# BEP32_12nutzen_90Grad.net
KiCad netlist of a schematic drawn in EAGLE
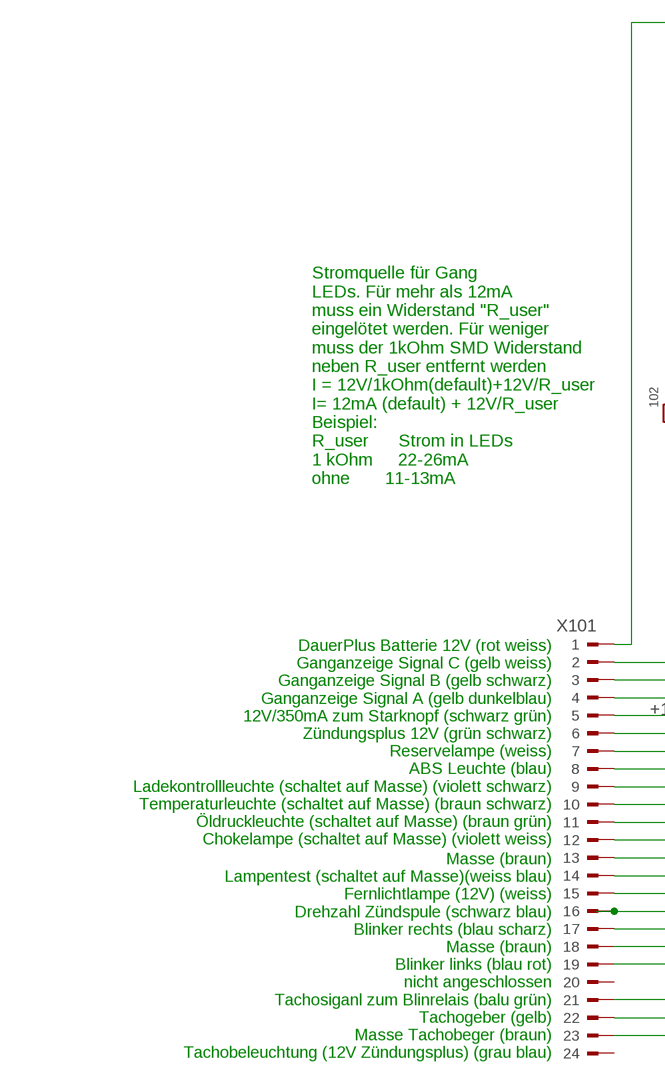
[diagram p0: schematic, sheet 1, part 1 of 2]
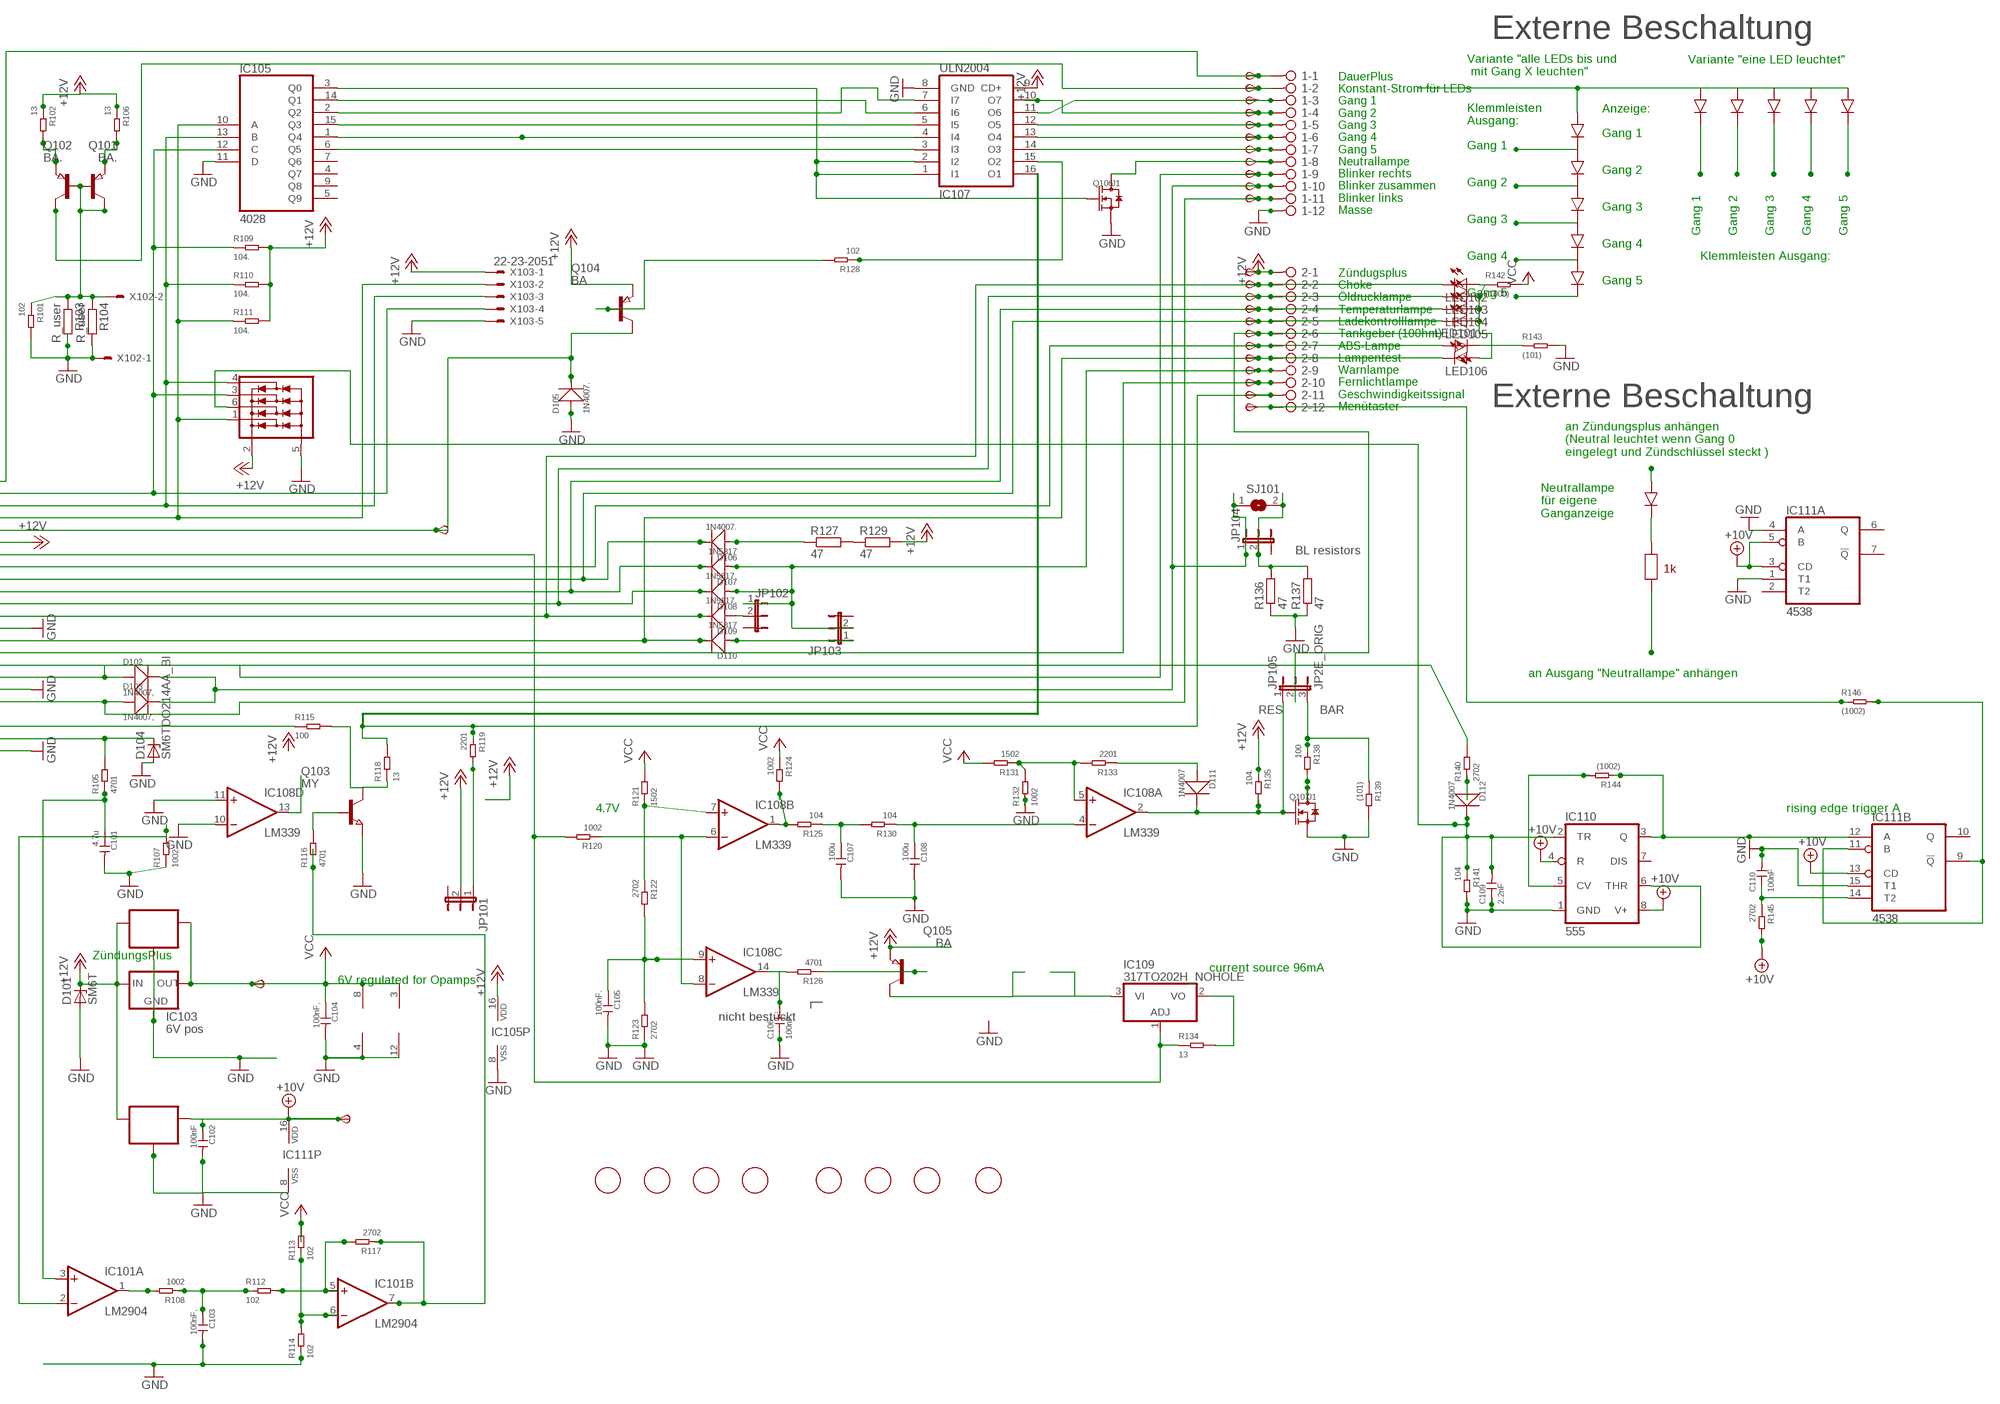
[diagram p1: schematic, sheet 1, part 2 of 2]
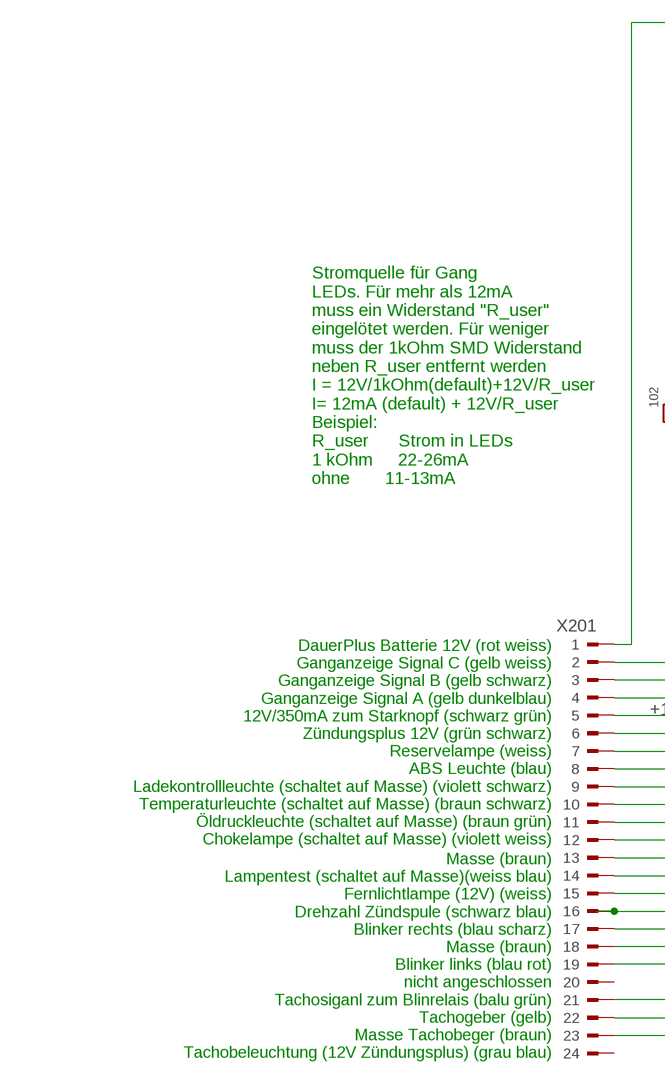
[diagram p2: schematic, sheet 2, part 1 of 2]
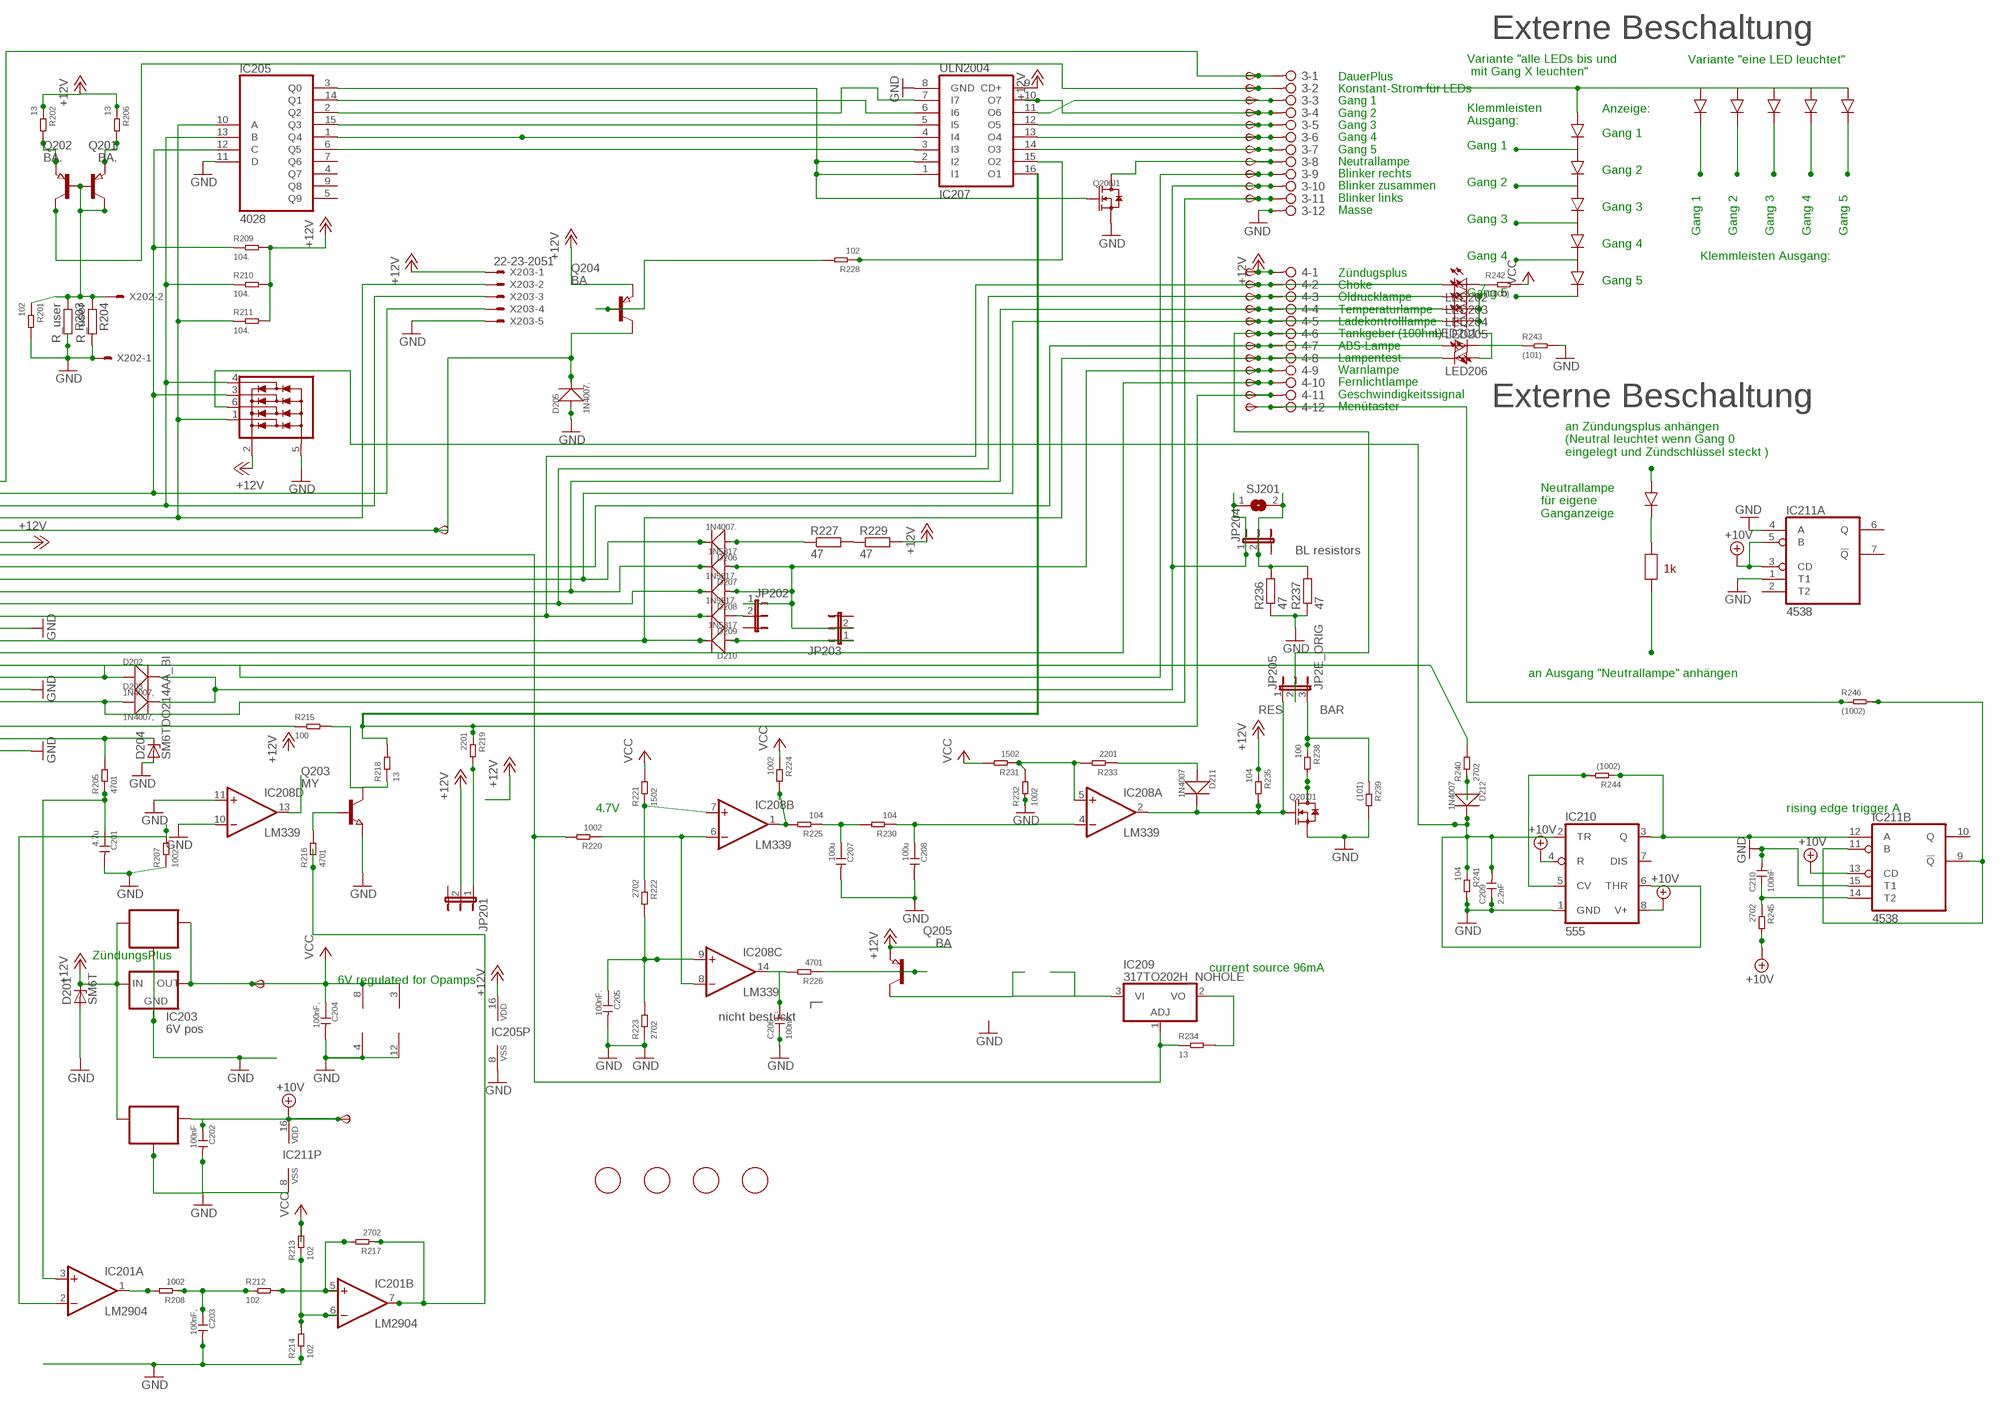
[diagram p3: schematic, sheet 2, part 2 of 2]
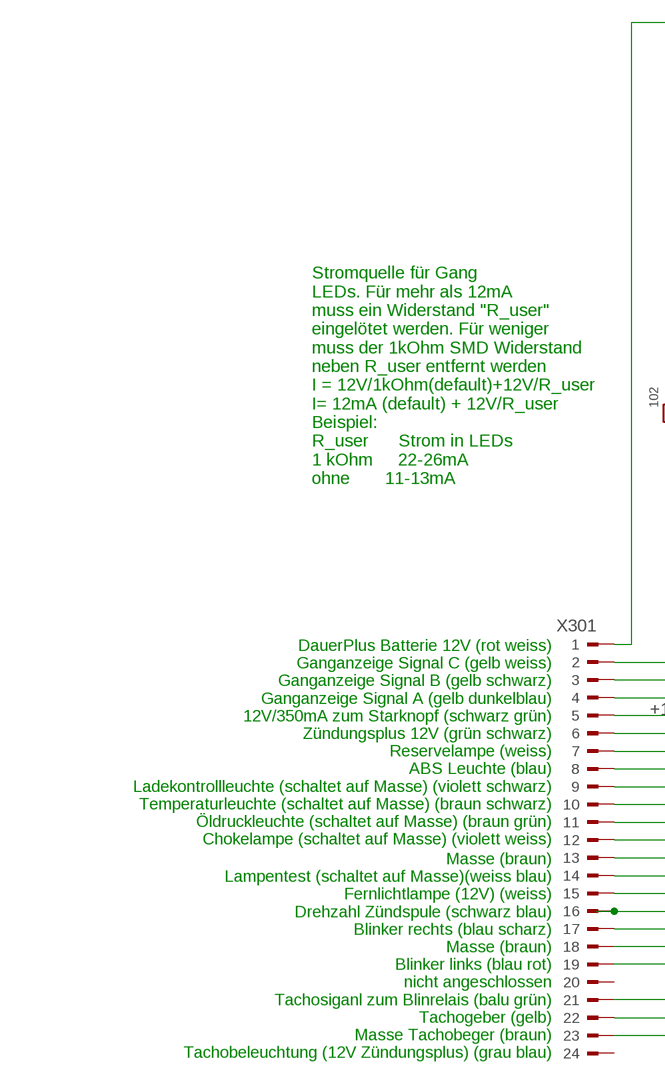
[diagram p4: schematic, sheet 3, part 1 of 2]
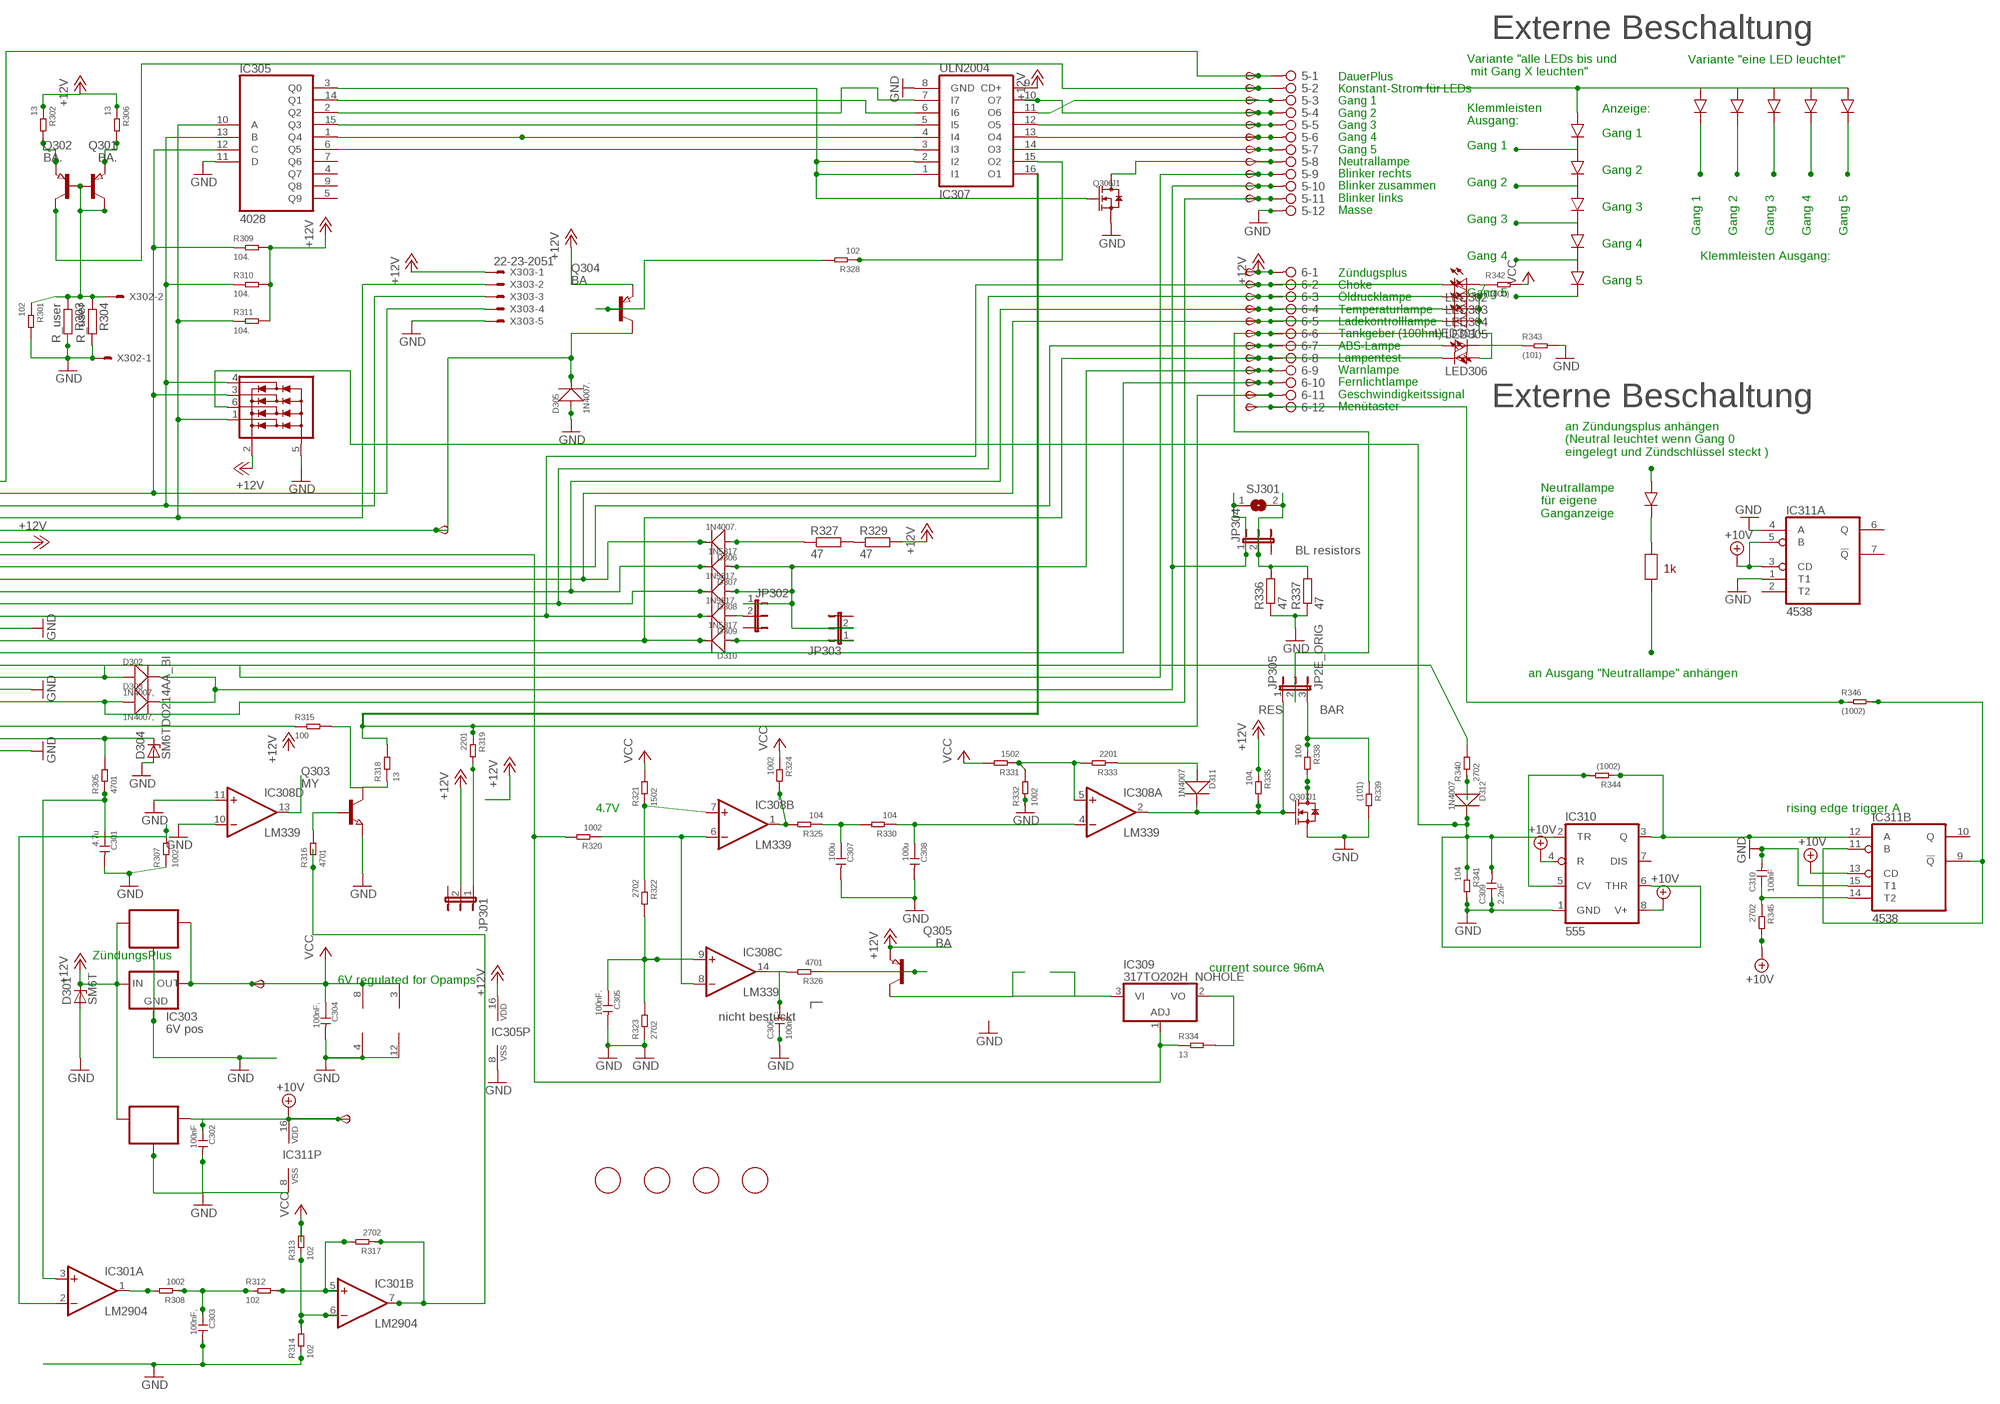
[diagram p5: schematic, sheet 3, part 2 of 2]
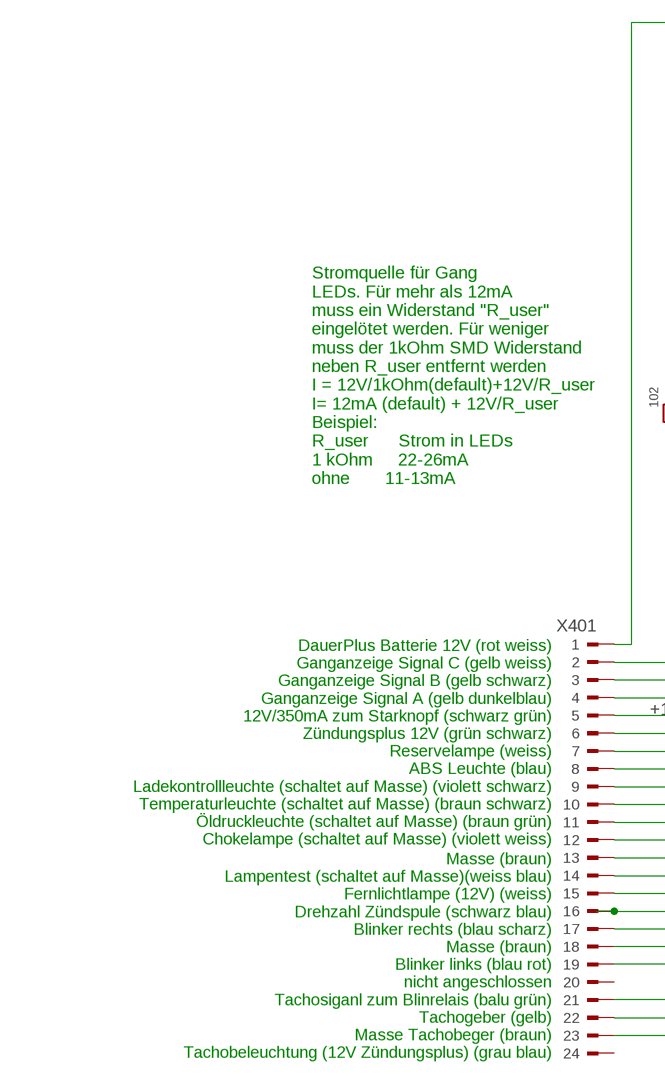
[diagram p6: schematic, sheet 4, part 1 of 2]
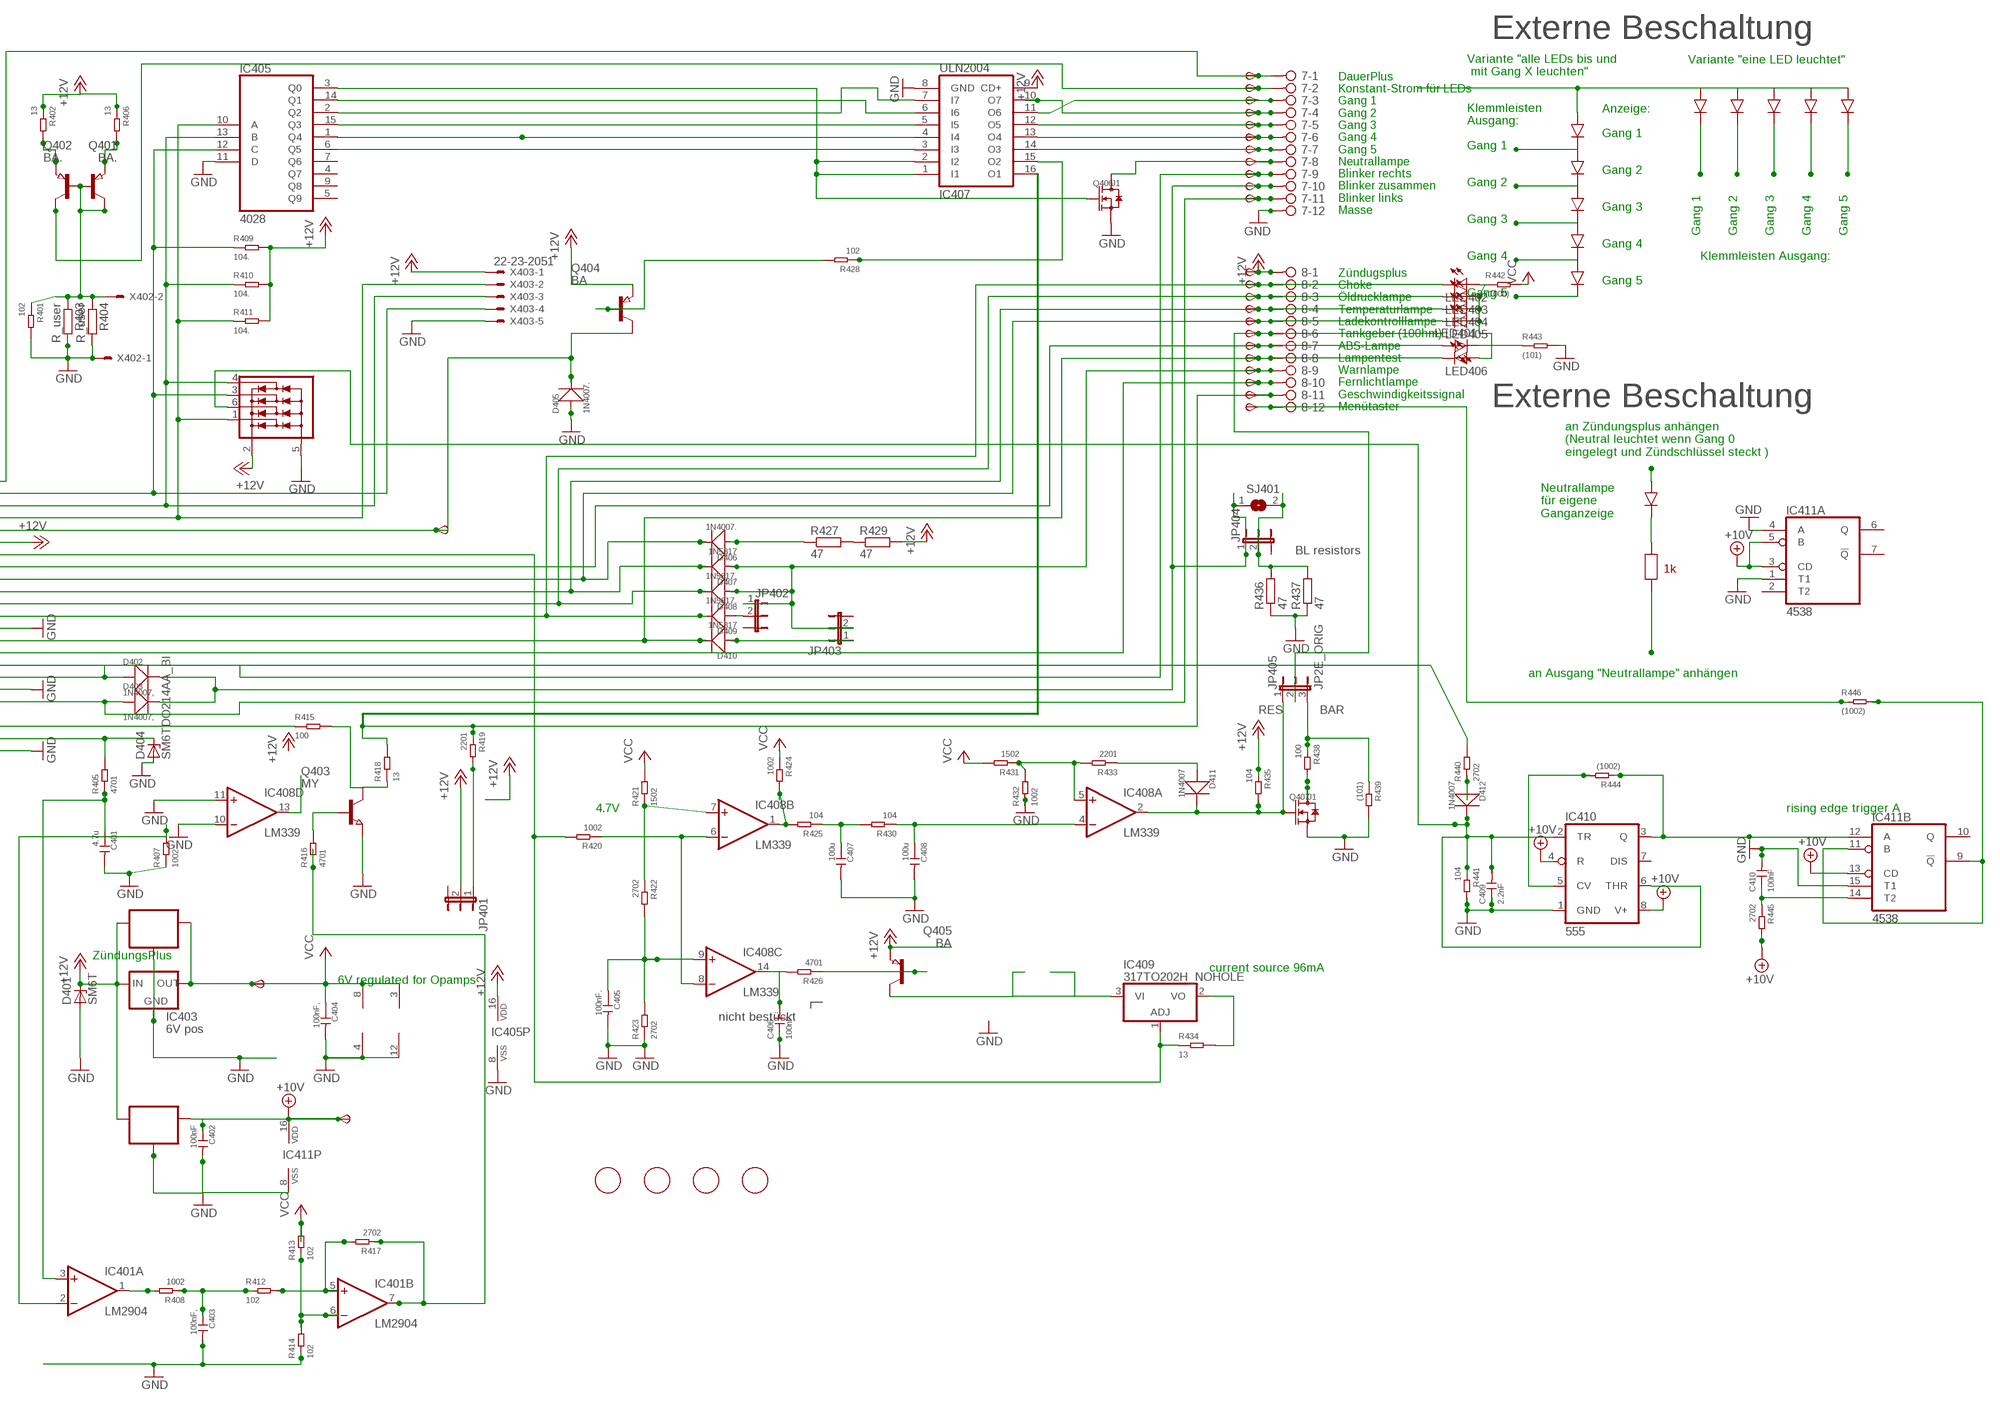
[diagram p7: schematic, sheet 4, part 2 of 2]
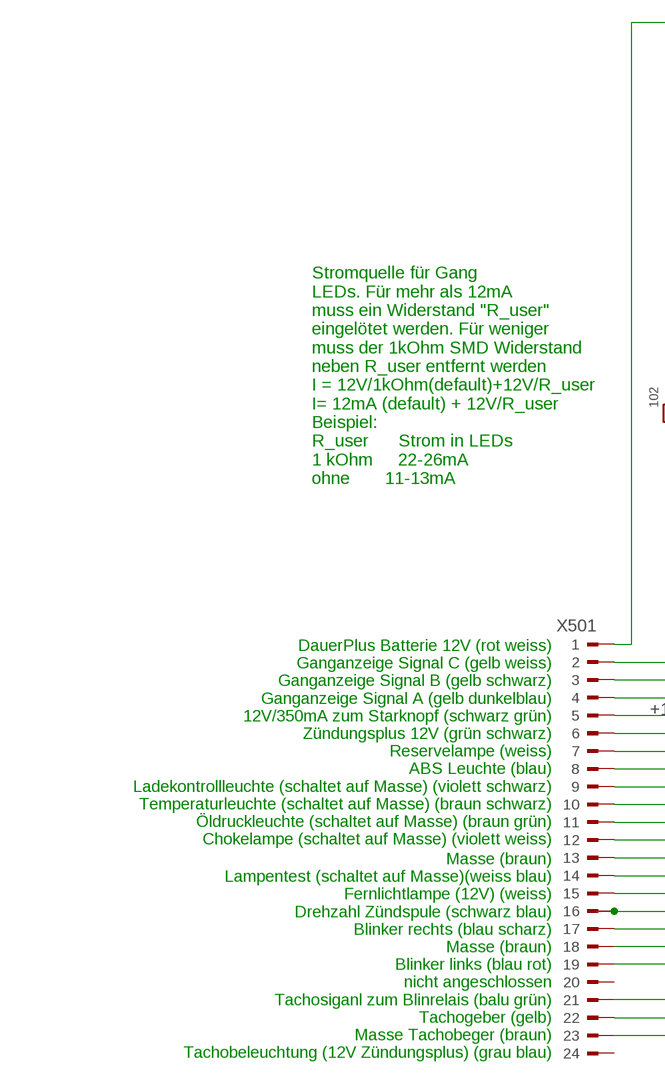
[diagram p8: schematic, sheet 5, part 1 of 2]
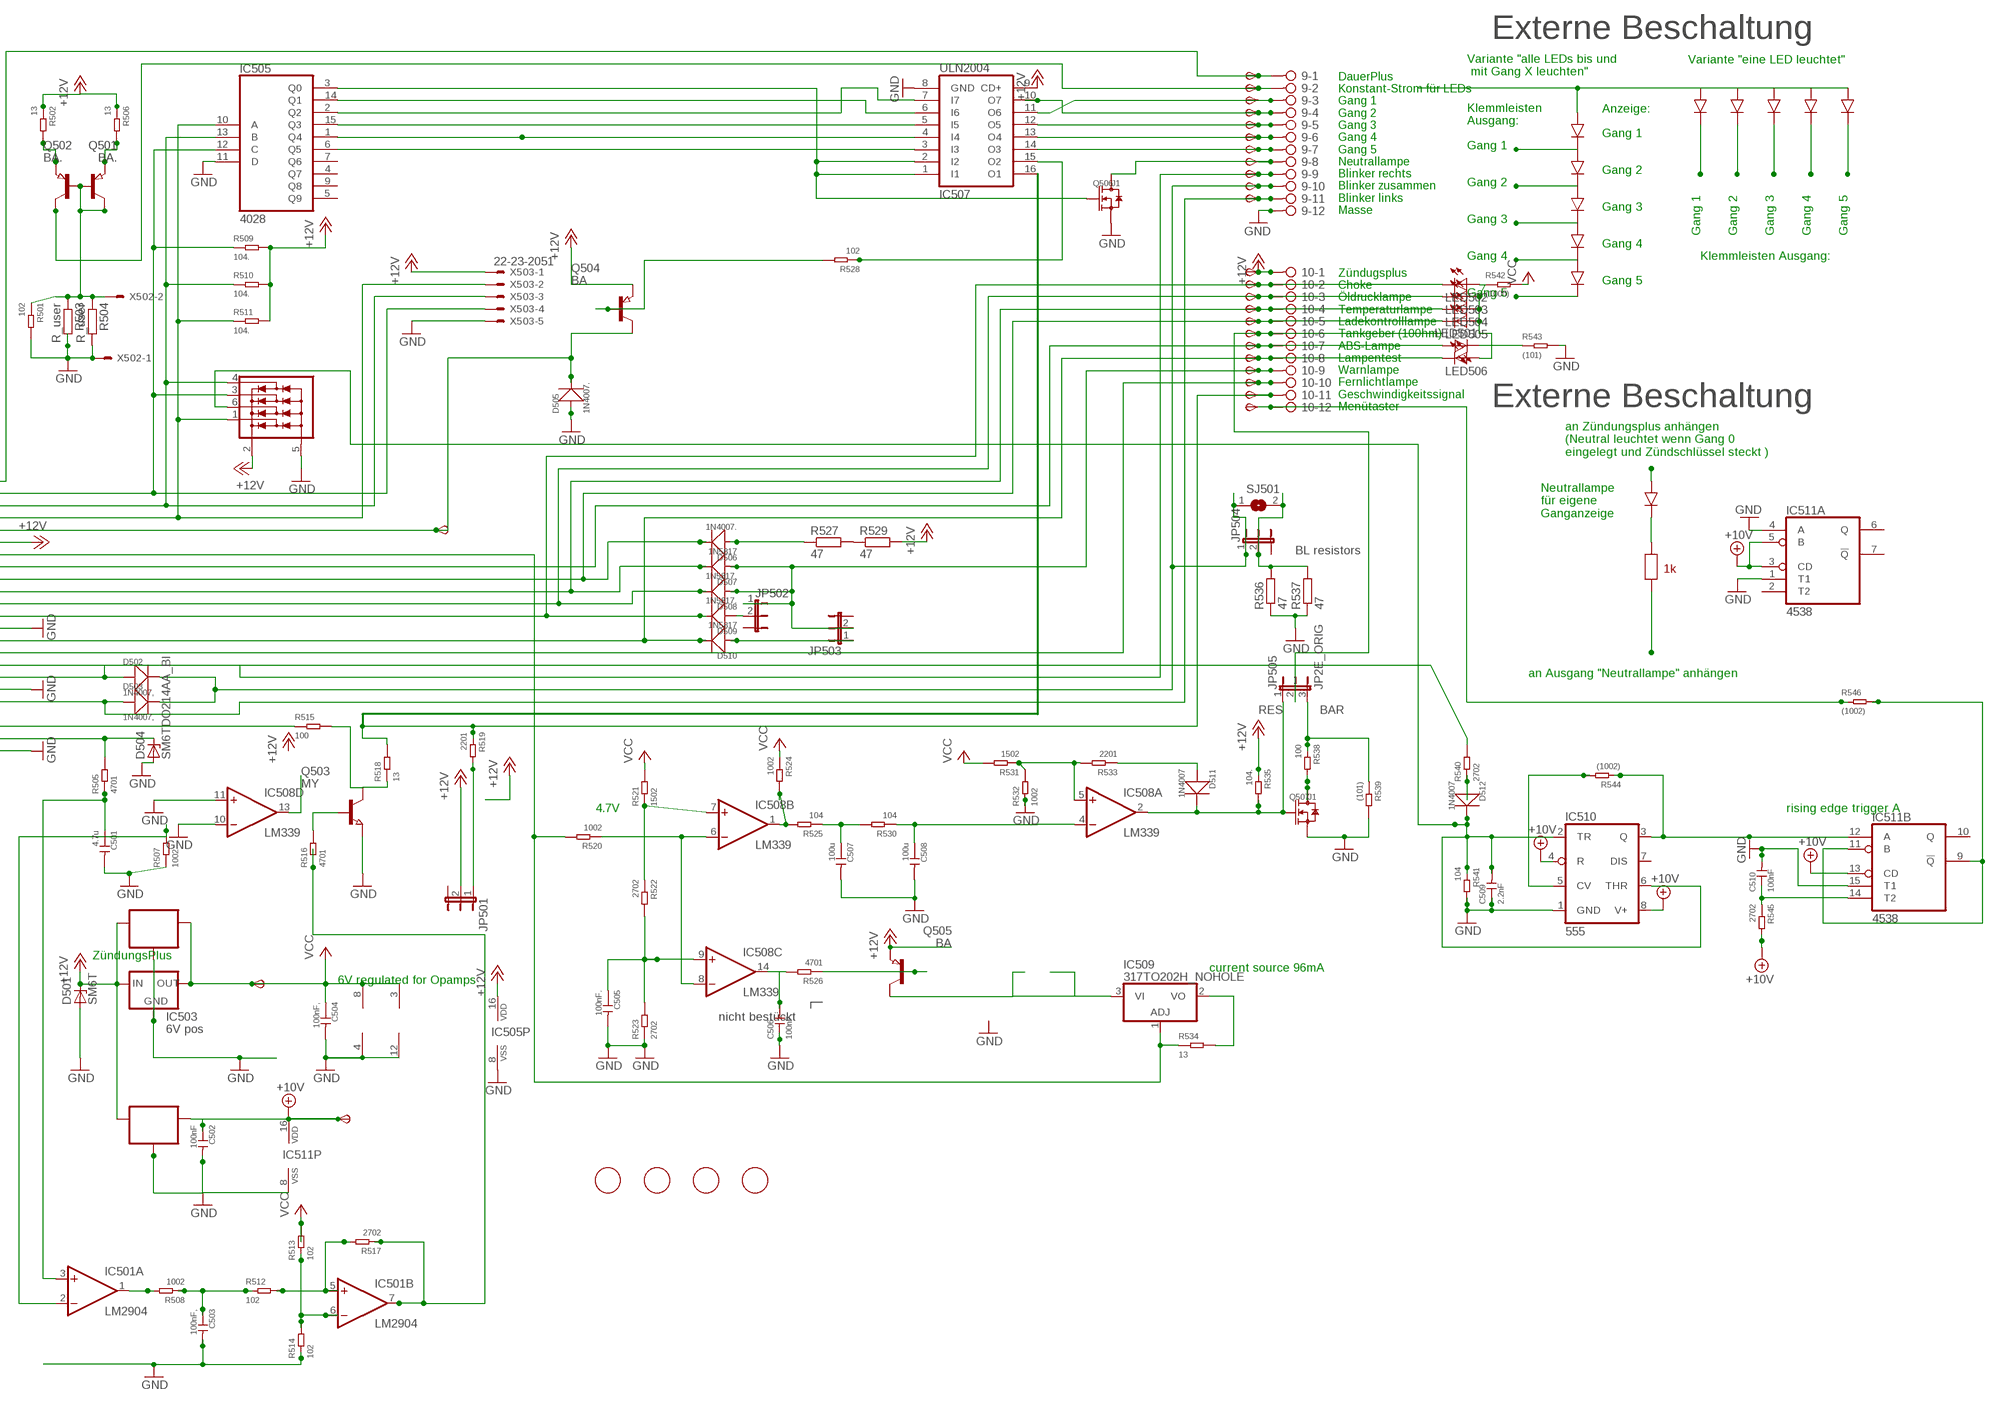
[diagram p9: schematic, sheet 5, part 2 of 2]
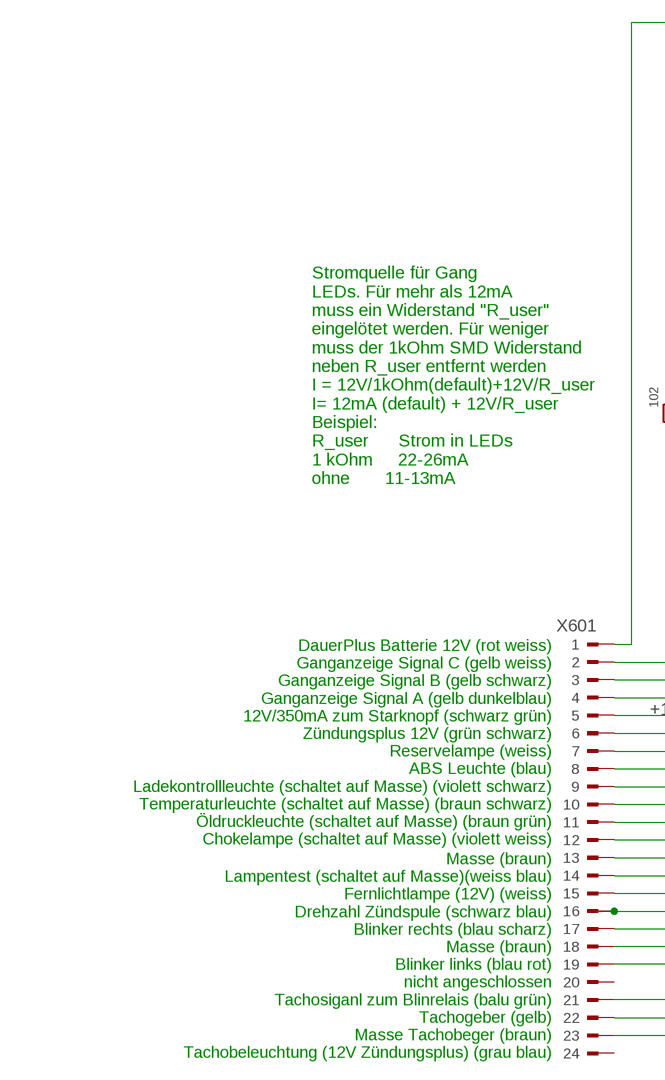
[diagram p10: schematic, sheet 6, part 1 of 2]
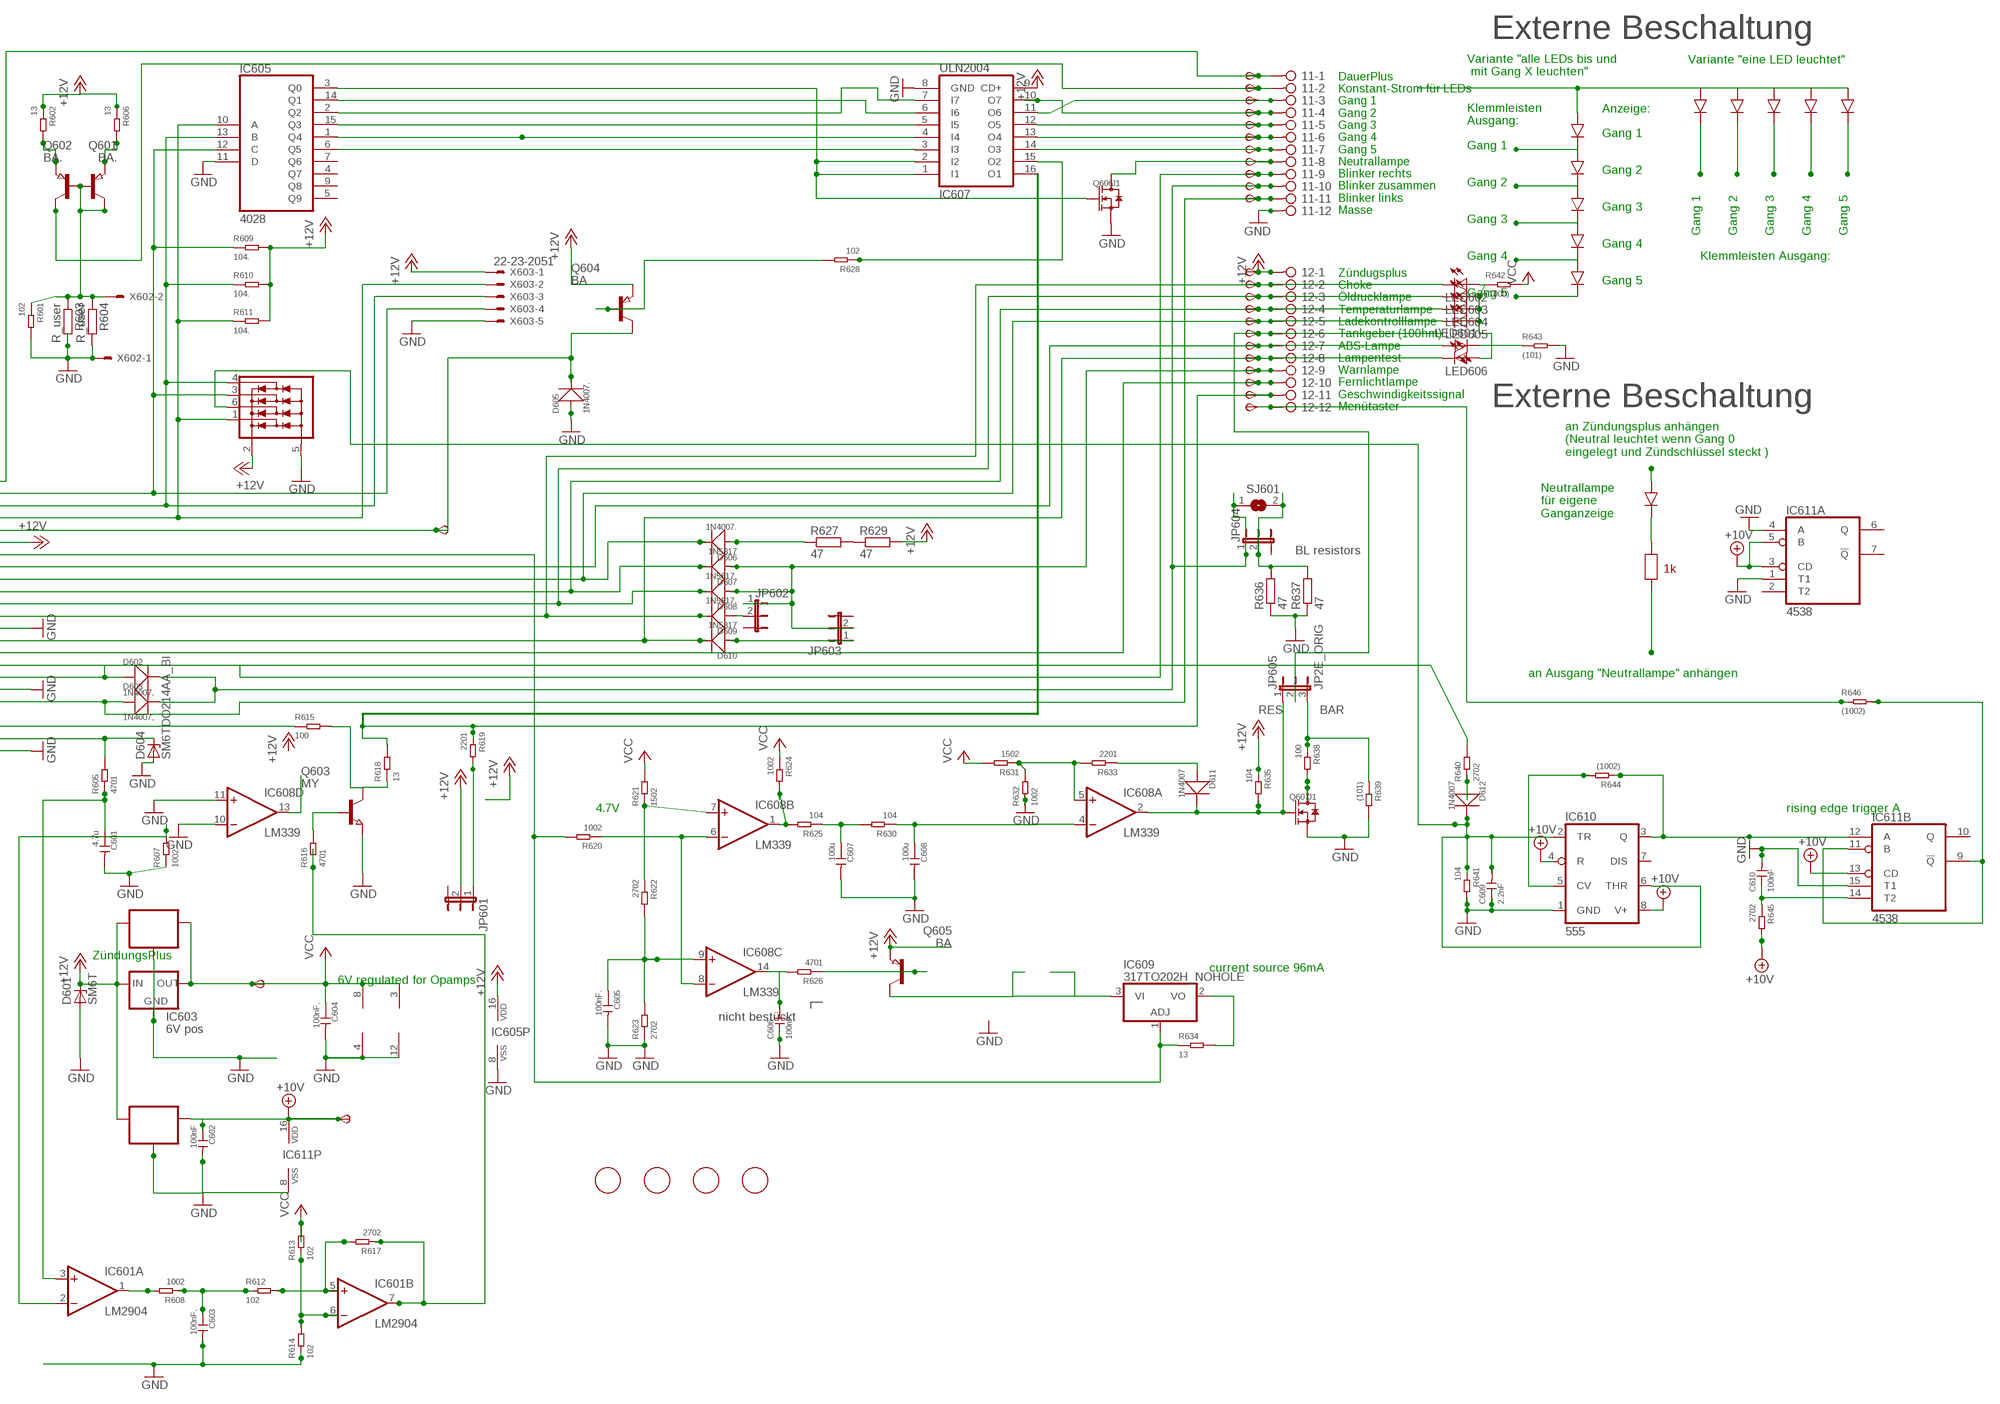
[diagram p11: schematic, sheet 6, part 2 of 2]
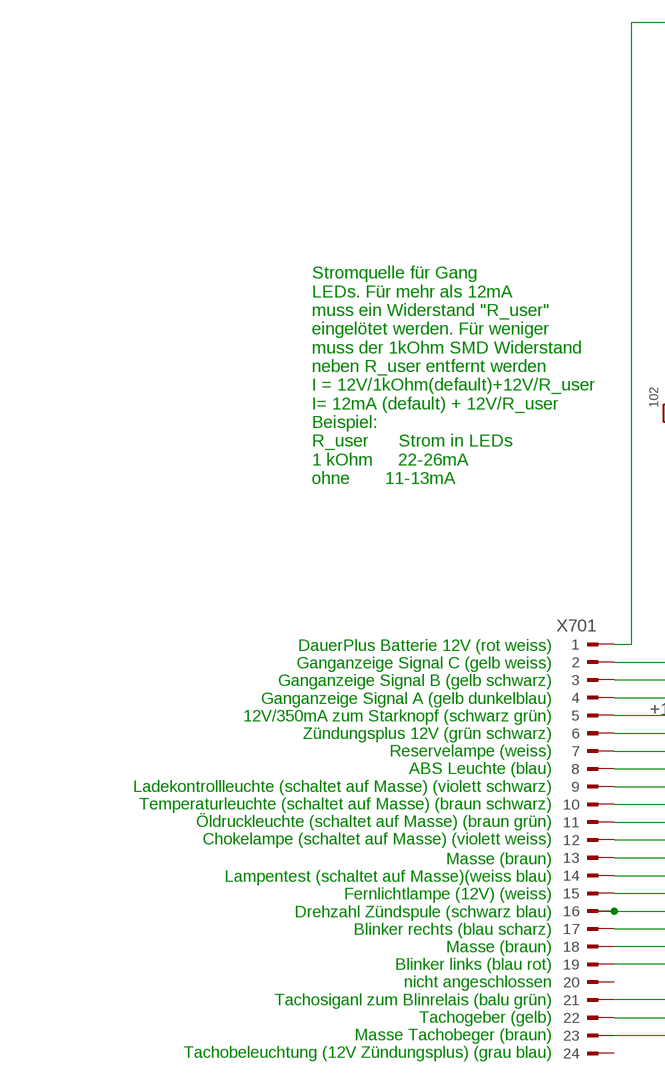
[diagram p12: schematic, sheet 7, part 1 of 2]
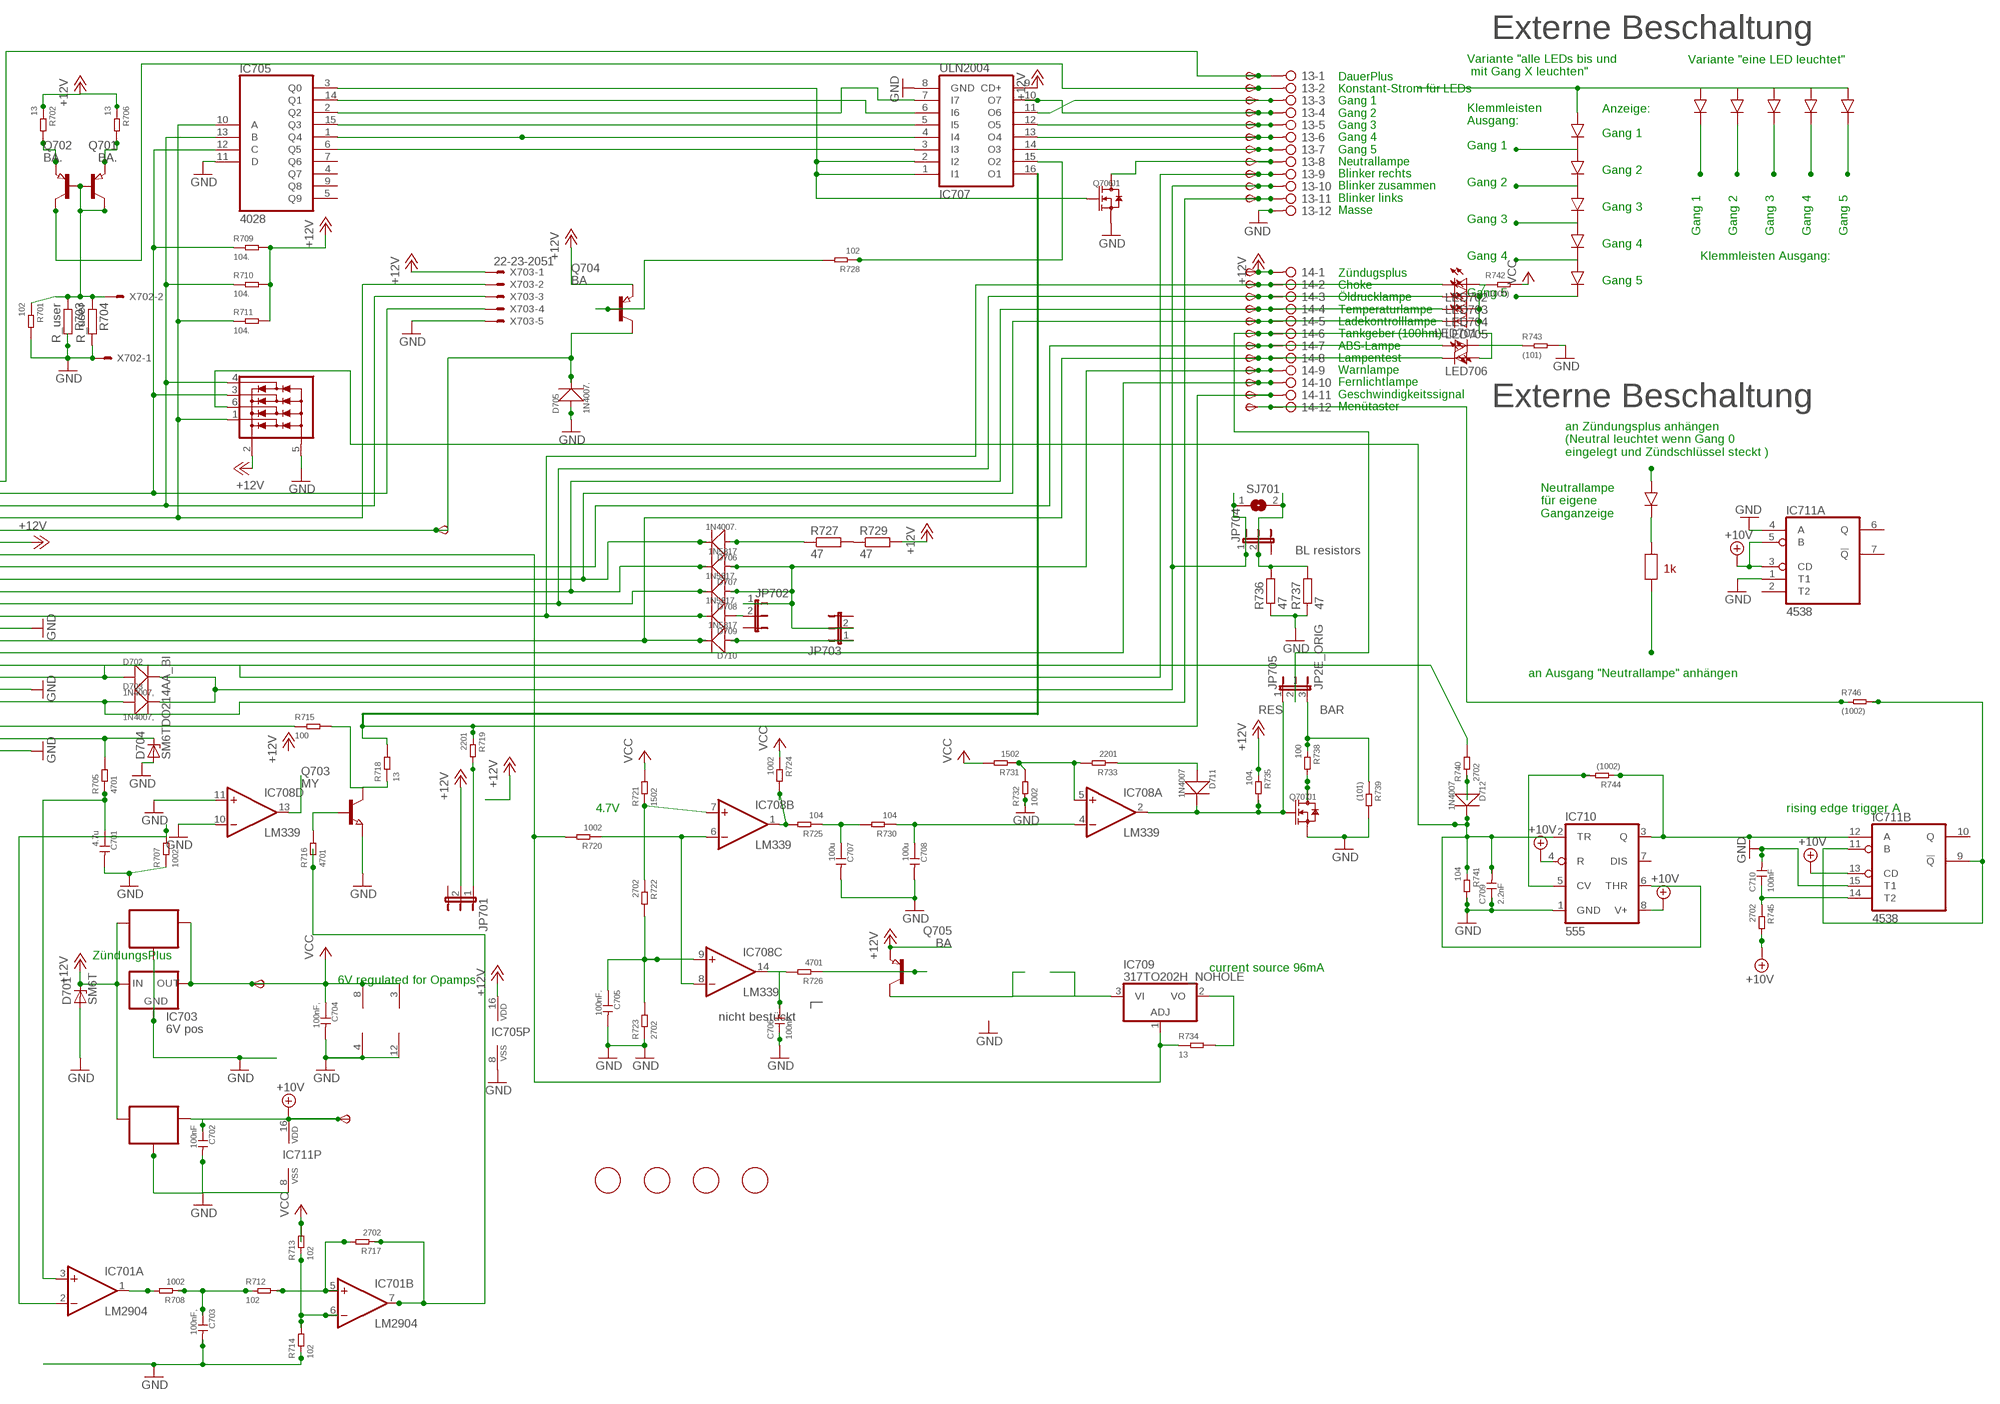
[diagram p13: schematic, sheet 7, part 2 of 2]
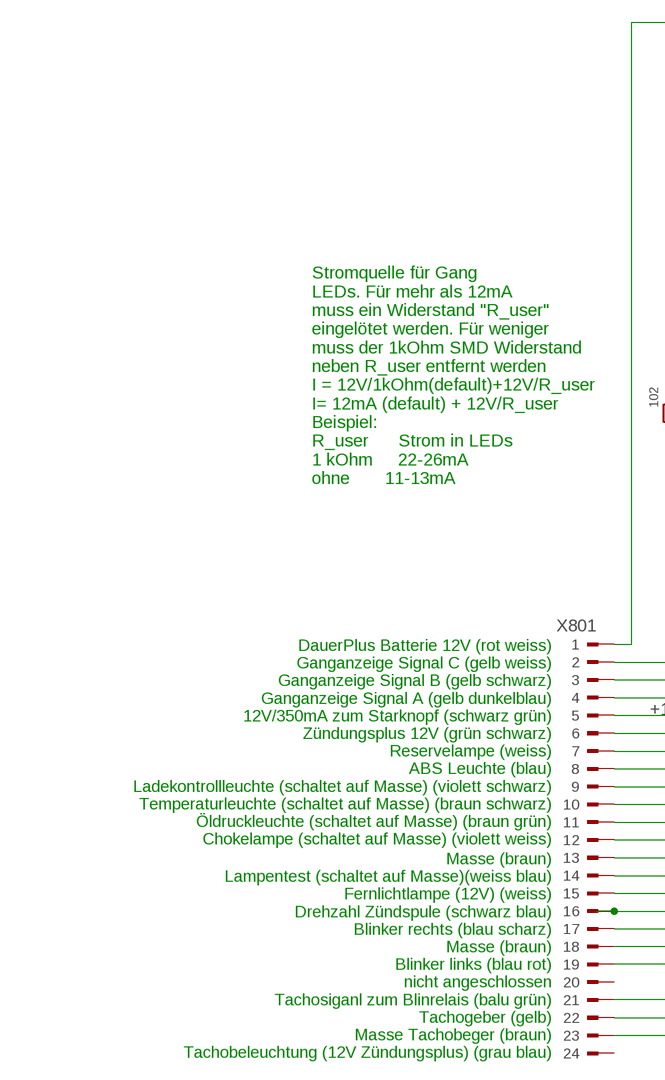
[diagram p14: schematic, sheet 8, part 1 of 2]
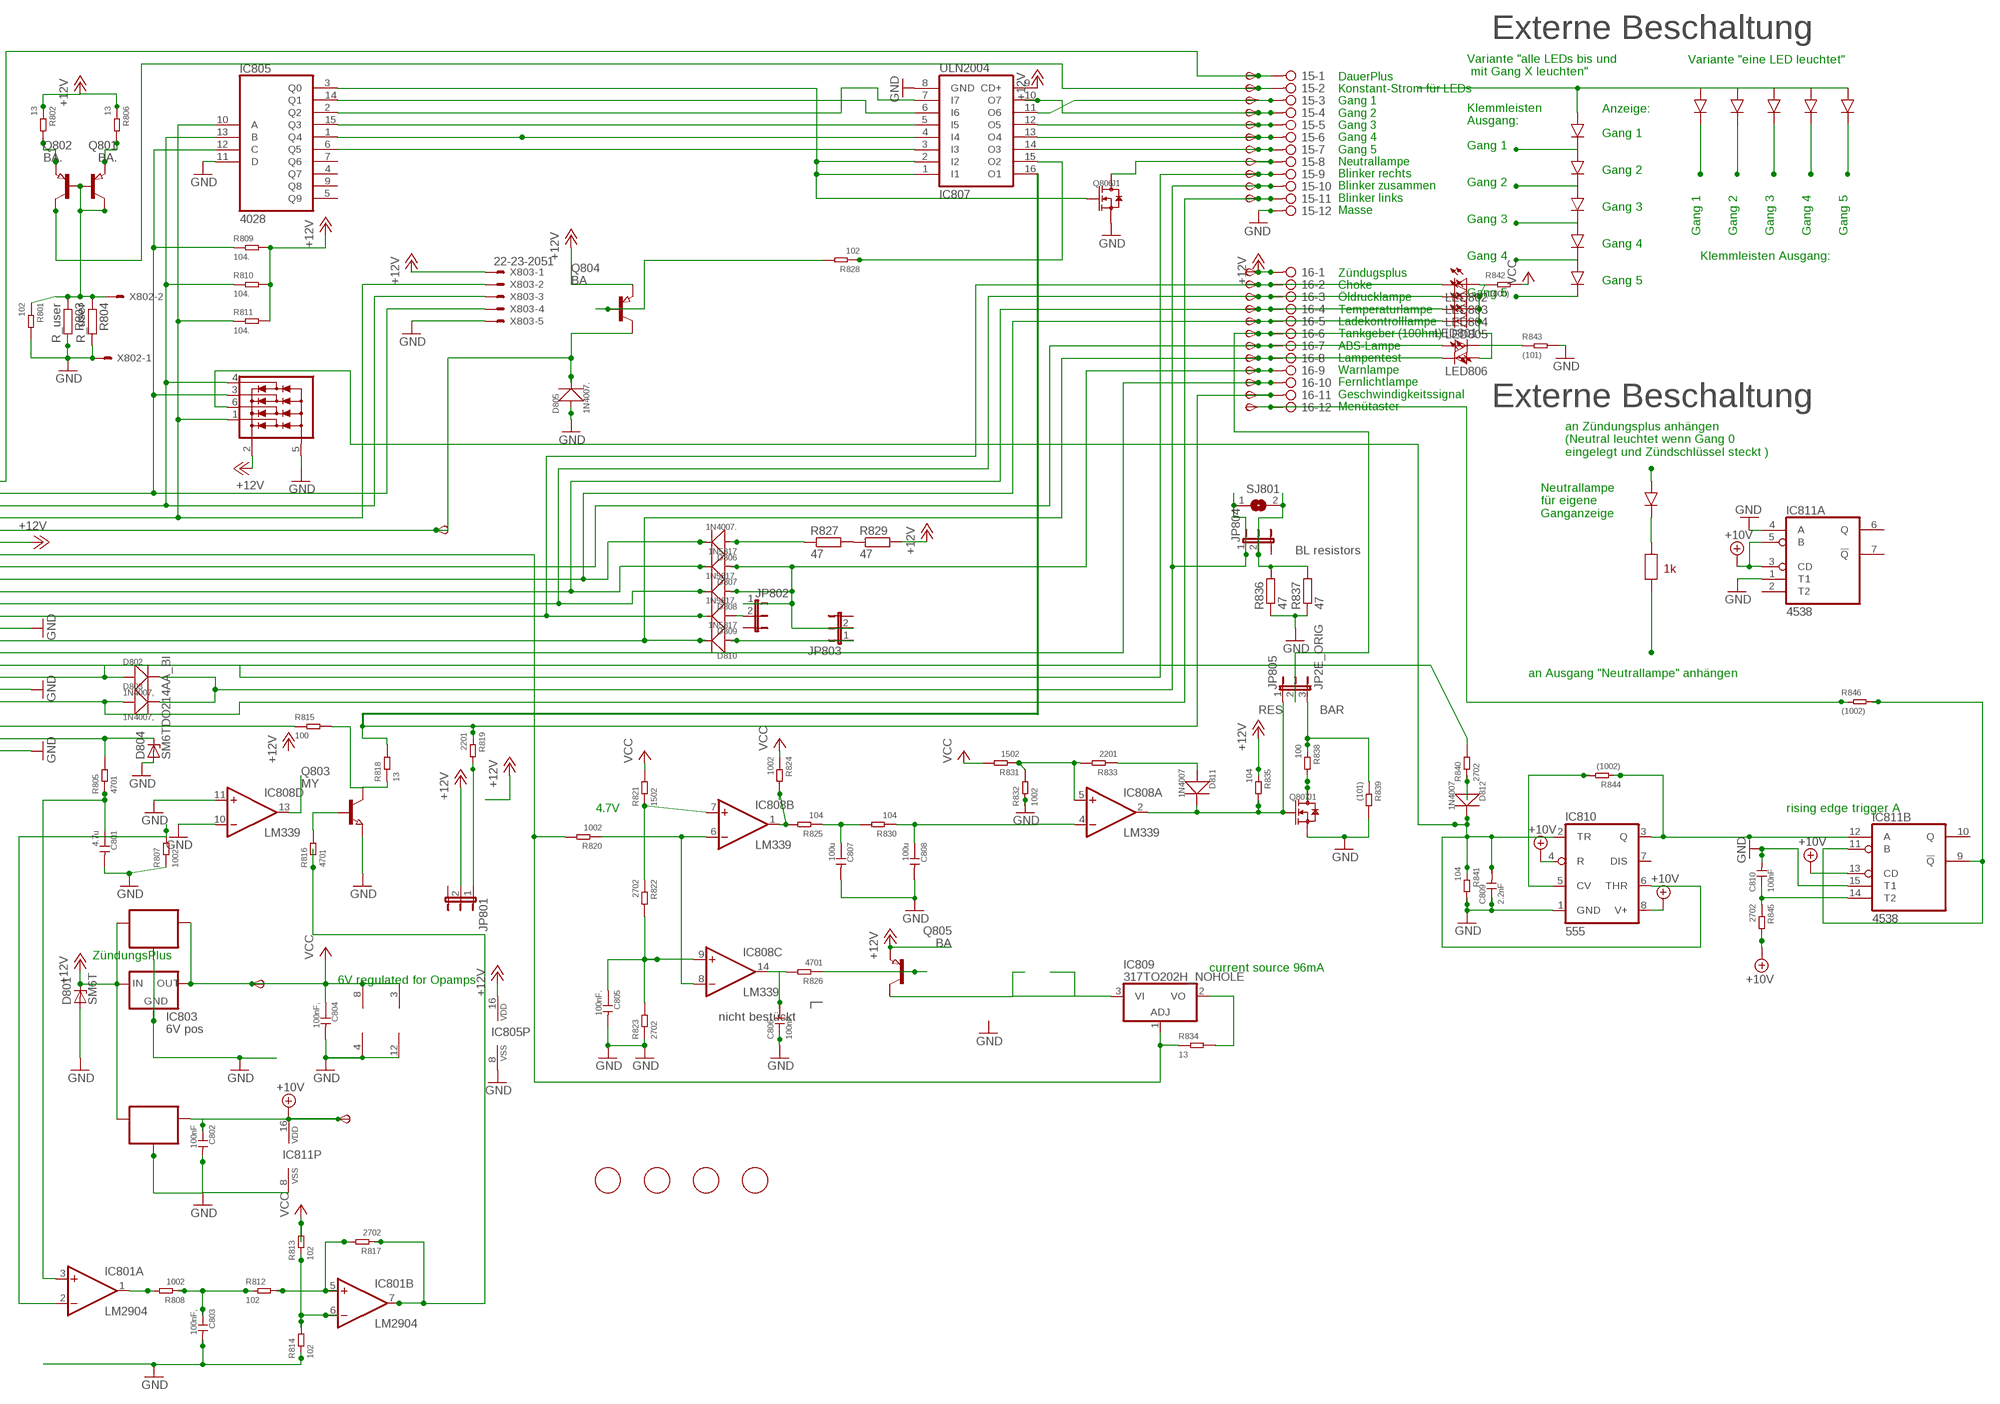
[diagram p15: schematic, sheet 8, part 2 of 2]
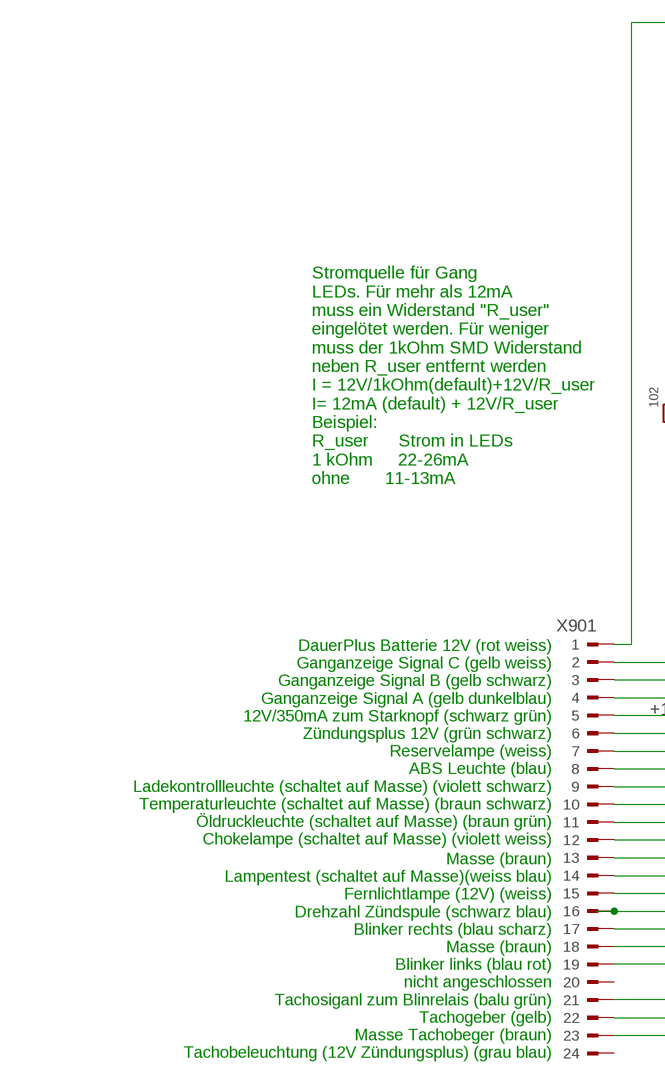
[diagram p16: schematic, sheet 9, part 1 of 2]
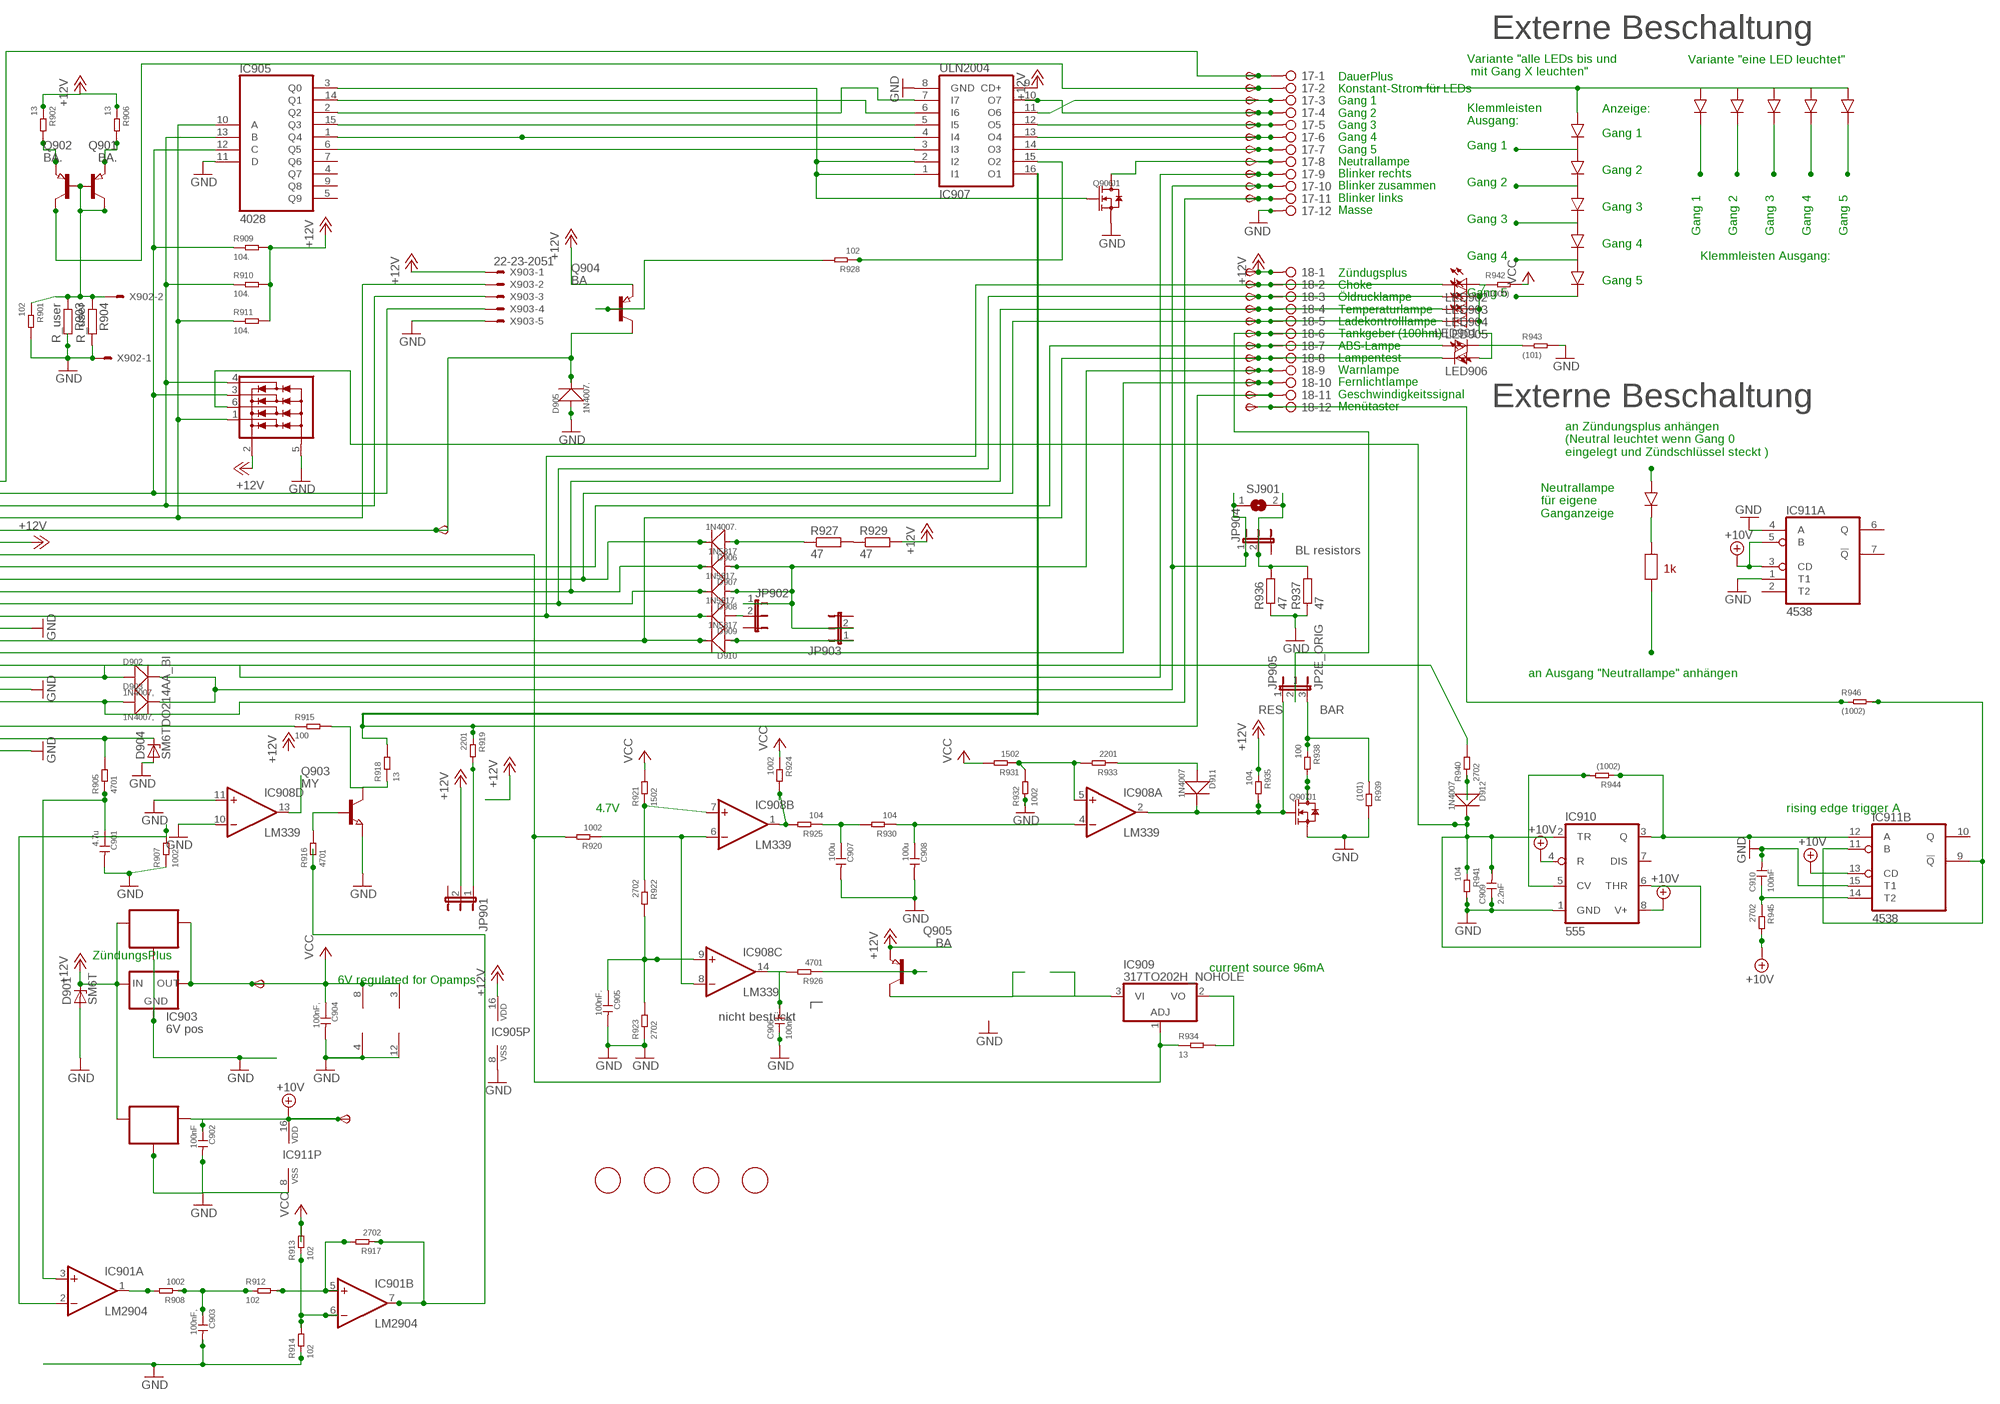
[diagram p17: schematic, sheet 9, part 2 of 2]
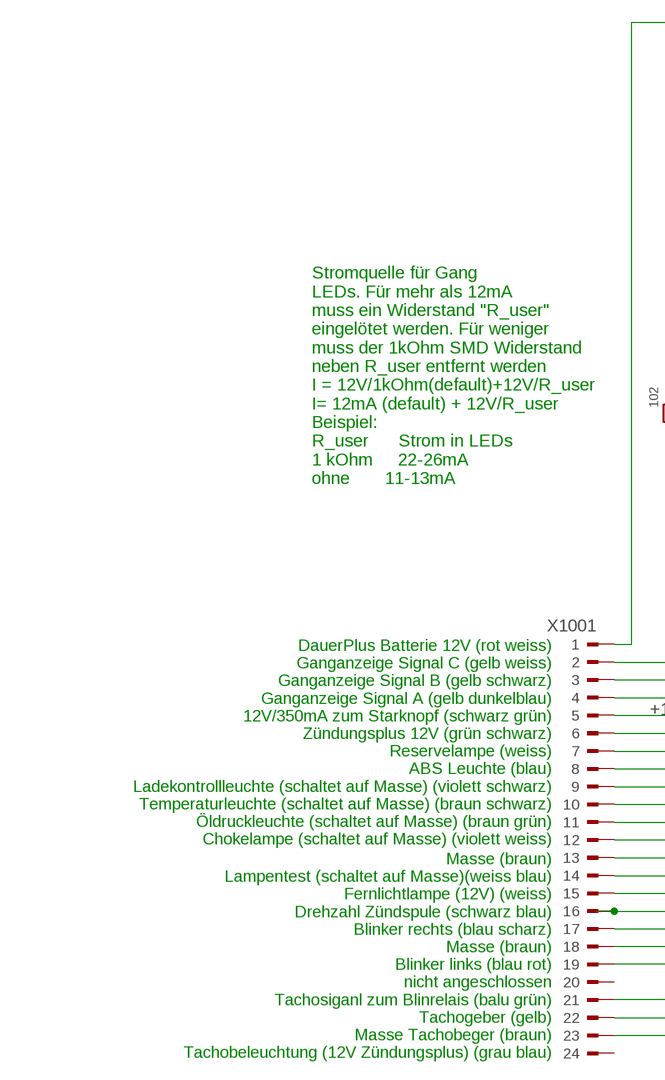
[diagram p18: schematic, sheet 10, part 1 of 2]
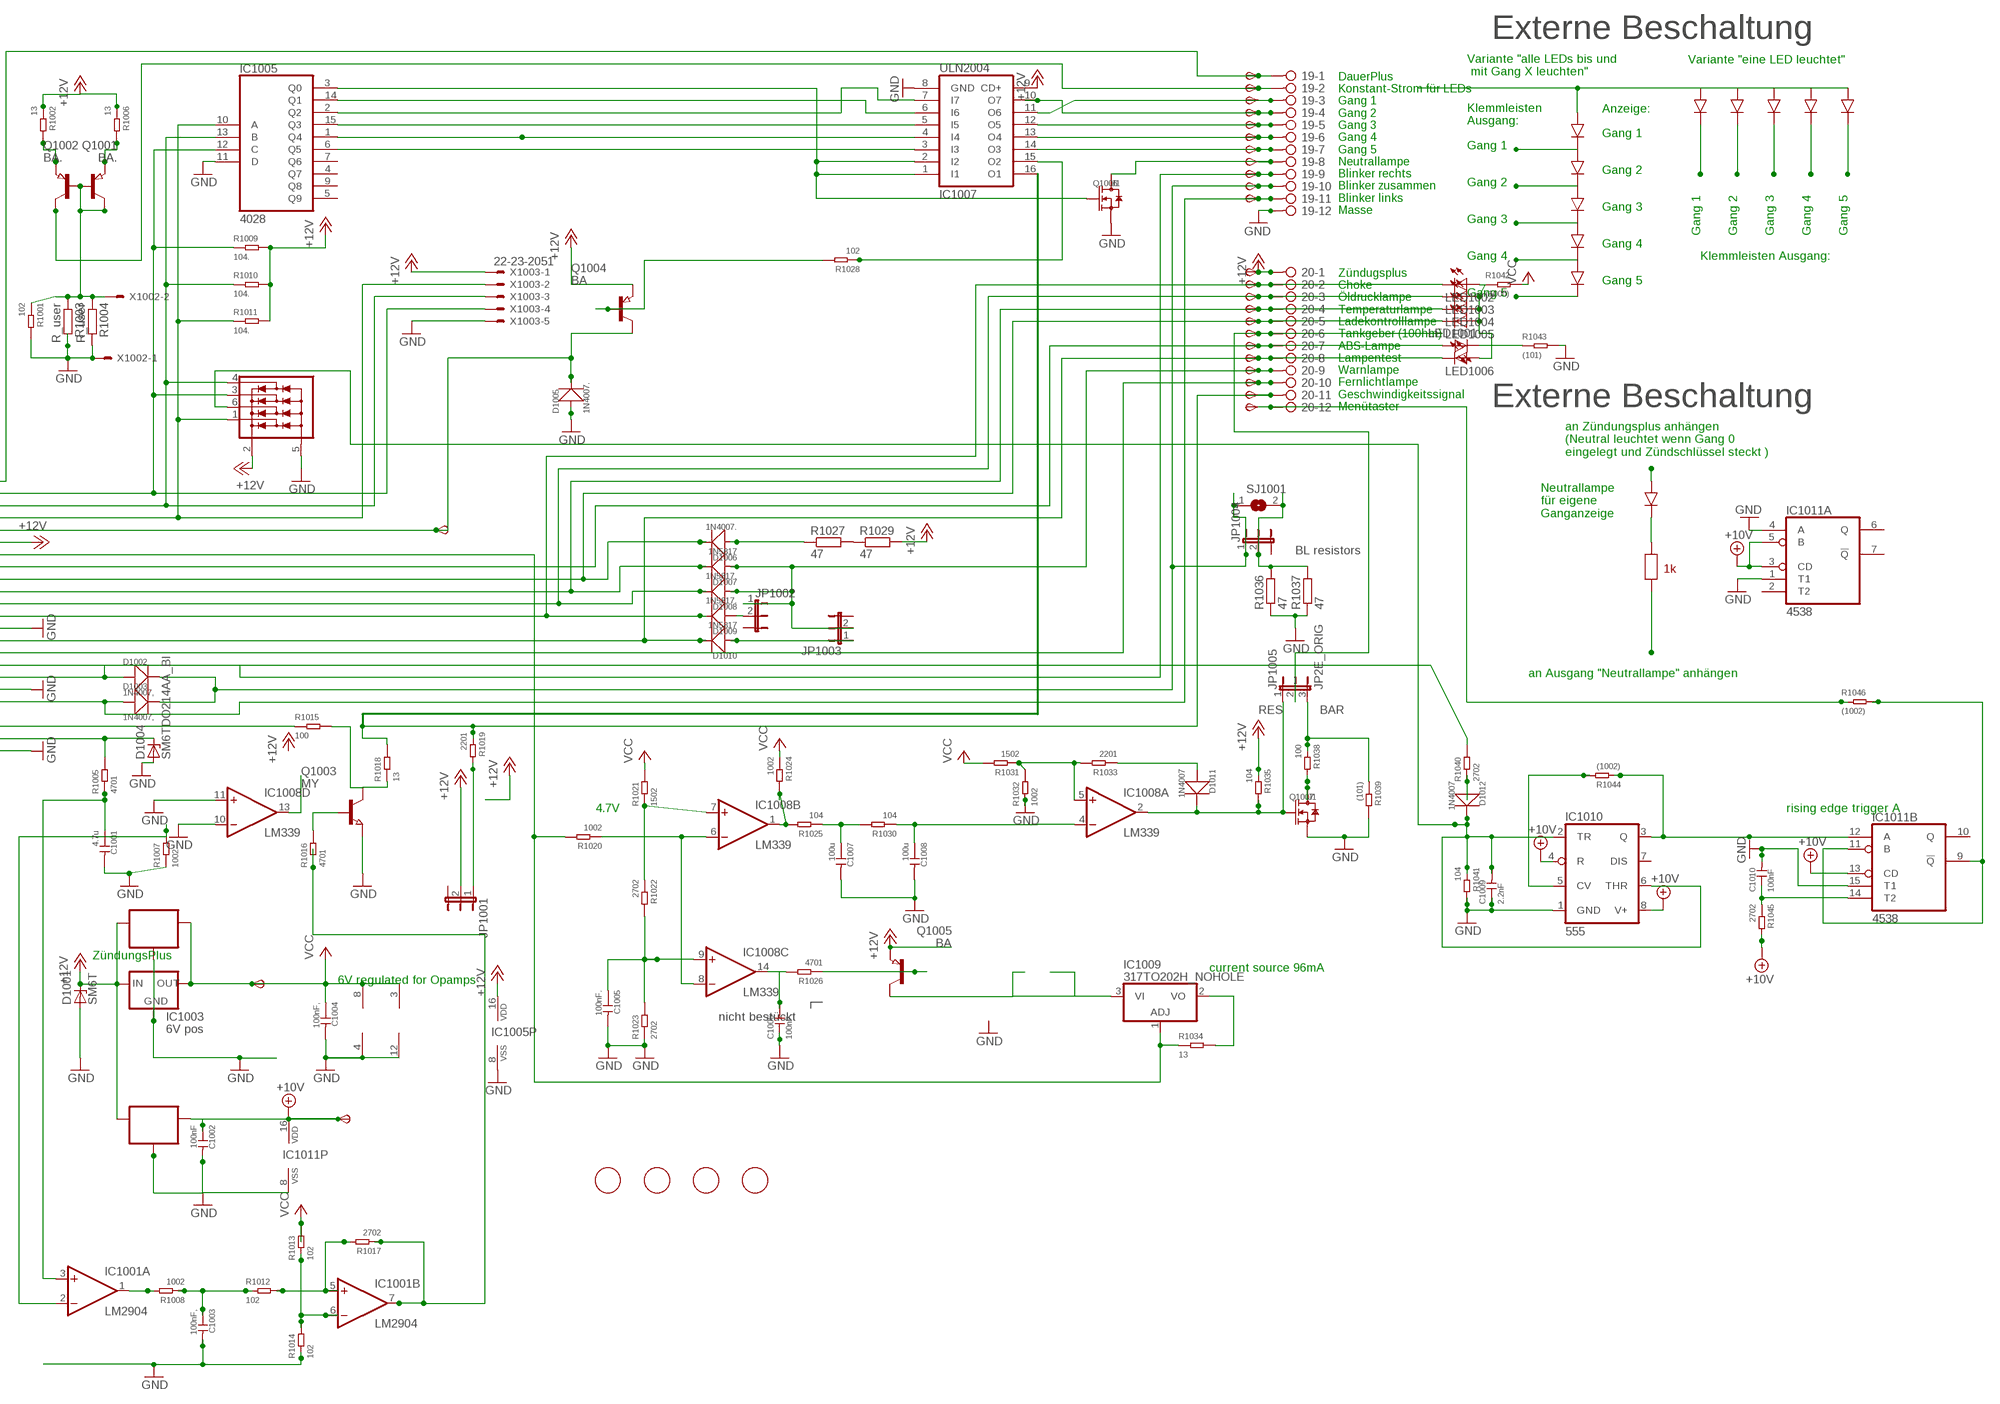
[diagram p19: schematic, sheet 10, part 2 of 2]
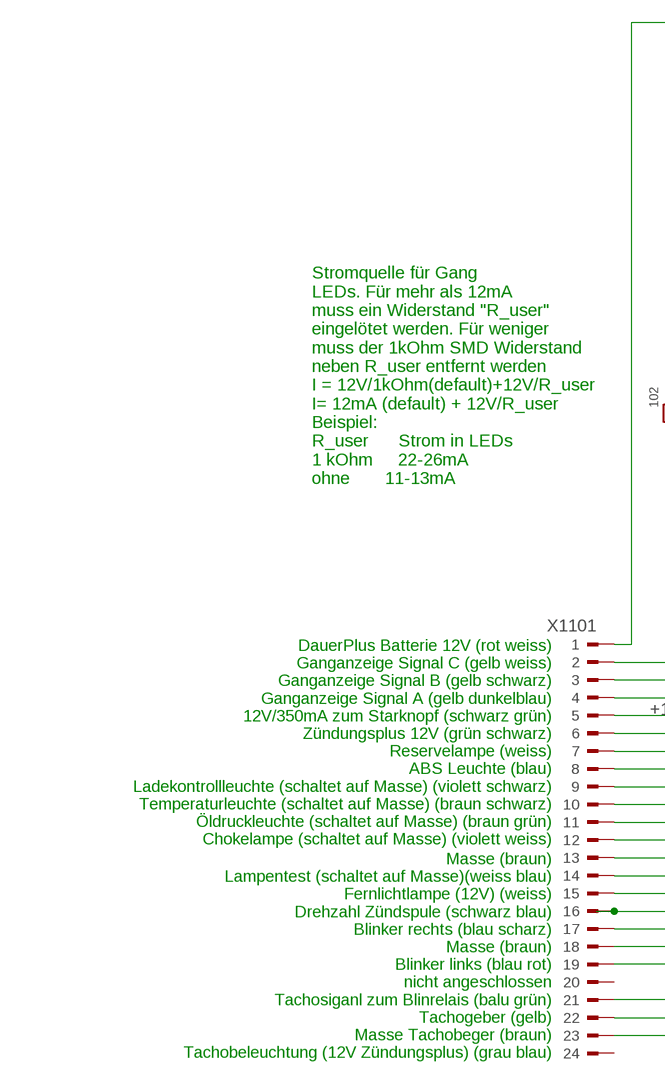
[diagram p20: schematic, sheet 11, part 1 of 2]
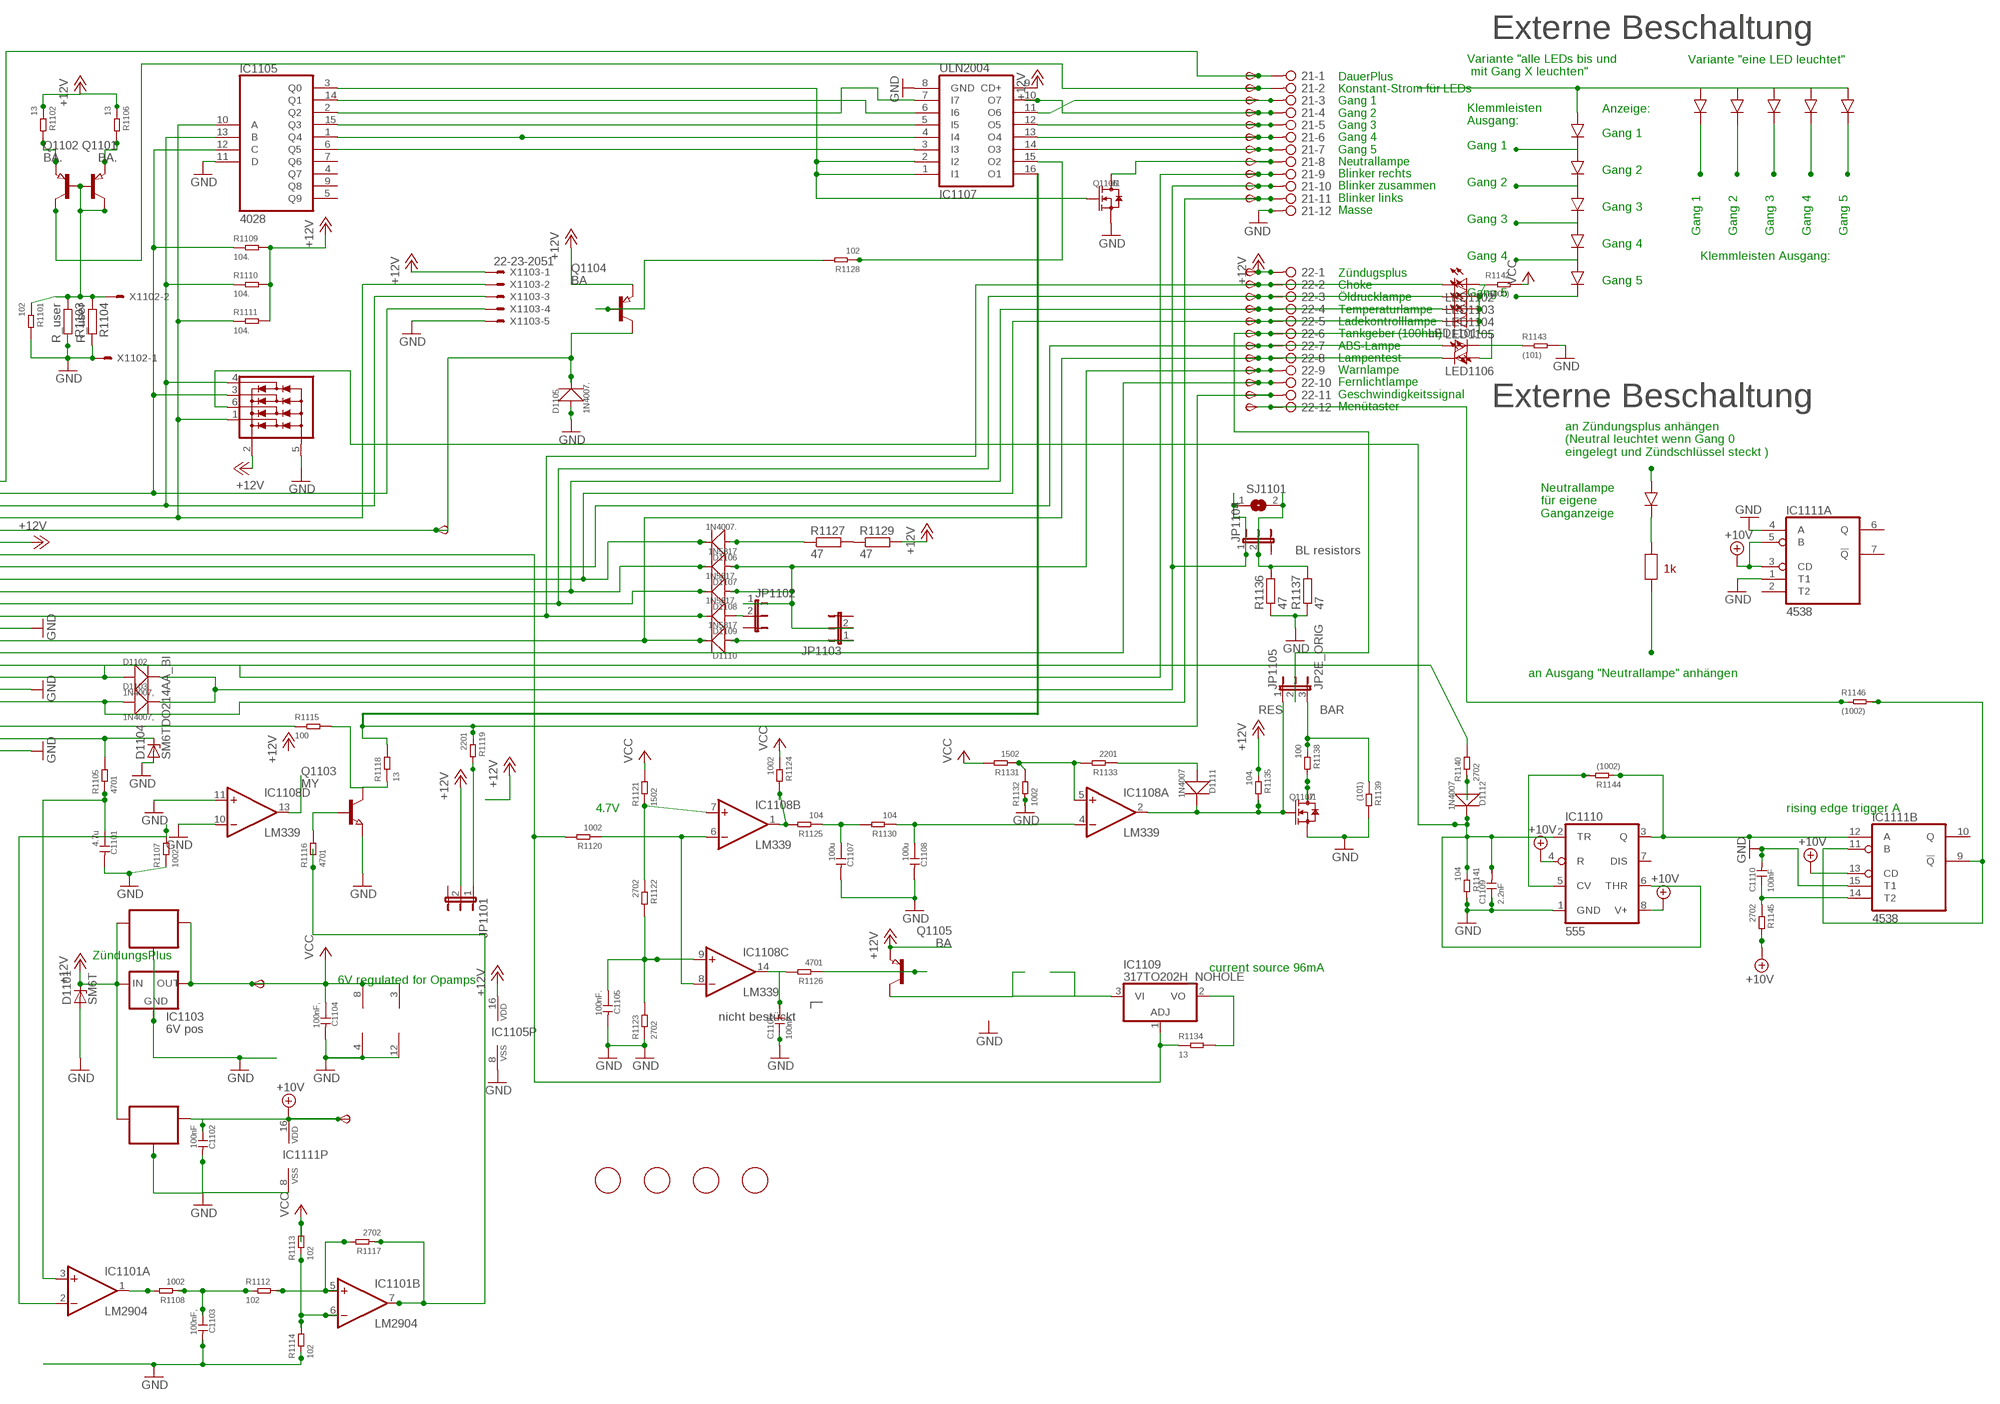
[diagram p21: schematic, sheet 11, part 2 of 2]
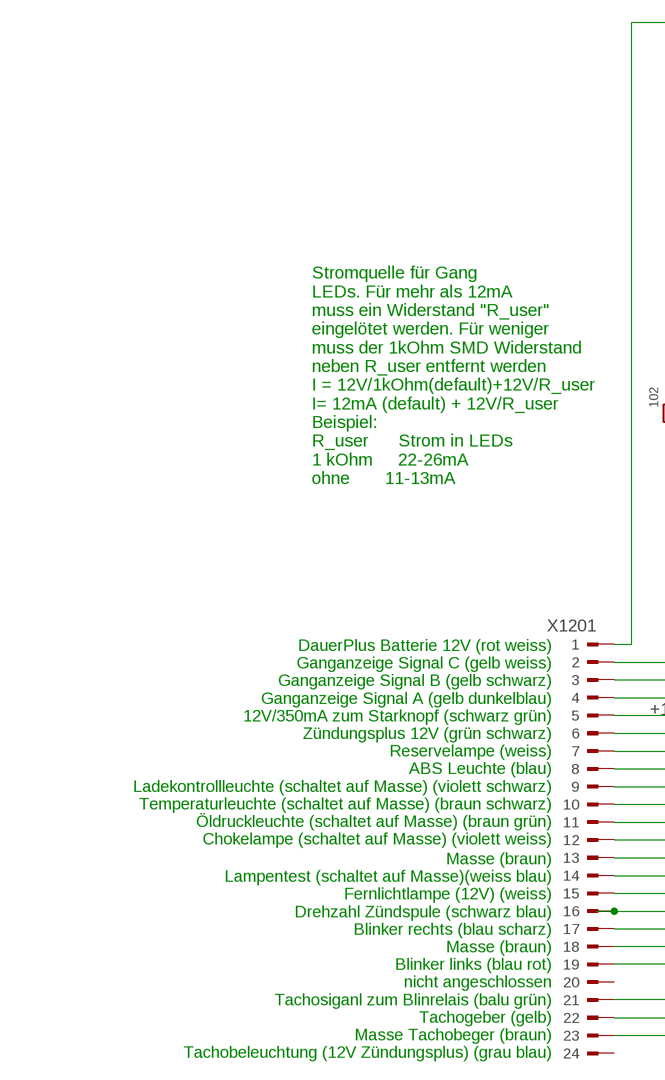
[diagram p22: schematic, sheet 12, part 1 of 2]
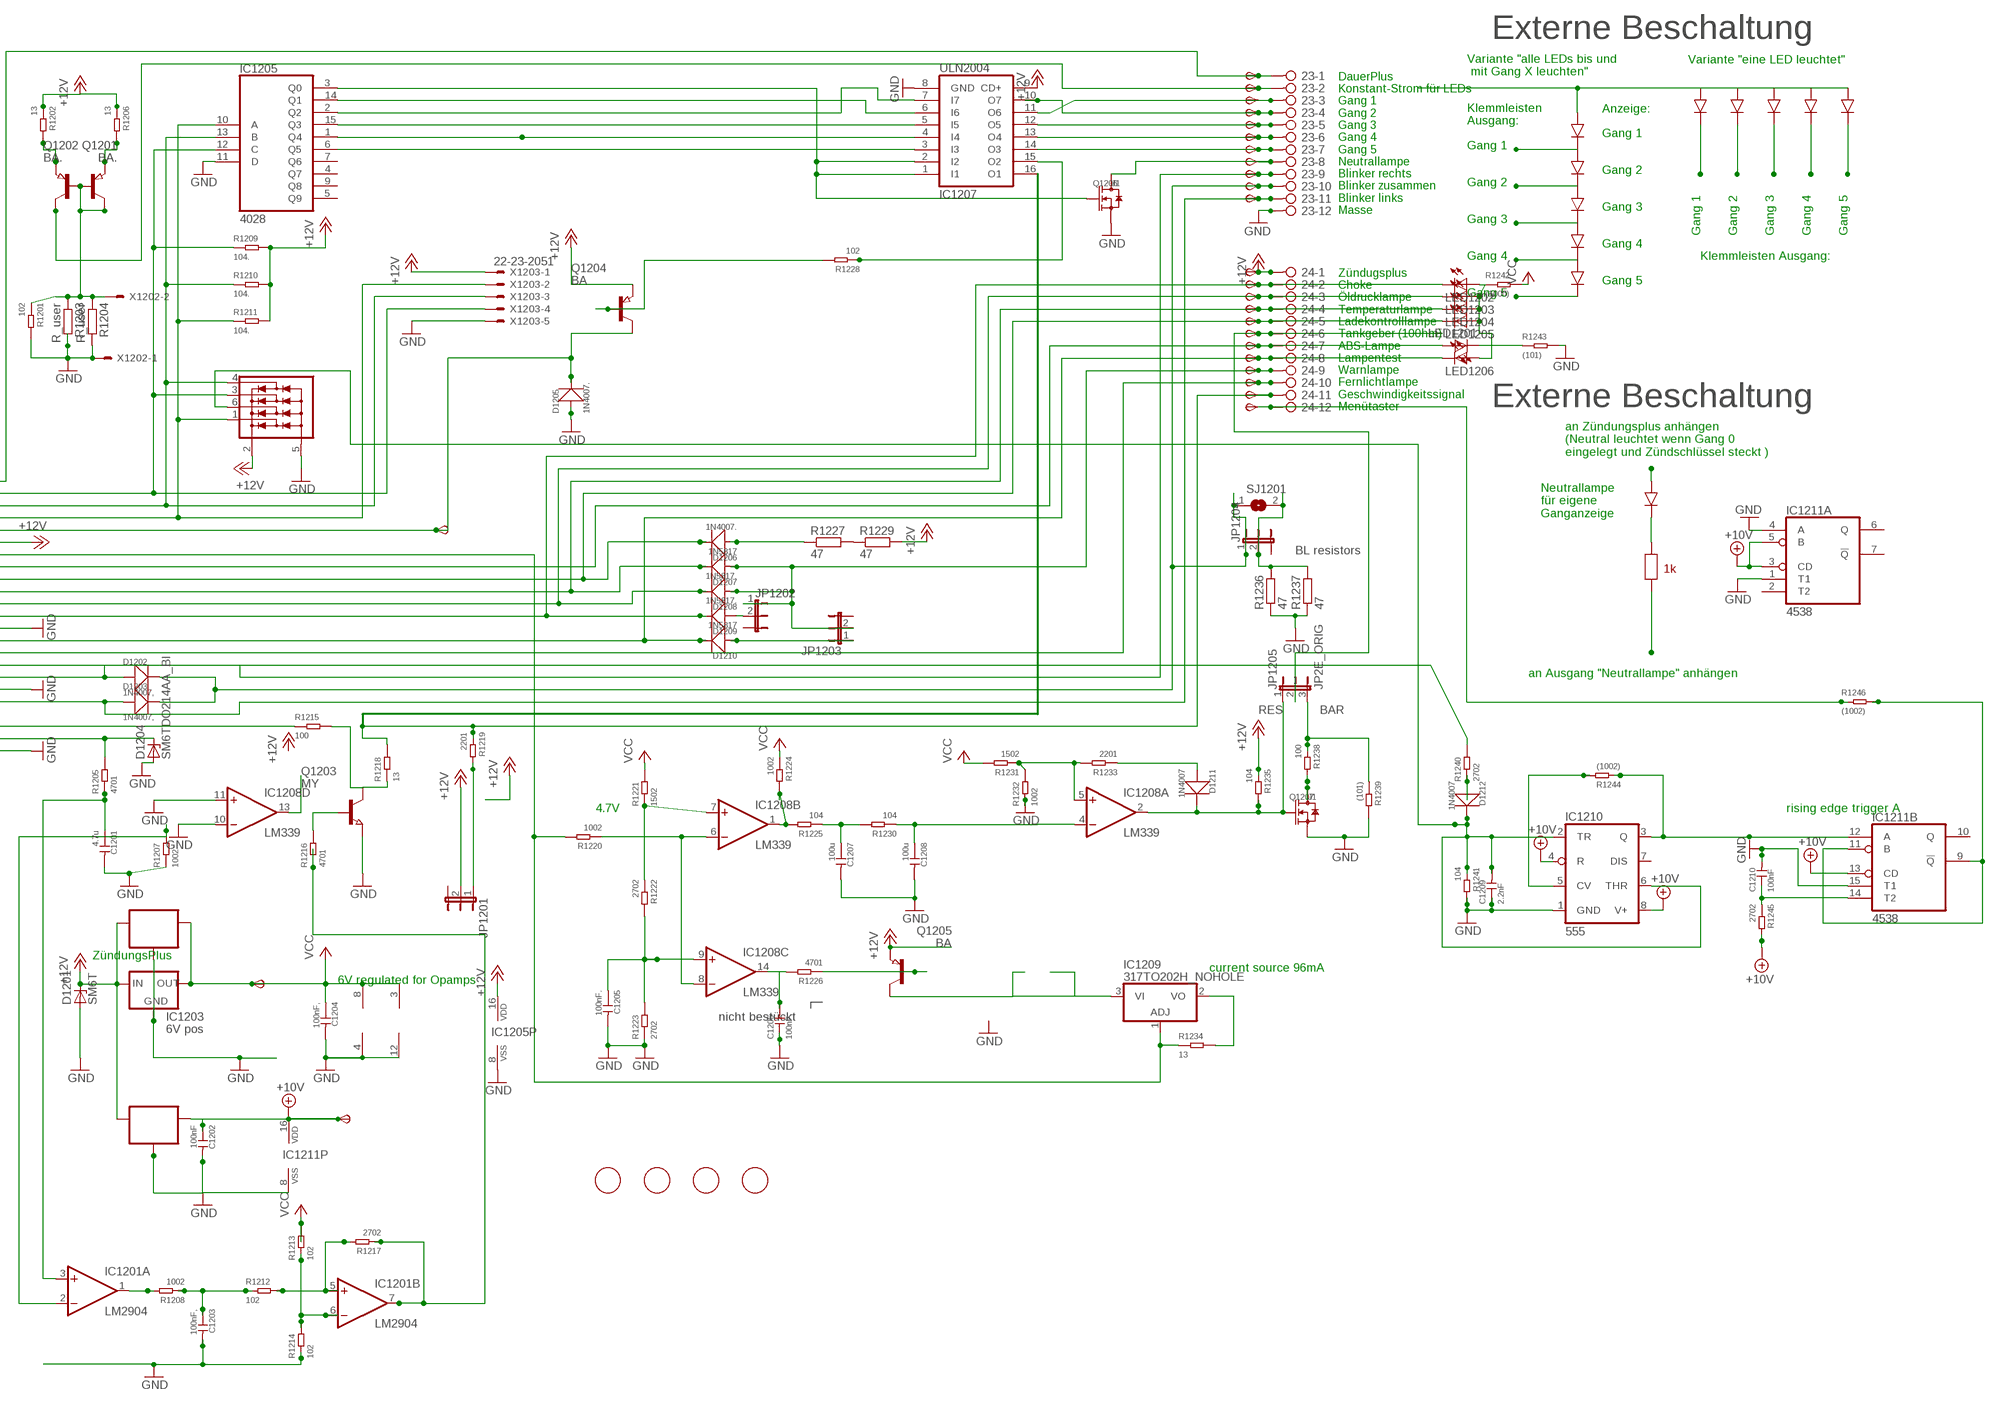
[diagram p23: schematic, sheet 12, part 2 of 2]

(export (version "E")
  (design (tool "Eeschema 10.0.6"))
  (components
    (comp (ref "6V801")
      (value "TPSB2.0")
      (footprint "eagle-import:B2.0")
      (libsource (lib "eagle-import") (part "TPSB2.0"))
    )
    (comp (ref "10V801")
      (value "TPSB2.0")
      (footprint "eagle-import:B2.0")
      (libsource (lib "eagle-import") (part "TPSB2.0"))
    )
    (comp (ref "15")
      (value "2081-1132")
      (footprint "eagle-import:12-PIN")
      (libsource (lib "eagle-import") (part "2081-1132"))
    )
    (comp (ref "16")
      (value "2081-1132")
      (footprint "eagle-import:12-PIN")
      (libsource (lib "eagle-import") (part "2081-1132"))
    )
    (comp (ref "C801")
      (value "4.7u")
      (footprint "eagle-import:C0805")
      (fields (field (name "MPN") "CC0805KKX5R8BB475"))
      (libsource (lib "eagle-import") (part "CERAMIC-4.7UF-25V-10%-X5R(0805)"))
    )
    (comp (ref "C802")
      (value "100nF")
      (footprint "eagle-import:C0805")
      (fields (field (name "MPN") "CC0805KRX7R9BB104"))
      (libsource (lib "eagle-import") (part "CERAMIC-100NF-50V-10%-X7R(0805)"))
    )
    (comp (ref "C803")
      (value "100nF,")
      (footprint "eagle-import:C0805")
      (fields (field (name "MPN") "CC0805KRX7R9BB104"))
      (libsource (lib "eagle-import") (part "CERAMIC-100NF-50V-10%-X7R(0805)"))
    )
    (comp (ref "C804")
      (value "100nF,")
      (footprint "eagle-import:C0805")
      (fields (field (name "MPN") "CC0805KRX7R9BB104"))
      (libsource (lib "eagle-import") (part "CERAMIC-100NF-50V-10%-X7R(0805)"))
    )
    (comp (ref "C805")
      (value "100nF.")
      (footprint "eagle-import:C0805")
      (fields (field (name "MPN") "CC0805KRX7R9BB104"))
      (libsource (lib "eagle-import") (part "CERAMIC-100NF-50V-10%-X7R(0805)"))
    )
    (comp (ref "C806")
      (value "100nF.")
      (footprint "eagle-import:C0805")
      (fields (field (name "MPN") "CC0805KRX7R9BB104"))
      (libsource (lib "eagle-import") (part "CERAMIC-100NF-50V-10%-X7R(0805)"))
    )
    (comp (ref "C807")
      (value "100u")
      (footprint "eagle-import:C1206")
      (fields (field (name "MPN") "GRM31CR60J107ME39L"))
      (libsource (lib "eagle-import") (part "CERAMIC-100UF-6.3V-20%-X5R(1206)"))
    )
    (comp (ref "C808")
      (value "100u")
      (footprint "eagle-import:C1206")
      (fields (field (name "MPN") "GRM31CR60J107ME39L"))
      (libsource (lib "eagle-import") (part "CERAMIC-100UF-6.3V-20%-X5R(1206)"))
    )
    (comp (ref "C809")
      (value "2.2nF")
      (footprint "eagle-import:C0805")
      (fields (field (name "MPN") "CC0805KRX7R9BB104"))
      (libsource (lib "eagle-import") (part "CERAMIC-100NF-50V-10%-X7R(0805)"))
    )
    (comp (ref "C810")
      (value "100nF")
      (footprint "eagle-import:C0805")
      (fields (field (name "MPN") "CC0805KRX7R9BB104"))
      (libsource (lib "eagle-import") (part "CERAMIC-100NF-50V-10%-X7R(0805)"))
    )
    (comp (ref "D801")
      (value "SM6T")
      (footprint "eagle-import:DO214AA")
      (libsource (lib "eagle-import") (part "SM6T"))
    )
    (comp (ref "D802")
      (value "1N4007,")
      (footprint "eagle-import:DO-214AC")
      (fields (field (name "MPN") "1N4007"))
      (libsource (lib "eagle-import") (part "DIODE-GEN-PURPOSE-1KV-1A(DO-214AC)"))
    )
    (comp (ref "D803")
      (value "1N4007,")
      (footprint "eagle-import:DO-214AC")
      (fields (field (name "MPN") "1N4007"))
      (libsource (lib "eagle-import") (part "DIODE-GEN-PURPOSE-1KV-1A(DO-214AC)"))
    )
    (comp (ref "D804")
      (value "SM6TDO214AA_BI")
      (footprint "eagle-import:DO214AA_BI")
      (libsource (lib "eagle-import") (part "SM6TDO214AA_BI"))
    )
    (comp (ref "D805")
      (value "1N4007.")
      (footprint "eagle-import:DO-214AC")
      (fields (field (name "MPN") "1N4007"))
      (libsource (lib "eagle-import") (part "DIODE-GEN-PURPOSE-1KV-1A(DO-214AC)"))
    )
    (comp (ref "D806")
      (value "1N4007.")
      (footprint "eagle-import:DO-214AC")
      (fields (field (name "MPN") "1N4007"))
      (libsource (lib "eagle-import") (part "DIODE-GEN-PURPOSE-1KV-1A(DO-214AC)"))
    )
    (comp (ref "D807")
      (value "1N5817")
      (footprint "eagle-import:DO-214AC_SLIM")
      (libsource (lib "eagle-import") (part "DIODE-GEN-PURPOSE-1KV-1A(DO-214AC)DO-214AC/1206"))
    )
    (comp (ref "D808")
      (value "1N5817.")
      (footprint "eagle-import:DO-214AC_SLIM")
      (libsource (lib "eagle-import") (part "DIODE-GEN-PURPOSE-1KV-1A(DO-214AC)DO-214AC/1206"))
    )
    (comp (ref "D809")
      (value "1N5817.")
      (footprint "eagle-import:DO-214AC_SLIM")
      (libsource (lib "eagle-import") (part "DIODE-GEN-PURPOSE-1KV-1A(DO-214AC)DO-214AC/1206"))
    )
    (comp (ref "D810")
      (value "1N5817")
      (footprint "eagle-import:DO-214AC_SLIM")
      (libsource (lib "eagle-import") (part "DIODE-GEN-PURPOSE-1KV-1A(DO-214AC)DO-214AC/1206"))
    )
    (comp (ref "D811")
      (value "1N4007")
      (footprint "eagle-import:DO-214AC")
      (libsource (lib "eagle-import") (part "DIODE-GEN-PURPOSE-1KV-1A(DO-214AC)"))
    )
    (comp (ref "D812")
      (value "1N4007")
      (footprint "eagle-import:DO-214AC")
      (libsource (lib "eagle-import") (part "DIODE-GEN-PURPOSE-1KV-1A(DO-214AC)"))
    )
    (comp (ref "FID801")
      (value "FIDUCIAL")
      (footprint "eagle-import:FIDUCIAL_1MM")
      (libsource (lib "eagle-import") (part "FIDUCIAL"))
    )
    (comp (ref "FID802")
      (value "FIDUCIAL")
      (footprint "eagle-import:FIDUCIAL_1MM")
      (libsource (lib "eagle-import") (part "FIDUCIAL"))
    )
    (comp (ref "FID803")
      (value "FIDUCIAL")
      (footprint "eagle-import:FIDUCIAL_1MM")
      (libsource (lib "eagle-import") (part "FIDUCIAL"))
    )
    (comp (ref "FID804")
      (value "FIDUCIAL")
      (footprint "eagle-import:FIDUCIAL_1MM")
      (libsource (lib "eagle-import") (part "FIDUCIAL"))
    )
    (comp (ref "IC801")
      (value "LM2904")
      (footprint "eagle-import:SO08")
      (libsource (lib "eagle-import") (part "LM358D"))
    )
    (comp (ref "IC802")
      (value "78L06")
      (footprint "eagle-import:SOT89_ROUND")
      (libsource (lib "eagle-import") (part "78LXXSOT89_ROUND"))
    )
    (comp (ref "IC803")
      (value "6V pos")
      (footprint "eagle-import:78LXX")
      (libsource (lib "eagle-import") (part "v-reg_78LXX"))
    )
    (comp (ref "IC804")
      (value "78L10")
      (footprint "eagle-import:SOT89_ROUND")
      (libsource (lib "eagle-import") (part "78LXXSOT89_ROUND"))
    )
    (comp (ref "IC805")
      (value "4028")
      (footprint "eagle-import:SO16")
      (libsource (lib "eagle-import") (part "4028D"))
    )
    (comp (ref "IC806")
      (value "NUP4304SOT457_R")
      (footprint "eagle-import:SOT457R_PHILIPS")
      (libsource (lib "eagle-import") (part "NUP4304SOT457_R"))
    )
    (comp (ref "IC807")
      (value "ULN2004")
      (footprint "eagle-import:SO16")
      (libsource (lib "eagle-import") (part "ULN2004AD"))
    )
    (comp (ref "IC808")
      (value "LM339")
      (footprint "eagle-import:SO14")
      (libsource (lib "eagle-import") (part "LM339D"))
    )
    (comp (ref "IC809")
      (value "317TO202H_NOHOLE")
      (footprint "eagle-import:TO220H_NOHOLE")
      (libsource (lib "eagle-import") (part "317TO202H_NOHOLE"))
    )
    (comp (ref "IC810")
      (value "555")
      (footprint "eagle-import:SO08")
      (libsource (lib "eagle-import") (part "555DNE"))
    )
    (comp (ref "IC811")
      (value "4538")
      (footprint "eagle-import:SO16")
      (libsource (lib "eagle-import") (part "4538D"))
    )
    (comp (ref "JP801")
      (value "JP2EJP2_SMALLPADS")
      (footprint "eagle-import:JP2_SMALLPADS")
      (libsource (lib "eagle-import") (part "JP2EJP2_SMALLPADS"))
    )
    (comp (ref "JP802")
      (value "JP2EJP2_SMALLPADS")
      (footprint "eagle-import:JP2_SMALLPADS")
      (libsource (lib "eagle-import") (part "JP2EJP2_SMALLPADS"))
    )
    (comp (ref "JP803")
      (value "JP2EJP2_SMALLPADS")
      (footprint "eagle-import:JP2_SMALLPADS")
      (libsource (lib "eagle-import") (part "JP2EJP2_SMALLPADS"))
    )
    (comp (ref "JP804")
      (value "JP2EJP2_SMALLPADS")
      (footprint "eagle-import:JP2_SMALLPADS")
      (libsource (lib "eagle-import") (part "JP2EJP2_SMALLPADS"))
    )
    (comp (ref "JP805")
      (value "JP2E_ORIG")
      (footprint "eagle-import:JP2_ORIG_SMALLPADS")
      (libsource (lib "eagle-import") (part "JP2E_ORIG"))
    )
    (comp (ref "LED801")
      (value "LEDLD260")
      (footprint "eagle-import:LD260")
      (libsource (lib "eagle-import") (part "LEDLD260"))
    )
    (comp (ref "LED802")
      (value "LEDLD260")
      (footprint "eagle-import:LD260")
      (libsource (lib "eagle-import") (part "LEDLD260"))
    )
    (comp (ref "LED803")
      (value "LEDLD260")
      (footprint "eagle-import:LD260")
      (libsource (lib "eagle-import") (part "LEDLD260"))
    )
    (comp (ref "LED804")
      (value "LEDLD260")
      (footprint "eagle-import:LD260")
      (libsource (lib "eagle-import") (part "LEDLD260"))
    )
    (comp (ref "LED805")
      (value "LEDLD260")
      (footprint "eagle-import:LD260")
      (libsource (lib "eagle-import") (part "LEDLD260"))
    )
    (comp (ref "LED806")
      (value "LEDLD260")
      (footprint "eagle-import:LD260")
      (libsource (lib "eagle-import") (part "LEDLD260"))
    )
    (comp (ref "Q801")
      (value "BA.")
      (footprint "eagle-import:SOT89")
      (libsource (lib "eagle-import") (part "PNP-TRANSISTOR_SOT89"))
    )
    (comp (ref "Q802")
      (value "BA.")
      (footprint "eagle-import:SOT89")
      (libsource (lib "eagle-import") (part "PNP-TRANSISTOR_SOT89"))
    )
    (comp (ref "Q803")
      (value "MY")
      (footprint "eagle-import:SOT89")
      (libsource (lib "eagle-import") (part "NPN-TRANSISTOR_SOT89"))
    )
    (comp (ref "Q804")
      (value "BA")
      (footprint "eagle-import:SOT89")
      (libsource (lib "eagle-import") (part "PNP-TRANSISTOR_SOT89"))
    )
    (comp (ref "Q805")
      (value "BA")
      (footprint "eagle-import:SOT89")
      (libsource (lib "eagle-import") (part "PNP-TRANSISTOR_SOT89"))
    )
    (comp (ref "Q806")
      (value "J1")
      (footprint "eagle-import:SOT-23")
      (fields (field (name "MPN") "BSS138W-7-F"))
      (libsource (lib "eagle-import") (part "SMD-MOSFET-N-CH-50V-200MA-BSS138W-7-F(SOT-23)"))
    )
    (comp (ref "Q807")
      (value "J1")
      (footprint "eagle-import:SOT-23")
      (fields (field (name "MPN") "BSS138W-7-F"))
      (libsource (lib "eagle-import") (part "SMD-MOSFET-N-CH-50V-200MA-BSS138W-7-F(SOT-23)"))
    )
    (comp (ref "R801")
      (value "102")
      (footprint "eagle-import:R0805")
      (fields (field (name "MPN") "RC0805JR-071KL"))
      (libsource (lib "eagle-import") (part "SMD-RES-1K-5%-1/8W(0805)"))
    )
    (comp (ref "R802")
      (value "13")
      (footprint "eagle-import:R1206")
      (fields (field (name "MPN") "RC1206JR-0713RL"))
      (libsource (lib "eagle-import") (part "SMD-RES-13R-5%-1/4W(1206)"))
    )
    (comp (ref "R803")
      (value "R_user")
      (footprint "eagle-import:R0805")
      (libsource (lib "eagle-import") (part "R-EU_R0805"))
    )
    (comp (ref "R804")
      (value "R_user")
      (footprint "eagle-import:R0805")
      (libsource (lib "eagle-import") (part "R-EU_R0805"))
    )
    (comp (ref "R805")
      (value "4701")
      (footprint "eagle-import:R0805")
      (fields (field (name "MPN") "RC0805JR-074K7L"))
      (libsource (lib "eagle-import") (part "SMD-RES-4.7K-5%-1/8W(0805)"))
    )
    (comp (ref "R806")
      (value "13")
      (footprint "eagle-import:R1206")
      (fields (field (name "MPN") "RC1206JR-0713RL"))
      (libsource (lib "eagle-import") (part "SMD-RES-13R-5%-1/4W(1206)"))
    )
    (comp (ref "R807")
      (value "1002")
      (footprint "eagle-import:R0805")
      (fields (field (name "MPN") "RC0805FR-0710KL"))
      (libsource (lib "eagle-import") (part "SMD-RES-10K-1%-1/8W(0805)"))
    )
    (comp (ref "R808")
      (value "1002")
      (footprint "eagle-import:R0805")
      (fields (field (name "MPN") "RC0805FR-0710KL"))
      (libsource (lib "eagle-import") (part "SMD-RES-10K-1%-1/8W(0805)"))
    )
    (comp (ref "R809")
      (value "104.")
      (footprint "eagle-import:R0805")
      (fields (field (name "MPN") "RC0805FR-0710KL"))
      (libsource (lib "eagle-import") (part "SMD-RES-10K-1%-1/8W(0805)"))
    )
    (comp (ref "R810")
      (value "104.")
      (footprint "eagle-import:R0805")
      (fields (field (name "MPN") "RC0805FR-0710KL"))
      (libsource (lib "eagle-import") (part "SMD-RES-10K-1%-1/8W(0805)"))
    )
    (comp (ref "R811")
      (value "104.")
      (footprint "eagle-import:R0805")
      (fields (field (name "MPN") "RC0805FR-0710KL"))
      (libsource (lib "eagle-import") (part "SMD-RES-10K-1%-1/8W(0805)"))
    )
    (comp (ref "R812")
      (value "102")
      (footprint "eagle-import:R0805")
      (fields (field (name "MPN") "RC0805JR-071KL"))
      (libsource (lib "eagle-import") (part "SMD-RES-1K-5%-1/8W(0805)"))
    )
    (comp (ref "R813")
      (value "102")
      (footprint "eagle-import:R0805")
      (fields (field (name "MPN") "RC0805JR-071KL"))
      (libsource (lib "eagle-import") (part "SMD-RES-1K-5%-1/8W(0805)"))
    )
    (comp (ref "R814")
      (value "102")
      (footprint "eagle-import:R0805")
      (fields (field (name "MPN") "RC0805JR-071KL"))
      (libsource (lib "eagle-import") (part "SMD-RES-1K-5%-1/8W(0805)"))
    )
    (comp (ref "R815")
      (value "100")
      (footprint "eagle-import:R0805")
      (fields (field (name "MPN") "RC0805JR-07220RL"))
      (libsource (lib "eagle-import") (part "SMD-RES-220R-5%-1/8W(0805)"))
    )
    (comp (ref "R816")
      (value "4701")
      (footprint "eagle-import:R0805")
      (fields (field (name "MPN") "RC0805JR-074K7L"))
      (libsource (lib "eagle-import") (part "SMD-RES-4.7K-5%-1/8W(0805)"))
    )
    (comp (ref "R817")
      (value "2702")
      (footprint "eagle-import:R0805")
      (fields (field (name "MPN") "RC0805JR-074K7L"))
      (libsource (lib "eagle-import") (part "SMD-RES-4.7K-5%-1/8W(0805)"))
    )
    (comp (ref "R818")
      (value "13")
      (footprint "eagle-import:R1206")
      (fields (field (name "MPN") "RC1206JR-0713RL"))
      (libsource (lib "eagle-import") (part "SMD-RES-13R-5%-1/4W(1206)"))
    )
    (comp (ref "R819")
      (value "2201")
      (footprint "eagle-import:R0805")
      (fields (field (name "MPN") "RC0805JR-072K2L"))
      (libsource (lib "eagle-import") (part "SMD-RES-2.2K-5%-1/8W(0805)"))
    )
    (comp (ref "R820")
      (value "1002")
      (footprint "eagle-import:R0805")
      (fields (field (name "MPN") "RC0805FR-0710KL"))
      (libsource (lib "eagle-import") (part "SMD-RES-10K-1%-1/8W(0805)"))
    )
    (comp (ref "R821")
      (value "1502")
      (footprint "eagle-import:R0805")
      (fields (field (name "MPN") "RC0805FR-0710KL"))
      (libsource (lib "eagle-import") (part "SMD-RES-10K-1%-1/8W(0805)"))
    )
    (comp (ref "R822")
      (value "2702")
      (footprint "eagle-import:R0805")
      (fields (field (name "MPN") "RC0805JR-074K7L"))
      (libsource (lib "eagle-import") (part "SMD-RES-4.7K-5%-1/8W(0805)"))
    )
    (comp (ref "R823")
      (value "2702")
      (footprint "eagle-import:R0805")
      (fields (field (name "MPN") "RC0805JR-074K7L"))
      (libsource (lib "eagle-import") (part "SMD-RES-4.7K-5%-1/8W(0805)"))
    )
    (comp (ref "R824")
      (value "1002")
      (footprint "eagle-import:R0805")
      (fields (field (name "MPN") "RC0805FR-0710KL"))
      (libsource (lib "eagle-import") (part "SMD-RES-10K-1%-1/8W(0805)"))
    )
    (comp (ref "R825")
      (value "104")
      (footprint "eagle-import:R0805")
      (fields (field (name "MPN") "RC0805FR-0710KL"))
      (libsource (lib "eagle-import") (part "SMD-RES-10K-1%-1/8W(0805)"))
    )
    (comp (ref "R826")
      (value "4701")
      (footprint "eagle-import:R0805")
      (fields (field (name "MPN") "RC0805JR-074K7L"))
      (libsource (lib "eagle-import") (part "SMD-RES-4.7K-5%-1/8W(0805)"))
    )
    (comp (ref "R827")
      (value "47")
      (footprint "eagle-import:V235_17_1MM")
      (libsource (lib "eagle-import") (part "R-EU_V235/17_1MM"))
    )
    (comp (ref "R828")
      (value "102")
      (footprint "eagle-import:R0805")
      (fields (field (name "MPN") "RC0805JR-071KL"))
      (libsource (lib "eagle-import") (part "SMD-RES-1K-5%-1/8W(0805)"))
    )
    (comp (ref "R829")
      (value "47")
      (footprint "eagle-import:V235_17_1MM")
      (libsource (lib "eagle-import") (part "R-EU_V235/17_1MM"))
    )
    (comp (ref "R830")
      (value "104")
      (footprint "eagle-import:R0805")
      (fields (field (name "MPN") "RC0805FR-0710KL"))
      (libsource (lib "eagle-import") (part "SMD-RES-10K-1%-1/8W(0805)"))
    )
    (comp (ref "R831")
      (value "1502")
      (footprint "eagle-import:R0805")
      (fields (field (name "MPN") "RC0805FR-0710KL"))
      (libsource (lib "eagle-import") (part "SMD-RES-10K-1%-1/8W(0805)"))
    )
    (comp (ref "R832")
      (value "1002")
      (footprint "eagle-import:R0805")
      (fields (field (name "MPN") "RC0805FR-0710KL"))
      (libsource (lib "eagle-import") (part "SMD-RES-10K-1%-1/8W(0805)"))
    )
    (comp (ref "R833")
      (value "2201")
      (footprint "eagle-import:R0805")
      (fields (field (name "MPN") "RC0805JR-072K2L"))
      (libsource (lib "eagle-import") (part "SMD-RES-2.2K-5%-1/8W(0805)"))
    )
    (comp (ref "R834")
      (value "13")
      (footprint "eagle-import:R1206")
      (fields (field (name "MPN") "RC1206JR-0713RL"))
      (libsource (lib "eagle-import") (part "SMD-RES-13R-5%-1/4W(1206)"))
    )
    (comp (ref "R835")
      (value "104")
      (footprint "eagle-import:R0805")
      (fields (field (name "MPN") "RC0805FR-0710KL"))
      (libsource (lib "eagle-import") (part "SMD-RES-10K-1%-1/8W(0805)"))
    )
    (comp (ref "R836")
      (value "47")
      (footprint "eagle-import:V235_17_1MM")
      (libsource (lib "eagle-import") (part "R-EU_V235/17_1MM"))
    )
    (comp (ref "R837")
      (value "47")
      (footprint "eagle-import:V235_17_1MM")
      (libsource (lib "eagle-import") (part "R-EU_V235/17_1MM"))
    )
    (comp (ref "R838")
      (value "100")
      (footprint "eagle-import:R0805")
      (fields (field (name "MPN") "RC0805JR-072K2L"))
      (libsource (lib "eagle-import") (part "SMD-RES-2.2K-5%-1/8W(0805)"))
    )
    (comp (ref "R839")
      (value "(101)")
      (footprint "eagle-import:R0805")
      (fields (field (name "MPN") "RC0805JR-072K2L"))
      (libsource (lib "eagle-import") (part "SMD-RES-2.2K-5%-1/8W(0805)"))
    )
    (comp (ref "R840")
      (value "2702")
      (footprint "eagle-import:R0805")
      (fields (field (name "MPN") "RC0805FR-0710KL"))
      (libsource (lib "eagle-import") (part "SMD-RES-10K-1%-1/8W(0805)"))
    )
    (comp (ref "R841")
      (value "104")
      (footprint "eagle-import:R0805")
      (fields (field (name "MPN") "RC0805FR-0710KL"))
      (libsource (lib "eagle-import") (part "SMD-RES-10K-1%-1/8W(0805)"))
    )
    (comp (ref "R842")
      (value "(1000)")
      (footprint "eagle-import:R0805")
      (fields (field (name "MPN") "RC0805JR-07100RL"))
      (libsource (lib "eagle-import") (part "SMD-RES-100R-5%-1/8W(0805)"))
    )
    (comp (ref "R843")
      (value "(101)")
      (footprint "eagle-import:R0805")
      (fields (field (name "MPN") "RC0805JR-07100RL"))
      (libsource (lib "eagle-import") (part "SMD-RES-100R-5%-1/8W(0805)"))
    )
    (comp (ref "R844")
      (value "(1002)")
      (footprint "eagle-import:R0805")
      (fields (field (name "MPN") "RC0805FR-0710KL"))
      (libsource (lib "eagle-import") (part "SMD-RES-10K-1%-1/8W(0805)"))
    )
    (comp (ref "R845")
      (value "2702")
      (footprint "eagle-import:R0805")
      (fields (field (name "MPN") "RC0805JR-074K7L"))
      (libsource (lib "eagle-import") (part "SMD-RES-4.7K-5%-1/8W(0805)"))
    )
    (comp (ref "R846")
      (value "(1002)")
      (footprint "eagle-import:R0805")
      (fields (field (name "MPN") "RC0805JR-074K7L"))
      (libsource (lib "eagle-import") (part "SMD-RES-4.7K-5%-1/8W(0805)"))
    )
    (comp (ref "SJ801")
      (value "SJ")
      (footprint "eagle-import:SJ")
      (libsource (lib "eagle-import") (part "SJ"))
    )
    (comp (ref "START801")
      (value "TPSB2.0")
      (footprint "eagle-import:B2.0")
      (libsource (lib "eagle-import") (part "TPSB2.0"))
    )
    (comp (ref "TP162")
      (value "TPSB2.0")
      (footprint "eagle-import:B2.0")
      (libsource (lib "eagle-import") (part "TPSB2.0"))
    )
    (comp (ref "TP163")
      (value "TPSB2.0")
      (footprint "eagle-import:B2.0")
      (libsource (lib "eagle-import") (part "TPSB2.0"))
    )
    (comp (ref "TP164")
      (value "TPSB2.0")
      (footprint "eagle-import:B2.0")
      (libsource (lib "eagle-import") (part "TPSB2.0"))
    )
    (comp (ref "TP165")
      (value "TPSB2.0")
      (footprint "eagle-import:B2.0")
      (libsource (lib "eagle-import") (part "TPSB2.0"))
    )
    (comp (ref "TP166")
      (value "TPSB2.0")
      (footprint "eagle-import:B2.0")
      (libsource (lib "eagle-import") (part "TPSB2.0"))
    )
    (comp (ref "TP167")
      (value "TPSB2.0")
      (footprint "eagle-import:B2.0")
      (libsource (lib "eagle-import") (part "TPSB2.0"))
    )
    (comp (ref "TP168")
      (value "TPSB2.0")
      (footprint "eagle-import:B2.0")
      (libsource (lib "eagle-import") (part "TPSB2.0"))
    )
    (comp (ref "TP169")
      (value "TPSB2.0")
      (footprint "eagle-import:B2.0")
      (libsource (lib "eagle-import") (part "TPSB2.0"))
    )
    (comp (ref "TP170")
      (value "TPSB2.0")
      (footprint "eagle-import:B2.0")
      (libsource (lib "eagle-import") (part "TPSB2.0"))
    )
    (comp (ref "TP171")
      (value "TPSB2.0")
      (footprint "eagle-import:B2.0")
      (libsource (lib "eagle-import") (part "TPSB2.0"))
    )
    (comp (ref "TP172")
      (value "TPSB2.0")
      (footprint "eagle-import:B2.0")
      (libsource (lib "eagle-import") (part "TPSB2.0"))
    )
    (comp (ref "TP173")
      (value "TPSB2.0")
      (footprint "eagle-import:B2.0")
      (libsource (lib "eagle-import") (part "TPSB2.0"))
    )
    (comp (ref "TP174")
      (value "TPSB2.0")
      (footprint "eagle-import:B2.0")
      (libsource (lib "eagle-import") (part "TPSB2.0"))
    )
    (comp (ref "TP175")
      (value "TPSB2.0")
      (footprint "eagle-import:B2.0")
      (libsource (lib "eagle-import") (part "TPSB2.0"))
    )
    (comp (ref "TP176")
      (value "TPSB2.0")
      (footprint "eagle-import:B2.0")
      (libsource (lib "eagle-import") (part "TPSB2.0"))
    )
    (comp (ref "TP177")
      (value "TPSB2.0")
      (footprint "eagle-import:B2.0")
      (libsource (lib "eagle-import") (part "TPSB2.0"))
    )
    (comp (ref "TP178")
      (value "TPSB2.0")
      (footprint "eagle-import:B2.0")
      (libsource (lib "eagle-import") (part "TPSB2.0"))
    )
    (comp (ref "TP179")
      (value "TPSB2.0")
      (footprint "eagle-import:B2.0")
      (libsource (lib "eagle-import") (part "TPSB2.0"))
    )
    (comp (ref "TP180")
      (value "TPSB1,27")
      (footprint "eagle-import:B1,27")
      (libsource (lib "eagle-import") (part "TPSB1,27"))
    )
    (comp (ref "TP181")
      (value "TPSB2.0")
      (footprint "eagle-import:B2.0")
      (libsource (lib "eagle-import") (part "TPSB2.0"))
    )
    (comp (ref "TP182")
      (value "TPSB2.0")
      (footprint "eagle-import:B2.0")
      (libsource (lib "eagle-import") (part "TPSB2.0"))
    )
    (comp (ref "TP183")
      (value "TPSB2.0")
      (footprint "eagle-import:B2.0")
      (libsource (lib "eagle-import") (part "TPSB2.0"))
    )
    (comp (ref "TP184")
      (value "TPSB2.0")
      (footprint "eagle-import:B2.0")
      (libsource (lib "eagle-import") (part "TPSB2.0"))
    )
    (comp (ref "X801")
      (value "CON_BMWV2")
      (footprint "eagle-import:24-PIN_V2")
      (libsource (lib "eagle-import") (part "CON_BMWV2"))
    )
    (comp (ref "X802")
      (value "22-23-2021")
      (footprint "eagle-import:22-23-2021")
      (fields (field (name "MF") "MOLEX"))
      (libsource (lib "eagle-import") (part "22-23-2021"))
    )
    (comp (ref "X803")
      (value "22-23-2051")
      (footprint "eagle-import:22-23-2051")
      (fields (field (name "MF") "MOLEX"))
      (libsource (lib "eagle-import") (part "22-23-2051"))
    )
    (comp (ref "6V901")
      (value "TPSB2.0")
      (footprint "eagle-import:B2.0")
      (libsource (lib "eagle-import") (part "TPSB2.0"))
    )
    (comp (ref "10V901")
      (value "TPSB2.0")
      (footprint "eagle-import:B2.0")
      (libsource (lib "eagle-import") (part "TPSB2.0"))
    )
    (comp (ref "17")
      (value "2081-1132")
      (footprint "eagle-import:12-PIN")
      (libsource (lib "eagle-import") (part "2081-1132"))
    )
    (comp (ref "18")
      (value "2081-1132")
      (footprint "eagle-import:12-PIN")
      (libsource (lib "eagle-import") (part "2081-1132"))
    )
    (comp (ref "C901")
      (value "4.7u")
      (footprint "eagle-import:C0805")
      (fields (field (name "MPN") "CC0805KKX5R8BB475"))
      (libsource (lib "eagle-import") (part "CERAMIC-4.7UF-25V-10%-X5R(0805)"))
    )
    (comp (ref "C902")
      (value "100nF")
      (footprint "eagle-import:C0805")
      (fields (field (name "MPN") "CC0805KRX7R9BB104"))
      (libsource (lib "eagle-import") (part "CERAMIC-100NF-50V-10%-X7R(0805)"))
    )
    (comp (ref "C903")
      (value "100nF,")
      (footprint "eagle-import:C0805")
      (fields (field (name "MPN") "CC0805KRX7R9BB104"))
      (libsource (lib "eagle-import") (part "CERAMIC-100NF-50V-10%-X7R(0805)"))
    )
    (comp (ref "C904")
      (value "100nF,")
      (footprint "eagle-import:C0805")
      (fields (field (name "MPN") "CC0805KRX7R9BB104"))
      (libsource (lib "eagle-import") (part "CERAMIC-100NF-50V-10%-X7R(0805)"))
    )
    (comp (ref "C905")
      (value "100nF.")
      (footprint "eagle-import:C0805")
      (fields (field (name "MPN") "CC0805KRX7R9BB104"))
      (libsource (lib "eagle-import") (part "CERAMIC-100NF-50V-10%-X7R(0805)"))
    )
    (comp (ref "C906")
      (value "100nF.")
      (footprint "eagle-import:C0805")
      (fields (field (name "MPN") "CC0805KRX7R9BB104"))
      (libsource (lib "eagle-import") (part "CERAMIC-100NF-50V-10%-X7R(0805)"))
    )
    (comp (ref "C907")
      (value "100u")
      (footprint "eagle-import:C1206")
      (fields (field (name "MPN") "GRM31CR60J107ME39L"))
      (libsource (lib "eagle-import") (part "CERAMIC-100UF-6.3V-20%-X5R(1206)"))
    )
    (comp (ref "C908")
      (value "100u")
      (footprint "eagle-import:C1206")
      (fields (field (name "MPN") "GRM31CR60J107ME39L"))
      (libsource (lib "eagle-import") (part "CERAMIC-100UF-6.3V-20%-X5R(1206)"))
    )
    (comp (ref "C909")
      (value "2.2nF")
      (footprint "eagle-import:C0805")
      (fields (field (name "MPN") "CC0805KRX7R9BB104"))
      (libsource (lib "eagle-import") (part "CERAMIC-100NF-50V-10%-X7R(0805)"))
    )
    (comp (ref "C910")
      (value "100nF")
      (footprint "eagle-import:C0805")
      (fields (field (name "MPN") "CC0805KRX7R9BB104"))
      (libsource (lib "eagle-import") (part "CERAMIC-100NF-50V-10%-X7R(0805)"))
    )
    (comp (ref "D901")
      (value "SM6T")
      (footprint "eagle-import:DO214AA")
      (libsource (lib "eagle-import") (part "SM6T"))
    )
    (comp (ref "D902")
      (value "1N4007,")
      (footprint "eagle-import:DO-214AC")
      (fields (field (name "MPN") "1N4007"))
      (libsource (lib "eagle-import") (part "DIODE-GEN-PURPOSE-1KV-1A(DO-214AC)"))
    )
    (comp (ref "D903")
      (value "1N4007,")
      (footprint "eagle-import:DO-214AC")
      (fields (field (name "MPN") "1N4007"))
      (libsource (lib "eagle-import") (part "DIODE-GEN-PURPOSE-1KV-1A(DO-214AC)"))
    )
    (comp (ref "D904")
      (value "SM6TDO214AA_BI")
      (footprint "eagle-import:DO214AA_BI")
      (libsource (lib "eagle-import") (part "SM6TDO214AA_BI"))
    )
    (comp (ref "D905")
      (value "1N4007.")
      (footprint "eagle-import:DO-214AC")
      (fields (field (name "MPN") "1N4007"))
      (libsource (lib "eagle-import") (part "DIODE-GEN-PURPOSE-1KV-1A(DO-214AC)"))
    )
    (comp (ref "D906")
      (value "1N4007.")
      (footprint "eagle-import:DO-214AC")
      (fields (field (name "MPN") "1N4007"))
      (libsource (lib "eagle-import") (part "DIODE-GEN-PURPOSE-1KV-1A(DO-214AC)"))
    )
    (comp (ref "D907")
      (value "1N5817")
      (footprint "eagle-import:DO-214AC_SLIM")
      (libsource (lib "eagle-import") (part "DIODE-GEN-PURPOSE-1KV-1A(DO-214AC)DO-214AC/1206"))
    )
    (comp (ref "D908")
      (value "1N5817.")
      (footprint "eagle-import:DO-214AC_SLIM")
      (libsource (lib "eagle-import") (part "DIODE-GEN-PURPOSE-1KV-1A(DO-214AC)DO-214AC/1206"))
    )
    (comp (ref "D909")
      (value "1N5817.")
      (footprint "eagle-import:DO-214AC_SLIM")
      (libsource (lib "eagle-import") (part "DIODE-GEN-PURPOSE-1KV-1A(DO-214AC)DO-214AC/1206"))
    )
    (comp (ref "D910")
      (value "1N5817")
      (footprint "eagle-import:DO-214AC_SLIM")
      (libsource (lib "eagle-import") (part "DIODE-GEN-PURPOSE-1KV-1A(DO-214AC)DO-214AC/1206"))
    )
    (comp (ref "D911")
      (value "1N4007")
      (footprint "eagle-import:DO-214AC")
      (libsource (lib "eagle-import") (part "DIODE-GEN-PURPOSE-1KV-1A(DO-214AC)"))
    )
    (comp (ref "D912")
      (value "1N4007")
      (footprint "eagle-import:DO-214AC")
      (libsource (lib "eagle-import") (part "DIODE-GEN-PURPOSE-1KV-1A(DO-214AC)"))
    )
    (comp (ref "FID901")
      (value "FIDUCIAL")
      (footprint "eagle-import:FIDUCIAL_1MM")
      (libsource (lib "eagle-import") (part "FIDUCIAL"))
    )
    (comp (ref "FID902")
      (value "FIDUCIAL")
      (footprint "eagle-import:FIDUCIAL_1MM")
      (libsource (lib "eagle-import") (part "FIDUCIAL"))
    )
    (comp (ref "FID903")
      (value "FIDUCIAL")
      (footprint "eagle-import:FIDUCIAL_1MM")
      (libsource (lib "eagle-import") (part "FIDUCIAL"))
    )
    (comp (ref "FID904")
      (value "FIDUCIAL")
      (footprint "eagle-import:FIDUCIAL_1MM")
      (libsource (lib "eagle-import") (part "FIDUCIAL"))
    )
    (comp (ref "IC901")
      (value "LM2904")
      (footprint "eagle-import:SO08")
      (libsource (lib "eagle-import") (part "LM358D"))
    )
    (comp (ref "IC902")
      (value "78L06")
      (footprint "eagle-import:SOT89_ROUND")
      (libsource (lib "eagle-import") (part "78LXXSOT89_ROUND"))
    )
    (comp (ref "IC903")
      (value "6V pos")
      (footprint "eagle-import:78LXX")
      (libsource (lib "eagle-import") (part "v-reg_78LXX"))
    )
    (comp (ref "IC904")
      (value "78L10")
      (footprint "eagle-import:SOT89_ROUND")
      (libsource (lib "eagle-import") (part "78LXXSOT89_ROUND"))
    )
    (comp (ref "IC905")
      (value "4028")
      (footprint "eagle-import:SO16")
      (libsource (lib "eagle-import") (part "4028D"))
    )
    (comp (ref "IC906")
      (value "NUP4304SOT457_R")
      (footprint "eagle-import:SOT457R_PHILIPS")
      (libsource (lib "eagle-import") (part "NUP4304SOT457_R"))
    )
    (comp (ref "IC907")
      (value "ULN2004")
      (footprint "eagle-import:SO16")
      (libsource (lib "eagle-import") (part "ULN2004AD"))
    )
    (comp (ref "IC908")
      (value "LM339")
      (footprint "eagle-import:SO14")
      (libsource (lib "eagle-import") (part "LM339D"))
    )
    (comp (ref "IC909")
      (value "317TO202H_NOHOLE")
      (footprint "eagle-import:TO220H_NOHOLE")
      (libsource (lib "eagle-import") (part "317TO202H_NOHOLE"))
    )
    (comp (ref "IC910")
      (value "555")
      (footprint "eagle-import:SO08")
      (libsource (lib "eagle-import") (part "555DNE"))
    )
    (comp (ref "IC911")
      (value "4538")
      (footprint "eagle-import:SO16")
      (libsource (lib "eagle-import") (part "4538D"))
    )
    (comp (ref "JP901")
      (value "JP2EJP2_SMALLPADS")
      (footprint "eagle-import:JP2_SMALLPADS")
      (libsource (lib "eagle-import") (part "JP2EJP2_SMALLPADS"))
    )
    (comp (ref "JP902")
      (value "JP2EJP2_SMALLPADS")
      (footprint "eagle-import:JP2_SMALLPADS")
      (libsource (lib "eagle-import") (part "JP2EJP2_SMALLPADS"))
    )
    (comp (ref "JP903")
      (value "JP2EJP2_SMALLPADS")
      (footprint "eagle-import:JP2_SMALLPADS")
      (libsource (lib "eagle-import") (part "JP2EJP2_SMALLPADS"))
    )
    (comp (ref "JP904")
      (value "JP2EJP2_SMALLPADS")
      (footprint "eagle-import:JP2_SMALLPADS")
      (libsource (lib "eagle-import") (part "JP2EJP2_SMALLPADS"))
    )
    (comp (ref "JP905")
      (value "JP2E_ORIG")
      (footprint "eagle-import:JP2_ORIG_SMALLPADS")
      (libsource (lib "eagle-import") (part "JP2E_ORIG"))
    )
    (comp (ref "LED901")
      (value "LEDLD260")
      (footprint "eagle-import:LD260")
      (libsource (lib "eagle-import") (part "LEDLD260"))
    )
    (comp (ref "LED902")
      (value "LEDLD260")
      (footprint "eagle-import:LD260")
      (libsource (lib "eagle-import") (part "LEDLD260"))
    )
    (comp (ref "LED903")
      (value "LEDLD260")
      (footprint "eagle-import:LD260")
      (libsource (lib "eagle-import") (part "LEDLD260"))
    )
    (comp (ref "LED904")
      (value "LEDLD260")
      (footprint "eagle-import:LD260")
      (libsource (lib "eagle-import") (part "LEDLD260"))
    )
    (comp (ref "LED905")
      (value "LEDLD260")
      (footprint "eagle-import:LD260")
      (libsource (lib "eagle-import") (part "LEDLD260"))
    )
    (comp (ref "LED906")
      (value "LEDLD260")
      (footprint "eagle-import:LD260")
      (libsource (lib "eagle-import") (part "LEDLD260"))
    )
    (comp (ref "Q901")
      (value "BA.")
      (footprint "eagle-import:SOT89")
      (libsource (lib "eagle-import") (part "PNP-TRANSISTOR_SOT89"))
    )
    (comp (ref "Q902")
      (value "BA.")
      (footprint "eagle-import:SOT89")
      (libsource (lib "eagle-import") (part "PNP-TRANSISTOR_SOT89"))
    )
    (comp (ref "Q903")
      (value "MY")
      (footprint "eagle-import:SOT89")
      (libsource (lib "eagle-import") (part "NPN-TRANSISTOR_SOT89"))
    )
    (comp (ref "Q904")
      (value "BA")
      (footprint "eagle-import:SOT89")
      (libsource (lib "eagle-import") (part "PNP-TRANSISTOR_SOT89"))
    )
    (comp (ref "Q905")
      (value "BA")
      (footprint "eagle-import:SOT89")
      (libsource (lib "eagle-import") (part "PNP-TRANSISTOR_SOT89"))
    )
    (comp (ref "Q906")
      (value "J1")
      (footprint "eagle-import:SOT-23")
      (fields (field (name "MPN") "BSS138W-7-F"))
      (libsource (lib "eagle-import") (part "SMD-MOSFET-N-CH-50V-200MA-BSS138W-7-F(SOT-23)"))
    )
    (comp (ref "Q907")
      (value "J1")
      (footprint "eagle-import:SOT-23")
      (fields (field (name "MPN") "BSS138W-7-F"))
      (libsource (lib "eagle-import") (part "SMD-MOSFET-N-CH-50V-200MA-BSS138W-7-F(SOT-23)"))
    )
    (comp (ref "R901")
      (value "102")
      (footprint "eagle-import:R0805")
      (fields (field (name "MPN") "RC0805JR-071KL"))
      (libsource (lib "eagle-import") (part "SMD-RES-1K-5%-1/8W(0805)"))
    )
    (comp (ref "R902")
      (value "13")
      (footprint "eagle-import:R1206")
      (fields (field (name "MPN") "RC1206JR-0713RL"))
      (libsource (lib "eagle-import") (part "SMD-RES-13R-5%-1/4W(1206)"))
    )
    (comp (ref "R903")
      (value "R_user")
      (footprint "eagle-import:R0805")
      (libsource (lib "eagle-import") (part "R-EU_R0805"))
    )
    (comp (ref "R904")
      (value "R_user")
      (footprint "eagle-import:R0805")
      (libsource (lib "eagle-import") (part "R-EU_R0805"))
    )
    (comp (ref "R905")
      (value "4701")
      (footprint "eagle-import:R0805")
      (fields (field (name "MPN") "RC0805JR-074K7L"))
      (libsource (lib "eagle-import") (part "SMD-RES-4.7K-5%-1/8W(0805)"))
    )
    (comp (ref "R906")
      (value "13")
      (footprint "eagle-import:R1206")
      (fields (field (name "MPN") "RC1206JR-0713RL"))
      (libsource (lib "eagle-import") (part "SMD-RES-13R-5%-1/4W(1206)"))
    )
    (comp (ref "R907")
      (value "1002")
      (footprint "eagle-import:R0805")
      (fields (field (name "MPN") "RC0805FR-0710KL"))
      (libsource (lib "eagle-import") (part "SMD-RES-10K-1%-1/8W(0805)"))
    )
    (comp (ref "R908")
      (value "1002")
      (footprint "eagle-import:R0805")
      (fields (field (name "MPN") "RC0805FR-0710KL"))
      (libsource (lib "eagle-import") (part "SMD-RES-10K-1%-1/8W(0805)"))
    )
    (comp (ref "R909")
      (value "104.")
      (footprint "eagle-import:R0805")
      (fields (field (name "MPN") "RC0805FR-0710KL"))
      (libsource (lib "eagle-import") (part "SMD-RES-10K-1%-1/8W(0805)"))
    )
    (comp (ref "R910")
      (value "104.")
      (footprint "eagle-import:R0805")
      (fields (field (name "MPN") "RC0805FR-0710KL"))
      (libsource (lib "eagle-import") (part "SMD-RES-10K-1%-1/8W(0805)"))
    )
    (comp (ref "R911")
      (value "104.")
      (footprint "eagle-import:R0805")
      (fields (field (name "MPN") "RC0805FR-0710KL"))
      (libsource (lib "eagle-import") (part "SMD-RES-10K-1%-1/8W(0805)"))
    )
    (comp (ref "R912")
      (value "102")
      (footprint "eagle-import:R0805")
      (fields (field (name "MPN") "RC0805JR-071KL"))
      (libsource (lib "eagle-import") (part "SMD-RES-1K-5%-1/8W(0805)"))
    )
    (comp (ref "R913")
      (value "102")
      (footprint "eagle-import:R0805")
      (fields (field (name "MPN") "RC0805JR-071KL"))
      (libsource (lib "eagle-import") (part "SMD-RES-1K-5%-1/8W(0805)"))
    )
    (comp (ref "R914")
      (value "102")
      (footprint "eagle-import:R0805")
      (fields (field (name "MPN") "RC0805JR-071KL"))
      (libsource (lib "eagle-import") (part "SMD-RES-1K-5%-1/8W(0805)"))
    )
    (comp (ref "R915")
      (value "100")
      (footprint "eagle-import:R0805")
      (fields (field (name "MPN") "RC0805JR-07220RL"))
      (libsource (lib "eagle-import") (part "SMD-RES-220R-5%-1/8W(0805)"))
    )
    (comp (ref "R916")
      (value "4701")
      (footprint "eagle-import:R0805")
      (fields (field (name "MPN") "RC0805JR-074K7L"))
      (libsource (lib "eagle-import") (part "SMD-RES-4.7K-5%-1/8W(0805)"))
    )
    (comp (ref "R917")
      (value "2702")
      (footprint "eagle-import:R0805")
      (fields (field (name "MPN") "RC0805JR-074K7L"))
      (libsource (lib "eagle-import") (part "SMD-RES-4.7K-5%-1/8W(0805)"))
    )
    (comp (ref "R918")
      (value "13")
      (footprint "eagle-import:R1206")
      (fields (field (name "MPN") "RC1206JR-0713RL"))
      (libsource (lib "eagle-import") (part "SMD-RES-13R-5%-1/4W(1206)"))
    )
    (comp (ref "R919")
      (value "2201")
      (footprint "eagle-import:R0805")
      (fields (field (name "MPN") "RC0805JR-072K2L"))
      (libsource (lib "eagle-import") (part "SMD-RES-2.2K-5%-1/8W(0805)"))
    )
    (comp (ref "R920")
      (value "1002")
      (footprint "eagle-import:R0805")
      (fields (field (name "MPN") "RC0805FR-0710KL"))
      (libsource (lib "eagle-import") (part "SMD-RES-10K-1%-1/8W(0805)"))
    )
    (comp (ref "R921")
      (value "1502")
      (footprint "eagle-import:R0805")
      (fields (field (name "MPN") "RC0805FR-0710KL"))
      (libsource (lib "eagle-import") (part "SMD-RES-10K-1%-1/8W(0805)"))
    )
    (comp (ref "R922")
      (value "2702")
      (footprint "eagle-import:R0805")
      (fields (field (name "MPN") "RC0805JR-074K7L"))
      (libsource (lib "eagle-import") (part "SMD-RES-4.7K-5%-1/8W(0805)"))
    )
    (comp (ref "R923")
      (value "2702")
      (footprint "eagle-import:R0805")
      (fields (field (name "MPN") "RC0805JR-074K7L"))
      (libsource (lib "eagle-import") (part "SMD-RES-4.7K-5%-1/8W(0805)"))
    )
    (comp (ref "R924")
      (value "1002")
      (footprint "eagle-import:R0805")
      (fields (field (name "MPN") "RC0805FR-0710KL"))
      (libsource (lib "eagle-import") (part "SMD-RES-10K-1%-1/8W(0805)"))
    )
    (comp (ref "R925")
      (value "104")
      (footprint "eagle-import:R0805")
      (fields (field (name "MPN") "RC0805FR-0710KL"))
      (libsource (lib "eagle-import") (part "SMD-RES-10K-1%-1/8W(0805)"))
    )
    (comp (ref "R926")
      (value "4701")
      (footprint "eagle-import:R0805")
      (fields (field (name "MPN") "RC0805JR-074K7L"))
      (libsource (lib "eagle-import") (part "SMD-RES-4.7K-5%-1/8W(0805)"))
    )
    (comp (ref "R927")
      (value "47")
      (footprint "eagle-import:V235_17_1MM")
      (libsource (lib "eagle-import") (part "R-EU_V235/17_1MM"))
    )
    (comp (ref "R928")
      (value "102")
      (footprint "eagle-import:R0805")
      (fields (field (name "MPN") "RC0805JR-071KL"))
      (libsource (lib "eagle-import") (part "SMD-RES-1K-5%-1/8W(0805)"))
    )
    (comp (ref "R929")
      (value "47")
      (footprint "eagle-import:V235_17_1MM")
      (libsource (lib "eagle-import") (part "R-EU_V235/17_1MM"))
    )
    (comp (ref "R930")
      (value "104")
      (footprint "eagle-import:R0805")
      (fields (field (name "MPN") "RC0805FR-0710KL"))
      (libsource (lib "eagle-import") (part "SMD-RES-10K-1%-1/8W(0805)"))
    )
    (comp (ref "R931")
      (value "1502")
      (footprint "eagle-import:R0805")
      (fields (field (name "MPN") "RC0805FR-0710KL"))
      (libsource (lib "eagle-import") (part "SMD-RES-10K-1%-1/8W(0805)"))
    )
    (comp (ref "R932")
      (value "1002")
      (footprint "eagle-import:R0805")
      (fields (field (name "MPN") "RC0805FR-0710KL"))
      (libsource (lib "eagle-import") (part "SMD-RES-10K-1%-1/8W(0805)"))
    )
    (comp (ref "R933")
      (value "2201")
      (footprint "eagle-import:R0805")
      (fields (field (name "MPN") "RC0805JR-072K2L"))
      (libsource (lib "eagle-import") (part "SMD-RES-2.2K-5%-1/8W(0805)"))
    )
    (comp (ref "R934")
      (value "13")
      (footprint "eagle-import:R1206")
      (fields (field (name "MPN") "RC1206JR-0713RL"))
      (libsource (lib "eagle-import") (part "SMD-RES-13R-5%-1/4W(1206)"))
    )
    (comp (ref "R935")
      (value "104.")
      (footprint "eagle-import:R0805")
      (fields (field (name "MPN") "RC0805FR-0710KL"))
      (libsource (lib "eagle-import") (part "SMD-RES-10K-1%-1/8W(0805)"))
    )
    (comp (ref "R936")
      (value "47")
      (footprint "eagle-import:V235_17_1MM")
      (libsource (lib "eagle-import") (part "R-EU_V235/17_1MM"))
    )
    (comp (ref "R937")
      (value "47")
      (footprint "eagle-import:V235_17_1MM")
      (libsource (lib "eagle-import") (part "R-EU_V235/17_1MM"))
    )
    (comp (ref "R938")
      (value "100")
      (footprint "eagle-import:R0805")
      (fields (field (name "MPN") "RC0805JR-072K2L"))
      (libsource (lib "eagle-import") (part "SMD-RES-2.2K-5%-1/8W(0805)"))
    )
    (comp (ref "R939")
      (value "(101)")
      (footprint "eagle-import:R0805")
      (fields (field (name "MPN") "RC0805JR-072K2L"))
      (libsource (lib "eagle-import") (part "SMD-RES-2.2K-5%-1/8W(0805)"))
    )
    (comp (ref "R940")
      (value "2702")
      (footprint "eagle-import:R0805")
      (fields (field (name "MPN") "RC0805FR-0710KL"))
      (libsource (lib "eagle-import") (part "SMD-RES-10K-1%-1/8W(0805)"))
    )
    (comp (ref "R941")
      (value "104")
      (footprint "eagle-import:R0805")
      (fields (field (name "MPN") "RC0805FR-0710KL"))
      (libsource (lib "eagle-import") (part "SMD-RES-10K-1%-1/8W(0805)"))
    )
    (comp (ref "R942")
      (value "(1000)")
      (footprint "eagle-import:R0805")
      (fields (field (name "MPN") "RC0805JR-07100RL"))
      (libsource (lib "eagle-import") (part "SMD-RES-100R-5%-1/8W(0805)"))
    )
    (comp (ref "R943")
      (value "(101)")
      (footprint "eagle-import:R0805")
      (fields (field (name "MPN") "RC0805JR-07100RL"))
      (libsource (lib "eagle-import") (part "SMD-RES-100R-5%-1/8W(0805)"))
    )
    (comp (ref "R944")
      (value "(1002)")
      (footprint "eagle-import:R0805")
      (fields (field (name "MPN") "RC0805FR-0710KL"))
      (libsource (lib "eagle-import") (part "SMD-RES-10K-1%-1/8W(0805)"))
    )
    (comp (ref "R945")
      (value "2702")
      (footprint "eagle-import:R0805")
      (fields (field (name "MPN") "RC0805JR-074K7L"))
      (libsource (lib "eagle-import") (part "SMD-RES-4.7K-5%-1/8W(0805)"))
    )
    (comp (ref "R946")
      (value "(1002)")
      (footprint "eagle-import:R0805")
      (fields (field (name "MPN") "RC0805JR-074K7L"))
      (libsource (lib "eagle-import") (part "SMD-RES-4.7K-5%-1/8W(0805)"))
    )
    (comp (ref "SJ901")
      (value "SJ")
      (footprint "eagle-import:SJ")
      (libsource (lib "eagle-import") (part "SJ"))
    )
    (comp (ref "START901")
      (value "TPSB2.0")
      (footprint "eagle-import:B2.0")
      (libsource (lib "eagle-import") (part "TPSB2.0"))
    )
    (comp (ref "TP185")
      (value "TPSB2.0")
      (footprint "eagle-import:B2.0")
      (libsource (lib "eagle-import") (part "TPSB2.0"))
    )
    (comp (ref "TP186")
      (value "TPSB2.0")
      (footprint "eagle-import:B2.0")
      (libsource (lib "eagle-import") (part "TPSB2.0"))
    )
    (comp (ref "TP187")
      (value "TPSB2.0")
      (footprint "eagle-import:B2.0")
      (libsource (lib "eagle-import") (part "TPSB2.0"))
    )
    (comp (ref "TP188")
      (value "TPSB2.0")
      (footprint "eagle-import:B2.0")
      (libsource (lib "eagle-import") (part "TPSB2.0"))
    )
    (comp (ref "TP189")
      (value "TPSB2.0")
      (footprint "eagle-import:B2.0")
      (libsource (lib "eagle-import") (part "TPSB2.0"))
    )
    (comp (ref "TP190")
      (value "TPSB2.0")
      (footprint "eagle-import:B2.0")
      (libsource (lib "eagle-import") (part "TPSB2.0"))
    )
    (comp (ref "TP191")
      (value "TPSB2.0")
      (footprint "eagle-import:B2.0")
      (libsource (lib "eagle-import") (part "TPSB2.0"))
    )
    (comp (ref "TP192")
      (value "TPSB2.0")
      (footprint "eagle-import:B2.0")
      (libsource (lib "eagle-import") (part "TPSB2.0"))
    )
    (comp (ref "TP193")
      (value "TPSB2.0")
      (footprint "eagle-import:B2.0")
      (libsource (lib "eagle-import") (part "TPSB2.0"))
    )
    (comp (ref "TP194")
      (value "TPSB2.0")
      (footprint "eagle-import:B2.0")
      (libsource (lib "eagle-import") (part "TPSB2.0"))
    )
    (comp (ref "TP195")
      (value "TPSB2.0")
      (footprint "eagle-import:B2.0")
      (libsource (lib "eagle-import") (part "TPSB2.0"))
    )
    (comp (ref "TP196")
      (value "TPSB2.0")
      (footprint "eagle-import:B2.0")
      (libsource (lib "eagle-import") (part "TPSB2.0"))
    )
    (comp (ref "TP197")
      (value "TPSB2.0")
      (footprint "eagle-import:B2.0")
      (libsource (lib "eagle-import") (part "TPSB2.0"))
    )
    (comp (ref "TP198")
      (value "TPSB2.0")
      (footprint "eagle-import:B2.0")
      (libsource (lib "eagle-import") (part "TPSB2.0"))
    )
    (comp (ref "TP199")
      (value "TPSB2.0")
      (footprint "eagle-import:B2.0")
      (libsource (lib "eagle-import") (part "TPSB2.0"))
    )
    (comp (ref "TP200")
      (value "TPSB2.0")
      (footprint "eagle-import:B2.0")
      (libsource (lib "eagle-import") (part "TPSB2.0"))
    )
    (comp (ref "TP201")
      (value "TPSB2.0")
      (footprint "eagle-import:B2.0")
      (libsource (lib "eagle-import") (part "TPSB2.0"))
    )
    (comp (ref "TP202")
      (value "TPSB2.0")
      (footprint "eagle-import:B2.0")
      (libsource (lib "eagle-import") (part "TPSB2.0"))
    )
    (comp (ref "TP203")
      (value "TPSB1,27")
      (footprint "eagle-import:B1,27")
      (libsource (lib "eagle-import") (part "TPSB1,27"))
    )
    (comp (ref "TP204")
      (value "TPSB2.0")
      (footprint "eagle-import:B2.0")
      (libsource (lib "eagle-import") (part "TPSB2.0"))
    )
    (comp (ref "TP205")
      (value "TPSB2.0")
      (footprint "eagle-import:B2.0")
      (libsource (lib "eagle-import") (part "TPSB2.0"))
    )
    (comp (ref "TP206")
      (value "TPSB2.0")
      (footprint "eagle-import:B2.0")
      (libsource (lib "eagle-import") (part "TPSB2.0"))
    )
    (comp (ref "TP207")
      (value "TPSB2.0")
      (footprint "eagle-import:B2.0")
      (libsource (lib "eagle-import") (part "TPSB2.0"))
    )
    (comp (ref "X901")
      (value "CON_BMWV2")
      (footprint "eagle-import:24-PIN_V2")
      (libsource (lib "eagle-import") (part "CON_BMWV2"))
    )
    (comp (ref "X902")
      (value "22-23-2021")
      (footprint "eagle-import:22-23-2021")
      (fields (field (name "MF") "MOLEX"))
      (libsource (lib "eagle-import") (part "22-23-2021"))
    )
    (comp (ref "X903")
      (value "22-23-2051")
      (footprint "eagle-import:22-23-2051")
      (fields (field (name "MF") "MOLEX"))
      (libsource (lib "eagle-import") (part "22-23-2051"))
    )
    (comp (ref "6V401")
      (value "TPSB2.0")
      (footprint "eagle-import:B2.0")
      (libsource (lib "eagle-import") (part "TPSB2.0"))
    )
    (comp (ref "7")
      (value "2081-1132")
      (footprint "eagle-import:12-PIN")
      (libsource (lib "eagle-import") (part "2081-1132"))
    )
    (comp (ref "8")
      (value "2081-1132")
      (footprint "eagle-import:12-PIN")
      (libsource (lib "eagle-import") (part "2081-1132"))
    )
    (comp (ref "10V401")
      (value "TPSB2.0")
      (footprint "eagle-import:B2.0")
      (libsource (lib "eagle-import") (part "TPSB2.0"))
    )
    (comp (ref "C401")
      (value "4.7u")
      (footprint "eagle-import:C0805")
      (fields (field (name "MPN") "CC0805KKX5R8BB475"))
      (libsource (lib "eagle-import") (part "CERAMIC-4.7UF-25V-10%-X5R(0805)"))
    )
    (comp (ref "C402")
      (value "100nF")
      (footprint "eagle-import:C0805")
      (fields (field (name "MPN") "CC0805KRX7R9BB104"))
      (libsource (lib "eagle-import") (part "CERAMIC-100NF-50V-10%-X7R(0805)"))
    )
    (comp (ref "C403")
      (value "100nF,")
      (footprint "eagle-import:C0805")
      (fields (field (name "MPN") "CC0805KRX7R9BB104"))
      (libsource (lib "eagle-import") (part "CERAMIC-100NF-50V-10%-X7R(0805)"))
    )
    (comp (ref "C404")
      (value "100nF,")
      (footprint "eagle-import:C0805")
      (fields (field (name "MPN") "CC0805KRX7R9BB104"))
      (libsource (lib "eagle-import") (part "CERAMIC-100NF-50V-10%-X7R(0805)"))
    )
    (comp (ref "C405")
      (value "100nF.")
      (footprint "eagle-import:C0805")
      (fields (field (name "MPN") "CC0805KRX7R9BB104"))
      (libsource (lib "eagle-import") (part "CERAMIC-100NF-50V-10%-X7R(0805)"))
    )
    (comp (ref "C406")
      (value "100nF.")
      (footprint "eagle-import:C0805")
      (fields (field (name "MPN") "CC0805KRX7R9BB104"))
      (libsource (lib "eagle-import") (part "CERAMIC-100NF-50V-10%-X7R(0805)"))
    )
    (comp (ref "C407")
      (value "100u")
      (footprint "eagle-import:C1206")
      (fields (field (name "MPN") "GRM31CR60J107ME39L"))
      (libsource (lib "eagle-import") (part "CERAMIC-100UF-6.3V-20%-X5R(1206)"))
    )
    (comp (ref "C408")
      (value "100u")
      (footprint "eagle-import:C1206")
      (fields (field (name "MPN") "GRM31CR60J107ME39L"))
      (libsource (lib "eagle-import") (part "CERAMIC-100UF-6.3V-20%-X5R(1206)"))
    )
    (comp (ref "C409")
      (value "2.2nF")
      (footprint "eagle-import:C0805")
      (fields (field (name "MPN") "CC0805KRX7R9BB104"))
      (libsource (lib "eagle-import") (part "CERAMIC-100NF-50V-10%-X7R(0805)"))
    )
    (comp (ref "C410")
      (value "100nF")
      (footprint "eagle-import:C0805")
      (fields (field (name "MPN") "CC0805KRX7R9BB104"))
      (libsource (lib "eagle-import") (part "CERAMIC-100NF-50V-10%-X7R(0805)"))
    )
    (comp (ref "D401")
      (value "SM6T")
      (footprint "eagle-import:DO214AA")
      (libsource (lib "eagle-import") (part "SM6T"))
    )
    (comp (ref "D402")
      (value "1N4007,")
      (footprint "eagle-import:DO-214AC")
      (fields (field (name "MPN") "1N4007"))
      (libsource (lib "eagle-import") (part "DIODE-GEN-PURPOSE-1KV-1A(DO-214AC)"))
    )
    (comp (ref "D403")
      (value "1N4007,")
      (footprint "eagle-import:DO-214AC")
      (fields (field (name "MPN") "1N4007"))
      (libsource (lib "eagle-import") (part "DIODE-GEN-PURPOSE-1KV-1A(DO-214AC)"))
    )
    (comp (ref "D404")
      (value "SM6TDO214AA_BI")
      (footprint "eagle-import:DO214AA_BI")
      (libsource (lib "eagle-import") (part "SM6TDO214AA_BI"))
    )
    (comp (ref "D405")
      (value "1N4007.")
      (footprint "eagle-import:DO-214AC")
      (fields (field (name "MPN") "1N4007"))
      (libsource (lib "eagle-import") (part "DIODE-GEN-PURPOSE-1KV-1A(DO-214AC)"))
    )
    (comp (ref "D406")
      (value "1N4007.")
      (footprint "eagle-import:DO-214AC")
      (fields (field (name "MPN") "1N4007"))
      (libsource (lib "eagle-import") (part "DIODE-GEN-PURPOSE-1KV-1A(DO-214AC)"))
    )
    (comp (ref "D407")
      (value "1N5817")
      (footprint "eagle-import:DO-214AC_SLIM")
      (libsource (lib "eagle-import") (part "DIODE-GEN-PURPOSE-1KV-1A(DO-214AC)DO-214AC/1206"))
    )
    (comp (ref "D408")
      (value "1N5817.")
      (footprint "eagle-import:DO-214AC_SLIM")
      (libsource (lib "eagle-import") (part "DIODE-GEN-PURPOSE-1KV-1A(DO-214AC)DO-214AC/1206"))
    )
    (comp (ref "D409")
      (value "1N5817.")
      (footprint "eagle-import:DO-214AC_SLIM")
      (libsource (lib "eagle-import") (part "DIODE-GEN-PURPOSE-1KV-1A(DO-214AC)DO-214AC/1206"))
    )
    (comp (ref "D410")
      (value "1N5817")
      (footprint "eagle-import:DO-214AC_SLIM")
      (libsource (lib "eagle-import") (part "DIODE-GEN-PURPOSE-1KV-1A(DO-214AC)DO-214AC/1206"))
    )
    (comp (ref "D411")
      (value "1N4007")
      (footprint "eagle-import:DO-214AC")
      (libsource (lib "eagle-import") (part "DIODE-GEN-PURPOSE-1KV-1A(DO-214AC)"))
    )
    (comp (ref "D412")
      (value "1N4007")
      (footprint "eagle-import:DO-214AC")
      (libsource (lib "eagle-import") (part "DIODE-GEN-PURPOSE-1KV-1A(DO-214AC)"))
    )
    (comp (ref "FID401")
      (value "FIDUCIAL")
      (footprint "eagle-import:FIDUCIAL_1MM")
      (libsource (lib "eagle-import") (part "FIDUCIAL"))
    )
    (comp (ref "FID402")
      (value "FIDUCIAL")
      (footprint "eagle-import:FIDUCIAL_1MM")
      (libsource (lib "eagle-import") (part "FIDUCIAL"))
    )
    (comp (ref "FID403")
      (value "FIDUCIAL")
      (footprint "eagle-import:FIDUCIAL_1MM")
      (libsource (lib "eagle-import") (part "FIDUCIAL"))
    )
    (comp (ref "FID404")
      (value "FIDUCIAL")
      (footprint "eagle-import:FIDUCIAL_1MM")
      (libsource (lib "eagle-import") (part "FIDUCIAL"))
    )
    (comp (ref "IC401")
      (value "LM2904")
      (footprint "eagle-import:SO08")
      (libsource (lib "eagle-import") (part "LM358D"))
    )
    (comp (ref "IC402")
      (value "78L06")
      (footprint "eagle-import:SOT89_ROUND")
      (libsource (lib "eagle-import") (part "78LXXSOT89_ROUND"))
    )
    (comp (ref "IC403")
      (value "6V pos")
      (footprint "eagle-import:78LXX")
      (libsource (lib "eagle-import") (part "v-reg_78LXX"))
    )
    (comp (ref "IC404")
      (value "78L10")
      (footprint "eagle-import:SOT89_ROUND")
      (libsource (lib "eagle-import") (part "78LXXSOT89_ROUND"))
    )
    (comp (ref "IC405")
      (value "4028")
      (footprint "eagle-import:SO16")
      (libsource (lib "eagle-import") (part "4028D"))
    )
    (comp (ref "IC406")
      (value "NUP4304SOT457_R")
      (footprint "eagle-import:SOT457R_PHILIPS")
      (libsource (lib "eagle-import") (part "NUP4304SOT457_R"))
    )
    (comp (ref "IC407")
      (value "ULN2004")
      (footprint "eagle-import:SO16")
      (libsource (lib "eagle-import") (part "ULN2004AD"))
    )
    (comp (ref "IC408")
      (value "LM339")
      (footprint "eagle-import:SO14")
      (libsource (lib "eagle-import") (part "LM339D"))
    )
    (comp (ref "IC409")
      (value "317TO202H_NOHOLE")
      (footprint "eagle-import:TO220H_NOHOLE")
      (libsource (lib "eagle-import") (part "317TO202H_NOHOLE"))
    )
    (comp (ref "IC410")
      (value "555")
      (footprint "eagle-import:SO08")
      (libsource (lib "eagle-import") (part "555DNE"))
    )
    (comp (ref "IC411")
      (value "4538")
      (footprint "eagle-import:SO16")
      (libsource (lib "eagle-import") (part "4538D"))
    )
    (comp (ref "JP401")
      (value "JP2EJP2_SMALLPADS")
      (footprint "eagle-import:JP2_SMALLPADS")
      (libsource (lib "eagle-import") (part "JP2EJP2_SMALLPADS"))
    )
    (comp (ref "JP402")
      (value "JP2EJP2_SMALLPADS")
      (footprint "eagle-import:JP2_SMALLPADS")
      (libsource (lib "eagle-import") (part "JP2EJP2_SMALLPADS"))
    )
    (comp (ref "JP403")
      (value "JP2EJP2_SMALLPADS")
      (footprint "eagle-import:JP2_SMALLPADS")
      (libsource (lib "eagle-import") (part "JP2EJP2_SMALLPADS"))
    )
    (comp (ref "JP404")
      (value "JP2EJP2_SMALLPADS")
      (footprint "eagle-import:JP2_SMALLPADS")
      (libsource (lib "eagle-import") (part "JP2EJP2_SMALLPADS"))
    )
    (comp (ref "JP405")
      (value "JP2E_ORIG")
      (footprint "eagle-import:JP2_ORIG_SMALLPADS")
      (libsource (lib "eagle-import") (part "JP2E_ORIG"))
    )
    (comp (ref "LED401")
      (value "LEDLD260")
      (footprint "eagle-import:LD260")
      (libsource (lib "eagle-import") (part "LEDLD260"))
    )
    (comp (ref "LED402")
      (value "LEDLD260")
      (footprint "eagle-import:LD260")
      (libsource (lib "eagle-import") (part "LEDLD260"))
    )
    (comp (ref "LED403")
      (value "LEDLD260")
      (footprint "eagle-import:LD260")
      (libsource (lib "eagle-import") (part "LEDLD260"))
    )
    (comp (ref "LED404")
      (value "LEDLD260")
      (footprint "eagle-import:LD260")
      (libsource (lib "eagle-import") (part "LEDLD260"))
    )
    (comp (ref "LED405")
      (value "LEDLD260")
      (footprint "eagle-import:LD260")
      (libsource (lib "eagle-import") (part "LEDLD260"))
    )
    (comp (ref "LED406")
      (value "LEDLD260")
      (footprint "eagle-import:LD260")
      (libsource (lib "eagle-import") (part "LEDLD260"))
    )
    (comp (ref "Q401")
      (value "BA.")
      (footprint "eagle-import:SOT89")
      (libsource (lib "eagle-import") (part "PNP-TRANSISTOR_SOT89"))
    )
    (comp (ref "Q402")
      (value "BA.")
      (footprint "eagle-import:SOT89")
      (libsource (lib "eagle-import") (part "PNP-TRANSISTOR_SOT89"))
    )
    (comp (ref "Q403")
      (value "MY")
      (footprint "eagle-import:SOT89")
      (libsource (lib "eagle-import") (part "NPN-TRANSISTOR_SOT89"))
    )
    (comp (ref "Q404")
      (value "BA")
      (footprint "eagle-import:SOT89")
      (libsource (lib "eagle-import") (part "PNP-TRANSISTOR_SOT89"))
    )
    (comp (ref "Q405")
      (value "BA")
      (footprint "eagle-import:SOT89")
      (libsource (lib "eagle-import") (part "PNP-TRANSISTOR_SOT89"))
    )
    (comp (ref "Q406")
      (value "J1")
      (footprint "eagle-import:SOT-23")
      (fields (field (name "MPN") "BSS138W-7-F"))
      (libsource (lib "eagle-import") (part "SMD-MOSFET-N-CH-50V-200MA-BSS138W-7-F(SOT-23)"))
    )
    (comp (ref "Q407")
      (value "J1")
      (footprint "eagle-import:SOT-23")
      (fields (field (name "MPN") "BSS138W-7-F"))
      (libsource (lib "eagle-import") (part "SMD-MOSFET-N-CH-50V-200MA-BSS138W-7-F(SOT-23)"))
    )
    (comp (ref "R401")
      (value "102")
      (footprint "eagle-import:R0805")
      (fields (field (name "MPN") "RC0805JR-071KL"))
      (libsource (lib "eagle-import") (part "SMD-RES-1K-5%-1/8W(0805)"))
    )
    (comp (ref "R402")
      (value "13")
      (footprint "eagle-import:R1206")
      (fields (field (name "MPN") "RC1206JR-0713RL"))
      (libsource (lib "eagle-import") (part "SMD-RES-13R-5%-1/4W(1206)"))
    )
    (comp (ref "R403")
      (value "R_user")
      (footprint "eagle-import:R0805")
      (libsource (lib "eagle-import") (part "R-EU_R0805"))
    )
    (comp (ref "R404")
      (value "R_user")
      (footprint "eagle-import:R0805")
      (libsource (lib "eagle-import") (part "R-EU_R0805"))
    )
    (comp (ref "R405")
      (value "4701")
      (footprint "eagle-import:R0805")
      (fields (field (name "MPN") "RC0805JR-074K7L"))
      (libsource (lib "eagle-import") (part "SMD-RES-4.7K-5%-1/8W(0805)"))
    )
    (comp (ref "R406")
      (value "13")
      (footprint "eagle-import:R1206")
      (fields (field (name "MPN") "RC1206JR-0713RL"))
      (libsource (lib "eagle-import") (part "SMD-RES-13R-5%-1/4W(1206)"))
    )
    (comp (ref "R407")
      (value "1002")
      (footprint "eagle-import:R0805")
      (fields (field (name "MPN") "RC0805FR-0710KL"))
      (libsource (lib "eagle-import") (part "SMD-RES-10K-1%-1/8W(0805)"))
    )
    (comp (ref "R408")
      (value "1002")
      (footprint "eagle-import:R0805")
      (fields (field (name "MPN") "RC0805FR-0710KL"))
      (libsource (lib "eagle-import") (part "SMD-RES-10K-1%-1/8W(0805)"))
    )
    (comp (ref "R409")
      (value "104.")
      (footprint "eagle-import:R0805")
      (fields (field (name "MPN") "RC0805FR-0710KL"))
      (libsource (lib "eagle-import") (part "SMD-RES-10K-1%-1/8W(0805)"))
    )
    (comp (ref "R410")
      (value "104.")
      (footprint "eagle-import:R0805")
      (fields (field (name "MPN") "RC0805FR-0710KL"))
      (libsource (lib "eagle-import") (part "SMD-RES-10K-1%-1/8W(0805)"))
    )
    (comp (ref "R411")
      (value "104.")
      (footprint "eagle-import:R0805")
      (fields (field (name "MPN") "RC0805FR-0710KL"))
      (libsource (lib "eagle-import") (part "SMD-RES-10K-1%-1/8W(0805)"))
    )
    (comp (ref "R412")
      (value "102")
      (footprint "eagle-import:R0805")
      (fields (field (name "MPN") "RC0805JR-071KL"))
      (libsource (lib "eagle-import") (part "SMD-RES-1K-5%-1/8W(0805)"))
    )
    (comp (ref "R413")
      (value "102")
      (footprint "eagle-import:R0805")
      (fields (field (name "MPN") "RC0805JR-071KL"))
      (libsource (lib "eagle-import") (part "SMD-RES-1K-5%-1/8W(0805)"))
    )
    (comp (ref "R414")
      (value "102")
      (footprint "eagle-import:R0805")
      (fields (field (name "MPN") "RC0805JR-071KL"))
      (libsource (lib "eagle-import") (part "SMD-RES-1K-5%-1/8W(0805)"))
    )
    (comp (ref "R415")
      (value "100")
      (footprint "eagle-import:R0805")
      (fields (field (name "MPN") "RC0805JR-07220RL"))
      (libsource (lib "eagle-import") (part "SMD-RES-220R-5%-1/8W(0805)"))
    )
    (comp (ref "R416")
      (value "4701")
      (footprint "eagle-import:R0805")
      (fields (field (name "MPN") "RC0805JR-074K7L"))
      (libsource (lib "eagle-import") (part "SMD-RES-4.7K-5%-1/8W(0805)"))
    )
    (comp (ref "R417")
      (value "2702")
      (footprint "eagle-import:R0805")
      (fields (field (name "MPN") "RC0805JR-074K7L"))
      (libsource (lib "eagle-import") (part "SMD-RES-4.7K-5%-1/8W(0805)"))
    )
    (comp (ref "R418")
      (value "13")
      (footprint "eagle-import:R1206")
      (fields (field (name "MPN") "RC1206JR-0713RL"))
      (libsource (lib "eagle-import") (part "SMD-RES-13R-5%-1/4W(1206)"))
    )
    (comp (ref "R419")
      (value "2201")
      (footprint "eagle-import:R0805")
      (fields (field (name "MPN") "RC0805JR-072K2L"))
      (libsource (lib "eagle-import") (part "SMD-RES-2.2K-5%-1/8W(0805)"))
    )
    (comp (ref "R420")
      (value "1002")
      (footprint "eagle-import:R0805")
      (fields (field (name "MPN") "RC0805FR-0710KL"))
      (libsource (lib "eagle-import") (part "SMD-RES-10K-1%-1/8W(0805)"))
    )
    (comp (ref "R421")
      (value "1502")
      (footprint "eagle-import:R0805")
      (fields (field (name "MPN") "RC0805FR-0710KL"))
      (libsource (lib "eagle-import") (part "SMD-RES-10K-1%-1/8W(0805)"))
    )
    (comp (ref "R422")
      (value "2702")
      (footprint "eagle-import:R0805")
      (fields (field (name "MPN") "RC0805JR-074K7L"))
      (libsource (lib "eagle-import") (part "SMD-RES-4.7K-5%-1/8W(0805)"))
    )
    (comp (ref "R423")
      (value "2702")
      (footprint "eagle-import:R0805")
      (fields (field (name "MPN") "RC0805JR-074K7L"))
      (libsource (lib "eagle-import") (part "SMD-RES-4.7K-5%-1/8W(0805)"))
    )
    (comp (ref "R424")
      (value "1002")
      (footprint "eagle-import:R0805")
      (fields (field (name "MPN") "RC0805FR-0710KL"))
      (libsource (lib "eagle-import") (part "SMD-RES-10K-1%-1/8W(0805)"))
    )
    (comp (ref "R425")
      (value "104")
      (footprint "eagle-import:R0805")
      (fields (field (name "MPN") "RC0805FR-0710KL"))
      (libsource (lib "eagle-import") (part "SMD-RES-10K-1%-1/8W(0805)"))
    )
    (comp (ref "R426")
      (value "4701")
      (footprint "eagle-import:R0805")
      (fields (field (name "MPN") "RC0805JR-074K7L"))
      (libsource (lib "eagle-import") (part "SMD-RES-4.7K-5%-1/8W(0805)"))
    )
    (comp (ref "R427")
      (value "47")
      (footprint "eagle-import:V235_17_1MM")
      (libsource (lib "eagle-import") (part "R-EU_V235/17_1MM"))
    )
    (comp (ref "R428")
      (value "102")
      (footprint "eagle-import:R0805")
      (fields (field (name "MPN") "RC0805JR-071KL"))
      (libsource (lib "eagle-import") (part "SMD-RES-1K-5%-1/8W(0805)"))
    )
    (comp (ref "R429")
      (value "47")
      (footprint "eagle-import:V235_17_1MM")
      (libsource (lib "eagle-import") (part "R-EU_V235/17_1MM"))
    )
    (comp (ref "R430")
      (value "104")
      (footprint "eagle-import:R0805")
      (fields (field (name "MPN") "RC0805FR-0710KL"))
      (libsource (lib "eagle-import") (part "SMD-RES-10K-1%-1/8W(0805)"))
    )
    (comp (ref "R431")
      (value "1502")
      (footprint "eagle-import:R0805")
      (fields (field (name "MPN") "RC0805FR-0710KL"))
      (libsource (lib "eagle-import") (part "SMD-RES-10K-1%-1/8W(0805)"))
    )
    (comp (ref "R432")
      (value "1002")
      (footprint "eagle-import:R0805")
      (fields (field (name "MPN") "RC0805FR-0710KL"))
      (libsource (lib "eagle-import") (part "SMD-RES-10K-1%-1/8W(0805)"))
    )
    (comp (ref "R433")
      (value "2201")
      (footprint "eagle-import:R0805")
      (fields (field (name "MPN") "RC0805JR-072K2L"))
      (libsource (lib "eagle-import") (part "SMD-RES-2.2K-5%-1/8W(0805)"))
    )
    (comp (ref "R434")
      (value "13")
      (footprint "eagle-import:R1206")
      (fields (field (name "MPN") "RC1206JR-0713RL"))
      (libsource (lib "eagle-import") (part "SMD-RES-13R-5%-1/4W(1206)"))
    )
    (comp (ref "R435")
      (value "104")
      (footprint "eagle-import:R0805")
      (fields (field (name "MPN") "RC0805FR-0710KL"))
      (libsource (lib "eagle-import") (part "SMD-RES-10K-1%-1/8W(0805)"))
    )
    (comp (ref "R436")
      (value "47")
      (footprint "eagle-import:V235_17_1MM")
      (libsource (lib "eagle-import") (part "R-EU_V235/17_1MM"))
    )
    (comp (ref "R437")
      (value "47")
      (footprint "eagle-import:V235_17_1MM")
      (libsource (lib "eagle-import") (part "R-EU_V235/17_1MM"))
    )
    (comp (ref "R438")
      (value "100")
      (footprint "eagle-import:R0805")
      (fields (field (name "MPN") "RC0805JR-072K2L"))
      (libsource (lib "eagle-import") (part "SMD-RES-2.2K-5%-1/8W(0805)"))
    )
    (comp (ref "R439")
      (value "(101)")
      (footprint "eagle-import:R0805")
      (fields (field (name "MPN") "RC0805JR-072K2L"))
      (libsource (lib "eagle-import") (part "SMD-RES-2.2K-5%-1/8W(0805)"))
    )
    (comp (ref "R440")
      (value "2702")
      (footprint "eagle-import:R0805")
      (fields (field (name "MPN") "RC0805FR-0710KL"))
      (libsource (lib "eagle-import") (part "SMD-RES-10K-1%-1/8W(0805)"))
    )
    (comp (ref "R441")
      (value "104")
      (footprint "eagle-import:R0805")
      (fields (field (name "MPN") "RC0805FR-0710KL"))
      (libsource (lib "eagle-import") (part "SMD-RES-10K-1%-1/8W(0805)"))
    )
    (comp (ref "R442")
      (value "(1000)")
      (footprint "eagle-import:R0805")
      (fields (field (name "MPN") "RC0805JR-07100RL"))
      (libsource (lib "eagle-import") (part "SMD-RES-100R-5%-1/8W(0805)"))
    )
    (comp (ref "R443")
      (value "(101)")
      (footprint "eagle-import:R0805")
      (fields (field (name "MPN") "RC0805JR-07100RL"))
      (libsource (lib "eagle-import") (part "SMD-RES-100R-5%-1/8W(0805)"))
    )
    (comp (ref "R444")
      (value "(1002)")
      (footprint "eagle-import:R0805")
      (fields (field (name "MPN") "RC0805FR-0710KL"))
      (libsource (lib "eagle-import") (part "SMD-RES-10K-1%-1/8W(0805)"))
    )
    (comp (ref "R445")
      (value "2702")
      (footprint "eagle-import:R0805")
      (fields (field (name "MPN") "RC0805JR-074K7L"))
      (libsource (lib "eagle-import") (part "SMD-RES-4.7K-5%-1/8W(0805)"))
    )
    (comp (ref "R446")
      (value "(1002)")
      (footprint "eagle-import:R0805")
      (fields (field (name "MPN") "RC0805JR-074K7L"))
      (libsource (lib "eagle-import") (part "SMD-RES-4.7K-5%-1/8W(0805)"))
    )
    (comp (ref "SJ401")
      (value "SJ")
      (footprint "eagle-import:SJ")
      (libsource (lib "eagle-import") (part "SJ"))
    )
    (comp (ref "START401")
      (value "TPSB2.0")
      (footprint "eagle-import:B2.0")
      (libsource (lib "eagle-import") (part "TPSB2.0"))
    )
    (comp (ref "TP70")
      (value "TPSB2.0")
      (footprint "eagle-import:B2.0")
      (libsource (lib "eagle-import") (part "TPSB2.0"))
    )
    (comp (ref "TP71")
      (value "TPSB2.0")
      (footprint "eagle-import:B2.0")
      (libsource (lib "eagle-import") (part "TPSB2.0"))
    )
    (comp (ref "TP72")
      (value "TPSB2.0")
      (footprint "eagle-import:B2.0")
      (libsource (lib "eagle-import") (part "TPSB2.0"))
    )
    (comp (ref "TP73")
      (value "TPSB2.0")
      (footprint "eagle-import:B2.0")
      (libsource (lib "eagle-import") (part "TPSB2.0"))
    )
    (comp (ref "TP74")
      (value "TPSB2.0")
      (footprint "eagle-import:B2.0")
      (libsource (lib "eagle-import") (part "TPSB2.0"))
    )
    (comp (ref "TP75")
      (value "TPSB2.0")
      (footprint "eagle-import:B2.0")
      (libsource (lib "eagle-import") (part "TPSB2.0"))
    )
    (comp (ref "TP76")
      (value "TPSB2.0")
      (footprint "eagle-import:B2.0")
      (libsource (lib "eagle-import") (part "TPSB2.0"))
    )
    (comp (ref "TP77")
      (value "TPSB2.0")
      (footprint "eagle-import:B2.0")
      (libsource (lib "eagle-import") (part "TPSB2.0"))
    )
    (comp (ref "TP78")
      (value "TPSB2.0")
      (footprint "eagle-import:B2.0")
      (libsource (lib "eagle-import") (part "TPSB2.0"))
    )
    (comp (ref "TP79")
      (value "TPSB2.0")
      (footprint "eagle-import:B2.0")
      (libsource (lib "eagle-import") (part "TPSB2.0"))
    )
    (comp (ref "TP80")
      (value "TPSB2.0")
      (footprint "eagle-import:B2.0")
      (libsource (lib "eagle-import") (part "TPSB2.0"))
    )
    (comp (ref "TP81")
      (value "TPSB2.0")
      (footprint "eagle-import:B2.0")
      (libsource (lib "eagle-import") (part "TPSB2.0"))
    )
    (comp (ref "TP82")
      (value "TPSB2.0")
      (footprint "eagle-import:B2.0")
      (libsource (lib "eagle-import") (part "TPSB2.0"))
    )
    (comp (ref "TP83")
      (value "TPSB2.0")
      (footprint "eagle-import:B2.0")
      (libsource (lib "eagle-import") (part "TPSB2.0"))
    )
    (comp (ref "TP84")
      (value "TPSB2.0")
      (footprint "eagle-import:B2.0")
      (libsource (lib "eagle-import") (part "TPSB2.0"))
    )
    (comp (ref "TP85")
      (value "TPSB2.0")
      (footprint "eagle-import:B2.0")
      (libsource (lib "eagle-import") (part "TPSB2.0"))
    )
    (comp (ref "TP86")
      (value "TPSB2.0")
      (footprint "eagle-import:B2.0")
      (libsource (lib "eagle-import") (part "TPSB2.0"))
    )
    (comp (ref "TP87")
      (value "TPSB2.0")
      (footprint "eagle-import:B2.0")
      (libsource (lib "eagle-import") (part "TPSB2.0"))
    )
    (comp (ref "TP88")
      (value "TPSB1,27")
      (footprint "eagle-import:B1,27")
      (libsource (lib "eagle-import") (part "TPSB1,27"))
    )
    (comp (ref "TP89")
      (value "TPSB2.0")
      (footprint "eagle-import:B2.0")
      (libsource (lib "eagle-import") (part "TPSB2.0"))
    )
    (comp (ref "TP90")
      (value "TPSB2.0")
      (footprint "eagle-import:B2.0")
      (libsource (lib "eagle-import") (part "TPSB2.0"))
    )
    (comp (ref "TP91")
      (value "TPSB2.0")
      (footprint "eagle-import:B2.0")
      (libsource (lib "eagle-import") (part "TPSB2.0"))
    )
    (comp (ref "TP92")
      (value "TPSB2.0")
      (footprint "eagle-import:B2.0")
      (libsource (lib "eagle-import") (part "TPSB2.0"))
    )
    (comp (ref "X401")
      (value "CON_BMWV2")
      (footprint "eagle-import:24-PIN_V2")
      (libsource (lib "eagle-import") (part "CON_BMWV2"))
    )
    (comp (ref "X402")
      (value "22-23-2021")
      (footprint "eagle-import:22-23-2021")
      (fields (field (name "MF") "MOLEX"))
      (libsource (lib "eagle-import") (part "22-23-2021"))
    )
    (comp (ref "X403")
      (value "22-23-2051")
      (footprint "eagle-import:22-23-2051")
      (fields (field (name "MF") "MOLEX"))
      (libsource (lib "eagle-import") (part "22-23-2051"))
    )
    (comp (ref "1")
      (value "2081-1132")
      (footprint "eagle-import:12-PIN")
      (libsource (lib "eagle-import") (part "2081-1132"))
    )
    (comp (ref "2")
      (value "2081-1132")
      (footprint "eagle-import:12-PIN")
      (libsource (lib "eagle-import") (part "2081-1132"))
    )
    (comp (ref "6V")
      (value "TPSB2.0")
      (footprint "eagle-import:B2.0")
      (libsource (lib "eagle-import") (part "TPSB2.0"))
    )
    (comp (ref "10V")
      (value "TPSB2.0")
      (footprint "eagle-import:B2.0")
      (libsource (lib "eagle-import") (part "TPSB2.0"))
    )
    (comp (ref "C101")
      (value "4.7u")
      (footprint "eagle-import:C0805")
      (fields (field (name "MPN") "CC0805KKX5R8BB475"))
      (libsource (lib "eagle-import") (part "CERAMIC-4.7UF-25V-10%-X5R(0805)"))
    )
    (comp (ref "C102")
      (value "100nF")
      (footprint "eagle-import:C0805")
      (fields (field (name "MPN") "CC0805KRX7R9BB104"))
      (libsource (lib "eagle-import") (part "CERAMIC-100NF-50V-10%-X7R(0805)"))
    )
    (comp (ref "C103")
      (value "100nF,")
      (footprint "eagle-import:C0805")
      (fields (field (name "MPN") "CC0805KRX7R9BB104"))
      (libsource (lib "eagle-import") (part "CERAMIC-100NF-50V-10%-X7R(0805)"))
    )
    (comp (ref "C104")
      (value "100nF,")
      (footprint "eagle-import:C0805")
      (fields (field (name "MPN") "CC0805KRX7R9BB104"))
      (libsource (lib "eagle-import") (part "CERAMIC-100NF-50V-10%-X7R(0805)"))
    )
    (comp (ref "C105")
      (value "100nF.")
      (footprint "eagle-import:C0805")
      (fields (field (name "MPN") "CC0805KRX7R9BB104"))
      (libsource (lib "eagle-import") (part "CERAMIC-100NF-50V-10%-X7R(0805)"))
    )
    (comp (ref "C106")
      (value "100nF.")
      (footprint "eagle-import:C0805")
      (fields (field (name "MPN") "CC0805KRX7R9BB104"))
      (libsource (lib "eagle-import") (part "CERAMIC-100NF-50V-10%-X7R(0805)"))
    )
    (comp (ref "C107")
      (value "100u")
      (footprint "eagle-import:C1206")
      (fields (field (name "MPN") "GRM31CR60J107ME39L"))
      (libsource (lib "eagle-import") (part "CERAMIC-100UF-6.3V-20%-X5R(1206)"))
    )
    (comp (ref "C108")
      (value "100u")
      (footprint "eagle-import:C1206")
      (fields (field (name "MPN") "GRM31CR60J107ME39L"))
      (libsource (lib "eagle-import") (part "CERAMIC-100UF-6.3V-20%-X5R(1206)"))
    )
    (comp (ref "C109")
      (value "2.2nF")
      (footprint "eagle-import:C0805")
      (fields (field (name "MPN") "CC0805KRX7R9BB104"))
      (libsource (lib "eagle-import") (part "CERAMIC-100NF-50V-10%-X7R(0805)"))
    )
    (comp (ref "C110")
      (value "100nF")
      (footprint "eagle-import:C0805")
      (fields (field (name "MPN") "CC0805KRX7R9BB104"))
      (libsource (lib "eagle-import") (part "CERAMIC-100NF-50V-10%-X7R(0805)"))
    )
    (comp (ref "D101")
      (value "SM6T")
      (footprint "eagle-import:DO214AA")
      (libsource (lib "eagle-import") (part "SM6T"))
    )
    (comp (ref "D102")
      (value "1N4007,")
      (footprint "eagle-import:DO-214AC")
      (fields (field (name "MPN") "1N4007"))
      (libsource (lib "eagle-import") (part "DIODE-GEN-PURPOSE-1KV-1A(DO-214AC)"))
    )
    (comp (ref "D103")
      (value "1N4007,")
      (footprint "eagle-import:DO-214AC")
      (fields (field (name "MPN") "1N4007"))
      (libsource (lib "eagle-import") (part "DIODE-GEN-PURPOSE-1KV-1A(DO-214AC)"))
    )
    (comp (ref "D104")
      (value "SM6TDO214AA_BI")
      (footprint "eagle-import:DO214AA_BI")
      (libsource (lib "eagle-import") (part "SM6TDO214AA_BI"))
    )
    (comp (ref "D105")
      (value "1N4007.")
      (footprint "eagle-import:DO-214AC")
      (fields (field (name "MPN") "1N4007"))
      (libsource (lib "eagle-import") (part "DIODE-GEN-PURPOSE-1KV-1A(DO-214AC)"))
    )
    (comp (ref "D106")
      (value "1N4007.")
      (footprint "eagle-import:DO-214AC")
      (fields (field (name "MPN") "1N4007"))
      (libsource (lib "eagle-import") (part "DIODE-GEN-PURPOSE-1KV-1A(DO-214AC)"))
    )
    (comp (ref "D107")
      (value "1N5817")
      (footprint "eagle-import:DO-214AC_SLIM")
      (libsource (lib "eagle-import") (part "DIODE-GEN-PURPOSE-1KV-1A(DO-214AC)DO-214AC/1206"))
    )
    (comp (ref "D108")
      (value "1N5817.")
      (footprint "eagle-import:DO-214AC_SLIM")
      (libsource (lib "eagle-import") (part "DIODE-GEN-PURPOSE-1KV-1A(DO-214AC)DO-214AC/1206"))
    )
    (comp (ref "D109")
      (value "1N5817.")
      (footprint "eagle-import:DO-214AC_SLIM")
      (libsource (lib "eagle-import") (part "DIODE-GEN-PURPOSE-1KV-1A(DO-214AC)DO-214AC/1206"))
    )
    (comp (ref "D110")
      (value "1N5817")
      (footprint "eagle-import:DO-214AC_SLIM")
      (libsource (lib "eagle-import") (part "DIODE-GEN-PURPOSE-1KV-1A(DO-214AC)DO-214AC/1206"))
    )
    (comp (ref "D111")
      (value "1N4007")
      (footprint "eagle-import:DO-214AC")
      (libsource (lib "eagle-import") (part "DIODE-GEN-PURPOSE-1KV-1A(DO-214AC)"))
    )
    (comp (ref "D112")
      (value "1N4007")
      (footprint "eagle-import:DO-214AC")
      (libsource (lib "eagle-import") (part "DIODE-GEN-PURPOSE-1KV-1A(DO-214AC)"))
    )
    (comp (ref "FID1")
      (value "FIDUCIAL")
      (footprint "eagle-import:FIDUCIAL_1MM")
      (libsource (lib "eagle-import") (part "FIDUCIAL"))
    )
    (comp (ref "FID2")
      (value "FIDUCIAL")
      (footprint "eagle-import:FIDUCIAL_1MM")
      (libsource (lib "eagle-import") (part "FIDUCIAL"))
    )
    (comp (ref "FID101")
      (value "FIDUCIAL")
      (footprint "eagle-import:FIDUCIAL_1MM")
      (libsource (lib "eagle-import") (part "FIDUCIAL"))
    )
    (comp (ref "FID102")
      (value "FIDUCIAL")
      (footprint "eagle-import:FIDUCIAL_1MM")
      (libsource (lib "eagle-import") (part "FIDUCIAL"))
    )
    (comp (ref "FID103")
      (value "FIDUCIAL")
      (footprint "eagle-import:FIDUCIAL_1MM")
      (libsource (lib "eagle-import") (part "FIDUCIAL"))
    )
    (comp (ref "FID104")
      (value "FIDUCIAL")
      (footprint "eagle-import:FIDUCIAL_1MM")
      (libsource (lib "eagle-import") (part "FIDUCIAL"))
    )
    (comp (ref "FID105")
      (value "FIDUCIAL")
      (footprint "eagle-import:FIDUCIAL_1MM")
      (libsource (lib "eagle-import") (part "FIDUCIAL"))
    )
    (comp (ref "FID108")
      (value "FIDUCIAL")
      (footprint "eagle-import:FIDUCIAL_1MM")
      (libsource (lib "eagle-import") (part "FIDUCIAL"))
    )
    (comp (ref "IC101")
      (value "LM2904")
      (footprint "eagle-import:SO08")
      (libsource (lib "eagle-import") (part "LM358D"))
    )
    (comp (ref "IC102")
      (value "78L06")
      (footprint "eagle-import:SOT89_ROUND")
      (libsource (lib "eagle-import") (part "78LXXSOT89_ROUND"))
    )
    (comp (ref "IC103")
      (value "6V pos")
      (footprint "eagle-import:78LXX")
      (libsource (lib "eagle-import") (part "v-reg_78LXX"))
    )
    (comp (ref "IC104")
      (value "78L10")
      (footprint "eagle-import:SOT89_ROUND")
      (libsource (lib "eagle-import") (part "78LXXSOT89_ROUND"))
    )
    (comp (ref "IC105")
      (value "4028")
      (footprint "eagle-import:SO16")
      (libsource (lib "eagle-import") (part "4028D"))
    )
    (comp (ref "IC106")
      (value "NUP4304SOT457_R")
      (footprint "eagle-import:SOT457R_PHILIPS")
      (libsource (lib "eagle-import") (part "NUP4304SOT457_R"))
    )
    (comp (ref "IC107")
      (value "ULN2004")
      (footprint "eagle-import:SO16")
      (libsource (lib "eagle-import") (part "ULN2004AD"))
    )
    (comp (ref "IC108")
      (value "LM339")
      (footprint "eagle-import:SO14")
      (libsource (lib "eagle-import") (part "LM339D"))
    )
    (comp (ref "IC109")
      (value "317TO202H_NOHOLE")
      (footprint "eagle-import:TO220H_NOHOLE")
      (libsource (lib "eagle-import") (part "317TO202H_NOHOLE"))
    )
    (comp (ref "IC110")
      (value "555")
      (footprint "eagle-import:SO08")
      (libsource (lib "eagle-import") (part "555DNE"))
    )
    (comp (ref "IC111")
      (value "4538")
      (footprint "eagle-import:SO16")
      (libsource (lib "eagle-import") (part "4538D"))
    )
    (comp (ref "JP101")
      (value "JP2EJP2_SMALLPADS")
      (footprint "eagle-import:JP2_SMALLPADS")
      (libsource (lib "eagle-import") (part "JP2EJP2_SMALLPADS"))
    )
    (comp (ref "JP102")
      (value "JP2EJP2_SMALLPADS")
      (footprint "eagle-import:JP2_SMALLPADS")
      (libsource (lib "eagle-import") (part "JP2EJP2_SMALLPADS"))
    )
    (comp (ref "JP103")
      (value "JP2EJP2_SMALLPADS")
      (footprint "eagle-import:JP2_SMALLPADS")
      (libsource (lib "eagle-import") (part "JP2EJP2_SMALLPADS"))
    )
    (comp (ref "JP104")
      (value "JP2EJP2_SMALLPADS")
      (footprint "eagle-import:JP2_SMALLPADS")
      (libsource (lib "eagle-import") (part "JP2EJP2_SMALLPADS"))
    )
    (comp (ref "JP105")
      (value "JP2E_ORIG")
      (footprint "eagle-import:JP2_ORIG_SMALLPADS")
      (libsource (lib "eagle-import") (part "JP2E_ORIG"))
    )
    (comp (ref "LED101")
      (value "LEDLD260")
      (footprint "eagle-import:LD260")
      (libsource (lib "eagle-import") (part "LEDLD260"))
    )
    (comp (ref "LED102")
      (value "LEDLD260")
      (footprint "eagle-import:LD260")
      (libsource (lib "eagle-import") (part "LEDLD260"))
    )
    (comp (ref "LED103")
      (value "LEDLD260")
      (footprint "eagle-import:LD260")
      (libsource (lib "eagle-import") (part "LEDLD260"))
    )
    (comp (ref "LED104")
      (value "LEDLD260")
      (footprint "eagle-import:LD260")
      (libsource (lib "eagle-import") (part "LEDLD260"))
    )
    (comp (ref "LED105")
      (value "LEDLD260")
      (footprint "eagle-import:LD260")
      (libsource (lib "eagle-import") (part "LEDLD260"))
    )
    (comp (ref "LED106")
      (value "LEDLD260")
      (footprint "eagle-import:LD260")
      (libsource (lib "eagle-import") (part "LEDLD260"))
    )
    (comp (ref "Q101")
      (value "BA.")
      (footprint "eagle-import:SOT89")
      (libsource (lib "eagle-import") (part "PNP-TRANSISTOR_SOT89"))
    )
    (comp (ref "Q102")
      (value "BA.")
      (footprint "eagle-import:SOT89")
      (libsource (lib "eagle-import") (part "PNP-TRANSISTOR_SOT89"))
    )
    (comp (ref "Q103")
      (value "MY")
      (footprint "eagle-import:SOT89")
      (libsource (lib "eagle-import") (part "NPN-TRANSISTOR_SOT89"))
    )
    (comp (ref "Q104")
      (value "BA")
      (footprint "eagle-import:SOT89")
      (libsource (lib "eagle-import") (part "PNP-TRANSISTOR_SOT89"))
    )
    (comp (ref "Q105")
      (value "BA")
      (footprint "eagle-import:SOT89")
      (libsource (lib "eagle-import") (part "PNP-TRANSISTOR_SOT89"))
    )
    (comp (ref "Q106")
      (value "J1")
      (footprint "eagle-import:SOT-23")
      (fields (field (name "MPN") "BSS138W-7-F"))
      (libsource (lib "eagle-import") (part "SMD-MOSFET-N-CH-50V-200MA-BSS138W-7-F(SOT-23)"))
    )
    (comp (ref "Q107")
      (value "J1")
      (footprint "eagle-import:SOT-23")
      (fields (field (name "MPN") "BSS138W-7-F"))
      (libsource (lib "eagle-import") (part "SMD-MOSFET-N-CH-50V-200MA-BSS138W-7-F(SOT-23)"))
    )
    (comp (ref "R101")
      (value "102")
      (footprint "eagle-import:R0805")
      (fields (field (name "MPN") "RC0805JR-071KL"))
      (libsource (lib "eagle-import") (part "SMD-RES-1K-5%-1/8W(0805)"))
    )
    (comp (ref "R102")
      (value "13")
      (footprint "eagle-import:R1206")
      (fields (field (name "MPN") "RC1206JR-0713RL"))
      (libsource (lib "eagle-import") (part "SMD-RES-13R-5%-1/4W(1206)"))
    )
    (comp (ref "R103")
      (value "R_user")
      (footprint "eagle-import:R0805")
      (libsource (lib "eagle-import") (part "R-EU_R0805"))
    )
    (comp (ref "R104")
      (value "R_user")
      (footprint "eagle-import:R0805")
      (libsource (lib "eagle-import") (part "R-EU_R0805"))
    )
    (comp (ref "R105")
      (value "4701")
      (footprint "eagle-import:R0805")
      (fields (field (name "MPN") "RC0805JR-074K7L"))
      (libsource (lib "eagle-import") (part "SMD-RES-4.7K-5%-1/8W(0805)"))
    )
    (comp (ref "R106")
      (value "13")
      (footprint "eagle-import:R1206")
      (fields (field (name "MPN") "RC1206JR-0713RL"))
      (libsource (lib "eagle-import") (part "SMD-RES-13R-5%-1/4W(1206)"))
    )
    (comp (ref "R107")
      (value "1002")
      (footprint "eagle-import:R0805")
      (fields (field (name "MPN") "RC0805FR-0710KL"))
      (libsource (lib "eagle-import") (part "SMD-RES-10K-1%-1/8W(0805)"))
    )
    (comp (ref "R108")
      (value "1002")
      (footprint "eagle-import:R0805")
      (fields (field (name "MPN") "RC0805FR-0710KL"))
      (libsource (lib "eagle-import") (part "SMD-RES-10K-1%-1/8W(0805)"))
    )
    (comp (ref "R109")
      (value "104.")
      (footprint "eagle-import:R0805")
      (fields (field (name "MPN") "RC0805FR-0710KL"))
      (libsource (lib "eagle-import") (part "SMD-RES-10K-1%-1/8W(0805)"))
    )
    (comp (ref "R110")
      (value "104.")
      (footprint "eagle-import:R0805")
      (fields (field (name "MPN") "RC0805FR-0710KL"))
      (libsource (lib "eagle-import") (part "SMD-RES-10K-1%-1/8W(0805)"))
    )
    (comp (ref "R111")
      (value "104.")
      (footprint "eagle-import:R0805")
      (fields (field (name "MPN") "RC0805FR-0710KL"))
      (libsource (lib "eagle-import") (part "SMD-RES-10K-1%-1/8W(0805)"))
    )
    (comp (ref "R112")
      (value "102")
      (footprint "eagle-import:R0805")
      (fields (field (name "MPN") "RC0805JR-071KL"))
      (libsource (lib "eagle-import") (part "SMD-RES-1K-5%-1/8W(0805)"))
    )
    (comp (ref "R113")
      (value "102")
      (footprint "eagle-import:R0805")
      (fields (field (name "MPN") "RC0805JR-071KL"))
      (libsource (lib "eagle-import") (part "SMD-RES-1K-5%-1/8W(0805)"))
    )
    (comp (ref "R114")
      (value "102")
      (footprint "eagle-import:R0805")
      (fields (field (name "MPN") "RC0805JR-071KL"))
      (libsource (lib "eagle-import") (part "SMD-RES-1K-5%-1/8W(0805)"))
    )
    (comp (ref "R115")
      (value "100")
      (footprint "eagle-import:R0805")
      (fields (field (name "MPN") "RC0805JR-07220RL"))
      (libsource (lib "eagle-import") (part "SMD-RES-220R-5%-1/8W(0805)"))
    )
    (comp (ref "R116")
      (value "4701")
      (footprint "eagle-import:R0805")
      (fields (field (name "MPN") "RC0805JR-074K7L"))
      (libsource (lib "eagle-import") (part "SMD-RES-4.7K-5%-1/8W(0805)"))
    )
    (comp (ref "R117")
      (value "2702")
      (footprint "eagle-import:R0805")
      (fields (field (name "MPN") "RC0805JR-074K7L"))
      (libsource (lib "eagle-import") (part "SMD-RES-4.7K-5%-1/8W(0805)"))
    )
    (comp (ref "R118")
      (value "13")
      (footprint "eagle-import:R1206")
      (fields (field (name "MPN") "RC1206JR-0713RL"))
      (libsource (lib "eagle-import") (part "SMD-RES-13R-5%-1/4W(1206)"))
    )
    (comp (ref "R119")
      (value "2201")
      (footprint "eagle-import:R0805")
      (fields (field (name "MPN") "RC0805JR-072K2L"))
      (libsource (lib "eagle-import") (part "SMD-RES-2.2K-5%-1/8W(0805)"))
    )
    (comp (ref "R120")
      (value "1002")
      (footprint "eagle-import:R0805")
      (fields (field (name "MPN") "RC0805FR-0710KL"))
      (libsource (lib "eagle-import") (part "SMD-RES-10K-1%-1/8W(0805)"))
    )
    (comp (ref "R121")
      (value "1502")
      (footprint "eagle-import:R0805")
      (fields (field (name "MPN") "RC0805FR-0710KL"))
      (libsource (lib "eagle-import") (part "SMD-RES-10K-1%-1/8W(0805)"))
    )
    (comp (ref "R122")
      (value "2702")
      (footprint "eagle-import:R0805")
      (fields (field (name "MPN") "RC0805JR-074K7L"))
      (libsource (lib "eagle-import") (part "SMD-RES-4.7K-5%-1/8W(0805)"))
    )
    (comp (ref "R123")
      (value "2702")
      (footprint "eagle-import:R0805")
      (fields (field (name "MPN") "RC0805JR-074K7L"))
      (libsource (lib "eagle-import") (part "SMD-RES-4.7K-5%-1/8W(0805)"))
    )
    (comp (ref "R124")
      (value "1002")
      (footprint "eagle-import:R0805")
      (fields (field (name "MPN") "RC0805FR-0710KL"))
      (libsource (lib "eagle-import") (part "SMD-RES-10K-1%-1/8W(0805)"))
    )
    (comp (ref "R125")
      (value "104")
      (footprint "eagle-import:R0805")
      (fields (field (name "MPN") "RC0805FR-0710KL"))
      (libsource (lib "eagle-import") (part "SMD-RES-10K-1%-1/8W(0805)"))
    )
    (comp (ref "R126")
      (value "4701")
      (footprint "eagle-import:R0805")
      (fields (field (name "MPN") "RC0805JR-074K7L"))
      (libsource (lib "eagle-import") (part "SMD-RES-4.7K-5%-1/8W(0805)"))
    )
    (comp (ref "R127")
      (value "47")
      (footprint "eagle-import:V235_17_1MM")
      (libsource (lib "eagle-import") (part "R-EU_V235/17_1MM"))
    )
    (comp (ref "R128")
      (value "102")
      (footprint "eagle-import:R0805")
      (fields (field (name "MPN") "RC0805JR-071KL"))
      (libsource (lib "eagle-import") (part "SMD-RES-1K-5%-1/8W(0805)"))
    )
    (comp (ref "R129")
      (value "47")
      (footprint "eagle-import:V235_17_1MM")
      (libsource (lib "eagle-import") (part "R-EU_V235/17_1MM"))
    )
    (comp (ref "R130")
      (value "104")
      (footprint "eagle-import:R0805")
      (fields (field (name "MPN") "RC0805FR-0710KL"))
      (libsource (lib "eagle-import") (part "SMD-RES-10K-1%-1/8W(0805)"))
    )
    (comp (ref "R131")
      (value "1502")
      (footprint "eagle-import:R0805")
      (fields (field (name "MPN") "RC0805FR-0710KL"))
      (libsource (lib "eagle-import") (part "SMD-RES-10K-1%-1/8W(0805)"))
    )
    (comp (ref "R132")
      (value "1002")
      (footprint "eagle-import:R0805")
      (fields (field (name "MPN") "RC0805FR-0710KL"))
      (libsource (lib "eagle-import") (part "SMD-RES-10K-1%-1/8W(0805)"))
    )
    (comp (ref "R133")
      (value "2201")
      (footprint "eagle-import:R0805")
      (fields (field (name "MPN") "RC0805JR-072K2L"))
      (libsource (lib "eagle-import") (part "SMD-RES-2.2K-5%-1/8W(0805)"))
    )
    (comp (ref "R134")
      (value "13")
      (footprint "eagle-import:R1206")
      (fields (field (name "MPN") "RC1206JR-0713RL"))
      (libsource (lib "eagle-import") (part "SMD-RES-13R-5%-1/4W(1206)"))
    )
    (comp (ref "R135")
      (value "104.")
      (footprint "eagle-import:R0805")
      (fields (field (name "MPN") "RC0805FR-0710KL"))
      (libsource (lib "eagle-import") (part "SMD-RES-10K-1%-1/8W(0805)"))
    )
    (comp (ref "R136")
      (value "47")
      (footprint "eagle-import:V235_17_1MM")
      (libsource (lib "eagle-import") (part "R-EU_V235/17_1MM"))
    )
    (comp (ref "R137")
      (value "47")
      (footprint "eagle-import:V235_17_1MM")
      (libsource (lib "eagle-import") (part "R-EU_V235/17_1MM"))
    )
    (comp (ref "R138")
      (value "100")
      (footprint "eagle-import:R0805")
      (fields (field (name "MPN") "RC0805JR-072K2L"))
      (libsource (lib "eagle-import") (part "SMD-RES-2.2K-5%-1/8W(0805)"))
    )
    (comp (ref "R139")
      (value "(101)")
      (footprint "eagle-import:R0805")
      (fields (field (name "MPN") "RC0805JR-072K2L"))
      (libsource (lib "eagle-import") (part "SMD-RES-2.2K-5%-1/8W(0805)"))
    )
    (comp (ref "R140")
      (value "2702")
      (footprint "eagle-import:R0805")
      (fields (field (name "MPN") "RC0805FR-0710KL"))
      (libsource (lib "eagle-import") (part "SMD-RES-10K-1%-1/8W(0805)"))
    )
    (comp (ref "R141")
      (value "104")
      (footprint "eagle-import:R0805")
      (fields (field (name "MPN") "RC0805FR-0710KL"))
      (libsource (lib "eagle-import") (part "SMD-RES-10K-1%-1/8W(0805)"))
    )
    (comp (ref "R142")
      (value "(1000)")
      (footprint "eagle-import:R0805")
      (fields (field (name "MPN") "RC0805JR-07100RL"))
      (libsource (lib "eagle-import") (part "SMD-RES-100R-5%-1/8W(0805)"))
    )
    (comp (ref "R143")
      (value "(101)")
      (footprint "eagle-import:R0805")
      (fields (field (name "MPN") "RC0805JR-07100RL"))
      (libsource (lib "eagle-import") (part "SMD-RES-100R-5%-1/8W(0805)"))
    )
    (comp (ref "R144")
      (value "(1002)")
      (footprint "eagle-import:R0805")
      (fields (field (name "MPN") "RC0805FR-0710KL"))
      (libsource (lib "eagle-import") (part "SMD-RES-10K-1%-1/8W(0805)"))
    )
    (comp (ref "R145")
      (value "2702")
      (footprint "eagle-import:R0805")
      (fields (field (name "MPN") "RC0805JR-074K7L"))
      (libsource (lib "eagle-import") (part "SMD-RES-4.7K-5%-1/8W(0805)"))
    )
    (comp (ref "R146")
      (value "(1002)")
      (footprint "eagle-import:R0805")
      (fields (field (name "MPN") "RC0805JR-074K7L"))
      (libsource (lib "eagle-import") (part "SMD-RES-4.7K-5%-1/8W(0805)"))
    )
    (comp (ref "SJ101")
      (value "SJ")
      (footprint "eagle-import:SJ")
      (libsource (lib "eagle-import") (part "SJ"))
    )
    (comp (ref "START")
      (value "TPSB2.0")
      (footprint "eagle-import:B2.0")
      (libsource (lib "eagle-import") (part "TPSB2.0"))
    )
    (comp (ref "TP1")
      (value "TPSB2.0")
      (footprint "eagle-import:B2.0")
      (libsource (lib "eagle-import") (part "TPSB2.0"))
    )
    (comp (ref "TP2")
      (value "TPSB2.0")
      (footprint "eagle-import:B2.0")
      (libsource (lib "eagle-import") (part "TPSB2.0"))
    )
    (comp (ref "TP3")
      (value "TPSB2.0")
      (footprint "eagle-import:B2.0")
      (libsource (lib "eagle-import") (part "TPSB2.0"))
    )
    (comp (ref "TP4")
      (value "TPSB2.0")
      (footprint "eagle-import:B2.0")
      (libsource (lib "eagle-import") (part "TPSB2.0"))
    )
    (comp (ref "TP5")
      (value "TPSB2.0")
      (footprint "eagle-import:B2.0")
      (libsource (lib "eagle-import") (part "TPSB2.0"))
    )
    (comp (ref "TP6")
      (value "TPSB2.0")
      (footprint "eagle-import:B2.0")
      (libsource (lib "eagle-import") (part "TPSB2.0"))
    )
    (comp (ref "TP7")
      (value "TPSB2.0")
      (footprint "eagle-import:B2.0")
      (libsource (lib "eagle-import") (part "TPSB2.0"))
    )
    (comp (ref "TP8")
      (value "TPSB2.0")
      (footprint "eagle-import:B2.0")
      (libsource (lib "eagle-import") (part "TPSB2.0"))
    )
    (comp (ref "TP9")
      (value "TPSB2.0")
      (footprint "eagle-import:B2.0")
      (libsource (lib "eagle-import") (part "TPSB2.0"))
    )
    (comp (ref "TP10")
      (value "TPSB2.0")
      (footprint "eagle-import:B2.0")
      (libsource (lib "eagle-import") (part "TPSB2.0"))
    )
    (comp (ref "TP11")
      (value "TPSB2.0")
      (footprint "eagle-import:B2.0")
      (libsource (lib "eagle-import") (part "TPSB2.0"))
    )
    (comp (ref "TP12")
      (value "TPSB2.0")
      (footprint "eagle-import:B2.0")
      (libsource (lib "eagle-import") (part "TPSB2.0"))
    )
    (comp (ref "TP13")
      (value "TPSB2.0")
      (footprint "eagle-import:B2.0")
      (libsource (lib "eagle-import") (part "TPSB2.0"))
    )
    (comp (ref "TP16")
      (value "TPSB2.0")
      (footprint "eagle-import:B2.0")
      (libsource (lib "eagle-import") (part "TPSB2.0"))
    )
    (comp (ref "TP17")
      (value "TPSB2.0")
      (footprint "eagle-import:B2.0")
      (libsource (lib "eagle-import") (part "TPSB2.0"))
    )
    (comp (ref "TP18")
      (value "TPSB2.0")
      (footprint "eagle-import:B2.0")
      (libsource (lib "eagle-import") (part "TPSB2.0"))
    )
    (comp (ref "TP19")
      (value "TPSB2.0")
      (footprint "eagle-import:B2.0")
      (libsource (lib "eagle-import") (part "TPSB2.0"))
    )
    (comp (ref "TP21")
      (value "TPSB2.0")
      (footprint "eagle-import:B2.0")
      (libsource (lib "eagle-import") (part "TPSB2.0"))
    )
    (comp (ref "TP22")
      (value "TPSB2.0")
      (footprint "eagle-import:B2.0")
      (libsource (lib "eagle-import") (part "TPSB2.0"))
    )
    (comp (ref "TP23")
      (value "TPSB2.0")
      (footprint "eagle-import:B2.0")
      (libsource (lib "eagle-import") (part "TPSB2.0"))
    )
    (comp (ref "TP24")
      (value "TPSB1,27")
      (footprint "eagle-import:B1,27")
      (libsource (lib "eagle-import") (part "TPSB1,27"))
    )
    (comp (ref "TP25")
      (value "TPSB2.0")
      (footprint "eagle-import:B2.0")
      (libsource (lib "eagle-import") (part "TPSB2.0"))
    )
    (comp (ref "TP26")
      (value "TPSB2.0")
      (footprint "eagle-import:B2.0")
      (libsource (lib "eagle-import") (part "TPSB2.0"))
    )
    (comp (ref "X101")
      (value "CON_BMWV2")
      (footprint "eagle-import:24-PIN_V2")
      (libsource (lib "eagle-import") (part "CON_BMWV2"))
    )
    (comp (ref "X102")
      (value "22-23-2021")
      (footprint "eagle-import:22-23-2021")
      (fields (field (name "MF") "MOLEX"))
      (libsource (lib "eagle-import") (part "22-23-2021"))
    )
    (comp (ref "X103")
      (value "22-23-2051")
      (footprint "eagle-import:22-23-2051")
      (fields (field (name "MF") "MOLEX"))
      (libsource (lib "eagle-import") (part "22-23-2051"))
    )
    (comp (ref "6V1001")
      (value "TPSB2.0")
      (footprint "eagle-import:B2.0")
      (libsource (lib "eagle-import") (part "TPSB2.0"))
    )
    (comp (ref "10V1001")
      (value "TPSB2.0")
      (footprint "eagle-import:B2.0")
      (libsource (lib "eagle-import") (part "TPSB2.0"))
    )
    (comp (ref "19")
      (value "2081-1132")
      (footprint "eagle-import:12-PIN")
      (libsource (lib "eagle-import") (part "2081-1132"))
    )
    (comp (ref "20")
      (value "2081-1132")
      (footprint "eagle-import:12-PIN")
      (libsource (lib "eagle-import") (part "2081-1132"))
    )
    (comp (ref "C1001")
      (value "4.7u")
      (footprint "eagle-import:C0805")
      (fields (field (name "MPN") "CC0805KKX5R8BB475"))
      (libsource (lib "eagle-import") (part "CERAMIC-4.7UF-25V-10%-X5R(0805)"))
    )
    (comp (ref "C1002")
      (value "100nF")
      (footprint "eagle-import:C0805")
      (fields (field (name "MPN") "CC0805KRX7R9BB104"))
      (libsource (lib "eagle-import") (part "CERAMIC-100NF-50V-10%-X7R(0805)"))
    )
    (comp (ref "C1003")
      (value "100nF,")
      (footprint "eagle-import:C0805")
      (fields (field (name "MPN") "CC0805KRX7R9BB104"))
      (libsource (lib "eagle-import") (part "CERAMIC-100NF-50V-10%-X7R(0805)"))
    )
    (comp (ref "C1004")
      (value "100nF,")
      (footprint "eagle-import:C0805")
      (fields (field (name "MPN") "CC0805KRX7R9BB104"))
      (libsource (lib "eagle-import") (part "CERAMIC-100NF-50V-10%-X7R(0805)"))
    )
    (comp (ref "C1005")
      (value "100nF.")
      (footprint "eagle-import:C0805")
      (fields (field (name "MPN") "CC0805KRX7R9BB104"))
      (libsource (lib "eagle-import") (part "CERAMIC-100NF-50V-10%-X7R(0805)"))
    )
    (comp (ref "C1006")
      (value "100nF.")
      (footprint "eagle-import:C0805")
      (fields (field (name "MPN") "CC0805KRX7R9BB104"))
      (libsource (lib "eagle-import") (part "CERAMIC-100NF-50V-10%-X7R(0805)"))
    )
    (comp (ref "C1007")
      (value "100u")
      (footprint "eagle-import:C1206")
      (fields (field (name "MPN") "GRM31CR60J107ME39L"))
      (libsource (lib "eagle-import") (part "CERAMIC-100UF-6.3V-20%-X5R(1206)"))
    )
    (comp (ref "C1008")
      (value "100u")
      (footprint "eagle-import:C1206")
      (fields (field (name "MPN") "GRM31CR60J107ME39L"))
      (libsource (lib "eagle-import") (part "CERAMIC-100UF-6.3V-20%-X5R(1206)"))
    )
    (comp (ref "C1009")
      (value "2.2nF")
      (footprint "eagle-import:C0805")
      (fields (field (name "MPN") "CC0805KRX7R9BB104"))
      (libsource (lib "eagle-import") (part "CERAMIC-100NF-50V-10%-X7R(0805)"))
    )
    (comp (ref "C1010")
      (value "100nF")
      (footprint "eagle-import:C0805")
      (fields (field (name "MPN") "CC0805KRX7R9BB104"))
      (libsource (lib "eagle-import") (part "CERAMIC-100NF-50V-10%-X7R(0805)"))
    )
    (comp (ref "D1001")
      (value "SM6T")
      (footprint "eagle-import:DO214AA")
      (libsource (lib "eagle-import") (part "SM6T"))
    )
    (comp (ref "D1002")
      (value "1N4007,")
      (footprint "eagle-import:DO-214AC")
      (fields (field (name "MPN") "1N4007"))
      (libsource (lib "eagle-import") (part "DIODE-GEN-PURPOSE-1KV-1A(DO-214AC)"))
    )
    (comp (ref "D1003")
      (value "1N4007,")
      (footprint "eagle-import:DO-214AC")
      (fields (field (name "MPN") "1N4007"))
      (libsource (lib "eagle-import") (part "DIODE-GEN-PURPOSE-1KV-1A(DO-214AC)"))
    )
    (comp (ref "D1004")
      (value "SM6TDO214AA_BI")
      (footprint "eagle-import:DO214AA_BI")
      (libsource (lib "eagle-import") (part "SM6TDO214AA_BI"))
    )
    (comp (ref "D1005")
      (value "1N4007.")
      (footprint "eagle-import:DO-214AC")
      (fields (field (name "MPN") "1N4007"))
      (libsource (lib "eagle-import") (part "DIODE-GEN-PURPOSE-1KV-1A(DO-214AC)"))
    )
    (comp (ref "D1006")
      (value "1N4007.")
      (footprint "eagle-import:DO-214AC")
      (fields (field (name "MPN") "1N4007"))
      (libsource (lib "eagle-import") (part "DIODE-GEN-PURPOSE-1KV-1A(DO-214AC)"))
    )
    (comp (ref "D1007")
      (value "1N5817")
      (footprint "eagle-import:DO-214AC_SLIM")
      (libsource (lib "eagle-import") (part "DIODE-GEN-PURPOSE-1KV-1A(DO-214AC)DO-214AC/1206"))
    )
    (comp (ref "D1008")
      (value "1N5817.")
      (footprint "eagle-import:DO-214AC_SLIM")
      (libsource (lib "eagle-import") (part "DIODE-GEN-PURPOSE-1KV-1A(DO-214AC)DO-214AC/1206"))
    )
    (comp (ref "D1009")
      (value "1N5817.")
      (footprint "eagle-import:DO-214AC_SLIM")
      (libsource (lib "eagle-import") (part "DIODE-GEN-PURPOSE-1KV-1A(DO-214AC)DO-214AC/1206"))
    )
    (comp (ref "D1010")
      (value "1N5817")
      (footprint "eagle-import:DO-214AC_SLIM")
      (libsource (lib "eagle-import") (part "DIODE-GEN-PURPOSE-1KV-1A(DO-214AC)DO-214AC/1206"))
    )
    (comp (ref "D1011")
      (value "1N4007")
      (footprint "eagle-import:DO-214AC")
      (libsource (lib "eagle-import") (part "DIODE-GEN-PURPOSE-1KV-1A(DO-214AC)"))
    )
    (comp (ref "D1012")
      (value "1N4007")
      (footprint "eagle-import:DO-214AC")
      (libsource (lib "eagle-import") (part "DIODE-GEN-PURPOSE-1KV-1A(DO-214AC)"))
    )
    (comp (ref "FID1001")
      (value "FIDUCIAL")
      (footprint "eagle-import:FIDUCIAL_1MM")
      (libsource (lib "eagle-import") (part "FIDUCIAL"))
    )
    (comp (ref "FID1002")
      (value "FIDUCIAL")
      (footprint "eagle-import:FIDUCIAL_1MM")
      (libsource (lib "eagle-import") (part "FIDUCIAL"))
    )
    (comp (ref "FID1003")
      (value "FIDUCIAL")
      (footprint "eagle-import:FIDUCIAL_1MM")
      (libsource (lib "eagle-import") (part "FIDUCIAL"))
    )
    (comp (ref "FID1004")
      (value "FIDUCIAL")
      (footprint "eagle-import:FIDUCIAL_1MM")
      (libsource (lib "eagle-import") (part "FIDUCIAL"))
    )
    (comp (ref "IC1001")
      (value "LM2904")
      (footprint "eagle-import:SO08")
      (libsource (lib "eagle-import") (part "LM358D"))
    )
    (comp (ref "IC1002")
      (value "78L06")
      (footprint "eagle-import:SOT89_ROUND")
      (libsource (lib "eagle-import") (part "78LXXSOT89_ROUND"))
    )
    (comp (ref "IC1003")
      (value "6V pos")
      (footprint "eagle-import:78LXX")
      (libsource (lib "eagle-import") (part "v-reg_78LXX"))
    )
    (comp (ref "IC1004")
      (value "78L10")
      (footprint "eagle-import:SOT89_ROUND")
      (libsource (lib "eagle-import") (part "78LXXSOT89_ROUND"))
    )
    (comp (ref "IC1005")
      (value "4028")
      (footprint "eagle-import:SO16")
      (libsource (lib "eagle-import") (part "4028D"))
    )
    (comp (ref "IC1006")
      (value "NUP4304SOT457_R")
      (footprint "eagle-import:SOT457R_PHILIPS")
      (libsource (lib "eagle-import") (part "NUP4304SOT457_R"))
    )
    (comp (ref "IC1007")
      (value "ULN2004")
      (footprint "eagle-import:SO16")
      (libsource (lib "eagle-import") (part "ULN2004AD"))
    )
    (comp (ref "IC1008")
      (value "LM339")
      (footprint "eagle-import:SO14")
      (libsource (lib "eagle-import") (part "LM339D"))
    )
    (comp (ref "IC1009")
      (value "317TO202H_NOHOLE")
      (footprint "eagle-import:TO220H_NOHOLE")
      (libsource (lib "eagle-import") (part "317TO202H_NOHOLE"))
    )
    (comp (ref "IC1010")
      (value "555")
      (footprint "eagle-import:SO08")
      (libsource (lib "eagle-import") (part "555DNE"))
    )
    (comp (ref "IC1011")
      (value "4538")
      (footprint "eagle-import:SO16")
      (libsource (lib "eagle-import") (part "4538D"))
    )
    (comp (ref "JP1001")
      (value "JP2EJP2_SMALLPADS")
      (footprint "eagle-import:JP2_SMALLPADS")
      (libsource (lib "eagle-import") (part "JP2EJP2_SMALLPADS"))
    )
    (comp (ref "JP1002")
      (value "JP2EJP2_SMALLPADS")
      (footprint "eagle-import:JP2_SMALLPADS")
      (libsource (lib "eagle-import") (part "JP2EJP2_SMALLPADS"))
    )
    (comp (ref "JP1003")
      (value "JP2EJP2_SMALLPADS")
      (footprint "eagle-import:JP2_SMALLPADS")
      (libsource (lib "eagle-import") (part "JP2EJP2_SMALLPADS"))
    )
    (comp (ref "JP1004")
      (value "JP2EJP2_SMALLPADS")
      (footprint "eagle-import:JP2_SMALLPADS")
      (libsource (lib "eagle-import") (part "JP2EJP2_SMALLPADS"))
    )
    (comp (ref "JP1005")
      (value "JP2E_ORIG")
      (footprint "eagle-import:JP2_ORIG_SMALLPADS")
      (libsource (lib "eagle-import") (part "JP2E_ORIG"))
    )
    (comp (ref "LED1001")
      (value "LEDLD260")
      (footprint "eagle-import:LD260")
      (libsource (lib "eagle-import") (part "LEDLD260"))
    )
    (comp (ref "LED1002")
      (value "LEDLD260")
      (footprint "eagle-import:LD260")
      (libsource (lib "eagle-import") (part "LEDLD260"))
    )
    (comp (ref "LED1003")
      (value "LEDLD260")
      (footprint "eagle-import:LD260")
      (libsource (lib "eagle-import") (part "LEDLD260"))
    )
    (comp (ref "LED1004")
      (value "LEDLD260")
      (footprint "eagle-import:LD260")
      (libsource (lib "eagle-import") (part "LEDLD260"))
    )
    (comp (ref "LED1005")
      (value "LEDLD260")
      (footprint "eagle-import:LD260")
      (libsource (lib "eagle-import") (part "LEDLD260"))
    )
    (comp (ref "LED1006")
      (value "LEDLD260")
      (footprint "eagle-import:LD260")
      (libsource (lib "eagle-import") (part "LEDLD260"))
    )
    (comp (ref "Q1001")
      (value "BA.")
      (footprint "eagle-import:SOT89")
      (libsource (lib "eagle-import") (part "PNP-TRANSISTOR_SOT89"))
    )
    (comp (ref "Q1002")
      (value "BA.")
      (footprint "eagle-import:SOT89")
      (libsource (lib "eagle-import") (part "PNP-TRANSISTOR_SOT89"))
    )
    (comp (ref "Q1003")
      (value "MY")
      (footprint "eagle-import:SOT89")
      (libsource (lib "eagle-import") (part "NPN-TRANSISTOR_SOT89"))
    )
    (comp (ref "Q1004")
      (value "BA")
      (footprint "eagle-import:SOT89")
      (libsource (lib "eagle-import") (part "PNP-TRANSISTOR_SOT89"))
    )
    (comp (ref "Q1005")
      (value "BA")
      (footprint "eagle-import:SOT89")
      (libsource (lib "eagle-import") (part "PNP-TRANSISTOR_SOT89"))
    )
    (comp (ref "Q1006")
      (value "J1")
      (footprint "eagle-import:SOT-23")
      (fields (field (name "MPN") "BSS138W-7-F"))
      (libsource (lib "eagle-import") (part "SMD-MOSFET-N-CH-50V-200MA-BSS138W-7-F(SOT-23)"))
    )
    (comp (ref "Q1007")
      (value "J1")
      (footprint "eagle-import:SOT-23")
      (fields (field (name "MPN") "BSS138W-7-F"))
      (libsource (lib "eagle-import") (part "SMD-MOSFET-N-CH-50V-200MA-BSS138W-7-F(SOT-23)"))
    )
    (comp (ref "R1001")
      (value "102")
      (footprint "eagle-import:R0805")
      (fields (field (name "MPN") "RC0805JR-071KL"))
      (libsource (lib "eagle-import") (part "SMD-RES-1K-5%-1/8W(0805)"))
    )
    (comp (ref "R1002")
      (value "13")
      (footprint "eagle-import:R1206")
      (fields (field (name "MPN") "RC1206JR-0713RL"))
      (libsource (lib "eagle-import") (part "SMD-RES-13R-5%-1/4W(1206)"))
    )
    (comp (ref "R1003")
      (value "R_user")
      (footprint "eagle-import:R0805")
      (libsource (lib "eagle-import") (part "R-EU_R0805"))
    )
    (comp (ref "R1004")
      (value "R_user")
      (footprint "eagle-import:R0805")
      (libsource (lib "eagle-import") (part "R-EU_R0805"))
    )
    (comp (ref "R1005")
      (value "4701")
      (footprint "eagle-import:R0805")
      (fields (field (name "MPN") "RC0805JR-074K7L"))
      (libsource (lib "eagle-import") (part "SMD-RES-4.7K-5%-1/8W(0805)"))
    )
    (comp (ref "R1006")
      (value "13")
      (footprint "eagle-import:R1206")
      (fields (field (name "MPN") "RC1206JR-0713RL"))
      (libsource (lib "eagle-import") (part "SMD-RES-13R-5%-1/4W(1206)"))
    )
    (comp (ref "R1007")
      (value "1002")
      (footprint "eagle-import:R0805")
      (fields (field (name "MPN") "RC0805FR-0710KL"))
      (libsource (lib "eagle-import") (part "SMD-RES-10K-1%-1/8W(0805)"))
    )
    (comp (ref "R1008")
      (value "1002")
      (footprint "eagle-import:R0805")
      (fields (field (name "MPN") "RC0805FR-0710KL"))
      (libsource (lib "eagle-import") (part "SMD-RES-10K-1%-1/8W(0805)"))
    )
    (comp (ref "R1009")
      (value "104.")
      (footprint "eagle-import:R0805")
      (fields (field (name "MPN") "RC0805FR-0710KL"))
      (libsource (lib "eagle-import") (part "SMD-RES-10K-1%-1/8W(0805)"))
    )
    (comp (ref "R1010")
      (value "104.")
      (footprint "eagle-import:R0805")
      (fields (field (name "MPN") "RC0805FR-0710KL"))
      (libsource (lib "eagle-import") (part "SMD-RES-10K-1%-1/8W(0805)"))
    )
    (comp (ref "R1011")
      (value "104.")
      (footprint "eagle-import:R0805")
      (fields (field (name "MPN") "RC0805FR-0710KL"))
      (libsource (lib "eagle-import") (part "SMD-RES-10K-1%-1/8W(0805)"))
    )
    (comp (ref "R1012")
      (value "102")
      (footprint "eagle-import:R0805")
      (fields (field (name "MPN") "RC0805JR-071KL"))
      (libsource (lib "eagle-import") (part "SMD-RES-1K-5%-1/8W(0805)"))
    )
    (comp (ref "R1013")
      (value "102")
      (footprint "eagle-import:R0805")
      (fields (field (name "MPN") "RC0805JR-071KL"))
      (libsource (lib "eagle-import") (part "SMD-RES-1K-5%-1/8W(0805)"))
    )
    (comp (ref "R1014")
      (value "102")
      (footprint "eagle-import:R0805")
      (fields (field (name "MPN") "RC0805JR-071KL"))
      (libsource (lib "eagle-import") (part "SMD-RES-1K-5%-1/8W(0805)"))
    )
    (comp (ref "R1015")
      (value "100")
      (footprint "eagle-import:R0805")
      (fields (field (name "MPN") "RC0805JR-07220RL"))
      (libsource (lib "eagle-import") (part "SMD-RES-220R-5%-1/8W(0805)"))
    )
    (comp (ref "R1016")
      (value "4701")
      (footprint "eagle-import:R0805")
      (fields (field (name "MPN") "RC0805JR-074K7L"))
      (libsource (lib "eagle-import") (part "SMD-RES-4.7K-5%-1/8W(0805)"))
    )
    (comp (ref "R1017")
      (value "2702")
      (footprint "eagle-import:R0805")
      (fields (field (name "MPN") "RC0805JR-074K7L"))
      (libsource (lib "eagle-import") (part "SMD-RES-4.7K-5%-1/8W(0805)"))
    )
    (comp (ref "R1018")
      (value "13")
      (footprint "eagle-import:R1206")
      (fields (field (name "MPN") "RC1206JR-0713RL"))
      (libsource (lib "eagle-import") (part "SMD-RES-13R-5%-1/4W(1206)"))
    )
    (comp (ref "R1019")
      (value "2201")
      (footprint "eagle-import:R0805")
      (fields (field (name "MPN") "RC0805JR-072K2L"))
      (libsource (lib "eagle-import") (part "SMD-RES-2.2K-5%-1/8W(0805)"))
    )
    (comp (ref "R1020")
      (value "1002")
      (footprint "eagle-import:R0805")
      (fields (field (name "MPN") "RC0805FR-0710KL"))
      (libsource (lib "eagle-import") (part "SMD-RES-10K-1%-1/8W(0805)"))
    )
    (comp (ref "R1021")
      (value "1502")
      (footprint "eagle-import:R0805")
      (fields (field (name "MPN") "RC0805FR-0710KL"))
      (libsource (lib "eagle-import") (part "SMD-RES-10K-1%-1/8W(0805)"))
    )
    (comp (ref "R1022")
      (value "2702")
      (footprint "eagle-import:R0805")
      (fields (field (name "MPN") "RC0805JR-074K7L"))
      (libsource (lib "eagle-import") (part "SMD-RES-4.7K-5%-1/8W(0805)"))
    )
    (comp (ref "R1023")
      (value "2702")
      (footprint "eagle-import:R0805")
      (fields (field (name "MPN") "RC0805JR-074K7L"))
      (libsource (lib "eagle-import") (part "SMD-RES-4.7K-5%-1/8W(0805)"))
    )
    (comp (ref "R1024")
      (value "1002")
      (footprint "eagle-import:R0805")
      (fields (field (name "MPN") "RC0805FR-0710KL"))
      (libsource (lib "eagle-import") (part "SMD-RES-10K-1%-1/8W(0805)"))
    )
    (comp (ref "R1025")
      (value "104")
      (footprint "eagle-import:R0805")
      (fields (field (name "MPN") "RC0805FR-0710KL"))
      (libsource (lib "eagle-import") (part "SMD-RES-10K-1%-1/8W(0805)"))
    )
    (comp (ref "R1026")
      (value "4701")
      (footprint "eagle-import:R0805")
      (fields (field (name "MPN") "RC0805JR-074K7L"))
      (libsource (lib "eagle-import") (part "SMD-RES-4.7K-5%-1/8W(0805)"))
    )
    (comp (ref "R1027")
      (value "47")
      (footprint "eagle-import:V235_17_1MM")
      (libsource (lib "eagle-import") (part "R-EU_V235/17_1MM"))
    )
    (comp (ref "R1028")
      (value "102")
      (footprint "eagle-import:R0805")
      (fields (field (name "MPN") "RC0805JR-071KL"))
      (libsource (lib "eagle-import") (part "SMD-RES-1K-5%-1/8W(0805)"))
    )
    (comp (ref "R1029")
      (value "47")
      (footprint "eagle-import:V235_17_1MM")
      (libsource (lib "eagle-import") (part "R-EU_V235/17_1MM"))
    )
    (comp (ref "R1030")
      (value "104")
      (footprint "eagle-import:R0805")
      (fields (field (name "MPN") "RC0805FR-0710KL"))
      (libsource (lib "eagle-import") (part "SMD-RES-10K-1%-1/8W(0805)"))
    )
    (comp (ref "R1031")
      (value "1502")
      (footprint "eagle-import:R0805")
      (fields (field (name "MPN") "RC0805FR-0710KL"))
      (libsource (lib "eagle-import") (part "SMD-RES-10K-1%-1/8W(0805)"))
    )
    (comp (ref "R1032")
      (value "1002")
      (footprint "eagle-import:R0805")
      (fields (field (name "MPN") "RC0805FR-0710KL"))
      (libsource (lib "eagle-import") (part "SMD-RES-10K-1%-1/8W(0805)"))
    )
    (comp (ref "R1033")
      (value "2201")
      (footprint "eagle-import:R0805")
      (fields (field (name "MPN") "RC0805JR-072K2L"))
      (libsource (lib "eagle-import") (part "SMD-RES-2.2K-5%-1/8W(0805)"))
    )
    (comp (ref "R1034")
      (value "13")
      (footprint "eagle-import:R1206")
      (fields (field (name "MPN") "RC1206JR-0713RL"))
      (libsource (lib "eagle-import") (part "SMD-RES-13R-5%-1/4W(1206)"))
    )
    (comp (ref "R1035")
      (value "104")
      (footprint "eagle-import:R0805")
      (fields (field (name "MPN") "RC0805FR-0710KL"))
      (libsource (lib "eagle-import") (part "SMD-RES-10K-1%-1/8W(0805)"))
    )
    (comp (ref "R1036")
      (value "47")
      (footprint "eagle-import:V235_17_1MM")
      (libsource (lib "eagle-import") (part "R-EU_V235/17_1MM"))
    )
    (comp (ref "R1037")
      (value "47")
      (footprint "eagle-import:V235_17_1MM")
      (libsource (lib "eagle-import") (part "R-EU_V235/17_1MM"))
    )
    (comp (ref "R1038")
      (value "100")
      (footprint "eagle-import:R0805")
      (fields (field (name "MPN") "RC0805JR-072K2L"))
      (libsource (lib "eagle-import") (part "SMD-RES-2.2K-5%-1/8W(0805)"))
    )
    (comp (ref "R1039")
      (value "(101)")
      (footprint "eagle-import:R0805")
      (fields (field (name "MPN") "RC0805JR-072K2L"))
      (libsource (lib "eagle-import") (part "SMD-RES-2.2K-5%-1/8W(0805)"))
    )
    (comp (ref "R1040")
      (value "2702")
      (footprint "eagle-import:R0805")
      (fields (field (name "MPN") "RC0805FR-0710KL"))
      (libsource (lib "eagle-import") (part "SMD-RES-10K-1%-1/8W(0805)"))
    )
    (comp (ref "R1041")
      (value "104")
      (footprint "eagle-import:R0805")
      (fields (field (name "MPN") "RC0805FR-0710KL"))
      (libsource (lib "eagle-import") (part "SMD-RES-10K-1%-1/8W(0805)"))
    )
    (comp (ref "R1042")
      (value "(1000)")
      (footprint "eagle-import:R0805")
      (fields (field (name "MPN") "RC0805JR-07100RL"))
      (libsource (lib "eagle-import") (part "SMD-RES-100R-5%-1/8W(0805)"))
    )
    (comp (ref "R1043")
      (value "(101)")
      (footprint "eagle-import:R0805")
      (fields (field (name "MPN") "RC0805JR-07100RL"))
      (libsource (lib "eagle-import") (part "SMD-RES-100R-5%-1/8W(0805)"))
    )
    (comp (ref "R1044")
      (value "(1002)")
      (footprint "eagle-import:R0805")
      (fields (field (name "MPN") "RC0805FR-0710KL"))
      (libsource (lib "eagle-import") (part "SMD-RES-10K-1%-1/8W(0805)"))
    )
    (comp (ref "R1045")
      (value "2702")
      (footprint "eagle-import:R0805")
      (fields (field (name "MPN") "RC0805JR-074K7L"))
      (libsource (lib "eagle-import") (part "SMD-RES-4.7K-5%-1/8W(0805)"))
    )
    (comp (ref "R1046")
      (value "(1002)")
      (footprint "eagle-import:R0805")
      (fields (field (name "MPN") "RC0805JR-074K7L"))
      (libsource (lib "eagle-import") (part "SMD-RES-4.7K-5%-1/8W(0805)"))
    )
    (comp (ref "SJ1001")
      (value "SJ")
      (footprint "eagle-import:SJ")
      (libsource (lib "eagle-import") (part "SJ"))
    )
    (comp (ref "START1001")
      (value "TPSB2.0")
      (footprint "eagle-import:B2.0")
      (libsource (lib "eagle-import") (part "TPSB2.0"))
    )
    (comp (ref "TP208")
      (value "TPSB2.0")
      (footprint "eagle-import:B2.0")
      (libsource (lib "eagle-import") (part "TPSB2.0"))
    )
    (comp (ref "TP209")
      (value "TPSB2.0")
      (footprint "eagle-import:B2.0")
      (libsource (lib "eagle-import") (part "TPSB2.0"))
    )
    (comp (ref "TP210")
      (value "TPSB2.0")
      (footprint "eagle-import:B2.0")
      (libsource (lib "eagle-import") (part "TPSB2.0"))
    )
    (comp (ref "TP211")
      (value "TPSB2.0")
      (footprint "eagle-import:B2.0")
      (libsource (lib "eagle-import") (part "TPSB2.0"))
    )
    (comp (ref "TP212")
      (value "TPSB2.0")
      (footprint "eagle-import:B2.0")
      (libsource (lib "eagle-import") (part "TPSB2.0"))
    )
    (comp (ref "TP213")
      (value "TPSB2.0")
      (footprint "eagle-import:B2.0")
      (libsource (lib "eagle-import") (part "TPSB2.0"))
    )
    (comp (ref "TP214")
      (value "TPSB2.0")
      (footprint "eagle-import:B2.0")
      (libsource (lib "eagle-import") (part "TPSB2.0"))
    )
    (comp (ref "TP215")
      (value "TPSB2.0")
      (footprint "eagle-import:B2.0")
      (libsource (lib "eagle-import") (part "TPSB2.0"))
    )
    (comp (ref "TP216")
      (value "TPSB2.0")
      (footprint "eagle-import:B2.0")
      (libsource (lib "eagle-import") (part "TPSB2.0"))
    )
    (comp (ref "TP217")
      (value "TPSB2.0")
      (footprint "eagle-import:B2.0")
      (libsource (lib "eagle-import") (part "TPSB2.0"))
    )
    (comp (ref "TP218")
      (value "TPSB2.0")
      (footprint "eagle-import:B2.0")
      (libsource (lib "eagle-import") (part "TPSB2.0"))
    )
    (comp (ref "TP219")
      (value "TPSB2.0")
      (footprint "eagle-import:B2.0")
      (libsource (lib "eagle-import") (part "TPSB2.0"))
    )
    (comp (ref "TP220")
      (value "TPSB2.0")
      (footprint "eagle-import:B2.0")
      (libsource (lib "eagle-import") (part "TPSB2.0"))
    )
    (comp (ref "TP221")
      (value "TPSB2.0")
      (footprint "eagle-import:B2.0")
      (libsource (lib "eagle-import") (part "TPSB2.0"))
    )
    (comp (ref "TP222")
      (value "TPSB2.0")
      (footprint "eagle-import:B2.0")
      (libsource (lib "eagle-import") (part "TPSB2.0"))
    )
    (comp (ref "TP223")
      (value "TPSB2.0")
      (footprint "eagle-import:B2.0")
      (libsource (lib "eagle-import") (part "TPSB2.0"))
    )
    (comp (ref "TP224")
      (value "TPSB2.0")
      (footprint "eagle-import:B2.0")
      (libsource (lib "eagle-import") (part "TPSB2.0"))
    )
    (comp (ref "TP225")
      (value "TPSB2.0")
      (footprint "eagle-import:B2.0")
      (libsource (lib "eagle-import") (part "TPSB2.0"))
    )
    (comp (ref "TP226")
      (value "TPSB1,27")
      (footprint "eagle-import:B1,27")
      (libsource (lib "eagle-import") (part "TPSB1,27"))
    )
    (comp (ref "TP227")
      (value "TPSB2.0")
      (footprint "eagle-import:B2.0")
      (libsource (lib "eagle-import") (part "TPSB2.0"))
    )
    (comp (ref "TP228")
      (value "TPSB2.0")
      (footprint "eagle-import:B2.0")
      (libsource (lib "eagle-import") (part "TPSB2.0"))
    )
    (comp (ref "TP229")
      (value "TPSB2.0")
      (footprint "eagle-import:B2.0")
      (libsource (lib "eagle-import") (part "TPSB2.0"))
    )
    (comp (ref "TP230")
      (value "TPSB2.0")
      (footprint "eagle-import:B2.0")
      (libsource (lib "eagle-import") (part "TPSB2.0"))
    )
    (comp (ref "X1001")
      (value "CON_BMWV2")
      (footprint "eagle-import:24-PIN_V2")
      (libsource (lib "eagle-import") (part "CON_BMWV2"))
    )
    (comp (ref "X1002")
      (value "22-23-2021")
      (footprint "eagle-import:22-23-2021")
      (fields (field (name "MF") "MOLEX"))
      (libsource (lib "eagle-import") (part "22-23-2021"))
    )
    (comp (ref "X1003")
      (value "22-23-2051")
      (footprint "eagle-import:22-23-2051")
      (fields (field (name "MF") "MOLEX"))
      (libsource (lib "eagle-import") (part "22-23-2051"))
    )
    (comp (ref "6V501")
      (value "TPSB2.0")
      (footprint "eagle-import:B2.0")
      (libsource (lib "eagle-import") (part "TPSB2.0"))
    )
    (comp (ref "9")
      (value "2081-1132")
      (footprint "eagle-import:12-PIN")
      (libsource (lib "eagle-import") (part "2081-1132"))
    )
    (comp (ref "10")
      (value "2081-1132")
      (footprint "eagle-import:12-PIN")
      (libsource (lib "eagle-import") (part "2081-1132"))
    )
    (comp (ref "10V501")
      (value "TPSB2.0")
      (footprint "eagle-import:B2.0")
      (libsource (lib "eagle-import") (part "TPSB2.0"))
    )
    (comp (ref "C501")
      (value "4.7u")
      (footprint "eagle-import:C0805")
      (fields (field (name "MPN") "CC0805KKX5R8BB475"))
      (libsource (lib "eagle-import") (part "CERAMIC-4.7UF-25V-10%-X5R(0805)"))
    )
    (comp (ref "C502")
      (value "100nF")
      (footprint "eagle-import:C0805")
      (fields (field (name "MPN") "CC0805KRX7R9BB104"))
      (libsource (lib "eagle-import") (part "CERAMIC-100NF-50V-10%-X7R(0805)"))
    )
    (comp (ref "C503")
      (value "100nF,")
      (footprint "eagle-import:C0805")
      (fields (field (name "MPN") "CC0805KRX7R9BB104"))
      (libsource (lib "eagle-import") (part "CERAMIC-100NF-50V-10%-X7R(0805)"))
    )
    (comp (ref "C504")
      (value "100nF,")
      (footprint "eagle-import:C0805")
      (fields (field (name "MPN") "CC0805KRX7R9BB104"))
      (libsource (lib "eagle-import") (part "CERAMIC-100NF-50V-10%-X7R(0805)"))
    )
    (comp (ref "C505")
      (value "100nF.")
      (footprint "eagle-import:C0805")
      (fields (field (name "MPN") "CC0805KRX7R9BB104"))
      (libsource (lib "eagle-import") (part "CERAMIC-100NF-50V-10%-X7R(0805)"))
    )
    (comp (ref "C506")
      (value "100nF.")
      (footprint "eagle-import:C0805")
      (fields (field (name "MPN") "CC0805KRX7R9BB104"))
      (libsource (lib "eagle-import") (part "CERAMIC-100NF-50V-10%-X7R(0805)"))
    )
    (comp (ref "C507")
      (value "100u")
      (footprint "eagle-import:C1206")
      (fields (field (name "MPN") "GRM31CR60J107ME39L"))
      (libsource (lib "eagle-import") (part "CERAMIC-100UF-6.3V-20%-X5R(1206)"))
    )
    (comp (ref "C508")
      (value "100u")
      (footprint "eagle-import:C1206")
      (fields (field (name "MPN") "GRM31CR60J107ME39L"))
      (libsource (lib "eagle-import") (part "CERAMIC-100UF-6.3V-20%-X5R(1206)"))
    )
    (comp (ref "C509")
      (value "2.2nF")
      (footprint "eagle-import:C0805")
      (fields (field (name "MPN") "CC0805KRX7R9BB104"))
      (libsource (lib "eagle-import") (part "CERAMIC-100NF-50V-10%-X7R(0805)"))
    )
    (comp (ref "C510")
      (value "100nF")
      (footprint "eagle-import:C0805")
      (fields (field (name "MPN") "CC0805KRX7R9BB104"))
      (libsource (lib "eagle-import") (part "CERAMIC-100NF-50V-10%-X7R(0805)"))
    )
    (comp (ref "D501")
      (value "SM6T")
      (footprint "eagle-import:DO214AA")
      (libsource (lib "eagle-import") (part "SM6T"))
    )
    (comp (ref "D502")
      (value "1N4007,")
      (footprint "eagle-import:DO-214AC")
      (fields (field (name "MPN") "1N4007"))
      (libsource (lib "eagle-import") (part "DIODE-GEN-PURPOSE-1KV-1A(DO-214AC)"))
    )
    (comp (ref "D503")
      (value "1N4007,")
      (footprint "eagle-import:DO-214AC")
      (fields (field (name "MPN") "1N4007"))
      (libsource (lib "eagle-import") (part "DIODE-GEN-PURPOSE-1KV-1A(DO-214AC)"))
    )
    (comp (ref "D504")
      (value "SM6TDO214AA_BI")
      (footprint "eagle-import:DO214AA_BI")
      (libsource (lib "eagle-import") (part "SM6TDO214AA_BI"))
    )
    (comp (ref "D505")
      (value "1N4007.")
      (footprint "eagle-import:DO-214AC")
      (fields (field (name "MPN") "1N4007"))
      (libsource (lib "eagle-import") (part "DIODE-GEN-PURPOSE-1KV-1A(DO-214AC)"))
    )
    (comp (ref "D506")
      (value "1N4007.")
      (footprint "eagle-import:DO-214AC")
      (fields (field (name "MPN") "1N4007"))
      (libsource (lib "eagle-import") (part "DIODE-GEN-PURPOSE-1KV-1A(DO-214AC)"))
    )
    (comp (ref "D507")
      (value "1N5817")
      (footprint "eagle-import:DO-214AC_SLIM")
      (libsource (lib "eagle-import") (part "DIODE-GEN-PURPOSE-1KV-1A(DO-214AC)DO-214AC/1206"))
    )
    (comp (ref "D508")
      (value "1N5817.")
      (footprint "eagle-import:DO-214AC_SLIM")
      (libsource (lib "eagle-import") (part "DIODE-GEN-PURPOSE-1KV-1A(DO-214AC)DO-214AC/1206"))
    )
    (comp (ref "D509")
      (value "1N5817.")
      (footprint "eagle-import:DO-214AC_SLIM")
      (libsource (lib "eagle-import") (part "DIODE-GEN-PURPOSE-1KV-1A(DO-214AC)DO-214AC/1206"))
    )
    (comp (ref "D510")
      (value "1N5817")
      (footprint "eagle-import:DO-214AC_SLIM")
      (libsource (lib "eagle-import") (part "DIODE-GEN-PURPOSE-1KV-1A(DO-214AC)DO-214AC/1206"))
    )
    (comp (ref "D511")
      (value "1N4007")
      (footprint "eagle-import:DO-214AC")
      (libsource (lib "eagle-import") (part "DIODE-GEN-PURPOSE-1KV-1A(DO-214AC)"))
    )
    (comp (ref "D512")
      (value "1N4007")
      (footprint "eagle-import:DO-214AC")
      (libsource (lib "eagle-import") (part "DIODE-GEN-PURPOSE-1KV-1A(DO-214AC)"))
    )
    (comp (ref "FID501")
      (value "FIDUCIAL")
      (footprint "eagle-import:FIDUCIAL_1MM")
      (libsource (lib "eagle-import") (part "FIDUCIAL"))
    )
    (comp (ref "FID502")
      (value "FIDUCIAL")
      (footprint "eagle-import:FIDUCIAL_1MM")
      (libsource (lib "eagle-import") (part "FIDUCIAL"))
    )
    (comp (ref "FID503")
      (value "FIDUCIAL")
      (footprint "eagle-import:FIDUCIAL_1MM")
      (libsource (lib "eagle-import") (part "FIDUCIAL"))
    )
    (comp (ref "FID504")
      (value "FIDUCIAL")
      (footprint "eagle-import:FIDUCIAL_1MM")
      (libsource (lib "eagle-import") (part "FIDUCIAL"))
    )
    (comp (ref "IC501")
      (value "LM2904")
      (footprint "eagle-import:SO08")
      (libsource (lib "eagle-import") (part "LM358D"))
    )
    (comp (ref "IC502")
      (value "78L06")
      (footprint "eagle-import:SOT89_ROUND")
      (libsource (lib "eagle-import") (part "78LXXSOT89_ROUND"))
    )
    (comp (ref "IC503")
      (value "6V pos")
      (footprint "eagle-import:78LXX")
      (libsource (lib "eagle-import") (part "v-reg_78LXX"))
    )
    (comp (ref "IC504")
      (value "78L10")
      (footprint "eagle-import:SOT89_ROUND")
      (libsource (lib "eagle-import") (part "78LXXSOT89_ROUND"))
    )
    (comp (ref "IC505")
      (value "4028")
      (footprint "eagle-import:SO16")
      (libsource (lib "eagle-import") (part "4028D"))
    )
    (comp (ref "IC506")
      (value "NUP4304SOT457_R")
      (footprint "eagle-import:SOT457R_PHILIPS")
      (libsource (lib "eagle-import") (part "NUP4304SOT457_R"))
    )
    (comp (ref "IC507")
      (value "ULN2004")
      (footprint "eagle-import:SO16")
      (libsource (lib "eagle-import") (part "ULN2004AD"))
    )
    (comp (ref "IC508")
      (value "LM339")
      (footprint "eagle-import:SO14")
      (libsource (lib "eagle-import") (part "LM339D"))
    )
    (comp (ref "IC509")
      (value "317TO202H_NOHOLE")
      (footprint "eagle-import:TO220H_NOHOLE")
      (libsource (lib "eagle-import") (part "317TO202H_NOHOLE"))
    )
    (comp (ref "IC510")
      (value "555")
      (footprint "eagle-import:SO08")
      (libsource (lib "eagle-import") (part "555DNE"))
    )
    (comp (ref "IC511")
      (value "4538")
      (footprint "eagle-import:SO16")
      (libsource (lib "eagle-import") (part "4538D"))
    )
    (comp (ref "JP501")
      (value "JP2EJP2_SMALLPADS")
      (footprint "eagle-import:JP2_SMALLPADS")
      (libsource (lib "eagle-import") (part "JP2EJP2_SMALLPADS"))
    )
    (comp (ref "JP502")
      (value "JP2EJP2_SMALLPADS")
      (footprint "eagle-import:JP2_SMALLPADS")
      (libsource (lib "eagle-import") (part "JP2EJP2_SMALLPADS"))
    )
    (comp (ref "JP503")
      (value "JP2EJP2_SMALLPADS")
      (footprint "eagle-import:JP2_SMALLPADS")
      (libsource (lib "eagle-import") (part "JP2EJP2_SMALLPADS"))
    )
    (comp (ref "JP504")
      (value "JP2EJP2_SMALLPADS")
      (footprint "eagle-import:JP2_SMALLPADS")
      (libsource (lib "eagle-import") (part "JP2EJP2_SMALLPADS"))
    )
    (comp (ref "JP505")
      (value "JP2E_ORIG")
      (footprint "eagle-import:JP2_ORIG_SMALLPADS")
      (libsource (lib "eagle-import") (part "JP2E_ORIG"))
    )
    (comp (ref "LED501")
      (value "LEDLD260")
      (footprint "eagle-import:LD260")
      (libsource (lib "eagle-import") (part "LEDLD260"))
    )
    (comp (ref "LED502")
      (value "LEDLD260")
      (footprint "eagle-import:LD260")
      (libsource (lib "eagle-import") (part "LEDLD260"))
    )
    (comp (ref "LED503")
      (value "LEDLD260")
      (footprint "eagle-import:LD260")
      (libsource (lib "eagle-import") (part "LEDLD260"))
    )
    (comp (ref "LED504")
      (value "LEDLD260")
      (footprint "eagle-import:LD260")
      (libsource (lib "eagle-import") (part "LEDLD260"))
    )
    (comp (ref "LED505")
      (value "LEDLD260")
      (footprint "eagle-import:LD260")
      (libsource (lib "eagle-import") (part "LEDLD260"))
    )
    (comp (ref "LED506")
      (value "LEDLD260")
      (footprint "eagle-import:LD260")
      (libsource (lib "eagle-import") (part "LEDLD260"))
    )
    (comp (ref "Q501")
      (value "BA.")
      (footprint "eagle-import:SOT89")
      (libsource (lib "eagle-import") (part "PNP-TRANSISTOR_SOT89"))
    )
    (comp (ref "Q502")
      (value "BA.")
      (footprint "eagle-import:SOT89")
      (libsource (lib "eagle-import") (part "PNP-TRANSISTOR_SOT89"))
    )
    (comp (ref "Q503")
      (value "MY")
      (footprint "eagle-import:SOT89")
      (libsource (lib "eagle-import") (part "NPN-TRANSISTOR_SOT89"))
    )
    (comp (ref "Q504")
      (value "BA")
      (footprint "eagle-import:SOT89")
      (libsource (lib "eagle-import") (part "PNP-TRANSISTOR_SOT89"))
    )
    (comp (ref "Q505")
      (value "BA")
      (footprint "eagle-import:SOT89")
      (libsource (lib "eagle-import") (part "PNP-TRANSISTOR_SOT89"))
    )
    (comp (ref "Q506")
      (value "J1")
      (footprint "eagle-import:SOT-23")
      (fields (field (name "MPN") "BSS138W-7-F"))
      (libsource (lib "eagle-import") (part "SMD-MOSFET-N-CH-50V-200MA-BSS138W-7-F(SOT-23)"))
    )
    (comp (ref "Q507")
      (value "J1")
      (footprint "eagle-import:SOT-23")
      (fields (field (name "MPN") "BSS138W-7-F"))
      (libsource (lib "eagle-import") (part "SMD-MOSFET-N-CH-50V-200MA-BSS138W-7-F(SOT-23)"))
    )
    (comp (ref "R501")
      (value "102")
      (footprint "eagle-import:R0805")
      (fields (field (name "MPN") "RC0805JR-071KL"))
      (libsource (lib "eagle-import") (part "SMD-RES-1K-5%-1/8W(0805)"))
    )
    (comp (ref "R502")
      (value "13")
      (footprint "eagle-import:R1206")
      (fields (field (name "MPN") "RC1206JR-0713RL"))
      (libsource (lib "eagle-import") (part "SMD-RES-13R-5%-1/4W(1206)"))
    )
    (comp (ref "R503")
      (value "R_user")
      (footprint "eagle-import:R0805")
      (libsource (lib "eagle-import") (part "R-EU_R0805"))
    )
    (comp (ref "R504")
      (value "R_user")
      (footprint "eagle-import:R0805")
      (libsource (lib "eagle-import") (part "R-EU_R0805"))
    )
    (comp (ref "R505")
      (value "4701")
      (footprint "eagle-import:R0805")
      (fields (field (name "MPN") "RC0805JR-074K7L"))
      (libsource (lib "eagle-import") (part "SMD-RES-4.7K-5%-1/8W(0805)"))
    )
    (comp (ref "R506")
      (value "13")
      (footprint "eagle-import:R1206")
      (fields (field (name "MPN") "RC1206JR-0713RL"))
      (libsource (lib "eagle-import") (part "SMD-RES-13R-5%-1/4W(1206)"))
    )
    (comp (ref "R507")
      (value "1002")
      (footprint "eagle-import:R0805")
      (fields (field (name "MPN") "RC0805FR-0710KL"))
      (libsource (lib "eagle-import") (part "SMD-RES-10K-1%-1/8W(0805)"))
    )
    (comp (ref "R508")
      (value "1002")
      (footprint "eagle-import:R0805")
      (fields (field (name "MPN") "RC0805FR-0710KL"))
      (libsource (lib "eagle-import") (part "SMD-RES-10K-1%-1/8W(0805)"))
    )
    (comp (ref "R509")
      (value "104.")
      (footprint "eagle-import:R0805")
      (fields (field (name "MPN") "RC0805FR-0710KL"))
      (libsource (lib "eagle-import") (part "SMD-RES-10K-1%-1/8W(0805)"))
    )
    (comp (ref "R510")
      (value "104.")
      (footprint "eagle-import:R0805")
      (fields (field (name "MPN") "RC0805FR-0710KL"))
      (libsource (lib "eagle-import") (part "SMD-RES-10K-1%-1/8W(0805)"))
    )
    (comp (ref "R511")
      (value "104.")
      (footprint "eagle-import:R0805")
      (fields (field (name "MPN") "RC0805FR-0710KL"))
      (libsource (lib "eagle-import") (part "SMD-RES-10K-1%-1/8W(0805)"))
    )
    (comp (ref "R512")
      (value "102")
      (footprint "eagle-import:R0805")
      (fields (field (name "MPN") "RC0805JR-071KL"))
      (libsource (lib "eagle-import") (part "SMD-RES-1K-5%-1/8W(0805)"))
    )
    (comp (ref "R513")
      (value "102")
      (footprint "eagle-import:R0805")
      (fields (field (name "MPN") "RC0805JR-071KL"))
      (libsource (lib "eagle-import") (part "SMD-RES-1K-5%-1/8W(0805)"))
    )
    (comp (ref "R514")
      (value "102")
      (footprint "eagle-import:R0805")
      (fields (field (name "MPN") "RC0805JR-071KL"))
      (libsource (lib "eagle-import") (part "SMD-RES-1K-5%-1/8W(0805)"))
    )
    (comp (ref "R515")
      (value "100")
      (footprint "eagle-import:R0805")
      (fields (field (name "MPN") "RC0805JR-07220RL"))
      (libsource (lib "eagle-import") (part "SMD-RES-220R-5%-1/8W(0805)"))
    )
    (comp (ref "R516")
      (value "4701")
      (footprint "eagle-import:R0805")
      (fields (field (name "MPN") "RC0805JR-074K7L"))
      (libsource (lib "eagle-import") (part "SMD-RES-4.7K-5%-1/8W(0805)"))
    )
    (comp (ref "R517")
      (value "2702")
      (footprint "eagle-import:R0805")
      (fields (field (name "MPN") "RC0805JR-074K7L"))
      (libsource (lib "eagle-import") (part "SMD-RES-4.7K-5%-1/8W(0805)"))
    )
    (comp (ref "R518")
      (value "13")
      (footprint "eagle-import:R1206")
      (fields (field (name "MPN") "RC1206JR-0713RL"))
      (libsource (lib "eagle-import") (part "SMD-RES-13R-5%-1/4W(1206)"))
    )
    (comp (ref "R519")
      (value "2201")
      (footprint "eagle-import:R0805")
      (fields (field (name "MPN") "RC0805JR-072K2L"))
      (libsource (lib "eagle-import") (part "SMD-RES-2.2K-5%-1/8W(0805)"))
    )
    (comp (ref "R520")
      (value "1002")
      (footprint "eagle-import:R0805")
      (fields (field (name "MPN") "RC0805FR-0710KL"))
      (libsource (lib "eagle-import") (part "SMD-RES-10K-1%-1/8W(0805)"))
    )
    (comp (ref "R521")
      (value "1502")
      (footprint "eagle-import:R0805")
      (fields (field (name "MPN") "RC0805FR-0710KL"))
      (libsource (lib "eagle-import") (part "SMD-RES-10K-1%-1/8W(0805)"))
    )
    (comp (ref "R522")
      (value "2702")
      (footprint "eagle-import:R0805")
      (fields (field (name "MPN") "RC0805JR-074K7L"))
      (libsource (lib "eagle-import") (part "SMD-RES-4.7K-5%-1/8W(0805)"))
    )
    (comp (ref "R523")
      (value "2702")
      (footprint "eagle-import:R0805")
      (fields (field (name "MPN") "RC0805JR-074K7L"))
      (libsource (lib "eagle-import") (part "SMD-RES-4.7K-5%-1/8W(0805)"))
    )
    (comp (ref "R524")
      (value "1002")
      (footprint "eagle-import:R0805")
      (fields (field (name "MPN") "RC0805FR-0710KL"))
      (libsource (lib "eagle-import") (part "SMD-RES-10K-1%-1/8W(0805)"))
    )
    (comp (ref "R525")
      (value "104")
      (footprint "eagle-import:R0805")
      (fields (field (name "MPN") "RC0805FR-0710KL"))
      (libsource (lib "eagle-import") (part "SMD-RES-10K-1%-1/8W(0805)"))
    )
    (comp (ref "R526")
      (value "4701")
      (footprint "eagle-import:R0805")
      (fields (field (name "MPN") "RC0805JR-074K7L"))
      (libsource (lib "eagle-import") (part "SMD-RES-4.7K-5%-1/8W(0805)"))
    )
    (comp (ref "R527")
      (value "47")
      (footprint "eagle-import:V235_17_1MM")
      (libsource (lib "eagle-import") (part "R-EU_V235/17_1MM"))
    )
    (comp (ref "R528")
      (value "102")
      (footprint "eagle-import:R0805")
      (fields (field (name "MPN") "RC0805JR-071KL"))
      (libsource (lib "eagle-import") (part "SMD-RES-1K-5%-1/8W(0805)"))
    )
    (comp (ref "R529")
      (value "47")
      (footprint "eagle-import:V235_17_1MM")
      (libsource (lib "eagle-import") (part "R-EU_V235/17_1MM"))
    )
    (comp (ref "R530")
      (value "104")
      (footprint "eagle-import:R0805")
      (fields (field (name "MPN") "RC0805FR-0710KL"))
      (libsource (lib "eagle-import") (part "SMD-RES-10K-1%-1/8W(0805)"))
    )
    (comp (ref "R531")
      (value "1502")
      (footprint "eagle-import:R0805")
      (fields (field (name "MPN") "RC0805FR-0710KL"))
      (libsource (lib "eagle-import") (part "SMD-RES-10K-1%-1/8W(0805)"))
    )
    (comp (ref "R532")
      (value "1002")
      (footprint "eagle-import:R0805")
      (fields (field (name "MPN") "RC0805FR-0710KL"))
      (libsource (lib "eagle-import") (part "SMD-RES-10K-1%-1/8W(0805)"))
    )
    (comp (ref "R533")
      (value "2201")
      (footprint "eagle-import:R0805")
      (fields (field (name "MPN") "RC0805JR-072K2L"))
      (libsource (lib "eagle-import") (part "SMD-RES-2.2K-5%-1/8W(0805)"))
    )
    (comp (ref "R534")
      (value "13")
      (footprint "eagle-import:R1206")
      (fields (field (name "MPN") "RC1206JR-0713RL"))
      (libsource (lib "eagle-import") (part "SMD-RES-13R-5%-1/4W(1206)"))
    )
    (comp (ref "R535")
      (value "104.")
      (footprint "eagle-import:R0805")
      (fields (field (name "MPN") "RC0805FR-0710KL"))
      (libsource (lib "eagle-import") (part "SMD-RES-10K-1%-1/8W(0805)"))
    )
    (comp (ref "R536")
      (value "47")
      (footprint "eagle-import:V235_17_1MM")
      (libsource (lib "eagle-import") (part "R-EU_V235/17_1MM"))
    )
    (comp (ref "R537")
      (value "47")
      (footprint "eagle-import:V235_17_1MM")
      (libsource (lib "eagle-import") (part "R-EU_V235/17_1MM"))
    )
    (comp (ref "R538")
      (value "100")
      (footprint "eagle-import:R0805")
      (fields (field (name "MPN") "RC0805JR-072K2L"))
      (libsource (lib "eagle-import") (part "SMD-RES-2.2K-5%-1/8W(0805)"))
    )
    (comp (ref "R539")
      (value "(101)")
      (footprint "eagle-import:R0805")
      (fields (field (name "MPN") "RC0805JR-072K2L"))
      (libsource (lib "eagle-import") (part "SMD-RES-2.2K-5%-1/8W(0805)"))
    )
    (comp (ref "R540")
      (value "2702")
      (footprint "eagle-import:R0805")
      (fields (field (name "MPN") "RC0805FR-0710KL"))
      (libsource (lib "eagle-import") (part "SMD-RES-10K-1%-1/8W(0805)"))
    )
    (comp (ref "R541")
      (value "104")
      (footprint "eagle-import:R0805")
      (fields (field (name "MPN") "RC0805FR-0710KL"))
      (libsource (lib "eagle-import") (part "SMD-RES-10K-1%-1/8W(0805)"))
    )
    (comp (ref "R542")
      (value "(1000)")
      (footprint "eagle-import:R0805")
      (fields (field (name "MPN") "RC0805JR-07100RL"))
      (libsource (lib "eagle-import") (part "SMD-RES-100R-5%-1/8W(0805)"))
    )
    (comp (ref "R543")
      (value "(101)")
      (footprint "eagle-import:R0805")
      (fields (field (name "MPN") "RC0805JR-07100RL"))
      (libsource (lib "eagle-import") (part "SMD-RES-100R-5%-1/8W(0805)"))
    )
    (comp (ref "R544")
      (value "(1002)")
      (footprint "eagle-import:R0805")
      (fields (field (name "MPN") "RC0805FR-0710KL"))
      (libsource (lib "eagle-import") (part "SMD-RES-10K-1%-1/8W(0805)"))
    )
    (comp (ref "R545")
      (value "2702")
      (footprint "eagle-import:R0805")
      (fields (field (name "MPN") "RC0805JR-074K7L"))
      (libsource (lib "eagle-import") (part "SMD-RES-4.7K-5%-1/8W(0805)"))
    )
    (comp (ref "R546")
      (value "(1002)")
      (footprint "eagle-import:R0805")
      (fields (field (name "MPN") "RC0805JR-074K7L"))
      (libsource (lib "eagle-import") (part "SMD-RES-4.7K-5%-1/8W(0805)"))
    )
    (comp (ref "SJ501")
      (value "SJ")
      (footprint "eagle-import:SJ")
      (libsource (lib "eagle-import") (part "SJ"))
    )
    (comp (ref "START501")
      (value "TPSB2.0")
      (footprint "eagle-import:B2.0")
      (libsource (lib "eagle-import") (part "TPSB2.0"))
    )
    (comp (ref "TP93")
      (value "TPSB2.0")
      (footprint "eagle-import:B2.0")
      (libsource (lib "eagle-import") (part "TPSB2.0"))
    )
    (comp (ref "TP94")
      (value "TPSB2.0")
      (footprint "eagle-import:B2.0")
      (libsource (lib "eagle-import") (part "TPSB2.0"))
    )
    (comp (ref "TP95")
      (value "TPSB2.0")
      (footprint "eagle-import:B2.0")
      (libsource (lib "eagle-import") (part "TPSB2.0"))
    )
    (comp (ref "TP96")
      (value "TPSB2.0")
      (footprint "eagle-import:B2.0")
      (libsource (lib "eagle-import") (part "TPSB2.0"))
    )
    (comp (ref "TP97")
      (value "TPSB2.0")
      (footprint "eagle-import:B2.0")
      (libsource (lib "eagle-import") (part "TPSB2.0"))
    )
    (comp (ref "TP98")
      (value "TPSB2.0")
      (footprint "eagle-import:B2.0")
      (libsource (lib "eagle-import") (part "TPSB2.0"))
    )
    (comp (ref "TP99")
      (value "TPSB2.0")
      (footprint "eagle-import:B2.0")
      (libsource (lib "eagle-import") (part "TPSB2.0"))
    )
    (comp (ref "TP100")
      (value "TPSB2.0")
      (footprint "eagle-import:B2.0")
      (libsource (lib "eagle-import") (part "TPSB2.0"))
    )
    (comp (ref "TP101")
      (value "TPSB2.0")
      (footprint "eagle-import:B2.0")
      (libsource (lib "eagle-import") (part "TPSB2.0"))
    )
    (comp (ref "TP102")
      (value "TPSB2.0")
      (footprint "eagle-import:B2.0")
      (libsource (lib "eagle-import") (part "TPSB2.0"))
    )
    (comp (ref "TP103")
      (value "TPSB2.0")
      (footprint "eagle-import:B2.0")
      (libsource (lib "eagle-import") (part "TPSB2.0"))
    )
    (comp (ref "TP104")
      (value "TPSB2.0")
      (footprint "eagle-import:B2.0")
      (libsource (lib "eagle-import") (part "TPSB2.0"))
    )
    (comp (ref "TP105")
      (value "TPSB2.0")
      (footprint "eagle-import:B2.0")
      (libsource (lib "eagle-import") (part "TPSB2.0"))
    )
    (comp (ref "TP106")
      (value "TPSB2.0")
      (footprint "eagle-import:B2.0")
      (libsource (lib "eagle-import") (part "TPSB2.0"))
    )
    (comp (ref "TP107")
      (value "TPSB2.0")
      (footprint "eagle-import:B2.0")
      (libsource (lib "eagle-import") (part "TPSB2.0"))
    )
    (comp (ref "TP108")
      (value "TPSB2.0")
      (footprint "eagle-import:B2.0")
      (libsource (lib "eagle-import") (part "TPSB2.0"))
    )
    (comp (ref "TP109")
      (value "TPSB2.0")
      (footprint "eagle-import:B2.0")
      (libsource (lib "eagle-import") (part "TPSB2.0"))
    )
    (comp (ref "TP110")
      (value "TPSB2.0")
      (footprint "eagle-import:B2.0")
      (libsource (lib "eagle-import") (part "TPSB2.0"))
    )
    (comp (ref "TP111")
      (value "TPSB1,27")
      (footprint "eagle-import:B1,27")
      (libsource (lib "eagle-import") (part "TPSB1,27"))
    )
    (comp (ref "TP112")
      (value "TPSB2.0")
      (footprint "eagle-import:B2.0")
      (libsource (lib "eagle-import") (part "TPSB2.0"))
    )
    (comp (ref "TP113")
      (value "TPSB2.0")
      (footprint "eagle-import:B2.0")
      (libsource (lib "eagle-import") (part "TPSB2.0"))
    )
    (comp (ref "TP114")
      (value "TPSB2.0")
      (footprint "eagle-import:B2.0")
      (libsource (lib "eagle-import") (part "TPSB2.0"))
    )
    (comp (ref "TP115")
      (value "TPSB2.0")
      (footprint "eagle-import:B2.0")
      (libsource (lib "eagle-import") (part "TPSB2.0"))
    )
    (comp (ref "X501")
      (value "CON_BMWV2")
      (footprint "eagle-import:24-PIN_V2")
      (libsource (lib "eagle-import") (part "CON_BMWV2"))
    )
    (comp (ref "X502")
      (value "22-23-2021")
      (footprint "eagle-import:22-23-2021")
      (fields (field (name "MF") "MOLEX"))
      (libsource (lib "eagle-import") (part "22-23-2021"))
    )
    (comp (ref "X503")
      (value "22-23-2051")
      (footprint "eagle-import:22-23-2051")
      (fields (field (name "MF") "MOLEX"))
      (libsource (lib "eagle-import") (part "22-23-2051"))
    )
    (comp (ref "6V1201")
      (value "TPSB2.0")
      (footprint "eagle-import:B2.0")
      (libsource (lib "eagle-import") (part "TPSB2.0"))
    )
    (comp (ref "10V1201")
      (value "TPSB2.0")
      (footprint "eagle-import:B2.0")
      (libsource (lib "eagle-import") (part "TPSB2.0"))
    )
    (comp (ref "23")
      (value "2081-1132")
      (footprint "eagle-import:12-PIN")
      (libsource (lib "eagle-import") (part "2081-1132"))
    )
    (comp (ref "24")
      (value "2081-1132")
      (footprint "eagle-import:12-PIN")
      (libsource (lib "eagle-import") (part "2081-1132"))
    )
    (comp (ref "C1201")
      (value "4.7u")
      (footprint "eagle-import:C0805")
      (fields (field (name "MPN") "CC0805KKX5R8BB475"))
      (libsource (lib "eagle-import") (part "CERAMIC-4.7UF-25V-10%-X5R(0805)"))
    )
    (comp (ref "C1202")
      (value "100nF")
      (footprint "eagle-import:C0805")
      (fields (field (name "MPN") "CC0805KRX7R9BB104"))
      (libsource (lib "eagle-import") (part "CERAMIC-100NF-50V-10%-X7R(0805)"))
    )
    (comp (ref "C1203")
      (value "100nF,")
      (footprint "eagle-import:C0805")
      (fields (field (name "MPN") "CC0805KRX7R9BB104"))
      (libsource (lib "eagle-import") (part "CERAMIC-100NF-50V-10%-X7R(0805)"))
    )
    (comp (ref "C1204")
      (value "100nF,")
      (footprint "eagle-import:C0805")
      (fields (field (name "MPN") "CC0805KRX7R9BB104"))
      (libsource (lib "eagle-import") (part "CERAMIC-100NF-50V-10%-X7R(0805)"))
    )
    (comp (ref "C1205")
      (value "100nF.")
      (footprint "eagle-import:C0805")
      (fields (field (name "MPN") "CC0805KRX7R9BB104"))
      (libsource (lib "eagle-import") (part "CERAMIC-100NF-50V-10%-X7R(0805)"))
    )
    (comp (ref "C1206")
      (value "100nF.")
      (footprint "eagle-import:C0805")
      (fields (field (name "MPN") "CC0805KRX7R9BB104"))
      (libsource (lib "eagle-import") (part "CERAMIC-100NF-50V-10%-X7R(0805)"))
    )
    (comp (ref "C1207")
      (value "100u")
      (footprint "eagle-import:C1206")
      (fields (field (name "MPN") "GRM31CR60J107ME39L"))
      (libsource (lib "eagle-import") (part "CERAMIC-100UF-6.3V-20%-X5R(1206)"))
    )
    (comp (ref "C1208")
      (value "100u")
      (footprint "eagle-import:C1206")
      (fields (field (name "MPN") "GRM31CR60J107ME39L"))
      (libsource (lib "eagle-import") (part "CERAMIC-100UF-6.3V-20%-X5R(1206)"))
    )
    (comp (ref "C1209")
      (value "2.2nF")
      (footprint "eagle-import:C0805")
      (fields (field (name "MPN") "CC0805KRX7R9BB104"))
      (libsource (lib "eagle-import") (part "CERAMIC-100NF-50V-10%-X7R(0805)"))
    )
    (comp (ref "C1210")
      (value "100nF")
      (footprint "eagle-import:C0805")
      (fields (field (name "MPN") "CC0805KRX7R9BB104"))
      (libsource (lib "eagle-import") (part "CERAMIC-100NF-50V-10%-X7R(0805)"))
    )
    (comp (ref "D1201")
      (value "SM6T")
      (footprint "eagle-import:DO214AA")
      (libsource (lib "eagle-import") (part "SM6T"))
    )
    (comp (ref "D1202")
      (value "1N4007,")
      (footprint "eagle-import:DO-214AC")
      (fields (field (name "MPN") "1N4007"))
      (libsource (lib "eagle-import") (part "DIODE-GEN-PURPOSE-1KV-1A(DO-214AC)"))
    )
    (comp (ref "D1203")
      (value "1N4007,")
      (footprint "eagle-import:DO-214AC")
      (fields (field (name "MPN") "1N4007"))
      (libsource (lib "eagle-import") (part "DIODE-GEN-PURPOSE-1KV-1A(DO-214AC)"))
    )
    (comp (ref "D1204")
      (value "SM6TDO214AA_BI")
      (footprint "eagle-import:DO214AA_BI")
      (libsource (lib "eagle-import") (part "SM6TDO214AA_BI"))
    )
    (comp (ref "D1205")
      (value "1N4007.")
      (footprint "eagle-import:DO-214AC")
      (fields (field (name "MPN") "1N4007"))
      (libsource (lib "eagle-import") (part "DIODE-GEN-PURPOSE-1KV-1A(DO-214AC)"))
    )
    (comp (ref "D1206")
      (value "1N4007.")
      (footprint "eagle-import:DO-214AC")
      (fields (field (name "MPN") "1N4007"))
      (libsource (lib "eagle-import") (part "DIODE-GEN-PURPOSE-1KV-1A(DO-214AC)"))
    )
    (comp (ref "D1207")
      (value "1N5817")
      (footprint "eagle-import:DO-214AC_SLIM")
      (libsource (lib "eagle-import") (part "DIODE-GEN-PURPOSE-1KV-1A(DO-214AC)DO-214AC/1206"))
    )
    (comp (ref "D1208")
      (value "1N5817.")
      (footprint "eagle-import:DO-214AC_SLIM")
      (libsource (lib "eagle-import") (part "DIODE-GEN-PURPOSE-1KV-1A(DO-214AC)DO-214AC/1206"))
    )
    (comp (ref "D1209")
      (value "1N5817.")
      (footprint "eagle-import:DO-214AC_SLIM")
      (libsource (lib "eagle-import") (part "DIODE-GEN-PURPOSE-1KV-1A(DO-214AC)DO-214AC/1206"))
    )
    (comp (ref "D1210")
      (value "1N5817")
      (footprint "eagle-import:DO-214AC_SLIM")
      (libsource (lib "eagle-import") (part "DIODE-GEN-PURPOSE-1KV-1A(DO-214AC)DO-214AC/1206"))
    )
    (comp (ref "D1211")
      (value "1N4007")
      (footprint "eagle-import:DO-214AC")
      (libsource (lib "eagle-import") (part "DIODE-GEN-PURPOSE-1KV-1A(DO-214AC)"))
    )
    (comp (ref "D1212")
      (value "1N4007")
      (footprint "eagle-import:DO-214AC")
      (libsource (lib "eagle-import") (part "DIODE-GEN-PURPOSE-1KV-1A(DO-214AC)"))
    )
    (comp (ref "FID1201")
      (value "FIDUCIAL")
      (footprint "eagle-import:FIDUCIAL_1MM")
      (libsource (lib "eagle-import") (part "FIDUCIAL"))
    )
    (comp (ref "FID1202")
      (value "FIDUCIAL")
      (footprint "eagle-import:FIDUCIAL_1MM")
      (libsource (lib "eagle-import") (part "FIDUCIAL"))
    )
    (comp (ref "FID1203")
      (value "FIDUCIAL")
      (footprint "eagle-import:FIDUCIAL_1MM")
      (libsource (lib "eagle-import") (part "FIDUCIAL"))
    )
    (comp (ref "FID1204")
      (value "FIDUCIAL")
      (footprint "eagle-import:FIDUCIAL_1MM")
      (libsource (lib "eagle-import") (part "FIDUCIAL"))
    )
    (comp (ref "IC1201")
      (value "LM2904")
      (footprint "eagle-import:SO08")
      (libsource (lib "eagle-import") (part "LM358D"))
    )
    (comp (ref "IC1202")
      (value "78L06")
      (footprint "eagle-import:SOT89_ROUND")
      (libsource (lib "eagle-import") (part "78LXXSOT89_ROUND"))
    )
    (comp (ref "IC1203")
      (value "6V pos")
      (footprint "eagle-import:78LXX")
      (libsource (lib "eagle-import") (part "v-reg_78LXX"))
    )
    (comp (ref "IC1204")
      (value "78L10")
      (footprint "eagle-import:SOT89_ROUND")
      (libsource (lib "eagle-import") (part "78LXXSOT89_ROUND"))
    )
    (comp (ref "IC1205")
      (value "4028")
      (footprint "eagle-import:SO16")
      (libsource (lib "eagle-import") (part "4028D"))
    )
    (comp (ref "IC1206")
      (value "NUP4304SOT457_R")
      (footprint "eagle-import:SOT457R_PHILIPS")
      (libsource (lib "eagle-import") (part "NUP4304SOT457_R"))
    )
    (comp (ref "IC1207")
      (value "ULN2004")
      (footprint "eagle-import:SO16")
      (libsource (lib "eagle-import") (part "ULN2004AD"))
    )
    (comp (ref "IC1208")
      (value "LM339")
      (footprint "eagle-import:SO14")
      (libsource (lib "eagle-import") (part "LM339D"))
    )
    (comp (ref "IC1209")
      (value "317TO202H_NOHOLE")
      (footprint "eagle-import:TO220H_NOHOLE")
      (libsource (lib "eagle-import") (part "317TO202H_NOHOLE"))
    )
    (comp (ref "IC1210")
      (value "555")
      (footprint "eagle-import:SO08")
      (libsource (lib "eagle-import") (part "555DNE"))
    )
    (comp (ref "IC1211")
      (value "4538")
      (footprint "eagle-import:SO16")
      (libsource (lib "eagle-import") (part "4538D"))
    )
    (comp (ref "JP1201")
      (value "JP2EJP2_SMALLPADS")
      (footprint "eagle-import:JP2_SMALLPADS")
      (libsource (lib "eagle-import") (part "JP2EJP2_SMALLPADS"))
    )
    (comp (ref "JP1202")
      (value "JP2EJP2_SMALLPADS")
      (footprint "eagle-import:JP2_SMALLPADS")
      (libsource (lib "eagle-import") (part "JP2EJP2_SMALLPADS"))
    )
    (comp (ref "JP1203")
      (value "JP2EJP2_SMALLPADS")
      (footprint "eagle-import:JP2_SMALLPADS")
      (libsource (lib "eagle-import") (part "JP2EJP2_SMALLPADS"))
    )
    (comp (ref "JP1204")
      (value "JP2EJP2_SMALLPADS")
      (footprint "eagle-import:JP2_SMALLPADS")
      (libsource (lib "eagle-import") (part "JP2EJP2_SMALLPADS"))
    )
    (comp (ref "JP1205")
      (value "JP2E_ORIG")
      (footprint "eagle-import:JP2_ORIG_SMALLPADS")
      (libsource (lib "eagle-import") (part "JP2E_ORIG"))
    )
    (comp (ref "LED1201")
      (value "LEDLD260")
      (footprint "eagle-import:LD260")
      (libsource (lib "eagle-import") (part "LEDLD260"))
    )
    (comp (ref "LED1202")
      (value "LEDLD260")
      (footprint "eagle-import:LD260")
      (libsource (lib "eagle-import") (part "LEDLD260"))
    )
    (comp (ref "LED1203")
      (value "LEDLD260")
      (footprint "eagle-import:LD260")
      (libsource (lib "eagle-import") (part "LEDLD260"))
    )
    (comp (ref "LED1204")
      (value "LEDLD260")
      (footprint "eagle-import:LD260")
      (libsource (lib "eagle-import") (part "LEDLD260"))
    )
    (comp (ref "LED1205")
      (value "LEDLD260")
      (footprint "eagle-import:LD260")
      (libsource (lib "eagle-import") (part "LEDLD260"))
    )
    (comp (ref "LED1206")
      (value "LEDLD260")
      (footprint "eagle-import:LD260")
      (libsource (lib "eagle-import") (part "LEDLD260"))
    )
    (comp (ref "Q1201")
      (value "BA.")
      (footprint "eagle-import:SOT89")
      (libsource (lib "eagle-import") (part "PNP-TRANSISTOR_SOT89"))
    )
    (comp (ref "Q1202")
      (value "BA.")
      (footprint "eagle-import:SOT89")
      (libsource (lib "eagle-import") (part "PNP-TRANSISTOR_SOT89"))
    )
    (comp (ref "Q1203")
      (value "MY")
      (footprint "eagle-import:SOT89")
      (libsource (lib "eagle-import") (part "NPN-TRANSISTOR_SOT89"))
    )
    (comp (ref "Q1204")
      (value "BA")
      (footprint "eagle-import:SOT89")
      (libsource (lib "eagle-import") (part "PNP-TRANSISTOR_SOT89"))
    )
    (comp (ref "Q1205")
      (value "BA")
      (footprint "eagle-import:SOT89")
      (libsource (lib "eagle-import") (part "PNP-TRANSISTOR_SOT89"))
    )
    (comp (ref "Q1206")
      (value "J1")
      (footprint "eagle-import:SOT-23")
      (fields (field (name "MPN") "BSS138W-7-F"))
      (libsource (lib "eagle-import") (part "SMD-MOSFET-N-CH-50V-200MA-BSS138W-7-F(SOT-23)"))
    )
    (comp (ref "Q1207")
      (value "J1")
      (footprint "eagle-import:SOT-23")
      (fields (field (name "MPN") "BSS138W-7-F"))
      (libsource (lib "eagle-import") (part "SMD-MOSFET-N-CH-50V-200MA-BSS138W-7-F(SOT-23)"))
    )
    (comp (ref "R1201")
      (value "102")
      (footprint "eagle-import:R0805")
      (fields (field (name "MPN") "RC0805JR-071KL"))
      (libsource (lib "eagle-import") (part "SMD-RES-1K-5%-1/8W(0805)"))
    )
    (comp (ref "R1202")
      (value "13")
      (footprint "eagle-import:R1206")
      (fields (field (name "MPN") "RC1206JR-0713RL"))
      (libsource (lib "eagle-import") (part "SMD-RES-13R-5%-1/4W(1206)"))
    )
    (comp (ref "R1203")
      (value "R_user")
      (footprint "eagle-import:R0805")
      (libsource (lib "eagle-import") (part "R-EU_R0805"))
    )
    (comp (ref "R1204")
      (value "R_user")
      (footprint "eagle-import:R0805")
      (libsource (lib "eagle-import") (part "R-EU_R0805"))
    )
    (comp (ref "R1205")
      (value "4701")
      (footprint "eagle-import:R0805")
      (fields (field (name "MPN") "RC0805JR-074K7L"))
      (libsource (lib "eagle-import") (part "SMD-RES-4.7K-5%-1/8W(0805)"))
    )
    (comp (ref "R1206")
      (value "13")
      (footprint "eagle-import:R1206")
      (fields (field (name "MPN") "RC1206JR-0713RL"))
      (libsource (lib "eagle-import") (part "SMD-RES-13R-5%-1/4W(1206)"))
    )
    (comp (ref "R1207")
      (value "1002")
      (footprint "eagle-import:R0805")
      (fields (field (name "MPN") "RC0805FR-0710KL"))
      (libsource (lib "eagle-import") (part "SMD-RES-10K-1%-1/8W(0805)"))
    )
    (comp (ref "R1208")
      (value "1002")
      (footprint "eagle-import:R0805")
      (fields (field (name "MPN") "RC0805FR-0710KL"))
      (libsource (lib "eagle-import") (part "SMD-RES-10K-1%-1/8W(0805)"))
    )
    (comp (ref "R1209")
      (value "104.")
      (footprint "eagle-import:R0805")
      (fields (field (name "MPN") "RC0805FR-0710KL"))
      (libsource (lib "eagle-import") (part "SMD-RES-10K-1%-1/8W(0805)"))
    )
    (comp (ref "R1210")
      (value "104.")
      (footprint "eagle-import:R0805")
      (fields (field (name "MPN") "RC0805FR-0710KL"))
      (libsource (lib "eagle-import") (part "SMD-RES-10K-1%-1/8W(0805)"))
    )
    (comp (ref "R1211")
      (value "104.")
      (footprint "eagle-import:R0805")
      (fields (field (name "MPN") "RC0805FR-0710KL"))
      (libsource (lib "eagle-import") (part "SMD-RES-10K-1%-1/8W(0805)"))
    )
    (comp (ref "R1212")
      (value "102")
      (footprint "eagle-import:R0805")
      (fields (field (name "MPN") "RC0805JR-071KL"))
      (libsource (lib "eagle-import") (part "SMD-RES-1K-5%-1/8W(0805)"))
    )
    (comp (ref "R1213")
      (value "102")
      (footprint "eagle-import:R0805")
      (fields (field (name "MPN") "RC0805JR-071KL"))
      (libsource (lib "eagle-import") (part "SMD-RES-1K-5%-1/8W(0805)"))
    )
    (comp (ref "R1214")
      (value "102")
      (footprint "eagle-import:R0805")
      (fields (field (name "MPN") "RC0805JR-071KL"))
      (libsource (lib "eagle-import") (part "SMD-RES-1K-5%-1/8W(0805)"))
    )
    (comp (ref "R1215")
      (value "100")
      (footprint "eagle-import:R0805")
      (fields (field (name "MPN") "RC0805JR-07220RL"))
      (libsource (lib "eagle-import") (part "SMD-RES-220R-5%-1/8W(0805)"))
    )
    (comp (ref "R1216")
      (value "4701")
      (footprint "eagle-import:R0805")
      (fields (field (name "MPN") "RC0805JR-074K7L"))
      (libsource (lib "eagle-import") (part "SMD-RES-4.7K-5%-1/8W(0805)"))
    )
    (comp (ref "R1217")
      (value "2702")
      (footprint "eagle-import:R0805")
      (fields (field (name "MPN") "RC0805JR-074K7L"))
      (libsource (lib "eagle-import") (part "SMD-RES-4.7K-5%-1/8W(0805)"))
    )
    (comp (ref "R1218")
      (value "13")
      (footprint "eagle-import:R1206")
      (fields (field (name "MPN") "RC1206JR-0713RL"))
      (libsource (lib "eagle-import") (part "SMD-RES-13R-5%-1/4W(1206)"))
    )
    (comp (ref "R1219")
      (value "2201")
      (footprint "eagle-import:R0805")
      (fields (field (name "MPN") "RC0805JR-072K2L"))
      (libsource (lib "eagle-import") (part "SMD-RES-2.2K-5%-1/8W(0805)"))
    )
    (comp (ref "R1220")
      (value "1002")
      (footprint "eagle-import:R0805")
      (fields (field (name "MPN") "RC0805FR-0710KL"))
      (libsource (lib "eagle-import") (part "SMD-RES-10K-1%-1/8W(0805)"))
    )
    (comp (ref "R1221")
      (value "1502")
      (footprint "eagle-import:R0805")
      (fields (field (name "MPN") "RC0805FR-0710KL"))
      (libsource (lib "eagle-import") (part "SMD-RES-10K-1%-1/8W(0805)"))
    )
    (comp (ref "R1222")
      (value "2702")
      (footprint "eagle-import:R0805")
      (fields (field (name "MPN") "RC0805JR-074K7L"))
      (libsource (lib "eagle-import") (part "SMD-RES-4.7K-5%-1/8W(0805)"))
    )
    (comp (ref "R1223")
      (value "2702")
      (footprint "eagle-import:R0805")
      (fields (field (name "MPN") "RC0805JR-074K7L"))
      (libsource (lib "eagle-import") (part "SMD-RES-4.7K-5%-1/8W(0805)"))
    )
    (comp (ref "R1224")
      (value "1002")
      (footprint "eagle-import:R0805")
      (fields (field (name "MPN") "RC0805FR-0710KL"))
      (libsource (lib "eagle-import") (part "SMD-RES-10K-1%-1/8W(0805)"))
    )
    (comp (ref "R1225")
      (value "104")
      (footprint "eagle-import:R0805")
      (fields (field (name "MPN") "RC0805FR-0710KL"))
      (libsource (lib "eagle-import") (part "SMD-RES-10K-1%-1/8W(0805)"))
    )
    (comp (ref "R1226")
      (value "4701")
      (footprint "eagle-import:R0805")
      (fields (field (name "MPN") "RC0805JR-074K7L"))
      (libsource (lib "eagle-import") (part "SMD-RES-4.7K-5%-1/8W(0805)"))
    )
    (comp (ref "R1227")
      (value "47")
      (footprint "eagle-import:V235_17_1MM")
      (libsource (lib "eagle-import") (part "R-EU_V235/17_1MM"))
    )
    (comp (ref "R1228")
      (value "102")
      (footprint "eagle-import:R0805")
      (fields (field (name "MPN") "RC0805JR-071KL"))
      (libsource (lib "eagle-import") (part "SMD-RES-1K-5%-1/8W(0805)"))
    )
    (comp (ref "R1229")
      (value "47")
      (footprint "eagle-import:V235_17_1MM")
      (libsource (lib "eagle-import") (part "R-EU_V235/17_1MM"))
    )
    (comp (ref "R1230")
      (value "104")
      (footprint "eagle-import:R0805")
      (fields (field (name "MPN") "RC0805FR-0710KL"))
      (libsource (lib "eagle-import") (part "SMD-RES-10K-1%-1/8W(0805)"))
    )
    (comp (ref "R1231")
      (value "1502")
      (footprint "eagle-import:R0805")
      (fields (field (name "MPN") "RC0805FR-0710KL"))
      (libsource (lib "eagle-import") (part "SMD-RES-10K-1%-1/8W(0805)"))
    )
    (comp (ref "R1232")
      (value "1002")
      (footprint "eagle-import:R0805")
      (fields (field (name "MPN") "RC0805FR-0710KL"))
      (libsource (lib "eagle-import") (part "SMD-RES-10K-1%-1/8W(0805)"))
    )
    (comp (ref "R1233")
      (value "2201")
      (footprint "eagle-import:R0805")
      (fields (field (name "MPN") "RC0805JR-072K2L"))
      (libsource (lib "eagle-import") (part "SMD-RES-2.2K-5%-1/8W(0805)"))
    )
    (comp (ref "R1234")
      (value "13")
      (footprint "eagle-import:R1206")
      (fields (field (name "MPN") "RC1206JR-0713RL"))
      (libsource (lib "eagle-import") (part "SMD-RES-13R-5%-1/4W(1206)"))
    )
    (comp (ref "R1235")
      (value "104")
      (footprint "eagle-import:R0805")
      (fields (field (name "MPN") "RC0805FR-0710KL"))
      (libsource (lib "eagle-import") (part "SMD-RES-10K-1%-1/8W(0805)"))
    )
    (comp (ref "R1236")
      (value "47")
      (footprint "eagle-import:V235_17_1MM")
      (libsource (lib "eagle-import") (part "R-EU_V235/17_1MM"))
    )
    (comp (ref "R1237")
      (value "47")
      (footprint "eagle-import:V235_17_1MM")
      (libsource (lib "eagle-import") (part "R-EU_V235/17_1MM"))
    )
    (comp (ref "R1238")
      (value "100")
      (footprint "eagle-import:R0805")
      (fields (field (name "MPN") "RC0805JR-072K2L"))
      (libsource (lib "eagle-import") (part "SMD-RES-2.2K-5%-1/8W(0805)"))
    )
    (comp (ref "R1239")
      (value "(101)")
      (footprint "eagle-import:R0805")
      (fields (field (name "MPN") "RC0805JR-072K2L"))
      (libsource (lib "eagle-import") (part "SMD-RES-2.2K-5%-1/8W(0805)"))
    )
    (comp (ref "R1240")
      (value "2702")
      (footprint "eagle-import:R0805")
      (fields (field (name "MPN") "RC0805FR-0710KL"))
      (libsource (lib "eagle-import") (part "SMD-RES-10K-1%-1/8W(0805)"))
    )
    (comp (ref "R1241")
      (value "104")
      (footprint "eagle-import:R0805")
      (fields (field (name "MPN") "RC0805FR-0710KL"))
      (libsource (lib "eagle-import") (part "SMD-RES-10K-1%-1/8W(0805)"))
    )
    (comp (ref "R1242")
      (value "(1000)")
      (footprint "eagle-import:R0805")
      (fields (field (name "MPN") "RC0805JR-07100RL"))
      (libsource (lib "eagle-import") (part "SMD-RES-100R-5%-1/8W(0805)"))
    )
    (comp (ref "R1243")
      (value "(101)")
      (footprint "eagle-import:R0805")
      (fields (field (name "MPN") "RC0805JR-07100RL"))
      (libsource (lib "eagle-import") (part "SMD-RES-100R-5%-1/8W(0805)"))
    )
    (comp (ref "R1244")
      (value "(1002)")
      (footprint "eagle-import:R0805")
      (fields (field (name "MPN") "RC0805FR-0710KL"))
      (libsource (lib "eagle-import") (part "SMD-RES-10K-1%-1/8W(0805)"))
    )
    (comp (ref "R1245")
      (value "2702")
      (footprint "eagle-import:R0805")
      (fields (field (name "MPN") "RC0805JR-074K7L"))
      (libsource (lib "eagle-import") (part "SMD-RES-4.7K-5%-1/8W(0805)"))
    )
    (comp (ref "R1246")
      (value "(1002)")
      (footprint "eagle-import:R0805")
      (fields (field (name "MPN") "RC0805JR-074K7L"))
      (libsource (lib "eagle-import") (part "SMD-RES-4.7K-5%-1/8W(0805)"))
    )
    (comp (ref "SJ1201")
      (value "SJ")
      (footprint "eagle-import:SJ")
      (libsource (lib "eagle-import") (part "SJ"))
    )
    (comp (ref "START1201")
      (value "TPSB2.0")
      (footprint "eagle-import:B2.0")
      (libsource (lib "eagle-import") (part "TPSB2.0"))
    )
    (comp (ref "TP254")
      (value "TPSB2.0")
      (footprint "eagle-import:B2.0")
      (libsource (lib "eagle-import") (part "TPSB2.0"))
    )
    (comp (ref "TP255")
      (value "TPSB2.0")
      (footprint "eagle-import:B2.0")
      (libsource (lib "eagle-import") (part "TPSB2.0"))
    )
    (comp (ref "TP256")
      (value "TPSB2.0")
      (footprint "eagle-import:B2.0")
      (libsource (lib "eagle-import") (part "TPSB2.0"))
    )
    (comp (ref "TP257")
      (value "TPSB2.0")
      (footprint "eagle-import:B2.0")
      (libsource (lib "eagle-import") (part "TPSB2.0"))
    )
    (comp (ref "TP258")
      (value "TPSB2.0")
      (footprint "eagle-import:B2.0")
      (libsource (lib "eagle-import") (part "TPSB2.0"))
    )
    (comp (ref "TP259")
      (value "TPSB2.0")
      (footprint "eagle-import:B2.0")
      (libsource (lib "eagle-import") (part "TPSB2.0"))
    )
    (comp (ref "TP260")
      (value "TPSB2.0")
      (footprint "eagle-import:B2.0")
      (libsource (lib "eagle-import") (part "TPSB2.0"))
    )
    (comp (ref "TP261")
      (value "TPSB2.0")
      (footprint "eagle-import:B2.0")
      (libsource (lib "eagle-import") (part "TPSB2.0"))
    )
    (comp (ref "TP262")
      (value "TPSB2.0")
      (footprint "eagle-import:B2.0")
      (libsource (lib "eagle-import") (part "TPSB2.0"))
    )
    (comp (ref "TP263")
      (value "TPSB2.0")
      (footprint "eagle-import:B2.0")
      (libsource (lib "eagle-import") (part "TPSB2.0"))
    )
    (comp (ref "TP264")
      (value "TPSB2.0")
      (footprint "eagle-import:B2.0")
      (libsource (lib "eagle-import") (part "TPSB2.0"))
    )
    (comp (ref "TP265")
      (value "TPSB2.0")
      (footprint "eagle-import:B2.0")
      (libsource (lib "eagle-import") (part "TPSB2.0"))
    )
    (comp (ref "TP266")
      (value "TPSB2.0")
      (footprint "eagle-import:B2.0")
      (libsource (lib "eagle-import") (part "TPSB2.0"))
    )
    (comp (ref "TP267")
      (value "TPSB2.0")
      (footprint "eagle-import:B2.0")
      (libsource (lib "eagle-import") (part "TPSB2.0"))
    )
    (comp (ref "TP268")
      (value "TPSB2.0")
      (footprint "eagle-import:B2.0")
      (libsource (lib "eagle-import") (part "TPSB2.0"))
    )
    (comp (ref "TP269")
      (value "TPSB2.0")
      (footprint "eagle-import:B2.0")
      (libsource (lib "eagle-import") (part "TPSB2.0"))
    )
    (comp (ref "TP270")
      (value "TPSB2.0")
      (footprint "eagle-import:B2.0")
      (libsource (lib "eagle-import") (part "TPSB2.0"))
    )
    (comp (ref "TP271")
      (value "TPSB2.0")
      (footprint "eagle-import:B2.0")
      (libsource (lib "eagle-import") (part "TPSB2.0"))
    )
    (comp (ref "TP272")
      (value "TPSB1,27")
      (footprint "eagle-import:B1,27")
      (libsource (lib "eagle-import") (part "TPSB1,27"))
    )
    (comp (ref "TP273")
      (value "TPSB2.0")
      (footprint "eagle-import:B2.0")
      (libsource (lib "eagle-import") (part "TPSB2.0"))
    )
    (comp (ref "TP274")
      (value "TPSB2.0")
      (footprint "eagle-import:B2.0")
      (libsource (lib "eagle-import") (part "TPSB2.0"))
    )
    (comp (ref "TP275")
      (value "TPSB2.0")
      (footprint "eagle-import:B2.0")
      (libsource (lib "eagle-import") (part "TPSB2.0"))
    )
    (comp (ref "TP276")
      (value "TPSB2.0")
      (footprint "eagle-import:B2.0")
      (libsource (lib "eagle-import") (part "TPSB2.0"))
    )
    (comp (ref "X1201")
      (value "CON_BMWV2")
      (footprint "eagle-import:24-PIN_V2")
      (libsource (lib "eagle-import") (part "CON_BMWV2"))
    )
    (comp (ref "X1202")
      (value "22-23-2021")
      (footprint "eagle-import:22-23-2021")
      (fields (field (name "MF") "MOLEX"))
      (libsource (lib "eagle-import") (part "22-23-2021"))
    )
    (comp (ref "X1203")
      (value "22-23-2051")
      (footprint "eagle-import:22-23-2051")
      (fields (field (name "MF") "MOLEX"))
      (libsource (lib "eagle-import") (part "22-23-2051"))
    )
    (comp (ref "6V601")
      (value "TPSB2.0")
      (footprint "eagle-import:B2.0")
      (libsource (lib "eagle-import") (part "TPSB2.0"))
    )
    (comp (ref "10V601")
      (value "TPSB2.0")
      (footprint "eagle-import:B2.0")
      (libsource (lib "eagle-import") (part "TPSB2.0"))
    )
    (comp (ref "11")
      (value "2081-1132")
      (footprint "eagle-import:12-PIN")
      (libsource (lib "eagle-import") (part "2081-1132"))
    )
    (comp (ref "12")
      (value "2081-1132")
      (footprint "eagle-import:12-PIN")
      (libsource (lib "eagle-import") (part "2081-1132"))
    )
    (comp (ref "C601")
      (value "4.7u")
      (footprint "eagle-import:C0805")
      (fields (field (name "MPN") "CC0805KKX5R8BB475"))
      (libsource (lib "eagle-import") (part "CERAMIC-4.7UF-25V-10%-X5R(0805)"))
    )
    (comp (ref "C602")
      (value "100nF")
      (footprint "eagle-import:C0805")
      (fields (field (name "MPN") "CC0805KRX7R9BB104"))
      (libsource (lib "eagle-import") (part "CERAMIC-100NF-50V-10%-X7R(0805)"))
    )
    (comp (ref "C603")
      (value "100nF,")
      (footprint "eagle-import:C0805")
      (fields (field (name "MPN") "CC0805KRX7R9BB104"))
      (libsource (lib "eagle-import") (part "CERAMIC-100NF-50V-10%-X7R(0805)"))
    )
    (comp (ref "C604")
      (value "100nF,")
      (footprint "eagle-import:C0805")
      (fields (field (name "MPN") "CC0805KRX7R9BB104"))
      (libsource (lib "eagle-import") (part "CERAMIC-100NF-50V-10%-X7R(0805)"))
    )
    (comp (ref "C605")
      (value "100nF.")
      (footprint "eagle-import:C0805")
      (fields (field (name "MPN") "CC0805KRX7R9BB104"))
      (libsource (lib "eagle-import") (part "CERAMIC-100NF-50V-10%-X7R(0805)"))
    )
    (comp (ref "C606")
      (value "100nF.")
      (footprint "eagle-import:C0805")
      (fields (field (name "MPN") "CC0805KRX7R9BB104"))
      (libsource (lib "eagle-import") (part "CERAMIC-100NF-50V-10%-X7R(0805)"))
    )
    (comp (ref "C607")
      (value "100u")
      (footprint "eagle-import:C1206")
      (fields (field (name "MPN") "GRM31CR60J107ME39L"))
      (libsource (lib "eagle-import") (part "CERAMIC-100UF-6.3V-20%-X5R(1206)"))
    )
    (comp (ref "C608")
      (value "100u")
      (footprint "eagle-import:C1206")
      (fields (field (name "MPN") "GRM31CR60J107ME39L"))
      (libsource (lib "eagle-import") (part "CERAMIC-100UF-6.3V-20%-X5R(1206)"))
    )
    (comp (ref "C609")
      (value "2.2nF")
      (footprint "eagle-import:C0805")
      (fields (field (name "MPN") "CC0805KRX7R9BB104"))
      (libsource (lib "eagle-import") (part "CERAMIC-100NF-50V-10%-X7R(0805)"))
    )
    (comp (ref "C610")
      (value "100nF")
      (footprint "eagle-import:C0805")
      (fields (field (name "MPN") "CC0805KRX7R9BB104"))
      (libsource (lib "eagle-import") (part "CERAMIC-100NF-50V-10%-X7R(0805)"))
    )
    (comp (ref "D601")
      (value "SM6T")
      (footprint "eagle-import:DO214AA")
      (libsource (lib "eagle-import") (part "SM6T"))
    )
    (comp (ref "D602")
      (value "1N4007,")
      (footprint "eagle-import:DO-214AC")
      (fields (field (name "MPN") "1N4007"))
      (libsource (lib "eagle-import") (part "DIODE-GEN-PURPOSE-1KV-1A(DO-214AC)"))
    )
    (comp (ref "D603")
      (value "1N4007,")
      (footprint "eagle-import:DO-214AC")
      (fields (field (name "MPN") "1N4007"))
      (libsource (lib "eagle-import") (part "DIODE-GEN-PURPOSE-1KV-1A(DO-214AC)"))
    )
    (comp (ref "D604")
      (value "SM6TDO214AA_BI")
      (footprint "eagle-import:DO214AA_BI")
      (libsource (lib "eagle-import") (part "SM6TDO214AA_BI"))
    )
    (comp (ref "D605")
      (value "1N4007.")
      (footprint "eagle-import:DO-214AC")
      (fields (field (name "MPN") "1N4007"))
      (libsource (lib "eagle-import") (part "DIODE-GEN-PURPOSE-1KV-1A(DO-214AC)"))
    )
    (comp (ref "D606")
      (value "1N4007.")
      (footprint "eagle-import:DO-214AC")
      (fields (field (name "MPN") "1N4007"))
      (libsource (lib "eagle-import") (part "DIODE-GEN-PURPOSE-1KV-1A(DO-214AC)"))
    )
    (comp (ref "D607")
      (value "1N5817")
      (footprint "eagle-import:DO-214AC_SLIM")
      (libsource (lib "eagle-import") (part "DIODE-GEN-PURPOSE-1KV-1A(DO-214AC)DO-214AC/1206"))
    )
    (comp (ref "D608")
      (value "1N5817.")
      (footprint "eagle-import:DO-214AC_SLIM")
      (libsource (lib "eagle-import") (part "DIODE-GEN-PURPOSE-1KV-1A(DO-214AC)DO-214AC/1206"))
    )
    (comp (ref "D609")
      (value "1N5817.")
      (footprint "eagle-import:DO-214AC_SLIM")
      (libsource (lib "eagle-import") (part "DIODE-GEN-PURPOSE-1KV-1A(DO-214AC)DO-214AC/1206"))
    )
    (comp (ref "D610")
      (value "1N5817")
      (footprint "eagle-import:DO-214AC_SLIM")
      (libsource (lib "eagle-import") (part "DIODE-GEN-PURPOSE-1KV-1A(DO-214AC)DO-214AC/1206"))
    )
    (comp (ref "D611")
      (value "1N4007")
      (footprint "eagle-import:DO-214AC")
      (libsource (lib "eagle-import") (part "DIODE-GEN-PURPOSE-1KV-1A(DO-214AC)"))
    )
    (comp (ref "D612")
      (value "1N4007")
      (footprint "eagle-import:DO-214AC")
      (libsource (lib "eagle-import") (part "DIODE-GEN-PURPOSE-1KV-1A(DO-214AC)"))
    )
    (comp (ref "FID601")
      (value "FIDUCIAL")
      (footprint "eagle-import:FIDUCIAL_1MM")
      (libsource (lib "eagle-import") (part "FIDUCIAL"))
    )
    (comp (ref "FID602")
      (value "FIDUCIAL")
      (footprint "eagle-import:FIDUCIAL_1MM")
      (libsource (lib "eagle-import") (part "FIDUCIAL"))
    )
    (comp (ref "FID603")
      (value "FIDUCIAL")
      (footprint "eagle-import:FIDUCIAL_1MM")
      (libsource (lib "eagle-import") (part "FIDUCIAL"))
    )
    (comp (ref "FID604")
      (value "FIDUCIAL")
      (footprint "eagle-import:FIDUCIAL_1MM")
      (libsource (lib "eagle-import") (part "FIDUCIAL"))
    )
    (comp (ref "IC601")
      (value "LM2904")
      (footprint "eagle-import:SO08")
      (libsource (lib "eagle-import") (part "LM358D"))
    )
    (comp (ref "IC602")
      (value "78L06")
      (footprint "eagle-import:SOT89_ROUND")
      (libsource (lib "eagle-import") (part "78LXXSOT89_ROUND"))
    )
    (comp (ref "IC603")
      (value "6V pos")
      (footprint "eagle-import:78LXX")
      (libsource (lib "eagle-import") (part "v-reg_78LXX"))
    )
    (comp (ref "IC604")
      (value "78L10")
      (footprint "eagle-import:SOT89_ROUND")
      (libsource (lib "eagle-import") (part "78LXXSOT89_ROUND"))
    )
    (comp (ref "IC605")
      (value "4028")
      (footprint "eagle-import:SO16")
      (libsource (lib "eagle-import") (part "4028D"))
    )
    (comp (ref "IC606")
      (value "NUP4304SOT457_R")
      (footprint "eagle-import:SOT457R_PHILIPS")
      (libsource (lib "eagle-import") (part "NUP4304SOT457_R"))
    )
    (comp (ref "IC607")
      (value "ULN2004")
      (footprint "eagle-import:SO16")
      (libsource (lib "eagle-import") (part "ULN2004AD"))
    )
    (comp (ref "IC608")
      (value "LM339")
      (footprint "eagle-import:SO14")
      (libsource (lib "eagle-import") (part "LM339D"))
    )
    (comp (ref "IC609")
      (value "317TO202H_NOHOLE")
      (footprint "eagle-import:TO220H_NOHOLE")
      (libsource (lib "eagle-import") (part "317TO202H_NOHOLE"))
    )
    (comp (ref "IC610")
      (value "555")
      (footprint "eagle-import:SO08")
      (libsource (lib "eagle-import") (part "555DNE"))
    )
    (comp (ref "IC611")
      (value "4538")
      (footprint "eagle-import:SO16")
      (libsource (lib "eagle-import") (part "4538D"))
    )
    (comp (ref "JP601")
      (value "JP2EJP2_SMALLPADS")
      (footprint "eagle-import:JP2_SMALLPADS")
      (libsource (lib "eagle-import") (part "JP2EJP2_SMALLPADS"))
    )
    (comp (ref "JP602")
      (value "JP2EJP2_SMALLPADS")
      (footprint "eagle-import:JP2_SMALLPADS")
      (libsource (lib "eagle-import") (part "JP2EJP2_SMALLPADS"))
    )
    (comp (ref "JP603")
      (value "JP2EJP2_SMALLPADS")
      (footprint "eagle-import:JP2_SMALLPADS")
      (libsource (lib "eagle-import") (part "JP2EJP2_SMALLPADS"))
    )
    (comp (ref "JP604")
      (value "JP2EJP2_SMALLPADS")
      (footprint "eagle-import:JP2_SMALLPADS")
      (libsource (lib "eagle-import") (part "JP2EJP2_SMALLPADS"))
    )
    (comp (ref "JP605")
      (value "JP2E_ORIG")
      (footprint "eagle-import:JP2_ORIG_SMALLPADS")
      (libsource (lib "eagle-import") (part "JP2E_ORIG"))
    )
    (comp (ref "LED601")
      (value "LEDLD260")
      (footprint "eagle-import:LD260")
      (libsource (lib "eagle-import") (part "LEDLD260"))
    )
    (comp (ref "LED602")
      (value "LEDLD260")
      (footprint "eagle-import:LD260")
      (libsource (lib "eagle-import") (part "LEDLD260"))
    )
    (comp (ref "LED603")
      (value "LEDLD260")
      (footprint "eagle-import:LD260")
      (libsource (lib "eagle-import") (part "LEDLD260"))
    )
    (comp (ref "LED604")
      (value "LEDLD260")
      (footprint "eagle-import:LD260")
      (libsource (lib "eagle-import") (part "LEDLD260"))
    )
    (comp (ref "LED605")
      (value "LEDLD260")
      (footprint "eagle-import:LD260")
      (libsource (lib "eagle-import") (part "LEDLD260"))
    )
    (comp (ref "LED606")
      (value "LEDLD260")
      (footprint "eagle-import:LD260")
      (libsource (lib "eagle-import") (part "LEDLD260"))
    )
    (comp (ref "Q601")
      (value "BA.")
      (footprint "eagle-import:SOT89")
      (libsource (lib "eagle-import") (part "PNP-TRANSISTOR_SOT89"))
    )
    (comp (ref "Q602")
      (value "BA.")
      (footprint "eagle-import:SOT89")
      (libsource (lib "eagle-import") (part "PNP-TRANSISTOR_SOT89"))
    )
    (comp (ref "Q603")
      (value "MY")
      (footprint "eagle-import:SOT89")
      (libsource (lib "eagle-import") (part "NPN-TRANSISTOR_SOT89"))
    )
    (comp (ref "Q604")
      (value "BA")
      (footprint "eagle-import:SOT89")
      (libsource (lib "eagle-import") (part "PNP-TRANSISTOR_SOT89"))
    )
    (comp (ref "Q605")
      (value "BA")
      (footprint "eagle-import:SOT89")
      (libsource (lib "eagle-import") (part "PNP-TRANSISTOR_SOT89"))
    )
    (comp (ref "Q606")
      (value "J1")
      (footprint "eagle-import:SOT-23")
      (fields (field (name "MPN") "BSS138W-7-F"))
      (libsource (lib "eagle-import") (part "SMD-MOSFET-N-CH-50V-200MA-BSS138W-7-F(SOT-23)"))
    )
    (comp (ref "Q607")
      (value "J1")
      (footprint "eagle-import:SOT-23")
      (fields (field (name "MPN") "BSS138W-7-F"))
      (libsource (lib "eagle-import") (part "SMD-MOSFET-N-CH-50V-200MA-BSS138W-7-F(SOT-23)"))
    )
    (comp (ref "R601")
      (value "102")
      (footprint "eagle-import:R0805")
      (fields (field (name "MPN") "RC0805JR-071KL"))
      (libsource (lib "eagle-import") (part "SMD-RES-1K-5%-1/8W(0805)"))
    )
    (comp (ref "R602")
      (value "13")
      (footprint "eagle-import:R1206")
      (fields (field (name "MPN") "RC1206JR-0713RL"))
      (libsource (lib "eagle-import") (part "SMD-RES-13R-5%-1/4W(1206)"))
    )
    (comp (ref "R603")
      (value "R_user")
      (footprint "eagle-import:R0805")
      (libsource (lib "eagle-import") (part "R-EU_R0805"))
    )
    (comp (ref "R604")
      (value "R_user")
      (footprint "eagle-import:R0805")
      (libsource (lib "eagle-import") (part "R-EU_R0805"))
    )
    (comp (ref "R605")
      (value "4701")
      (footprint "eagle-import:R0805")
      (fields (field (name "MPN") "RC0805JR-074K7L"))
      (libsource (lib "eagle-import") (part "SMD-RES-4.7K-5%-1/8W(0805)"))
    )
    (comp (ref "R606")
      (value "13")
      (footprint "eagle-import:R1206")
      (fields (field (name "MPN") "RC1206JR-0713RL"))
      (libsource (lib "eagle-import") (part "SMD-RES-13R-5%-1/4W(1206)"))
    )
    (comp (ref "R607")
      (value "1002")
      (footprint "eagle-import:R0805")
      (fields (field (name "MPN") "RC0805FR-0710KL"))
      (libsource (lib "eagle-import") (part "SMD-RES-10K-1%-1/8W(0805)"))
    )
    (comp (ref "R608")
      (value "1002")
      (footprint "eagle-import:R0805")
      (fields (field (name "MPN") "RC0805FR-0710KL"))
      (libsource (lib "eagle-import") (part "SMD-RES-10K-1%-1/8W(0805)"))
    )
    (comp (ref "R609")
      (value "104.")
      (footprint "eagle-import:R0805")
      (fields (field (name "MPN") "RC0805FR-0710KL"))
      (libsource (lib "eagle-import") (part "SMD-RES-10K-1%-1/8W(0805)"))
    )
    (comp (ref "R610")
      (value "104.")
      (footprint "eagle-import:R0805")
      (fields (field (name "MPN") "RC0805FR-0710KL"))
      (libsource (lib "eagle-import") (part "SMD-RES-10K-1%-1/8W(0805)"))
    )
    (comp (ref "R611")
      (value "104.")
      (footprint "eagle-import:R0805")
      (fields (field (name "MPN") "RC0805FR-0710KL"))
      (libsource (lib "eagle-import") (part "SMD-RES-10K-1%-1/8W(0805)"))
    )
    (comp (ref "R612")
      (value "102")
      (footprint "eagle-import:R0805")
      (fields (field (name "MPN") "RC0805JR-071KL"))
      (libsource (lib "eagle-import") (part "SMD-RES-1K-5%-1/8W(0805)"))
    )
    (comp (ref "R613")
      (value "102")
      (footprint "eagle-import:R0805")
      (fields (field (name "MPN") "RC0805JR-071KL"))
      (libsource (lib "eagle-import") (part "SMD-RES-1K-5%-1/8W(0805)"))
    )
    (comp (ref "R614")
      (value "102")
      (footprint "eagle-import:R0805")
      (fields (field (name "MPN") "RC0805JR-071KL"))
      (libsource (lib "eagle-import") (part "SMD-RES-1K-5%-1/8W(0805)"))
    )
    (comp (ref "R615")
      (value "100")
      (footprint "eagle-import:R0805")
      (fields (field (name "MPN") "RC0805JR-07220RL"))
      (libsource (lib "eagle-import") (part "SMD-RES-220R-5%-1/8W(0805)"))
    )
    (comp (ref "R616")
      (value "4701")
      (footprint "eagle-import:R0805")
      (fields (field (name "MPN") "RC0805JR-074K7L"))
      (libsource (lib "eagle-import") (part "SMD-RES-4.7K-5%-1/8W(0805)"))
    )
    (comp (ref "R617")
      (value "2702")
      (footprint "eagle-import:R0805")
      (fields (field (name "MPN") "RC0805JR-074K7L"))
      (libsource (lib "eagle-import") (part "SMD-RES-4.7K-5%-1/8W(0805)"))
    )
    (comp (ref "R618")
      (value "13")
      (footprint "eagle-import:R1206")
      (fields (field (name "MPN") "RC1206JR-0713RL"))
      (libsource (lib "eagle-import") (part "SMD-RES-13R-5%-1/4W(1206)"))
    )
    (comp (ref "R619")
      (value "2201")
      (footprint "eagle-import:R0805")
      (fields (field (name "MPN") "RC0805JR-072K2L"))
      (libsource (lib "eagle-import") (part "SMD-RES-2.2K-5%-1/8W(0805)"))
    )
    (comp (ref "R620")
      (value "1002")
      (footprint "eagle-import:R0805")
      (fields (field (name "MPN") "RC0805FR-0710KL"))
      (libsource (lib "eagle-import") (part "SMD-RES-10K-1%-1/8W(0805)"))
    )
    (comp (ref "R621")
      (value "1502")
      (footprint "eagle-import:R0805")
      (fields (field (name "MPN") "RC0805FR-0710KL"))
      (libsource (lib "eagle-import") (part "SMD-RES-10K-1%-1/8W(0805)"))
    )
    (comp (ref "R622")
      (value "2702")
      (footprint "eagle-import:R0805")
      (fields (field (name "MPN") "RC0805JR-074K7L"))
      (libsource (lib "eagle-import") (part "SMD-RES-4.7K-5%-1/8W(0805)"))
    )
    (comp (ref "R623")
      (value "2702")
      (footprint "eagle-import:R0805")
      (fields (field (name "MPN") "RC0805JR-074K7L"))
      (libsource (lib "eagle-import") (part "SMD-RES-4.7K-5%-1/8W(0805)"))
    )
    (comp (ref "R624")
      (value "1002")
      (footprint "eagle-import:R0805")
      (fields (field (name "MPN") "RC0805FR-0710KL"))
      (libsource (lib "eagle-import") (part "SMD-RES-10K-1%-1/8W(0805)"))
    )
    (comp (ref "R625")
      (value "104")
      (footprint "eagle-import:R0805")
      (fields (field (name "MPN") "RC0805FR-0710KL"))
      (libsource (lib "eagle-import") (part "SMD-RES-10K-1%-1/8W(0805)"))
    )
    (comp (ref "R626")
      (value "4701")
      (footprint "eagle-import:R0805")
      (fields (field (name "MPN") "RC0805JR-074K7L"))
      (libsource (lib "eagle-import") (part "SMD-RES-4.7K-5%-1/8W(0805)"))
    )
    (comp (ref "R627")
      (value "47")
      (footprint "eagle-import:V235_17_1MM")
      (libsource (lib "eagle-import") (part "R-EU_V235/17_1MM"))
    )
    (comp (ref "R628")
      (value "102")
      (footprint "eagle-import:R0805")
      (fields (field (name "MPN") "RC0805JR-071KL"))
      (libsource (lib "eagle-import") (part "SMD-RES-1K-5%-1/8W(0805)"))
    )
    (comp (ref "R629")
      (value "47")
      (footprint "eagle-import:V235_17_1MM")
      (libsource (lib "eagle-import") (part "R-EU_V235/17_1MM"))
    )
    (comp (ref "R630")
      (value "104")
      (footprint "eagle-import:R0805")
      (fields (field (name "MPN") "RC0805FR-0710KL"))
      (libsource (lib "eagle-import") (part "SMD-RES-10K-1%-1/8W(0805)"))
    )
    (comp (ref "R631")
      (value "1502")
      (footprint "eagle-import:R0805")
      (fields (field (name "MPN") "RC0805FR-0710KL"))
      (libsource (lib "eagle-import") (part "SMD-RES-10K-1%-1/8W(0805)"))
    )
    (comp (ref "R632")
      (value "1002")
      (footprint "eagle-import:R0805")
      (fields (field (name "MPN") "RC0805FR-0710KL"))
      (libsource (lib "eagle-import") (part "SMD-RES-10K-1%-1/8W(0805)"))
    )
    (comp (ref "R633")
      (value "2201")
      (footprint "eagle-import:R0805")
      (fields (field (name "MPN") "RC0805JR-072K2L"))
      (libsource (lib "eagle-import") (part "SMD-RES-2.2K-5%-1/8W(0805)"))
    )
    (comp (ref "R634")
      (value "13")
      (footprint "eagle-import:R1206")
      (fields (field (name "MPN") "RC1206JR-0713RL"))
      (libsource (lib "eagle-import") (part "SMD-RES-13R-5%-1/4W(1206)"))
    )
    (comp (ref "R635")
      (value "104")
      (footprint "eagle-import:R0805")
      (fields (field (name "MPN") "RC0805FR-0710KL"))
      (libsource (lib "eagle-import") (part "SMD-RES-10K-1%-1/8W(0805)"))
    )
    (comp (ref "R636")
      (value "47")
      (footprint "eagle-import:V235_17_1MM")
      (libsource (lib "eagle-import") (part "R-EU_V235/17_1MM"))
    )
    (comp (ref "R637")
      (value "47")
      (footprint "eagle-import:V235_17_1MM")
      (libsource (lib "eagle-import") (part "R-EU_V235/17_1MM"))
    )
    (comp (ref "R638")
      (value "100")
      (footprint "eagle-import:R0805")
      (fields (field (name "MPN") "RC0805JR-072K2L"))
      (libsource (lib "eagle-import") (part "SMD-RES-2.2K-5%-1/8W(0805)"))
    )
    (comp (ref "R639")
      (value "(101)")
      (footprint "eagle-import:R0805")
      (fields (field (name "MPN") "RC0805JR-072K2L"))
      (libsource (lib "eagle-import") (part "SMD-RES-2.2K-5%-1/8W(0805)"))
    )
    (comp (ref "R640")
      (value "2702")
      (footprint "eagle-import:R0805")
      (fields (field (name "MPN") "RC0805FR-0710KL"))
      (libsource (lib "eagle-import") (part "SMD-RES-10K-1%-1/8W(0805)"))
    )
    (comp (ref "R641")
      (value "104")
      (footprint "eagle-import:R0805")
      (fields (field (name "MPN") "RC0805FR-0710KL"))
      (libsource (lib "eagle-import") (part "SMD-RES-10K-1%-1/8W(0805)"))
    )
    (comp (ref "R642")
      (value "(1000)")
      (footprint "eagle-import:R0805")
      (fields (field (name "MPN") "RC0805JR-07100RL"))
      (libsource (lib "eagle-import") (part "SMD-RES-100R-5%-1/8W(0805)"))
    )
    (comp (ref "R643")
      (value "(101)")
      (footprint "eagle-import:R0805")
      (fields (field (name "MPN") "RC0805JR-07100RL"))
      (libsource (lib "eagle-import") (part "SMD-RES-100R-5%-1/8W(0805)"))
    )
    (comp (ref "R644")
      (value "(1002)")
      (footprint "eagle-import:R0805")
      (fields (field (name "MPN") "RC0805FR-0710KL"))
      (libsource (lib "eagle-import") (part "SMD-RES-10K-1%-1/8W(0805)"))
    )
    (comp (ref "R645")
      (value "2702")
      (footprint "eagle-import:R0805")
      (fields (field (name "MPN") "RC0805JR-074K7L"))
      (libsource (lib "eagle-import") (part "SMD-RES-4.7K-5%-1/8W(0805)"))
    )
    (comp (ref "R646")
      (value "(1002)")
      (footprint "eagle-import:R0805")
      (fields (field (name "MPN") "RC0805JR-074K7L"))
      (libsource (lib "eagle-import") (part "SMD-RES-4.7K-5%-1/8W(0805)"))
    )
    (comp (ref "SJ601")
      (value "SJ")
      (footprint "eagle-import:SJ")
      (libsource (lib "eagle-import") (part "SJ"))
    )
    (comp (ref "START601")
      (value "TPSB2.0")
      (footprint "eagle-import:B2.0")
      (libsource (lib "eagle-import") (part "TPSB2.0"))
    )
    (comp (ref "TP116")
      (value "TPSB2.0")
      (footprint "eagle-import:B2.0")
      (libsource (lib "eagle-import") (part "TPSB2.0"))
    )
    (comp (ref "TP117")
      (value "TPSB2.0")
      (footprint "eagle-import:B2.0")
      (libsource (lib "eagle-import") (part "TPSB2.0"))
    )
    (comp (ref "TP118")
      (value "TPSB2.0")
      (footprint "eagle-import:B2.0")
      (libsource (lib "eagle-import") (part "TPSB2.0"))
    )
    (comp (ref "TP119")
      (value "TPSB2.0")
      (footprint "eagle-import:B2.0")
      (libsource (lib "eagle-import") (part "TPSB2.0"))
    )
    (comp (ref "TP120")
      (value "TPSB2.0")
      (footprint "eagle-import:B2.0")
      (libsource (lib "eagle-import") (part "TPSB2.0"))
    )
    (comp (ref "TP121")
      (value "TPSB2.0")
      (footprint "eagle-import:B2.0")
      (libsource (lib "eagle-import") (part "TPSB2.0"))
    )
    (comp (ref "TP122")
      (value "TPSB2.0")
      (footprint "eagle-import:B2.0")
      (libsource (lib "eagle-import") (part "TPSB2.0"))
    )
    (comp (ref "TP123")
      (value "TPSB2.0")
      (footprint "eagle-import:B2.0")
      (libsource (lib "eagle-import") (part "TPSB2.0"))
    )
    (comp (ref "TP124")
      (value "TPSB2.0")
      (footprint "eagle-import:B2.0")
      (libsource (lib "eagle-import") (part "TPSB2.0"))
    )
    (comp (ref "TP125")
      (value "TPSB2.0")
      (footprint "eagle-import:B2.0")
      (libsource (lib "eagle-import") (part "TPSB2.0"))
    )
    (comp (ref "TP126")
      (value "TPSB2.0")
      (footprint "eagle-import:B2.0")
      (libsource (lib "eagle-import") (part "TPSB2.0"))
    )
    (comp (ref "TP127")
      (value "TPSB2.0")
      (footprint "eagle-import:B2.0")
      (libsource (lib "eagle-import") (part "TPSB2.0"))
    )
    (comp (ref "TP128")
      (value "TPSB2.0")
      (footprint "eagle-import:B2.0")
      (libsource (lib "eagle-import") (part "TPSB2.0"))
    )
    (comp (ref "TP129")
      (value "TPSB2.0")
      (footprint "eagle-import:B2.0")
      (libsource (lib "eagle-import") (part "TPSB2.0"))
    )
    (comp (ref "TP130")
      (value "TPSB2.0")
      (footprint "eagle-import:B2.0")
      (libsource (lib "eagle-import") (part "TPSB2.0"))
    )
    (comp (ref "TP131")
      (value "TPSB2.0")
      (footprint "eagle-import:B2.0")
      (libsource (lib "eagle-import") (part "TPSB2.0"))
    )
    (comp (ref "TP132")
      (value "TPSB2.0")
      (footprint "eagle-import:B2.0")
      (libsource (lib "eagle-import") (part "TPSB2.0"))
    )
    (comp (ref "TP133")
      (value "TPSB2.0")
      (footprint "eagle-import:B2.0")
      (libsource (lib "eagle-import") (part "TPSB2.0"))
    )
    (comp (ref "TP134")
      (value "TPSB1,27")
      (footprint "eagle-import:B1,27")
      (libsource (lib "eagle-import") (part "TPSB1,27"))
    )
    (comp (ref "TP135")
      (value "TPSB2.0")
      (footprint "eagle-import:B2.0")
      (libsource (lib "eagle-import") (part "TPSB2.0"))
    )
    (comp (ref "TP136")
      (value "TPSB2.0")
      (footprint "eagle-import:B2.0")
      (libsource (lib "eagle-import") (part "TPSB2.0"))
    )
    (comp (ref "TP137")
      (value "TPSB2.0")
      (footprint "eagle-import:B2.0")
      (libsource (lib "eagle-import") (part "TPSB2.0"))
    )
    (comp (ref "TP138")
      (value "TPSB2.0")
      (footprint "eagle-import:B2.0")
      (libsource (lib "eagle-import") (part "TPSB2.0"))
    )
    (comp (ref "X601")
      (value "CON_BMWV2")
      (footprint "eagle-import:24-PIN_V2")
      (libsource (lib "eagle-import") (part "CON_BMWV2"))
    )
    (comp (ref "X602")
      (value "22-23-2021")
      (footprint "eagle-import:22-23-2021")
      (fields (field (name "MF") "MOLEX"))
      (libsource (lib "eagle-import") (part "22-23-2021"))
    )
    (comp (ref "X603")
      (value "22-23-2051")
      (footprint "eagle-import:22-23-2051")
      (fields (field (name "MF") "MOLEX"))
      (libsource (lib "eagle-import") (part "22-23-2051"))
    )
    (comp (ref "3")
      (value "2081-1132")
      (footprint "eagle-import:12-PIN")
      (libsource (lib "eagle-import") (part "2081-1132"))
    )
    (comp (ref "4")
      (value "2081-1132")
      (footprint "eagle-import:12-PIN")
      (libsource (lib "eagle-import") (part "2081-1132"))
    )
    (comp (ref "6V201")
      (value "TPSB2.0")
      (footprint "eagle-import:B2.0")
      (libsource (lib "eagle-import") (part "TPSB2.0"))
    )
    (comp (ref "10V201")
      (value "TPSB2.0")
      (footprint "eagle-import:B2.0")
      (libsource (lib "eagle-import") (part "TPSB2.0"))
    )
    (comp (ref "C201")
      (value "4.7u")
      (footprint "eagle-import:C0805")
      (fields (field (name "MPN") "CC0805KKX5R8BB475"))
      (libsource (lib "eagle-import") (part "CERAMIC-4.7UF-25V-10%-X5R(0805)"))
    )
    (comp (ref "C202")
      (value "100nF")
      (footprint "eagle-import:C0805")
      (fields (field (name "MPN") "CC0805KRX7R9BB104"))
      (libsource (lib "eagle-import") (part "CERAMIC-100NF-50V-10%-X7R(0805)"))
    )
    (comp (ref "C203")
      (value "100nF,")
      (footprint "eagle-import:C0805")
      (fields (field (name "MPN") "CC0805KRX7R9BB104"))
      (libsource (lib "eagle-import") (part "CERAMIC-100NF-50V-10%-X7R(0805)"))
    )
    (comp (ref "C204")
      (value "100nF,")
      (footprint "eagle-import:C0805")
      (fields (field (name "MPN") "CC0805KRX7R9BB104"))
      (libsource (lib "eagle-import") (part "CERAMIC-100NF-50V-10%-X7R(0805)"))
    )
    (comp (ref "C205")
      (value "100nF.")
      (footprint "eagle-import:C0805")
      (fields (field (name "MPN") "CC0805KRX7R9BB104"))
      (libsource (lib "eagle-import") (part "CERAMIC-100NF-50V-10%-X7R(0805)"))
    )
    (comp (ref "C206")
      (value "100nF.")
      (footprint "eagle-import:C0805")
      (fields (field (name "MPN") "CC0805KRX7R9BB104"))
      (libsource (lib "eagle-import") (part "CERAMIC-100NF-50V-10%-X7R(0805)"))
    )
    (comp (ref "C207")
      (value "100u")
      (footprint "eagle-import:C1206")
      (fields (field (name "MPN") "GRM31CR60J107ME39L"))
      (libsource (lib "eagle-import") (part "CERAMIC-100UF-6.3V-20%-X5R(1206)"))
    )
    (comp (ref "C208")
      (value "100u")
      (footprint "eagle-import:C1206")
      (fields (field (name "MPN") "GRM31CR60J107ME39L"))
      (libsource (lib "eagle-import") (part "CERAMIC-100UF-6.3V-20%-X5R(1206)"))
    )
    (comp (ref "C209")
      (value "2.2nF")
      (footprint "eagle-import:C0805")
      (fields (field (name "MPN") "CC0805KRX7R9BB104"))
      (libsource (lib "eagle-import") (part "CERAMIC-100NF-50V-10%-X7R(0805)"))
    )
    (comp (ref "C210")
      (value "100nF")
      (footprint "eagle-import:C0805")
      (fields (field (name "MPN") "CC0805KRX7R9BB104"))
      (libsource (lib "eagle-import") (part "CERAMIC-100NF-50V-10%-X7R(0805)"))
    )
    (comp (ref "D201")
      (value "SM6T")
      (footprint "eagle-import:DO214AA")
      (libsource (lib "eagle-import") (part "SM6T"))
    )
    (comp (ref "D202")
      (value "1N4007,")
      (footprint "eagle-import:DO-214AC")
      (fields (field (name "MPN") "1N4007"))
      (libsource (lib "eagle-import") (part "DIODE-GEN-PURPOSE-1KV-1A(DO-214AC)"))
    )
    (comp (ref "D203")
      (value "1N4007,")
      (footprint "eagle-import:DO-214AC")
      (fields (field (name "MPN") "1N4007"))
      (libsource (lib "eagle-import") (part "DIODE-GEN-PURPOSE-1KV-1A(DO-214AC)"))
    )
    (comp (ref "D204")
      (value "SM6TDO214AA_BI")
      (footprint "eagle-import:DO214AA_BI")
      (libsource (lib "eagle-import") (part "SM6TDO214AA_BI"))
    )
    (comp (ref "D205")
      (value "1N4007.")
      (footprint "eagle-import:DO-214AC")
      (fields (field (name "MPN") "1N4007"))
      (libsource (lib "eagle-import") (part "DIODE-GEN-PURPOSE-1KV-1A(DO-214AC)"))
    )
    (comp (ref "D206")
      (value "1N4007.")
      (footprint "eagle-import:DO-214AC")
      (fields (field (name "MPN") "1N4007"))
      (libsource (lib "eagle-import") (part "DIODE-GEN-PURPOSE-1KV-1A(DO-214AC)"))
    )
    (comp (ref "D207")
      (value "1N5817")
      (footprint "eagle-import:DO-214AC_SLIM")
      (libsource (lib "eagle-import") (part "DIODE-GEN-PURPOSE-1KV-1A(DO-214AC)DO-214AC/1206"))
    )
    (comp (ref "D208")
      (value "1N5817.")
      (footprint "eagle-import:DO-214AC_SLIM")
      (libsource (lib "eagle-import") (part "DIODE-GEN-PURPOSE-1KV-1A(DO-214AC)DO-214AC/1206"))
    )
    (comp (ref "D209")
      (value "1N5817.")
      (footprint "eagle-import:DO-214AC_SLIM")
      (libsource (lib "eagle-import") (part "DIODE-GEN-PURPOSE-1KV-1A(DO-214AC)DO-214AC/1206"))
    )
    (comp (ref "D210")
      (value "1N5817")
      (footprint "eagle-import:DO-214AC_SLIM")
      (libsource (lib "eagle-import") (part "DIODE-GEN-PURPOSE-1KV-1A(DO-214AC)DO-214AC/1206"))
    )
    (comp (ref "D211")
      (value "1N4007")
      (footprint "eagle-import:DO-214AC")
      (libsource (lib "eagle-import") (part "DIODE-GEN-PURPOSE-1KV-1A(DO-214AC)"))
    )
    (comp (ref "D212")
      (value "1N4007")
      (footprint "eagle-import:DO-214AC")
      (libsource (lib "eagle-import") (part "DIODE-GEN-PURPOSE-1KV-1A(DO-214AC)"))
    )
    (comp (ref "FID201")
      (value "FIDUCIAL")
      (footprint "eagle-import:FIDUCIAL_1MM")
      (libsource (lib "eagle-import") (part "FIDUCIAL"))
    )
    (comp (ref "FID202")
      (value "FIDUCIAL")
      (footprint "eagle-import:FIDUCIAL_1MM")
      (libsource (lib "eagle-import") (part "FIDUCIAL"))
    )
    (comp (ref "FID203")
      (value "FIDUCIAL")
      (footprint "eagle-import:FIDUCIAL_1MM")
      (libsource (lib "eagle-import") (part "FIDUCIAL"))
    )
    (comp (ref "FID204")
      (value "FIDUCIAL")
      (footprint "eagle-import:FIDUCIAL_1MM")
      (libsource (lib "eagle-import") (part "FIDUCIAL"))
    )
    (comp (ref "IC201")
      (value "LM2904")
      (footprint "eagle-import:SO08")
      (libsource (lib "eagle-import") (part "LM358D"))
    )
    (comp (ref "IC202")
      (value "78L06")
      (footprint "eagle-import:SOT89_ROUND")
      (libsource (lib "eagle-import") (part "78LXXSOT89_ROUND"))
    )
    (comp (ref "IC203")
      (value "6V pos")
      (footprint "eagle-import:78LXX")
      (libsource (lib "eagle-import") (part "v-reg_78LXX"))
    )
    (comp (ref "IC204")
      (value "78L10")
      (footprint "eagle-import:SOT89_ROUND")
      (libsource (lib "eagle-import") (part "78LXXSOT89_ROUND"))
    )
    (comp (ref "IC205")
      (value "4028")
      (footprint "eagle-import:SO16")
      (libsource (lib "eagle-import") (part "4028D"))
    )
    (comp (ref "IC206")
      (value "NUP4304SOT457_R")
      (footprint "eagle-import:SOT457R_PHILIPS")
      (libsource (lib "eagle-import") (part "NUP4304SOT457_R"))
    )
    (comp (ref "IC207")
      (value "ULN2004")
      (footprint "eagle-import:SO16")
      (libsource (lib "eagle-import") (part "ULN2004AD"))
    )
    (comp (ref "IC208")
      (value "LM339")
      (footprint "eagle-import:SO14")
      (libsource (lib "eagle-import") (part "LM339D"))
    )
    (comp (ref "IC209")
      (value "317TO202H_NOHOLE")
      (footprint "eagle-import:TO220H_NOHOLE")
      (libsource (lib "eagle-import") (part "317TO202H_NOHOLE"))
    )
    (comp (ref "IC210")
      (value "555")
      (footprint "eagle-import:SO08")
      (libsource (lib "eagle-import") (part "555DNE"))
    )
    (comp (ref "IC211")
      (value "4538")
      (footprint "eagle-import:SO16")
      (libsource (lib "eagle-import") (part "4538D"))
    )
    (comp (ref "JP201")
      (value "JP2EJP2_SMALLPADS")
      (footprint "eagle-import:JP2_SMALLPADS")
      (libsource (lib "eagle-import") (part "JP2EJP2_SMALLPADS"))
    )
    (comp (ref "JP202")
      (value "JP2EJP2_SMALLPADS")
      (footprint "eagle-import:JP2_SMALLPADS")
      (libsource (lib "eagle-import") (part "JP2EJP2_SMALLPADS"))
    )
    (comp (ref "JP203")
      (value "JP2EJP2_SMALLPADS")
      (footprint "eagle-import:JP2_SMALLPADS")
      (libsource (lib "eagle-import") (part "JP2EJP2_SMALLPADS"))
    )
    (comp (ref "JP204")
      (value "JP2EJP2_SMALLPADS")
      (footprint "eagle-import:JP2_SMALLPADS")
      (libsource (lib "eagle-import") (part "JP2EJP2_SMALLPADS"))
    )
    (comp (ref "JP205")
      (value "JP2E_ORIG")
      (footprint "eagle-import:JP2_ORIG_SMALLPADS")
      (libsource (lib "eagle-import") (part "JP2E_ORIG"))
    )
    (comp (ref "LED201")
      (value "LEDLD260")
      (footprint "eagle-import:LD260")
      (libsource (lib "eagle-import") (part "LEDLD260"))
    )
    (comp (ref "LED202")
      (value "LEDLD260")
      (footprint "eagle-import:LD260")
      (libsource (lib "eagle-import") (part "LEDLD260"))
    )
    (comp (ref "LED203")
      (value "LEDLD260")
      (footprint "eagle-import:LD260")
      (libsource (lib "eagle-import") (part "LEDLD260"))
    )
    (comp (ref "LED204")
      (value "LEDLD260")
      (footprint "eagle-import:LD260")
      (libsource (lib "eagle-import") (part "LEDLD260"))
    )
    (comp (ref "LED205")
      (value "LEDLD260")
      (footprint "eagle-import:LD260")
      (libsource (lib "eagle-import") (part "LEDLD260"))
    )
    (comp (ref "LED206")
      (value "LEDLD260")
      (footprint "eagle-import:LD260")
      (libsource (lib "eagle-import") (part "LEDLD260"))
    )
    (comp (ref "Q201")
      (value "BA.")
      (footprint "eagle-import:SOT89")
      (libsource (lib "eagle-import") (part "PNP-TRANSISTOR_SOT89"))
    )
    (comp (ref "Q202")
      (value "BA.")
      (footprint "eagle-import:SOT89")
      (libsource (lib "eagle-import") (part "PNP-TRANSISTOR_SOT89"))
    )
    (comp (ref "Q203")
      (value "MY")
      (footprint "eagle-import:SOT89")
      (libsource (lib "eagle-import") (part "NPN-TRANSISTOR_SOT89"))
    )
    (comp (ref "Q204")
      (value "BA")
      (footprint "eagle-import:SOT89")
      (libsource (lib "eagle-import") (part "PNP-TRANSISTOR_SOT89"))
    )
    (comp (ref "Q205")
      (value "BA")
      (footprint "eagle-import:SOT89")
      (libsource (lib "eagle-import") (part "PNP-TRANSISTOR_SOT89"))
    )
    (comp (ref "Q206")
      (value "J1")
      (footprint "eagle-import:SOT-23")
      (fields (field (name "MPN") "BSS138W-7-F"))
      (libsource (lib "eagle-import") (part "SMD-MOSFET-N-CH-50V-200MA-BSS138W-7-F(SOT-23)"))
    )
    (comp (ref "Q207")
      (value "J1")
      (footprint "eagle-import:SOT-23")
      (fields (field (name "MPN") "BSS138W-7-F"))
      (libsource (lib "eagle-import") (part "SMD-MOSFET-N-CH-50V-200MA-BSS138W-7-F(SOT-23)"))
    )
    (comp (ref "R201")
      (value "102")
      (footprint "eagle-import:R0805")
      (fields (field (name "MPN") "RC0805JR-071KL"))
      (libsource (lib "eagle-import") (part "SMD-RES-1K-5%-1/8W(0805)"))
    )
    (comp (ref "R202")
      (value "13")
      (footprint "eagle-import:R1206")
      (fields (field (name "MPN") "RC1206JR-0713RL"))
      (libsource (lib "eagle-import") (part "SMD-RES-13R-5%-1/4W(1206)"))
    )
    (comp (ref "R203")
      (value "R_user")
      (footprint "eagle-import:R0805")
      (libsource (lib "eagle-import") (part "R-EU_R0805"))
    )
    (comp (ref "R204")
      (value "R_user")
      (footprint "eagle-import:R0805")
      (libsource (lib "eagle-import") (part "R-EU_R0805"))
    )
    (comp (ref "R205")
      (value "4701")
      (footprint "eagle-import:R0805")
      (fields (field (name "MPN") "RC0805JR-074K7L"))
      (libsource (lib "eagle-import") (part "SMD-RES-4.7K-5%-1/8W(0805)"))
    )
    (comp (ref "R206")
      (value "13")
      (footprint "eagle-import:R1206")
      (fields (field (name "MPN") "RC1206JR-0713RL"))
      (libsource (lib "eagle-import") (part "SMD-RES-13R-5%-1/4W(1206)"))
    )
    (comp (ref "R207")
      (value "1002")
      (footprint "eagle-import:R0805")
      (fields (field (name "MPN") "RC0805FR-0710KL"))
      (libsource (lib "eagle-import") (part "SMD-RES-10K-1%-1/8W(0805)"))
    )
    (comp (ref "R208")
      (value "1002")
      (footprint "eagle-import:R0805")
      (fields (field (name "MPN") "RC0805FR-0710KL"))
      (libsource (lib "eagle-import") (part "SMD-RES-10K-1%-1/8W(0805)"))
    )
    (comp (ref "R209")
      (value "104.")
      (footprint "eagle-import:R0805")
      (fields (field (name "MPN") "RC0805FR-0710KL"))
      (libsource (lib "eagle-import") (part "SMD-RES-10K-1%-1/8W(0805)"))
    )
    (comp (ref "R210")
      (value "104.")
      (footprint "eagle-import:R0805")
      (fields (field (name "MPN") "RC0805FR-0710KL"))
      (libsource (lib "eagle-import") (part "SMD-RES-10K-1%-1/8W(0805)"))
    )
    (comp (ref "R211")
      (value "104.")
      (footprint "eagle-import:R0805")
      (fields (field (name "MPN") "RC0805FR-0710KL"))
      (libsource (lib "eagle-import") (part "SMD-RES-10K-1%-1/8W(0805)"))
    )
    (comp (ref "R212")
      (value "102")
      (footprint "eagle-import:R0805")
      (fields (field (name "MPN") "RC0805JR-071KL"))
      (libsource (lib "eagle-import") (part "SMD-RES-1K-5%-1/8W(0805)"))
    )
    (comp (ref "R213")
      (value "102")
      (footprint "eagle-import:R0805")
      (fields (field (name "MPN") "RC0805JR-071KL"))
      (libsource (lib "eagle-import") (part "SMD-RES-1K-5%-1/8W(0805)"))
    )
    (comp (ref "R214")
      (value "102")
      (footprint "eagle-import:R0805")
      (fields (field (name "MPN") "RC0805JR-071KL"))
      (libsource (lib "eagle-import") (part "SMD-RES-1K-5%-1/8W(0805)"))
    )
    (comp (ref "R215")
      (value "100")
      (footprint "eagle-import:R0805")
      (fields (field (name "MPN") "RC0805JR-07220RL"))
      (libsource (lib "eagle-import") (part "SMD-RES-220R-5%-1/8W(0805)"))
    )
    (comp (ref "R216")
      (value "4701")
      (footprint "eagle-import:R0805")
      (fields (field (name "MPN") "RC0805JR-074K7L"))
      (libsource (lib "eagle-import") (part "SMD-RES-4.7K-5%-1/8W(0805)"))
    )
    (comp (ref "R217")
      (value "2702")
      (footprint "eagle-import:R0805")
      (fields (field (name "MPN") "RC0805JR-074K7L"))
      (libsource (lib "eagle-import") (part "SMD-RES-4.7K-5%-1/8W(0805)"))
    )
    (comp (ref "R218")
      (value "13")
      (footprint "eagle-import:R1206")
      (fields (field (name "MPN") "RC1206JR-0713RL"))
      (libsource (lib "eagle-import") (part "SMD-RES-13R-5%-1/4W(1206)"))
    )
    (comp (ref "R219")
      (value "2201")
      (footprint "eagle-import:R0805")
      (fields (field (name "MPN") "RC0805JR-072K2L"))
      (libsource (lib "eagle-import") (part "SMD-RES-2.2K-5%-1/8W(0805)"))
    )
    (comp (ref "R220")
      (value "1002")
      (footprint "eagle-import:R0805")
      (fields (field (name "MPN") "RC0805FR-0710KL"))
      (libsource (lib "eagle-import") (part "SMD-RES-10K-1%-1/8W(0805)"))
    )
    (comp (ref "R221")
      (value "1502")
      (footprint "eagle-import:R0805")
      (fields (field (name "MPN") "RC0805FR-0710KL"))
      (libsource (lib "eagle-import") (part "SMD-RES-10K-1%-1/8W(0805)"))
    )
    (comp (ref "R222")
      (value "2702")
      (footprint "eagle-import:R0805")
      (fields (field (name "MPN") "RC0805JR-074K7L"))
      (libsource (lib "eagle-import") (part "SMD-RES-4.7K-5%-1/8W(0805)"))
    )
    (comp (ref "R223")
      (value "2702")
      (footprint "eagle-import:R0805")
      (fields (field (name "MPN") "RC0805JR-074K7L"))
      (libsource (lib "eagle-import") (part "SMD-RES-4.7K-5%-1/8W(0805)"))
    )
    (comp (ref "R224")
      (value "1002")
      (footprint "eagle-import:R0805")
      (fields (field (name "MPN") "RC0805FR-0710KL"))
      (libsource (lib "eagle-import") (part "SMD-RES-10K-1%-1/8W(0805)"))
    )
    (comp (ref "R225")
      (value "104")
      (footprint "eagle-import:R0805")
      (fields (field (name "MPN") "RC0805FR-0710KL"))
      (libsource (lib "eagle-import") (part "SMD-RES-10K-1%-1/8W(0805)"))
    )
    (comp (ref "R226")
      (value "4701")
      (footprint "eagle-import:R0805")
      (fields (field (name "MPN") "RC0805JR-074K7L"))
      (libsource (lib "eagle-import") (part "SMD-RES-4.7K-5%-1/8W(0805)"))
    )
    (comp (ref "R227")
      (value "47")
      (footprint "eagle-import:V235_17_1MM")
      (libsource (lib "eagle-import") (part "R-EU_V235/17_1MM"))
    )
    (comp (ref "R228")
      (value "102")
      (footprint "eagle-import:R0805")
      (fields (field (name "MPN") "RC0805JR-071KL"))
      (libsource (lib "eagle-import") (part "SMD-RES-1K-5%-1/8W(0805)"))
    )
    (comp (ref "R229")
      (value "47")
      (footprint "eagle-import:V235_17_1MM")
      (libsource (lib "eagle-import") (part "R-EU_V235/17_1MM"))
    )
    (comp (ref "R230")
      (value "104")
      (footprint "eagle-import:R0805")
      (fields (field (name "MPN") "RC0805FR-0710KL"))
      (libsource (lib "eagle-import") (part "SMD-RES-10K-1%-1/8W(0805)"))
    )
    (comp (ref "R231")
      (value "1502")
      (footprint "eagle-import:R0805")
      (fields (field (name "MPN") "RC0805FR-0710KL"))
      (libsource (lib "eagle-import") (part "SMD-RES-10K-1%-1/8W(0805)"))
    )
    (comp (ref "R232")
      (value "1002")
      (footprint "eagle-import:R0805")
      (fields (field (name "MPN") "RC0805FR-0710KL"))
      (libsource (lib "eagle-import") (part "SMD-RES-10K-1%-1/8W(0805)"))
    )
    (comp (ref "R233")
      (value "2201")
      (footprint "eagle-import:R0805")
      (fields (field (name "MPN") "RC0805JR-072K2L"))
      (libsource (lib "eagle-import") (part "SMD-RES-2.2K-5%-1/8W(0805)"))
    )
    (comp (ref "R234")
      (value "13")
      (footprint "eagle-import:R1206")
      (fields (field (name "MPN") "RC1206JR-0713RL"))
      (libsource (lib "eagle-import") (part "SMD-RES-13R-5%-1/4W(1206)"))
    )
    (comp (ref "R235")
      (value "104")
      (footprint "eagle-import:R0805")
      (fields (field (name "MPN") "RC0805FR-0710KL"))
      (libsource (lib "eagle-import") (part "SMD-RES-10K-1%-1/8W(0805)"))
    )
    (comp (ref "R236")
      (value "47")
      (footprint "eagle-import:V235_17_1MM")
      (libsource (lib "eagle-import") (part "R-EU_V235/17_1MM"))
    )
    (comp (ref "R237")
      (value "47")
      (footprint "eagle-import:V235_17_1MM")
      (libsource (lib "eagle-import") (part "R-EU_V235/17_1MM"))
    )
    (comp (ref "R238")
      (value "100")
      (footprint "eagle-import:R0805")
      (fields (field (name "MPN") "RC0805JR-072K2L"))
      (libsource (lib "eagle-import") (part "SMD-RES-2.2K-5%-1/8W(0805)"))
    )
    (comp (ref "R239")
      (value "(101)")
      (footprint "eagle-import:R0805")
      (fields (field (name "MPN") "RC0805JR-072K2L"))
      (libsource (lib "eagle-import") (part "SMD-RES-2.2K-5%-1/8W(0805)"))
    )
    (comp (ref "R240")
      (value "2702")
      (footprint "eagle-import:R0805")
      (fields (field (name "MPN") "RC0805FR-0710KL"))
      (libsource (lib "eagle-import") (part "SMD-RES-10K-1%-1/8W(0805)"))
    )
    (comp (ref "R241")
      (value "104")
      (footprint "eagle-import:R0805")
      (fields (field (name "MPN") "RC0805FR-0710KL"))
      (libsource (lib "eagle-import") (part "SMD-RES-10K-1%-1/8W(0805)"))
    )
    (comp (ref "R242")
      (value "(1000)")
      (footprint "eagle-import:R0805")
      (fields (field (name "MPN") "RC0805JR-07100RL"))
      (libsource (lib "eagle-import") (part "SMD-RES-100R-5%-1/8W(0805)"))
    )
    (comp (ref "R243")
      (value "(101)")
      (footprint "eagle-import:R0805")
      (fields (field (name "MPN") "RC0805JR-07100RL"))
      (libsource (lib "eagle-import") (part "SMD-RES-100R-5%-1/8W(0805)"))
    )
    (comp (ref "R244")
      (value "(1002)")
      (footprint "eagle-import:R0805")
      (fields (field (name "MPN") "RC0805FR-0710KL"))
      (libsource (lib "eagle-import") (part "SMD-RES-10K-1%-1/8W(0805)"))
    )
    (comp (ref "R245")
      (value "2702")
      (footprint "eagle-import:R0805")
      (fields (field (name "MPN") "RC0805JR-074K7L"))
      (libsource (lib "eagle-import") (part "SMD-RES-4.7K-5%-1/8W(0805)"))
    )
    (comp (ref "R246")
      (value "(1002)")
      (footprint "eagle-import:R0805")
      (fields (field (name "MPN") "RC0805JR-074K7L"))
      (libsource (lib "eagle-import") (part "SMD-RES-4.7K-5%-1/8W(0805)"))
    )
    (comp (ref "SJ201")
      (value "SJ")
      (footprint "eagle-import:SJ")
      (libsource (lib "eagle-import") (part "SJ"))
    )
    (comp (ref "START201")
      (value "TPSB2.0")
      (footprint "eagle-import:B2.0")
      (libsource (lib "eagle-import") (part "TPSB2.0"))
    )
    (comp (ref "TP14")
      (value "TPSB2.0")
      (footprint "eagle-import:B2.0")
      (libsource (lib "eagle-import") (part "TPSB2.0"))
    )
    (comp (ref "TP15")
      (value "TPSB2.0")
      (footprint "eagle-import:B2.0")
      (libsource (lib "eagle-import") (part "TPSB2.0"))
    )
    (comp (ref "TP20")
      (value "TPSB2.0")
      (footprint "eagle-import:B2.0")
      (libsource (lib "eagle-import") (part "TPSB2.0"))
    )
    (comp (ref "TP27")
      (value "TPSB2.0")
      (footprint "eagle-import:B2.0")
      (libsource (lib "eagle-import") (part "TPSB2.0"))
    )
    (comp (ref "TP28")
      (value "TPSB2.0")
      (footprint "eagle-import:B2.0")
      (libsource (lib "eagle-import") (part "TPSB2.0"))
    )
    (comp (ref "TP29")
      (value "TPSB2.0")
      (footprint "eagle-import:B2.0")
      (libsource (lib "eagle-import") (part "TPSB2.0"))
    )
    (comp (ref "TP30")
      (value "TPSB2.0")
      (footprint "eagle-import:B2.0")
      (libsource (lib "eagle-import") (part "TPSB2.0"))
    )
    (comp (ref "TP31")
      (value "TPSB2.0")
      (footprint "eagle-import:B2.0")
      (libsource (lib "eagle-import") (part "TPSB2.0"))
    )
    (comp (ref "TP32")
      (value "TPSB2.0")
      (footprint "eagle-import:B2.0")
      (libsource (lib "eagle-import") (part "TPSB2.0"))
    )
    (comp (ref "TP33")
      (value "TPSB2.0")
      (footprint "eagle-import:B2.0")
      (libsource (lib "eagle-import") (part "TPSB2.0"))
    )
    (comp (ref "TP34")
      (value "TPSB2.0")
      (footprint "eagle-import:B2.0")
      (libsource (lib "eagle-import") (part "TPSB2.0"))
    )
    (comp (ref "TP35")
      (value "TPSB2.0")
      (footprint "eagle-import:B2.0")
      (libsource (lib "eagle-import") (part "TPSB2.0"))
    )
    (comp (ref "TP36")
      (value "TPSB2.0")
      (footprint "eagle-import:B2.0")
      (libsource (lib "eagle-import") (part "TPSB2.0"))
    )
    (comp (ref "TP37")
      (value "TPSB2.0")
      (footprint "eagle-import:B2.0")
      (libsource (lib "eagle-import") (part "TPSB2.0"))
    )
    (comp (ref "TP38")
      (value "TPSB2.0")
      (footprint "eagle-import:B2.0")
      (libsource (lib "eagle-import") (part "TPSB2.0"))
    )
    (comp (ref "TP39")
      (value "TPSB2.0")
      (footprint "eagle-import:B2.0")
      (libsource (lib "eagle-import") (part "TPSB2.0"))
    )
    (comp (ref "TP40")
      (value "TPSB2.0")
      (footprint "eagle-import:B2.0")
      (libsource (lib "eagle-import") (part "TPSB2.0"))
    )
    (comp (ref "TP41")
      (value "TPSB2.0")
      (footprint "eagle-import:B2.0")
      (libsource (lib "eagle-import") (part "TPSB2.0"))
    )
    (comp (ref "TP42")
      (value "TPSB1,27")
      (footprint "eagle-import:B1,27")
      (libsource (lib "eagle-import") (part "TPSB1,27"))
    )
    (comp (ref "TP43")
      (value "TPSB2.0")
      (footprint "eagle-import:B2.0")
      (libsource (lib "eagle-import") (part "TPSB2.0"))
    )
    (comp (ref "TP44")
      (value "TPSB2.0")
      (footprint "eagle-import:B2.0")
      (libsource (lib "eagle-import") (part "TPSB2.0"))
    )
    (comp (ref "TP45")
      (value "TPSB2.0")
      (footprint "eagle-import:B2.0")
      (libsource (lib "eagle-import") (part "TPSB2.0"))
    )
    (comp (ref "TP46")
      (value "TPSB2.0")
      (footprint "eagle-import:B2.0")
      (libsource (lib "eagle-import") (part "TPSB2.0"))
    )
    (comp (ref "X201")
      (value "CON_BMWV2")
      (footprint "eagle-import:24-PIN_V2")
      (libsource (lib "eagle-import") (part "CON_BMWV2"))
    )
    (comp (ref "X202")
      (value "22-23-2021")
      (footprint "eagle-import:22-23-2021")
      (fields (field (name "MF") "MOLEX"))
      (libsource (lib "eagle-import") (part "22-23-2021"))
    )
    (comp (ref "X203")
      (value "22-23-2051")
      (footprint "eagle-import:22-23-2051")
      (fields (field (name "MF") "MOLEX"))
      (libsource (lib "eagle-import") (part "22-23-2051"))
    )
    (comp (ref "5")
      (value "2081-1132")
      (footprint "eagle-import:12-PIN")
      (libsource (lib "eagle-import") (part "2081-1132"))
    )
    (comp (ref "6")
      (value "2081-1132")
      (footprint "eagle-import:12-PIN")
      (libsource (lib "eagle-import") (part "2081-1132"))
    )
    (comp (ref "6V301")
      (value "TPSB2.0")
      (footprint "eagle-import:B2.0")
      (libsource (lib "eagle-import") (part "TPSB2.0"))
    )
    (comp (ref "10V301")
      (value "TPSB2.0")
      (footprint "eagle-import:B2.0")
      (libsource (lib "eagle-import") (part "TPSB2.0"))
    )
    (comp (ref "C301")
      (value "4.7u")
      (footprint "eagle-import:C0805")
      (fields (field (name "MPN") "CC0805KKX5R8BB475"))
      (libsource (lib "eagle-import") (part "CERAMIC-4.7UF-25V-10%-X5R(0805)"))
    )
    (comp (ref "C302")
      (value "100nF")
      (footprint "eagle-import:C0805")
      (fields (field (name "MPN") "CC0805KRX7R9BB104"))
      (libsource (lib "eagle-import") (part "CERAMIC-100NF-50V-10%-X7R(0805)"))
    )
    (comp (ref "C303")
      (value "100nF,")
      (footprint "eagle-import:C0805")
      (fields (field (name "MPN") "CC0805KRX7R9BB104"))
      (libsource (lib "eagle-import") (part "CERAMIC-100NF-50V-10%-X7R(0805)"))
    )
    (comp (ref "C304")
      (value "100nF,")
      (footprint "eagle-import:C0805")
      (fields (field (name "MPN") "CC0805KRX7R9BB104"))
      (libsource (lib "eagle-import") (part "CERAMIC-100NF-50V-10%-X7R(0805)"))
    )
    (comp (ref "C305")
      (value "100nF.")
      (footprint "eagle-import:C0805")
      (fields (field (name "MPN") "CC0805KRX7R9BB104"))
      (libsource (lib "eagle-import") (part "CERAMIC-100NF-50V-10%-X7R(0805)"))
    )
    (comp (ref "C306")
      (value "100nF.")
      (footprint "eagle-import:C0805")
      (fields (field (name "MPN") "CC0805KRX7R9BB104"))
      (libsource (lib "eagle-import") (part "CERAMIC-100NF-50V-10%-X7R(0805)"))
    )
    (comp (ref "C307")
      (value "100u")
      (footprint "eagle-import:C1206")
      (fields (field (name "MPN") "GRM31CR60J107ME39L"))
      (libsource (lib "eagle-import") (part "CERAMIC-100UF-6.3V-20%-X5R(1206)"))
    )
    (comp (ref "C308")
      (value "100u")
      (footprint "eagle-import:C1206")
      (fields (field (name "MPN") "GRM31CR60J107ME39L"))
      (libsource (lib "eagle-import") (part "CERAMIC-100UF-6.3V-20%-X5R(1206)"))
    )
    (comp (ref "C309")
      (value "2.2nF")
      (footprint "eagle-import:C0805")
      (fields (field (name "MPN") "CC0805KRX7R9BB104"))
      (libsource (lib "eagle-import") (part "CERAMIC-100NF-50V-10%-X7R(0805)"))
    )
    (comp (ref "C310")
      (value "100nF")
      (footprint "eagle-import:C0805")
      (fields (field (name "MPN") "CC0805KRX7R9BB104"))
      (libsource (lib "eagle-import") (part "CERAMIC-100NF-50V-10%-X7R(0805)"))
    )
    (comp (ref "D301")
      (value "SM6T")
      (footprint "eagle-import:DO214AA")
      (libsource (lib "eagle-import") (part "SM6T"))
    )
    (comp (ref "D302")
      (value "1N4007,")
      (footprint "eagle-import:DO-214AC")
      (fields (field (name "MPN") "1N4007"))
      (libsource (lib "eagle-import") (part "DIODE-GEN-PURPOSE-1KV-1A(DO-214AC)"))
    )
    (comp (ref "D303")
      (value "1N4007,")
      (footprint "eagle-import:DO-214AC")
      (fields (field (name "MPN") "1N4007"))
      (libsource (lib "eagle-import") (part "DIODE-GEN-PURPOSE-1KV-1A(DO-214AC)"))
    )
    (comp (ref "D304")
      (value "SM6TDO214AA_BI")
      (footprint "eagle-import:DO214AA_BI")
      (libsource (lib "eagle-import") (part "SM6TDO214AA_BI"))
    )
    (comp (ref "D305")
      (value "1N4007.")
      (footprint "eagle-import:DO-214AC")
      (fields (field (name "MPN") "1N4007"))
      (libsource (lib "eagle-import") (part "DIODE-GEN-PURPOSE-1KV-1A(DO-214AC)"))
    )
    (comp (ref "D306")
      (value "1N4007.")
      (footprint "eagle-import:DO-214AC")
      (fields (field (name "MPN") "1N4007"))
      (libsource (lib "eagle-import") (part "DIODE-GEN-PURPOSE-1KV-1A(DO-214AC)"))
    )
    (comp (ref "D307")
      (value "1N5817")
      (footprint "eagle-import:DO-214AC_SLIM")
      (libsource (lib "eagle-import") (part "DIODE-GEN-PURPOSE-1KV-1A(DO-214AC)DO-214AC/1206"))
    )
    (comp (ref "D308")
      (value "1N5817.")
      (footprint "eagle-import:DO-214AC_SLIM")
      (libsource (lib "eagle-import") (part "DIODE-GEN-PURPOSE-1KV-1A(DO-214AC)DO-214AC/1206"))
    )
    (comp (ref "D309")
      (value "1N5817.")
      (footprint "eagle-import:DO-214AC_SLIM")
      (libsource (lib "eagle-import") (part "DIODE-GEN-PURPOSE-1KV-1A(DO-214AC)DO-214AC/1206"))
    )
    (comp (ref "D310")
      (value "1N5817")
      (footprint "eagle-import:DO-214AC_SLIM")
      (libsource (lib "eagle-import") (part "DIODE-GEN-PURPOSE-1KV-1A(DO-214AC)DO-214AC/1206"))
    )
    (comp (ref "D311")
      (value "1N4007")
      (footprint "eagle-import:DO-214AC")
      (libsource (lib "eagle-import") (part "DIODE-GEN-PURPOSE-1KV-1A(DO-214AC)"))
    )
    (comp (ref "D312")
      (value "1N4007")
      (footprint "eagle-import:DO-214AC")
      (libsource (lib "eagle-import") (part "DIODE-GEN-PURPOSE-1KV-1A(DO-214AC)"))
    )
    (comp (ref "FID301")
      (value "FIDUCIAL")
      (footprint "eagle-import:FIDUCIAL_1MM")
      (libsource (lib "eagle-import") (part "FIDUCIAL"))
    )
    (comp (ref "FID302")
      (value "FIDUCIAL")
      (footprint "eagle-import:FIDUCIAL_1MM")
      (libsource (lib "eagle-import") (part "FIDUCIAL"))
    )
    (comp (ref "FID303")
      (value "FIDUCIAL")
      (footprint "eagle-import:FIDUCIAL_1MM")
      (libsource (lib "eagle-import") (part "FIDUCIAL"))
    )
    (comp (ref "FID304")
      (value "FIDUCIAL")
      (footprint "eagle-import:FIDUCIAL_1MM")
      (libsource (lib "eagle-import") (part "FIDUCIAL"))
    )
    (comp (ref "IC301")
      (value "LM2904")
      (footprint "eagle-import:SO08")
      (libsource (lib "eagle-import") (part "LM358D"))
    )
    (comp (ref "IC302")
      (value "78L06")
      (footprint "eagle-import:SOT89_ROUND")
      (libsource (lib "eagle-import") (part "78LXXSOT89_ROUND"))
    )
    (comp (ref "IC303")
      (value "6V pos")
      (footprint "eagle-import:78LXX")
      (libsource (lib "eagle-import") (part "v-reg_78LXX"))
    )
    (comp (ref "IC304")
      (value "78L10")
      (footprint "eagle-import:SOT89_ROUND")
      (libsource (lib "eagle-import") (part "78LXXSOT89_ROUND"))
    )
    (comp (ref "IC305")
      (value "4028")
      (footprint "eagle-import:SO16")
      (libsource (lib "eagle-import") (part "4028D"))
    )
    (comp (ref "IC306")
      (value "NUP4304SOT457_R")
      (footprint "eagle-import:SOT457R_PHILIPS")
      (libsource (lib "eagle-import") (part "NUP4304SOT457_R"))
    )
    (comp (ref "IC307")
      (value "ULN2004")
      (footprint "eagle-import:SO16")
      (libsource (lib "eagle-import") (part "ULN2004AD"))
    )
    (comp (ref "IC308")
      (value "LM339")
      (footprint "eagle-import:SO14")
      (libsource (lib "eagle-import") (part "LM339D"))
    )
    (comp (ref "IC309")
      (value "317TO202H_NOHOLE")
      (footprint "eagle-import:TO220H_NOHOLE")
      (libsource (lib "eagle-import") (part "317TO202H_NOHOLE"))
    )
    (comp (ref "IC310")
      (value "555")
      (footprint "eagle-import:SO08")
      (libsource (lib "eagle-import") (part "555DNE"))
    )
    (comp (ref "IC311")
      (value "4538")
      (footprint "eagle-import:SO16")
      (libsource (lib "eagle-import") (part "4538D"))
    )
    (comp (ref "JP301")
      (value "JP2EJP2_SMALLPADS")
      (footprint "eagle-import:JP2_SMALLPADS")
      (libsource (lib "eagle-import") (part "JP2EJP2_SMALLPADS"))
    )
    (comp (ref "JP302")
      (value "JP2EJP2_SMALLPADS")
      (footprint "eagle-import:JP2_SMALLPADS")
      (libsource (lib "eagle-import") (part "JP2EJP2_SMALLPADS"))
    )
    (comp (ref "JP303")
      (value "JP2EJP2_SMALLPADS")
      (footprint "eagle-import:JP2_SMALLPADS")
      (libsource (lib "eagle-import") (part "JP2EJP2_SMALLPADS"))
    )
    (comp (ref "JP304")
      (value "JP2EJP2_SMALLPADS")
      (footprint "eagle-import:JP2_SMALLPADS")
      (libsource (lib "eagle-import") (part "JP2EJP2_SMALLPADS"))
    )
    (comp (ref "JP305")
      (value "JP2E_ORIG")
      (footprint "eagle-import:JP2_ORIG_SMALLPADS")
      (libsource (lib "eagle-import") (part "JP2E_ORIG"))
    )
    (comp (ref "LED301")
      (value "LEDLD260")
      (footprint "eagle-import:LD260")
      (libsource (lib "eagle-import") (part "LEDLD260"))
    )
    (comp (ref "LED302")
      (value "LEDLD260")
      (footprint "eagle-import:LD260")
      (libsource (lib "eagle-import") (part "LEDLD260"))
    )
    (comp (ref "LED303")
      (value "LEDLD260")
      (footprint "eagle-import:LD260")
      (libsource (lib "eagle-import") (part "LEDLD260"))
    )
    (comp (ref "LED304")
      (value "LEDLD260")
      (footprint "eagle-import:LD260")
      (libsource (lib "eagle-import") (part "LEDLD260"))
    )
    (comp (ref "LED305")
      (value "LEDLD260")
      (footprint "eagle-import:LD260")
      (libsource (lib "eagle-import") (part "LEDLD260"))
    )
    (comp (ref "LED306")
      (value "LEDLD260")
      (footprint "eagle-import:LD260")
      (libsource (lib "eagle-import") (part "LEDLD260"))
    )
    (comp (ref "Q301")
      (value "BA.")
      (footprint "eagle-import:SOT89")
      (libsource (lib "eagle-import") (part "PNP-TRANSISTOR_SOT89"))
    )
    (comp (ref "Q302")
      (value "BA.")
      (footprint "eagle-import:SOT89")
      (libsource (lib "eagle-import") (part "PNP-TRANSISTOR_SOT89"))
    )
    (comp (ref "Q303")
      (value "MY")
      (footprint "eagle-import:SOT89")
      (libsource (lib "eagle-import") (part "NPN-TRANSISTOR_SOT89"))
    )
    (comp (ref "Q304")
      (value "BA")
      (footprint "eagle-import:SOT89")
      (libsource (lib "eagle-import") (part "PNP-TRANSISTOR_SOT89"))
    )
    (comp (ref "Q305")
      (value "BA")
      (footprint "eagle-import:SOT89")
      (libsource (lib "eagle-import") (part "PNP-TRANSISTOR_SOT89"))
    )
    (comp (ref "Q306")
      (value "J1")
      (footprint "eagle-import:SOT-23")
      (fields (field (name "MPN") "BSS138W-7-F"))
      (libsource (lib "eagle-import") (part "SMD-MOSFET-N-CH-50V-200MA-BSS138W-7-F(SOT-23)"))
    )
    (comp (ref "Q307")
      (value "J1")
      (footprint "eagle-import:SOT-23")
      (fields (field (name "MPN") "BSS138W-7-F"))
      (libsource (lib "eagle-import") (part "SMD-MOSFET-N-CH-50V-200MA-BSS138W-7-F(SOT-23)"))
    )
    (comp (ref "R301")
      (value "102")
      (footprint "eagle-import:R0805")
      (fields (field (name "MPN") "RC0805JR-071KL"))
      (libsource (lib "eagle-import") (part "SMD-RES-1K-5%-1/8W(0805)"))
    )
    (comp (ref "R302")
      (value "13")
      (footprint "eagle-import:R1206")
      (fields (field (name "MPN") "RC1206JR-0713RL"))
      (libsource (lib "eagle-import") (part "SMD-RES-13R-5%-1/4W(1206)"))
    )
    (comp (ref "R303")
      (value "R_user")
      (footprint "eagle-import:R0805")
      (libsource (lib "eagle-import") (part "R-EU_R0805"))
    )
    (comp (ref "R304")
      (value "R_user")
      (footprint "eagle-import:R0805")
      (libsource (lib "eagle-import") (part "R-EU_R0805"))
    )
    (comp (ref "R305")
      (value "4701")
      (footprint "eagle-import:R0805")
      (fields (field (name "MPN") "RC0805JR-074K7L"))
      (libsource (lib "eagle-import") (part "SMD-RES-4.7K-5%-1/8W(0805)"))
    )
    (comp (ref "R306")
      (value "13")
      (footprint "eagle-import:R1206")
      (fields (field (name "MPN") "RC1206JR-0713RL"))
      (libsource (lib "eagle-import") (part "SMD-RES-13R-5%-1/4W(1206)"))
    )
    (comp (ref "R307")
      (value "1002")
      (footprint "eagle-import:R0805")
      (fields (field (name "MPN") "RC0805FR-0710KL"))
      (libsource (lib "eagle-import") (part "SMD-RES-10K-1%-1/8W(0805)"))
    )
    (comp (ref "R308")
      (value "1002")
      (footprint "eagle-import:R0805")
      (fields (field (name "MPN") "RC0805FR-0710KL"))
      (libsource (lib "eagle-import") (part "SMD-RES-10K-1%-1/8W(0805)"))
    )
    (comp (ref "R309")
      (value "104.")
      (footprint "eagle-import:R0805")
      (fields (field (name "MPN") "RC0805FR-0710KL"))
      (libsource (lib "eagle-import") (part "SMD-RES-10K-1%-1/8W(0805)"))
    )
    (comp (ref "R310")
      (value "104.")
      (footprint "eagle-import:R0805")
      (fields (field (name "MPN") "RC0805FR-0710KL"))
      (libsource (lib "eagle-import") (part "SMD-RES-10K-1%-1/8W(0805)"))
    )
    (comp (ref "R311")
      (value "104.")
      (footprint "eagle-import:R0805")
      (fields (field (name "MPN") "RC0805FR-0710KL"))
      (libsource (lib "eagle-import") (part "SMD-RES-10K-1%-1/8W(0805)"))
    )
    (comp (ref "R312")
      (value "102")
      (footprint "eagle-import:R0805")
      (fields (field (name "MPN") "RC0805JR-071KL"))
      (libsource (lib "eagle-import") (part "SMD-RES-1K-5%-1/8W(0805)"))
    )
    (comp (ref "R313")
      (value "102")
      (footprint "eagle-import:R0805")
      (fields (field (name "MPN") "RC0805JR-071KL"))
      (libsource (lib "eagle-import") (part "SMD-RES-1K-5%-1/8W(0805)"))
    )
    (comp (ref "R314")
      (value "102")
      (footprint "eagle-import:R0805")
      (fields (field (name "MPN") "RC0805JR-071KL"))
      (libsource (lib "eagle-import") (part "SMD-RES-1K-5%-1/8W(0805)"))
    )
    (comp (ref "R315")
      (value "100")
      (footprint "eagle-import:R0805")
      (fields (field (name "MPN") "RC0805JR-07220RL"))
      (libsource (lib "eagle-import") (part "SMD-RES-220R-5%-1/8W(0805)"))
    )
    (comp (ref "R316")
      (value "4701")
      (footprint "eagle-import:R0805")
      (fields (field (name "MPN") "RC0805JR-074K7L"))
      (libsource (lib "eagle-import") (part "SMD-RES-4.7K-5%-1/8W(0805)"))
    )
    (comp (ref "R317")
      (value "2702")
      (footprint "eagle-import:R0805")
      (fields (field (name "MPN") "RC0805JR-074K7L"))
      (libsource (lib "eagle-import") (part "SMD-RES-4.7K-5%-1/8W(0805)"))
    )
    (comp (ref "R318")
      (value "13")
      (footprint "eagle-import:R1206")
      (fields (field (name "MPN") "RC1206JR-0713RL"))
      (libsource (lib "eagle-import") (part "SMD-RES-13R-5%-1/4W(1206)"))
    )
    (comp (ref "R319")
      (value "2201")
      (footprint "eagle-import:R0805")
      (fields (field (name "MPN") "RC0805JR-072K2L"))
      (libsource (lib "eagle-import") (part "SMD-RES-2.2K-5%-1/8W(0805)"))
    )
    (comp (ref "R320")
      (value "1002")
      (footprint "eagle-import:R0805")
      (fields (field (name "MPN") "RC0805FR-0710KL"))
      (libsource (lib "eagle-import") (part "SMD-RES-10K-1%-1/8W(0805)"))
    )
    (comp (ref "R321")
      (value "1502")
      (footprint "eagle-import:R0805")
      (fields (field (name "MPN") "RC0805FR-0710KL"))
      (libsource (lib "eagle-import") (part "SMD-RES-10K-1%-1/8W(0805)"))
    )
    (comp (ref "R322")
      (value "2702")
      (footprint "eagle-import:R0805")
      (fields (field (name "MPN") "RC0805JR-074K7L"))
      (libsource (lib "eagle-import") (part "SMD-RES-4.7K-5%-1/8W(0805)"))
    )
    (comp (ref "R323")
      (value "2702")
      (footprint "eagle-import:R0805")
      (fields (field (name "MPN") "RC0805JR-074K7L"))
      (libsource (lib "eagle-import") (part "SMD-RES-4.7K-5%-1/8W(0805)"))
    )
    (comp (ref "R324")
      (value "1002")
      (footprint "eagle-import:R0805")
      (fields (field (name "MPN") "RC0805FR-0710KL"))
      (libsource (lib "eagle-import") (part "SMD-RES-10K-1%-1/8W(0805)"))
    )
    (comp (ref "R325")
      (value "104")
      (footprint "eagle-import:R0805")
      (fields (field (name "MPN") "RC0805FR-0710KL"))
      (libsource (lib "eagle-import") (part "SMD-RES-10K-1%-1/8W(0805)"))
    )
    (comp (ref "R326")
      (value "4701")
      (footprint "eagle-import:R0805")
      (fields (field (name "MPN") "RC0805JR-074K7L"))
      (libsource (lib "eagle-import") (part "SMD-RES-4.7K-5%-1/8W(0805)"))
    )
    (comp (ref "R327")
      (value "47")
      (footprint "eagle-import:V235_17_1MM")
      (libsource (lib "eagle-import") (part "R-EU_V235/17_1MM"))
    )
    (comp (ref "R328")
      (value "102")
      (footprint "eagle-import:R0805")
      (fields (field (name "MPN") "RC0805JR-071KL"))
      (libsource (lib "eagle-import") (part "SMD-RES-1K-5%-1/8W(0805)"))
    )
    (comp (ref "R329")
      (value "47")
      (footprint "eagle-import:V235_17_1MM")
      (libsource (lib "eagle-import") (part "R-EU_V235/17_1MM"))
    )
    (comp (ref "R330")
      (value "104")
      (footprint "eagle-import:R0805")
      (fields (field (name "MPN") "RC0805FR-0710KL"))
      (libsource (lib "eagle-import") (part "SMD-RES-10K-1%-1/8W(0805)"))
    )
    (comp (ref "R331")
      (value "1502")
      (footprint "eagle-import:R0805")
      (fields (field (name "MPN") "RC0805FR-0710KL"))
      (libsource (lib "eagle-import") (part "SMD-RES-10K-1%-1/8W(0805)"))
    )
    (comp (ref "R332")
      (value "1002")
      (footprint "eagle-import:R0805")
      (fields (field (name "MPN") "RC0805FR-0710KL"))
      (libsource (lib "eagle-import") (part "SMD-RES-10K-1%-1/8W(0805)"))
    )
    (comp (ref "R333")
      (value "2201")
      (footprint "eagle-import:R0805")
      (fields (field (name "MPN") "RC0805JR-072K2L"))
      (libsource (lib "eagle-import") (part "SMD-RES-2.2K-5%-1/8W(0805)"))
    )
    (comp (ref "R334")
      (value "13")
      (footprint "eagle-import:R1206")
      (fields (field (name "MPN") "RC1206JR-0713RL"))
      (libsource (lib "eagle-import") (part "SMD-RES-13R-5%-1/4W(1206)"))
    )
    (comp (ref "R335")
      (value "104.")
      (footprint "eagle-import:R0805")
      (fields (field (name "MPN") "RC0805FR-0710KL"))
      (libsource (lib "eagle-import") (part "SMD-RES-10K-1%-1/8W(0805)"))
    )
    (comp (ref "R336")
      (value "47")
      (footprint "eagle-import:V235_17_1MM")
      (libsource (lib "eagle-import") (part "R-EU_V235/17_1MM"))
    )
    (comp (ref "R337")
      (value "47")
      (footprint "eagle-import:V235_17_1MM")
      (libsource (lib "eagle-import") (part "R-EU_V235/17_1MM"))
    )
    (comp (ref "R338")
      (value "100")
      (footprint "eagle-import:R0805")
      (fields (field (name "MPN") "RC0805JR-072K2L"))
      (libsource (lib "eagle-import") (part "SMD-RES-2.2K-5%-1/8W(0805)"))
    )
    (comp (ref "R339")
      (value "(101)")
      (footprint "eagle-import:R0805")
      (fields (field (name "MPN") "RC0805JR-072K2L"))
      (libsource (lib "eagle-import") (part "SMD-RES-2.2K-5%-1/8W(0805)"))
    )
    (comp (ref "R340")
      (value "2702")
      (footprint "eagle-import:R0805")
      (fields (field (name "MPN") "RC0805FR-0710KL"))
      (libsource (lib "eagle-import") (part "SMD-RES-10K-1%-1/8W(0805)"))
    )
    (comp (ref "R341")
      (value "104")
      (footprint "eagle-import:R0805")
      (fields (field (name "MPN") "RC0805FR-0710KL"))
      (libsource (lib "eagle-import") (part "SMD-RES-10K-1%-1/8W(0805)"))
    )
    (comp (ref "R342")
      (value "(1000)")
      (footprint "eagle-import:R0805")
      (fields (field (name "MPN") "RC0805JR-07100RL"))
      (libsource (lib "eagle-import") (part "SMD-RES-100R-5%-1/8W(0805)"))
    )
    (comp (ref "R343")
      (value "(101)")
      (footprint "eagle-import:R0805")
      (fields (field (name "MPN") "RC0805JR-07100RL"))
      (libsource (lib "eagle-import") (part "SMD-RES-100R-5%-1/8W(0805)"))
    )
    (comp (ref "R344")
      (value "(1002)")
      (footprint "eagle-import:R0805")
      (fields (field (name "MPN") "RC0805FR-0710KL"))
      (libsource (lib "eagle-import") (part "SMD-RES-10K-1%-1/8W(0805)"))
    )
    (comp (ref "R345")
      (value "2702")
      (footprint "eagle-import:R0805")
      (fields (field (name "MPN") "RC0805JR-074K7L"))
      (libsource (lib "eagle-import") (part "SMD-RES-4.7K-5%-1/8W(0805)"))
    )
    (comp (ref "R346")
      (value "(1002)")
      (footprint "eagle-import:R0805")
      (fields (field (name "MPN") "RC0805JR-074K7L"))
      (libsource (lib "eagle-import") (part "SMD-RES-4.7K-5%-1/8W(0805)"))
    )
    (comp (ref "SJ301")
      (value "SJ")
      (footprint "eagle-import:SJ")
      (libsource (lib "eagle-import") (part "SJ"))
    )
    (comp (ref "START301")
      (value "TPSB2.0")
      (footprint "eagle-import:B2.0")
      (libsource (lib "eagle-import") (part "TPSB2.0"))
    )
    (comp (ref "TP47")
      (value "TPSB2.0")
      (footprint "eagle-import:B2.0")
      (libsource (lib "eagle-import") (part "TPSB2.0"))
    )
    (comp (ref "TP48")
      (value "TPSB2.0")
      (footprint "eagle-import:B2.0")
      (libsource (lib "eagle-import") (part "TPSB2.0"))
    )
    (comp (ref "TP49")
      (value "TPSB2.0")
      (footprint "eagle-import:B2.0")
      (libsource (lib "eagle-import") (part "TPSB2.0"))
    )
    (comp (ref "TP50")
      (value "TPSB2.0")
      (footprint "eagle-import:B2.0")
      (libsource (lib "eagle-import") (part "TPSB2.0"))
    )
    (comp (ref "TP51")
      (value "TPSB2.0")
      (footprint "eagle-import:B2.0")
      (libsource (lib "eagle-import") (part "TPSB2.0"))
    )
    (comp (ref "TP52")
      (value "TPSB2.0")
      (footprint "eagle-import:B2.0")
      (libsource (lib "eagle-import") (part "TPSB2.0"))
    )
    (comp (ref "TP53")
      (value "TPSB2.0")
      (footprint "eagle-import:B2.0")
      (libsource (lib "eagle-import") (part "TPSB2.0"))
    )
    (comp (ref "TP54")
      (value "TPSB2.0")
      (footprint "eagle-import:B2.0")
      (libsource (lib "eagle-import") (part "TPSB2.0"))
    )
    (comp (ref "TP55")
      (value "TPSB2.0")
      (footprint "eagle-import:B2.0")
      (libsource (lib "eagle-import") (part "TPSB2.0"))
    )
    (comp (ref "TP56")
      (value "TPSB2.0")
      (footprint "eagle-import:B2.0")
      (libsource (lib "eagle-import") (part "TPSB2.0"))
    )
    (comp (ref "TP57")
      (value "TPSB2.0")
      (footprint "eagle-import:B2.0")
      (libsource (lib "eagle-import") (part "TPSB2.0"))
    )
    (comp (ref "TP58")
      (value "TPSB2.0")
      (footprint "eagle-import:B2.0")
      (libsource (lib "eagle-import") (part "TPSB2.0"))
    )
    (comp (ref "TP59")
      (value "TPSB2.0")
      (footprint "eagle-import:B2.0")
      (libsource (lib "eagle-import") (part "TPSB2.0"))
    )
    (comp (ref "TP60")
      (value "TPSB2.0")
      (footprint "eagle-import:B2.0")
      (libsource (lib "eagle-import") (part "TPSB2.0"))
    )
    (comp (ref "TP61")
      (value "TPSB2.0")
      (footprint "eagle-import:B2.0")
      (libsource (lib "eagle-import") (part "TPSB2.0"))
    )
    (comp (ref "TP62")
      (value "TPSB2.0")
      (footprint "eagle-import:B2.0")
      (libsource (lib "eagle-import") (part "TPSB2.0"))
    )
    (comp (ref "TP63")
      (value "TPSB2.0")
      (footprint "eagle-import:B2.0")
      (libsource (lib "eagle-import") (part "TPSB2.0"))
    )
    (comp (ref "TP64")
      (value "TPSB2.0")
      (footprint "eagle-import:B2.0")
      (libsource (lib "eagle-import") (part "TPSB2.0"))
    )
    (comp (ref "TP65")
      (value "TPSB1,27")
      (footprint "eagle-import:B1,27")
      (libsource (lib "eagle-import") (part "TPSB1,27"))
    )
    (comp (ref "TP66")
      (value "TPSB2.0")
      (footprint "eagle-import:B2.0")
      (libsource (lib "eagle-import") (part "TPSB2.0"))
    )
    (comp (ref "TP67")
      (value "TPSB2.0")
      (footprint "eagle-import:B2.0")
      (libsource (lib "eagle-import") (part "TPSB2.0"))
    )
    (comp (ref "TP68")
      (value "TPSB2.0")
      (footprint "eagle-import:B2.0")
      (libsource (lib "eagle-import") (part "TPSB2.0"))
    )
    (comp (ref "TP69")
      (value "TPSB2.0")
      (footprint "eagle-import:B2.0")
      (libsource (lib "eagle-import") (part "TPSB2.0"))
    )
    (comp (ref "X301")
      (value "CON_BMWV2")
      (footprint "eagle-import:24-PIN_V2")
      (libsource (lib "eagle-import") (part "CON_BMWV2"))
    )
    (comp (ref "X302")
      (value "22-23-2021")
      (footprint "eagle-import:22-23-2021")
      (fields (field (name "MF") "MOLEX"))
      (libsource (lib "eagle-import") (part "22-23-2021"))
    )
    (comp (ref "X303")
      (value "22-23-2051")
      (footprint "eagle-import:22-23-2051")
      (fields (field (name "MF") "MOLEX"))
      (libsource (lib "eagle-import") (part "22-23-2051"))
    )
    (comp (ref "6V701")
      (value "TPSB2.0")
      (footprint "eagle-import:B2.0")
      (libsource (lib "eagle-import") (part "TPSB2.0"))
    )
    (comp (ref "10V701")
      (value "TPSB2.0")
      (footprint "eagle-import:B2.0")
      (libsource (lib "eagle-import") (part "TPSB2.0"))
    )
    (comp (ref "13")
      (value "2081-1132")
      (footprint "eagle-import:12-PIN")
      (libsource (lib "eagle-import") (part "2081-1132"))
    )
    (comp (ref "14")
      (value "2081-1132")
      (footprint "eagle-import:12-PIN")
      (libsource (lib "eagle-import") (part "2081-1132"))
    )
    (comp (ref "C701")
      (value "4.7u")
      (footprint "eagle-import:C0805")
      (fields (field (name "MPN") "CC0805KKX5R8BB475"))
      (libsource (lib "eagle-import") (part "CERAMIC-4.7UF-25V-10%-X5R(0805)"))
    )
    (comp (ref "C702")
      (value "100nF")
      (footprint "eagle-import:C0805")
      (fields (field (name "MPN") "CC0805KRX7R9BB104"))
      (libsource (lib "eagle-import") (part "CERAMIC-100NF-50V-10%-X7R(0805)"))
    )
    (comp (ref "C703")
      (value "100nF,")
      (footprint "eagle-import:C0805")
      (fields (field (name "MPN") "CC0805KRX7R9BB104"))
      (libsource (lib "eagle-import") (part "CERAMIC-100NF-50V-10%-X7R(0805)"))
    )
    (comp (ref "C704")
      (value "100nF,")
      (footprint "eagle-import:C0805")
      (fields (field (name "MPN") "CC0805KRX7R9BB104"))
      (libsource (lib "eagle-import") (part "CERAMIC-100NF-50V-10%-X7R(0805)"))
    )
    (comp (ref "C705")
      (value "100nF.")
      (footprint "eagle-import:C0805")
      (fields (field (name "MPN") "CC0805KRX7R9BB104"))
      (libsource (lib "eagle-import") (part "CERAMIC-100NF-50V-10%-X7R(0805)"))
    )
    (comp (ref "C706")
      (value "100nF.")
      (footprint "eagle-import:C0805")
      (fields (field (name "MPN") "CC0805KRX7R9BB104"))
      (libsource (lib "eagle-import") (part "CERAMIC-100NF-50V-10%-X7R(0805)"))
    )
    (comp (ref "C707")
      (value "100u")
      (footprint "eagle-import:C1206")
      (fields (field (name "MPN") "GRM31CR60J107ME39L"))
      (libsource (lib "eagle-import") (part "CERAMIC-100UF-6.3V-20%-X5R(1206)"))
    )
    (comp (ref "C708")
      (value "100u")
      (footprint "eagle-import:C1206")
      (fields (field (name "MPN") "GRM31CR60J107ME39L"))
      (libsource (lib "eagle-import") (part "CERAMIC-100UF-6.3V-20%-X5R(1206)"))
    )
    (comp (ref "C709")
      (value "2.2nF")
      (footprint "eagle-import:C0805")
      (fields (field (name "MPN") "CC0805KRX7R9BB104"))
      (libsource (lib "eagle-import") (part "CERAMIC-100NF-50V-10%-X7R(0805)"))
    )
    (comp (ref "C710")
      (value "100nF")
      (footprint "eagle-import:C0805")
      (fields (field (name "MPN") "CC0805KRX7R9BB104"))
      (libsource (lib "eagle-import") (part "CERAMIC-100NF-50V-10%-X7R(0805)"))
    )
    (comp (ref "D701")
      (value "SM6T")
      (footprint "eagle-import:DO214AA")
      (libsource (lib "eagle-import") (part "SM6T"))
    )
    (comp (ref "D702")
      (value "1N4007,")
      (footprint "eagle-import:DO-214AC")
      (fields (field (name "MPN") "1N4007"))
      (libsource (lib "eagle-import") (part "DIODE-GEN-PURPOSE-1KV-1A(DO-214AC)"))
    )
    (comp (ref "D703")
      (value "1N4007,")
      (footprint "eagle-import:DO-214AC")
      (fields (field (name "MPN") "1N4007"))
      (libsource (lib "eagle-import") (part "DIODE-GEN-PURPOSE-1KV-1A(DO-214AC)"))
    )
    (comp (ref "D704")
      (value "SM6TDO214AA_BI")
      (footprint "eagle-import:DO214AA_BI")
      (libsource (lib "eagle-import") (part "SM6TDO214AA_BI"))
    )
    (comp (ref "D705")
      (value "1N4007.")
      (footprint "eagle-import:DO-214AC")
      (fields (field (name "MPN") "1N4007"))
      (libsource (lib "eagle-import") (part "DIODE-GEN-PURPOSE-1KV-1A(DO-214AC)"))
    )
    (comp (ref "D706")
      (value "1N4007.")
      (footprint "eagle-import:DO-214AC")
      (fields (field (name "MPN") "1N4007"))
      (libsource (lib "eagle-import") (part "DIODE-GEN-PURPOSE-1KV-1A(DO-214AC)"))
    )
    (comp (ref "D707")
      (value "1N5817")
      (footprint "eagle-import:DO-214AC_SLIM")
      (libsource (lib "eagle-import") (part "DIODE-GEN-PURPOSE-1KV-1A(DO-214AC)DO-214AC/1206"))
    )
    (comp (ref "D708")
      (value "1N5817.")
      (footprint "eagle-import:DO-214AC_SLIM")
      (libsource (lib "eagle-import") (part "DIODE-GEN-PURPOSE-1KV-1A(DO-214AC)DO-214AC/1206"))
    )
    (comp (ref "D709")
      (value "1N5817.")
      (footprint "eagle-import:DO-214AC_SLIM")
      (libsource (lib "eagle-import") (part "DIODE-GEN-PURPOSE-1KV-1A(DO-214AC)DO-214AC/1206"))
    )
    (comp (ref "D710")
      (value "1N5817")
      (footprint "eagle-import:DO-214AC_SLIM")
      (libsource (lib "eagle-import") (part "DIODE-GEN-PURPOSE-1KV-1A(DO-214AC)DO-214AC/1206"))
    )
    (comp (ref "D711")
      (value "1N4007")
      (footprint "eagle-import:DO-214AC")
      (libsource (lib "eagle-import") (part "DIODE-GEN-PURPOSE-1KV-1A(DO-214AC)"))
    )
    (comp (ref "D712")
      (value "1N4007")
      (footprint "eagle-import:DO-214AC")
      (libsource (lib "eagle-import") (part "DIODE-GEN-PURPOSE-1KV-1A(DO-214AC)"))
    )
    (comp (ref "FID701")
      (value "FIDUCIAL")
      (footprint "eagle-import:FIDUCIAL_1MM")
      (libsource (lib "eagle-import") (part "FIDUCIAL"))
    )
    (comp (ref "FID702")
      (value "FIDUCIAL")
      (footprint "eagle-import:FIDUCIAL_1MM")
      (libsource (lib "eagle-import") (part "FIDUCIAL"))
    )
    (comp (ref "FID703")
      (value "FIDUCIAL")
      (footprint "eagle-import:FIDUCIAL_1MM")
      (libsource (lib "eagle-import") (part "FIDUCIAL"))
    )
    (comp (ref "FID704")
      (value "FIDUCIAL")
      (footprint "eagle-import:FIDUCIAL_1MM")
      (libsource (lib "eagle-import") (part "FIDUCIAL"))
    )
    (comp (ref "IC701")
      (value "LM2904")
      (footprint "eagle-import:SO08")
      (libsource (lib "eagle-import") (part "LM358D"))
    )
    (comp (ref "IC702")
      (value "78L06")
      (footprint "eagle-import:SOT89_ROUND")
      (libsource (lib "eagle-import") (part "78LXXSOT89_ROUND"))
    )
    (comp (ref "IC703")
      (value "6V pos")
      (footprint "eagle-import:78LXX")
      (libsource (lib "eagle-import") (part "v-reg_78LXX"))
    )
    (comp (ref "IC704")
      (value "78L10")
      (footprint "eagle-import:SOT89_ROUND")
      (libsource (lib "eagle-import") (part "78LXXSOT89_ROUND"))
    )
    (comp (ref "IC705")
      (value "4028")
      (footprint "eagle-import:SO16")
      (libsource (lib "eagle-import") (part "4028D"))
    )
    (comp (ref "IC706")
      (value "NUP4304SOT457_R")
      (footprint "eagle-import:SOT457R_PHILIPS")
      (libsource (lib "eagle-import") (part "NUP4304SOT457_R"))
    )
    (comp (ref "IC707")
      (value "ULN2004")
      (footprint "eagle-import:SO16")
      (libsource (lib "eagle-import") (part "ULN2004AD"))
    )
    (comp (ref "IC708")
      (value "LM339")
      (footprint "eagle-import:SO14")
      (libsource (lib "eagle-import") (part "LM339D"))
    )
    (comp (ref "IC709")
      (value "317TO202H_NOHOLE")
      (footprint "eagle-import:TO220H_NOHOLE")
      (libsource (lib "eagle-import") (part "317TO202H_NOHOLE"))
    )
    (comp (ref "IC710")
      (value "555")
      (footprint "eagle-import:SO08")
      (libsource (lib "eagle-import") (part "555DNE"))
    )
    (comp (ref "IC711")
      (value "4538")
      (footprint "eagle-import:SO16")
      (libsource (lib "eagle-import") (part "4538D"))
    )
    (comp (ref "JP701")
      (value "JP2EJP2_SMALLPADS")
      (footprint "eagle-import:JP2_SMALLPADS")
      (libsource (lib "eagle-import") (part "JP2EJP2_SMALLPADS"))
    )
    (comp (ref "JP702")
      (value "JP2EJP2_SMALLPADS")
      (footprint "eagle-import:JP2_SMALLPADS")
      (libsource (lib "eagle-import") (part "JP2EJP2_SMALLPADS"))
    )
    (comp (ref "JP703")
      (value "JP2EJP2_SMALLPADS")
      (footprint "eagle-import:JP2_SMALLPADS")
      (libsource (lib "eagle-import") (part "JP2EJP2_SMALLPADS"))
    )
    (comp (ref "JP704")
      (value "JP2EJP2_SMALLPADS")
      (footprint "eagle-import:JP2_SMALLPADS")
      (libsource (lib "eagle-import") (part "JP2EJP2_SMALLPADS"))
    )
    (comp (ref "JP705")
      (value "JP2E_ORIG")
      (footprint "eagle-import:JP2_ORIG_SMALLPADS")
      (libsource (lib "eagle-import") (part "JP2E_ORIG"))
    )
    (comp (ref "LED701")
      (value "LEDLD260")
      (footprint "eagle-import:LD260")
      (libsource (lib "eagle-import") (part "LEDLD260"))
    )
    (comp (ref "LED702")
      (value "LEDLD260")
      (footprint "eagle-import:LD260")
      (libsource (lib "eagle-import") (part "LEDLD260"))
    )
    (comp (ref "LED703")
      (value "LEDLD260")
      (footprint "eagle-import:LD260")
      (libsource (lib "eagle-import") (part "LEDLD260"))
    )
    (comp (ref "LED704")
      (value "LEDLD260")
      (footprint "eagle-import:LD260")
      (libsource (lib "eagle-import") (part "LEDLD260"))
    )
    (comp (ref "LED705")
      (value "LEDLD260")
      (footprint "eagle-import:LD260")
      (libsource (lib "eagle-import") (part "LEDLD260"))
    )
    (comp (ref "LED706")
      (value "LEDLD260")
      (footprint "eagle-import:LD260")
      (libsource (lib "eagle-import") (part "LEDLD260"))
    )
    (comp (ref "Q701")
      (value "BA.")
      (footprint "eagle-import:SOT89")
      (libsource (lib "eagle-import") (part "PNP-TRANSISTOR_SOT89"))
    )
    (comp (ref "Q702")
      (value "BA.")
      (footprint "eagle-import:SOT89")
      (libsource (lib "eagle-import") (part "PNP-TRANSISTOR_SOT89"))
    )
    (comp (ref "Q703")
      (value "MY")
      (footprint "eagle-import:SOT89")
      (libsource (lib "eagle-import") (part "NPN-TRANSISTOR_SOT89"))
    )
    (comp (ref "Q704")
      (value "BA")
      (footprint "eagle-import:SOT89")
      (libsource (lib "eagle-import") (part "PNP-TRANSISTOR_SOT89"))
    )
    (comp (ref "Q705")
      (value "BA")
      (footprint "eagle-import:SOT89")
      (libsource (lib "eagle-import") (part "PNP-TRANSISTOR_SOT89"))
    )
    (comp (ref "Q706")
      (value "J1")
      (footprint "eagle-import:SOT-23")
      (fields (field (name "MPN") "BSS138W-7-F"))
      (libsource (lib "eagle-import") (part "SMD-MOSFET-N-CH-50V-200MA-BSS138W-7-F(SOT-23)"))
    )
    (comp (ref "Q707")
      (value "J1")
      (footprint "eagle-import:SOT-23")
      (fields (field (name "MPN") "BSS138W-7-F"))
      (libsource (lib "eagle-import") (part "SMD-MOSFET-N-CH-50V-200MA-BSS138W-7-F(SOT-23)"))
    )
    (comp (ref "R701")
      (value "102")
      (footprint "eagle-import:R0805")
      (fields (field (name "MPN") "RC0805JR-071KL"))
      (libsource (lib "eagle-import") (part "SMD-RES-1K-5%-1/8W(0805)"))
    )
    (comp (ref "R702")
      (value "13")
      (footprint "eagle-import:R1206")
      (fields (field (name "MPN") "RC1206JR-0713RL"))
      (libsource (lib "eagle-import") (part "SMD-RES-13R-5%-1/4W(1206)"))
    )
    (comp (ref "R703")
      (value "R_user")
      (footprint "eagle-import:R0805")
      (libsource (lib "eagle-import") (part "R-EU_R0805"))
    )
    (comp (ref "R704")
      (value "R_user")
      (footprint "eagle-import:R0805")
      (libsource (lib "eagle-import") (part "R-EU_R0805"))
    )
    (comp (ref "R705")
      (value "4701")
      (footprint "eagle-import:R0805")
      (fields (field (name "MPN") "RC0805JR-074K7L"))
      (libsource (lib "eagle-import") (part "SMD-RES-4.7K-5%-1/8W(0805)"))
    )
    (comp (ref "R706")
      (value "13")
      (footprint "eagle-import:R1206")
      (fields (field (name "MPN") "RC1206JR-0713RL"))
      (libsource (lib "eagle-import") (part "SMD-RES-13R-5%-1/4W(1206)"))
    )
    (comp (ref "R707")
      (value "1002")
      (footprint "eagle-import:R0805")
      (fields (field (name "MPN") "RC0805FR-0710KL"))
      (libsource (lib "eagle-import") (part "SMD-RES-10K-1%-1/8W(0805)"))
    )
    (comp (ref "R708")
      (value "1002")
      (footprint "eagle-import:R0805")
      (fields (field (name "MPN") "RC0805FR-0710KL"))
      (libsource (lib "eagle-import") (part "SMD-RES-10K-1%-1/8W(0805)"))
    )
    (comp (ref "R709")
      (value "104.")
      (footprint "eagle-import:R0805")
      (fields (field (name "MPN") "RC0805FR-0710KL"))
      (libsource (lib "eagle-import") (part "SMD-RES-10K-1%-1/8W(0805)"))
    )
    (comp (ref "R710")
      (value "104.")
      (footprint "eagle-import:R0805")
      (fields (field (name "MPN") "RC0805FR-0710KL"))
      (libsource (lib "eagle-import") (part "SMD-RES-10K-1%-1/8W(0805)"))
    )
    (comp (ref "R711")
      (value "104.")
      (footprint "eagle-import:R0805")
      (fields (field (name "MPN") "RC0805FR-0710KL"))
      (libsource (lib "eagle-import") (part "SMD-RES-10K-1%-1/8W(0805)"))
    )
    (comp (ref "R712")
      (value "102")
      (footprint "eagle-import:R0805")
      (fields (field (name "MPN") "RC0805JR-071KL"))
      (libsource (lib "eagle-import") (part "SMD-RES-1K-5%-1/8W(0805)"))
    )
    (comp (ref "R713")
      (value "102")
      (footprint "eagle-import:R0805")
      (fields (field (name "MPN") "RC0805JR-071KL"))
      (libsource (lib "eagle-import") (part "SMD-RES-1K-5%-1/8W(0805)"))
    )
    (comp (ref "R714")
      (value "102")
      (footprint "eagle-import:R0805")
      (fields (field (name "MPN") "RC0805JR-071KL"))
      (libsource (lib "eagle-import") (part "SMD-RES-1K-5%-1/8W(0805)"))
    )
    (comp (ref "R715")
      (value "100")
      (footprint "eagle-import:R0805")
      (fields (field (name "MPN") "RC0805JR-07220RL"))
      (libsource (lib "eagle-import") (part "SMD-RES-220R-5%-1/8W(0805)"))
    )
    (comp (ref "R716")
      (value "4701")
      (footprint "eagle-import:R0805")
      (fields (field (name "MPN") "RC0805JR-074K7L"))
      (libsource (lib "eagle-import") (part "SMD-RES-4.7K-5%-1/8W(0805)"))
    )
    (comp (ref "R717")
      (value "2702")
      (footprint "eagle-import:R0805")
      (fields (field (name "MPN") "RC0805JR-074K7L"))
      (libsource (lib "eagle-import") (part "SMD-RES-4.7K-5%-1/8W(0805)"))
    )
    (comp (ref "R718")
      (value "13")
      (footprint "eagle-import:R1206")
      (fields (field (name "MPN") "RC1206JR-0713RL"))
      (libsource (lib "eagle-import") (part "SMD-RES-13R-5%-1/4W(1206)"))
    )
    (comp (ref "R719")
      (value "2201")
      (footprint "eagle-import:R0805")
      (fields (field (name "MPN") "RC0805JR-072K2L"))
      (libsource (lib "eagle-import") (part "SMD-RES-2.2K-5%-1/8W(0805)"))
    )
    (comp (ref "R720")
      (value "1002")
      (footprint "eagle-import:R0805")
      (fields (field (name "MPN") "RC0805FR-0710KL"))
      (libsource (lib "eagle-import") (part "SMD-RES-10K-1%-1/8W(0805)"))
    )
    (comp (ref "R721")
      (value "1502")
      (footprint "eagle-import:R0805")
      (fields (field (name "MPN") "RC0805FR-0710KL"))
      (libsource (lib "eagle-import") (part "SMD-RES-10K-1%-1/8W(0805)"))
    )
    (comp (ref "R722")
      (value "2702")
      (footprint "eagle-import:R0805")
      (fields (field (name "MPN") "RC0805JR-074K7L"))
      (libsource (lib "eagle-import") (part "SMD-RES-4.7K-5%-1/8W(0805)"))
    )
    (comp (ref "R723")
      (value "2702")
      (footprint "eagle-import:R0805")
      (fields (field (name "MPN") "RC0805JR-074K7L"))
      (libsource (lib "eagle-import") (part "SMD-RES-4.7K-5%-1/8W(0805)"))
    )
    (comp (ref "R724")
      (value "1002")
      (footprint "eagle-import:R0805")
      (fields (field (name "MPN") "RC0805FR-0710KL"))
      (libsource (lib "eagle-import") (part "SMD-RES-10K-1%-1/8W(0805)"))
    )
    (comp (ref "R725")
      (value "104")
      (footprint "eagle-import:R0805")
      (fields (field (name "MPN") "RC0805FR-0710KL"))
      (libsource (lib "eagle-import") (part "SMD-RES-10K-1%-1/8W(0805)"))
    )
    (comp (ref "R726")
      (value "4701")
      (footprint "eagle-import:R0805")
      (fields (field (name "MPN") "RC0805JR-074K7L"))
      (libsource (lib "eagle-import") (part "SMD-RES-4.7K-5%-1/8W(0805)"))
    )
    (comp (ref "R727")
      (value "47")
      (footprint "eagle-import:V235_17_1MM")
      (libsource (lib "eagle-import") (part "R-EU_V235/17_1MM"))
    )
    (comp (ref "R728")
      (value "102")
      (footprint "eagle-import:R0805")
      (fields (field (name "MPN") "RC0805JR-071KL"))
      (libsource (lib "eagle-import") (part "SMD-RES-1K-5%-1/8W(0805)"))
    )
    (comp (ref "R729")
      (value "47")
      (footprint "eagle-import:V235_17_1MM")
      (libsource (lib "eagle-import") (part "R-EU_V235/17_1MM"))
    )
    (comp (ref "R730")
      (value "104")
      (footprint "eagle-import:R0805")
      (fields (field (name "MPN") "RC0805FR-0710KL"))
      (libsource (lib "eagle-import") (part "SMD-RES-10K-1%-1/8W(0805)"))
    )
    (comp (ref "R731")
      (value "1502")
      (footprint "eagle-import:R0805")
      (fields (field (name "MPN") "RC0805FR-0710KL"))
      (libsource (lib "eagle-import") (part "SMD-RES-10K-1%-1/8W(0805)"))
    )
    (comp (ref "R732")
      (value "1002")
      (footprint "eagle-import:R0805")
      (fields (field (name "MPN") "RC0805FR-0710KL"))
      (libsource (lib "eagle-import") (part "SMD-RES-10K-1%-1/8W(0805)"))
    )
    (comp (ref "R733")
      (value "2201")
      (footprint "eagle-import:R0805")
      (fields (field (name "MPN") "RC0805JR-072K2L"))
      (libsource (lib "eagle-import") (part "SMD-RES-2.2K-5%-1/8W(0805)"))
    )
    (comp (ref "R734")
      (value "13")
      (footprint "eagle-import:R1206")
      (fields (field (name "MPN") "RC1206JR-0713RL"))
      (libsource (lib "eagle-import") (part "SMD-RES-13R-5%-1/4W(1206)"))
    )
    (comp (ref "R735")
      (value "104.")
      (footprint "eagle-import:R0805")
      (fields (field (name "MPN") "RC0805FR-0710KL"))
      (libsource (lib "eagle-import") (part "SMD-RES-10K-1%-1/8W(0805)"))
    )
    (comp (ref "R736")
      (value "47")
      (footprint "eagle-import:V235_17_1MM")
      (libsource (lib "eagle-import") (part "R-EU_V235/17_1MM"))
    )
    (comp (ref "R737")
      (value "47")
      (footprint "eagle-import:V235_17_1MM")
      (libsource (lib "eagle-import") (part "R-EU_V235/17_1MM"))
    )
    (comp (ref "R738")
      (value "100")
      (footprint "eagle-import:R0805")
      (fields (field (name "MPN") "RC0805JR-072K2L"))
      (libsource (lib "eagle-import") (part "SMD-RES-2.2K-5%-1/8W(0805)"))
    )
    (comp (ref "R739")
      (value "(101)")
      (footprint "eagle-import:R0805")
      (fields (field (name "MPN") "RC0805JR-072K2L"))
      (libsource (lib "eagle-import") (part "SMD-RES-2.2K-5%-1/8W(0805)"))
    )
    (comp (ref "R740")
      (value "2702")
      (footprint "eagle-import:R0805")
      (fields (field (name "MPN") "RC0805FR-0710KL"))
      (libsource (lib "eagle-import") (part "SMD-RES-10K-1%-1/8W(0805)"))
    )
    (comp (ref "R741")
      (value "104")
      (footprint "eagle-import:R0805")
      (fields (field (name "MPN") "RC0805FR-0710KL"))
      (libsource (lib "eagle-import") (part "SMD-RES-10K-1%-1/8W(0805)"))
    )
    (comp (ref "R742")
      (value "(1000)")
      (footprint "eagle-import:R0805")
      (fields (field (name "MPN") "RC0805JR-07100RL"))
      (libsource (lib "eagle-import") (part "SMD-RES-100R-5%-1/8W(0805)"))
    )
    (comp (ref "R743")
      (value "(101)")
      (footprint "eagle-import:R0805")
      (fields (field (name "MPN") "RC0805JR-07100RL"))
      (libsource (lib "eagle-import") (part "SMD-RES-100R-5%-1/8W(0805)"))
    )
    (comp (ref "R744")
      (value "(1002)")
      (footprint "eagle-import:R0805")
      (fields (field (name "MPN") "RC0805FR-0710KL"))
      (libsource (lib "eagle-import") (part "SMD-RES-10K-1%-1/8W(0805)"))
    )
    (comp (ref "R745")
      (value "2702")
      (footprint "eagle-import:R0805")
      (fields (field (name "MPN") "RC0805JR-074K7L"))
      (libsource (lib "eagle-import") (part "SMD-RES-4.7K-5%-1/8W(0805)"))
    )
    (comp (ref "R746")
      (value "(1002)")
      (footprint "eagle-import:R0805")
      (fields (field (name "MPN") "RC0805JR-074K7L"))
      (libsource (lib "eagle-import") (part "SMD-RES-4.7K-5%-1/8W(0805)"))
    )
    (comp (ref "SJ701")
      (value "SJ")
      (footprint "eagle-import:SJ")
      (libsource (lib "eagle-import") (part "SJ"))
    )
    (comp (ref "START701")
      (value "TPSB2.0")
      (footprint "eagle-import:B2.0")
      (libsource (lib "eagle-import") (part "TPSB2.0"))
    )
    (comp (ref "TP139")
      (value "TPSB2.0")
      (footprint "eagle-import:B2.0")
      (libsource (lib "eagle-import") (part "TPSB2.0"))
    )
    (comp (ref "TP140")
      (value "TPSB2.0")
      (footprint "eagle-import:B2.0")
      (libsource (lib "eagle-import") (part "TPSB2.0"))
    )
    (comp (ref "TP141")
      (value "TPSB2.0")
      (footprint "eagle-import:B2.0")
      (libsource (lib "eagle-import") (part "TPSB2.0"))
    )
    (comp (ref "TP142")
      (value "TPSB2.0")
      (footprint "eagle-import:B2.0")
      (libsource (lib "eagle-import") (part "TPSB2.0"))
    )
    (comp (ref "TP143")
      (value "TPSB2.0")
      (footprint "eagle-import:B2.0")
      (libsource (lib "eagle-import") (part "TPSB2.0"))
    )
    (comp (ref "TP144")
      (value "TPSB2.0")
      (footprint "eagle-import:B2.0")
      (libsource (lib "eagle-import") (part "TPSB2.0"))
    )
    (comp (ref "TP145")
      (value "TPSB2.0")
      (footprint "eagle-import:B2.0")
      (libsource (lib "eagle-import") (part "TPSB2.0"))
    )
    (comp (ref "TP146")
      (value "TPSB2.0")
      (footprint "eagle-import:B2.0")
      (libsource (lib "eagle-import") (part "TPSB2.0"))
    )
    (comp (ref "TP147")
      (value "TPSB2.0")
      (footprint "eagle-import:B2.0")
      (libsource (lib "eagle-import") (part "TPSB2.0"))
    )
    (comp (ref "TP148")
      (value "TPSB2.0")
      (footprint "eagle-import:B2.0")
      (libsource (lib "eagle-import") (part "TPSB2.0"))
    )
    (comp (ref "TP149")
      (value "TPSB2.0")
      (footprint "eagle-import:B2.0")
      (libsource (lib "eagle-import") (part "TPSB2.0"))
    )
    (comp (ref "TP150")
      (value "TPSB2.0")
      (footprint "eagle-import:B2.0")
      (libsource (lib "eagle-import") (part "TPSB2.0"))
    )
    (comp (ref "TP151")
      (value "TPSB2.0")
      (footprint "eagle-import:B2.0")
      (libsource (lib "eagle-import") (part "TPSB2.0"))
    )
    (comp (ref "TP152")
      (value "TPSB2.0")
      (footprint "eagle-import:B2.0")
      (libsource (lib "eagle-import") (part "TPSB2.0"))
    )
    (comp (ref "TP153")
      (value "TPSB2.0")
      (footprint "eagle-import:B2.0")
      (libsource (lib "eagle-import") (part "TPSB2.0"))
    )
    (comp (ref "TP154")
      (value "TPSB2.0")
      (footprint "eagle-import:B2.0")
      (libsource (lib "eagle-import") (part "TPSB2.0"))
    )
    (comp (ref "TP155")
      (value "TPSB2.0")
      (footprint "eagle-import:B2.0")
      (libsource (lib "eagle-import") (part "TPSB2.0"))
    )
    (comp (ref "TP156")
      (value "TPSB2.0")
      (footprint "eagle-import:B2.0")
      (libsource (lib "eagle-import") (part "TPSB2.0"))
    )
    (comp (ref "TP157")
      (value "TPSB1,27")
      (footprint "eagle-import:B1,27")
      (libsource (lib "eagle-import") (part "TPSB1,27"))
    )
    (comp (ref "TP158")
      (value "TPSB2.0")
      (footprint "eagle-import:B2.0")
      (libsource (lib "eagle-import") (part "TPSB2.0"))
    )
    (comp (ref "TP159")
      (value "TPSB2.0")
      (footprint "eagle-import:B2.0")
      (libsource (lib "eagle-import") (part "TPSB2.0"))
    )
    (comp (ref "TP160")
      (value "TPSB2.0")
      (footprint "eagle-import:B2.0")
      (libsource (lib "eagle-import") (part "TPSB2.0"))
    )
    (comp (ref "TP161")
      (value "TPSB2.0")
      (footprint "eagle-import:B2.0")
      (libsource (lib "eagle-import") (part "TPSB2.0"))
    )
    (comp (ref "X701")
      (value "CON_BMWV2")
      (footprint "eagle-import:24-PIN_V2")
      (libsource (lib "eagle-import") (part "CON_BMWV2"))
    )
    (comp (ref "X702")
      (value "22-23-2021")
      (footprint "eagle-import:22-23-2021")
      (fields (field (name "MF") "MOLEX"))
      (libsource (lib "eagle-import") (part "22-23-2021"))
    )
    (comp (ref "X703")
      (value "22-23-2051")
      (footprint "eagle-import:22-23-2051")
      (fields (field (name "MF") "MOLEX"))
      (libsource (lib "eagle-import") (part "22-23-2051"))
    )
    (comp (ref "6V1101")
      (value "TPSB2.0")
      (footprint "eagle-import:B2.0")
      (libsource (lib "eagle-import") (part "TPSB2.0"))
    )
    (comp (ref "10V1101")
      (value "TPSB2.0")
      (footprint "eagle-import:B2.0")
      (libsource (lib "eagle-import") (part "TPSB2.0"))
    )
    (comp (ref "21")
      (value "2081-1132")
      (footprint "eagle-import:12-PIN")
      (libsource (lib "eagle-import") (part "2081-1132"))
    )
    (comp (ref "22")
      (value "2081-1132")
      (footprint "eagle-import:12-PIN")
      (libsource (lib "eagle-import") (part "2081-1132"))
    )
    (comp (ref "C1101")
      (value "4.7u")
      (footprint "eagle-import:C0805")
      (fields (field (name "MPN") "CC0805KKX5R8BB475"))
      (libsource (lib "eagle-import") (part "CERAMIC-4.7UF-25V-10%-X5R(0805)"))
    )
    (comp (ref "C1102")
      (value "100nF")
      (footprint "eagle-import:C0805")
      (fields (field (name "MPN") "CC0805KRX7R9BB104"))
      (libsource (lib "eagle-import") (part "CERAMIC-100NF-50V-10%-X7R(0805)"))
    )
    (comp (ref "C1103")
      (value "100nF,")
      (footprint "eagle-import:C0805")
      (fields (field (name "MPN") "CC0805KRX7R9BB104"))
      (libsource (lib "eagle-import") (part "CERAMIC-100NF-50V-10%-X7R(0805)"))
    )
    (comp (ref "C1104")
      (value "100nF,")
      (footprint "eagle-import:C0805")
      (fields (field (name "MPN") "CC0805KRX7R9BB104"))
      (libsource (lib "eagle-import") (part "CERAMIC-100NF-50V-10%-X7R(0805)"))
    )
    (comp (ref "C1105")
      (value "100nF.")
      (footprint "eagle-import:C0805")
      (fields (field (name "MPN") "CC0805KRX7R9BB104"))
      (libsource (lib "eagle-import") (part "CERAMIC-100NF-50V-10%-X7R(0805)"))
    )
    (comp (ref "C1106")
      (value "100nF.")
      (footprint "eagle-import:C0805")
      (fields (field (name "MPN") "CC0805KRX7R9BB104"))
      (libsource (lib "eagle-import") (part "CERAMIC-100NF-50V-10%-X7R(0805)"))
    )
    (comp (ref "C1107")
      (value "100u")
      (footprint "eagle-import:C1206")
      (fields (field (name "MPN") "GRM31CR60J107ME39L"))
      (libsource (lib "eagle-import") (part "CERAMIC-100UF-6.3V-20%-X5R(1206)"))
    )
    (comp (ref "C1108")
      (value "100u")
      (footprint "eagle-import:C1206")
      (fields (field (name "MPN") "GRM31CR60J107ME39L"))
      (libsource (lib "eagle-import") (part "CERAMIC-100UF-6.3V-20%-X5R(1206)"))
    )
    (comp (ref "C1109")
      (value "2.2nF")
      (footprint "eagle-import:C0805")
      (fields (field (name "MPN") "CC0805KRX7R9BB104"))
      (libsource (lib "eagle-import") (part "CERAMIC-100NF-50V-10%-X7R(0805)"))
    )
    (comp (ref "C1110")
      (value "100nF")
      (footprint "eagle-import:C0805")
      (fields (field (name "MPN") "CC0805KRX7R9BB104"))
      (libsource (lib "eagle-import") (part "CERAMIC-100NF-50V-10%-X7R(0805)"))
    )
    (comp (ref "D1101")
      (value "SM6T")
      (footprint "eagle-import:DO214AA")
      (libsource (lib "eagle-import") (part "SM6T"))
    )
    (comp (ref "D1102")
      (value "1N4007,")
      (footprint "eagle-import:DO-214AC")
      (fields (field (name "MPN") "1N4007"))
      (libsource (lib "eagle-import") (part "DIODE-GEN-PURPOSE-1KV-1A(DO-214AC)"))
    )
    (comp (ref "D1103")
      (value "1N4007,")
      (footprint "eagle-import:DO-214AC")
      (fields (field (name "MPN") "1N4007"))
      (libsource (lib "eagle-import") (part "DIODE-GEN-PURPOSE-1KV-1A(DO-214AC)"))
    )
    (comp (ref "D1104")
      (value "SM6TDO214AA_BI")
      (footprint "eagle-import:DO214AA_BI")
      (libsource (lib "eagle-import") (part "SM6TDO214AA_BI"))
    )
    (comp (ref "D1105")
      (value "1N4007.")
      (footprint "eagle-import:DO-214AC")
      (fields (field (name "MPN") "1N4007"))
      (libsource (lib "eagle-import") (part "DIODE-GEN-PURPOSE-1KV-1A(DO-214AC)"))
    )
    (comp (ref "D1106")
      (value "1N4007.")
      (footprint "eagle-import:DO-214AC")
      (fields (field (name "MPN") "1N4007"))
      (libsource (lib "eagle-import") (part "DIODE-GEN-PURPOSE-1KV-1A(DO-214AC)"))
    )
    (comp (ref "D1107")
      (value "1N5817")
      (footprint "eagle-import:DO-214AC_SLIM")
      (libsource (lib "eagle-import") (part "DIODE-GEN-PURPOSE-1KV-1A(DO-214AC)DO-214AC/1206"))
    )
    (comp (ref "D1108")
      (value "1N5817.")
      (footprint "eagle-import:DO-214AC_SLIM")
      (libsource (lib "eagle-import") (part "DIODE-GEN-PURPOSE-1KV-1A(DO-214AC)DO-214AC/1206"))
    )
    (comp (ref "D1109")
      (value "1N5817.")
      (footprint "eagle-import:DO-214AC_SLIM")
      (libsource (lib "eagle-import") (part "DIODE-GEN-PURPOSE-1KV-1A(DO-214AC)DO-214AC/1206"))
    )
    (comp (ref "D1110")
      (value "1N5817")
      (footprint "eagle-import:DO-214AC_SLIM")
      (libsource (lib "eagle-import") (part "DIODE-GEN-PURPOSE-1KV-1A(DO-214AC)DO-214AC/1206"))
    )
    (comp (ref "D1111")
      (value "1N4007")
      (footprint "eagle-import:DO-214AC")
      (libsource (lib "eagle-import") (part "DIODE-GEN-PURPOSE-1KV-1A(DO-214AC)"))
    )
    (comp (ref "D1112")
      (value "1N4007")
      (footprint "eagle-import:DO-214AC")
      (libsource (lib "eagle-import") (part "DIODE-GEN-PURPOSE-1KV-1A(DO-214AC)"))
    )
    (comp (ref "FID1101")
      (value "FIDUCIAL")
      (footprint "eagle-import:FIDUCIAL_1MM")
      (libsource (lib "eagle-import") (part "FIDUCIAL"))
    )
    (comp (ref "FID1102")
      (value "FIDUCIAL")
      (footprint "eagle-import:FIDUCIAL_1MM")
      (libsource (lib "eagle-import") (part "FIDUCIAL"))
    )
    (comp (ref "FID1103")
      (value "FIDUCIAL")
      (footprint "eagle-import:FIDUCIAL_1MM")
      (libsource (lib "eagle-import") (part "FIDUCIAL"))
    )
    (comp (ref "FID1104")
      (value "FIDUCIAL")
      (footprint "eagle-import:FIDUCIAL_1MM")
      (libsource (lib "eagle-import") (part "FIDUCIAL"))
    )
    (comp (ref "IC1101")
      (value "LM2904")
      (footprint "eagle-import:SO08")
      (libsource (lib "eagle-import") (part "LM358D"))
    )
    (comp (ref "IC1102")
      (value "78L06")
      (footprint "eagle-import:SOT89_ROUND")
      (libsource (lib "eagle-import") (part "78LXXSOT89_ROUND"))
    )
    (comp (ref "IC1103")
      (value "6V pos")
      (footprint "eagle-import:78LXX")
      (libsource (lib "eagle-import") (part "v-reg_78LXX"))
    )
    (comp (ref "IC1104")
      (value "78L10")
      (footprint "eagle-import:SOT89_ROUND")
      (libsource (lib "eagle-import") (part "78LXXSOT89_ROUND"))
    )
    (comp (ref "IC1105")
      (value "4028")
      (footprint "eagle-import:SO16")
      (libsource (lib "eagle-import") (part "4028D"))
    )
    (comp (ref "IC1106")
      (value "NUP4304SOT457_R")
      (footprint "eagle-import:SOT457R_PHILIPS")
      (libsource (lib "eagle-import") (part "NUP4304SOT457_R"))
    )
    (comp (ref "IC1107")
      (value "ULN2004")
      (footprint "eagle-import:SO16")
      (libsource (lib "eagle-import") (part "ULN2004AD"))
    )
    (comp (ref "IC1108")
      (value "LM339")
      (footprint "eagle-import:SO14")
      (libsource (lib "eagle-import") (part "LM339D"))
    )
    (comp (ref "IC1109")
      (value "317TO202H_NOHOLE")
      (footprint "eagle-import:TO220H_NOHOLE")
      (libsource (lib "eagle-import") (part "317TO202H_NOHOLE"))
    )
    (comp (ref "IC1110")
      (value "555")
      (footprint "eagle-import:SO08")
      (libsource (lib "eagle-import") (part "555DNE"))
    )
    (comp (ref "IC1111")
      (value "4538")
      (footprint "eagle-import:SO16")
      (libsource (lib "eagle-import") (part "4538D"))
    )
    (comp (ref "JP1101")
      (value "JP2EJP2_SMALLPADS")
      (footprint "eagle-import:JP2_SMALLPADS")
      (libsource (lib "eagle-import") (part "JP2EJP2_SMALLPADS"))
    )
    (comp (ref "JP1102")
      (value "JP2EJP2_SMALLPADS")
      (footprint "eagle-import:JP2_SMALLPADS")
      (libsource (lib "eagle-import") (part "JP2EJP2_SMALLPADS"))
    )
    (comp (ref "JP1103")
      (value "JP2EJP2_SMALLPADS")
      (footprint "eagle-import:JP2_SMALLPADS")
      (libsource (lib "eagle-import") (part "JP2EJP2_SMALLPADS"))
    )
    (comp (ref "JP1104")
      (value "JP2EJP2_SMALLPADS")
      (footprint "eagle-import:JP2_SMALLPADS")
      (libsource (lib "eagle-import") (part "JP2EJP2_SMALLPADS"))
    )
    (comp (ref "JP1105")
      (value "JP2E_ORIG")
      (footprint "eagle-import:JP2_ORIG_SMALLPADS")
      (libsource (lib "eagle-import") (part "JP2E_ORIG"))
    )
    (comp (ref "LED1101")
      (value "LEDLD260")
      (footprint "eagle-import:LD260")
      (libsource (lib "eagle-import") (part "LEDLD260"))
    )
    (comp (ref "LED1102")
      (value "LEDLD260")
      (footprint "eagle-import:LD260")
      (libsource (lib "eagle-import") (part "LEDLD260"))
    )
    (comp (ref "LED1103")
      (value "LEDLD260")
      (footprint "eagle-import:LD260")
      (libsource (lib "eagle-import") (part "LEDLD260"))
    )
    (comp (ref "LED1104")
      (value "LEDLD260")
      (footprint "eagle-import:LD260")
      (libsource (lib "eagle-import") (part "LEDLD260"))
    )
    (comp (ref "LED1105")
      (value "LEDLD260")
      (footprint "eagle-import:LD260")
      (libsource (lib "eagle-import") (part "LEDLD260"))
    )
    (comp (ref "LED1106")
      (value "LEDLD260")
      (footprint "eagle-import:LD260")
      (libsource (lib "eagle-import") (part "LEDLD260"))
    )
    (comp (ref "Q1101")
      (value "BA.")
      (footprint "eagle-import:SOT89")
      (libsource (lib "eagle-import") (part "PNP-TRANSISTOR_SOT89"))
    )
    (comp (ref "Q1102")
      (value "BA.")
      (footprint "eagle-import:SOT89")
      (libsource (lib "eagle-import") (part "PNP-TRANSISTOR_SOT89"))
    )
    (comp (ref "Q1103")
      (value "MY")
      (footprint "eagle-import:SOT89")
      (libsource (lib "eagle-import") (part "NPN-TRANSISTOR_SOT89"))
    )
    (comp (ref "Q1104")
      (value "BA")
      (footprint "eagle-import:SOT89")
      (libsource (lib "eagle-import") (part "PNP-TRANSISTOR_SOT89"))
    )
    (comp (ref "Q1105")
      (value "BA")
      (footprint "eagle-import:SOT89")
      (libsource (lib "eagle-import") (part "PNP-TRANSISTOR_SOT89"))
    )
    (comp (ref "Q1106")
      (value "J1")
      (footprint "eagle-import:SOT-23")
      (fields (field (name "MPN") "BSS138W-7-F"))
      (libsource (lib "eagle-import") (part "SMD-MOSFET-N-CH-50V-200MA-BSS138W-7-F(SOT-23)"))
    )
    (comp (ref "Q1107")
      (value "J1")
      (footprint "eagle-import:SOT-23")
      (fields (field (name "MPN") "BSS138W-7-F"))
      (libsource (lib "eagle-import") (part "SMD-MOSFET-N-CH-50V-200MA-BSS138W-7-F(SOT-23)"))
    )
    (comp (ref "R1101")
      (value "102")
      (footprint "eagle-import:R0805")
      (fields (field (name "MPN") "RC0805JR-071KL"))
      (libsource (lib "eagle-import") (part "SMD-RES-1K-5%-1/8W(0805)"))
    )
    (comp (ref "R1102")
      (value "13")
      (footprint "eagle-import:R1206")
      (fields (field (name "MPN") "RC1206JR-0713RL"))
      (libsource (lib "eagle-import") (part "SMD-RES-13R-5%-1/4W(1206)"))
    )
    (comp (ref "R1103")
      (value "R_user")
      (footprint "eagle-import:R0805")
      (libsource (lib "eagle-import") (part "R-EU_R0805"))
    )
    (comp (ref "R1104")
      (value "R_user")
      (footprint "eagle-import:R0805")
      (libsource (lib "eagle-import") (part "R-EU_R0805"))
    )
    (comp (ref "R1105")
      (value "4701")
      (footprint "eagle-import:R0805")
      (fields (field (name "MPN") "RC0805JR-074K7L"))
      (libsource (lib "eagle-import") (part "SMD-RES-4.7K-5%-1/8W(0805)"))
    )
    (comp (ref "R1106")
      (value "13")
      (footprint "eagle-import:R1206")
      (fields (field (name "MPN") "RC1206JR-0713RL"))
      (libsource (lib "eagle-import") (part "SMD-RES-13R-5%-1/4W(1206)"))
    )
    (comp (ref "R1107")
      (value "1002")
      (footprint "eagle-import:R0805")
      (fields (field (name "MPN") "RC0805FR-0710KL"))
      (libsource (lib "eagle-import") (part "SMD-RES-10K-1%-1/8W(0805)"))
    )
    (comp (ref "R1108")
      (value "1002")
      (footprint "eagle-import:R0805")
      (fields (field (name "MPN") "RC0805FR-0710KL"))
      (libsource (lib "eagle-import") (part "SMD-RES-10K-1%-1/8W(0805)"))
    )
    (comp (ref "R1109")
      (value "104.")
      (footprint "eagle-import:R0805")
      (fields (field (name "MPN") "RC0805FR-0710KL"))
      (libsource (lib "eagle-import") (part "SMD-RES-10K-1%-1/8W(0805)"))
    )
    (comp (ref "R1110")
      (value "104.")
      (footprint "eagle-import:R0805")
      (fields (field (name "MPN") "RC0805FR-0710KL"))
      (libsource (lib "eagle-import") (part "SMD-RES-10K-1%-1/8W(0805)"))
    )
    (comp (ref "R1111")
      (value "104.")
      (footprint "eagle-import:R0805")
      (fields (field (name "MPN") "RC0805FR-0710KL"))
      (libsource (lib "eagle-import") (part "SMD-RES-10K-1%-1/8W(0805)"))
    )
    (comp (ref "R1112")
      (value "102")
      (footprint "eagle-import:R0805")
      (fields (field (name "MPN") "RC0805JR-071KL"))
      (libsource (lib "eagle-import") (part "SMD-RES-1K-5%-1/8W(0805)"))
    )
    (comp (ref "R1113")
      (value "102")
      (footprint "eagle-import:R0805")
      (fields (field (name "MPN") "RC0805JR-071KL"))
      (libsource (lib "eagle-import") (part "SMD-RES-1K-5%-1/8W(0805)"))
    )
    (comp (ref "R1114")
      (value "102")
      (footprint "eagle-import:R0805")
      (fields (field (name "MPN") "RC0805JR-071KL"))
      (libsource (lib "eagle-import") (part "SMD-RES-1K-5%-1/8W(0805)"))
    )
    (comp (ref "R1115")
      (value "100")
      (footprint "eagle-import:R0805")
      (fields (field (name "MPN") "RC0805JR-07220RL"))
      (libsource (lib "eagle-import") (part "SMD-RES-220R-5%-1/8W(0805)"))
    )
    (comp (ref "R1116")
      (value "4701")
      (footprint "eagle-import:R0805")
      (fields (field (name "MPN") "RC0805JR-074K7L"))
      (libsource (lib "eagle-import") (part "SMD-RES-4.7K-5%-1/8W(0805)"))
    )
    (comp (ref "R1117")
      (value "2702")
      (footprint "eagle-import:R0805")
      (fields (field (name "MPN") "RC0805JR-074K7L"))
      (libsource (lib "eagle-import") (part "SMD-RES-4.7K-5%-1/8W(0805)"))
    )
    (comp (ref "R1118")
      (value "13")
      (footprint "eagle-import:R1206")
      (fields (field (name "MPN") "RC1206JR-0713RL"))
      (libsource (lib "eagle-import") (part "SMD-RES-13R-5%-1/4W(1206)"))
    )
    (comp (ref "R1119")
      (value "2201")
      (footprint "eagle-import:R0805")
      (fields (field (name "MPN") "RC0805JR-072K2L"))
      (libsource (lib "eagle-import") (part "SMD-RES-2.2K-5%-1/8W(0805)"))
    )
    (comp (ref "R1120")
      (value "1002")
      (footprint "eagle-import:R0805")
      (fields (field (name "MPN") "RC0805FR-0710KL"))
      (libsource (lib "eagle-import") (part "SMD-RES-10K-1%-1/8W(0805)"))
    )
    (comp (ref "R1121")
      (value "1502")
      (footprint "eagle-import:R0805")
      (fields (field (name "MPN") "RC0805FR-0710KL"))
      (libsource (lib "eagle-import") (part "SMD-RES-10K-1%-1/8W(0805)"))
    )
    (comp (ref "R1122")
      (value "2702")
      (footprint "eagle-import:R0805")
      (fields (field (name "MPN") "RC0805JR-074K7L"))
      (libsource (lib "eagle-import") (part "SMD-RES-4.7K-5%-1/8W(0805)"))
    )
    (comp (ref "R1123")
      (value "2702")
      (footprint "eagle-import:R0805")
      (fields (field (name "MPN") "RC0805JR-074K7L"))
      (libsource (lib "eagle-import") (part "SMD-RES-4.7K-5%-1/8W(0805)"))
    )
    (comp (ref "R1124")
      (value "1002")
      (footprint "eagle-import:R0805")
      (fields (field (name "MPN") "RC0805FR-0710KL"))
      (libsource (lib "eagle-import") (part "SMD-RES-10K-1%-1/8W(0805)"))
    )
    (comp (ref "R1125")
      (value "104")
      (footprint "eagle-import:R0805")
      (fields (field (name "MPN") "RC0805FR-0710KL"))
      (libsource (lib "eagle-import") (part "SMD-RES-10K-1%-1/8W(0805)"))
    )
    (comp (ref "R1126")
      (value "4701")
      (footprint "eagle-import:R0805")
      (fields (field (name "MPN") "RC0805JR-074K7L"))
      (libsource (lib "eagle-import") (part "SMD-RES-4.7K-5%-1/8W(0805)"))
    )
    (comp (ref "R1127")
      (value "47")
      (footprint "eagle-import:V235_17_1MM")
      (libsource (lib "eagle-import") (part "R-EU_V235/17_1MM"))
    )
    (comp (ref "R1128")
      (value "102")
      (footprint "eagle-import:R0805")
      (fields (field (name "MPN") "RC0805JR-071KL"))
      (libsource (lib "eagle-import") (part "SMD-RES-1K-5%-1/8W(0805)"))
    )
    (comp (ref "R1129")
      (value "47")
      (footprint "eagle-import:V235_17_1MM")
      (libsource (lib "eagle-import") (part "R-EU_V235/17_1MM"))
    )
    (comp (ref "R1130")
      (value "104")
      (footprint "eagle-import:R0805")
      (fields (field (name "MPN") "RC0805FR-0710KL"))
      (libsource (lib "eagle-import") (part "SMD-RES-10K-1%-1/8W(0805)"))
    )
    (comp (ref "R1131")
      (value "1502")
      (footprint "eagle-import:R0805")
      (fields (field (name "MPN") "RC0805FR-0710KL"))
      (libsource (lib "eagle-import") (part "SMD-RES-10K-1%-1/8W(0805)"))
    )
    (comp (ref "R1132")
      (value "1002")
      (footprint "eagle-import:R0805")
      (fields (field (name "MPN") "RC0805FR-0710KL"))
      (libsource (lib "eagle-import") (part "SMD-RES-10K-1%-1/8W(0805)"))
    )
    (comp (ref "R1133")
      (value "2201")
      (footprint "eagle-import:R0805")
      (fields (field (name "MPN") "RC0805JR-072K2L"))
      (libsource (lib "eagle-import") (part "SMD-RES-2.2K-5%-1/8W(0805)"))
    )
    (comp (ref "R1134")
      (value "13")
      (footprint "eagle-import:R1206")
      (fields (field (name "MPN") "RC1206JR-0713RL"))
      (libsource (lib "eagle-import") (part "SMD-RES-13R-5%-1/4W(1206)"))
    )
    (comp (ref "R1135")
      (value "104.")
      (footprint "eagle-import:R0805")
      (fields (field (name "MPN") "RC0805FR-0710KL"))
      (libsource (lib "eagle-import") (part "SMD-RES-10K-1%-1/8W(0805)"))
    )
    (comp (ref "R1136")
      (value "47")
      (footprint "eagle-import:V235_17_1MM")
      (libsource (lib "eagle-import") (part "R-EU_V235/17_1MM"))
    )
    (comp (ref "R1137")
      (value "47")
      (footprint "eagle-import:V235_17_1MM")
      (libsource (lib "eagle-import") (part "R-EU_V235/17_1MM"))
    )
    (comp (ref "R1138")
      (value "100")
      (footprint "eagle-import:R0805")
      (fields (field (name "MPN") "RC0805JR-072K2L"))
      (libsource (lib "eagle-import") (part "SMD-RES-2.2K-5%-1/8W(0805)"))
    )
    (comp (ref "R1139")
      (value "(101)")
      (footprint "eagle-import:R0805")
      (fields (field (name "MPN") "RC0805JR-072K2L"))
      (libsource (lib "eagle-import") (part "SMD-RES-2.2K-5%-1/8W(0805)"))
    )
    (comp (ref "R1140")
      (value "2702")
      (footprint "eagle-import:R0805")
      (fields (field (name "MPN") "RC0805FR-0710KL"))
      (libsource (lib "eagle-import") (part "SMD-RES-10K-1%-1/8W(0805)"))
    )
    (comp (ref "R1141")
      (value "104")
      (footprint "eagle-import:R0805")
      (fields (field (name "MPN") "RC0805FR-0710KL"))
      (libsource (lib "eagle-import") (part "SMD-RES-10K-1%-1/8W(0805)"))
    )
    (comp (ref "R1142")
      (value "(1000)")
      (footprint "eagle-import:R0805")
      (fields (field (name "MPN") "RC0805JR-07100RL"))
      (libsource (lib "eagle-import") (part "SMD-RES-100R-5%-1/8W(0805)"))
    )
    (comp (ref "R1143")
      (value "(101)")
      (footprint "eagle-import:R0805")
      (fields (field (name "MPN") "RC0805JR-07100RL"))
      (libsource (lib "eagle-import") (part "SMD-RES-100R-5%-1/8W(0805)"))
    )
    (comp (ref "R1144")
      (value "(1002)")
      (footprint "eagle-import:R0805")
      (fields (field (name "MPN") "RC0805FR-0710KL"))
      (libsource (lib "eagle-import") (part "SMD-RES-10K-1%-1/8W(0805)"))
    )
    (comp (ref "R1145")
      (value "2702")
      (footprint "eagle-import:R0805")
      (fields (field (name "MPN") "RC0805JR-074K7L"))
      (libsource (lib "eagle-import") (part "SMD-RES-4.7K-5%-1/8W(0805)"))
    )
    (comp (ref "R1146")
      (value "(1002)")
      (footprint "eagle-import:R0805")
      (fields (field (name "MPN") "RC0805JR-074K7L"))
      (libsource (lib "eagle-import") (part "SMD-RES-4.7K-5%-1/8W(0805)"))
    )
    (comp (ref "SJ1101")
      (value "SJ")
      (footprint "eagle-import:SJ")
      (libsource (lib "eagle-import") (part "SJ"))
    )
    (comp (ref "START1101")
      (value "TPSB2.0")
      (footprint "eagle-import:B2.0")
      (libsource (lib "eagle-import") (part "TPSB2.0"))
    )
    (comp (ref "TP231")
      (value "TPSB2.0")
      (footprint "eagle-import:B2.0")
      (libsource (lib "eagle-import") (part "TPSB2.0"))
    )
    (comp (ref "TP232")
      (value "TPSB2.0")
      (footprint "eagle-import:B2.0")
      (libsource (lib "eagle-import") (part "TPSB2.0"))
    )
    (comp (ref "TP233")
      (value "TPSB2.0")
      (footprint "eagle-import:B2.0")
      (libsource (lib "eagle-import") (part "TPSB2.0"))
    )
    (comp (ref "TP234")
      (value "TPSB2.0")
      (footprint "eagle-import:B2.0")
      (libsource (lib "eagle-import") (part "TPSB2.0"))
    )
    (comp (ref "TP235")
      (value "TPSB2.0")
      (footprint "eagle-import:B2.0")
      (libsource (lib "eagle-import") (part "TPSB2.0"))
    )
    (comp (ref "TP236")
      (value "TPSB2.0")
      (footprint "eagle-import:B2.0")
      (libsource (lib "eagle-import") (part "TPSB2.0"))
    )
    (comp (ref "TP237")
      (value "TPSB2.0")
      (footprint "eagle-import:B2.0")
      (libsource (lib "eagle-import") (part "TPSB2.0"))
    )
    (comp (ref "TP238")
      (value "TPSB2.0")
      (footprint "eagle-import:B2.0")
      (libsource (lib "eagle-import") (part "TPSB2.0"))
    )
    (comp (ref "TP239")
      (value "TPSB2.0")
      (footprint "eagle-import:B2.0")
      (libsource (lib "eagle-import") (part "TPSB2.0"))
    )
    (comp (ref "TP240")
      (value "TPSB2.0")
      (footprint "eagle-import:B2.0")
      (libsource (lib "eagle-import") (part "TPSB2.0"))
    )
    (comp (ref "TP241")
      (value "TPSB2.0")
      (footprint "eagle-import:B2.0")
      (libsource (lib "eagle-import") (part "TPSB2.0"))
    )
    (comp (ref "TP242")
      (value "TPSB2.0")
      (footprint "eagle-import:B2.0")
      (libsource (lib "eagle-import") (part "TPSB2.0"))
    )
    (comp (ref "TP243")
      (value "TPSB2.0")
      (footprint "eagle-import:B2.0")
      (libsource (lib "eagle-import") (part "TPSB2.0"))
    )
    (comp (ref "TP244")
      (value "TPSB2.0")
      (footprint "eagle-import:B2.0")
      (libsource (lib "eagle-import") (part "TPSB2.0"))
    )
    (comp (ref "TP245")
      (value "TPSB2.0")
      (footprint "eagle-import:B2.0")
      (libsource (lib "eagle-import") (part "TPSB2.0"))
    )
    (comp (ref "TP246")
      (value "TPSB2.0")
      (footprint "eagle-import:B2.0")
      (libsource (lib "eagle-import") (part "TPSB2.0"))
    )
    (comp (ref "TP247")
      (value "TPSB2.0")
      (footprint "eagle-import:B2.0")
      (libsource (lib "eagle-import") (part "TPSB2.0"))
    )
    (comp (ref "TP248")
      (value "TPSB2.0")
      (footprint "eagle-import:B2.0")
      (libsource (lib "eagle-import") (part "TPSB2.0"))
    )
    (comp (ref "TP249")
      (value "TPSB1,27")
      (footprint "eagle-import:B1,27")
      (libsource (lib "eagle-import") (part "TPSB1,27"))
    )
    (comp (ref "TP250")
      (value "TPSB2.0")
      (footprint "eagle-import:B2.0")
      (libsource (lib "eagle-import") (part "TPSB2.0"))
    )
    (comp (ref "TP251")
      (value "TPSB2.0")
      (footprint "eagle-import:B2.0")
      (libsource (lib "eagle-import") (part "TPSB2.0"))
    )
    (comp (ref "TP252")
      (value "TPSB2.0")
      (footprint "eagle-import:B2.0")
      (libsource (lib "eagle-import") (part "TPSB2.0"))
    )
    (comp (ref "TP253")
      (value "TPSB2.0")
      (footprint "eagle-import:B2.0")
      (libsource (lib "eagle-import") (part "TPSB2.0"))
    )
    (comp (ref "X1101")
      (value "CON_BMWV2")
      (footprint "eagle-import:24-PIN_V2")
      (libsource (lib "eagle-import") (part "CON_BMWV2"))
    )
    (comp (ref "X1102")
      (value "22-23-2021")
      (footprint "eagle-import:22-23-2021")
      (fields (field (name "MF") "MOLEX"))
      (libsource (lib "eagle-import") (part "22-23-2021"))
    )
    (comp (ref "X1103")
      (value "22-23-2051")
      (footprint "eagle-import:22-23-2051")
      (fields (field (name "MF") "MOLEX"))
      (libsource (lib "eagle-import") (part "22-23-2051"))
    )
  )
  (nets
    (net (code "1") (name "+10V") (class "Default")
      (node (ref "10V") (pin "TP") (pinfunction "PP_TP") (pintype "input"))
      (node (ref "10V1001") (pin "TP") (pinfunction "PP_TP") (pintype "input"))
      (node (ref "10V1101") (pin "TP") (pinfunction "PP_TP") (pintype "input"))
      (node (ref "10V1201") (pin "TP") (pinfunction "PP_TP") (pintype "input"))
      (node (ref "10V201") (pin "TP") (pinfunction "PP_TP") (pintype "input"))
      (node (ref "10V301") (pin "TP") (pinfunction "PP_TP") (pintype "input"))
      (node (ref "10V401") (pin "TP") (pinfunction "PP_TP") (pintype "input"))
      (node (ref "10V501") (pin "TP") (pinfunction "PP_TP") (pintype "input"))
      (node (ref "10V601") (pin "TP") (pinfunction "PP_TP") (pintype "input"))
      (node (ref "10V701") (pin "TP") (pinfunction "PP_TP") (pintype "input"))
      (node (ref "10V801") (pin "TP") (pinfunction "PP_TP") (pintype "input"))
      (node (ref "10V901") (pin "TP") (pinfunction "PP_TP") (pintype "input"))
      (node (ref "C1002") (pin "1") (pinfunction "1_1") (pintype "passive"))
      (node (ref "C102") (pin "1") (pinfunction "1_1") (pintype "passive"))
      (node (ref "C1102") (pin "1") (pinfunction "1_1") (pintype "passive"))
      (node (ref "C1202") (pin "1") (pinfunction "1_1") (pintype "passive"))
      (node (ref "C202") (pin "1") (pinfunction "1_1") (pintype "passive"))
      (node (ref "C302") (pin "1") (pinfunction "1_1") (pintype "passive"))
      (node (ref "C402") (pin "1") (pinfunction "1_1") (pintype "passive"))
      (node (ref "C502") (pin "1") (pinfunction "1_1") (pintype "passive"))
      (node (ref "C602") (pin "1") (pinfunction "1_1") (pintype "passive"))
      (node (ref "C702") (pin "1") (pinfunction "1_1") (pintype "passive"))
      (node (ref "C802") (pin "1") (pinfunction "1_1") (pintype "passive"))
      (node (ref "C902") (pin "1") (pinfunction "1_1") (pintype "passive"))
      (node (ref "IC1004") (pin "1") (pinfunction "OUT_1") (pintype "passive"))
      (node (ref "IC1010") (pin "4") (pinfunction "R_4") (pintype "input"))
      (node (ref "IC1010") (pin "8") (pinfunction "V+_8") (pintype "power_in"))
      (node (ref "IC1011") (pin "13") (pinfunction "CD_13") (pintype "input"))
      (node (ref "IC1011") (pin "16") (pinfunction "VDD_16") (pintype "power_in"))
      (node (ref "IC1011") (pin "3") (pinfunction "CD_3") (pintype "input"))
      (node (ref "IC1011") (pin "5") (pinfunction "B_5") (pintype "input"))
      (node (ref "IC104") (pin "1") (pinfunction "OUT_1") (pintype "passive"))
      (node (ref "IC110") (pin "4") (pinfunction "R_4") (pintype "input"))
      (node (ref "IC110") (pin "8") (pinfunction "V+_8") (pintype "power_in"))
      (node (ref "IC1104") (pin "1") (pinfunction "OUT_1") (pintype "passive"))
      (node (ref "IC111") (pin "13") (pinfunction "CD_13") (pintype "input"))
      (node (ref "IC111") (pin "16") (pinfunction "VDD_16") (pintype "power_in"))
      (node (ref "IC111") (pin "3") (pinfunction "CD_3") (pintype "input"))
      (node (ref "IC111") (pin "5") (pinfunction "B_5") (pintype "input"))
      (node (ref "IC1110") (pin "4") (pinfunction "R_4") (pintype "input"))
      (node (ref "IC1110") (pin "8") (pinfunction "V+_8") (pintype "power_in"))
      (node (ref "IC1111") (pin "13") (pinfunction "CD_13") (pintype "input"))
      (node (ref "IC1111") (pin "16") (pinfunction "VDD_16") (pintype "power_in"))
      (node (ref "IC1111") (pin "3") (pinfunction "CD_3") (pintype "input"))
      (node (ref "IC1111") (pin "5") (pinfunction "B_5") (pintype "input"))
      (node (ref "IC1204") (pin "1") (pinfunction "OUT_1") (pintype "passive"))
      (node (ref "IC1210") (pin "4") (pinfunction "R_4") (pintype "input"))
      (node (ref "IC1210") (pin "8") (pinfunction "V+_8") (pintype "power_in"))
      (node (ref "IC1211") (pin "13") (pinfunction "CD_13") (pintype "input"))
      (node (ref "IC1211") (pin "16") (pinfunction "VDD_16") (pintype "power_in"))
      (node (ref "IC1211") (pin "3") (pinfunction "CD_3") (pintype "input"))
      (node (ref "IC1211") (pin "5") (pinfunction "B_5") (pintype "input"))
      (node (ref "IC204") (pin "1") (pinfunction "OUT_1") (pintype "passive"))
      (node (ref "IC210") (pin "4") (pinfunction "R_4") (pintype "input"))
      (node (ref "IC210") (pin "8") (pinfunction "V+_8") (pintype "power_in"))
      (node (ref "IC211") (pin "13") (pinfunction "CD_13") (pintype "input"))
      (node (ref "IC211") (pin "16") (pinfunction "VDD_16") (pintype "power_in"))
      (node (ref "IC211") (pin "3") (pinfunction "CD_3") (pintype "input"))
      (node (ref "IC211") (pin "5") (pinfunction "B_5") (pintype "input"))
      (node (ref "IC304") (pin "1") (pinfunction "OUT_1") (pintype "passive"))
      (node (ref "IC310") (pin "4") (pinfunction "R_4") (pintype "input"))
      (node (ref "IC310") (pin "8") (pinfunction "V+_8") (pintype "power_in"))
      (node (ref "IC311") (pin "13") (pinfunction "CD_13") (pintype "input"))
      (node (ref "IC311") (pin "16") (pinfunction "VDD_16") (pintype "power_in"))
      (node (ref "IC311") (pin "3") (pinfunction "CD_3") (pintype "input"))
      (node (ref "IC311") (pin "5") (pinfunction "B_5") (pintype "input"))
      (node (ref "IC404") (pin "1") (pinfunction "OUT_1") (pintype "passive"))
      (node (ref "IC410") (pin "4") (pinfunction "R_4") (pintype "input"))
      (node (ref "IC410") (pin "8") (pinfunction "V+_8") (pintype "power_in"))
      (node (ref "IC411") (pin "13") (pinfunction "CD_13") (pintype "input"))
      (node (ref "IC411") (pin "16") (pinfunction "VDD_16") (pintype "power_in"))
      (node (ref "IC411") (pin "3") (pinfunction "CD_3") (pintype "input"))
      (node (ref "IC411") (pin "5") (pinfunction "B_5") (pintype "input"))
      (node (ref "IC504") (pin "1") (pinfunction "OUT_1") (pintype "passive"))
      (node (ref "IC510") (pin "4") (pinfunction "R_4") (pintype "input"))
      (node (ref "IC510") (pin "8") (pinfunction "V+_8") (pintype "power_in"))
      (node (ref "IC511") (pin "13") (pinfunction "CD_13") (pintype "input"))
      (node (ref "IC511") (pin "16") (pinfunction "VDD_16") (pintype "power_in"))
      (node (ref "IC511") (pin "3") (pinfunction "CD_3") (pintype "input"))
      (node (ref "IC511") (pin "5") (pinfunction "B_5") (pintype "input"))
      (node (ref "IC604") (pin "1") (pinfunction "OUT_1") (pintype "passive"))
      (node (ref "IC610") (pin "4") (pinfunction "R_4") (pintype "input"))
      (node (ref "IC610") (pin "8") (pinfunction "V+_8") (pintype "power_in"))
      (node (ref "IC611") (pin "13") (pinfunction "CD_13") (pintype "input"))
      (node (ref "IC611") (pin "16") (pinfunction "VDD_16") (pintype "power_in"))
      (node (ref "IC611") (pin "3") (pinfunction "CD_3") (pintype "input"))
      (node (ref "IC611") (pin "5") (pinfunction "B_5") (pintype "input"))
      (node (ref "IC704") (pin "1") (pinfunction "OUT_1") (pintype "passive"))
      (node (ref "IC710") (pin "4") (pinfunction "R_4") (pintype "input"))
      (node (ref "IC710") (pin "8") (pinfunction "V+_8") (pintype "power_in"))
      (node (ref "IC711") (pin "13") (pinfunction "CD_13") (pintype "input"))
      (node (ref "IC711") (pin "16") (pinfunction "VDD_16") (pintype "power_in"))
      (node (ref "IC711") (pin "3") (pinfunction "CD_3") (pintype "input"))
      (node (ref "IC711") (pin "5") (pinfunction "B_5") (pintype "input"))
      (node (ref "IC804") (pin "1") (pinfunction "OUT_1") (pintype "passive"))
      (node (ref "IC810") (pin "4") (pinfunction "R_4") (pintype "input"))
      (node (ref "IC810") (pin "8") (pinfunction "V+_8") (pintype "power_in"))
      (node (ref "IC811") (pin "13") (pinfunction "CD_13") (pintype "input"))
      (node (ref "IC811") (pin "16") (pinfunction "VDD_16") (pintype "power_in"))
      (node (ref "IC811") (pin "3") (pinfunction "CD_3") (pintype "input"))
      (node (ref "IC811") (pin "5") (pinfunction "B_5") (pintype "input"))
      (node (ref "IC904") (pin "1") (pinfunction "OUT_1") (pintype "passive"))
      (node (ref "IC910") (pin "4") (pinfunction "R_4") (pintype "input"))
      (node (ref "IC910") (pin "8") (pinfunction "V+_8") (pintype "power_in"))
      (node (ref "IC911") (pin "13") (pinfunction "CD_13") (pintype "input"))
      (node (ref "IC911") (pin "16") (pinfunction "VDD_16") (pintype "power_in"))
      (node (ref "IC911") (pin "3") (pinfunction "CD_3") (pintype "input"))
      (node (ref "IC911") (pin "5") (pinfunction "B_5") (pintype "input"))
      (node (ref "R1045") (pin "2") (pinfunction "2_2") (pintype "passive"))
      (node (ref "R1145") (pin "2") (pinfunction "2_2") (pintype "passive"))
      (node (ref "R1245") (pin "2") (pinfunction "2_2") (pintype "passive"))
      (node (ref "R145") (pin "2") (pinfunction "2_2") (pintype "passive"))
      (node (ref "R245") (pin "2") (pinfunction "2_2") (pintype "passive"))
      (node (ref "R345") (pin "2") (pinfunction "2_2") (pintype "passive"))
      (node (ref "R445") (pin "2") (pinfunction "2_2") (pintype "passive"))
      (node (ref "R545") (pin "2") (pinfunction "2_2") (pintype "passive"))
      (node (ref "R645") (pin "2") (pinfunction "2_2") (pintype "passive"))
      (node (ref "R745") (pin "2") (pinfunction "2_2") (pintype "passive"))
      (node (ref "R845") (pin "2") (pinfunction "2_2") (pintype "passive"))
      (node (ref "R945") (pin "2") (pinfunction "2_2") (pintype "passive"))
    )
    (net (code "2") (name "+12V") (class "Default")
      (node (ref "10") (pin "1") (pinfunction "KL_1") (pintype "passive"))
      (node (ref "12") (pin "1") (pinfunction "KL_1") (pintype "passive"))
      (node (ref "14") (pin "1") (pinfunction "KL_1") (pintype "passive"))
      (node (ref "16") (pin "1") (pinfunction "KL_1") (pintype "passive"))
      (node (ref "18") (pin "1") (pinfunction "KL_1") (pintype "passive"))
      (node (ref "2") (pin "1") (pinfunction "KL_1") (pintype "passive"))
      (node (ref "20") (pin "1") (pinfunction "KL_1") (pintype "passive"))
      (node (ref "22") (pin "1") (pinfunction "KL_1") (pintype "passive"))
      (node (ref "24") (pin "1") (pinfunction "KL_1") (pintype "passive"))
      (node (ref "4") (pin "1") (pinfunction "KL_1") (pintype "passive"))
      (node (ref "6") (pin "1") (pinfunction "KL_1") (pintype "passive"))
      (node (ref "8") (pin "1") (pinfunction "KL_1") (pintype "passive"))
      (node (ref "D1001") (pin "C") (pinfunction "C_C") (pintype "passive"))
      (node (ref "D101") (pin "C") (pinfunction "C_C") (pintype "passive"))
      (node (ref "D1101") (pin "C") (pinfunction "C_C") (pintype "passive"))
      (node (ref "D1201") (pin "C") (pinfunction "C_C") (pintype "passive"))
      (node (ref "D201") (pin "C") (pinfunction "C_C") (pintype "passive"))
      (node (ref "D301") (pin "C") (pinfunction "C_C") (pintype "passive"))
      (node (ref "D401") (pin "C") (pinfunction "C_C") (pintype "passive"))
      (node (ref "D501") (pin "C") (pinfunction "C_C") (pintype "passive"))
      (node (ref "D601") (pin "C") (pinfunction "C_C") (pintype "passive"))
      (node (ref "D701") (pin "C") (pinfunction "C_C") (pintype "passive"))
      (node (ref "D801") (pin "C") (pinfunction "C_C") (pintype "passive"))
      (node (ref "D901") (pin "C") (pinfunction "C_C") (pintype "passive"))
      (node (ref "IC1002") (pin "3") (pinfunction "IN_3") (pintype "input"))
      (node (ref "IC1003") (pin "IN") (pinfunction "IN_IN") (pintype "input"))
      (node (ref "IC1004") (pin "3") (pinfunction "IN_3") (pintype "input"))
      (node (ref "IC1005") (pin "16") (pinfunction "VDD_16") (pintype "power_in"))
      (node (ref "IC1006") (pin "2") (pinfunction "V+_2") (pintype "passive"))
      (node (ref "IC1007") (pin "9") (pinfunction "CD+_9") (pintype "passive"))
      (node (ref "IC102") (pin "3") (pinfunction "IN_3") (pintype "input"))
      (node (ref "IC103") (pin "IN") (pinfunction "IN_IN") (pintype "input"))
      (node (ref "IC104") (pin "3") (pinfunction "IN_3") (pintype "input"))
      (node (ref "IC105") (pin "16") (pinfunction "VDD_16") (pintype "power_in"))
      (node (ref "IC106") (pin "2") (pinfunction "V+_2") (pintype "passive"))
      (node (ref "IC107") (pin "9") (pinfunction "CD+_9") (pintype "passive"))
      (node (ref "IC1102") (pin "3") (pinfunction "IN_3") (pintype "input"))
      (node (ref "IC1103") (pin "IN") (pinfunction "IN_IN") (pintype "input"))
      (node (ref "IC1104") (pin "3") (pinfunction "IN_3") (pintype "input"))
      (node (ref "IC1105") (pin "16") (pinfunction "VDD_16") (pintype "power_in"))
      (node (ref "IC1106") (pin "2") (pinfunction "V+_2") (pintype "passive"))
      (node (ref "IC1107") (pin "9") (pinfunction "CD+_9") (pintype "passive"))
      (node (ref "IC1202") (pin "3") (pinfunction "IN_3") (pintype "input"))
      (node (ref "IC1203") (pin "IN") (pinfunction "IN_IN") (pintype "input"))
      (node (ref "IC1204") (pin "3") (pinfunction "IN_3") (pintype "input"))
      (node (ref "IC1205") (pin "16") (pinfunction "VDD_16") (pintype "power_in"))
      (node (ref "IC1206") (pin "2") (pinfunction "V+_2") (pintype "passive"))
      (node (ref "IC1207") (pin "9") (pinfunction "CD+_9") (pintype "passive"))
      (node (ref "IC202") (pin "3") (pinfunction "IN_3") (pintype "input"))
      (node (ref "IC203") (pin "IN") (pinfunction "IN_IN") (pintype "input"))
      (node (ref "IC204") (pin "3") (pinfunction "IN_3") (pintype "input"))
      (node (ref "IC205") (pin "16") (pinfunction "VDD_16") (pintype "power_in"))
      (node (ref "IC206") (pin "2") (pinfunction "V+_2") (pintype "passive"))
      (node (ref "IC207") (pin "9") (pinfunction "CD+_9") (pintype "passive"))
      (node (ref "IC302") (pin "3") (pinfunction "IN_3") (pintype "input"))
      (node (ref "IC303") (pin "IN") (pinfunction "IN_IN") (pintype "input"))
      (node (ref "IC304") (pin "3") (pinfunction "IN_3") (pintype "input"))
      (node (ref "IC305") (pin "16") (pinfunction "VDD_16") (pintype "power_in"))
      (node (ref "IC306") (pin "2") (pinfunction "V+_2") (pintype "passive"))
      (node (ref "IC307") (pin "9") (pinfunction "CD+_9") (pintype "passive"))
      (node (ref "IC402") (pin "3") (pinfunction "IN_3") (pintype "input"))
      (node (ref "IC403") (pin "IN") (pinfunction "IN_IN") (pintype "input"))
      (node (ref "IC404") (pin "3") (pinfunction "IN_3") (pintype "input"))
      (node (ref "IC405") (pin "16") (pinfunction "VDD_16") (pintype "power_in"))
      (node (ref "IC406") (pin "2") (pinfunction "V+_2") (pintype "passive"))
      (node (ref "IC407") (pin "9") (pinfunction "CD+_9") (pintype "passive"))
      (node (ref "IC502") (pin "3") (pinfunction "IN_3") (pintype "input"))
      (node (ref "IC503") (pin "IN") (pinfunction "IN_IN") (pintype "input"))
      (node (ref "IC504") (pin "3") (pinfunction "IN_3") (pintype "input"))
      (node (ref "IC505") (pin "16") (pinfunction "VDD_16") (pintype "power_in"))
      (node (ref "IC506") (pin "2") (pinfunction "V+_2") (pintype "passive"))
      (node (ref "IC507") (pin "9") (pinfunction "CD+_9") (pintype "passive"))
      (node (ref "IC602") (pin "3") (pinfunction "IN_3") (pintype "input"))
      (node (ref "IC603") (pin "IN") (pinfunction "IN_IN") (pintype "input"))
      (node (ref "IC604") (pin "3") (pinfunction "IN_3") (pintype "input"))
      (node (ref "IC605") (pin "16") (pinfunction "VDD_16") (pintype "power_in"))
      (node (ref "IC606") (pin "2") (pinfunction "V+_2") (pintype "passive"))
      (node (ref "IC607") (pin "9") (pinfunction "CD+_9") (pintype "passive"))
      (node (ref "IC702") (pin "3") (pinfunction "IN_3") (pintype "input"))
      (node (ref "IC703") (pin "IN") (pinfunction "IN_IN") (pintype "input"))
      (node (ref "IC704") (pin "3") (pinfunction "IN_3") (pintype "input"))
      (node (ref "IC705") (pin "16") (pinfunction "VDD_16") (pintype "power_in"))
      (node (ref "IC706") (pin "2") (pinfunction "V+_2") (pintype "passive"))
      (node (ref "IC707") (pin "9") (pinfunction "CD+_9") (pintype "passive"))
      (node (ref "IC802") (pin "3") (pinfunction "IN_3") (pintype "input"))
      (node (ref "IC803") (pin "IN") (pinfunction "IN_IN") (pintype "input"))
      (node (ref "IC804") (pin "3") (pinfunction "IN_3") (pintype "input"))
      (node (ref "IC805") (pin "16") (pinfunction "VDD_16") (pintype "power_in"))
      (node (ref "IC806") (pin "2") (pinfunction "V+_2") (pintype "passive"))
      (node (ref "IC807") (pin "9") (pinfunction "CD+_9") (pintype "passive"))
      (node (ref "IC902") (pin "3") (pinfunction "IN_3") (pintype "input"))
      (node (ref "IC903") (pin "IN") (pinfunction "IN_IN") (pintype "input"))
      (node (ref "IC904") (pin "3") (pinfunction "IN_3") (pintype "input"))
      (node (ref "IC905") (pin "16") (pinfunction "VDD_16") (pintype "power_in"))
      (node (ref "IC906") (pin "2") (pinfunction "V+_2") (pintype "passive"))
      (node (ref "IC907") (pin "9") (pinfunction "CD+_9") (pintype "passive"))
      (node (ref "JP1001") (pin "2") (pinfunction "2_2") (pintype "passive"))
      (node (ref "JP101") (pin "2") (pinfunction "2_2") (pintype "passive"))
      (node (ref "JP1101") (pin "2") (pinfunction "2_2") (pintype "passive"))
      (node (ref "JP1201") (pin "2") (pinfunction "2_2") (pintype "passive"))
      (node (ref "JP201") (pin "2") (pinfunction "2_2") (pintype "passive"))
      (node (ref "JP301") (pin "2") (pinfunction "2_2") (pintype "passive"))
      (node (ref "JP401") (pin "2") (pinfunction "2_2") (pintype "passive"))
      (node (ref "JP501") (pin "2") (pinfunction "2_2") (pintype "passive"))
      (node (ref "JP601") (pin "2") (pinfunction "2_2") (pintype "passive"))
      (node (ref "JP701") (pin "2") (pinfunction "2_2") (pintype "passive"))
      (node (ref "JP801") (pin "2") (pinfunction "2_2") (pintype "passive"))
      (node (ref "JP901") (pin "2") (pinfunction "2_2") (pintype "passive"))
      (node (ref "Q1004") (pin "3") (pinfunction "E_3") (pintype "passive"))
      (node (ref "Q1005") (pin "3") (pinfunction "E_3") (pintype "passive"))
      (node (ref "Q104") (pin "3") (pinfunction "E_3") (pintype "passive"))
      (node (ref "Q105") (pin "3") (pinfunction "E_3") (pintype "passive"))
      (node (ref "Q1104") (pin "3") (pinfunction "E_3") (pintype "passive"))
      (node (ref "Q1105") (pin "3") (pinfunction "E_3") (pintype "passive"))
      (node (ref "Q1204") (pin "3") (pinfunction "E_3") (pintype "passive"))
      (node (ref "Q1205") (pin "3") (pinfunction "E_3") (pintype "passive"))
      (node (ref "Q204") (pin "3") (pinfunction "E_3") (pintype "passive"))
      (node (ref "Q205") (pin "3") (pinfunction "E_3") (pintype "passive"))
      (node (ref "Q304") (pin "3") (pinfunction "E_3") (pintype "passive"))
      (node (ref "Q305") (pin "3") (pinfunction "E_3") (pintype "passive"))
      (node (ref "Q404") (pin "3") (pinfunction "E_3") (pintype "passive"))
      (node (ref "Q405") (pin "3") (pinfunction "E_3") (pintype "passive"))
      (node (ref "Q504") (pin "3") (pinfunction "E_3") (pintype "passive"))
      (node (ref "Q505") (pin "3") (pinfunction "E_3") (pintype "passive"))
      (node (ref "Q604") (pin "3") (pinfunction "E_3") (pintype "passive"))
      (node (ref "Q605") (pin "3") (pinfunction "E_3") (pintype "passive"))
      (node (ref "Q704") (pin "3") (pinfunction "E_3") (pintype "passive"))
      (node (ref "Q705") (pin "3") (pinfunction "E_3") (pintype "passive"))
      (node (ref "Q804") (pin "3") (pinfunction "E_3") (pintype "passive"))
      (node (ref "Q805") (pin "3") (pinfunction "E_3") (pintype "passive"))
      (node (ref "Q904") (pin "3") (pinfunction "E_3") (pintype "passive"))
      (node (ref "Q905") (pin "3") (pinfunction "E_3") (pintype "passive"))
      (node (ref "R1002") (pin "1") (pinfunction "1_1") (pintype "passive"))
      (node (ref "R1006") (pin "1") (pinfunction "1_1") (pintype "passive"))
      (node (ref "R1009") (pin "2") (pinfunction "2_2") (pintype "passive"))
      (node (ref "R1010") (pin "2") (pinfunction "2_2") (pintype "passive"))
      (node (ref "R1011") (pin "2") (pinfunction "2_2") (pintype "passive"))
      (node (ref "R102") (pin "1") (pinfunction "1_1") (pintype "passive"))
      (node (ref "R1029") (pin "2") (pinfunction "2_2") (pintype "passive"))
      (node (ref "R1035") (pin "1") (pinfunction "1_1") (pintype "passive"))
      (node (ref "R106") (pin "1") (pinfunction "1_1") (pintype "passive"))
      (node (ref "R109") (pin "2") (pinfunction "2_2") (pintype "passive"))
      (node (ref "R110") (pin "2") (pinfunction "2_2") (pintype "passive"))
      (node (ref "R1102") (pin "1") (pinfunction "1_1") (pintype "passive"))
      (node (ref "R1106") (pin "1") (pinfunction "1_1") (pintype "passive"))
      (node (ref "R1109") (pin "2") (pinfunction "2_2") (pintype "passive"))
      (node (ref "R111") (pin "2") (pinfunction "2_2") (pintype "passive"))
      (node (ref "R1110") (pin "2") (pinfunction "2_2") (pintype "passive"))
      (node (ref "R1111") (pin "2") (pinfunction "2_2") (pintype "passive"))
      (node (ref "R1129") (pin "2") (pinfunction "2_2") (pintype "passive"))
      (node (ref "R1135") (pin "1") (pinfunction "1_1") (pintype "passive"))
      (node (ref "R1202") (pin "1") (pinfunction "1_1") (pintype "passive"))
      (node (ref "R1206") (pin "1") (pinfunction "1_1") (pintype "passive"))
      (node (ref "R1209") (pin "2") (pinfunction "2_2") (pintype "passive"))
      (node (ref "R1210") (pin "2") (pinfunction "2_2") (pintype "passive"))
      (node (ref "R1211") (pin "2") (pinfunction "2_2") (pintype "passive"))
      (node (ref "R1229") (pin "2") (pinfunction "2_2") (pintype "passive"))
      (node (ref "R1235") (pin "1") (pinfunction "1_1") (pintype "passive"))
      (node (ref "R129") (pin "2") (pinfunction "2_2") (pintype "passive"))
      (node (ref "R135") (pin "1") (pinfunction "1_1") (pintype "passive"))
      (node (ref "R202") (pin "1") (pinfunction "1_1") (pintype "passive"))
      (node (ref "R206") (pin "1") (pinfunction "1_1") (pintype "passive"))
      (node (ref "R209") (pin "2") (pinfunction "2_2") (pintype "passive"))
      (node (ref "R210") (pin "2") (pinfunction "2_2") (pintype "passive"))
      (node (ref "R211") (pin "2") (pinfunction "2_2") (pintype "passive"))
      (node (ref "R229") (pin "2") (pinfunction "2_2") (pintype "passive"))
      (node (ref "R235") (pin "1") (pinfunction "1_1") (pintype "passive"))
      (node (ref "R302") (pin "1") (pinfunction "1_1") (pintype "passive"))
      (node (ref "R306") (pin "1") (pinfunction "1_1") (pintype "passive"))
      (node (ref "R309") (pin "2") (pinfunction "2_2") (pintype "passive"))
      (node (ref "R310") (pin "2") (pinfunction "2_2") (pintype "passive"))
      (node (ref "R311") (pin "2") (pinfunction "2_2") (pintype "passive"))
      (node (ref "R329") (pin "2") (pinfunction "2_2") (pintype "passive"))
      (node (ref "R335") (pin "1") (pinfunction "1_1") (pintype "passive"))
      (node (ref "R402") (pin "1") (pinfunction "1_1") (pintype "passive"))
      (node (ref "R406") (pin "1") (pinfunction "1_1") (pintype "passive"))
      (node (ref "R409") (pin "2") (pinfunction "2_2") (pintype "passive"))
      (node (ref "R410") (pin "2") (pinfunction "2_2") (pintype "passive"))
      (node (ref "R411") (pin "2") (pinfunction "2_2") (pintype "passive"))
      (node (ref "R429") (pin "2") (pinfunction "2_2") (pintype "passive"))
      (node (ref "R435") (pin "1") (pinfunction "1_1") (pintype "passive"))
      (node (ref "R502") (pin "1") (pinfunction "1_1") (pintype "passive"))
      (node (ref "R506") (pin "1") (pinfunction "1_1") (pintype "passive"))
      (node (ref "R509") (pin "2") (pinfunction "2_2") (pintype "passive"))
      (node (ref "R510") (pin "2") (pinfunction "2_2") (pintype "passive"))
      (node (ref "R511") (pin "2") (pinfunction "2_2") (pintype "passive"))
      (node (ref "R529") (pin "2") (pinfunction "2_2") (pintype "passive"))
      (node (ref "R535") (pin "1") (pinfunction "1_1") (pintype "passive"))
      (node (ref "R602") (pin "1") (pinfunction "1_1") (pintype "passive"))
      (node (ref "R606") (pin "1") (pinfunction "1_1") (pintype "passive"))
      (node (ref "R609") (pin "2") (pinfunction "2_2") (pintype "passive"))
      (node (ref "R610") (pin "2") (pinfunction "2_2") (pintype "passive"))
      (node (ref "R611") (pin "2") (pinfunction "2_2") (pintype "passive"))
      (node (ref "R629") (pin "2") (pinfunction "2_2") (pintype "passive"))
      (node (ref "R635") (pin "1") (pinfunction "1_1") (pintype "passive"))
      (node (ref "R702") (pin "1") (pinfunction "1_1") (pintype "passive"))
      (node (ref "R706") (pin "1") (pinfunction "1_1") (pintype "passive"))
      (node (ref "R709") (pin "2") (pinfunction "2_2") (pintype "passive"))
      (node (ref "R710") (pin "2") (pinfunction "2_2") (pintype "passive"))
      (node (ref "R711") (pin "2") (pinfunction "2_2") (pintype "passive"))
      (node (ref "R729") (pin "2") (pinfunction "2_2") (pintype "passive"))
      (node (ref "R735") (pin "1") (pinfunction "1_1") (pintype "passive"))
      (node (ref "R802") (pin "1") (pinfunction "1_1") (pintype "passive"))
      (node (ref "R806") (pin "1") (pinfunction "1_1") (pintype "passive"))
      (node (ref "R809") (pin "2") (pinfunction "2_2") (pintype "passive"))
      (node (ref "R810") (pin "2") (pinfunction "2_2") (pintype "passive"))
      (node (ref "R811") (pin "2") (pinfunction "2_2") (pintype "passive"))
      (node (ref "R829") (pin "2") (pinfunction "2_2") (pintype "passive"))
      (node (ref "R835") (pin "1") (pinfunction "1_1") (pintype "passive"))
      (node (ref "R902") (pin "1") (pinfunction "1_1") (pintype "passive"))
      (node (ref "R906") (pin "1") (pinfunction "1_1") (pintype "passive"))
      (node (ref "R909") (pin "2") (pinfunction "2_2") (pintype "passive"))
      (node (ref "R910") (pin "2") (pinfunction "2_2") (pintype "passive"))
      (node (ref "R911") (pin "2") (pinfunction "2_2") (pintype "passive"))
      (node (ref "R929") (pin "2") (pinfunction "2_2") (pintype "passive"))
      (node (ref "R935") (pin "1") (pinfunction "1_1") (pintype "passive"))
      (node (ref "TP114") (pin "TP") (pinfunction "PP_TP") (pintype "input"))
      (node (ref "TP12") (pin "TP") (pinfunction "PP_TP") (pintype "input"))
      (node (ref "TP137") (pin "TP") (pinfunction "PP_TP") (pintype "input"))
      (node (ref "TP160") (pin "TP") (pinfunction "PP_TP") (pintype "input"))
      (node (ref "TP183") (pin "TP") (pinfunction "PP_TP") (pintype "input"))
      (node (ref "TP206") (pin "TP") (pinfunction "PP_TP") (pintype "input"))
      (node (ref "TP229") (pin "TP") (pinfunction "PP_TP") (pintype "input"))
      (node (ref "TP252") (pin "TP") (pinfunction "PP_TP") (pintype "input"))
      (node (ref "TP275") (pin "TP") (pinfunction "PP_TP") (pintype "input"))
      (node (ref "TP45") (pin "TP") (pinfunction "PP_TP") (pintype "input"))
      (node (ref "TP68") (pin "TP") (pinfunction "PP_TP") (pintype "input"))
      (node (ref "TP91") (pin "TP") (pinfunction "PP_TP") (pintype "input"))
      (node (ref "X1001") (pin "6") (pinfunction "6_6") (pintype "passive"))
      (node (ref "X1003") (pin "1") (pinfunction "S_1") (pintype "passive"))
      (node (ref "X101") (pin "6") (pinfunction "6_6") (pintype "passive"))
      (node (ref "X103") (pin "1") (pinfunction "S_1") (pintype "passive"))
      (node (ref "X1101") (pin "6") (pinfunction "6_6") (pintype "passive"))
      (node (ref "X1103") (pin "1") (pinfunction "S_1") (pintype "passive"))
      (node (ref "X1201") (pin "6") (pinfunction "6_6") (pintype "passive"))
      (node (ref "X1203") (pin "1") (pinfunction "S_1") (pintype "passive"))
      (node (ref "X201") (pin "6") (pinfunction "6_6") (pintype "passive"))
      (node (ref "X203") (pin "1") (pinfunction "S_1") (pintype "passive"))
      (node (ref "X301") (pin "6") (pinfunction "6_6") (pintype "passive"))
      (node (ref "X303") (pin "1") (pinfunction "S_1") (pintype "passive"))
      (node (ref "X401") (pin "6") (pinfunction "6_6") (pintype "passive"))
      (node (ref "X403") (pin "1") (pinfunction "S_1") (pintype "passive"))
      (node (ref "X501") (pin "6") (pinfunction "6_6") (pintype "passive"))
      (node (ref "X503") (pin "1") (pinfunction "S_1") (pintype "passive"))
      (node (ref "X601") (pin "6") (pinfunction "6_6") (pintype "passive"))
      (node (ref "X603") (pin "1") (pinfunction "S_1") (pintype "passive"))
      (node (ref "X701") (pin "6") (pinfunction "6_6") (pintype "passive"))
      (node (ref "X703") (pin "1") (pinfunction "S_1") (pintype "passive"))
      (node (ref "X801") (pin "6") (pinfunction "6_6") (pintype "passive"))
      (node (ref "X803") (pin "1") (pinfunction "S_1") (pintype "passive"))
      (node (ref "X901") (pin "6") (pinfunction "6_6") (pintype "passive"))
      (node (ref "X903") (pin "1") (pinfunction "S_1") (pintype "passive"))
    )
    (net (code "3") (name "GND") (class "Default")
      (node (ref "1") (pin "12") (pinfunction "KL_12") (pintype "passive"))
      (node (ref "11") (pin "12") (pinfunction "KL_12") (pintype "passive"))
      (node (ref "13") (pin "12") (pinfunction "KL_12") (pintype "passive"))
      (node (ref "15") (pin "12") (pinfunction "KL_12") (pintype "passive"))
      (node (ref "17") (pin "12") (pinfunction "KL_12") (pintype "passive"))
      (node (ref "19") (pin "12") (pinfunction "KL_12") (pintype "passive"))
      (node (ref "21") (pin "12") (pinfunction "KL_12") (pintype "passive"))
      (node (ref "23") (pin "12") (pinfunction "KL_12") (pintype "passive"))
      (node (ref "3") (pin "12") (pinfunction "KL_12") (pintype "passive"))
      (node (ref "5") (pin "12") (pinfunction "KL_12") (pintype "passive"))
      (node (ref "7") (pin "12") (pinfunction "KL_12") (pintype "passive"))
      (node (ref "9") (pin "12") (pinfunction "KL_12") (pintype "passive"))
      (node (ref "C1001") (pin "2") (pinfunction "2_2") (pintype "passive"))
      (node (ref "C1002") (pin "2") (pinfunction "2_2") (pintype "passive"))
      (node (ref "C1003") (pin "2") (pinfunction "2_2") (pintype "passive"))
      (node (ref "C1004") (pin "2") (pinfunction "2_2") (pintype "passive"))
      (node (ref "C1005") (pin "2") (pinfunction "2_2") (pintype "passive"))
      (node (ref "C1006") (pin "1") (pinfunction "1_1") (pintype "passive"))
      (node (ref "C1007") (pin "2") (pinfunction "2_2") (pintype "passive"))
      (node (ref "C1008") (pin "2") (pinfunction "2_2") (pintype "passive"))
      (node (ref "C1009") (pin "1") (pinfunction "1_1") (pintype "passive"))
      (node (ref "C101") (pin "2") (pinfunction "2_2") (pintype "passive"))
      (node (ref "C1010") (pin "2") (pinfunction "2_2") (pintype "passive"))
      (node (ref "C102") (pin "2") (pinfunction "2_2") (pintype "passive"))
      (node (ref "C103") (pin "2") (pinfunction "2_2") (pintype "passive"))
      (node (ref "C104") (pin "2") (pinfunction "2_2") (pintype "passive"))
      (node (ref "C105") (pin "2") (pinfunction "2_2") (pintype "passive"))
      (node (ref "C106") (pin "1") (pinfunction "1_1") (pintype "passive"))
      (node (ref "C107") (pin "2") (pinfunction "2_2") (pintype "passive"))
      (node (ref "C108") (pin "2") (pinfunction "2_2") (pintype "passive"))
      (node (ref "C109") (pin "1") (pinfunction "1_1") (pintype "passive"))
      (node (ref "C110") (pin "2") (pinfunction "2_2") (pintype "passive"))
      (node (ref "C1101") (pin "2") (pinfunction "2_2") (pintype "passive"))
      (node (ref "C1102") (pin "2") (pinfunction "2_2") (pintype "passive"))
      (node (ref "C1103") (pin "2") (pinfunction "2_2") (pintype "passive"))
      (node (ref "C1104") (pin "2") (pinfunction "2_2") (pintype "passive"))
      (node (ref "C1105") (pin "2") (pinfunction "2_2") (pintype "passive"))
      (node (ref "C1106") (pin "1") (pinfunction "1_1") (pintype "passive"))
      (node (ref "C1107") (pin "2") (pinfunction "2_2") (pintype "passive"))
      (node (ref "C1108") (pin "2") (pinfunction "2_2") (pintype "passive"))
      (node (ref "C1109") (pin "1") (pinfunction "1_1") (pintype "passive"))
      (node (ref "C1110") (pin "2") (pinfunction "2_2") (pintype "passive"))
      (node (ref "C1201") (pin "2") (pinfunction "2_2") (pintype "passive"))
      (node (ref "C1202") (pin "2") (pinfunction "2_2") (pintype "passive"))
      (node (ref "C1203") (pin "2") (pinfunction "2_2") (pintype "passive"))
      (node (ref "C1204") (pin "2") (pinfunction "2_2") (pintype "passive"))
      (node (ref "C1205") (pin "2") (pinfunction "2_2") (pintype "passive"))
      (node (ref "C1206") (pin "1") (pinfunction "1_1") (pintype "passive"))
      (node (ref "C1207") (pin "2") (pinfunction "2_2") (pintype "passive"))
      (node (ref "C1208") (pin "2") (pinfunction "2_2") (pintype "passive"))
      (node (ref "C1209") (pin "1") (pinfunction "1_1") (pintype "passive"))
      (node (ref "C1210") (pin "2") (pinfunction "2_2") (pintype "passive"))
      (node (ref "C201") (pin "2") (pinfunction "2_2") (pintype "passive"))
      (node (ref "C202") (pin "2") (pinfunction "2_2") (pintype "passive"))
      (node (ref "C203") (pin "2") (pinfunction "2_2") (pintype "passive"))
      (node (ref "C204") (pin "2") (pinfunction "2_2") (pintype "passive"))
      (node (ref "C205") (pin "2") (pinfunction "2_2") (pintype "passive"))
      (node (ref "C206") (pin "1") (pinfunction "1_1") (pintype "passive"))
      (node (ref "C207") (pin "2") (pinfunction "2_2") (pintype "passive"))
      (node (ref "C208") (pin "2") (pinfunction "2_2") (pintype "passive"))
      (node (ref "C209") (pin "1") (pinfunction "1_1") (pintype "passive"))
      (node (ref "C210") (pin "2") (pinfunction "2_2") (pintype "passive"))
      (node (ref "C301") (pin "2") (pinfunction "2_2") (pintype "passive"))
      (node (ref "C302") (pin "2") (pinfunction "2_2") (pintype "passive"))
      (node (ref "C303") (pin "2") (pinfunction "2_2") (pintype "passive"))
      (node (ref "C304") (pin "2") (pinfunction "2_2") (pintype "passive"))
      (node (ref "C305") (pin "2") (pinfunction "2_2") (pintype "passive"))
      (node (ref "C306") (pin "1") (pinfunction "1_1") (pintype "passive"))
      (node (ref "C307") (pin "2") (pinfunction "2_2") (pintype "passive"))
      (node (ref "C308") (pin "2") (pinfunction "2_2") (pintype "passive"))
      (node (ref "C309") (pin "1") (pinfunction "1_1") (pintype "passive"))
      (node (ref "C310") (pin "2") (pinfunction "2_2") (pintype "passive"))
      (node (ref "C401") (pin "2") (pinfunction "2_2") (pintype "passive"))
      (node (ref "C402") (pin "2") (pinfunction "2_2") (pintype "passive"))
      (node (ref "C403") (pin "2") (pinfunction "2_2") (pintype "passive"))
      (node (ref "C404") (pin "2") (pinfunction "2_2") (pintype "passive"))
      (node (ref "C405") (pin "2") (pinfunction "2_2") (pintype "passive"))
      (node (ref "C406") (pin "1") (pinfunction "1_1") (pintype "passive"))
      (node (ref "C407") (pin "2") (pinfunction "2_2") (pintype "passive"))
      (node (ref "C408") (pin "2") (pinfunction "2_2") (pintype "passive"))
      (node (ref "C409") (pin "1") (pinfunction "1_1") (pintype "passive"))
      (node (ref "C410") (pin "2") (pinfunction "2_2") (pintype "passive"))
      (node (ref "C501") (pin "2") (pinfunction "2_2") (pintype "passive"))
      (node (ref "C502") (pin "2") (pinfunction "2_2") (pintype "passive"))
      (node (ref "C503") (pin "2") (pinfunction "2_2") (pintype "passive"))
      (node (ref "C504") (pin "2") (pinfunction "2_2") (pintype "passive"))
      (node (ref "C505") (pin "2") (pinfunction "2_2") (pintype "passive"))
      (node (ref "C506") (pin "1") (pinfunction "1_1") (pintype "passive"))
      (node (ref "C507") (pin "2") (pinfunction "2_2") (pintype "passive"))
      (node (ref "C508") (pin "2") (pinfunction "2_2") (pintype "passive"))
      (node (ref "C509") (pin "1") (pinfunction "1_1") (pintype "passive"))
      (node (ref "C510") (pin "2") (pinfunction "2_2") (pintype "passive"))
      (node (ref "C601") (pin "2") (pinfunction "2_2") (pintype "passive"))
      (node (ref "C602") (pin "2") (pinfunction "2_2") (pintype "passive"))
      (node (ref "C603") (pin "2") (pinfunction "2_2") (pintype "passive"))
      (node (ref "C604") (pin "2") (pinfunction "2_2") (pintype "passive"))
      (node (ref "C605") (pin "2") (pinfunction "2_2") (pintype "passive"))
      (node (ref "C606") (pin "1") (pinfunction "1_1") (pintype "passive"))
      (node (ref "C607") (pin "2") (pinfunction "2_2") (pintype "passive"))
      (node (ref "C608") (pin "2") (pinfunction "2_2") (pintype "passive"))
      (node (ref "C609") (pin "1") (pinfunction "1_1") (pintype "passive"))
      (node (ref "C610") (pin "2") (pinfunction "2_2") (pintype "passive"))
      (node (ref "C701") (pin "2") (pinfunction "2_2") (pintype "passive"))
      (node (ref "C702") (pin "2") (pinfunction "2_2") (pintype "passive"))
      (node (ref "C703") (pin "2") (pinfunction "2_2") (pintype "passive"))
      (node (ref "C704") (pin "2") (pinfunction "2_2") (pintype "passive"))
      (node (ref "C705") (pin "2") (pinfunction "2_2") (pintype "passive"))
      (node (ref "C706") (pin "1") (pinfunction "1_1") (pintype "passive"))
      (node (ref "C707") (pin "2") (pinfunction "2_2") (pintype "passive"))
      (node (ref "C708") (pin "2") (pinfunction "2_2") (pintype "passive"))
      (node (ref "C709") (pin "1") (pinfunction "1_1") (pintype "passive"))
      (node (ref "C710") (pin "2") (pinfunction "2_2") (pintype "passive"))
      (node (ref "C801") (pin "2") (pinfunction "2_2") (pintype "passive"))
      (node (ref "C802") (pin "2") (pinfunction "2_2") (pintype "passive"))
      (node (ref "C803") (pin "2") (pinfunction "2_2") (pintype "passive"))
      (node (ref "C804") (pin "2") (pinfunction "2_2") (pintype "passive"))
      (node (ref "C805") (pin "2") (pinfunction "2_2") (pintype "passive"))
      (node (ref "C806") (pin "1") (pinfunction "1_1") (pintype "passive"))
      (node (ref "C807") (pin "2") (pinfunction "2_2") (pintype "passive"))
      (node (ref "C808") (pin "2") (pinfunction "2_2") (pintype "passive"))
      (node (ref "C809") (pin "1") (pinfunction "1_1") (pintype "passive"))
      (node (ref "C810") (pin "2") (pinfunction "2_2") (pintype "passive"))
      (node (ref "C901") (pin "2") (pinfunction "2_2") (pintype "passive"))
      (node (ref "C902") (pin "2") (pinfunction "2_2") (pintype "passive"))
      (node (ref "C903") (pin "2") (pinfunction "2_2") (pintype "passive"))
      (node (ref "C904") (pin "2") (pinfunction "2_2") (pintype "passive"))
      (node (ref "C905") (pin "2") (pinfunction "2_2") (pintype "passive"))
      (node (ref "C906") (pin "1") (pinfunction "1_1") (pintype "passive"))
      (node (ref "C907") (pin "2") (pinfunction "2_2") (pintype "passive"))
      (node (ref "C908") (pin "2") (pinfunction "2_2") (pintype "passive"))
      (node (ref "C909") (pin "1") (pinfunction "1_1") (pintype "passive"))
      (node (ref "C910") (pin "2") (pinfunction "2_2") (pintype "passive"))
      (node (ref "D1001") (pin "A") (pinfunction "A_A") (pintype "passive"))
      (node (ref "D1004") (pin "A") (pinfunction "A_A") (pintype "passive"))
      (node (ref "D1005") (pin "1") (pinfunction "+_1") (pintype "passive"))
      (node (ref "D101") (pin "A") (pinfunction "A_A") (pintype "passive"))
      (node (ref "D104") (pin "A") (pinfunction "A_A") (pintype "passive"))
      (node (ref "D105") (pin "1") (pinfunction "+_1") (pintype "passive"))
      (node (ref "D1101") (pin "A") (pinfunction "A_A") (pintype "passive"))
      (node (ref "D1104") (pin "A") (pinfunction "A_A") (pintype "passive"))
      (node (ref "D1105") (pin "1") (pinfunction "+_1") (pintype "passive"))
      (node (ref "D1201") (pin "A") (pinfunction "A_A") (pintype "passive"))
      (node (ref "D1204") (pin "A") (pinfunction "A_A") (pintype "passive"))
      (node (ref "D1205") (pin "1") (pinfunction "+_1") (pintype "passive"))
      (node (ref "D201") (pin "A") (pinfunction "A_A") (pintype "passive"))
      (node (ref "D204") (pin "A") (pinfunction "A_A") (pintype "passive"))
      (node (ref "D205") (pin "1") (pinfunction "+_1") (pintype "passive"))
      (node (ref "D301") (pin "A") (pinfunction "A_A") (pintype "passive"))
      (node (ref "D304") (pin "A") (pinfunction "A_A") (pintype "passive"))
      (node (ref "D305") (pin "1") (pinfunction "+_1") (pintype "passive"))
      (node (ref "D401") (pin "A") (pinfunction "A_A") (pintype "passive"))
      (node (ref "D404") (pin "A") (pinfunction "A_A") (pintype "passive"))
      (node (ref "D405") (pin "1") (pinfunction "+_1") (pintype "passive"))
      (node (ref "D501") (pin "A") (pinfunction "A_A") (pintype "passive"))
      (node (ref "D504") (pin "A") (pinfunction "A_A") (pintype "passive"))
      (node (ref "D505") (pin "1") (pinfunction "+_1") (pintype "passive"))
      (node (ref "D601") (pin "A") (pinfunction "A_A") (pintype "passive"))
      (node (ref "D604") (pin "A") (pinfunction "A_A") (pintype "passive"))
      (node (ref "D605") (pin "1") (pinfunction "+_1") (pintype "passive"))
      (node (ref "D701") (pin "A") (pinfunction "A_A") (pintype "passive"))
      (node (ref "D704") (pin "A") (pinfunction "A_A") (pintype "passive"))
      (node (ref "D705") (pin "1") (pinfunction "+_1") (pintype "passive"))
      (node (ref "D801") (pin "A") (pinfunction "A_A") (pintype "passive"))
      (node (ref "D804") (pin "A") (pinfunction "A_A") (pintype "passive"))
      (node (ref "D805") (pin "1") (pinfunction "+_1") (pintype "passive"))
      (node (ref "D901") (pin "A") (pinfunction "A_A") (pintype "passive"))
      (node (ref "D904") (pin "A") (pinfunction "A_A") (pintype "passive"))
      (node (ref "D905") (pin "1") (pinfunction "+_1") (pintype "passive"))
      (node (ref "IC1001") (pin "4") (pinfunction "V-_4") (pintype "power_in"))
      (node (ref "IC1002") (pin "2") (pinfunction "GND_2") (pintype "input"))
      (node (ref "IC1002") (pin "2@1") (pinfunction "GND_2@1") (pintype "input"))
      (node (ref "IC1003") (pin "GND") (pinfunction "GND_GND") (pintype "input"))
      (node (ref "IC1004") (pin "2") (pinfunction "GND_2") (pintype "input"))
      (node (ref "IC1004") (pin "2@1") (pinfunction "GND_2@1") (pintype "input"))
      (node (ref "IC1005") (pin "11") (pinfunction "D_11") (pintype "input"))
      (node (ref "IC1005") (pin "8") (pinfunction "VSS_8") (pintype "power_in"))
      (node (ref "IC1006") (pin "5") (pinfunction "V-_5") (pintype "passive"))
      (node (ref "IC1007") (pin "8") (pinfunction "GND_8") (pintype "power_in"))
      (node (ref "IC1008") (pin "10") (pinfunction "-IN_10") (pintype "input"))
      (node (ref "IC1008") (pin "11") (pinfunction "+IN_11") (pintype "input"))
      (node (ref "IC1008") (pin "12") (pinfunction "GND_12") (pintype "power_in"))
      (node (ref "IC101") (pin "4") (pinfunction "V-_4") (pintype "power_in"))
      (node (ref "IC1010") (pin "1") (pinfunction "GND_1") (pintype "power_in"))
      (node (ref "IC1011") (pin "1") (pinfunction "T1_1") (pintype "input"))
      (node (ref "IC1011") (pin "15") (pinfunction "T1_15") (pintype "input"))
      (node (ref "IC1011") (pin "4") (pinfunction "A_4") (pintype "input"))
      (node (ref "IC1011") (pin "8") (pinfunction "VSS_8") (pintype "power_in"))
      (node (ref "IC102") (pin "2") (pinfunction "GND_2") (pintype "input"))
      (node (ref "IC102") (pin "2@1") (pinfunction "GND_2@1") (pintype "input"))
      (node (ref "IC103") (pin "GND") (pinfunction "GND_GND") (pintype "input"))
      (node (ref "IC104") (pin "2") (pinfunction "GND_2") (pintype "input"))
      (node (ref "IC104") (pin "2@1") (pinfunction "GND_2@1") (pintype "input"))
      (node (ref "IC105") (pin "11") (pinfunction "D_11") (pintype "input"))
      (node (ref "IC105") (pin "8") (pinfunction "VSS_8") (pintype "power_in"))
      (node (ref "IC106") (pin "5") (pinfunction "V-_5") (pintype "passive"))
      (node (ref "IC107") (pin "8") (pinfunction "GND_8") (pintype "power_in"))
      (node (ref "IC108") (pin "10") (pinfunction "-IN_10") (pintype "input"))
      (node (ref "IC108") (pin "11") (pinfunction "+IN_11") (pintype "input"))
      (node (ref "IC108") (pin "12") (pinfunction "GND_12") (pintype "power_in"))
      (node (ref "IC110") (pin "1") (pinfunction "GND_1") (pintype "power_in"))
      (node (ref "IC1101") (pin "4") (pinfunction "V-_4") (pintype "power_in"))
      (node (ref "IC1102") (pin "2") (pinfunction "GND_2") (pintype "input"))
      (node (ref "IC1102") (pin "2@1") (pinfunction "GND_2@1") (pintype "input"))
      (node (ref "IC1103") (pin "GND") (pinfunction "GND_GND") (pintype "input"))
      (node (ref "IC1104") (pin "2") (pinfunction "GND_2") (pintype "input"))
      (node (ref "IC1104") (pin "2@1") (pinfunction "GND_2@1") (pintype "input"))
      (node (ref "IC1105") (pin "11") (pinfunction "D_11") (pintype "input"))
      (node (ref "IC1105") (pin "8") (pinfunction "VSS_8") (pintype "power_in"))
      (node (ref "IC1106") (pin "5") (pinfunction "V-_5") (pintype "passive"))
      (node (ref "IC1107") (pin "8") (pinfunction "GND_8") (pintype "power_in"))
      (node (ref "IC1108") (pin "10") (pinfunction "-IN_10") (pintype "input"))
      (node (ref "IC1108") (pin "11") (pinfunction "+IN_11") (pintype "input"))
      (node (ref "IC1108") (pin "12") (pinfunction "GND_12") (pintype "power_in"))
      (node (ref "IC111") (pin "1") (pinfunction "T1_1") (pintype "input"))
      (node (ref "IC111") (pin "15") (pinfunction "T1_15") (pintype "input"))
      (node (ref "IC111") (pin "4") (pinfunction "A_4") (pintype "input"))
      (node (ref "IC111") (pin "8") (pinfunction "VSS_8") (pintype "power_in"))
      (node (ref "IC1110") (pin "1") (pinfunction "GND_1") (pintype "power_in"))
      (node (ref "IC1111") (pin "1") (pinfunction "T1_1") (pintype "input"))
      (node (ref "IC1111") (pin "15") (pinfunction "T1_15") (pintype "input"))
      (node (ref "IC1111") (pin "4") (pinfunction "A_4") (pintype "input"))
      (node (ref "IC1111") (pin "8") (pinfunction "VSS_8") (pintype "power_in"))
      (node (ref "IC1201") (pin "4") (pinfunction "V-_4") (pintype "power_in"))
      (node (ref "IC1202") (pin "2") (pinfunction "GND_2") (pintype "input"))
      (node (ref "IC1202") (pin "2@1") (pinfunction "GND_2@1") (pintype "input"))
      (node (ref "IC1203") (pin "GND") (pinfunction "GND_GND") (pintype "input"))
      (node (ref "IC1204") (pin "2") (pinfunction "GND_2") (pintype "input"))
      (node (ref "IC1204") (pin "2@1") (pinfunction "GND_2@1") (pintype "input"))
      (node (ref "IC1205") (pin "11") (pinfunction "D_11") (pintype "input"))
      (node (ref "IC1205") (pin "8") (pinfunction "VSS_8") (pintype "power_in"))
      (node (ref "IC1206") (pin "5") (pinfunction "V-_5") (pintype "passive"))
      (node (ref "IC1207") (pin "8") (pinfunction "GND_8") (pintype "power_in"))
      (node (ref "IC1208") (pin "10") (pinfunction "-IN_10") (pintype "input"))
      (node (ref "IC1208") (pin "11") (pinfunction "+IN_11") (pintype "input"))
      (node (ref "IC1208") (pin "12") (pinfunction "GND_12") (pintype "power_in"))
      (node (ref "IC1210") (pin "1") (pinfunction "GND_1") (pintype "power_in"))
      (node (ref "IC1211") (pin "1") (pinfunction "T1_1") (pintype "input"))
      (node (ref "IC1211") (pin "15") (pinfunction "T1_15") (pintype "input"))
      (node (ref "IC1211") (pin "4") (pinfunction "A_4") (pintype "input"))
      (node (ref "IC1211") (pin "8") (pinfunction "VSS_8") (pintype "power_in"))
      (node (ref "IC201") (pin "4") (pinfunction "V-_4") (pintype "power_in"))
      (node (ref "IC202") (pin "2") (pinfunction "GND_2") (pintype "input"))
      (node (ref "IC202") (pin "2@1") (pinfunction "GND_2@1") (pintype "input"))
      (node (ref "IC203") (pin "GND") (pinfunction "GND_GND") (pintype "input"))
      (node (ref "IC204") (pin "2") (pinfunction "GND_2") (pintype "input"))
      (node (ref "IC204") (pin "2@1") (pinfunction "GND_2@1") (pintype "input"))
      (node (ref "IC205") (pin "11") (pinfunction "D_11") (pintype "input"))
      (node (ref "IC205") (pin "8") (pinfunction "VSS_8") (pintype "power_in"))
      (node (ref "IC206") (pin "5") (pinfunction "V-_5") (pintype "passive"))
      (node (ref "IC207") (pin "8") (pinfunction "GND_8") (pintype "power_in"))
      (node (ref "IC208") (pin "10") (pinfunction "-IN_10") (pintype "input"))
      (node (ref "IC208") (pin "11") (pinfunction "+IN_11") (pintype "input"))
      (node (ref "IC208") (pin "12") (pinfunction "GND_12") (pintype "power_in"))
      (node (ref "IC210") (pin "1") (pinfunction "GND_1") (pintype "power_in"))
      (node (ref "IC211") (pin "1") (pinfunction "T1_1") (pintype "input"))
      (node (ref "IC211") (pin "15") (pinfunction "T1_15") (pintype "input"))
      (node (ref "IC211") (pin "4") (pinfunction "A_4") (pintype "input"))
      (node (ref "IC211") (pin "8") (pinfunction "VSS_8") (pintype "power_in"))
      (node (ref "IC301") (pin "4") (pinfunction "V-_4") (pintype "power_in"))
      (node (ref "IC302") (pin "2") (pinfunction "GND_2") (pintype "input"))
      (node (ref "IC302") (pin "2@1") (pinfunction "GND_2@1") (pintype "input"))
      (node (ref "IC303") (pin "GND") (pinfunction "GND_GND") (pintype "input"))
      (node (ref "IC304") (pin "2") (pinfunction "GND_2") (pintype "input"))
      (node (ref "IC304") (pin "2@1") (pinfunction "GND_2@1") (pintype "input"))
      (node (ref "IC305") (pin "11") (pinfunction "D_11") (pintype "input"))
      (node (ref "IC305") (pin "8") (pinfunction "VSS_8") (pintype "power_in"))
      (node (ref "IC306") (pin "5") (pinfunction "V-_5") (pintype "passive"))
      (node (ref "IC307") (pin "8") (pinfunction "GND_8") (pintype "power_in"))
      (node (ref "IC308") (pin "10") (pinfunction "-IN_10") (pintype "input"))
      (node (ref "IC308") (pin "11") (pinfunction "+IN_11") (pintype "input"))
      (node (ref "IC308") (pin "12") (pinfunction "GND_12") (pintype "power_in"))
      (node (ref "IC310") (pin "1") (pinfunction "GND_1") (pintype "power_in"))
      (node (ref "IC311") (pin "1") (pinfunction "T1_1") (pintype "input"))
      (node (ref "IC311") (pin "15") (pinfunction "T1_15") (pintype "input"))
      (node (ref "IC311") (pin "4") (pinfunction "A_4") (pintype "input"))
      (node (ref "IC311") (pin "8") (pinfunction "VSS_8") (pintype "power_in"))
      (node (ref "IC401") (pin "4") (pinfunction "V-_4") (pintype "power_in"))
      (node (ref "IC402") (pin "2") (pinfunction "GND_2") (pintype "input"))
      (node (ref "IC402") (pin "2@1") (pinfunction "GND_2@1") (pintype "input"))
      (node (ref "IC403") (pin "GND") (pinfunction "GND_GND") (pintype "input"))
      (node (ref "IC404") (pin "2") (pinfunction "GND_2") (pintype "input"))
      (node (ref "IC404") (pin "2@1") (pinfunction "GND_2@1") (pintype "input"))
      (node (ref "IC405") (pin "11") (pinfunction "D_11") (pintype "input"))
      (node (ref "IC405") (pin "8") (pinfunction "VSS_8") (pintype "power_in"))
      (node (ref "IC406") (pin "5") (pinfunction "V-_5") (pintype "passive"))
      (node (ref "IC407") (pin "8") (pinfunction "GND_8") (pintype "power_in"))
      (node (ref "IC408") (pin "10") (pinfunction "-IN_10") (pintype "input"))
      (node (ref "IC408") (pin "11") (pinfunction "+IN_11") (pintype "input"))
      (node (ref "IC408") (pin "12") (pinfunction "GND_12") (pintype "power_in"))
      (node (ref "IC410") (pin "1") (pinfunction "GND_1") (pintype "power_in"))
      (node (ref "IC411") (pin "1") (pinfunction "T1_1") (pintype "input"))
      (node (ref "IC411") (pin "15") (pinfunction "T1_15") (pintype "input"))
      (node (ref "IC411") (pin "4") (pinfunction "A_4") (pintype "input"))
      (node (ref "IC411") (pin "8") (pinfunction "VSS_8") (pintype "power_in"))
      (node (ref "IC501") (pin "4") (pinfunction "V-_4") (pintype "power_in"))
      (node (ref "IC502") (pin "2") (pinfunction "GND_2") (pintype "input"))
      (node (ref "IC502") (pin "2@1") (pinfunction "GND_2@1") (pintype "input"))
      (node (ref "IC503") (pin "GND") (pinfunction "GND_GND") (pintype "input"))
      (node (ref "IC504") (pin "2") (pinfunction "GND_2") (pintype "input"))
      (node (ref "IC504") (pin "2@1") (pinfunction "GND_2@1") (pintype "input"))
      (node (ref "IC505") (pin "11") (pinfunction "D_11") (pintype "input"))
      (node (ref "IC505") (pin "8") (pinfunction "VSS_8") (pintype "power_in"))
      (node (ref "IC506") (pin "5") (pinfunction "V-_5") (pintype "passive"))
      (node (ref "IC507") (pin "8") (pinfunction "GND_8") (pintype "power_in"))
      (node (ref "IC508") (pin "10") (pinfunction "-IN_10") (pintype "input"))
      (node (ref "IC508") (pin "11") (pinfunction "+IN_11") (pintype "input"))
      (node (ref "IC508") (pin "12") (pinfunction "GND_12") (pintype "power_in"))
      (node (ref "IC510") (pin "1") (pinfunction "GND_1") (pintype "power_in"))
      (node (ref "IC511") (pin "1") (pinfunction "T1_1") (pintype "input"))
      (node (ref "IC511") (pin "15") (pinfunction "T1_15") (pintype "input"))
      (node (ref "IC511") (pin "4") (pinfunction "A_4") (pintype "input"))
      (node (ref "IC511") (pin "8") (pinfunction "VSS_8") (pintype "power_in"))
      (node (ref "IC601") (pin "4") (pinfunction "V-_4") (pintype "power_in"))
      (node (ref "IC602") (pin "2") (pinfunction "GND_2") (pintype "input"))
      (node (ref "IC602") (pin "2@1") (pinfunction "GND_2@1") (pintype "input"))
      (node (ref "IC603") (pin "GND") (pinfunction "GND_GND") (pintype "input"))
      (node (ref "IC604") (pin "2") (pinfunction "GND_2") (pintype "input"))
      (node (ref "IC604") (pin "2@1") (pinfunction "GND_2@1") (pintype "input"))
      (node (ref "IC605") (pin "11") (pinfunction "D_11") (pintype "input"))
      (node (ref "IC605") (pin "8") (pinfunction "VSS_8") (pintype "power_in"))
      (node (ref "IC606") (pin "5") (pinfunction "V-_5") (pintype "passive"))
      (node (ref "IC607") (pin "8") (pinfunction "GND_8") (pintype "power_in"))
      (node (ref "IC608") (pin "10") (pinfunction "-IN_10") (pintype "input"))
      (node (ref "IC608") (pin "11") (pinfunction "+IN_11") (pintype "input"))
      (node (ref "IC608") (pin "12") (pinfunction "GND_12") (pintype "power_in"))
      (node (ref "IC610") (pin "1") (pinfunction "GND_1") (pintype "power_in"))
      (node (ref "IC611") (pin "1") (pinfunction "T1_1") (pintype "input"))
      (node (ref "IC611") (pin "15") (pinfunction "T1_15") (pintype "input"))
      (node (ref "IC611") (pin "4") (pinfunction "A_4") (pintype "input"))
      (node (ref "IC611") (pin "8") (pinfunction "VSS_8") (pintype "power_in"))
      (node (ref "IC701") (pin "4") (pinfunction "V-_4") (pintype "power_in"))
      (node (ref "IC702") (pin "2") (pinfunction "GND_2") (pintype "input"))
      (node (ref "IC702") (pin "2@1") (pinfunction "GND_2@1") (pintype "input"))
      (node (ref "IC703") (pin "GND") (pinfunction "GND_GND") (pintype "input"))
      (node (ref "IC704") (pin "2") (pinfunction "GND_2") (pintype "input"))
      (node (ref "IC704") (pin "2@1") (pinfunction "GND_2@1") (pintype "input"))
      (node (ref "IC705") (pin "11") (pinfunction "D_11") (pintype "input"))
      (node (ref "IC705") (pin "8") (pinfunction "VSS_8") (pintype "power_in"))
      (node (ref "IC706") (pin "5") (pinfunction "V-_5") (pintype "passive"))
      (node (ref "IC707") (pin "8") (pinfunction "GND_8") (pintype "power_in"))
      (node (ref "IC708") (pin "10") (pinfunction "-IN_10") (pintype "input"))
      (node (ref "IC708") (pin "11") (pinfunction "+IN_11") (pintype "input"))
      (node (ref "IC708") (pin "12") (pinfunction "GND_12") (pintype "power_in"))
      (node (ref "IC710") (pin "1") (pinfunction "GND_1") (pintype "power_in"))
      (node (ref "IC711") (pin "1") (pinfunction "T1_1") (pintype "input"))
      (node (ref "IC711") (pin "15") (pinfunction "T1_15") (pintype "input"))
      (node (ref "IC711") (pin "4") (pinfunction "A_4") (pintype "input"))
      (node (ref "IC711") (pin "8") (pinfunction "VSS_8") (pintype "power_in"))
      (node (ref "IC801") (pin "4") (pinfunction "V-_4") (pintype "power_in"))
      (node (ref "IC802") (pin "2") (pinfunction "GND_2") (pintype "input"))
      (node (ref "IC802") (pin "2@1") (pinfunction "GND_2@1") (pintype "input"))
      (node (ref "IC803") (pin "GND") (pinfunction "GND_GND") (pintype "input"))
      (node (ref "IC804") (pin "2") (pinfunction "GND_2") (pintype "input"))
      (node (ref "IC804") (pin "2@1") (pinfunction "GND_2@1") (pintype "input"))
      (node (ref "IC805") (pin "11") (pinfunction "D_11") (pintype "input"))
      (node (ref "IC805") (pin "8") (pinfunction "VSS_8") (pintype "power_in"))
      (node (ref "IC806") (pin "5") (pinfunction "V-_5") (pintype "passive"))
      (node (ref "IC807") (pin "8") (pinfunction "GND_8") (pintype "power_in"))
      (node (ref "IC808") (pin "10") (pinfunction "-IN_10") (pintype "input"))
      (node (ref "IC808") (pin "11") (pinfunction "+IN_11") (pintype "input"))
      (node (ref "IC808") (pin "12") (pinfunction "GND_12") (pintype "power_in"))
      (node (ref "IC810") (pin "1") (pinfunction "GND_1") (pintype "power_in"))
      (node (ref "IC811") (pin "1") (pinfunction "T1_1") (pintype "input"))
      (node (ref "IC811") (pin "15") (pinfunction "T1_15") (pintype "input"))
      (node (ref "IC811") (pin "4") (pinfunction "A_4") (pintype "input"))
      (node (ref "IC811") (pin "8") (pinfunction "VSS_8") (pintype "power_in"))
      (node (ref "IC901") (pin "4") (pinfunction "V-_4") (pintype "power_in"))
      (node (ref "IC902") (pin "2") (pinfunction "GND_2") (pintype "input"))
      (node (ref "IC902") (pin "2@1") (pinfunction "GND_2@1") (pintype "input"))
      (node (ref "IC903") (pin "GND") (pinfunction "GND_GND") (pintype "input"))
      (node (ref "IC904") (pin "2") (pinfunction "GND_2") (pintype "input"))
      (node (ref "IC904") (pin "2@1") (pinfunction "GND_2@1") (pintype "input"))
      (node (ref "IC905") (pin "11") (pinfunction "D_11") (pintype "input"))
      (node (ref "IC905") (pin "8") (pinfunction "VSS_8") (pintype "power_in"))
      (node (ref "IC906") (pin "5") (pinfunction "V-_5") (pintype "passive"))
      (node (ref "IC907") (pin "8") (pinfunction "GND_8") (pintype "power_in"))
      (node (ref "IC908") (pin "10") (pinfunction "-IN_10") (pintype "input"))
      (node (ref "IC908") (pin "11") (pinfunction "+IN_11") (pintype "input"))
      (node (ref "IC908") (pin "12") (pinfunction "GND_12") (pintype "power_in"))
      (node (ref "IC910") (pin "1") (pinfunction "GND_1") (pintype "power_in"))
      (node (ref "IC911") (pin "1") (pinfunction "T1_1") (pintype "input"))
      (node (ref "IC911") (pin "15") (pinfunction "T1_15") (pintype "input"))
      (node (ref "IC911") (pin "4") (pinfunction "A_4") (pintype "input"))
      (node (ref "IC911") (pin "8") (pinfunction "VSS_8") (pintype "power_in"))
      (node (ref "Q1003") (pin "3") (pinfunction "E_3") (pintype "passive"))
      (node (ref "Q1006") (pin "2") (pinfunction "S_2") (pintype "passive"))
      (node (ref "Q1007") (pin "2") (pinfunction "S_2") (pintype "passive"))
      (node (ref "Q103") (pin "3") (pinfunction "E_3") (pintype "passive"))
      (node (ref "Q106") (pin "2") (pinfunction "S_2") (pintype "passive"))
      (node (ref "Q107") (pin "2") (pinfunction "S_2") (pintype "passive"))
      (node (ref "Q1103") (pin "3") (pinfunction "E_3") (pintype "passive"))
      (node (ref "Q1106") (pin "2") (pinfunction "S_2") (pintype "passive"))
      (node (ref "Q1107") (pin "2") (pinfunction "S_2") (pintype "passive"))
      (node (ref "Q1203") (pin "3") (pinfunction "E_3") (pintype "passive"))
      (node (ref "Q1206") (pin "2") (pinfunction "S_2") (pintype "passive"))
      (node (ref "Q1207") (pin "2") (pinfunction "S_2") (pintype "passive"))
      (node (ref "Q203") (pin "3") (pinfunction "E_3") (pintype "passive"))
      (node (ref "Q206") (pin "2") (pinfunction "S_2") (pintype "passive"))
      (node (ref "Q207") (pin "2") (pinfunction "S_2") (pintype "passive"))
      (node (ref "Q303") (pin "3") (pinfunction "E_3") (pintype "passive"))
      (node (ref "Q306") (pin "2") (pinfunction "S_2") (pintype "passive"))
      (node (ref "Q307") (pin "2") (pinfunction "S_2") (pintype "passive"))
      (node (ref "Q403") (pin "3") (pinfunction "E_3") (pintype "passive"))
      (node (ref "Q406") (pin "2") (pinfunction "S_2") (pintype "passive"))
      (node (ref "Q407") (pin "2") (pinfunction "S_2") (pintype "passive"))
      (node (ref "Q503") (pin "3") (pinfunction "E_3") (pintype "passive"))
      (node (ref "Q506") (pin "2") (pinfunction "S_2") (pintype "passive"))
      (node (ref "Q507") (pin "2") (pinfunction "S_2") (pintype "passive"))
      (node (ref "Q603") (pin "3") (pinfunction "E_3") (pintype "passive"))
      (node (ref "Q606") (pin "2") (pinfunction "S_2") (pintype "passive"))
      (node (ref "Q607") (pin "2") (pinfunction "S_2") (pintype "passive"))
      (node (ref "Q703") (pin "3") (pinfunction "E_3") (pintype "passive"))
      (node (ref "Q706") (pin "2") (pinfunction "S_2") (pintype "passive"))
      (node (ref "Q707") (pin "2") (pinfunction "S_2") (pintype "passive"))
      (node (ref "Q803") (pin "3") (pinfunction "E_3") (pintype "passive"))
      (node (ref "Q806") (pin "2") (pinfunction "S_2") (pintype "passive"))
      (node (ref "Q807") (pin "2") (pinfunction "S_2") (pintype "passive"))
      (node (ref "Q903") (pin "3") (pinfunction "E_3") (pintype "passive"))
      (node (ref "Q906") (pin "2") (pinfunction "S_2") (pintype "passive"))
      (node (ref "Q907") (pin "2") (pinfunction "S_2") (pintype "passive"))
      (node (ref "R1001") (pin "2") (pinfunction "2_2") (pintype "passive"))
      (node (ref "R1003") (pin "2") (pinfunction "2_2") (pintype "passive"))
      (node (ref "R1004") (pin "2") (pinfunction "2_2") (pintype "passive"))
      (node (ref "R1007") (pin "1") (pinfunction "1_1") (pintype "passive"))
      (node (ref "R101") (pin "2") (pinfunction "2_2") (pintype "passive"))
      (node (ref "R1014") (pin "1") (pinfunction "1_1") (pintype "passive"))
      (node (ref "R1023") (pin "1") (pinfunction "1_1") (pintype "passive"))
      (node (ref "R103") (pin "2") (pinfunction "2_2") (pintype "passive"))
      (node (ref "R1032") (pin "1") (pinfunction "1_1") (pintype "passive"))
      (node (ref "R1036") (pin "1") (pinfunction "1_1") (pintype "passive"))
      (node (ref "R1037") (pin "1") (pinfunction "1_1") (pintype "passive"))
      (node (ref "R1039") (pin "2") (pinfunction "2_2") (pintype "passive"))
      (node (ref "R104") (pin "2") (pinfunction "2_2") (pintype "passive"))
      (node (ref "R1041") (pin "2") (pinfunction "2_2") (pintype "passive"))
      (node (ref "R1043") (pin "2") (pinfunction "2_2") (pintype "passive"))
      (node (ref "R107") (pin "1") (pinfunction "1_1") (pintype "passive"))
      (node (ref "R1101") (pin "2") (pinfunction "2_2") (pintype "passive"))
      (node (ref "R1103") (pin "2") (pinfunction "2_2") (pintype "passive"))
      (node (ref "R1104") (pin "2") (pinfunction "2_2") (pintype "passive"))
      (node (ref "R1107") (pin "1") (pinfunction "1_1") (pintype "passive"))
      (node (ref "R1114") (pin "1") (pinfunction "1_1") (pintype "passive"))
      (node (ref "R1123") (pin "1") (pinfunction "1_1") (pintype "passive"))
      (node (ref "R1132") (pin "1") (pinfunction "1_1") (pintype "passive"))
      (node (ref "R1136") (pin "1") (pinfunction "1_1") (pintype "passive"))
      (node (ref "R1137") (pin "1") (pinfunction "1_1") (pintype "passive"))
      (node (ref "R1139") (pin "2") (pinfunction "2_2") (pintype "passive"))
      (node (ref "R114") (pin "1") (pinfunction "1_1") (pintype "passive"))
      (node (ref "R1141") (pin "2") (pinfunction "2_2") (pintype "passive"))
      (node (ref "R1143") (pin "2") (pinfunction "2_2") (pintype "passive"))
      (node (ref "R1201") (pin "2") (pinfunction "2_2") (pintype "passive"))
      (node (ref "R1203") (pin "2") (pinfunction "2_2") (pintype "passive"))
      (node (ref "R1204") (pin "2") (pinfunction "2_2") (pintype "passive"))
      (node (ref "R1207") (pin "1") (pinfunction "1_1") (pintype "passive"))
      (node (ref "R1214") (pin "1") (pinfunction "1_1") (pintype "passive"))
      (node (ref "R1223") (pin "1") (pinfunction "1_1") (pintype "passive"))
      (node (ref "R123") (pin "1") (pinfunction "1_1") (pintype "passive"))
      (node (ref "R1232") (pin "1") (pinfunction "1_1") (pintype "passive"))
      (node (ref "R1236") (pin "1") (pinfunction "1_1") (pintype "passive"))
      (node (ref "R1237") (pin "1") (pinfunction "1_1") (pintype "passive"))
      (node (ref "R1239") (pin "2") (pinfunction "2_2") (pintype "passive"))
      (node (ref "R1241") (pin "2") (pinfunction "2_2") (pintype "passive"))
      (node (ref "R1243") (pin "2") (pinfunction "2_2") (pintype "passive"))
      (node (ref "R132") (pin "1") (pinfunction "1_1") (pintype "passive"))
      (node (ref "R136") (pin "1") (pinfunction "1_1") (pintype "passive"))
      (node (ref "R137") (pin "1") (pinfunction "1_1") (pintype "passive"))
      (node (ref "R139") (pin "2") (pinfunction "2_2") (pintype "passive"))
      (node (ref "R141") (pin "2") (pinfunction "2_2") (pintype "passive"))
      (node (ref "R143") (pin "2") (pinfunction "2_2") (pintype "passive"))
      (node (ref "R201") (pin "2") (pinfunction "2_2") (pintype "passive"))
      (node (ref "R203") (pin "2") (pinfunction "2_2") (pintype "passive"))
      (node (ref "R204") (pin "2") (pinfunction "2_2") (pintype "passive"))
      (node (ref "R207") (pin "1") (pinfunction "1_1") (pintype "passive"))
      (node (ref "R214") (pin "1") (pinfunction "1_1") (pintype "passive"))
      (node (ref "R223") (pin "1") (pinfunction "1_1") (pintype "passive"))
      (node (ref "R232") (pin "1") (pinfunction "1_1") (pintype "passive"))
      (node (ref "R236") (pin "1") (pinfunction "1_1") (pintype "passive"))
      (node (ref "R237") (pin "1") (pinfunction "1_1") (pintype "passive"))
      (node (ref "R239") (pin "2") (pinfunction "2_2") (pintype "passive"))
      (node (ref "R241") (pin "2") (pinfunction "2_2") (pintype "passive"))
      (node (ref "R243") (pin "2") (pinfunction "2_2") (pintype "passive"))
      (node (ref "R301") (pin "2") (pinfunction "2_2") (pintype "passive"))
      (node (ref "R303") (pin "2") (pinfunction "2_2") (pintype "passive"))
      (node (ref "R304") (pin "2") (pinfunction "2_2") (pintype "passive"))
      (node (ref "R307") (pin "1") (pinfunction "1_1") (pintype "passive"))
      (node (ref "R314") (pin "1") (pinfunction "1_1") (pintype "passive"))
      (node (ref "R323") (pin "1") (pinfunction "1_1") (pintype "passive"))
      (node (ref "R332") (pin "1") (pinfunction "1_1") (pintype "passive"))
      (node (ref "R336") (pin "1") (pinfunction "1_1") (pintype "passive"))
      (node (ref "R337") (pin "1") (pinfunction "1_1") (pintype "passive"))
      (node (ref "R339") (pin "2") (pinfunction "2_2") (pintype "passive"))
      (node (ref "R341") (pin "2") (pinfunction "2_2") (pintype "passive"))
      (node (ref "R343") (pin "2") (pinfunction "2_2") (pintype "passive"))
      (node (ref "R401") (pin "2") (pinfunction "2_2") (pintype "passive"))
      (node (ref "R403") (pin "2") (pinfunction "2_2") (pintype "passive"))
      (node (ref "R404") (pin "2") (pinfunction "2_2") (pintype "passive"))
      (node (ref "R407") (pin "1") (pinfunction "1_1") (pintype "passive"))
      (node (ref "R414") (pin "1") (pinfunction "1_1") (pintype "passive"))
      (node (ref "R423") (pin "1") (pinfunction "1_1") (pintype "passive"))
      (node (ref "R432") (pin "1") (pinfunction "1_1") (pintype "passive"))
      (node (ref "R436") (pin "1") (pinfunction "1_1") (pintype "passive"))
      (node (ref "R437") (pin "1") (pinfunction "1_1") (pintype "passive"))
      (node (ref "R439") (pin "2") (pinfunction "2_2") (pintype "passive"))
      (node (ref "R441") (pin "2") (pinfunction "2_2") (pintype "passive"))
      (node (ref "R443") (pin "2") (pinfunction "2_2") (pintype "passive"))
      (node (ref "R501") (pin "2") (pinfunction "2_2") (pintype "passive"))
      (node (ref "R503") (pin "2") (pinfunction "2_2") (pintype "passive"))
      (node (ref "R504") (pin "2") (pinfunction "2_2") (pintype "passive"))
      (node (ref "R507") (pin "1") (pinfunction "1_1") (pintype "passive"))
      (node (ref "R514") (pin "1") (pinfunction "1_1") (pintype "passive"))
      (node (ref "R523") (pin "1") (pinfunction "1_1") (pintype "passive"))
      (node (ref "R532") (pin "1") (pinfunction "1_1") (pintype "passive"))
      (node (ref "R536") (pin "1") (pinfunction "1_1") (pintype "passive"))
      (node (ref "R537") (pin "1") (pinfunction "1_1") (pintype "passive"))
      (node (ref "R539") (pin "2") (pinfunction "2_2") (pintype "passive"))
      (node (ref "R541") (pin "2") (pinfunction "2_2") (pintype "passive"))
      (node (ref "R543") (pin "2") (pinfunction "2_2") (pintype "passive"))
      (node (ref "R601") (pin "2") (pinfunction "2_2") (pintype "passive"))
      (node (ref "R603") (pin "2") (pinfunction "2_2") (pintype "passive"))
      (node (ref "R604") (pin "2") (pinfunction "2_2") (pintype "passive"))
      (node (ref "R607") (pin "1") (pinfunction "1_1") (pintype "passive"))
      (node (ref "R614") (pin "1") (pinfunction "1_1") (pintype "passive"))
      (node (ref "R623") (pin "1") (pinfunction "1_1") (pintype "passive"))
      (node (ref "R632") (pin "1") (pinfunction "1_1") (pintype "passive"))
      (node (ref "R636") (pin "1") (pinfunction "1_1") (pintype "passive"))
      (node (ref "R637") (pin "1") (pinfunction "1_1") (pintype "passive"))
      (node (ref "R639") (pin "2") (pinfunction "2_2") (pintype "passive"))
      (node (ref "R641") (pin "2") (pinfunction "2_2") (pintype "passive"))
      (node (ref "R643") (pin "2") (pinfunction "2_2") (pintype "passive"))
      (node (ref "R701") (pin "2") (pinfunction "2_2") (pintype "passive"))
      (node (ref "R703") (pin "2") (pinfunction "2_2") (pintype "passive"))
      (node (ref "R704") (pin "2") (pinfunction "2_2") (pintype "passive"))
      (node (ref "R707") (pin "1") (pinfunction "1_1") (pintype "passive"))
      (node (ref "R714") (pin "1") (pinfunction "1_1") (pintype "passive"))
      (node (ref "R723") (pin "1") (pinfunction "1_1") (pintype "passive"))
      (node (ref "R732") (pin "1") (pinfunction "1_1") (pintype "passive"))
      (node (ref "R736") (pin "1") (pinfunction "1_1") (pintype "passive"))
      (node (ref "R737") (pin "1") (pinfunction "1_1") (pintype "passive"))
      (node (ref "R739") (pin "2") (pinfunction "2_2") (pintype "passive"))
      (node (ref "R741") (pin "2") (pinfunction "2_2") (pintype "passive"))
      (node (ref "R743") (pin "2") (pinfunction "2_2") (pintype "passive"))
      (node (ref "R801") (pin "2") (pinfunction "2_2") (pintype "passive"))
      (node (ref "R803") (pin "2") (pinfunction "2_2") (pintype "passive"))
      (node (ref "R804") (pin "2") (pinfunction "2_2") (pintype "passive"))
      (node (ref "R807") (pin "1") (pinfunction "1_1") (pintype "passive"))
      (node (ref "R814") (pin "1") (pinfunction "1_1") (pintype "passive"))
      (node (ref "R823") (pin "1") (pinfunction "1_1") (pintype "passive"))
      (node (ref "R832") (pin "1") (pinfunction "1_1") (pintype "passive"))
      (node (ref "R836") (pin "1") (pinfunction "1_1") (pintype "passive"))
      (node (ref "R837") (pin "1") (pinfunction "1_1") (pintype "passive"))
      (node (ref "R839") (pin "2") (pinfunction "2_2") (pintype "passive"))
      (node (ref "R841") (pin "2") (pinfunction "2_2") (pintype "passive"))
      (node (ref "R843") (pin "2") (pinfunction "2_2") (pintype "passive"))
      (node (ref "R901") (pin "2") (pinfunction "2_2") (pintype "passive"))
      (node (ref "R903") (pin "2") (pinfunction "2_2") (pintype "passive"))
      (node (ref "R904") (pin "2") (pinfunction "2_2") (pintype "passive"))
      (node (ref "R907") (pin "1") (pinfunction "1_1") (pintype "passive"))
      (node (ref "R914") (pin "1") (pinfunction "1_1") (pintype "passive"))
      (node (ref "R923") (pin "1") (pinfunction "1_1") (pintype "passive"))
      (node (ref "R932") (pin "1") (pinfunction "1_1") (pintype "passive"))
      (node (ref "R936") (pin "1") (pinfunction "1_1") (pintype "passive"))
      (node (ref "R937") (pin "1") (pinfunction "1_1") (pintype "passive"))
      (node (ref "R939") (pin "2") (pinfunction "2_2") (pintype "passive"))
      (node (ref "R941") (pin "2") (pinfunction "2_2") (pintype "passive"))
      (node (ref "R943") (pin "2") (pinfunction "2_2") (pintype "passive"))
      (node (ref "X1001") (pin "13") (pinfunction "13_13") (pintype "passive"))
      (node (ref "X1001") (pin "18") (pinfunction "18_18") (pintype "passive"))
      (node (ref "X1001") (pin "23") (pinfunction "23_23") (pintype "passive"))
      (node (ref "X1002") (pin "1") (pinfunction "S_1") (pintype "passive"))
      (node (ref "X1003") (pin "5") (pinfunction "S_5") (pintype "passive"))
      (node (ref "X101") (pin "13") (pinfunction "13_13") (pintype "passive"))
      (node (ref "X101") (pin "18") (pinfunction "18_18") (pintype "passive"))
      (node (ref "X101") (pin "23") (pinfunction "23_23") (pintype "passive"))
      (node (ref "X102") (pin "1") (pinfunction "S_1") (pintype "passive"))
      (node (ref "X103") (pin "5") (pinfunction "S_5") (pintype "passive"))
      (node (ref "X1101") (pin "13") (pinfunction "13_13") (pintype "passive"))
      (node (ref "X1101") (pin "18") (pinfunction "18_18") (pintype "passive"))
      (node (ref "X1101") (pin "23") (pinfunction "23_23") (pintype "passive"))
      (node (ref "X1102") (pin "1") (pinfunction "S_1") (pintype "passive"))
      (node (ref "X1103") (pin "5") (pinfunction "S_5") (pintype "passive"))
      (node (ref "X1201") (pin "13") (pinfunction "13_13") (pintype "passive"))
      (node (ref "X1201") (pin "18") (pinfunction "18_18") (pintype "passive"))
      (node (ref "X1201") (pin "23") (pinfunction "23_23") (pintype "passive"))
      (node (ref "X1202") (pin "1") (pinfunction "S_1") (pintype "passive"))
      (node (ref "X1203") (pin "5") (pinfunction "S_5") (pintype "passive"))
      (node (ref "X201") (pin "13") (pinfunction "13_13") (pintype "passive"))
      (node (ref "X201") (pin "18") (pinfunction "18_18") (pintype "passive"))
      (node (ref "X201") (pin "23") (pinfunction "23_23") (pintype "passive"))
      (node (ref "X202") (pin "1") (pinfunction "S_1") (pintype "passive"))
      (node (ref "X203") (pin "5") (pinfunction "S_5") (pintype "passive"))
      (node (ref "X301") (pin "13") (pinfunction "13_13") (pintype "passive"))
      (node (ref "X301") (pin "18") (pinfunction "18_18") (pintype "passive"))
      (node (ref "X301") (pin "23") (pinfunction "23_23") (pintype "passive"))
      (node (ref "X302") (pin "1") (pinfunction "S_1") (pintype "passive"))
      (node (ref "X303") (pin "5") (pinfunction "S_5") (pintype "passive"))
      (node (ref "X401") (pin "13") (pinfunction "13_13") (pintype "passive"))
      (node (ref "X401") (pin "18") (pinfunction "18_18") (pintype "passive"))
      (node (ref "X401") (pin "23") (pinfunction "23_23") (pintype "passive"))
      (node (ref "X402") (pin "1") (pinfunction "S_1") (pintype "passive"))
      (node (ref "X403") (pin "5") (pinfunction "S_5") (pintype "passive"))
      (node (ref "X501") (pin "13") (pinfunction "13_13") (pintype "passive"))
      (node (ref "X501") (pin "18") (pinfunction "18_18") (pintype "passive"))
      (node (ref "X501") (pin "23") (pinfunction "23_23") (pintype "passive"))
      (node (ref "X502") (pin "1") (pinfunction "S_1") (pintype "passive"))
      (node (ref "X503") (pin "5") (pinfunction "S_5") (pintype "passive"))
      (node (ref "X601") (pin "13") (pinfunction "13_13") (pintype "passive"))
      (node (ref "X601") (pin "18") (pinfunction "18_18") (pintype "passive"))
      (node (ref "X601") (pin "23") (pinfunction "23_23") (pintype "passive"))
      (node (ref "X602") (pin "1") (pinfunction "S_1") (pintype "passive"))
      (node (ref "X603") (pin "5") (pinfunction "S_5") (pintype "passive"))
      (node (ref "X701") (pin "13") (pinfunction "13_13") (pintype "passive"))
      (node (ref "X701") (pin "18") (pinfunction "18_18") (pintype "passive"))
      (node (ref "X701") (pin "23") (pinfunction "23_23") (pintype "passive"))
      (node (ref "X702") (pin "1") (pinfunction "S_1") (pintype "passive"))
      (node (ref "X703") (pin "5") (pinfunction "S_5") (pintype "passive"))
      (node (ref "X801") (pin "13") (pinfunction "13_13") (pintype "passive"))
      (node (ref "X801") (pin "18") (pinfunction "18_18") (pintype "passive"))
      (node (ref "X801") (pin "23") (pinfunction "23_23") (pintype "passive"))
      (node (ref "X802") (pin "1") (pinfunction "S_1") (pintype "passive"))
      (node (ref "X803") (pin "5") (pinfunction "S_5") (pintype "passive"))
      (node (ref "X901") (pin "13") (pinfunction "13_13") (pintype "passive"))
      (node (ref "X901") (pin "18") (pinfunction "18_18") (pintype "passive"))
      (node (ref "X901") (pin "23") (pinfunction "23_23") (pintype "passive"))
      (node (ref "X902") (pin "1") (pinfunction "S_1") (pintype "passive"))
      (node (ref "X903") (pin "5") (pinfunction "S_5") (pintype "passive"))
    )
    (net (code "4") (name "Net-(1A-KL)") (class "Default")
      (node (ref "1") (pin "1") (pinfunction "KL_1") (pintype "passive"))
      (node (ref "TP1") (pin "TP") (pinfunction "PP_TP") (pintype "input"))
      (node (ref "X101") (pin "1") (pinfunction "1_1") (pintype "passive"))
    )
    (net (code "5") (name "Net-(1B-KL)") (class "Default")
      (node (ref "1") (pin "10") (pinfunction "KL_10") (pintype "passive"))
      (node (ref "D102") (pin "2") (pinfunction "-_2") (pintype "passive"))
      (node (ref "D103") (pin "2") (pinfunction "-_2") (pintype "passive"))
      (node (ref "JP104") (pin "1") (pinfunction "1_1") (pintype "passive"))
      (node (ref "SJ101") (pin "1") (pinfunction "1_1") (pintype "passive"))
      (node (ref "TP10") (pin "TP") (pinfunction "PP_TP") (pintype "input"))
    )
    (net (code "6") (name "Net-(1C-KL)") (class "Default")
      (node (ref "1") (pin "11") (pinfunction "KL_11") (pintype "passive"))
      (node (ref "D103") (pin "1") (pinfunction "+_1") (pintype "passive"))
      (node (ref "TP11") (pin "TP") (pinfunction "PP_TP") (pintype "input"))
      (node (ref "X101") (pin "19") (pinfunction "19_19") (pintype "passive"))
    )
    (net (code "7") (name "Net-(1E-KL)") (class "Default")
      (node (ref "1") (pin "2") (pinfunction "KL_2") (pintype "passive"))
      (node (ref "Q101") (pin "2") (pinfunction "C_2") (pintype "passive"))
      (node (ref "TP2") (pin "TP") (pinfunction "PP_TP") (pintype "input"))
    )
    (net (code "8") (name "Net-(1F-KL)") (class "Default")
      (node (ref "1") (pin "3") (pinfunction "KL_3") (pintype "passive"))
      (node (ref "IC107") (pin "11") (pinfunction "O6_11") (pintype "open_collector"))
      (node (ref "TP3") (pin "TP") (pinfunction "PP_TP") (pintype "input"))
    )
    (net (code "9") (name "Net-(1G-KL)") (class "Default")
      (node (ref "1") (pin "4") (pinfunction "KL_4") (pintype "passive"))
      (node (ref "IC107") (pin "10") (pinfunction "O7_10") (pintype "open_collector"))
      (node (ref "TP4") (pin "TP") (pinfunction "PP_TP") (pintype "input"))
    )
    (net (code "10") (name "Net-(1H-KL)") (class "Default")
      (node (ref "1") (pin "5") (pinfunction "KL_5") (pintype "passive"))
      (node (ref "IC107") (pin "12") (pinfunction "O5_12") (pintype "open_collector"))
      (node (ref "TP5") (pin "TP") (pinfunction "PP_TP") (pintype "input"))
    )
    (net (code "11") (name "Net-(1I-KL)") (class "Default")
      (node (ref "1") (pin "6") (pinfunction "KL_6") (pintype "passive"))
      (node (ref "IC107") (pin "13") (pinfunction "O4_13") (pintype "open_collector"))
      (node (ref "TP6") (pin "TP") (pinfunction "PP_TP") (pintype "input"))
    )
    (net (code "12") (name "Net-(1J-KL)") (class "Default")
      (node (ref "1") (pin "7") (pinfunction "KL_7") (pintype "passive"))
      (node (ref "IC107") (pin "14") (pinfunction "O3_14") (pintype "open_collector"))
      (node (ref "TP7") (pin "TP") (pinfunction "PP_TP") (pintype "input"))
    )
    (net (code "13") (name "Net-(1K-KL)") (class "Default")
      (node (ref "1") (pin "8") (pinfunction "KL_8") (pintype "passive"))
      (node (ref "Q106") (pin "3") (pinfunction "D_3") (pintype "passive"))
      (node (ref "TP8") (pin "TP") (pinfunction "PP_TP") (pintype "input"))
    )
    (net (code "14") (name "Net-(1L-KL)") (class "Default")
      (node (ref "1") (pin "9") (pinfunction "KL_9") (pintype "passive"))
      (node (ref "D102") (pin "1") (pinfunction "+_1") (pintype "passive"))
      (node (ref "TP9") (pin "TP") (pinfunction "PP_TP") (pintype "input"))
      (node (ref "X101") (pin "17") (pinfunction "17_17") (pintype "passive"))
    )
    (net (code "15") (name "Net-(2B-KL)") (class "Default")
      (node (ref "2") (pin "10") (pinfunction "KL_10") (pintype "passive"))
      (node (ref "TP25") (pin "TP") (pinfunction "PP_TP") (pintype "input"))
      (node (ref "X101") (pin "15") (pinfunction "15_15") (pintype "passive"))
    )
    (net (code "16") (name "Net-(2C-KL)") (class "Default")
      (node (ref "2") (pin "11") (pinfunction "KL_11") (pintype "passive"))
      (node (ref "IC107") (pin "16") (pinfunction "O1_16") (pintype "open_collector"))
      (node (ref "R118") (pin "2") (pinfunction "2_2") (pintype "passive"))
      (node (ref "R119") (pin "1") (pinfunction "1_1") (pintype "passive"))
      (node (ref "TP26") (pin "TP") (pinfunction "PP_TP") (pintype "input"))
    )
    (net (code "17") (name "Net-(2D-KL)") (class "Default")
      (node (ref "2") (pin "12") (pinfunction "KL_12") (pintype "passive"))
      (node (ref "R146") (pin "1") (pinfunction "1_1") (pintype "passive"))
      (node (ref "TP13") (pin "TP") (pinfunction "PP_TP") (pintype "input"))
    )
    (net (code "18") (name "Net-(2E-KL)") (class "Default")
      (node (ref "2") (pin "2") (pinfunction "KL_2") (pintype "passive"))
      (node (ref "D109") (pin "2") (pinfunction "-_2") (pintype "passive"))
      (node (ref "LED102") (pin "K") (pinfunction "C_K") (pintype "passive"))
      (node (ref "TP16") (pin "TP") (pinfunction "PP_TP") (pintype "input"))
      (node (ref "X101") (pin "12") (pinfunction "12_12") (pintype "passive"))
    )
    (net (code "19") (name "Net-(2F-KL)") (class "Default")
      (node (ref "2") (pin "3") (pinfunction "KL_3") (pintype "passive"))
      (node (ref "D108") (pin "2") (pinfunction "-_2") (pintype "passive"))
      (node (ref "LED103") (pin "K") (pinfunction "C_K") (pintype "passive"))
      (node (ref "TP17") (pin "TP") (pinfunction "PP_TP") (pintype "input"))
      (node (ref "X101") (pin "11") (pinfunction "11_11") (pintype "passive"))
    )
    (net (code "20") (name "Net-(2G-KL)") (class "Default")
      (node (ref "2") (pin "4") (pinfunction "KL_4") (pintype "passive"))
      (node (ref "D107") (pin "2") (pinfunction "-_2") (pintype "passive"))
      (node (ref "LED104") (pin "K") (pinfunction "C_K") (pintype "passive"))
      (node (ref "TP18") (pin "TP") (pinfunction "PP_TP") (pintype "input"))
      (node (ref "X101") (pin "10") (pinfunction "10_10") (pintype "passive"))
    )
    (net (code "21") (name "Net-(2H-KL)") (class "Default")
      (node (ref "2") (pin "5") (pinfunction "KL_5") (pintype "passive"))
      (node (ref "D106") (pin "2") (pinfunction "-_2") (pintype "passive"))
      (node (ref "LED105") (pin "K") (pinfunction "C_K") (pintype "passive"))
      (node (ref "TP19") (pin "TP") (pinfunction "PP_TP") (pintype "input"))
      (node (ref "X101") (pin "9") (pinfunction "9_9") (pintype "passive"))
    )
    (net (code "22") (name "Net-(2I-KL)") (class "Default")
      (node (ref "2") (pin "6") (pinfunction "KL_6") (pintype "passive"))
      (node (ref "JP105") (pin "2") (pinfunction "2_2") (pintype "passive"))
      (node (ref "TP21") (pin "TP") (pinfunction "PP_TP") (pintype "input"))
    )
    (net (code "23") (name "Net-(2J-KL)") (class "Default")
      (node (ref "2") (pin "7") (pinfunction "KL_7") (pintype "passive"))
      (node (ref "LED101") (pin "A") (pinfunction "A_A") (pintype "passive"))
      (node (ref "TP22") (pin "TP") (pinfunction "PP_TP") (pintype "input"))
      (node (ref "X101") (pin "8") (pinfunction "8_8") (pintype "passive"))
    )
    (net (code "24") (name "Net-(2K-KL)") (class "Default")
      (node (ref "2") (pin "8") (pinfunction "KL_8") (pintype "passive"))
      (node (ref "D110") (pin "2") (pinfunction "-_2") (pintype "passive"))
      (node (ref "LED106") (pin "K") (pinfunction "C_K") (pintype "passive"))
      (node (ref "TP23") (pin "TP") (pinfunction "PP_TP") (pintype "input"))
      (node (ref "X101") (pin "14") (pinfunction "14_14") (pintype "passive"))
    )
    (net (code "25") (name "Net-(2L-KL)") (class "Default")
      (node (ref "2") (pin "9") (pinfunction "KL_9") (pintype "passive"))
      (node (ref "D107") (pin "1") (pinfunction "+_1") (pintype "passive"))
      (node (ref "D108") (pin "1") (pinfunction "+_1") (pintype "passive"))
      (node (ref "JP102") (pin "1") (pinfunction "1_1") (pintype "passive"))
      (node (ref "JP103") (pin "2") (pinfunction "2_2") (pintype "passive"))
      (node (ref "TP24") (pin "TP") (pinfunction "PP_TP") (pintype "input"))
    )
    (net (code "26") (name "Net-(3A-KL)") (class "Default")
      (node (ref "3") (pin "1") (pinfunction "KL_1") (pintype "passive"))
      (node (ref "TP14") (pin "TP") (pinfunction "PP_TP") (pintype "input"))
      (node (ref "X201") (pin "1") (pinfunction "1_1") (pintype "passive"))
    )
    (net (code "27") (name "Net-(3B-KL)") (class "Default")
      (node (ref "3") (pin "10") (pinfunction "KL_10") (pintype "passive"))
      (node (ref "D202") (pin "2") (pinfunction "-_2") (pintype "passive"))
      (node (ref "D203") (pin "2") (pinfunction "-_2") (pintype "passive"))
      (node (ref "JP204") (pin "1") (pinfunction "1_1") (pintype "passive"))
      (node (ref "SJ201") (pin "1") (pinfunction "1_1") (pintype "passive"))
      (node (ref "TP33") (pin "TP") (pinfunction "PP_TP") (pintype "input"))
    )
    (net (code "28") (name "Net-(3C-KL)") (class "Default")
      (node (ref "3") (pin "11") (pinfunction "KL_11") (pintype "passive"))
      (node (ref "D203") (pin "1") (pinfunction "+_1") (pintype "passive"))
      (node (ref "TP34") (pin "TP") (pinfunction "PP_TP") (pintype "input"))
      (node (ref "X201") (pin "19") (pinfunction "19_19") (pintype "passive"))
    )
    (net (code "29") (name "Net-(3E-KL)") (class "Default")
      (node (ref "3") (pin "2") (pinfunction "KL_2") (pintype "passive"))
      (node (ref "Q201") (pin "2") (pinfunction "C_2") (pintype "passive"))
      (node (ref "TP15") (pin "TP") (pinfunction "PP_TP") (pintype "input"))
    )
    (net (code "30") (name "Net-(3F-KL)") (class "Default")
      (node (ref "3") (pin "3") (pinfunction "KL_3") (pintype "passive"))
      (node (ref "IC207") (pin "11") (pinfunction "O6_11") (pintype "open_collector"))
      (node (ref "TP20") (pin "TP") (pinfunction "PP_TP") (pintype "input"))
    )
    (net (code "31") (name "Net-(3G-KL)") (class "Default")
      (node (ref "3") (pin "4") (pinfunction "KL_4") (pintype "passive"))
      (node (ref "IC207") (pin "10") (pinfunction "O7_10") (pintype "open_collector"))
      (node (ref "TP27") (pin "TP") (pinfunction "PP_TP") (pintype "input"))
    )
    (net (code "32") (name "Net-(3H-KL)") (class "Default")
      (node (ref "3") (pin "5") (pinfunction "KL_5") (pintype "passive"))
      (node (ref "IC207") (pin "12") (pinfunction "O5_12") (pintype "open_collector"))
      (node (ref "TP28") (pin "TP") (pinfunction "PP_TP") (pintype "input"))
    )
    (net (code "33") (name "Net-(3I-KL)") (class "Default")
      (node (ref "3") (pin "6") (pinfunction "KL_6") (pintype "passive"))
      (node (ref "IC207") (pin "13") (pinfunction "O4_13") (pintype "open_collector"))
      (node (ref "TP29") (pin "TP") (pinfunction "PP_TP") (pintype "input"))
    )
    (net (code "34") (name "Net-(3J-KL)") (class "Default")
      (node (ref "3") (pin "7") (pinfunction "KL_7") (pintype "passive"))
      (node (ref "IC207") (pin "14") (pinfunction "O3_14") (pintype "open_collector"))
      (node (ref "TP30") (pin "TP") (pinfunction "PP_TP") (pintype "input"))
    )
    (net (code "35") (name "Net-(3K-KL)") (class "Default")
      (node (ref "3") (pin "8") (pinfunction "KL_8") (pintype "passive"))
      (node (ref "Q206") (pin "3") (pinfunction "D_3") (pintype "passive"))
      (node (ref "TP31") (pin "TP") (pinfunction "PP_TP") (pintype "input"))
    )
    (net (code "36") (name "Net-(3L-KL)") (class "Default")
      (node (ref "3") (pin "9") (pinfunction "KL_9") (pintype "passive"))
      (node (ref "D202") (pin "1") (pinfunction "+_1") (pintype "passive"))
      (node (ref "TP32") (pin "TP") (pinfunction "PP_TP") (pintype "input"))
      (node (ref "X201") (pin "17") (pinfunction "17_17") (pintype "passive"))
    )
    (net (code "37") (name "Net-(4B-KL)") (class "Default")
      (node (ref "4") (pin "10") (pinfunction "KL_10") (pintype "passive"))
      (node (ref "TP43") (pin "TP") (pinfunction "PP_TP") (pintype "input"))
      (node (ref "X201") (pin "15") (pinfunction "15_15") (pintype "passive"))
    )
    (net (code "38") (name "Net-(4C-KL)") (class "Default")
      (node (ref "4") (pin "11") (pinfunction "KL_11") (pintype "passive"))
      (node (ref "IC207") (pin "16") (pinfunction "O1_16") (pintype "open_collector"))
      (node (ref "R218") (pin "2") (pinfunction "2_2") (pintype "passive"))
      (node (ref "R219") (pin "1") (pinfunction "1_1") (pintype "passive"))
      (node (ref "TP44") (pin "TP") (pinfunction "PP_TP") (pintype "input"))
    )
    (net (code "39") (name "Net-(4D-KL)") (class "Default")
      (node (ref "4") (pin "12") (pinfunction "KL_12") (pintype "passive"))
      (node (ref "R246") (pin "1") (pinfunction "1_1") (pintype "passive"))
      (node (ref "TP46") (pin "TP") (pinfunction "PP_TP") (pintype "input"))
    )
    (net (code "40") (name "Net-(4E-KL)") (class "Default")
      (node (ref "4") (pin "2") (pinfunction "KL_2") (pintype "passive"))
      (node (ref "D209") (pin "2") (pinfunction "-_2") (pintype "passive"))
      (node (ref "LED202") (pin "K") (pinfunction "C_K") (pintype "passive"))
      (node (ref "TP35") (pin "TP") (pinfunction "PP_TP") (pintype "input"))
      (node (ref "X201") (pin "12") (pinfunction "12_12") (pintype "passive"))
    )
    (net (code "41") (name "Net-(4F-KL)") (class "Default")
      (node (ref "4") (pin "3") (pinfunction "KL_3") (pintype "passive"))
      (node (ref "D208") (pin "2") (pinfunction "-_2") (pintype "passive"))
      (node (ref "LED203") (pin "K") (pinfunction "C_K") (pintype "passive"))
      (node (ref "TP36") (pin "TP") (pinfunction "PP_TP") (pintype "input"))
      (node (ref "X201") (pin "11") (pinfunction "11_11") (pintype "passive"))
    )
    (net (code "42") (name "Net-(4G-KL)") (class "Default")
      (node (ref "4") (pin "4") (pinfunction "KL_4") (pintype "passive"))
      (node (ref "D207") (pin "2") (pinfunction "-_2") (pintype "passive"))
      (node (ref "LED204") (pin "K") (pinfunction "C_K") (pintype "passive"))
      (node (ref "TP37") (pin "TP") (pinfunction "PP_TP") (pintype "input"))
      (node (ref "X201") (pin "10") (pinfunction "10_10") (pintype "passive"))
    )
    (net (code "43") (name "Net-(4H-KL)") (class "Default")
      (node (ref "4") (pin "5") (pinfunction "KL_5") (pintype "passive"))
      (node (ref "D206") (pin "2") (pinfunction "-_2") (pintype "passive"))
      (node (ref "LED205") (pin "K") (pinfunction "C_K") (pintype "passive"))
      (node (ref "TP38") (pin "TP") (pinfunction "PP_TP") (pintype "input"))
      (node (ref "X201") (pin "9") (pinfunction "9_9") (pintype "passive"))
    )
    (net (code "44") (name "Net-(4I-KL)") (class "Default")
      (node (ref "4") (pin "6") (pinfunction "KL_6") (pintype "passive"))
      (node (ref "JP205") (pin "2") (pinfunction "2_2") (pintype "passive"))
      (node (ref "TP39") (pin "TP") (pinfunction "PP_TP") (pintype "input"))
    )
    (net (code "45") (name "Net-(4J-KL)") (class "Default")
      (node (ref "4") (pin "7") (pinfunction "KL_7") (pintype "passive"))
      (node (ref "LED201") (pin "A") (pinfunction "A_A") (pintype "passive"))
      (node (ref "TP40") (pin "TP") (pinfunction "PP_TP") (pintype "input"))
      (node (ref "X201") (pin "8") (pinfunction "8_8") (pintype "passive"))
    )
    (net (code "46") (name "Net-(4K-KL)") (class "Default")
      (node (ref "4") (pin "8") (pinfunction "KL_8") (pintype "passive"))
      (node (ref "D210") (pin "2") (pinfunction "-_2") (pintype "passive"))
      (node (ref "LED206") (pin "K") (pinfunction "C_K") (pintype "passive"))
      (node (ref "TP41") (pin "TP") (pinfunction "PP_TP") (pintype "input"))
      (node (ref "X201") (pin "14") (pinfunction "14_14") (pintype "passive"))
    )
    (net (code "47") (name "Net-(4L-KL)") (class "Default")
      (node (ref "4") (pin "9") (pinfunction "KL_9") (pintype "passive"))
      (node (ref "D207") (pin "1") (pinfunction "+_1") (pintype "passive"))
      (node (ref "D208") (pin "1") (pinfunction "+_1") (pintype "passive"))
      (node (ref "JP202") (pin "1") (pinfunction "1_1") (pintype "passive"))
      (node (ref "JP203") (pin "2") (pinfunction "2_2") (pintype "passive"))
      (node (ref "TP42") (pin "TP") (pinfunction "PP_TP") (pintype "input"))
    )
    (net (code "48") (name "Net-(5A-KL)") (class "Default")
      (node (ref "5") (pin "1") (pinfunction "KL_1") (pintype "passive"))
      (node (ref "TP47") (pin "TP") (pinfunction "PP_TP") (pintype "input"))
      (node (ref "X301") (pin "1") (pinfunction "1_1") (pintype "passive"))
    )
    (net (code "49") (name "Net-(5B-KL)") (class "Default")
      (node (ref "5") (pin "10") (pinfunction "KL_10") (pintype "passive"))
      (node (ref "D302") (pin "2") (pinfunction "-_2") (pintype "passive"))
      (node (ref "D303") (pin "2") (pinfunction "-_2") (pintype "passive"))
      (node (ref "JP304") (pin "1") (pinfunction "1_1") (pintype "passive"))
      (node (ref "SJ301") (pin "1") (pinfunction "1_1") (pintype "passive"))
      (node (ref "TP56") (pin "TP") (pinfunction "PP_TP") (pintype "input"))
    )
    (net (code "50") (name "Net-(5C-KL)") (class "Default")
      (node (ref "5") (pin "11") (pinfunction "KL_11") (pintype "passive"))
      (node (ref "D303") (pin "1") (pinfunction "+_1") (pintype "passive"))
      (node (ref "TP57") (pin "TP") (pinfunction "PP_TP") (pintype "input"))
      (node (ref "X301") (pin "19") (pinfunction "19_19") (pintype "passive"))
    )
    (net (code "51") (name "Net-(5E-KL)") (class "Default")
      (node (ref "5") (pin "2") (pinfunction "KL_2") (pintype "passive"))
      (node (ref "Q301") (pin "2") (pinfunction "C_2") (pintype "passive"))
      (node (ref "TP48") (pin "TP") (pinfunction "PP_TP") (pintype "input"))
    )
    (net (code "52") (name "Net-(5F-KL)") (class "Default")
      (node (ref "5") (pin "3") (pinfunction "KL_3") (pintype "passive"))
      (node (ref "IC307") (pin "11") (pinfunction "O6_11") (pintype "open_collector"))
      (node (ref "TP49") (pin "TP") (pinfunction "PP_TP") (pintype "input"))
    )
    (net (code "53") (name "Net-(5G-KL)") (class "Default")
      (node (ref "5") (pin "4") (pinfunction "KL_4") (pintype "passive"))
      (node (ref "IC307") (pin "10") (pinfunction "O7_10") (pintype "open_collector"))
      (node (ref "TP50") (pin "TP") (pinfunction "PP_TP") (pintype "input"))
    )
    (net (code "54") (name "Net-(5H-KL)") (class "Default")
      (node (ref "5") (pin "5") (pinfunction "KL_5") (pintype "passive"))
      (node (ref "IC307") (pin "12") (pinfunction "O5_12") (pintype "open_collector"))
      (node (ref "TP51") (pin "TP") (pinfunction "PP_TP") (pintype "input"))
    )
    (net (code "55") (name "Net-(5I-KL)") (class "Default")
      (node (ref "5") (pin "6") (pinfunction "KL_6") (pintype "passive"))
      (node (ref "IC307") (pin "13") (pinfunction "O4_13") (pintype "open_collector"))
      (node (ref "TP52") (pin "TP") (pinfunction "PP_TP") (pintype "input"))
    )
    (net (code "56") (name "Net-(5J-KL)") (class "Default")
      (node (ref "5") (pin "7") (pinfunction "KL_7") (pintype "passive"))
      (node (ref "IC307") (pin "14") (pinfunction "O3_14") (pintype "open_collector"))
      (node (ref "TP53") (pin "TP") (pinfunction "PP_TP") (pintype "input"))
    )
    (net (code "57") (name "Net-(5K-KL)") (class "Default")
      (node (ref "5") (pin "8") (pinfunction "KL_8") (pintype "passive"))
      (node (ref "Q306") (pin "3") (pinfunction "D_3") (pintype "passive"))
      (node (ref "TP54") (pin "TP") (pinfunction "PP_TP") (pintype "input"))
    )
    (net (code "58") (name "Net-(5L-KL)") (class "Default")
      (node (ref "5") (pin "9") (pinfunction "KL_9") (pintype "passive"))
      (node (ref "D302") (pin "1") (pinfunction "+_1") (pintype "passive"))
      (node (ref "TP55") (pin "TP") (pinfunction "PP_TP") (pintype "input"))
      (node (ref "X301") (pin "17") (pinfunction "17_17") (pintype "passive"))
    )
    (net (code "59") (name "Net-(6B-KL)") (class "Default")
      (node (ref "6") (pin "10") (pinfunction "KL_10") (pintype "passive"))
      (node (ref "TP66") (pin "TP") (pinfunction "PP_TP") (pintype "input"))
      (node (ref "X301") (pin "15") (pinfunction "15_15") (pintype "passive"))
    )
    (net (code "60") (name "Net-(6C-KL)") (class "Default")
      (node (ref "6") (pin "11") (pinfunction "KL_11") (pintype "passive"))
      (node (ref "IC307") (pin "16") (pinfunction "O1_16") (pintype "open_collector"))
      (node (ref "R318") (pin "2") (pinfunction "2_2") (pintype "passive"))
      (node (ref "R319") (pin "1") (pinfunction "1_1") (pintype "passive"))
      (node (ref "TP67") (pin "TP") (pinfunction "PP_TP") (pintype "input"))
    )
    (net (code "61") (name "Net-(6D-KL)") (class "Default")
      (node (ref "6") (pin "12") (pinfunction "KL_12") (pintype "passive"))
      (node (ref "R346") (pin "1") (pinfunction "1_1") (pintype "passive"))
      (node (ref "TP69") (pin "TP") (pinfunction "PP_TP") (pintype "input"))
    )
    (net (code "62") (name "Net-(6E-KL)") (class "Default")
      (node (ref "6") (pin "2") (pinfunction "KL_2") (pintype "passive"))
      (node (ref "D309") (pin "2") (pinfunction "-_2") (pintype "passive"))
      (node (ref "LED302") (pin "K") (pinfunction "C_K") (pintype "passive"))
      (node (ref "TP58") (pin "TP") (pinfunction "PP_TP") (pintype "input"))
      (node (ref "X301") (pin "12") (pinfunction "12_12") (pintype "passive"))
    )
    (net (code "63") (name "Net-(6F-KL)") (class "Default")
      (node (ref "6") (pin "3") (pinfunction "KL_3") (pintype "passive"))
      (node (ref "D308") (pin "2") (pinfunction "-_2") (pintype "passive"))
      (node (ref "LED303") (pin "K") (pinfunction "C_K") (pintype "passive"))
      (node (ref "TP59") (pin "TP") (pinfunction "PP_TP") (pintype "input"))
      (node (ref "X301") (pin "11") (pinfunction "11_11") (pintype "passive"))
    )
    (net (code "64") (name "Net-(6G-KL)") (class "Default")
      (node (ref "6") (pin "4") (pinfunction "KL_4") (pintype "passive"))
      (node (ref "D307") (pin "2") (pinfunction "-_2") (pintype "passive"))
      (node (ref "LED304") (pin "K") (pinfunction "C_K") (pintype "passive"))
      (node (ref "TP60") (pin "TP") (pinfunction "PP_TP") (pintype "input"))
      (node (ref "X301") (pin "10") (pinfunction "10_10") (pintype "passive"))
    )
    (net (code "65") (name "Net-(6H-KL)") (class "Default")
      (node (ref "6") (pin "5") (pinfunction "KL_5") (pintype "passive"))
      (node (ref "D306") (pin "2") (pinfunction "-_2") (pintype "passive"))
      (node (ref "LED305") (pin "K") (pinfunction "C_K") (pintype "passive"))
      (node (ref "TP61") (pin "TP") (pinfunction "PP_TP") (pintype "input"))
      (node (ref "X301") (pin "9") (pinfunction "9_9") (pintype "passive"))
    )
    (net (code "66") (name "Net-(6I-KL)") (class "Default")
      (node (ref "6") (pin "6") (pinfunction "KL_6") (pintype "passive"))
      (node (ref "JP305") (pin "2") (pinfunction "2_2") (pintype "passive"))
      (node (ref "TP62") (pin "TP") (pinfunction "PP_TP") (pintype "input"))
    )
    (net (code "67") (name "Net-(6J-KL)") (class "Default")
      (node (ref "6") (pin "7") (pinfunction "KL_7") (pintype "passive"))
      (node (ref "LED301") (pin "A") (pinfunction "A_A") (pintype "passive"))
      (node (ref "TP63") (pin "TP") (pinfunction "PP_TP") (pintype "input"))
      (node (ref "X301") (pin "8") (pinfunction "8_8") (pintype "passive"))
    )
    (net (code "68") (name "Net-(6K-KL)") (class "Default")
      (node (ref "6") (pin "8") (pinfunction "KL_8") (pintype "passive"))
      (node (ref "D310") (pin "2") (pinfunction "-_2") (pintype "passive"))
      (node (ref "LED306") (pin "K") (pinfunction "C_K") (pintype "passive"))
      (node (ref "TP64") (pin "TP") (pinfunction "PP_TP") (pintype "input"))
      (node (ref "X301") (pin "14") (pinfunction "14_14") (pintype "passive"))
    )
    (net (code "69") (name "Net-(6L-KL)") (class "Default")
      (node (ref "6") (pin "9") (pinfunction "KL_9") (pintype "passive"))
      (node (ref "D307") (pin "1") (pinfunction "+_1") (pintype "passive"))
      (node (ref "D308") (pin "1") (pinfunction "+_1") (pintype "passive"))
      (node (ref "JP302") (pin "1") (pinfunction "1_1") (pintype "passive"))
      (node (ref "JP303") (pin "2") (pinfunction "2_2") (pintype "passive"))
      (node (ref "TP65") (pin "TP") (pinfunction "PP_TP") (pintype "input"))
    )
    (net (code "70") (name "Net-(7A-KL)") (class "Default")
      (node (ref "7") (pin "1") (pinfunction "KL_1") (pintype "passive"))
      (node (ref "TP70") (pin "TP") (pinfunction "PP_TP") (pintype "input"))
      (node (ref "X401") (pin "1") (pinfunction "1_1") (pintype "passive"))
    )
    (net (code "71") (name "Net-(7B-KL)") (class "Default")
      (node (ref "7") (pin "10") (pinfunction "KL_10") (pintype "passive"))
      (node (ref "D402") (pin "2") (pinfunction "-_2") (pintype "passive"))
      (node (ref "D403") (pin "2") (pinfunction "-_2") (pintype "passive"))
      (node (ref "JP404") (pin "1") (pinfunction "1_1") (pintype "passive"))
      (node (ref "SJ401") (pin "1") (pinfunction "1_1") (pintype "passive"))
      (node (ref "TP79") (pin "TP") (pinfunction "PP_TP") (pintype "input"))
    )
    (net (code "72") (name "Net-(7C-KL)") (class "Default")
      (node (ref "7") (pin "11") (pinfunction "KL_11") (pintype "passive"))
      (node (ref "D403") (pin "1") (pinfunction "+_1") (pintype "passive"))
      (node (ref "TP80") (pin "TP") (pinfunction "PP_TP") (pintype "input"))
      (node (ref "X401") (pin "19") (pinfunction "19_19") (pintype "passive"))
    )
    (net (code "73") (name "Net-(7E-KL)") (class "Default")
      (node (ref "7") (pin "2") (pinfunction "KL_2") (pintype "passive"))
      (node (ref "Q401") (pin "2") (pinfunction "C_2") (pintype "passive"))
      (node (ref "TP71") (pin "TP") (pinfunction "PP_TP") (pintype "input"))
    )
    (net (code "74") (name "Net-(7F-KL)") (class "Default")
      (node (ref "7") (pin "3") (pinfunction "KL_3") (pintype "passive"))
      (node (ref "IC407") (pin "11") (pinfunction "O6_11") (pintype "open_collector"))
      (node (ref "TP72") (pin "TP") (pinfunction "PP_TP") (pintype "input"))
    )
    (net (code "75") (name "Net-(7G-KL)") (class "Default")
      (node (ref "7") (pin "4") (pinfunction "KL_4") (pintype "passive"))
      (node (ref "IC407") (pin "10") (pinfunction "O7_10") (pintype "open_collector"))
      (node (ref "TP73") (pin "TP") (pinfunction "PP_TP") (pintype "input"))
    )
    (net (code "76") (name "Net-(7H-KL)") (class "Default")
      (node (ref "7") (pin "5") (pinfunction "KL_5") (pintype "passive"))
      (node (ref "IC407") (pin "12") (pinfunction "O5_12") (pintype "open_collector"))
      (node (ref "TP74") (pin "TP") (pinfunction "PP_TP") (pintype "input"))
    )
    (net (code "77") (name "Net-(7I-KL)") (class "Default")
      (node (ref "7") (pin "6") (pinfunction "KL_6") (pintype "passive"))
      (node (ref "IC407") (pin "13") (pinfunction "O4_13") (pintype "open_collector"))
      (node (ref "TP75") (pin "TP") (pinfunction "PP_TP") (pintype "input"))
    )
    (net (code "78") (name "Net-(7J-KL)") (class "Default")
      (node (ref "7") (pin "7") (pinfunction "KL_7") (pintype "passive"))
      (node (ref "IC407") (pin "14") (pinfunction "O3_14") (pintype "open_collector"))
      (node (ref "TP76") (pin "TP") (pinfunction "PP_TP") (pintype "input"))
    )
    (net (code "79") (name "Net-(7K-KL)") (class "Default")
      (node (ref "7") (pin "8") (pinfunction "KL_8") (pintype "passive"))
      (node (ref "Q406") (pin "3") (pinfunction "D_3") (pintype "passive"))
      (node (ref "TP77") (pin "TP") (pinfunction "PP_TP") (pintype "input"))
    )
    (net (code "80") (name "Net-(7L-KL)") (class "Default")
      (node (ref "7") (pin "9") (pinfunction "KL_9") (pintype "passive"))
      (node (ref "D402") (pin "1") (pinfunction "+_1") (pintype "passive"))
      (node (ref "TP78") (pin "TP") (pinfunction "PP_TP") (pintype "input"))
      (node (ref "X401") (pin "17") (pinfunction "17_17") (pintype "passive"))
    )
    (net (code "81") (name "Net-(8B-KL)") (class "Default")
      (node (ref "8") (pin "10") (pinfunction "KL_10") (pintype "passive"))
      (node (ref "TP89") (pin "TP") (pinfunction "PP_TP") (pintype "input"))
      (node (ref "X401") (pin "15") (pinfunction "15_15") (pintype "passive"))
    )
    (net (code "82") (name "Net-(8C-KL)") (class "Default")
      (node (ref "8") (pin "11") (pinfunction "KL_11") (pintype "passive"))
      (node (ref "IC407") (pin "16") (pinfunction "O1_16") (pintype "open_collector"))
      (node (ref "R418") (pin "2") (pinfunction "2_2") (pintype "passive"))
      (node (ref "R419") (pin "1") (pinfunction "1_1") (pintype "passive"))
      (node (ref "TP90") (pin "TP") (pinfunction "PP_TP") (pintype "input"))
    )
    (net (code "83") (name "Net-(8D-KL)") (class "Default")
      (node (ref "8") (pin "12") (pinfunction "KL_12") (pintype "passive"))
      (node (ref "R446") (pin "1") (pinfunction "1_1") (pintype "passive"))
      (node (ref "TP92") (pin "TP") (pinfunction "PP_TP") (pintype "input"))
    )
    (net (code "84") (name "Net-(8E-KL)") (class "Default")
      (node (ref "8") (pin "2") (pinfunction "KL_2") (pintype "passive"))
      (node (ref "D409") (pin "2") (pinfunction "-_2") (pintype "passive"))
      (node (ref "LED402") (pin "K") (pinfunction "C_K") (pintype "passive"))
      (node (ref "TP81") (pin "TP") (pinfunction "PP_TP") (pintype "input"))
      (node (ref "X401") (pin "12") (pinfunction "12_12") (pintype "passive"))
    )
    (net (code "85") (name "Net-(8F-KL)") (class "Default")
      (node (ref "8") (pin "3") (pinfunction "KL_3") (pintype "passive"))
      (node (ref "D408") (pin "2") (pinfunction "-_2") (pintype "passive"))
      (node (ref "LED403") (pin "K") (pinfunction "C_K") (pintype "passive"))
      (node (ref "TP82") (pin "TP") (pinfunction "PP_TP") (pintype "input"))
      (node (ref "X401") (pin "11") (pinfunction "11_11") (pintype "passive"))
    )
    (net (code "86") (name "Net-(8G-KL)") (class "Default")
      (node (ref "8") (pin "4") (pinfunction "KL_4") (pintype "passive"))
      (node (ref "D407") (pin "2") (pinfunction "-_2") (pintype "passive"))
      (node (ref "LED404") (pin "K") (pinfunction "C_K") (pintype "passive"))
      (node (ref "TP83") (pin "TP") (pinfunction "PP_TP") (pintype "input"))
      (node (ref "X401") (pin "10") (pinfunction "10_10") (pintype "passive"))
    )
    (net (code "87") (name "Net-(8H-KL)") (class "Default")
      (node (ref "8") (pin "5") (pinfunction "KL_5") (pintype "passive"))
      (node (ref "D406") (pin "2") (pinfunction "-_2") (pintype "passive"))
      (node (ref "LED405") (pin "K") (pinfunction "C_K") (pintype "passive"))
      (node (ref "TP84") (pin "TP") (pinfunction "PP_TP") (pintype "input"))
      (node (ref "X401") (pin "9") (pinfunction "9_9") (pintype "passive"))
    )
    (net (code "88") (name "Net-(8I-KL)") (class "Default")
      (node (ref "8") (pin "6") (pinfunction "KL_6") (pintype "passive"))
      (node (ref "JP405") (pin "2") (pinfunction "2_2") (pintype "passive"))
      (node (ref "TP85") (pin "TP") (pinfunction "PP_TP") (pintype "input"))
    )
    (net (code "89") (name "Net-(8J-KL)") (class "Default")
      (node (ref "8") (pin "7") (pinfunction "KL_7") (pintype "passive"))
      (node (ref "LED401") (pin "A") (pinfunction "A_A") (pintype "passive"))
      (node (ref "TP86") (pin "TP") (pinfunction "PP_TP") (pintype "input"))
      (node (ref "X401") (pin "8") (pinfunction "8_8") (pintype "passive"))
    )
    (net (code "90") (name "Net-(8K-KL)") (class "Default")
      (node (ref "8") (pin "8") (pinfunction "KL_8") (pintype "passive"))
      (node (ref "D410") (pin "2") (pinfunction "-_2") (pintype "passive"))
      (node (ref "LED406") (pin "K") (pinfunction "C_K") (pintype "passive"))
      (node (ref "TP87") (pin "TP") (pinfunction "PP_TP") (pintype "input"))
      (node (ref "X401") (pin "14") (pinfunction "14_14") (pintype "passive"))
    )
    (net (code "91") (name "Net-(8L-KL)") (class "Default")
      (node (ref "8") (pin "9") (pinfunction "KL_9") (pintype "passive"))
      (node (ref "D407") (pin "1") (pinfunction "+_1") (pintype "passive"))
      (node (ref "D408") (pin "1") (pinfunction "+_1") (pintype "passive"))
      (node (ref "JP402") (pin "1") (pinfunction "1_1") (pintype "passive"))
      (node (ref "JP403") (pin "2") (pinfunction "2_2") (pintype "passive"))
      (node (ref "TP88") (pin "TP") (pinfunction "PP_TP") (pintype "input"))
    )
    (net (code "92") (name "Net-(9A-KL)") (class "Default")
      (node (ref "9") (pin "1") (pinfunction "KL_1") (pintype "passive"))
      (node (ref "TP93") (pin "TP") (pinfunction "PP_TP") (pintype "input"))
      (node (ref "X501") (pin "1") (pinfunction "1_1") (pintype "passive"))
    )
    (net (code "93") (name "Net-(9B-KL)") (class "Default")
      (node (ref "9") (pin "10") (pinfunction "KL_10") (pintype "passive"))
      (node (ref "D502") (pin "2") (pinfunction "-_2") (pintype "passive"))
      (node (ref "D503") (pin "2") (pinfunction "-_2") (pintype "passive"))
      (node (ref "JP504") (pin "1") (pinfunction "1_1") (pintype "passive"))
      (node (ref "SJ501") (pin "1") (pinfunction "1_1") (pintype "passive"))
      (node (ref "TP102") (pin "TP") (pinfunction "PP_TP") (pintype "input"))
    )
    (net (code "94") (name "Net-(9C-KL)") (class "Default")
      (node (ref "9") (pin "11") (pinfunction "KL_11") (pintype "passive"))
      (node (ref "D503") (pin "1") (pinfunction "+_1") (pintype "passive"))
      (node (ref "TP103") (pin "TP") (pinfunction "PP_TP") (pintype "input"))
      (node (ref "X501") (pin "19") (pinfunction "19_19") (pintype "passive"))
    )
    (net (code "95") (name "Net-(9E-KL)") (class "Default")
      (node (ref "9") (pin "2") (pinfunction "KL_2") (pintype "passive"))
      (node (ref "Q501") (pin "2") (pinfunction "C_2") (pintype "passive"))
      (node (ref "TP94") (pin "TP") (pinfunction "PP_TP") (pintype "input"))
    )
    (net (code "96") (name "Net-(9F-KL)") (class "Default")
      (node (ref "9") (pin "3") (pinfunction "KL_3") (pintype "passive"))
      (node (ref "IC507") (pin "11") (pinfunction "O6_11") (pintype "open_collector"))
      (node (ref "TP95") (pin "TP") (pinfunction "PP_TP") (pintype "input"))
    )
    (net (code "97") (name "Net-(9G-KL)") (class "Default")
      (node (ref "9") (pin "4") (pinfunction "KL_4") (pintype "passive"))
      (node (ref "IC507") (pin "10") (pinfunction "O7_10") (pintype "open_collector"))
      (node (ref "TP96") (pin "TP") (pinfunction "PP_TP") (pintype "input"))
    )
    (net (code "98") (name "Net-(9H-KL)") (class "Default")
      (node (ref "9") (pin "5") (pinfunction "KL_5") (pintype "passive"))
      (node (ref "IC507") (pin "12") (pinfunction "O5_12") (pintype "open_collector"))
      (node (ref "TP97") (pin "TP") (pinfunction "PP_TP") (pintype "input"))
    )
    (net (code "99") (name "Net-(9I-KL)") (class "Default")
      (node (ref "9") (pin "6") (pinfunction "KL_6") (pintype "passive"))
      (node (ref "IC507") (pin "13") (pinfunction "O4_13") (pintype "open_collector"))
      (node (ref "TP98") (pin "TP") (pinfunction "PP_TP") (pintype "input"))
    )
    (net (code "100") (name "Net-(9J-KL)") (class "Default")
      (node (ref "9") (pin "7") (pinfunction "KL_7") (pintype "passive"))
      (node (ref "IC507") (pin "14") (pinfunction "O3_14") (pintype "open_collector"))
      (node (ref "TP99") (pin "TP") (pinfunction "PP_TP") (pintype "input"))
    )
    (net (code "101") (name "Net-(9K-KL)") (class "Default")
      (node (ref "9") (pin "8") (pinfunction "KL_8") (pintype "passive"))
      (node (ref "Q506") (pin "3") (pinfunction "D_3") (pintype "passive"))
      (node (ref "TP100") (pin "TP") (pinfunction "PP_TP") (pintype "input"))
    )
    (net (code "102") (name "Net-(9L-KL)") (class "Default")
      (node (ref "9") (pin "9") (pinfunction "KL_9") (pintype "passive"))
      (node (ref "D502") (pin "1") (pinfunction "+_1") (pintype "passive"))
      (node (ref "TP101") (pin "TP") (pinfunction "PP_TP") (pintype "input"))
      (node (ref "X501") (pin "17") (pinfunction "17_17") (pintype "passive"))
    )
    (net (code "103") (name "Net-(10B-KL)") (class "Default")
      (node (ref "10") (pin "10") (pinfunction "KL_10") (pintype "passive"))
      (node (ref "TP112") (pin "TP") (pinfunction "PP_TP") (pintype "input"))
      (node (ref "X501") (pin "15") (pinfunction "15_15") (pintype "passive"))
    )
    (net (code "104") (name "Net-(10C-KL)") (class "Default")
      (node (ref "10") (pin "11") (pinfunction "KL_11") (pintype "passive"))
      (node (ref "IC507") (pin "16") (pinfunction "O1_16") (pintype "open_collector"))
      (node (ref "R518") (pin "2") (pinfunction "2_2") (pintype "passive"))
      (node (ref "R519") (pin "1") (pinfunction "1_1") (pintype "passive"))
      (node (ref "TP113") (pin "TP") (pinfunction "PP_TP") (pintype "input"))
    )
    (net (code "105") (name "Net-(10D-KL)") (class "Default")
      (node (ref "10") (pin "12") (pinfunction "KL_12") (pintype "passive"))
      (node (ref "R546") (pin "1") (pinfunction "1_1") (pintype "passive"))
      (node (ref "TP115") (pin "TP") (pinfunction "PP_TP") (pintype "input"))
    )
    (net (code "106") (name "Net-(10E-KL)") (class "Default")
      (node (ref "10") (pin "2") (pinfunction "KL_2") (pintype "passive"))
      (node (ref "D509") (pin "2") (pinfunction "-_2") (pintype "passive"))
      (node (ref "LED502") (pin "K") (pinfunction "C_K") (pintype "passive"))
      (node (ref "TP104") (pin "TP") (pinfunction "PP_TP") (pintype "input"))
      (node (ref "X501") (pin "12") (pinfunction "12_12") (pintype "passive"))
    )
    (net (code "107") (name "Net-(10F-KL)") (class "Default")
      (node (ref "10") (pin "3") (pinfunction "KL_3") (pintype "passive"))
      (node (ref "D508") (pin "2") (pinfunction "-_2") (pintype "passive"))
      (node (ref "LED503") (pin "K") (pinfunction "C_K") (pintype "passive"))
      (node (ref "TP105") (pin "TP") (pinfunction "PP_TP") (pintype "input"))
      (node (ref "X501") (pin "11") (pinfunction "11_11") (pintype "passive"))
    )
    (net (code "108") (name "Net-(10G-KL)") (class "Default")
      (node (ref "10") (pin "4") (pinfunction "KL_4") (pintype "passive"))
      (node (ref "D507") (pin "2") (pinfunction "-_2") (pintype "passive"))
      (node (ref "LED504") (pin "K") (pinfunction "C_K") (pintype "passive"))
      (node (ref "TP106") (pin "TP") (pinfunction "PP_TP") (pintype "input"))
      (node (ref "X501") (pin "10") (pinfunction "10_10") (pintype "passive"))
    )
    (net (code "109") (name "Net-(10H-KL)") (class "Default")
      (node (ref "10") (pin "5") (pinfunction "KL_5") (pintype "passive"))
      (node (ref "D506") (pin "2") (pinfunction "-_2") (pintype "passive"))
      (node (ref "LED505") (pin "K") (pinfunction "C_K") (pintype "passive"))
      (node (ref "TP107") (pin "TP") (pinfunction "PP_TP") (pintype "input"))
      (node (ref "X501") (pin "9") (pinfunction "9_9") (pintype "passive"))
    )
    (net (code "110") (name "Net-(10I-KL)") (class "Default")
      (node (ref "10") (pin "6") (pinfunction "KL_6") (pintype "passive"))
      (node (ref "JP505") (pin "2") (pinfunction "2_2") (pintype "passive"))
      (node (ref "TP108") (pin "TP") (pinfunction "PP_TP") (pintype "input"))
    )
    (net (code "111") (name "Net-(10J-KL)") (class "Default")
      (node (ref "10") (pin "7") (pinfunction "KL_7") (pintype "passive"))
      (node (ref "LED501") (pin "A") (pinfunction "A_A") (pintype "passive"))
      (node (ref "TP109") (pin "TP") (pinfunction "PP_TP") (pintype "input"))
      (node (ref "X501") (pin "8") (pinfunction "8_8") (pintype "passive"))
    )
    (net (code "112") (name "Net-(10K-KL)") (class "Default")
      (node (ref "10") (pin "8") (pinfunction "KL_8") (pintype "passive"))
      (node (ref "D510") (pin "2") (pinfunction "-_2") (pintype "passive"))
      (node (ref "LED506") (pin "K") (pinfunction "C_K") (pintype "passive"))
      (node (ref "TP110") (pin "TP") (pinfunction "PP_TP") (pintype "input"))
      (node (ref "X501") (pin "14") (pinfunction "14_14") (pintype "passive"))
    )
    (net (code "113") (name "Net-(10L-KL)") (class "Default")
      (node (ref "10") (pin "9") (pinfunction "KL_9") (pintype "passive"))
      (node (ref "D507") (pin "1") (pinfunction "+_1") (pintype "passive"))
      (node (ref "D508") (pin "1") (pinfunction "+_1") (pintype "passive"))
      (node (ref "JP502") (pin "1") (pinfunction "1_1") (pintype "passive"))
      (node (ref "JP503") (pin "2") (pinfunction "2_2") (pintype "passive"))
      (node (ref "TP111") (pin "TP") (pinfunction "PP_TP") (pintype "input"))
    )
    (net (code "114") (name "Net-(11A-KL)") (class "Default")
      (node (ref "11") (pin "1") (pinfunction "KL_1") (pintype "passive"))
      (node (ref "TP116") (pin "TP") (pinfunction "PP_TP") (pintype "input"))
      (node (ref "X601") (pin "1") (pinfunction "1_1") (pintype "passive"))
    )
    (net (code "115") (name "Net-(11B-KL)") (class "Default")
      (node (ref "11") (pin "10") (pinfunction "KL_10") (pintype "passive"))
      (node (ref "D602") (pin "2") (pinfunction "-_2") (pintype "passive"))
      (node (ref "D603") (pin "2") (pinfunction "-_2") (pintype "passive"))
      (node (ref "JP604") (pin "1") (pinfunction "1_1") (pintype "passive"))
      (node (ref "SJ601") (pin "1") (pinfunction "1_1") (pintype "passive"))
      (node (ref "TP125") (pin "TP") (pinfunction "PP_TP") (pintype "input"))
    )
    (net (code "116") (name "Net-(11C-KL)") (class "Default")
      (node (ref "11") (pin "11") (pinfunction "KL_11") (pintype "passive"))
      (node (ref "D603") (pin "1") (pinfunction "+_1") (pintype "passive"))
      (node (ref "TP126") (pin "TP") (pinfunction "PP_TP") (pintype "input"))
      (node (ref "X601") (pin "19") (pinfunction "19_19") (pintype "passive"))
    )
    (net (code "117") (name "Net-(11E-KL)") (class "Default")
      (node (ref "11") (pin "2") (pinfunction "KL_2") (pintype "passive"))
      (node (ref "Q601") (pin "2") (pinfunction "C_2") (pintype "passive"))
      (node (ref "TP117") (pin "TP") (pinfunction "PP_TP") (pintype "input"))
    )
    (net (code "118") (name "Net-(11F-KL)") (class "Default")
      (node (ref "11") (pin "3") (pinfunction "KL_3") (pintype "passive"))
      (node (ref "IC607") (pin "11") (pinfunction "O6_11") (pintype "open_collector"))
      (node (ref "TP118") (pin "TP") (pinfunction "PP_TP") (pintype "input"))
    )
    (net (code "119") (name "Net-(11G-KL)") (class "Default")
      (node (ref "11") (pin "4") (pinfunction "KL_4") (pintype "passive"))
      (node (ref "IC607") (pin "10") (pinfunction "O7_10") (pintype "open_collector"))
      (node (ref "TP119") (pin "TP") (pinfunction "PP_TP") (pintype "input"))
    )
    (net (code "120") (name "Net-(11H-KL)") (class "Default")
      (node (ref "11") (pin "5") (pinfunction "KL_5") (pintype "passive"))
      (node (ref "IC607") (pin "12") (pinfunction "O5_12") (pintype "open_collector"))
      (node (ref "TP120") (pin "TP") (pinfunction "PP_TP") (pintype "input"))
    )
    (net (code "121") (name "Net-(11I-KL)") (class "Default")
      (node (ref "11") (pin "6") (pinfunction "KL_6") (pintype "passive"))
      (node (ref "IC607") (pin "13") (pinfunction "O4_13") (pintype "open_collector"))
      (node (ref "TP121") (pin "TP") (pinfunction "PP_TP") (pintype "input"))
    )
    (net (code "122") (name "Net-(11J-KL)") (class "Default")
      (node (ref "11") (pin "7") (pinfunction "KL_7") (pintype "passive"))
      (node (ref "IC607") (pin "14") (pinfunction "O3_14") (pintype "open_collector"))
      (node (ref "TP122") (pin "TP") (pinfunction "PP_TP") (pintype "input"))
    )
    (net (code "123") (name "Net-(11K-KL)") (class "Default")
      (node (ref "11") (pin "8") (pinfunction "KL_8") (pintype "passive"))
      (node (ref "Q606") (pin "3") (pinfunction "D_3") (pintype "passive"))
      (node (ref "TP123") (pin "TP") (pinfunction "PP_TP") (pintype "input"))
    )
    (net (code "124") (name "Net-(11L-KL)") (class "Default")
      (node (ref "11") (pin "9") (pinfunction "KL_9") (pintype "passive"))
      (node (ref "D602") (pin "1") (pinfunction "+_1") (pintype "passive"))
      (node (ref "TP124") (pin "TP") (pinfunction "PP_TP") (pintype "input"))
      (node (ref "X601") (pin "17") (pinfunction "17_17") (pintype "passive"))
    )
    (net (code "125") (name "Net-(12B-KL)") (class "Default")
      (node (ref "12") (pin "10") (pinfunction "KL_10") (pintype "passive"))
      (node (ref "TP135") (pin "TP") (pinfunction "PP_TP") (pintype "input"))
      (node (ref "X601") (pin "15") (pinfunction "15_15") (pintype "passive"))
    )
    (net (code "126") (name "Net-(12C-KL)") (class "Default")
      (node (ref "12") (pin "11") (pinfunction "KL_11") (pintype "passive"))
      (node (ref "IC607") (pin "16") (pinfunction "O1_16") (pintype "open_collector"))
      (node (ref "R618") (pin "2") (pinfunction "2_2") (pintype "passive"))
      (node (ref "R619") (pin "1") (pinfunction "1_1") (pintype "passive"))
      (node (ref "TP136") (pin "TP") (pinfunction "PP_TP") (pintype "input"))
    )
    (net (code "127") (name "Net-(12D-KL)") (class "Default")
      (node (ref "12") (pin "12") (pinfunction "KL_12") (pintype "passive"))
      (node (ref "R646") (pin "1") (pinfunction "1_1") (pintype "passive"))
      (node (ref "TP138") (pin "TP") (pinfunction "PP_TP") (pintype "input"))
    )
    (net (code "128") (name "Net-(12E-KL)") (class "Default")
      (node (ref "12") (pin "2") (pinfunction "KL_2") (pintype "passive"))
      (node (ref "D609") (pin "2") (pinfunction "-_2") (pintype "passive"))
      (node (ref "LED602") (pin "K") (pinfunction "C_K") (pintype "passive"))
      (node (ref "TP127") (pin "TP") (pinfunction "PP_TP") (pintype "input"))
      (node (ref "X601") (pin "12") (pinfunction "12_12") (pintype "passive"))
    )
    (net (code "129") (name "Net-(12F-KL)") (class "Default")
      (node (ref "12") (pin "3") (pinfunction "KL_3") (pintype "passive"))
      (node (ref "D608") (pin "2") (pinfunction "-_2") (pintype "passive"))
      (node (ref "LED603") (pin "K") (pinfunction "C_K") (pintype "passive"))
      (node (ref "TP128") (pin "TP") (pinfunction "PP_TP") (pintype "input"))
      (node (ref "X601") (pin "11") (pinfunction "11_11") (pintype "passive"))
    )
    (net (code "130") (name "Net-(12G-KL)") (class "Default")
      (node (ref "12") (pin "4") (pinfunction "KL_4") (pintype "passive"))
      (node (ref "D607") (pin "2") (pinfunction "-_2") (pintype "passive"))
      (node (ref "LED604") (pin "K") (pinfunction "C_K") (pintype "passive"))
      (node (ref "TP129") (pin "TP") (pinfunction "PP_TP") (pintype "input"))
      (node (ref "X601") (pin "10") (pinfunction "10_10") (pintype "passive"))
    )
    (net (code "131") (name "Net-(12H-KL)") (class "Default")
      (node (ref "12") (pin "5") (pinfunction "KL_5") (pintype "passive"))
      (node (ref "D606") (pin "2") (pinfunction "-_2") (pintype "passive"))
      (node (ref "LED605") (pin "K") (pinfunction "C_K") (pintype "passive"))
      (node (ref "TP130") (pin "TP") (pinfunction "PP_TP") (pintype "input"))
      (node (ref "X601") (pin "9") (pinfunction "9_9") (pintype "passive"))
    )
    (net (code "132") (name "Net-(12I-KL)") (class "Default")
      (node (ref "12") (pin "6") (pinfunction "KL_6") (pintype "passive"))
      (node (ref "JP605") (pin "2") (pinfunction "2_2") (pintype "passive"))
      (node (ref "TP131") (pin "TP") (pinfunction "PP_TP") (pintype "input"))
    )
    (net (code "133") (name "Net-(12J-KL)") (class "Default")
      (node (ref "12") (pin "7") (pinfunction "KL_7") (pintype "passive"))
      (node (ref "LED601") (pin "A") (pinfunction "A_A") (pintype "passive"))
      (node (ref "TP132") (pin "TP") (pinfunction "PP_TP") (pintype "input"))
      (node (ref "X601") (pin "8") (pinfunction "8_8") (pintype "passive"))
    )
    (net (code "134") (name "Net-(12K-KL)") (class "Default")
      (node (ref "12") (pin "8") (pinfunction "KL_8") (pintype "passive"))
      (node (ref "D610") (pin "2") (pinfunction "-_2") (pintype "passive"))
      (node (ref "LED606") (pin "K") (pinfunction "C_K") (pintype "passive"))
      (node (ref "TP133") (pin "TP") (pinfunction "PP_TP") (pintype "input"))
      (node (ref "X601") (pin "14") (pinfunction "14_14") (pintype "passive"))
    )
    (net (code "135") (name "Net-(12L-KL)") (class "Default")
      (node (ref "12") (pin "9") (pinfunction "KL_9") (pintype "passive"))
      (node (ref "D607") (pin "1") (pinfunction "+_1") (pintype "passive"))
      (node (ref "D608") (pin "1") (pinfunction "+_1") (pintype "passive"))
      (node (ref "JP602") (pin "1") (pinfunction "1_1") (pintype "passive"))
      (node (ref "JP603") (pin "2") (pinfunction "2_2") (pintype "passive"))
      (node (ref "TP134") (pin "TP") (pinfunction "PP_TP") (pintype "input"))
    )
    (net (code "136") (name "Net-(13A-KL)") (class "Default")
      (node (ref "13") (pin "1") (pinfunction "KL_1") (pintype "passive"))
      (node (ref "TP139") (pin "TP") (pinfunction "PP_TP") (pintype "input"))
      (node (ref "X701") (pin "1") (pinfunction "1_1") (pintype "passive"))
    )
    (net (code "137") (name "Net-(13B-KL)") (class "Default")
      (node (ref "13") (pin "10") (pinfunction "KL_10") (pintype "passive"))
      (node (ref "D702") (pin "2") (pinfunction "-_2") (pintype "passive"))
      (node (ref "D703") (pin "2") (pinfunction "-_2") (pintype "passive"))
      (node (ref "JP704") (pin "1") (pinfunction "1_1") (pintype "passive"))
      (node (ref "SJ701") (pin "1") (pinfunction "1_1") (pintype "passive"))
      (node (ref "TP148") (pin "TP") (pinfunction "PP_TP") (pintype "input"))
    )
    (net (code "138") (name "Net-(13C-KL)") (class "Default")
      (node (ref "13") (pin "11") (pinfunction "KL_11") (pintype "passive"))
      (node (ref "D703") (pin "1") (pinfunction "+_1") (pintype "passive"))
      (node (ref "TP149") (pin "TP") (pinfunction "PP_TP") (pintype "input"))
      (node (ref "X701") (pin "19") (pinfunction "19_19") (pintype "passive"))
    )
    (net (code "139") (name "Net-(13E-KL)") (class "Default")
      (node (ref "13") (pin "2") (pinfunction "KL_2") (pintype "passive"))
      (node (ref "Q701") (pin "2") (pinfunction "C_2") (pintype "passive"))
      (node (ref "TP140") (pin "TP") (pinfunction "PP_TP") (pintype "input"))
    )
    (net (code "140") (name "Net-(13F-KL)") (class "Default")
      (node (ref "13") (pin "3") (pinfunction "KL_3") (pintype "passive"))
      (node (ref "IC707") (pin "11") (pinfunction "O6_11") (pintype "open_collector"))
      (node (ref "TP141") (pin "TP") (pinfunction "PP_TP") (pintype "input"))
    )
    (net (code "141") (name "Net-(13G-KL)") (class "Default")
      (node (ref "13") (pin "4") (pinfunction "KL_4") (pintype "passive"))
      (node (ref "IC707") (pin "10") (pinfunction "O7_10") (pintype "open_collector"))
      (node (ref "TP142") (pin "TP") (pinfunction "PP_TP") (pintype "input"))
    )
    (net (code "142") (name "Net-(13H-KL)") (class "Default")
      (node (ref "13") (pin "5") (pinfunction "KL_5") (pintype "passive"))
      (node (ref "IC707") (pin "12") (pinfunction "O5_12") (pintype "open_collector"))
      (node (ref "TP143") (pin "TP") (pinfunction "PP_TP") (pintype "input"))
    )
    (net (code "143") (name "Net-(13I-KL)") (class "Default")
      (node (ref "13") (pin "6") (pinfunction "KL_6") (pintype "passive"))
      (node (ref "IC707") (pin "13") (pinfunction "O4_13") (pintype "open_collector"))
      (node (ref "TP144") (pin "TP") (pinfunction "PP_TP") (pintype "input"))
    )
    (net (code "144") (name "Net-(13J-KL)") (class "Default")
      (node (ref "13") (pin "7") (pinfunction "KL_7") (pintype "passive"))
      (node (ref "IC707") (pin "14") (pinfunction "O3_14") (pintype "open_collector"))
      (node (ref "TP145") (pin "TP") (pinfunction "PP_TP") (pintype "input"))
    )
    (net (code "145") (name "Net-(13K-KL)") (class "Default")
      (node (ref "13") (pin "8") (pinfunction "KL_8") (pintype "passive"))
      (node (ref "Q706") (pin "3") (pinfunction "D_3") (pintype "passive"))
      (node (ref "TP146") (pin "TP") (pinfunction "PP_TP") (pintype "input"))
    )
    (net (code "146") (name "Net-(13L-KL)") (class "Default")
      (node (ref "13") (pin "9") (pinfunction "KL_9") (pintype "passive"))
      (node (ref "D702") (pin "1") (pinfunction "+_1") (pintype "passive"))
      (node (ref "TP147") (pin "TP") (pinfunction "PP_TP") (pintype "input"))
      (node (ref "X701") (pin "17") (pinfunction "17_17") (pintype "passive"))
    )
    (net (code "147") (name "Net-(14B-KL)") (class "Default")
      (node (ref "14") (pin "10") (pinfunction "KL_10") (pintype "passive"))
      (node (ref "TP158") (pin "TP") (pinfunction "PP_TP") (pintype "input"))
      (node (ref "X701") (pin "15") (pinfunction "15_15") (pintype "passive"))
    )
    (net (code "148") (name "Net-(14C-KL)") (class "Default")
      (node (ref "14") (pin "11") (pinfunction "KL_11") (pintype "passive"))
      (node (ref "IC707") (pin "16") (pinfunction "O1_16") (pintype "open_collector"))
      (node (ref "R718") (pin "2") (pinfunction "2_2") (pintype "passive"))
      (node (ref "R719") (pin "1") (pinfunction "1_1") (pintype "passive"))
      (node (ref "TP159") (pin "TP") (pinfunction "PP_TP") (pintype "input"))
    )
    (net (code "149") (name "Net-(14D-KL)") (class "Default")
      (node (ref "14") (pin "12") (pinfunction "KL_12") (pintype "passive"))
      (node (ref "R746") (pin "1") (pinfunction "1_1") (pintype "passive"))
      (node (ref "TP161") (pin "TP") (pinfunction "PP_TP") (pintype "input"))
    )
    (net (code "150") (name "Net-(14E-KL)") (class "Default")
      (node (ref "14") (pin "2") (pinfunction "KL_2") (pintype "passive"))
      (node (ref "D709") (pin "2") (pinfunction "-_2") (pintype "passive"))
      (node (ref "LED702") (pin "K") (pinfunction "C_K") (pintype "passive"))
      (node (ref "TP150") (pin "TP") (pinfunction "PP_TP") (pintype "input"))
      (node (ref "X701") (pin "12") (pinfunction "12_12") (pintype "passive"))
    )
    (net (code "151") (name "Net-(14F-KL)") (class "Default")
      (node (ref "14") (pin "3") (pinfunction "KL_3") (pintype "passive"))
      (node (ref "D708") (pin "2") (pinfunction "-_2") (pintype "passive"))
      (node (ref "LED703") (pin "K") (pinfunction "C_K") (pintype "passive"))
      (node (ref "TP151") (pin "TP") (pinfunction "PP_TP") (pintype "input"))
      (node (ref "X701") (pin "11") (pinfunction "11_11") (pintype "passive"))
    )
    (net (code "152") (name "Net-(14G-KL)") (class "Default")
      (node (ref "14") (pin "4") (pinfunction "KL_4") (pintype "passive"))
      (node (ref "D707") (pin "2") (pinfunction "-_2") (pintype "passive"))
      (node (ref "LED704") (pin "K") (pinfunction "C_K") (pintype "passive"))
      (node (ref "TP152") (pin "TP") (pinfunction "PP_TP") (pintype "input"))
      (node (ref "X701") (pin "10") (pinfunction "10_10") (pintype "passive"))
    )
    (net (code "153") (name "Net-(14H-KL)") (class "Default")
      (node (ref "14") (pin "5") (pinfunction "KL_5") (pintype "passive"))
      (node (ref "D706") (pin "2") (pinfunction "-_2") (pintype "passive"))
      (node (ref "LED705") (pin "K") (pinfunction "C_K") (pintype "passive"))
      (node (ref "TP153") (pin "TP") (pinfunction "PP_TP") (pintype "input"))
      (node (ref "X701") (pin "9") (pinfunction "9_9") (pintype "passive"))
    )
    (net (code "154") (name "Net-(14I-KL)") (class "Default")
      (node (ref "14") (pin "6") (pinfunction "KL_6") (pintype "passive"))
      (node (ref "JP705") (pin "2") (pinfunction "2_2") (pintype "passive"))
      (node (ref "TP154") (pin "TP") (pinfunction "PP_TP") (pintype "input"))
    )
    (net (code "155") (name "Net-(14J-KL)") (class "Default")
      (node (ref "14") (pin "7") (pinfunction "KL_7") (pintype "passive"))
      (node (ref "LED701") (pin "A") (pinfunction "A_A") (pintype "passive"))
      (node (ref "TP155") (pin "TP") (pinfunction "PP_TP") (pintype "input"))
      (node (ref "X701") (pin "8") (pinfunction "8_8") (pintype "passive"))
    )
    (net (code "156") (name "Net-(14K-KL)") (class "Default")
      (node (ref "14") (pin "8") (pinfunction "KL_8") (pintype "passive"))
      (node (ref "D710") (pin "2") (pinfunction "-_2") (pintype "passive"))
      (node (ref "LED706") (pin "K") (pinfunction "C_K") (pintype "passive"))
      (node (ref "TP156") (pin "TP") (pinfunction "PP_TP") (pintype "input"))
      (node (ref "X701") (pin "14") (pinfunction "14_14") (pintype "passive"))
    )
    (net (code "157") (name "Net-(14L-KL)") (class "Default")
      (node (ref "14") (pin "9") (pinfunction "KL_9") (pintype "passive"))
      (node (ref "D707") (pin "1") (pinfunction "+_1") (pintype "passive"))
      (node (ref "D708") (pin "1") (pinfunction "+_1") (pintype "passive"))
      (node (ref "JP702") (pin "1") (pinfunction "1_1") (pintype "passive"))
      (node (ref "JP703") (pin "2") (pinfunction "2_2") (pintype "passive"))
      (node (ref "TP157") (pin "TP") (pinfunction "PP_TP") (pintype "input"))
    )
    (net (code "158") (name "Net-(15A-KL)") (class "Default")
      (node (ref "15") (pin "1") (pinfunction "KL_1") (pintype "passive"))
      (node (ref "TP162") (pin "TP") (pinfunction "PP_TP") (pintype "input"))
      (node (ref "X801") (pin "1") (pinfunction "1_1") (pintype "passive"))
    )
    (net (code "159") (name "Net-(15B-KL)") (class "Default")
      (node (ref "15") (pin "10") (pinfunction "KL_10") (pintype "passive"))
      (node (ref "D802") (pin "2") (pinfunction "-_2") (pintype "passive"))
      (node (ref "D803") (pin "2") (pinfunction "-_2") (pintype "passive"))
      (node (ref "JP804") (pin "1") (pinfunction "1_1") (pintype "passive"))
      (node (ref "SJ801") (pin "1") (pinfunction "1_1") (pintype "passive"))
      (node (ref "TP171") (pin "TP") (pinfunction "PP_TP") (pintype "input"))
    )
    (net (code "160") (name "Net-(15C-KL)") (class "Default")
      (node (ref "15") (pin "11") (pinfunction "KL_11") (pintype "passive"))
      (node (ref "D803") (pin "1") (pinfunction "+_1") (pintype "passive"))
      (node (ref "TP172") (pin "TP") (pinfunction "PP_TP") (pintype "input"))
      (node (ref "X801") (pin "19") (pinfunction "19_19") (pintype "passive"))
    )
    (net (code "161") (name "Net-(15E-KL)") (class "Default")
      (node (ref "15") (pin "2") (pinfunction "KL_2") (pintype "passive"))
      (node (ref "Q801") (pin "2") (pinfunction "C_2") (pintype "passive"))
      (node (ref "TP163") (pin "TP") (pinfunction "PP_TP") (pintype "input"))
    )
    (net (code "162") (name "Net-(15F-KL)") (class "Default")
      (node (ref "15") (pin "3") (pinfunction "KL_3") (pintype "passive"))
      (node (ref "IC807") (pin "11") (pinfunction "O6_11") (pintype "open_collector"))
      (node (ref "TP164") (pin "TP") (pinfunction "PP_TP") (pintype "input"))
    )
    (net (code "163") (name "Net-(15G-KL)") (class "Default")
      (node (ref "15") (pin "4") (pinfunction "KL_4") (pintype "passive"))
      (node (ref "IC807") (pin "10") (pinfunction "O7_10") (pintype "open_collector"))
      (node (ref "TP165") (pin "TP") (pinfunction "PP_TP") (pintype "input"))
    )
    (net (code "164") (name "Net-(15H-KL)") (class "Default")
      (node (ref "15") (pin "5") (pinfunction "KL_5") (pintype "passive"))
      (node (ref "IC807") (pin "12") (pinfunction "O5_12") (pintype "open_collector"))
      (node (ref "TP166") (pin "TP") (pinfunction "PP_TP") (pintype "input"))
    )
    (net (code "165") (name "Net-(15I-KL)") (class "Default")
      (node (ref "15") (pin "6") (pinfunction "KL_6") (pintype "passive"))
      (node (ref "IC807") (pin "13") (pinfunction "O4_13") (pintype "open_collector"))
      (node (ref "TP167") (pin "TP") (pinfunction "PP_TP") (pintype "input"))
    )
    (net (code "166") (name "Net-(15J-KL)") (class "Default")
      (node (ref "15") (pin "7") (pinfunction "KL_7") (pintype "passive"))
      (node (ref "IC807") (pin "14") (pinfunction "O3_14") (pintype "open_collector"))
      (node (ref "TP168") (pin "TP") (pinfunction "PP_TP") (pintype "input"))
    )
    (net (code "167") (name "Net-(15K-KL)") (class "Default")
      (node (ref "15") (pin "8") (pinfunction "KL_8") (pintype "passive"))
      (node (ref "Q806") (pin "3") (pinfunction "D_3") (pintype "passive"))
      (node (ref "TP169") (pin "TP") (pinfunction "PP_TP") (pintype "input"))
    )
    (net (code "168") (name "Net-(15L-KL)") (class "Default")
      (node (ref "15") (pin "9") (pinfunction "KL_9") (pintype "passive"))
      (node (ref "D802") (pin "1") (pinfunction "+_1") (pintype "passive"))
      (node (ref "TP170") (pin "TP") (pinfunction "PP_TP") (pintype "input"))
      (node (ref "X801") (pin "17") (pinfunction "17_17") (pintype "passive"))
    )
    (net (code "169") (name "Net-(16B-KL)") (class "Default")
      (node (ref "16") (pin "10") (pinfunction "KL_10") (pintype "passive"))
      (node (ref "TP181") (pin "TP") (pinfunction "PP_TP") (pintype "input"))
      (node (ref "X801") (pin "15") (pinfunction "15_15") (pintype "passive"))
    )
    (net (code "170") (name "Net-(16C-KL)") (class "Default")
      (node (ref "16") (pin "11") (pinfunction "KL_11") (pintype "passive"))
      (node (ref "IC807") (pin "16") (pinfunction "O1_16") (pintype "open_collector"))
      (node (ref "R818") (pin "2") (pinfunction "2_2") (pintype "passive"))
      (node (ref "R819") (pin "1") (pinfunction "1_1") (pintype "passive"))
      (node (ref "TP182") (pin "TP") (pinfunction "PP_TP") (pintype "input"))
    )
    (net (code "171") (name "Net-(16D-KL)") (class "Default")
      (node (ref "16") (pin "12") (pinfunction "KL_12") (pintype "passive"))
      (node (ref "R846") (pin "1") (pinfunction "1_1") (pintype "passive"))
      (node (ref "TP184") (pin "TP") (pinfunction "PP_TP") (pintype "input"))
    )
    (net (code "172") (name "Net-(16E-KL)") (class "Default")
      (node (ref "16") (pin "2") (pinfunction "KL_2") (pintype "passive"))
      (node (ref "D809") (pin "2") (pinfunction "-_2") (pintype "passive"))
      (node (ref "LED802") (pin "K") (pinfunction "C_K") (pintype "passive"))
      (node (ref "TP173") (pin "TP") (pinfunction "PP_TP") (pintype "input"))
      (node (ref "X801") (pin "12") (pinfunction "12_12") (pintype "passive"))
    )
    (net (code "173") (name "Net-(16F-KL)") (class "Default")
      (node (ref "16") (pin "3") (pinfunction "KL_3") (pintype "passive"))
      (node (ref "D808") (pin "2") (pinfunction "-_2") (pintype "passive"))
      (node (ref "LED803") (pin "K") (pinfunction "C_K") (pintype "passive"))
      (node (ref "TP174") (pin "TP") (pinfunction "PP_TP") (pintype "input"))
      (node (ref "X801") (pin "11") (pinfunction "11_11") (pintype "passive"))
    )
    (net (code "174") (name "Net-(16G-KL)") (class "Default")
      (node (ref "16") (pin "4") (pinfunction "KL_4") (pintype "passive"))
      (node (ref "D807") (pin "2") (pinfunction "-_2") (pintype "passive"))
      (node (ref "LED804") (pin "K") (pinfunction "C_K") (pintype "passive"))
      (node (ref "TP175") (pin "TP") (pinfunction "PP_TP") (pintype "input"))
      (node (ref "X801") (pin "10") (pinfunction "10_10") (pintype "passive"))
    )
    (net (code "175") (name "Net-(16H-KL)") (class "Default")
      (node (ref "16") (pin "5") (pinfunction "KL_5") (pintype "passive"))
      (node (ref "D806") (pin "2") (pinfunction "-_2") (pintype "passive"))
      (node (ref "LED805") (pin "K") (pinfunction "C_K") (pintype "passive"))
      (node (ref "TP176") (pin "TP") (pinfunction "PP_TP") (pintype "input"))
      (node (ref "X801") (pin "9") (pinfunction "9_9") (pintype "passive"))
    )
    (net (code "176") (name "Net-(16I-KL)") (class "Default")
      (node (ref "16") (pin "6") (pinfunction "KL_6") (pintype "passive"))
      (node (ref "JP805") (pin "2") (pinfunction "2_2") (pintype "passive"))
      (node (ref "TP177") (pin "TP") (pinfunction "PP_TP") (pintype "input"))
    )
    (net (code "177") (name "Net-(16J-KL)") (class "Default")
      (node (ref "16") (pin "7") (pinfunction "KL_7") (pintype "passive"))
      (node (ref "LED801") (pin "A") (pinfunction "A_A") (pintype "passive"))
      (node (ref "TP178") (pin "TP") (pinfunction "PP_TP") (pintype "input"))
      (node (ref "X801") (pin "8") (pinfunction "8_8") (pintype "passive"))
    )
    (net (code "178") (name "Net-(16K-KL)") (class "Default")
      (node (ref "16") (pin "8") (pinfunction "KL_8") (pintype "passive"))
      (node (ref "D810") (pin "2") (pinfunction "-_2") (pintype "passive"))
      (node (ref "LED806") (pin "K") (pinfunction "C_K") (pintype "passive"))
      (node (ref "TP179") (pin "TP") (pinfunction "PP_TP") (pintype "input"))
      (node (ref "X801") (pin "14") (pinfunction "14_14") (pintype "passive"))
    )
    (net (code "179") (name "Net-(16L-KL)") (class "Default")
      (node (ref "16") (pin "9") (pinfunction "KL_9") (pintype "passive"))
      (node (ref "D807") (pin "1") (pinfunction "+_1") (pintype "passive"))
      (node (ref "D808") (pin "1") (pinfunction "+_1") (pintype "passive"))
      (node (ref "JP802") (pin "1") (pinfunction "1_1") (pintype "passive"))
      (node (ref "JP803") (pin "2") (pinfunction "2_2") (pintype "passive"))
      (node (ref "TP180") (pin "TP") (pinfunction "PP_TP") (pintype "input"))
    )
    (net (code "180") (name "Net-(17A-KL)") (class "Default")
      (node (ref "17") (pin "1") (pinfunction "KL_1") (pintype "passive"))
      (node (ref "TP185") (pin "TP") (pinfunction "PP_TP") (pintype "input"))
      (node (ref "X901") (pin "1") (pinfunction "1_1") (pintype "passive"))
    )
    (net (code "181") (name "Net-(17B-KL)") (class "Default")
      (node (ref "17") (pin "10") (pinfunction "KL_10") (pintype "passive"))
      (node (ref "D902") (pin "2") (pinfunction "-_2") (pintype "passive"))
      (node (ref "D903") (pin "2") (pinfunction "-_2") (pintype "passive"))
      (node (ref "JP904") (pin "1") (pinfunction "1_1") (pintype "passive"))
      (node (ref "SJ901") (pin "1") (pinfunction "1_1") (pintype "passive"))
      (node (ref "TP194") (pin "TP") (pinfunction "PP_TP") (pintype "input"))
    )
    (net (code "182") (name "Net-(17C-KL)") (class "Default")
      (node (ref "17") (pin "11") (pinfunction "KL_11") (pintype "passive"))
      (node (ref "D903") (pin "1") (pinfunction "+_1") (pintype "passive"))
      (node (ref "TP195") (pin "TP") (pinfunction "PP_TP") (pintype "input"))
      (node (ref "X901") (pin "19") (pinfunction "19_19") (pintype "passive"))
    )
    (net (code "183") (name "Net-(17E-KL)") (class "Default")
      (node (ref "17") (pin "2") (pinfunction "KL_2") (pintype "passive"))
      (node (ref "Q901") (pin "2") (pinfunction "C_2") (pintype "passive"))
      (node (ref "TP186") (pin "TP") (pinfunction "PP_TP") (pintype "input"))
    )
    (net (code "184") (name "Net-(17F-KL)") (class "Default")
      (node (ref "17") (pin "3") (pinfunction "KL_3") (pintype "passive"))
      (node (ref "IC907") (pin "11") (pinfunction "O6_11") (pintype "open_collector"))
      (node (ref "TP187") (pin "TP") (pinfunction "PP_TP") (pintype "input"))
    )
    (net (code "185") (name "Net-(17G-KL)") (class "Default")
      (node (ref "17") (pin "4") (pinfunction "KL_4") (pintype "passive"))
      (node (ref "IC907") (pin "10") (pinfunction "O7_10") (pintype "open_collector"))
      (node (ref "TP188") (pin "TP") (pinfunction "PP_TP") (pintype "input"))
    )
    (net (code "186") (name "Net-(17H-KL)") (class "Default")
      (node (ref "17") (pin "5") (pinfunction "KL_5") (pintype "passive"))
      (node (ref "IC907") (pin "12") (pinfunction "O5_12") (pintype "open_collector"))
      (node (ref "TP189") (pin "TP") (pinfunction "PP_TP") (pintype "input"))
    )
    (net (code "187") (name "Net-(17I-KL)") (class "Default")
      (node (ref "17") (pin "6") (pinfunction "KL_6") (pintype "passive"))
      (node (ref "IC907") (pin "13") (pinfunction "O4_13") (pintype "open_collector"))
      (node (ref "TP190") (pin "TP") (pinfunction "PP_TP") (pintype "input"))
    )
    (net (code "188") (name "Net-(17J-KL)") (class "Default")
      (node (ref "17") (pin "7") (pinfunction "KL_7") (pintype "passive"))
      (node (ref "IC907") (pin "14") (pinfunction "O3_14") (pintype "open_collector"))
      (node (ref "TP191") (pin "TP") (pinfunction "PP_TP") (pintype "input"))
    )
    (net (code "189") (name "Net-(17K-KL)") (class "Default")
      (node (ref "17") (pin "8") (pinfunction "KL_8") (pintype "passive"))
      (node (ref "Q906") (pin "3") (pinfunction "D_3") (pintype "passive"))
      (node (ref "TP192") (pin "TP") (pinfunction "PP_TP") (pintype "input"))
    )
    (net (code "190") (name "Net-(17L-KL)") (class "Default")
      (node (ref "17") (pin "9") (pinfunction "KL_9") (pintype "passive"))
      (node (ref "D902") (pin "1") (pinfunction "+_1") (pintype "passive"))
      (node (ref "TP193") (pin "TP") (pinfunction "PP_TP") (pintype "input"))
      (node (ref "X901") (pin "17") (pinfunction "17_17") (pintype "passive"))
    )
    (net (code "191") (name "Net-(18B-KL)") (class "Default")
      (node (ref "18") (pin "10") (pinfunction "KL_10") (pintype "passive"))
      (node (ref "TP204") (pin "TP") (pinfunction "PP_TP") (pintype "input"))
      (node (ref "X901") (pin "15") (pinfunction "15_15") (pintype "passive"))
    )
    (net (code "192") (name "Net-(18C-KL)") (class "Default")
      (node (ref "18") (pin "11") (pinfunction "KL_11") (pintype "passive"))
      (node (ref "IC907") (pin "16") (pinfunction "O1_16") (pintype "open_collector"))
      (node (ref "R918") (pin "2") (pinfunction "2_2") (pintype "passive"))
      (node (ref "R919") (pin "1") (pinfunction "1_1") (pintype "passive"))
      (node (ref "TP205") (pin "TP") (pinfunction "PP_TP") (pintype "input"))
    )
    (net (code "193") (name "Net-(18D-KL)") (class "Default")
      (node (ref "18") (pin "12") (pinfunction "KL_12") (pintype "passive"))
      (node (ref "R946") (pin "1") (pinfunction "1_1") (pintype "passive"))
      (node (ref "TP207") (pin "TP") (pinfunction "PP_TP") (pintype "input"))
    )
    (net (code "194") (name "Net-(18E-KL)") (class "Default")
      (node (ref "18") (pin "2") (pinfunction "KL_2") (pintype "passive"))
      (node (ref "D909") (pin "2") (pinfunction "-_2") (pintype "passive"))
      (node (ref "LED902") (pin "K") (pinfunction "C_K") (pintype "passive"))
      (node (ref "TP196") (pin "TP") (pinfunction "PP_TP") (pintype "input"))
      (node (ref "X901") (pin "12") (pinfunction "12_12") (pintype "passive"))
    )
    (net (code "195") (name "Net-(18F-KL)") (class "Default")
      (node (ref "18") (pin "3") (pinfunction "KL_3") (pintype "passive"))
      (node (ref "D908") (pin "2") (pinfunction "-_2") (pintype "passive"))
      (node (ref "LED903") (pin "K") (pinfunction "C_K") (pintype "passive"))
      (node (ref "TP197") (pin "TP") (pinfunction "PP_TP") (pintype "input"))
      (node (ref "X901") (pin "11") (pinfunction "11_11") (pintype "passive"))
    )
    (net (code "196") (name "Net-(18G-KL)") (class "Default")
      (node (ref "18") (pin "4") (pinfunction "KL_4") (pintype "passive"))
      (node (ref "D907") (pin "2") (pinfunction "-_2") (pintype "passive"))
      (node (ref "LED904") (pin "K") (pinfunction "C_K") (pintype "passive"))
      (node (ref "TP198") (pin "TP") (pinfunction "PP_TP") (pintype "input"))
      (node (ref "X901") (pin "10") (pinfunction "10_10") (pintype "passive"))
    )
    (net (code "197") (name "Net-(18H-KL)") (class "Default")
      (node (ref "18") (pin "5") (pinfunction "KL_5") (pintype "passive"))
      (node (ref "D906") (pin "2") (pinfunction "-_2") (pintype "passive"))
      (node (ref "LED905") (pin "K") (pinfunction "C_K") (pintype "passive"))
      (node (ref "TP199") (pin "TP") (pinfunction "PP_TP") (pintype "input"))
      (node (ref "X901") (pin "9") (pinfunction "9_9") (pintype "passive"))
    )
    (net (code "198") (name "Net-(18I-KL)") (class "Default")
      (node (ref "18") (pin "6") (pinfunction "KL_6") (pintype "passive"))
      (node (ref "JP905") (pin "2") (pinfunction "2_2") (pintype "passive"))
      (node (ref "TP200") (pin "TP") (pinfunction "PP_TP") (pintype "input"))
    )
    (net (code "199") (name "Net-(18J-KL)") (class "Default")
      (node (ref "18") (pin "7") (pinfunction "KL_7") (pintype "passive"))
      (node (ref "LED901") (pin "A") (pinfunction "A_A") (pintype "passive"))
      (node (ref "TP201") (pin "TP") (pinfunction "PP_TP") (pintype "input"))
      (node (ref "X901") (pin "8") (pinfunction "8_8") (pintype "passive"))
    )
    (net (code "200") (name "Net-(18K-KL)") (class "Default")
      (node (ref "18") (pin "8") (pinfunction "KL_8") (pintype "passive"))
      (node (ref "D910") (pin "2") (pinfunction "-_2") (pintype "passive"))
      (node (ref "LED906") (pin "K") (pinfunction "C_K") (pintype "passive"))
      (node (ref "TP202") (pin "TP") (pinfunction "PP_TP") (pintype "input"))
      (node (ref "X901") (pin "14") (pinfunction "14_14") (pintype "passive"))
    )
    (net (code "201") (name "Net-(18L-KL)") (class "Default")
      (node (ref "18") (pin "9") (pinfunction "KL_9") (pintype "passive"))
      (node (ref "D907") (pin "1") (pinfunction "+_1") (pintype "passive"))
      (node (ref "D908") (pin "1") (pinfunction "+_1") (pintype "passive"))
      (node (ref "JP902") (pin "1") (pinfunction "1_1") (pintype "passive"))
      (node (ref "JP903") (pin "2") (pinfunction "2_2") (pintype "passive"))
      (node (ref "TP203") (pin "TP") (pinfunction "PP_TP") (pintype "input"))
    )
    (net (code "202") (name "Net-(19A-KL)") (class "Default")
      (node (ref "19") (pin "1") (pinfunction "KL_1") (pintype "passive"))
      (node (ref "TP208") (pin "TP") (pinfunction "PP_TP") (pintype "input"))
      (node (ref "X1001") (pin "1") (pinfunction "1_1") (pintype "passive"))
    )
    (net (code "203") (name "Net-(19B-KL)") (class "Default")
      (node (ref "19") (pin "10") (pinfunction "KL_10") (pintype "passive"))
      (node (ref "D1002") (pin "2") (pinfunction "-_2") (pintype "passive"))
      (node (ref "D1003") (pin "2") (pinfunction "-_2") (pintype "passive"))
      (node (ref "JP1004") (pin "1") (pinfunction "1_1") (pintype "passive"))
      (node (ref "SJ1001") (pin "1") (pinfunction "1_1") (pintype "passive"))
      (node (ref "TP217") (pin "TP") (pinfunction "PP_TP") (pintype "input"))
    )
    (net (code "204") (name "Net-(19C-KL)") (class "Default")
      (node (ref "19") (pin "11") (pinfunction "KL_11") (pintype "passive"))
      (node (ref "D1003") (pin "1") (pinfunction "+_1") (pintype "passive"))
      (node (ref "TP218") (pin "TP") (pinfunction "PP_TP") (pintype "input"))
      (node (ref "X1001") (pin "19") (pinfunction "19_19") (pintype "passive"))
    )
    (net (code "205") (name "Net-(19E-KL)") (class "Default")
      (node (ref "19") (pin "2") (pinfunction "KL_2") (pintype "passive"))
      (node (ref "Q1001") (pin "2") (pinfunction "C_2") (pintype "passive"))
      (node (ref "TP209") (pin "TP") (pinfunction "PP_TP") (pintype "input"))
    )
    (net (code "206") (name "Net-(19F-KL)") (class "Default")
      (node (ref "19") (pin "3") (pinfunction "KL_3") (pintype "passive"))
      (node (ref "IC1007") (pin "11") (pinfunction "O6_11") (pintype "open_collector"))
      (node (ref "TP210") (pin "TP") (pinfunction "PP_TP") (pintype "input"))
    )
    (net (code "207") (name "Net-(19G-KL)") (class "Default")
      (node (ref "19") (pin "4") (pinfunction "KL_4") (pintype "passive"))
      (node (ref "IC1007") (pin "10") (pinfunction "O7_10") (pintype "open_collector"))
      (node (ref "TP211") (pin "TP") (pinfunction "PP_TP") (pintype "input"))
    )
    (net (code "208") (name "Net-(19H-KL)") (class "Default")
      (node (ref "19") (pin "5") (pinfunction "KL_5") (pintype "passive"))
      (node (ref "IC1007") (pin "12") (pinfunction "O5_12") (pintype "open_collector"))
      (node (ref "TP212") (pin "TP") (pinfunction "PP_TP") (pintype "input"))
    )
    (net (code "209") (name "Net-(19I-KL)") (class "Default")
      (node (ref "19") (pin "6") (pinfunction "KL_6") (pintype "passive"))
      (node (ref "IC1007") (pin "13") (pinfunction "O4_13") (pintype "open_collector"))
      (node (ref "TP213") (pin "TP") (pinfunction "PP_TP") (pintype "input"))
    )
    (net (code "210") (name "Net-(19J-KL)") (class "Default")
      (node (ref "19") (pin "7") (pinfunction "KL_7") (pintype "passive"))
      (node (ref "IC1007") (pin "14") (pinfunction "O3_14") (pintype "open_collector"))
      (node (ref "TP214") (pin "TP") (pinfunction "PP_TP") (pintype "input"))
    )
    (net (code "211") (name "Net-(19K-KL)") (class "Default")
      (node (ref "19") (pin "8") (pinfunction "KL_8") (pintype "passive"))
      (node (ref "Q1006") (pin "3") (pinfunction "D_3") (pintype "passive"))
      (node (ref "TP215") (pin "TP") (pinfunction "PP_TP") (pintype "input"))
    )
    (net (code "212") (name "Net-(19L-KL)") (class "Default")
      (node (ref "19") (pin "9") (pinfunction "KL_9") (pintype "passive"))
      (node (ref "D1002") (pin "1") (pinfunction "+_1") (pintype "passive"))
      (node (ref "TP216") (pin "TP") (pinfunction "PP_TP") (pintype "input"))
      (node (ref "X1001") (pin "17") (pinfunction "17_17") (pintype "passive"))
    )
    (net (code "213") (name "Net-(20B-KL)") (class "Default")
      (node (ref "20") (pin "10") (pinfunction "KL_10") (pintype "passive"))
      (node (ref "TP227") (pin "TP") (pinfunction "PP_TP") (pintype "input"))
      (node (ref "X1001") (pin "15") (pinfunction "15_15") (pintype "passive"))
    )
    (net (code "214") (name "Net-(20C-KL)") (class "Default")
      (node (ref "20") (pin "11") (pinfunction "KL_11") (pintype "passive"))
      (node (ref "IC1007") (pin "16") (pinfunction "O1_16") (pintype "open_collector"))
      (node (ref "R1018") (pin "2") (pinfunction "2_2") (pintype "passive"))
      (node (ref "R1019") (pin "1") (pinfunction "1_1") (pintype "passive"))
      (node (ref "TP228") (pin "TP") (pinfunction "PP_TP") (pintype "input"))
    )
    (net (code "215") (name "Net-(20D-KL)") (class "Default")
      (node (ref "20") (pin "12") (pinfunction "KL_12") (pintype "passive"))
      (node (ref "R1046") (pin "1") (pinfunction "1_1") (pintype "passive"))
      (node (ref "TP230") (pin "TP") (pinfunction "PP_TP") (pintype "input"))
    )
    (net (code "216") (name "Net-(20E-KL)") (class "Default")
      (node (ref "20") (pin "2") (pinfunction "KL_2") (pintype "passive"))
      (node (ref "D1009") (pin "2") (pinfunction "-_2") (pintype "passive"))
      (node (ref "LED1002") (pin "K") (pinfunction "C_K") (pintype "passive"))
      (node (ref "TP219") (pin "TP") (pinfunction "PP_TP") (pintype "input"))
      (node (ref "X1001") (pin "12") (pinfunction "12_12") (pintype "passive"))
    )
    (net (code "217") (name "Net-(20F-KL)") (class "Default")
      (node (ref "20") (pin "3") (pinfunction "KL_3") (pintype "passive"))
      (node (ref "D1008") (pin "2") (pinfunction "-_2") (pintype "passive"))
      (node (ref "LED1003") (pin "K") (pinfunction "C_K") (pintype "passive"))
      (node (ref "TP220") (pin "TP") (pinfunction "PP_TP") (pintype "input"))
      (node (ref "X1001") (pin "11") (pinfunction "11_11") (pintype "passive"))
    )
    (net (code "218") (name "Net-(20G-KL)") (class "Default")
      (node (ref "20") (pin "4") (pinfunction "KL_4") (pintype "passive"))
      (node (ref "D1007") (pin "2") (pinfunction "-_2") (pintype "passive"))
      (node (ref "LED1004") (pin "K") (pinfunction "C_K") (pintype "passive"))
      (node (ref "TP221") (pin "TP") (pinfunction "PP_TP") (pintype "input"))
      (node (ref "X1001") (pin "10") (pinfunction "10_10") (pintype "passive"))
    )
    (net (code "219") (name "Net-(20H-KL)") (class "Default")
      (node (ref "20") (pin "5") (pinfunction "KL_5") (pintype "passive"))
      (node (ref "D1006") (pin "2") (pinfunction "-_2") (pintype "passive"))
      (node (ref "LED1005") (pin "K") (pinfunction "C_K") (pintype "passive"))
      (node (ref "TP222") (pin "TP") (pinfunction "PP_TP") (pintype "input"))
      (node (ref "X1001") (pin "9") (pinfunction "9_9") (pintype "passive"))
    )
    (net (code "220") (name "Net-(20I-KL)") (class "Default")
      (node (ref "20") (pin "6") (pinfunction "KL_6") (pintype "passive"))
      (node (ref "JP1005") (pin "2") (pinfunction "2_2") (pintype "passive"))
      (node (ref "TP223") (pin "TP") (pinfunction "PP_TP") (pintype "input"))
    )
    (net (code "221") (name "Net-(20J-KL)") (class "Default")
      (node (ref "20") (pin "7") (pinfunction "KL_7") (pintype "passive"))
      (node (ref "LED1001") (pin "A") (pinfunction "A_A") (pintype "passive"))
      (node (ref "TP224") (pin "TP") (pinfunction "PP_TP") (pintype "input"))
      (node (ref "X1001") (pin "8") (pinfunction "8_8") (pintype "passive"))
    )
    (net (code "222") (name "Net-(20K-KL)") (class "Default")
      (node (ref "20") (pin "8") (pinfunction "KL_8") (pintype "passive"))
      (node (ref "D1010") (pin "2") (pinfunction "-_2") (pintype "passive"))
      (node (ref "LED1006") (pin "K") (pinfunction "C_K") (pintype "passive"))
      (node (ref "TP225") (pin "TP") (pinfunction "PP_TP") (pintype "input"))
      (node (ref "X1001") (pin "14") (pinfunction "14_14") (pintype "passive"))
    )
    (net (code "223") (name "Net-(20L-KL)") (class "Default")
      (node (ref "20") (pin "9") (pinfunction "KL_9") (pintype "passive"))
      (node (ref "D1007") (pin "1") (pinfunction "+_1") (pintype "passive"))
      (node (ref "D1008") (pin "1") (pinfunction "+_1") (pintype "passive"))
      (node (ref "JP1002") (pin "1") (pinfunction "1_1") (pintype "passive"))
      (node (ref "JP1003") (pin "2") (pinfunction "2_2") (pintype "passive"))
      (node (ref "TP226") (pin "TP") (pinfunction "PP_TP") (pintype "input"))
    )
    (net (code "224") (name "Net-(21A-KL)") (class "Default")
      (node (ref "21") (pin "1") (pinfunction "KL_1") (pintype "passive"))
      (node (ref "TP231") (pin "TP") (pinfunction "PP_TP") (pintype "input"))
      (node (ref "X1101") (pin "1") (pinfunction "1_1") (pintype "passive"))
    )
    (net (code "225") (name "Net-(21B-KL)") (class "Default")
      (node (ref "21") (pin "10") (pinfunction "KL_10") (pintype "passive"))
      (node (ref "D1102") (pin "2") (pinfunction "-_2") (pintype "passive"))
      (node (ref "D1103") (pin "2") (pinfunction "-_2") (pintype "passive"))
      (node (ref "JP1104") (pin "1") (pinfunction "1_1") (pintype "passive"))
      (node (ref "SJ1101") (pin "1") (pinfunction "1_1") (pintype "passive"))
      (node (ref "TP240") (pin "TP") (pinfunction "PP_TP") (pintype "input"))
    )
    (net (code "226") (name "Net-(21C-KL)") (class "Default")
      (node (ref "21") (pin "11") (pinfunction "KL_11") (pintype "passive"))
      (node (ref "D1103") (pin "1") (pinfunction "+_1") (pintype "passive"))
      (node (ref "TP241") (pin "TP") (pinfunction "PP_TP") (pintype "input"))
      (node (ref "X1101") (pin "19") (pinfunction "19_19") (pintype "passive"))
    )
    (net (code "227") (name "Net-(21E-KL)") (class "Default")
      (node (ref "21") (pin "2") (pinfunction "KL_2") (pintype "passive"))
      (node (ref "Q1101") (pin "2") (pinfunction "C_2") (pintype "passive"))
      (node (ref "TP232") (pin "TP") (pinfunction "PP_TP") (pintype "input"))
    )
    (net (code "228") (name "Net-(21F-KL)") (class "Default")
      (node (ref "21") (pin "3") (pinfunction "KL_3") (pintype "passive"))
      (node (ref "IC1107") (pin "11") (pinfunction "O6_11") (pintype "open_collector"))
      (node (ref "TP233") (pin "TP") (pinfunction "PP_TP") (pintype "input"))
    )
    (net (code "229") (name "Net-(21G-KL)") (class "Default")
      (node (ref "21") (pin "4") (pinfunction "KL_4") (pintype "passive"))
      (node (ref "IC1107") (pin "10") (pinfunction "O7_10") (pintype "open_collector"))
      (node (ref "TP234") (pin "TP") (pinfunction "PP_TP") (pintype "input"))
    )
    (net (code "230") (name "Net-(21H-KL)") (class "Default")
      (node (ref "21") (pin "5") (pinfunction "KL_5") (pintype "passive"))
      (node (ref "IC1107") (pin "12") (pinfunction "O5_12") (pintype "open_collector"))
      (node (ref "TP235") (pin "TP") (pinfunction "PP_TP") (pintype "input"))
    )
    (net (code "231") (name "Net-(21I-KL)") (class "Default")
      (node (ref "21") (pin "6") (pinfunction "KL_6") (pintype "passive"))
      (node (ref "IC1107") (pin "13") (pinfunction "O4_13") (pintype "open_collector"))
      (node (ref "TP236") (pin "TP") (pinfunction "PP_TP") (pintype "input"))
    )
    (net (code "232") (name "Net-(21J-KL)") (class "Default")
      (node (ref "21") (pin "7") (pinfunction "KL_7") (pintype "passive"))
      (node (ref "IC1107") (pin "14") (pinfunction "O3_14") (pintype "open_collector"))
      (node (ref "TP237") (pin "TP") (pinfunction "PP_TP") (pintype "input"))
    )
    (net (code "233") (name "Net-(21K-KL)") (class "Default")
      (node (ref "21") (pin "8") (pinfunction "KL_8") (pintype "passive"))
      (node (ref "Q1106") (pin "3") (pinfunction "D_3") (pintype "passive"))
      (node (ref "TP238") (pin "TP") (pinfunction "PP_TP") (pintype "input"))
    )
    (net (code "234") (name "Net-(21L-KL)") (class "Default")
      (node (ref "21") (pin "9") (pinfunction "KL_9") (pintype "passive"))
      (node (ref "D1102") (pin "1") (pinfunction "+_1") (pintype "passive"))
      (node (ref "TP239") (pin "TP") (pinfunction "PP_TP") (pintype "input"))
      (node (ref "X1101") (pin "17") (pinfunction "17_17") (pintype "passive"))
    )
    (net (code "235") (name "Net-(22B-KL)") (class "Default")
      (node (ref "22") (pin "10") (pinfunction "KL_10") (pintype "passive"))
      (node (ref "TP250") (pin "TP") (pinfunction "PP_TP") (pintype "input"))
      (node (ref "X1101") (pin "15") (pinfunction "15_15") (pintype "passive"))
    )
    (net (code "236") (name "Net-(22C-KL)") (class "Default")
      (node (ref "22") (pin "11") (pinfunction "KL_11") (pintype "passive"))
      (node (ref "IC1107") (pin "16") (pinfunction "O1_16") (pintype "open_collector"))
      (node (ref "R1118") (pin "2") (pinfunction "2_2") (pintype "passive"))
      (node (ref "R1119") (pin "1") (pinfunction "1_1") (pintype "passive"))
      (node (ref "TP251") (pin "TP") (pinfunction "PP_TP") (pintype "input"))
    )
    (net (code "237") (name "Net-(22D-KL)") (class "Default")
      (node (ref "22") (pin "12") (pinfunction "KL_12") (pintype "passive"))
      (node (ref "R1146") (pin "1") (pinfunction "1_1") (pintype "passive"))
      (node (ref "TP253") (pin "TP") (pinfunction "PP_TP") (pintype "input"))
    )
    (net (code "238") (name "Net-(22E-KL)") (class "Default")
      (node (ref "22") (pin "2") (pinfunction "KL_2") (pintype "passive"))
      (node (ref "D1109") (pin "2") (pinfunction "-_2") (pintype "passive"))
      (node (ref "LED1102") (pin "K") (pinfunction "C_K") (pintype "passive"))
      (node (ref "TP242") (pin "TP") (pinfunction "PP_TP") (pintype "input"))
      (node (ref "X1101") (pin "12") (pinfunction "12_12") (pintype "passive"))
    )
    (net (code "239") (name "Net-(22F-KL)") (class "Default")
      (node (ref "22") (pin "3") (pinfunction "KL_3") (pintype "passive"))
      (node (ref "D1108") (pin "2") (pinfunction "-_2") (pintype "passive"))
      (node (ref "LED1103") (pin "K") (pinfunction "C_K") (pintype "passive"))
      (node (ref "TP243") (pin "TP") (pinfunction "PP_TP") (pintype "input"))
      (node (ref "X1101") (pin "11") (pinfunction "11_11") (pintype "passive"))
    )
    (net (code "240") (name "Net-(22G-KL)") (class "Default")
      (node (ref "22") (pin "4") (pinfunction "KL_4") (pintype "passive"))
      (node (ref "D1107") (pin "2") (pinfunction "-_2") (pintype "passive"))
      (node (ref "LED1104") (pin "K") (pinfunction "C_K") (pintype "passive"))
      (node (ref "TP244") (pin "TP") (pinfunction "PP_TP") (pintype "input"))
      (node (ref "X1101") (pin "10") (pinfunction "10_10") (pintype "passive"))
    )
    (net (code "241") (name "Net-(22H-KL)") (class "Default")
      (node (ref "22") (pin "5") (pinfunction "KL_5") (pintype "passive"))
      (node (ref "D1106") (pin "2") (pinfunction "-_2") (pintype "passive"))
      (node (ref "LED1105") (pin "K") (pinfunction "C_K") (pintype "passive"))
      (node (ref "TP245") (pin "TP") (pinfunction "PP_TP") (pintype "input"))
      (node (ref "X1101") (pin "9") (pinfunction "9_9") (pintype "passive"))
    )
    (net (code "242") (name "Net-(22I-KL)") (class "Default")
      (node (ref "22") (pin "6") (pinfunction "KL_6") (pintype "passive"))
      (node (ref "JP1105") (pin "2") (pinfunction "2_2") (pintype "passive"))
      (node (ref "TP246") (pin "TP") (pinfunction "PP_TP") (pintype "input"))
    )
    (net (code "243") (name "Net-(22J-KL)") (class "Default")
      (node (ref "22") (pin "7") (pinfunction "KL_7") (pintype "passive"))
      (node (ref "LED1101") (pin "A") (pinfunction "A_A") (pintype "passive"))
      (node (ref "TP247") (pin "TP") (pinfunction "PP_TP") (pintype "input"))
      (node (ref "X1101") (pin "8") (pinfunction "8_8") (pintype "passive"))
    )
    (net (code "244") (name "Net-(22K-KL)") (class "Default")
      (node (ref "22") (pin "8") (pinfunction "KL_8") (pintype "passive"))
      (node (ref "D1110") (pin "2") (pinfunction "-_2") (pintype "passive"))
      (node (ref "LED1106") (pin "K") (pinfunction "C_K") (pintype "passive"))
      (node (ref "TP248") (pin "TP") (pinfunction "PP_TP") (pintype "input"))
      (node (ref "X1101") (pin "14") (pinfunction "14_14") (pintype "passive"))
    )
    (net (code "245") (name "Net-(22L-KL)") (class "Default")
      (node (ref "22") (pin "9") (pinfunction "KL_9") (pintype "passive"))
      (node (ref "D1107") (pin "1") (pinfunction "+_1") (pintype "passive"))
      (node (ref "D1108") (pin "1") (pinfunction "+_1") (pintype "passive"))
      (node (ref "JP1102") (pin "1") (pinfunction "1_1") (pintype "passive"))
      (node (ref "JP1103") (pin "2") (pinfunction "2_2") (pintype "passive"))
      (node (ref "TP249") (pin "TP") (pinfunction "PP_TP") (pintype "input"))
    )
    (net (code "246") (name "Net-(23A-KL)") (class "Default")
      (node (ref "23") (pin "1") (pinfunction "KL_1") (pintype "passive"))
      (node (ref "TP254") (pin "TP") (pinfunction "PP_TP") (pintype "input"))
      (node (ref "X1201") (pin "1") (pinfunction "1_1") (pintype "passive"))
    )
    (net (code "247") (name "Net-(23B-KL)") (class "Default")
      (node (ref "23") (pin "10") (pinfunction "KL_10") (pintype "passive"))
      (node (ref "D1202") (pin "2") (pinfunction "-_2") (pintype "passive"))
      (node (ref "D1203") (pin "2") (pinfunction "-_2") (pintype "passive"))
      (node (ref "JP1204") (pin "1") (pinfunction "1_1") (pintype "passive"))
      (node (ref "SJ1201") (pin "1") (pinfunction "1_1") (pintype "passive"))
      (node (ref "TP263") (pin "TP") (pinfunction "PP_TP") (pintype "input"))
    )
    (net (code "248") (name "Net-(23C-KL)") (class "Default")
      (node (ref "23") (pin "11") (pinfunction "KL_11") (pintype "passive"))
      (node (ref "D1203") (pin "1") (pinfunction "+_1") (pintype "passive"))
      (node (ref "TP264") (pin "TP") (pinfunction "PP_TP") (pintype "input"))
      (node (ref "X1201") (pin "19") (pinfunction "19_19") (pintype "passive"))
    )
    (net (code "249") (name "Net-(23E-KL)") (class "Default")
      (node (ref "23") (pin "2") (pinfunction "KL_2") (pintype "passive"))
      (node (ref "Q1201") (pin "2") (pinfunction "C_2") (pintype "passive"))
      (node (ref "TP255") (pin "TP") (pinfunction "PP_TP") (pintype "input"))
    )
    (net (code "250") (name "Net-(23F-KL)") (class "Default")
      (node (ref "23") (pin "3") (pinfunction "KL_3") (pintype "passive"))
      (node (ref "IC1207") (pin "11") (pinfunction "O6_11") (pintype "open_collector"))
      (node (ref "TP256") (pin "TP") (pinfunction "PP_TP") (pintype "input"))
    )
    (net (code "251") (name "Net-(23G-KL)") (class "Default")
      (node (ref "23") (pin "4") (pinfunction "KL_4") (pintype "passive"))
      (node (ref "IC1207") (pin "10") (pinfunction "O7_10") (pintype "open_collector"))
      (node (ref "TP257") (pin "TP") (pinfunction "PP_TP") (pintype "input"))
    )
    (net (code "252") (name "Net-(23H-KL)") (class "Default")
      (node (ref "23") (pin "5") (pinfunction "KL_5") (pintype "passive"))
      (node (ref "IC1207") (pin "12") (pinfunction "O5_12") (pintype "open_collector"))
      (node (ref "TP258") (pin "TP") (pinfunction "PP_TP") (pintype "input"))
    )
    (net (code "253") (name "Net-(23I-KL)") (class "Default")
      (node (ref "23") (pin "6") (pinfunction "KL_6") (pintype "passive"))
      (node (ref "IC1207") (pin "13") (pinfunction "O4_13") (pintype "open_collector"))
      (node (ref "TP259") (pin "TP") (pinfunction "PP_TP") (pintype "input"))
    )
    (net (code "254") (name "Net-(23J-KL)") (class "Default")
      (node (ref "23") (pin "7") (pinfunction "KL_7") (pintype "passive"))
      (node (ref "IC1207") (pin "14") (pinfunction "O3_14") (pintype "open_collector"))
      (node (ref "TP260") (pin "TP") (pinfunction "PP_TP") (pintype "input"))
    )
    (net (code "255") (name "Net-(23K-KL)") (class "Default")
      (node (ref "23") (pin "8") (pinfunction "KL_8") (pintype "passive"))
      (node (ref "Q1206") (pin "3") (pinfunction "D_3") (pintype "passive"))
      (node (ref "TP261") (pin "TP") (pinfunction "PP_TP") (pintype "input"))
    )
    (net (code "256") (name "Net-(23L-KL)") (class "Default")
      (node (ref "23") (pin "9") (pinfunction "KL_9") (pintype "passive"))
      (node (ref "D1202") (pin "1") (pinfunction "+_1") (pintype "passive"))
      (node (ref "TP262") (pin "TP") (pinfunction "PP_TP") (pintype "input"))
      (node (ref "X1201") (pin "17") (pinfunction "17_17") (pintype "passive"))
    )
    (net (code "257") (name "Net-(24B-KL)") (class "Default")
      (node (ref "24") (pin "10") (pinfunction "KL_10") (pintype "passive"))
      (node (ref "TP273") (pin "TP") (pinfunction "PP_TP") (pintype "input"))
      (node (ref "X1201") (pin "15") (pinfunction "15_15") (pintype "passive"))
    )
    (net (code "258") (name "Net-(24C-KL)") (class "Default")
      (node (ref "24") (pin "11") (pinfunction "KL_11") (pintype "passive"))
      (node (ref "IC1207") (pin "16") (pinfunction "O1_16") (pintype "open_collector"))
      (node (ref "R1218") (pin "2") (pinfunction "2_2") (pintype "passive"))
      (node (ref "R1219") (pin "1") (pinfunction "1_1") (pintype "passive"))
      (node (ref "TP274") (pin "TP") (pinfunction "PP_TP") (pintype "input"))
    )
    (net (code "259") (name "Net-(24D-KL)") (class "Default")
      (node (ref "24") (pin "12") (pinfunction "KL_12") (pintype "passive"))
      (node (ref "R1246") (pin "1") (pinfunction "1_1") (pintype "passive"))
      (node (ref "TP276") (pin "TP") (pinfunction "PP_TP") (pintype "input"))
    )
    (net (code "260") (name "Net-(24E-KL)") (class "Default")
      (node (ref "24") (pin "2") (pinfunction "KL_2") (pintype "passive"))
      (node (ref "D1209") (pin "2") (pinfunction "-_2") (pintype "passive"))
      (node (ref "LED1202") (pin "K") (pinfunction "C_K") (pintype "passive"))
      (node (ref "TP265") (pin "TP") (pinfunction "PP_TP") (pintype "input"))
      (node (ref "X1201") (pin "12") (pinfunction "12_12") (pintype "passive"))
    )
    (net (code "261") (name "Net-(24F-KL)") (class "Default")
      (node (ref "24") (pin "3") (pinfunction "KL_3") (pintype "passive"))
      (node (ref "D1208") (pin "2") (pinfunction "-_2") (pintype "passive"))
      (node (ref "LED1203") (pin "K") (pinfunction "C_K") (pintype "passive"))
      (node (ref "TP266") (pin "TP") (pinfunction "PP_TP") (pintype "input"))
      (node (ref "X1201") (pin "11") (pinfunction "11_11") (pintype "passive"))
    )
    (net (code "262") (name "Net-(24G-KL)") (class "Default")
      (node (ref "24") (pin "4") (pinfunction "KL_4") (pintype "passive"))
      (node (ref "D1207") (pin "2") (pinfunction "-_2") (pintype "passive"))
      (node (ref "LED1204") (pin "K") (pinfunction "C_K") (pintype "passive"))
      (node (ref "TP267") (pin "TP") (pinfunction "PP_TP") (pintype "input"))
      (node (ref "X1201") (pin "10") (pinfunction "10_10") (pintype "passive"))
    )
    (net (code "263") (name "Net-(24H-KL)") (class "Default")
      (node (ref "24") (pin "5") (pinfunction "KL_5") (pintype "passive"))
      (node (ref "D1206") (pin "2") (pinfunction "-_2") (pintype "passive"))
      (node (ref "LED1205") (pin "K") (pinfunction "C_K") (pintype "passive"))
      (node (ref "TP268") (pin "TP") (pinfunction "PP_TP") (pintype "input"))
      (node (ref "X1201") (pin "9") (pinfunction "9_9") (pintype "passive"))
    )
    (net (code "264") (name "Net-(24I-KL)") (class "Default")
      (node (ref "24") (pin "6") (pinfunction "KL_6") (pintype "passive"))
      (node (ref "JP1205") (pin "2") (pinfunction "2_2") (pintype "passive"))
      (node (ref "TP269") (pin "TP") (pinfunction "PP_TP") (pintype "input"))
    )
    (net (code "265") (name "Net-(24J-KL)") (class "Default")
      (node (ref "24") (pin "7") (pinfunction "KL_7") (pintype "passive"))
      (node (ref "LED1201") (pin "A") (pinfunction "A_A") (pintype "passive"))
      (node (ref "TP270") (pin "TP") (pinfunction "PP_TP") (pintype "input"))
      (node (ref "X1201") (pin "8") (pinfunction "8_8") (pintype "passive"))
    )
    (net (code "266") (name "Net-(24K-KL)") (class "Default")
      (node (ref "24") (pin "8") (pinfunction "KL_8") (pintype "passive"))
      (node (ref "D1210") (pin "2") (pinfunction "-_2") (pintype "passive"))
      (node (ref "LED1206") (pin "K") (pinfunction "C_K") (pintype "passive"))
      (node (ref "TP271") (pin "TP") (pinfunction "PP_TP") (pintype "input"))
      (node (ref "X1201") (pin "14") (pinfunction "14_14") (pintype "passive"))
    )
    (net (code "267") (name "Net-(24L-KL)") (class "Default")
      (node (ref "24") (pin "9") (pinfunction "KL_9") (pintype "passive"))
      (node (ref "D1207") (pin "1") (pinfunction "+_1") (pintype "passive"))
      (node (ref "D1208") (pin "1") (pinfunction "+_1") (pintype "passive"))
      (node (ref "JP1202") (pin "1") (pinfunction "1_1") (pintype "passive"))
      (node (ref "JP1203") (pin "2") (pinfunction "2_2") (pintype "passive"))
      (node (ref "TP272") (pin "TP") (pinfunction "PP_TP") (pintype "input"))
    )
    (net (code "268") (name "Net-(C103-Pad1)") (class "Default")
      (node (ref "C103") (pin "1") (pinfunction "1_1") (pintype "passive"))
      (node (ref "R108") (pin "1") (pinfunction "1_1") (pintype "passive"))
      (node (ref "R112") (pin "1") (pinfunction "1_1") (pintype "passive"))
    )
    (net (code "269") (name "Net-(C107-Pad1)") (class "Default")
      (node (ref "C107") (pin "1") (pinfunction "1_1") (pintype "passive"))
      (node (ref "R125") (pin "1") (pinfunction "1_1") (pintype "passive"))
      (node (ref "R130") (pin "2") (pinfunction "2_2") (pintype "passive"))
    )
    (net (code "270") (name "Net-(C203-Pad1)") (class "Default")
      (node (ref "C203") (pin "1") (pinfunction "1_1") (pintype "passive"))
      (node (ref "R208") (pin "1") (pinfunction "1_1") (pintype "passive"))
      (node (ref "R212") (pin "1") (pinfunction "1_1") (pintype "passive"))
    )
    (net (code "271") (name "Net-(C207-Pad1)") (class "Default")
      (node (ref "C207") (pin "1") (pinfunction "1_1") (pintype "passive"))
      (node (ref "R225") (pin "1") (pinfunction "1_1") (pintype "passive"))
      (node (ref "R230") (pin "2") (pinfunction "2_2") (pintype "passive"))
    )
    (net (code "272") (name "Net-(C303-Pad1)") (class "Default")
      (node (ref "C303") (pin "1") (pinfunction "1_1") (pintype "passive"))
      (node (ref "R308") (pin "1") (pinfunction "1_1") (pintype "passive"))
      (node (ref "R312") (pin "1") (pinfunction "1_1") (pintype "passive"))
    )
    (net (code "273") (name "Net-(C307-Pad1)") (class "Default")
      (node (ref "C307") (pin "1") (pinfunction "1_1") (pintype "passive"))
      (node (ref "R325") (pin "1") (pinfunction "1_1") (pintype "passive"))
      (node (ref "R330") (pin "2") (pinfunction "2_2") (pintype "passive"))
    )
    (net (code "274") (name "Net-(C403-Pad1)") (class "Default")
      (node (ref "C403") (pin "1") (pinfunction "1_1") (pintype "passive"))
      (node (ref "R408") (pin "1") (pinfunction "1_1") (pintype "passive"))
      (node (ref "R412") (pin "1") (pinfunction "1_1") (pintype "passive"))
    )
    (net (code "275") (name "Net-(C407-Pad1)") (class "Default")
      (node (ref "C407") (pin "1") (pinfunction "1_1") (pintype "passive"))
      (node (ref "R425") (pin "1") (pinfunction "1_1") (pintype "passive"))
      (node (ref "R430") (pin "2") (pinfunction "2_2") (pintype "passive"))
    )
    (net (code "276") (name "Net-(C503-Pad1)") (class "Default")
      (node (ref "C503") (pin "1") (pinfunction "1_1") (pintype "passive"))
      (node (ref "R508") (pin "1") (pinfunction "1_1") (pintype "passive"))
      (node (ref "R512") (pin "1") (pinfunction "1_1") (pintype "passive"))
    )
    (net (code "277") (name "Net-(C507-Pad1)") (class "Default")
      (node (ref "C507") (pin "1") (pinfunction "1_1") (pintype "passive"))
      (node (ref "R525") (pin "1") (pinfunction "1_1") (pintype "passive"))
      (node (ref "R530") (pin "2") (pinfunction "2_2") (pintype "passive"))
    )
    (net (code "278") (name "Net-(C603-Pad1)") (class "Default")
      (node (ref "C603") (pin "1") (pinfunction "1_1") (pintype "passive"))
      (node (ref "R608") (pin "1") (pinfunction "1_1") (pintype "passive"))
      (node (ref "R612") (pin "1") (pinfunction "1_1") (pintype "passive"))
    )
    (net (code "279") (name "Net-(C607-Pad1)") (class "Default")
      (node (ref "C607") (pin "1") (pinfunction "1_1") (pintype "passive"))
      (node (ref "R625") (pin "1") (pinfunction "1_1") (pintype "passive"))
      (node (ref "R630") (pin "2") (pinfunction "2_2") (pintype "passive"))
    )
    (net (code "280") (name "Net-(C703-Pad1)") (class "Default")
      (node (ref "C703") (pin "1") (pinfunction "1_1") (pintype "passive"))
      (node (ref "R708") (pin "1") (pinfunction "1_1") (pintype "passive"))
      (node (ref "R712") (pin "1") (pinfunction "1_1") (pintype "passive"))
    )
    (net (code "281") (name "Net-(C707-Pad1)") (class "Default")
      (node (ref "C707") (pin "1") (pinfunction "1_1") (pintype "passive"))
      (node (ref "R725") (pin "1") (pinfunction "1_1") (pintype "passive"))
      (node (ref "R730") (pin "2") (pinfunction "2_2") (pintype "passive"))
    )
    (net (code "282") (name "Net-(C803-Pad1)") (class "Default")
      (node (ref "C803") (pin "1") (pinfunction "1_1") (pintype "passive"))
      (node (ref "R808") (pin "1") (pinfunction "1_1") (pintype "passive"))
      (node (ref "R812") (pin "1") (pinfunction "1_1") (pintype "passive"))
    )
    (net (code "283") (name "Net-(C807-Pad1)") (class "Default")
      (node (ref "C807") (pin "1") (pinfunction "1_1") (pintype "passive"))
      (node (ref "R825") (pin "1") (pinfunction "1_1") (pintype "passive"))
      (node (ref "R830") (pin "2") (pinfunction "2_2") (pintype "passive"))
    )
    (net (code "284") (name "Net-(C903-Pad1)") (class "Default")
      (node (ref "C903") (pin "1") (pinfunction "1_1") (pintype "passive"))
      (node (ref "R908") (pin "1") (pinfunction "1_1") (pintype "passive"))
      (node (ref "R912") (pin "1") (pinfunction "1_1") (pintype "passive"))
    )
    (net (code "285") (name "Net-(C907-Pad1)") (class "Default")
      (node (ref "C907") (pin "1") (pinfunction "1_1") (pintype "passive"))
      (node (ref "R925") (pin "1") (pinfunction "1_1") (pintype "passive"))
      (node (ref "R930") (pin "2") (pinfunction "2_2") (pintype "passive"))
    )
    (net (code "286") (name "Net-(C1003-Pad1)") (class "Default")
      (node (ref "C1003") (pin "1") (pinfunction "1_1") (pintype "passive"))
      (node (ref "R1008") (pin "1") (pinfunction "1_1") (pintype "passive"))
      (node (ref "R1012") (pin "1") (pinfunction "1_1") (pintype "passive"))
    )
    (net (code "287") (name "Net-(C1007-Pad1)") (class "Default")
      (node (ref "C1007") (pin "1") (pinfunction "1_1") (pintype "passive"))
      (node (ref "R1025") (pin "1") (pinfunction "1_1") (pintype "passive"))
      (node (ref "R1030") (pin "2") (pinfunction "2_2") (pintype "passive"))
    )
    (net (code "288") (name "Net-(C1103-Pad1)") (class "Default")
      (node (ref "C1103") (pin "1") (pinfunction "1_1") (pintype "passive"))
      (node (ref "R1108") (pin "1") (pinfunction "1_1") (pintype "passive"))
      (node (ref "R1112") (pin "1") (pinfunction "1_1") (pintype "passive"))
    )
    (net (code "289") (name "Net-(C1107-Pad1)") (class "Default")
      (node (ref "C1107") (pin "1") (pinfunction "1_1") (pintype "passive"))
      (node (ref "R1125") (pin "1") (pinfunction "1_1") (pintype "passive"))
      (node (ref "R1130") (pin "2") (pinfunction "2_2") (pintype "passive"))
    )
    (net (code "290") (name "Net-(C1203-Pad1)") (class "Default")
      (node (ref "C1203") (pin "1") (pinfunction "1_1") (pintype "passive"))
      (node (ref "R1208") (pin "1") (pinfunction "1_1") (pintype "passive"))
      (node (ref "R1212") (pin "1") (pinfunction "1_1") (pintype "passive"))
    )
    (net (code "291") (name "Net-(C1207-Pad1)") (class "Default")
      (node (ref "C1207") (pin "1") (pinfunction "1_1") (pintype "passive"))
      (node (ref "R1225") (pin "1") (pinfunction "1_1") (pintype "passive"))
      (node (ref "R1230") (pin "2") (pinfunction "2_2") (pintype "passive"))
    )
    (net (code "292") (name "Net-(D104-PadC)") (class "Default")
      (node (ref "D104") (pin "C") (pinfunction "C_C") (pintype "passive"))
      (node (ref "R105") (pin "2") (pinfunction "2_2") (pintype "passive"))
      (node (ref "X101") (pin "22") (pinfunction "22_22") (pintype "passive"))
    )
    (net (code "293") (name "Net-(D105--)") (class "Default")
      (node (ref "D105") (pin "2") (pinfunction "-_2") (pintype "passive"))
      (node (ref "Q104") (pin "2") (pinfunction "C_2") (pintype "passive"))
      (node (ref "START") (pin "TP") (pinfunction "PP_TP") (pintype "input"))
      (node (ref "X101") (pin "5") (pinfunction "5_5") (pintype "passive"))
    )
    (net (code "294") (name "Net-(D106-+)") (class "Default")
      (node (ref "D106") (pin "1") (pinfunction "+_1") (pintype "passive"))
      (node (ref "R127") (pin "1") (pinfunction "1_1") (pintype "passive"))
    )
    (net (code "295") (name "Net-(D109-+)") (class "Default")
      (node (ref "D109") (pin "1") (pinfunction "+_1") (pintype "passive"))
      (node (ref "JP102") (pin "2") (pinfunction "2_2") (pintype "passive"))
    )
    (net (code "296") (name "Net-(D110-+)") (class "Default")
      (node (ref "D110") (pin "1") (pinfunction "+_1") (pintype "passive"))
      (node (ref "JP103") (pin "1") (pinfunction "1_1") (pintype "passive"))
    )
    (net (code "297") (name "Net-(D111-+)") (class "Default")
      (node (ref "D111") (pin "1") (pinfunction "+_1") (pintype "passive"))
      (node (ref "R133") (pin "1") (pinfunction "1_1") (pintype "passive"))
    )
    (net (code "298") (name "Net-(D111--)") (class "Default")
      (node (ref "D111") (pin "2") (pinfunction "-_2") (pintype "passive"))
      (node (ref "IC108") (pin "2") (pinfunction "OUT_2") (pintype "open_collector"))
      (node (ref "JP105") (pin "1") (pinfunction "1_1") (pintype "passive"))
      (node (ref "Q107") (pin "1") (pinfunction "G_1") (pintype "passive"))
      (node (ref "R135") (pin "2") (pinfunction "2_2") (pintype "passive"))
    )
    (net (code "299") (name "Net-(D112-+)") (class "Default")
      (node (ref "D112") (pin "1") (pinfunction "+_1") (pintype "passive"))
      (node (ref "R140") (pin "1") (pinfunction "1_1") (pintype "passive"))
    )
    (net (code "300") (name "Net-(D112--)") (class "Default")
      (node (ref "C109") (pin "2") (pinfunction "2_2") (pintype "passive"))
      (node (ref "D112") (pin "2") (pinfunction "-_2") (pintype "passive"))
      (node (ref "IC106") (pin "6") (pinfunction "D2_6") (pintype "passive"))
      (node (ref "IC110") (pin "2") (pinfunction "TR_2") (pintype "input"))
      (node (ref "IC110") (pin "6") (pinfunction "THR_6") (pintype "input"))
      (node (ref "R141") (pin "1") (pinfunction "1_1") (pintype "passive"))
    )
    (net (code "301") (name "Net-(D204-PadC)") (class "Default")
      (node (ref "D204") (pin "C") (pinfunction "C_C") (pintype "passive"))
      (node (ref "R205") (pin "2") (pinfunction "2_2") (pintype "passive"))
      (node (ref "X201") (pin "22") (pinfunction "22_22") (pintype "passive"))
    )
    (net (code "302") (name "Net-(D205--)") (class "Default")
      (node (ref "D205") (pin "2") (pinfunction "-_2") (pintype "passive"))
      (node (ref "Q204") (pin "2") (pinfunction "C_2") (pintype "passive"))
      (node (ref "START201") (pin "TP") (pinfunction "PP_TP") (pintype "input"))
      (node (ref "X201") (pin "5") (pinfunction "5_5") (pintype "passive"))
    )
    (net (code "303") (name "Net-(D206-+)") (class "Default")
      (node (ref "D206") (pin "1") (pinfunction "+_1") (pintype "passive"))
      (node (ref "R227") (pin "1") (pinfunction "1_1") (pintype "passive"))
    )
    (net (code "304") (name "Net-(D209-+)") (class "Default")
      (node (ref "D209") (pin "1") (pinfunction "+_1") (pintype "passive"))
      (node (ref "JP202") (pin "2") (pinfunction "2_2") (pintype "passive"))
    )
    (net (code "305") (name "Net-(D210-+)") (class "Default")
      (node (ref "D210") (pin "1") (pinfunction "+_1") (pintype "passive"))
      (node (ref "JP203") (pin "1") (pinfunction "1_1") (pintype "passive"))
    )
    (net (code "306") (name "Net-(D211-+)") (class "Default")
      (node (ref "D211") (pin "1") (pinfunction "+_1") (pintype "passive"))
      (node (ref "R233") (pin "1") (pinfunction "1_1") (pintype "passive"))
    )
    (net (code "307") (name "Net-(D211--)") (class "Default")
      (node (ref "D211") (pin "2") (pinfunction "-_2") (pintype "passive"))
      (node (ref "IC208") (pin "2") (pinfunction "OUT_2") (pintype "open_collector"))
      (node (ref "JP205") (pin "1") (pinfunction "1_1") (pintype "passive"))
      (node (ref "Q207") (pin "1") (pinfunction "G_1") (pintype "passive"))
      (node (ref "R235") (pin "2") (pinfunction "2_2") (pintype "passive"))
    )
    (net (code "308") (name "Net-(D212-+)") (class "Default")
      (node (ref "D212") (pin "1") (pinfunction "+_1") (pintype "passive"))
      (node (ref "R240") (pin "1") (pinfunction "1_1") (pintype "passive"))
    )
    (net (code "309") (name "Net-(D212--)") (class "Default")
      (node (ref "C209") (pin "2") (pinfunction "2_2") (pintype "passive"))
      (node (ref "D212") (pin "2") (pinfunction "-_2") (pintype "passive"))
      (node (ref "IC206") (pin "6") (pinfunction "D2_6") (pintype "passive"))
      (node (ref "IC210") (pin "2") (pinfunction "TR_2") (pintype "input"))
      (node (ref "IC210") (pin "6") (pinfunction "THR_6") (pintype "input"))
      (node (ref "R241") (pin "1") (pinfunction "1_1") (pintype "passive"))
    )
    (net (code "310") (name "Net-(D304-PadC)") (class "Default")
      (node (ref "D304") (pin "C") (pinfunction "C_C") (pintype "passive"))
      (node (ref "R305") (pin "2") (pinfunction "2_2") (pintype "passive"))
      (node (ref "X301") (pin "22") (pinfunction "22_22") (pintype "passive"))
    )
    (net (code "311") (name "Net-(D305--)") (class "Default")
      (node (ref "D305") (pin "2") (pinfunction "-_2") (pintype "passive"))
      (node (ref "Q304") (pin "2") (pinfunction "C_2") (pintype "passive"))
      (node (ref "START301") (pin "TP") (pinfunction "PP_TP") (pintype "input"))
      (node (ref "X301") (pin "5") (pinfunction "5_5") (pintype "passive"))
    )
    (net (code "312") (name "Net-(D306-+)") (class "Default")
      (node (ref "D306") (pin "1") (pinfunction "+_1") (pintype "passive"))
      (node (ref "R327") (pin "1") (pinfunction "1_1") (pintype "passive"))
    )
    (net (code "313") (name "Net-(D309-+)") (class "Default")
      (node (ref "D309") (pin "1") (pinfunction "+_1") (pintype "passive"))
      (node (ref "JP302") (pin "2") (pinfunction "2_2") (pintype "passive"))
    )
    (net (code "314") (name "Net-(D310-+)") (class "Default")
      (node (ref "D310") (pin "1") (pinfunction "+_1") (pintype "passive"))
      (node (ref "JP303") (pin "1") (pinfunction "1_1") (pintype "passive"))
    )
    (net (code "315") (name "Net-(D311-+)") (class "Default")
      (node (ref "D311") (pin "1") (pinfunction "+_1") (pintype "passive"))
      (node (ref "R333") (pin "1") (pinfunction "1_1") (pintype "passive"))
    )
    (net (code "316") (name "Net-(D311--)") (class "Default")
      (node (ref "D311") (pin "2") (pinfunction "-_2") (pintype "passive"))
      (node (ref "IC308") (pin "2") (pinfunction "OUT_2") (pintype "open_collector"))
      (node (ref "JP305") (pin "1") (pinfunction "1_1") (pintype "passive"))
      (node (ref "Q307") (pin "1") (pinfunction "G_1") (pintype "passive"))
      (node (ref "R335") (pin "2") (pinfunction "2_2") (pintype "passive"))
    )
    (net (code "317") (name "Net-(D312-+)") (class "Default")
      (node (ref "D312") (pin "1") (pinfunction "+_1") (pintype "passive"))
      (node (ref "R340") (pin "1") (pinfunction "1_1") (pintype "passive"))
    )
    (net (code "318") (name "Net-(D312--)") (class "Default")
      (node (ref "C309") (pin "2") (pinfunction "2_2") (pintype "passive"))
      (node (ref "D312") (pin "2") (pinfunction "-_2") (pintype "passive"))
      (node (ref "IC306") (pin "6") (pinfunction "D2_6") (pintype "passive"))
      (node (ref "IC310") (pin "2") (pinfunction "TR_2") (pintype "input"))
      (node (ref "IC310") (pin "6") (pinfunction "THR_6") (pintype "input"))
      (node (ref "R341") (pin "1") (pinfunction "1_1") (pintype "passive"))
    )
    (net (code "319") (name "Net-(D404-PadC)") (class "Default")
      (node (ref "D404") (pin "C") (pinfunction "C_C") (pintype "passive"))
      (node (ref "R405") (pin "2") (pinfunction "2_2") (pintype "passive"))
      (node (ref "X401") (pin "22") (pinfunction "22_22") (pintype "passive"))
    )
    (net (code "320") (name "Net-(D405--)") (class "Default")
      (node (ref "D405") (pin "2") (pinfunction "-_2") (pintype "passive"))
      (node (ref "Q404") (pin "2") (pinfunction "C_2") (pintype "passive"))
      (node (ref "START401") (pin "TP") (pinfunction "PP_TP") (pintype "input"))
      (node (ref "X401") (pin "5") (pinfunction "5_5") (pintype "passive"))
    )
    (net (code "321") (name "Net-(D406-+)") (class "Default")
      (node (ref "D406") (pin "1") (pinfunction "+_1") (pintype "passive"))
      (node (ref "R427") (pin "1") (pinfunction "1_1") (pintype "passive"))
    )
    (net (code "322") (name "Net-(D409-+)") (class "Default")
      (node (ref "D409") (pin "1") (pinfunction "+_1") (pintype "passive"))
      (node (ref "JP402") (pin "2") (pinfunction "2_2") (pintype "passive"))
    )
    (net (code "323") (name "Net-(D410-+)") (class "Default")
      (node (ref "D410") (pin "1") (pinfunction "+_1") (pintype "passive"))
      (node (ref "JP403") (pin "1") (pinfunction "1_1") (pintype "passive"))
    )
    (net (code "324") (name "Net-(D411-+)") (class "Default")
      (node (ref "D411") (pin "1") (pinfunction "+_1") (pintype "passive"))
      (node (ref "R433") (pin "1") (pinfunction "1_1") (pintype "passive"))
    )
    (net (code "325") (name "Net-(D411--)") (class "Default")
      (node (ref "D411") (pin "2") (pinfunction "-_2") (pintype "passive"))
      (node (ref "IC408") (pin "2") (pinfunction "OUT_2") (pintype "open_collector"))
      (node (ref "JP405") (pin "1") (pinfunction "1_1") (pintype "passive"))
      (node (ref "Q407") (pin "1") (pinfunction "G_1") (pintype "passive"))
      (node (ref "R435") (pin "2") (pinfunction "2_2") (pintype "passive"))
    )
    (net (code "326") (name "Net-(D412-+)") (class "Default")
      (node (ref "D412") (pin "1") (pinfunction "+_1") (pintype "passive"))
      (node (ref "R440") (pin "1") (pinfunction "1_1") (pintype "passive"))
    )
    (net (code "327") (name "Net-(D412--)") (class "Default")
      (node (ref "C409") (pin "2") (pinfunction "2_2") (pintype "passive"))
      (node (ref "D412") (pin "2") (pinfunction "-_2") (pintype "passive"))
      (node (ref "IC406") (pin "6") (pinfunction "D2_6") (pintype "passive"))
      (node (ref "IC410") (pin "2") (pinfunction "TR_2") (pintype "input"))
      (node (ref "IC410") (pin "6") (pinfunction "THR_6") (pintype "input"))
      (node (ref "R441") (pin "1") (pinfunction "1_1") (pintype "passive"))
    )
    (net (code "328") (name "Net-(D504-PadC)") (class "Default")
      (node (ref "D504") (pin "C") (pinfunction "C_C") (pintype "passive"))
      (node (ref "R505") (pin "2") (pinfunction "2_2") (pintype "passive"))
      (node (ref "X501") (pin "22") (pinfunction "22_22") (pintype "passive"))
    )
    (net (code "329") (name "Net-(D505--)") (class "Default")
      (node (ref "D505") (pin "2") (pinfunction "-_2") (pintype "passive"))
      (node (ref "Q504") (pin "2") (pinfunction "C_2") (pintype "passive"))
      (node (ref "START501") (pin "TP") (pinfunction "PP_TP") (pintype "input"))
      (node (ref "X501") (pin "5") (pinfunction "5_5") (pintype "passive"))
    )
    (net (code "330") (name "Net-(D506-+)") (class "Default")
      (node (ref "D506") (pin "1") (pinfunction "+_1") (pintype "passive"))
      (node (ref "R527") (pin "1") (pinfunction "1_1") (pintype "passive"))
    )
    (net (code "331") (name "Net-(D509-+)") (class "Default")
      (node (ref "D509") (pin "1") (pinfunction "+_1") (pintype "passive"))
      (node (ref "JP502") (pin "2") (pinfunction "2_2") (pintype "passive"))
    )
    (net (code "332") (name "Net-(D510-+)") (class "Default")
      (node (ref "D510") (pin "1") (pinfunction "+_1") (pintype "passive"))
      (node (ref "JP503") (pin "1") (pinfunction "1_1") (pintype "passive"))
    )
    (net (code "333") (name "Net-(D511-+)") (class "Default")
      (node (ref "D511") (pin "1") (pinfunction "+_1") (pintype "passive"))
      (node (ref "R533") (pin "1") (pinfunction "1_1") (pintype "passive"))
    )
    (net (code "334") (name "Net-(D511--)") (class "Default")
      (node (ref "D511") (pin "2") (pinfunction "-_2") (pintype "passive"))
      (node (ref "IC508") (pin "2") (pinfunction "OUT_2") (pintype "open_collector"))
      (node (ref "JP505") (pin "1") (pinfunction "1_1") (pintype "passive"))
      (node (ref "Q507") (pin "1") (pinfunction "G_1") (pintype "passive"))
      (node (ref "R535") (pin "2") (pinfunction "2_2") (pintype "passive"))
    )
    (net (code "335") (name "Net-(D512-+)") (class "Default")
      (node (ref "D512") (pin "1") (pinfunction "+_1") (pintype "passive"))
      (node (ref "R540") (pin "1") (pinfunction "1_1") (pintype "passive"))
    )
    (net (code "336") (name "Net-(D512--)") (class "Default")
      (node (ref "C509") (pin "2") (pinfunction "2_2") (pintype "passive"))
      (node (ref "D512") (pin "2") (pinfunction "-_2") (pintype "passive"))
      (node (ref "IC506") (pin "6") (pinfunction "D2_6") (pintype "passive"))
      (node (ref "IC510") (pin "2") (pinfunction "TR_2") (pintype "input"))
      (node (ref "IC510") (pin "6") (pinfunction "THR_6") (pintype "input"))
      (node (ref "R541") (pin "1") (pinfunction "1_1") (pintype "passive"))
    )
    (net (code "337") (name "Net-(D604-PadC)") (class "Default")
      (node (ref "D604") (pin "C") (pinfunction "C_C") (pintype "passive"))
      (node (ref "R605") (pin "2") (pinfunction "2_2") (pintype "passive"))
      (node (ref "X601") (pin "22") (pinfunction "22_22") (pintype "passive"))
    )
    (net (code "338") (name "Net-(D605--)") (class "Default")
      (node (ref "D605") (pin "2") (pinfunction "-_2") (pintype "passive"))
      (node (ref "Q604") (pin "2") (pinfunction "C_2") (pintype "passive"))
      (node (ref "START601") (pin "TP") (pinfunction "PP_TP") (pintype "input"))
      (node (ref "X601") (pin "5") (pinfunction "5_5") (pintype "passive"))
    )
    (net (code "339") (name "Net-(D606-+)") (class "Default")
      (node (ref "D606") (pin "1") (pinfunction "+_1") (pintype "passive"))
      (node (ref "R627") (pin "1") (pinfunction "1_1") (pintype "passive"))
    )
    (net (code "340") (name "Net-(D609-+)") (class "Default")
      (node (ref "D609") (pin "1") (pinfunction "+_1") (pintype "passive"))
      (node (ref "JP602") (pin "2") (pinfunction "2_2") (pintype "passive"))
    )
    (net (code "341") (name "Net-(D610-+)") (class "Default")
      (node (ref "D610") (pin "1") (pinfunction "+_1") (pintype "passive"))
      (node (ref "JP603") (pin "1") (pinfunction "1_1") (pintype "passive"))
    )
    (net (code "342") (name "Net-(D611-+)") (class "Default")
      (node (ref "D611") (pin "1") (pinfunction "+_1") (pintype "passive"))
      (node (ref "R633") (pin "1") (pinfunction "1_1") (pintype "passive"))
    )
    (net (code "343") (name "Net-(D611--)") (class "Default")
      (node (ref "D611") (pin "2") (pinfunction "-_2") (pintype "passive"))
      (node (ref "IC608") (pin "2") (pinfunction "OUT_2") (pintype "open_collector"))
      (node (ref "JP605") (pin "1") (pinfunction "1_1") (pintype "passive"))
      (node (ref "Q607") (pin "1") (pinfunction "G_1") (pintype "passive"))
      (node (ref "R635") (pin "2") (pinfunction "2_2") (pintype "passive"))
    )
    (net (code "344") (name "Net-(D612-+)") (class "Default")
      (node (ref "D612") (pin "1") (pinfunction "+_1") (pintype "passive"))
      (node (ref "R640") (pin "1") (pinfunction "1_1") (pintype "passive"))
    )
    (net (code "345") (name "Net-(D612--)") (class "Default")
      (node (ref "C609") (pin "2") (pinfunction "2_2") (pintype "passive"))
      (node (ref "D612") (pin "2") (pinfunction "-_2") (pintype "passive"))
      (node (ref "IC606") (pin "6") (pinfunction "D2_6") (pintype "passive"))
      (node (ref "IC610") (pin "2") (pinfunction "TR_2") (pintype "input"))
      (node (ref "IC610") (pin "6") (pinfunction "THR_6") (pintype "input"))
      (node (ref "R641") (pin "1") (pinfunction "1_1") (pintype "passive"))
    )
    (net (code "346") (name "Net-(D704-PadC)") (class "Default")
      (node (ref "D704") (pin "C") (pinfunction "C_C") (pintype "passive"))
      (node (ref "R705") (pin "2") (pinfunction "2_2") (pintype "passive"))
      (node (ref "X701") (pin "22") (pinfunction "22_22") (pintype "passive"))
    )
    (net (code "347") (name "Net-(D705--)") (class "Default")
      (node (ref "D705") (pin "2") (pinfunction "-_2") (pintype "passive"))
      (node (ref "Q704") (pin "2") (pinfunction "C_2") (pintype "passive"))
      (node (ref "START701") (pin "TP") (pinfunction "PP_TP") (pintype "input"))
      (node (ref "X701") (pin "5") (pinfunction "5_5") (pintype "passive"))
    )
    (net (code "348") (name "Net-(D706-+)") (class "Default")
      (node (ref "D706") (pin "1") (pinfunction "+_1") (pintype "passive"))
      (node (ref "R727") (pin "1") (pinfunction "1_1") (pintype "passive"))
    )
    (net (code "349") (name "Net-(D709-+)") (class "Default")
      (node (ref "D709") (pin "1") (pinfunction "+_1") (pintype "passive"))
      (node (ref "JP702") (pin "2") (pinfunction "2_2") (pintype "passive"))
    )
    (net (code "350") (name "Net-(D710-+)") (class "Default")
      (node (ref "D710") (pin "1") (pinfunction "+_1") (pintype "passive"))
      (node (ref "JP703") (pin "1") (pinfunction "1_1") (pintype "passive"))
    )
    (net (code "351") (name "Net-(D711-+)") (class "Default")
      (node (ref "D711") (pin "1") (pinfunction "+_1") (pintype "passive"))
      (node (ref "R733") (pin "1") (pinfunction "1_1") (pintype "passive"))
    )
    (net (code "352") (name "Net-(D711--)") (class "Default")
      (node (ref "D711") (pin "2") (pinfunction "-_2") (pintype "passive"))
      (node (ref "IC708") (pin "2") (pinfunction "OUT_2") (pintype "open_collector"))
      (node (ref "JP705") (pin "1") (pinfunction "1_1") (pintype "passive"))
      (node (ref "Q707") (pin "1") (pinfunction "G_1") (pintype "passive"))
      (node (ref "R735") (pin "2") (pinfunction "2_2") (pintype "passive"))
    )
    (net (code "353") (name "Net-(D712-+)") (class "Default")
      (node (ref "D712") (pin "1") (pinfunction "+_1") (pintype "passive"))
      (node (ref "R740") (pin "1") (pinfunction "1_1") (pintype "passive"))
    )
    (net (code "354") (name "Net-(D712--)") (class "Default")
      (node (ref "C709") (pin "2") (pinfunction "2_2") (pintype "passive"))
      (node (ref "D712") (pin "2") (pinfunction "-_2") (pintype "passive"))
      (node (ref "IC706") (pin "6") (pinfunction "D2_6") (pintype "passive"))
      (node (ref "IC710") (pin "2") (pinfunction "TR_2") (pintype "input"))
      (node (ref "IC710") (pin "6") (pinfunction "THR_6") (pintype "input"))
      (node (ref "R741") (pin "1") (pinfunction "1_1") (pintype "passive"))
    )
    (net (code "355") (name "Net-(D804-PadC)") (class "Default")
      (node (ref "D804") (pin "C") (pinfunction "C_C") (pintype "passive"))
      (node (ref "R805") (pin "2") (pinfunction "2_2") (pintype "passive"))
      (node (ref "X801") (pin "22") (pinfunction "22_22") (pintype "passive"))
    )
    (net (code "356") (name "Net-(D805--)") (class "Default")
      (node (ref "D805") (pin "2") (pinfunction "-_2") (pintype "passive"))
      (node (ref "Q804") (pin "2") (pinfunction "C_2") (pintype "passive"))
      (node (ref "START801") (pin "TP") (pinfunction "PP_TP") (pintype "input"))
      (node (ref "X801") (pin "5") (pinfunction "5_5") (pintype "passive"))
    )
    (net (code "357") (name "Net-(D806-+)") (class "Default")
      (node (ref "D806") (pin "1") (pinfunction "+_1") (pintype "passive"))
      (node (ref "R827") (pin "1") (pinfunction "1_1") (pintype "passive"))
    )
    (net (code "358") (name "Net-(D809-+)") (class "Default")
      (node (ref "D809") (pin "1") (pinfunction "+_1") (pintype "passive"))
      (node (ref "JP802") (pin "2") (pinfunction "2_2") (pintype "passive"))
    )
    (net (code "359") (name "Net-(D810-+)") (class "Default")
      (node (ref "D810") (pin "1") (pinfunction "+_1") (pintype "passive"))
      (node (ref "JP803") (pin "1") (pinfunction "1_1") (pintype "passive"))
    )
    (net (code "360") (name "Net-(D811-+)") (class "Default")
      (node (ref "D811") (pin "1") (pinfunction "+_1") (pintype "passive"))
      (node (ref "R833") (pin "1") (pinfunction "1_1") (pintype "passive"))
    )
    (net (code "361") (name "Net-(D811--)") (class "Default")
      (node (ref "D811") (pin "2") (pinfunction "-_2") (pintype "passive"))
      (node (ref "IC808") (pin "2") (pinfunction "OUT_2") (pintype "open_collector"))
      (node (ref "JP805") (pin "1") (pinfunction "1_1") (pintype "passive"))
      (node (ref "Q807") (pin "1") (pinfunction "G_1") (pintype "passive"))
      (node (ref "R835") (pin "2") (pinfunction "2_2") (pintype "passive"))
    )
    (net (code "362") (name "Net-(D812-+)") (class "Default")
      (node (ref "D812") (pin "1") (pinfunction "+_1") (pintype "passive"))
      (node (ref "R840") (pin "1") (pinfunction "1_1") (pintype "passive"))
    )
    (net (code "363") (name "Net-(D812--)") (class "Default")
      (node (ref "C809") (pin "2") (pinfunction "2_2") (pintype "passive"))
      (node (ref "D812") (pin "2") (pinfunction "-_2") (pintype "passive"))
      (node (ref "IC806") (pin "6") (pinfunction "D2_6") (pintype "passive"))
      (node (ref "IC810") (pin "2") (pinfunction "TR_2") (pintype "input"))
      (node (ref "IC810") (pin "6") (pinfunction "THR_6") (pintype "input"))
      (node (ref "R841") (pin "1") (pinfunction "1_1") (pintype "passive"))
    )
    (net (code "364") (name "Net-(D904-PadC)") (class "Default")
      (node (ref "D904") (pin "C") (pinfunction "C_C") (pintype "passive"))
      (node (ref "R905") (pin "2") (pinfunction "2_2") (pintype "passive"))
      (node (ref "X901") (pin "22") (pinfunction "22_22") (pintype "passive"))
    )
    (net (code "365") (name "Net-(D905--)") (class "Default")
      (node (ref "D905") (pin "2") (pinfunction "-_2") (pintype "passive"))
      (node (ref "Q904") (pin "2") (pinfunction "C_2") (pintype "passive"))
      (node (ref "START901") (pin "TP") (pinfunction "PP_TP") (pintype "input"))
      (node (ref "X901") (pin "5") (pinfunction "5_5") (pintype "passive"))
    )
    (net (code "366") (name "Net-(D906-+)") (class "Default")
      (node (ref "D906") (pin "1") (pinfunction "+_1") (pintype "passive"))
      (node (ref "R927") (pin "1") (pinfunction "1_1") (pintype "passive"))
    )
    (net (code "367") (name "Net-(D909-+)") (class "Default")
      (node (ref "D909") (pin "1") (pinfunction "+_1") (pintype "passive"))
      (node (ref "JP902") (pin "2") (pinfunction "2_2") (pintype "passive"))
    )
    (net (code "368") (name "Net-(D910-+)") (class "Default")
      (node (ref "D910") (pin "1") (pinfunction "+_1") (pintype "passive"))
      (node (ref "JP903") (pin "1") (pinfunction "1_1") (pintype "passive"))
    )
    (net (code "369") (name "Net-(D911-+)") (class "Default")
      (node (ref "D911") (pin "1") (pinfunction "+_1") (pintype "passive"))
      (node (ref "R933") (pin "1") (pinfunction "1_1") (pintype "passive"))
    )
    (net (code "370") (name "Net-(D911--)") (class "Default")
      (node (ref "D911") (pin "2") (pinfunction "-_2") (pintype "passive"))
      (node (ref "IC908") (pin "2") (pinfunction "OUT_2") (pintype "open_collector"))
      (node (ref "JP905") (pin "1") (pinfunction "1_1") (pintype "passive"))
      (node (ref "Q907") (pin "1") (pinfunction "G_1") (pintype "passive"))
      (node (ref "R935") (pin "2") (pinfunction "2_2") (pintype "passive"))
    )
    (net (code "371") (name "Net-(D912-+)") (class "Default")
      (node (ref "D912") (pin "1") (pinfunction "+_1") (pintype "passive"))
      (node (ref "R940") (pin "1") (pinfunction "1_1") (pintype "passive"))
    )
    (net (code "372") (name "Net-(D912--)") (class "Default")
      (node (ref "C909") (pin "2") (pinfunction "2_2") (pintype "passive"))
      (node (ref "D912") (pin "2") (pinfunction "-_2") (pintype "passive"))
      (node (ref "IC906") (pin "6") (pinfunction "D2_6") (pintype "passive"))
      (node (ref "IC910") (pin "2") (pinfunction "TR_2") (pintype "input"))
      (node (ref "IC910") (pin "6") (pinfunction "THR_6") (pintype "input"))
      (node (ref "R941") (pin "1") (pinfunction "1_1") (pintype "passive"))
    )
    (net (code "373") (name "Net-(D1004-PadC)") (class "Default")
      (node (ref "D1004") (pin "C") (pinfunction "C_C") (pintype "passive"))
      (node (ref "R1005") (pin "2") (pinfunction "2_2") (pintype "passive"))
      (node (ref "X1001") (pin "22") (pinfunction "22_22") (pintype "passive"))
    )
    (net (code "374") (name "Net-(D1005--)") (class "Default")
      (node (ref "D1005") (pin "2") (pinfunction "-_2") (pintype "passive"))
      (node (ref "Q1004") (pin "2") (pinfunction "C_2") (pintype "passive"))
      (node (ref "START1001") (pin "TP") (pinfunction "PP_TP") (pintype "input"))
      (node (ref "X1001") (pin "5") (pinfunction "5_5") (pintype "passive"))
    )
    (net (code "375") (name "Net-(D1006-+)") (class "Default")
      (node (ref "D1006") (pin "1") (pinfunction "+_1") (pintype "passive"))
      (node (ref "R1027") (pin "1") (pinfunction "1_1") (pintype "passive"))
    )
    (net (code "376") (name "Net-(D1009-+)") (class "Default")
      (node (ref "D1009") (pin "1") (pinfunction "+_1") (pintype "passive"))
      (node (ref "JP1002") (pin "2") (pinfunction "2_2") (pintype "passive"))
    )
    (net (code "377") (name "Net-(D1010-+)") (class "Default")
      (node (ref "D1010") (pin "1") (pinfunction "+_1") (pintype "passive"))
      (node (ref "JP1003") (pin "1") (pinfunction "1_1") (pintype "passive"))
    )
    (net (code "378") (name "Net-(D1011-+)") (class "Default")
      (node (ref "D1011") (pin "1") (pinfunction "+_1") (pintype "passive"))
      (node (ref "R1033") (pin "1") (pinfunction "1_1") (pintype "passive"))
    )
    (net (code "379") (name "Net-(D1011--)") (class "Default")
      (node (ref "D1011") (pin "2") (pinfunction "-_2") (pintype "passive"))
      (node (ref "IC1008") (pin "2") (pinfunction "OUT_2") (pintype "open_collector"))
      (node (ref "JP1005") (pin "1") (pinfunction "1_1") (pintype "passive"))
      (node (ref "Q1007") (pin "1") (pinfunction "G_1") (pintype "passive"))
      (node (ref "R1035") (pin "2") (pinfunction "2_2") (pintype "passive"))
    )
    (net (code "380") (name "Net-(D1012-+)") (class "Default")
      (node (ref "D1012") (pin "1") (pinfunction "+_1") (pintype "passive"))
      (node (ref "R1040") (pin "1") (pinfunction "1_1") (pintype "passive"))
    )
    (net (code "381") (name "Net-(D1012--)") (class "Default")
      (node (ref "C1009") (pin "2") (pinfunction "2_2") (pintype "passive"))
      (node (ref "D1012") (pin "2") (pinfunction "-_2") (pintype "passive"))
      (node (ref "IC1006") (pin "6") (pinfunction "D2_6") (pintype "passive"))
      (node (ref "IC1010") (pin "2") (pinfunction "TR_2") (pintype "input"))
      (node (ref "IC1010") (pin "6") (pinfunction "THR_6") (pintype "input"))
      (node (ref "R1041") (pin "1") (pinfunction "1_1") (pintype "passive"))
    )
    (net (code "382") (name "Net-(D1104-PadC)") (class "Default")
      (node (ref "D1104") (pin "C") (pinfunction "C_C") (pintype "passive"))
      (node (ref "R1105") (pin "2") (pinfunction "2_2") (pintype "passive"))
      (node (ref "X1101") (pin "22") (pinfunction "22_22") (pintype "passive"))
    )
    (net (code "383") (name "Net-(D1105--)") (class "Default")
      (node (ref "D1105") (pin "2") (pinfunction "-_2") (pintype "passive"))
      (node (ref "Q1104") (pin "2") (pinfunction "C_2") (pintype "passive"))
      (node (ref "START1101") (pin "TP") (pinfunction "PP_TP") (pintype "input"))
      (node (ref "X1101") (pin "5") (pinfunction "5_5") (pintype "passive"))
    )
    (net (code "384") (name "Net-(D1106-+)") (class "Default")
      (node (ref "D1106") (pin "1") (pinfunction "+_1") (pintype "passive"))
      (node (ref "R1127") (pin "1") (pinfunction "1_1") (pintype "passive"))
    )
    (net (code "385") (name "Net-(D1109-+)") (class "Default")
      (node (ref "D1109") (pin "1") (pinfunction "+_1") (pintype "passive"))
      (node (ref "JP1102") (pin "2") (pinfunction "2_2") (pintype "passive"))
    )
    (net (code "386") (name "Net-(D1110-+)") (class "Default")
      (node (ref "D1110") (pin "1") (pinfunction "+_1") (pintype "passive"))
      (node (ref "JP1103") (pin "1") (pinfunction "1_1") (pintype "passive"))
    )
    (net (code "387") (name "Net-(D1111-+)") (class "Default")
      (node (ref "D1111") (pin "1") (pinfunction "+_1") (pintype "passive"))
      (node (ref "R1133") (pin "1") (pinfunction "1_1") (pintype "passive"))
    )
    (net (code "388") (name "Net-(D1111--)") (class "Default")
      (node (ref "D1111") (pin "2") (pinfunction "-_2") (pintype "passive"))
      (node (ref "IC1108") (pin "2") (pinfunction "OUT_2") (pintype "open_collector"))
      (node (ref "JP1105") (pin "1") (pinfunction "1_1") (pintype "passive"))
      (node (ref "Q1107") (pin "1") (pinfunction "G_1") (pintype "passive"))
      (node (ref "R1135") (pin "2") (pinfunction "2_2") (pintype "passive"))
    )
    (net (code "389") (name "Net-(D1112-+)") (class "Default")
      (node (ref "D1112") (pin "1") (pinfunction "+_1") (pintype "passive"))
      (node (ref "R1140") (pin "1") (pinfunction "1_1") (pintype "passive"))
    )
    (net (code "390") (name "Net-(D1112--)") (class "Default")
      (node (ref "C1109") (pin "2") (pinfunction "2_2") (pintype "passive"))
      (node (ref "D1112") (pin "2") (pinfunction "-_2") (pintype "passive"))
      (node (ref "IC1106") (pin "6") (pinfunction "D2_6") (pintype "passive"))
      (node (ref "IC1110") (pin "2") (pinfunction "TR_2") (pintype "input"))
      (node (ref "IC1110") (pin "6") (pinfunction "THR_6") (pintype "input"))
      (node (ref "R1141") (pin "1") (pinfunction "1_1") (pintype "passive"))
    )
    (net (code "391") (name "Net-(D1204-PadC)") (class "Default")
      (node (ref "D1204") (pin "C") (pinfunction "C_C") (pintype "passive"))
      (node (ref "R1205") (pin "2") (pinfunction "2_2") (pintype "passive"))
      (node (ref "X1201") (pin "22") (pinfunction "22_22") (pintype "passive"))
    )
    (net (code "392") (name "Net-(D1205--)") (class "Default")
      (node (ref "D1205") (pin "2") (pinfunction "-_2") (pintype "passive"))
      (node (ref "Q1204") (pin "2") (pinfunction "C_2") (pintype "passive"))
      (node (ref "START1201") (pin "TP") (pinfunction "PP_TP") (pintype "input"))
      (node (ref "X1201") (pin "5") (pinfunction "5_5") (pintype "passive"))
    )
    (net (code "393") (name "Net-(D1206-+)") (class "Default")
      (node (ref "D1206") (pin "1") (pinfunction "+_1") (pintype "passive"))
      (node (ref "R1227") (pin "1") (pinfunction "1_1") (pintype "passive"))
    )
    (net (code "394") (name "Net-(D1209-+)") (class "Default")
      (node (ref "D1209") (pin "1") (pinfunction "+_1") (pintype "passive"))
      (node (ref "JP1202") (pin "2") (pinfunction "2_2") (pintype "passive"))
    )
    (net (code "395") (name "Net-(D1210-+)") (class "Default")
      (node (ref "D1210") (pin "1") (pinfunction "+_1") (pintype "passive"))
      (node (ref "JP1203") (pin "1") (pinfunction "1_1") (pintype "passive"))
    )
    (net (code "396") (name "Net-(D1211-+)") (class "Default")
      (node (ref "D1211") (pin "1") (pinfunction "+_1") (pintype "passive"))
      (node (ref "R1233") (pin "1") (pinfunction "1_1") (pintype "passive"))
    )
    (net (code "397") (name "Net-(D1211--)") (class "Default")
      (node (ref "D1211") (pin "2") (pinfunction "-_2") (pintype "passive"))
      (node (ref "IC1208") (pin "2") (pinfunction "OUT_2") (pintype "open_collector"))
      (node (ref "JP1205") (pin "1") (pinfunction "1_1") (pintype "passive"))
      (node (ref "Q1207") (pin "1") (pinfunction "G_1") (pintype "passive"))
      (node (ref "R1235") (pin "2") (pinfunction "2_2") (pintype "passive"))
    )
    (net (code "398") (name "Net-(D1212-+)") (class "Default")
      (node (ref "D1212") (pin "1") (pinfunction "+_1") (pintype "passive"))
      (node (ref "R1240") (pin "1") (pinfunction "1_1") (pintype "passive"))
    )
    (net (code "399") (name "Net-(D1212--)") (class "Default")
      (node (ref "C1209") (pin "2") (pinfunction "2_2") (pintype "passive"))
      (node (ref "D1212") (pin "2") (pinfunction "-_2") (pintype "passive"))
      (node (ref "IC1206") (pin "6") (pinfunction "D2_6") (pintype "passive"))
      (node (ref "IC1210") (pin "2") (pinfunction "TR_2") (pintype "input"))
      (node (ref "IC1210") (pin "6") (pinfunction "THR_6") (pintype "input"))
      (node (ref "R1241") (pin "1") (pinfunction "1_1") (pintype "passive"))
    )
    (net (code "400") (name "Net-(IC101A-+IN)") (class "Default")
      (node (ref "C101") (pin "1") (pinfunction "1_1") (pintype "passive"))
      (node (ref "IC101") (pin "3") (pinfunction "+IN_3") (pintype "input"))
      (node (ref "R105") (pin "1") (pinfunction "1_1") (pintype "passive"))
    )
    (net (code "401") (name "Net-(IC101A--IN)") (class "Default")
      (node (ref "IC101") (pin "2") (pinfunction "-IN_2") (pintype "input"))
      (node (ref "R107") (pin "2") (pinfunction "2_2") (pintype "passive"))
    )
    (net (code "402") (name "Net-(IC101A-OUT)") (class "Default")
      (node (ref "IC101") (pin "1") (pinfunction "OUT_1") (pintype "output"))
      (node (ref "R108") (pin "2") (pinfunction "2_2") (pintype "passive"))
    )
    (net (code "403") (name "Net-(IC101B-+IN)") (class "Default")
      (node (ref "IC101") (pin "5") (pinfunction "+IN_5") (pintype "input"))
      (node (ref "R112") (pin "2") (pinfunction "2_2") (pintype "passive"))
      (node (ref "R117") (pin "2") (pinfunction "2_2") (pintype "passive"))
    )
    (net (code "404") (name "Net-(IC101B--IN)") (class "Default")
      (node (ref "IC101") (pin "6") (pinfunction "-IN_6") (pintype "input"))
      (node (ref "R113") (pin "1") (pinfunction "1_1") (pintype "passive"))
      (node (ref "R114") (pin "2") (pinfunction "2_2") (pintype "passive"))
    )
    (net (code "405") (name "Net-(IC101B-OUT)") (class "Default")
      (node (ref "IC101") (pin "7") (pinfunction "OUT_7") (pintype "output"))
      (node (ref "R116") (pin "1") (pinfunction "1_1") (pintype "passive"))
      (node (ref "R117") (pin "1") (pinfunction "1_1") (pintype "passive"))
    )
    (net (code "406") (name "Net-(IC105A-A)") (class "Default")
      (node (ref "IC105") (pin "10") (pinfunction "A_10") (pintype "input"))
      (node (ref "IC106") (pin "1") (pinfunction "D1_1") (pintype "passive"))
      (node (ref "R111") (pin "1") (pinfunction "1_1") (pintype "passive"))
      (node (ref "X101") (pin "4") (pinfunction "4_4") (pintype "passive"))
      (node (ref "X103") (pin "2") (pinfunction "S_2") (pintype "passive"))
    )
    (net (code "407") (name "Net-(IC105A-B)") (class "Default")
      (node (ref "IC105") (pin "13") (pinfunction "B_13") (pintype "input"))
      (node (ref "IC106") (pin "4") (pinfunction "D4_4") (pintype "passive"))
      (node (ref "R110") (pin "1") (pinfunction "1_1") (pintype "passive"))
      (node (ref "X101") (pin "3") (pinfunction "3_3") (pintype "passive"))
      (node (ref "X103") (pin "3") (pinfunction "S_3") (pintype "passive"))
    )
    (net (code "408") (name "Net-(IC105A-C)") (class "Default")
      (node (ref "IC105") (pin "12") (pinfunction "C_12") (pintype "input"))
      (node (ref "IC106") (pin "3") (pinfunction "D3_3") (pintype "passive"))
      (node (ref "R109") (pin "1") (pinfunction "1_1") (pintype "passive"))
      (node (ref "X101") (pin "2") (pinfunction "2_2") (pintype "passive"))
      (node (ref "X103") (pin "4") (pinfunction "S_4") (pintype "passive"))
    )
    (net (code "409") (name "Net-(IC105A-Q0)") (class "Default")
      (node (ref "IC105") (pin "3") (pinfunction "Q0_3") (pintype "output"))
      (node (ref "IC107") (pin "1") (pinfunction "I1_1") (pintype "input"))
      (node (ref "IC107") (pin "2") (pinfunction "I2_2") (pintype "input"))
      (node (ref "Q106") (pin "1") (pinfunction "G_1") (pintype "passive"))
    )
    (net (code "410") (name "Net-(IC105A-Q1)") (class "Default")
      (node (ref "IC105") (pin "14") (pinfunction "Q1_14") (pintype "output"))
      (node (ref "IC107") (pin "6") (pinfunction "I6_6") (pintype "input"))
    )
    (net (code "411") (name "Net-(IC105A-Q2)") (class "Default")
      (node (ref "IC105") (pin "2") (pinfunction "Q2_2") (pintype "output"))
      (node (ref "IC107") (pin "7") (pinfunction "I7_7") (pintype "input"))
    )
    (net (code "412") (name "Net-(IC105A-Q3)") (class "Default")
      (node (ref "IC105") (pin "15") (pinfunction "Q3_15") (pintype "output"))
      (node (ref "IC107") (pin "5") (pinfunction "I5_5") (pintype "input"))
    )
    (net (code "413") (name "Net-(IC105A-Q4)") (class "Default")
      (node (ref "IC105") (pin "1") (pinfunction "Q4_1") (pintype "output"))
      (node (ref "IC107") (pin "4") (pinfunction "I4_4") (pintype "input"))
    )
    (net (code "414") (name "Net-(IC105A-Q5)") (class "Default")
      (node (ref "IC105") (pin "6") (pinfunction "Q5_6") (pintype "output"))
      (node (ref "IC107") (pin "3") (pinfunction "I3_3") (pintype "input"))
    )
    (net (code "415") (name "Net-(IC107-O2)") (class "Default")
      (node (ref "IC107") (pin "15") (pinfunction "O2_15") (pintype "open_collector"))
      (node (ref "R128") (pin "1") (pinfunction "1_1") (pintype "passive"))
    )
    (net (code "416") (name "Net-(IC108A-+IN)") (class "Default")
      (node (ref "IC108") (pin "5") (pinfunction "+IN_5") (pintype "input"))
      (node (ref "R131") (pin "1") (pinfunction "1_1") (pintype "passive"))
      (node (ref "R132") (pin "2") (pinfunction "2_2") (pintype "passive"))
      (node (ref "R133") (pin "2") (pinfunction "2_2") (pintype "passive"))
    )
    (net (code "417") (name "Net-(IC108A--IN)") (class "Default")
      (node (ref "C108") (pin "1") (pinfunction "1_1") (pintype "passive"))
      (node (ref "IC108") (pin "4") (pinfunction "-IN_4") (pintype "input"))
      (node (ref "R130") (pin "1") (pinfunction "1_1") (pintype "passive"))
    )
    (net (code "418") (name "Net-(IC108B-+IN)") (class "Default")
      (node (ref "IC108") (pin "7") (pinfunction "+IN_7") (pintype "input"))
      (node (ref "R121") (pin "1") (pinfunction "1_1") (pintype "passive"))
      (node (ref "R122") (pin "1") (pinfunction "1_1") (pintype "passive"))
    )
    (net (code "419") (name "Net-(IC108B--IN)") (class "Default")
      (node (ref "IC108") (pin "6") (pinfunction "-IN_6") (pintype "input"))
      (node (ref "IC108") (pin "8") (pinfunction "-IN_8") (pintype "input"))
      (node (ref "R120") (pin "1") (pinfunction "1_1") (pintype "passive"))
    )
    (net (code "420") (name "Net-(IC108B-OUT)") (class "Default")
      (node (ref "IC108") (pin "1") (pinfunction "OUT_1") (pintype "open_collector"))
      (node (ref "R124") (pin "2") (pinfunction "2_2") (pintype "passive"))
      (node (ref "R125") (pin "2") (pinfunction "2_2") (pintype "passive"))
    )
    (net (code "421") (name "Net-(IC108C-+IN)") (class "Default")
      (node (ref "C105") (pin "1") (pinfunction "1_1") (pintype "passive"))
      (node (ref "IC108") (pin "9") (pinfunction "+IN_9") (pintype "input"))
      (node (ref "R122") (pin "2") (pinfunction "2_2") (pintype "passive"))
      (node (ref "R123") (pin "2") (pinfunction "2_2") (pintype "passive"))
    )
    (net (code "422") (name "Net-(IC108C-OUT)") (class "Default")
      (node (ref "C106") (pin "2") (pinfunction "2_2") (pintype "passive"))
      (node (ref "IC108") (pin "14") (pinfunction "OUT_14") (pintype "open_collector"))
      (node (ref "R126") (pin "2") (pinfunction "2_2") (pintype "passive"))
    )
    (net (code "423") (name "Net-(IC109-ADJ)") (class "Default")
      (node (ref "IC109") (pin "1") (pinfunction "ADJ_1") (pintype "input"))
      (node (ref "R120") (pin "2") (pinfunction "2_2") (pintype "passive"))
      (node (ref "R134") (pin "1") (pinfunction "1_1") (pintype "passive"))
      (node (ref "X101") (pin "7") (pinfunction "7_7") (pintype "passive"))
    )
    (net (code "424") (name "Net-(IC109-VI)") (class "Default")
      (node (ref "IC109") (pin "3") (pinfunction "VI_3") (pintype "input"))
      (node (ref "Q105") (pin "2") (pinfunction "C_2") (pintype "passive"))
    )
    (net (code "425") (name "Net-(IC109-VO)") (class "Default")
      (node (ref "IC109") (pin "2") (pinfunction "VO_2") (pintype "passive"))
      (node (ref "R134") (pin "2") (pinfunction "2_2") (pintype "passive"))
    )
    (net (code "426") (name "Net-(IC110-CV)") (class "Default")
      (node (ref "IC110") (pin "5") (pinfunction "CV_5") (pintype "input"))
      (node (ref "R144") (pin "2") (pinfunction "2_2") (pintype "passive"))
    )
    (net (code "427") (name "Net-(IC110-Q)") (class "Default")
      (node (ref "IC110") (pin "3") (pinfunction "Q_3") (pintype "output"))
      (node (ref "IC111") (pin "12") (pinfunction "A_12") (pintype "input"))
      (node (ref "R144") (pin "1") (pinfunction "1_1") (pintype "passive"))
    )
    (net (code "428") (name "Net-(IC111B-B)") (class "Default")
      (node (ref "IC111") (pin "11") (pinfunction "B_11") (pintype "input"))
      (node (ref "IC111") (pin "9") (pinfunction "~{Q}_9") (pintype "output"))
      (node (ref "R146") (pin "2") (pinfunction "2_2") (pintype "passive"))
    )
    (net (code "429") (name "Net-(IC111B-T2)") (class "Default")
      (node (ref "C110") (pin "1") (pinfunction "1_1") (pintype "passive"))
      (node (ref "IC111") (pin "14") (pinfunction "T2_14") (pintype "input"))
      (node (ref "R145") (pin "1") (pinfunction "1_1") (pintype "passive"))
    )
    (net (code "430") (name "Net-(IC201A-+IN)") (class "Default")
      (node (ref "C201") (pin "1") (pinfunction "1_1") (pintype "passive"))
      (node (ref "IC201") (pin "3") (pinfunction "+IN_3") (pintype "input"))
      (node (ref "R205") (pin "1") (pinfunction "1_1") (pintype "passive"))
    )
    (net (code "431") (name "Net-(IC201A--IN)") (class "Default")
      (node (ref "IC201") (pin "2") (pinfunction "-IN_2") (pintype "input"))
      (node (ref "R207") (pin "2") (pinfunction "2_2") (pintype "passive"))
    )
    (net (code "432") (name "Net-(IC201A-OUT)") (class "Default")
      (node (ref "IC201") (pin "1") (pinfunction "OUT_1") (pintype "output"))
      (node (ref "R208") (pin "2") (pinfunction "2_2") (pintype "passive"))
    )
    (net (code "433") (name "Net-(IC201B-+IN)") (class "Default")
      (node (ref "IC201") (pin "5") (pinfunction "+IN_5") (pintype "input"))
      (node (ref "R212") (pin "2") (pinfunction "2_2") (pintype "passive"))
      (node (ref "R217") (pin "2") (pinfunction "2_2") (pintype "passive"))
    )
    (net (code "434") (name "Net-(IC201B--IN)") (class "Default")
      (node (ref "IC201") (pin "6") (pinfunction "-IN_6") (pintype "input"))
      (node (ref "R213") (pin "1") (pinfunction "1_1") (pintype "passive"))
      (node (ref "R214") (pin "2") (pinfunction "2_2") (pintype "passive"))
    )
    (net (code "435") (name "Net-(IC201B-OUT)") (class "Default")
      (node (ref "IC201") (pin "7") (pinfunction "OUT_7") (pintype "output"))
      (node (ref "R216") (pin "1") (pinfunction "1_1") (pintype "passive"))
      (node (ref "R217") (pin "1") (pinfunction "1_1") (pintype "passive"))
    )
    (net (code "436") (name "Net-(IC205A-A)") (class "Default")
      (node (ref "IC205") (pin "10") (pinfunction "A_10") (pintype "input"))
      (node (ref "IC206") (pin "1") (pinfunction "D1_1") (pintype "passive"))
      (node (ref "R211") (pin "1") (pinfunction "1_1") (pintype "passive"))
      (node (ref "X201") (pin "4") (pinfunction "4_4") (pintype "passive"))
      (node (ref "X203") (pin "2") (pinfunction "S_2") (pintype "passive"))
    )
    (net (code "437") (name "Net-(IC205A-B)") (class "Default")
      (node (ref "IC205") (pin "13") (pinfunction "B_13") (pintype "input"))
      (node (ref "IC206") (pin "4") (pinfunction "D4_4") (pintype "passive"))
      (node (ref "R210") (pin "1") (pinfunction "1_1") (pintype "passive"))
      (node (ref "X201") (pin "3") (pinfunction "3_3") (pintype "passive"))
      (node (ref "X203") (pin "3") (pinfunction "S_3") (pintype "passive"))
    )
    (net (code "438") (name "Net-(IC205A-C)") (class "Default")
      (node (ref "IC205") (pin "12") (pinfunction "C_12") (pintype "input"))
      (node (ref "IC206") (pin "3") (pinfunction "D3_3") (pintype "passive"))
      (node (ref "R209") (pin "1") (pinfunction "1_1") (pintype "passive"))
      (node (ref "X201") (pin "2") (pinfunction "2_2") (pintype "passive"))
      (node (ref "X203") (pin "4") (pinfunction "S_4") (pintype "passive"))
    )
    (net (code "439") (name "Net-(IC205A-Q0)") (class "Default")
      (node (ref "IC205") (pin "3") (pinfunction "Q0_3") (pintype "output"))
      (node (ref "IC207") (pin "1") (pinfunction "I1_1") (pintype "input"))
      (node (ref "IC207") (pin "2") (pinfunction "I2_2") (pintype "input"))
      (node (ref "Q206") (pin "1") (pinfunction "G_1") (pintype "passive"))
    )
    (net (code "440") (name "Net-(IC205A-Q1)") (class "Default")
      (node (ref "IC205") (pin "14") (pinfunction "Q1_14") (pintype "output"))
      (node (ref "IC207") (pin "6") (pinfunction "I6_6") (pintype "input"))
    )
    (net (code "441") (name "Net-(IC205A-Q2)") (class "Default")
      (node (ref "IC205") (pin "2") (pinfunction "Q2_2") (pintype "output"))
      (node (ref "IC207") (pin "7") (pinfunction "I7_7") (pintype "input"))
    )
    (net (code "442") (name "Net-(IC205A-Q3)") (class "Default")
      (node (ref "IC205") (pin "15") (pinfunction "Q3_15") (pintype "output"))
      (node (ref "IC207") (pin "5") (pinfunction "I5_5") (pintype "input"))
    )
    (net (code "443") (name "Net-(IC205A-Q4)") (class "Default")
      (node (ref "IC205") (pin "1") (pinfunction "Q4_1") (pintype "output"))
      (node (ref "IC207") (pin "4") (pinfunction "I4_4") (pintype "input"))
    )
    (net (code "444") (name "Net-(IC205A-Q5)") (class "Default")
      (node (ref "IC205") (pin "6") (pinfunction "Q5_6") (pintype "output"))
      (node (ref "IC207") (pin "3") (pinfunction "I3_3") (pintype "input"))
    )
    (net (code "445") (name "Net-(IC207-O2)") (class "Default")
      (node (ref "IC207") (pin "15") (pinfunction "O2_15") (pintype "open_collector"))
      (node (ref "R228") (pin "1") (pinfunction "1_1") (pintype "passive"))
    )
    (net (code "446") (name "Net-(IC208A-+IN)") (class "Default")
      (node (ref "IC208") (pin "5") (pinfunction "+IN_5") (pintype "input"))
      (node (ref "R231") (pin "1") (pinfunction "1_1") (pintype "passive"))
      (node (ref "R232") (pin "2") (pinfunction "2_2") (pintype "passive"))
      (node (ref "R233") (pin "2") (pinfunction "2_2") (pintype "passive"))
    )
    (net (code "447") (name "Net-(IC208A--IN)") (class "Default")
      (node (ref "C208") (pin "1") (pinfunction "1_1") (pintype "passive"))
      (node (ref "IC208") (pin "4") (pinfunction "-IN_4") (pintype "input"))
      (node (ref "R230") (pin "1") (pinfunction "1_1") (pintype "passive"))
    )
    (net (code "448") (name "Net-(IC208B-+IN)") (class "Default")
      (node (ref "IC208") (pin "7") (pinfunction "+IN_7") (pintype "input"))
      (node (ref "R221") (pin "1") (pinfunction "1_1") (pintype "passive"))
      (node (ref "R222") (pin "1") (pinfunction "1_1") (pintype "passive"))
    )
    (net (code "449") (name "Net-(IC208B--IN)") (class "Default")
      (node (ref "IC208") (pin "6") (pinfunction "-IN_6") (pintype "input"))
      (node (ref "IC208") (pin "8") (pinfunction "-IN_8") (pintype "input"))
      (node (ref "R220") (pin "1") (pinfunction "1_1") (pintype "passive"))
    )
    (net (code "450") (name "Net-(IC208B-OUT)") (class "Default")
      (node (ref "IC208") (pin "1") (pinfunction "OUT_1") (pintype "open_collector"))
      (node (ref "R224") (pin "2") (pinfunction "2_2") (pintype "passive"))
      (node (ref "R225") (pin "2") (pinfunction "2_2") (pintype "passive"))
    )
    (net (code "451") (name "Net-(IC208C-+IN)") (class "Default")
      (node (ref "C205") (pin "1") (pinfunction "1_1") (pintype "passive"))
      (node (ref "IC208") (pin "9") (pinfunction "+IN_9") (pintype "input"))
      (node (ref "R222") (pin "2") (pinfunction "2_2") (pintype "passive"))
      (node (ref "R223") (pin "2") (pinfunction "2_2") (pintype "passive"))
    )
    (net (code "452") (name "Net-(IC208C-OUT)") (class "Default")
      (node (ref "C206") (pin "2") (pinfunction "2_2") (pintype "passive"))
      (node (ref "IC208") (pin "14") (pinfunction "OUT_14") (pintype "open_collector"))
      (node (ref "R226") (pin "2") (pinfunction "2_2") (pintype "passive"))
    )
    (net (code "453") (name "Net-(IC209-ADJ)") (class "Default")
      (node (ref "IC209") (pin "1") (pinfunction "ADJ_1") (pintype "input"))
      (node (ref "R220") (pin "2") (pinfunction "2_2") (pintype "passive"))
      (node (ref "R234") (pin "1") (pinfunction "1_1") (pintype "passive"))
      (node (ref "X201") (pin "7") (pinfunction "7_7") (pintype "passive"))
    )
    (net (code "454") (name "Net-(IC209-VI)") (class "Default")
      (node (ref "IC209") (pin "3") (pinfunction "VI_3") (pintype "input"))
      (node (ref "Q205") (pin "2") (pinfunction "C_2") (pintype "passive"))
    )
    (net (code "455") (name "Net-(IC209-VO)") (class "Default")
      (node (ref "IC209") (pin "2") (pinfunction "VO_2") (pintype "passive"))
      (node (ref "R234") (pin "2") (pinfunction "2_2") (pintype "passive"))
    )
    (net (code "456") (name "Net-(IC210-CV)") (class "Default")
      (node (ref "IC210") (pin "5") (pinfunction "CV_5") (pintype "input"))
      (node (ref "R244") (pin "2") (pinfunction "2_2") (pintype "passive"))
    )
    (net (code "457") (name "Net-(IC210-Q)") (class "Default")
      (node (ref "IC210") (pin "3") (pinfunction "Q_3") (pintype "output"))
      (node (ref "IC211") (pin "12") (pinfunction "A_12") (pintype "input"))
      (node (ref "R244") (pin "1") (pinfunction "1_1") (pintype "passive"))
    )
    (net (code "458") (name "Net-(IC211B-B)") (class "Default")
      (node (ref "IC211") (pin "11") (pinfunction "B_11") (pintype "input"))
      (node (ref "IC211") (pin "9") (pinfunction "~{Q}_9") (pintype "output"))
      (node (ref "R246") (pin "2") (pinfunction "2_2") (pintype "passive"))
    )
    (net (code "459") (name "Net-(IC211B-T2)") (class "Default")
      (node (ref "C210") (pin "1") (pinfunction "1_1") (pintype "passive"))
      (node (ref "IC211") (pin "14") (pinfunction "T2_14") (pintype "input"))
      (node (ref "R245") (pin "1") (pinfunction "1_1") (pintype "passive"))
    )
    (net (code "460") (name "Net-(IC301A-+IN)") (class "Default")
      (node (ref "C301") (pin "1") (pinfunction "1_1") (pintype "passive"))
      (node (ref "IC301") (pin "3") (pinfunction "+IN_3") (pintype "input"))
      (node (ref "R305") (pin "1") (pinfunction "1_1") (pintype "passive"))
    )
    (net (code "461") (name "Net-(IC301A--IN)") (class "Default")
      (node (ref "IC301") (pin "2") (pinfunction "-IN_2") (pintype "input"))
      (node (ref "R307") (pin "2") (pinfunction "2_2") (pintype "passive"))
    )
    (net (code "462") (name "Net-(IC301A-OUT)") (class "Default")
      (node (ref "IC301") (pin "1") (pinfunction "OUT_1") (pintype "output"))
      (node (ref "R308") (pin "2") (pinfunction "2_2") (pintype "passive"))
    )
    (net (code "463") (name "Net-(IC301B-+IN)") (class "Default")
      (node (ref "IC301") (pin "5") (pinfunction "+IN_5") (pintype "input"))
      (node (ref "R312") (pin "2") (pinfunction "2_2") (pintype "passive"))
      (node (ref "R317") (pin "2") (pinfunction "2_2") (pintype "passive"))
    )
    (net (code "464") (name "Net-(IC301B--IN)") (class "Default")
      (node (ref "IC301") (pin "6") (pinfunction "-IN_6") (pintype "input"))
      (node (ref "R313") (pin "1") (pinfunction "1_1") (pintype "passive"))
      (node (ref "R314") (pin "2") (pinfunction "2_2") (pintype "passive"))
    )
    (net (code "465") (name "Net-(IC301B-OUT)") (class "Default")
      (node (ref "IC301") (pin "7") (pinfunction "OUT_7") (pintype "output"))
      (node (ref "R316") (pin "1") (pinfunction "1_1") (pintype "passive"))
      (node (ref "R317") (pin "1") (pinfunction "1_1") (pintype "passive"))
    )
    (net (code "466") (name "Net-(IC305A-A)") (class "Default")
      (node (ref "IC305") (pin "10") (pinfunction "A_10") (pintype "input"))
      (node (ref "IC306") (pin "1") (pinfunction "D1_1") (pintype "passive"))
      (node (ref "R311") (pin "1") (pinfunction "1_1") (pintype "passive"))
      (node (ref "X301") (pin "4") (pinfunction "4_4") (pintype "passive"))
      (node (ref "X303") (pin "2") (pinfunction "S_2") (pintype "passive"))
    )
    (net (code "467") (name "Net-(IC305A-B)") (class "Default")
      (node (ref "IC305") (pin "13") (pinfunction "B_13") (pintype "input"))
      (node (ref "IC306") (pin "4") (pinfunction "D4_4") (pintype "passive"))
      (node (ref "R310") (pin "1") (pinfunction "1_1") (pintype "passive"))
      (node (ref "X301") (pin "3") (pinfunction "3_3") (pintype "passive"))
      (node (ref "X303") (pin "3") (pinfunction "S_3") (pintype "passive"))
    )
    (net (code "468") (name "Net-(IC305A-C)") (class "Default")
      (node (ref "IC305") (pin "12") (pinfunction "C_12") (pintype "input"))
      (node (ref "IC306") (pin "3") (pinfunction "D3_3") (pintype "passive"))
      (node (ref "R309") (pin "1") (pinfunction "1_1") (pintype "passive"))
      (node (ref "X301") (pin "2") (pinfunction "2_2") (pintype "passive"))
      (node (ref "X303") (pin "4") (pinfunction "S_4") (pintype "passive"))
    )
    (net (code "469") (name "Net-(IC305A-Q0)") (class "Default")
      (node (ref "IC305") (pin "3") (pinfunction "Q0_3") (pintype "output"))
      (node (ref "IC307") (pin "1") (pinfunction "I1_1") (pintype "input"))
      (node (ref "IC307") (pin "2") (pinfunction "I2_2") (pintype "input"))
      (node (ref "Q306") (pin "1") (pinfunction "G_1") (pintype "passive"))
    )
    (net (code "470") (name "Net-(IC305A-Q1)") (class "Default")
      (node (ref "IC305") (pin "14") (pinfunction "Q1_14") (pintype "output"))
      (node (ref "IC307") (pin "6") (pinfunction "I6_6") (pintype "input"))
    )
    (net (code "471") (name "Net-(IC305A-Q2)") (class "Default")
      (node (ref "IC305") (pin "2") (pinfunction "Q2_2") (pintype "output"))
      (node (ref "IC307") (pin "7") (pinfunction "I7_7") (pintype "input"))
    )
    (net (code "472") (name "Net-(IC305A-Q3)") (class "Default")
      (node (ref "IC305") (pin "15") (pinfunction "Q3_15") (pintype "output"))
      (node (ref "IC307") (pin "5") (pinfunction "I5_5") (pintype "input"))
    )
    (net (code "473") (name "Net-(IC305A-Q4)") (class "Default")
      (node (ref "IC305") (pin "1") (pinfunction "Q4_1") (pintype "output"))
      (node (ref "IC307") (pin "4") (pinfunction "I4_4") (pintype "input"))
    )
    (net (code "474") (name "Net-(IC305A-Q5)") (class "Default")
      (node (ref "IC305") (pin "6") (pinfunction "Q5_6") (pintype "output"))
      (node (ref "IC307") (pin "3") (pinfunction "I3_3") (pintype "input"))
    )
    (net (code "475") (name "Net-(IC307-O2)") (class "Default")
      (node (ref "IC307") (pin "15") (pinfunction "O2_15") (pintype "open_collector"))
      (node (ref "R328") (pin "1") (pinfunction "1_1") (pintype "passive"))
    )
    (net (code "476") (name "Net-(IC308A-+IN)") (class "Default")
      (node (ref "IC308") (pin "5") (pinfunction "+IN_5") (pintype "input"))
      (node (ref "R331") (pin "1") (pinfunction "1_1") (pintype "passive"))
      (node (ref "R332") (pin "2") (pinfunction "2_2") (pintype "passive"))
      (node (ref "R333") (pin "2") (pinfunction "2_2") (pintype "passive"))
    )
    (net (code "477") (name "Net-(IC308A--IN)") (class "Default")
      (node (ref "C308") (pin "1") (pinfunction "1_1") (pintype "passive"))
      (node (ref "IC308") (pin "4") (pinfunction "-IN_4") (pintype "input"))
      (node (ref "R330") (pin "1") (pinfunction "1_1") (pintype "passive"))
    )
    (net (code "478") (name "Net-(IC308B-+IN)") (class "Default")
      (node (ref "IC308") (pin "7") (pinfunction "+IN_7") (pintype "input"))
      (node (ref "R321") (pin "1") (pinfunction "1_1") (pintype "passive"))
      (node (ref "R322") (pin "1") (pinfunction "1_1") (pintype "passive"))
    )
    (net (code "479") (name "Net-(IC308B--IN)") (class "Default")
      (node (ref "IC308") (pin "6") (pinfunction "-IN_6") (pintype "input"))
      (node (ref "IC308") (pin "8") (pinfunction "-IN_8") (pintype "input"))
      (node (ref "R320") (pin "1") (pinfunction "1_1") (pintype "passive"))
    )
    (net (code "480") (name "Net-(IC308B-OUT)") (class "Default")
      (node (ref "IC308") (pin "1") (pinfunction "OUT_1") (pintype "open_collector"))
      (node (ref "R324") (pin "2") (pinfunction "2_2") (pintype "passive"))
      (node (ref "R325") (pin "2") (pinfunction "2_2") (pintype "passive"))
    )
    (net (code "481") (name "Net-(IC308C-+IN)") (class "Default")
      (node (ref "C305") (pin "1") (pinfunction "1_1") (pintype "passive"))
      (node (ref "IC308") (pin "9") (pinfunction "+IN_9") (pintype "input"))
      (node (ref "R322") (pin "2") (pinfunction "2_2") (pintype "passive"))
      (node (ref "R323") (pin "2") (pinfunction "2_2") (pintype "passive"))
    )
    (net (code "482") (name "Net-(IC308C-OUT)") (class "Default")
      (node (ref "C306") (pin "2") (pinfunction "2_2") (pintype "passive"))
      (node (ref "IC308") (pin "14") (pinfunction "OUT_14") (pintype "open_collector"))
      (node (ref "R326") (pin "2") (pinfunction "2_2") (pintype "passive"))
    )
    (net (code "483") (name "Net-(IC309-ADJ)") (class "Default")
      (node (ref "IC309") (pin "1") (pinfunction "ADJ_1") (pintype "input"))
      (node (ref "R320") (pin "2") (pinfunction "2_2") (pintype "passive"))
      (node (ref "R334") (pin "1") (pinfunction "1_1") (pintype "passive"))
      (node (ref "X301") (pin "7") (pinfunction "7_7") (pintype "passive"))
    )
    (net (code "484") (name "Net-(IC309-VI)") (class "Default")
      (node (ref "IC309") (pin "3") (pinfunction "VI_3") (pintype "input"))
      (node (ref "Q305") (pin "2") (pinfunction "C_2") (pintype "passive"))
    )
    (net (code "485") (name "Net-(IC309-VO)") (class "Default")
      (node (ref "IC309") (pin "2") (pinfunction "VO_2") (pintype "passive"))
      (node (ref "R334") (pin "2") (pinfunction "2_2") (pintype "passive"))
    )
    (net (code "486") (name "Net-(IC310-CV)") (class "Default")
      (node (ref "IC310") (pin "5") (pinfunction "CV_5") (pintype "input"))
      (node (ref "R344") (pin "2") (pinfunction "2_2") (pintype "passive"))
    )
    (net (code "487") (name "Net-(IC310-Q)") (class "Default")
      (node (ref "IC310") (pin "3") (pinfunction "Q_3") (pintype "output"))
      (node (ref "IC311") (pin "12") (pinfunction "A_12") (pintype "input"))
      (node (ref "R344") (pin "1") (pinfunction "1_1") (pintype "passive"))
    )
    (net (code "488") (name "Net-(IC311B-B)") (class "Default")
      (node (ref "IC311") (pin "11") (pinfunction "B_11") (pintype "input"))
      (node (ref "IC311") (pin "9") (pinfunction "~{Q}_9") (pintype "output"))
      (node (ref "R346") (pin "2") (pinfunction "2_2") (pintype "passive"))
    )
    (net (code "489") (name "Net-(IC311B-T2)") (class "Default")
      (node (ref "C310") (pin "1") (pinfunction "1_1") (pintype "passive"))
      (node (ref "IC311") (pin "14") (pinfunction "T2_14") (pintype "input"))
      (node (ref "R345") (pin "1") (pinfunction "1_1") (pintype "passive"))
    )
    (net (code "490") (name "Net-(IC401A-+IN)") (class "Default")
      (node (ref "C401") (pin "1") (pinfunction "1_1") (pintype "passive"))
      (node (ref "IC401") (pin "3") (pinfunction "+IN_3") (pintype "input"))
      (node (ref "R405") (pin "1") (pinfunction "1_1") (pintype "passive"))
    )
    (net (code "491") (name "Net-(IC401A--IN)") (class "Default")
      (node (ref "IC401") (pin "2") (pinfunction "-IN_2") (pintype "input"))
      (node (ref "R407") (pin "2") (pinfunction "2_2") (pintype "passive"))
    )
    (net (code "492") (name "Net-(IC401A-OUT)") (class "Default")
      (node (ref "IC401") (pin "1") (pinfunction "OUT_1") (pintype "output"))
      (node (ref "R408") (pin "2") (pinfunction "2_2") (pintype "passive"))
    )
    (net (code "493") (name "Net-(IC401B-+IN)") (class "Default")
      (node (ref "IC401") (pin "5") (pinfunction "+IN_5") (pintype "input"))
      (node (ref "R412") (pin "2") (pinfunction "2_2") (pintype "passive"))
      (node (ref "R417") (pin "2") (pinfunction "2_2") (pintype "passive"))
    )
    (net (code "494") (name "Net-(IC401B--IN)") (class "Default")
      (node (ref "IC401") (pin "6") (pinfunction "-IN_6") (pintype "input"))
      (node (ref "R413") (pin "1") (pinfunction "1_1") (pintype "passive"))
      (node (ref "R414") (pin "2") (pinfunction "2_2") (pintype "passive"))
    )
    (net (code "495") (name "Net-(IC401B-OUT)") (class "Default")
      (node (ref "IC401") (pin "7") (pinfunction "OUT_7") (pintype "output"))
      (node (ref "R416") (pin "1") (pinfunction "1_1") (pintype "passive"))
      (node (ref "R417") (pin "1") (pinfunction "1_1") (pintype "passive"))
    )
    (net (code "496") (name "Net-(IC405A-A)") (class "Default")
      (node (ref "IC405") (pin "10") (pinfunction "A_10") (pintype "input"))
      (node (ref "IC406") (pin "1") (pinfunction "D1_1") (pintype "passive"))
      (node (ref "R411") (pin "1") (pinfunction "1_1") (pintype "passive"))
      (node (ref "X401") (pin "4") (pinfunction "4_4") (pintype "passive"))
      (node (ref "X403") (pin "2") (pinfunction "S_2") (pintype "passive"))
    )
    (net (code "497") (name "Net-(IC405A-B)") (class "Default")
      (node (ref "IC405") (pin "13") (pinfunction "B_13") (pintype "input"))
      (node (ref "IC406") (pin "4") (pinfunction "D4_4") (pintype "passive"))
      (node (ref "R410") (pin "1") (pinfunction "1_1") (pintype "passive"))
      (node (ref "X401") (pin "3") (pinfunction "3_3") (pintype "passive"))
      (node (ref "X403") (pin "3") (pinfunction "S_3") (pintype "passive"))
    )
    (net (code "498") (name "Net-(IC405A-C)") (class "Default")
      (node (ref "IC405") (pin "12") (pinfunction "C_12") (pintype "input"))
      (node (ref "IC406") (pin "3") (pinfunction "D3_3") (pintype "passive"))
      (node (ref "R409") (pin "1") (pinfunction "1_1") (pintype "passive"))
      (node (ref "X401") (pin "2") (pinfunction "2_2") (pintype "passive"))
      (node (ref "X403") (pin "4") (pinfunction "S_4") (pintype "passive"))
    )
    (net (code "499") (name "Net-(IC405A-Q0)") (class "Default")
      (node (ref "IC405") (pin "3") (pinfunction "Q0_3") (pintype "output"))
      (node (ref "IC407") (pin "1") (pinfunction "I1_1") (pintype "input"))
      (node (ref "IC407") (pin "2") (pinfunction "I2_2") (pintype "input"))
      (node (ref "Q406") (pin "1") (pinfunction "G_1") (pintype "passive"))
    )
    (net (code "500") (name "Net-(IC405A-Q1)") (class "Default")
      (node (ref "IC405") (pin "14") (pinfunction "Q1_14") (pintype "output"))
      (node (ref "IC407") (pin "6") (pinfunction "I6_6") (pintype "input"))
    )
    (net (code "501") (name "Net-(IC405A-Q2)") (class "Default")
      (node (ref "IC405") (pin "2") (pinfunction "Q2_2") (pintype "output"))
      (node (ref "IC407") (pin "7") (pinfunction "I7_7") (pintype "input"))
    )
    (net (code "502") (name "Net-(IC405A-Q3)") (class "Default")
      (node (ref "IC405") (pin "15") (pinfunction "Q3_15") (pintype "output"))
      (node (ref "IC407") (pin "5") (pinfunction "I5_5") (pintype "input"))
    )
    (net (code "503") (name "Net-(IC405A-Q4)") (class "Default")
      (node (ref "IC405") (pin "1") (pinfunction "Q4_1") (pintype "output"))
      (node (ref "IC407") (pin "4") (pinfunction "I4_4") (pintype "input"))
    )
    (net (code "504") (name "Net-(IC405A-Q5)") (class "Default")
      (node (ref "IC405") (pin "6") (pinfunction "Q5_6") (pintype "output"))
      (node (ref "IC407") (pin "3") (pinfunction "I3_3") (pintype "input"))
    )
    (net (code "505") (name "Net-(IC407-O2)") (class "Default")
      (node (ref "IC407") (pin "15") (pinfunction "O2_15") (pintype "open_collector"))
      (node (ref "R428") (pin "1") (pinfunction "1_1") (pintype "passive"))
    )
    (net (code "506") (name "Net-(IC408A-+IN)") (class "Default")
      (node (ref "IC408") (pin "5") (pinfunction "+IN_5") (pintype "input"))
      (node (ref "R431") (pin "1") (pinfunction "1_1") (pintype "passive"))
      (node (ref "R432") (pin "2") (pinfunction "2_2") (pintype "passive"))
      (node (ref "R433") (pin "2") (pinfunction "2_2") (pintype "passive"))
    )
    (net (code "507") (name "Net-(IC408A--IN)") (class "Default")
      (node (ref "C408") (pin "1") (pinfunction "1_1") (pintype "passive"))
      (node (ref "IC408") (pin "4") (pinfunction "-IN_4") (pintype "input"))
      (node (ref "R430") (pin "1") (pinfunction "1_1") (pintype "passive"))
    )
    (net (code "508") (name "Net-(IC408B-+IN)") (class "Default")
      (node (ref "IC408") (pin "7") (pinfunction "+IN_7") (pintype "input"))
      (node (ref "R421") (pin "1") (pinfunction "1_1") (pintype "passive"))
      (node (ref "R422") (pin "1") (pinfunction "1_1") (pintype "passive"))
    )
    (net (code "509") (name "Net-(IC408B--IN)") (class "Default")
      (node (ref "IC408") (pin "6") (pinfunction "-IN_6") (pintype "input"))
      (node (ref "IC408") (pin "8") (pinfunction "-IN_8") (pintype "input"))
      (node (ref "R420") (pin "1") (pinfunction "1_1") (pintype "passive"))
    )
    (net (code "510") (name "Net-(IC408B-OUT)") (class "Default")
      (node (ref "IC408") (pin "1") (pinfunction "OUT_1") (pintype "open_collector"))
      (node (ref "R424") (pin "2") (pinfunction "2_2") (pintype "passive"))
      (node (ref "R425") (pin "2") (pinfunction "2_2") (pintype "passive"))
    )
    (net (code "511") (name "Net-(IC408C-+IN)") (class "Default")
      (node (ref "C405") (pin "1") (pinfunction "1_1") (pintype "passive"))
      (node (ref "IC408") (pin "9") (pinfunction "+IN_9") (pintype "input"))
      (node (ref "R422") (pin "2") (pinfunction "2_2") (pintype "passive"))
      (node (ref "R423") (pin "2") (pinfunction "2_2") (pintype "passive"))
    )
    (net (code "512") (name "Net-(IC408C-OUT)") (class "Default")
      (node (ref "C406") (pin "2") (pinfunction "2_2") (pintype "passive"))
      (node (ref "IC408") (pin "14") (pinfunction "OUT_14") (pintype "open_collector"))
      (node (ref "R426") (pin "2") (pinfunction "2_2") (pintype "passive"))
    )
    (net (code "513") (name "Net-(IC409-ADJ)") (class "Default")
      (node (ref "IC409") (pin "1") (pinfunction "ADJ_1") (pintype "input"))
      (node (ref "R420") (pin "2") (pinfunction "2_2") (pintype "passive"))
      (node (ref "R434") (pin "1") (pinfunction "1_1") (pintype "passive"))
      (node (ref "X401") (pin "7") (pinfunction "7_7") (pintype "passive"))
    )
    (net (code "514") (name "Net-(IC409-VI)") (class "Default")
      (node (ref "IC409") (pin "3") (pinfunction "VI_3") (pintype "input"))
      (node (ref "Q405") (pin "2") (pinfunction "C_2") (pintype "passive"))
    )
    (net (code "515") (name "Net-(IC409-VO)") (class "Default")
      (node (ref "IC409") (pin "2") (pinfunction "VO_2") (pintype "passive"))
      (node (ref "R434") (pin "2") (pinfunction "2_2") (pintype "passive"))
    )
    (net (code "516") (name "Net-(IC410-CV)") (class "Default")
      (node (ref "IC410") (pin "5") (pinfunction "CV_5") (pintype "input"))
      (node (ref "R444") (pin "2") (pinfunction "2_2") (pintype "passive"))
    )
    (net (code "517") (name "Net-(IC410-Q)") (class "Default")
      (node (ref "IC410") (pin "3") (pinfunction "Q_3") (pintype "output"))
      (node (ref "IC411") (pin "12") (pinfunction "A_12") (pintype "input"))
      (node (ref "R444") (pin "1") (pinfunction "1_1") (pintype "passive"))
    )
    (net (code "518") (name "Net-(IC411B-B)") (class "Default")
      (node (ref "IC411") (pin "11") (pinfunction "B_11") (pintype "input"))
      (node (ref "IC411") (pin "9") (pinfunction "~{Q}_9") (pintype "output"))
      (node (ref "R446") (pin "2") (pinfunction "2_2") (pintype "passive"))
    )
    (net (code "519") (name "Net-(IC411B-T2)") (class "Default")
      (node (ref "C410") (pin "1") (pinfunction "1_1") (pintype "passive"))
      (node (ref "IC411") (pin "14") (pinfunction "T2_14") (pintype "input"))
      (node (ref "R445") (pin "1") (pinfunction "1_1") (pintype "passive"))
    )
    (net (code "520") (name "Net-(IC501A-+IN)") (class "Default")
      (node (ref "C501") (pin "1") (pinfunction "1_1") (pintype "passive"))
      (node (ref "IC501") (pin "3") (pinfunction "+IN_3") (pintype "input"))
      (node (ref "R505") (pin "1") (pinfunction "1_1") (pintype "passive"))
    )
    (net (code "521") (name "Net-(IC501A--IN)") (class "Default")
      (node (ref "IC501") (pin "2") (pinfunction "-IN_2") (pintype "input"))
      (node (ref "R507") (pin "2") (pinfunction "2_2") (pintype "passive"))
    )
    (net (code "522") (name "Net-(IC501A-OUT)") (class "Default")
      (node (ref "IC501") (pin "1") (pinfunction "OUT_1") (pintype "output"))
      (node (ref "R508") (pin "2") (pinfunction "2_2") (pintype "passive"))
    )
    (net (code "523") (name "Net-(IC501B-+IN)") (class "Default")
      (node (ref "IC501") (pin "5") (pinfunction "+IN_5") (pintype "input"))
      (node (ref "R512") (pin "2") (pinfunction "2_2") (pintype "passive"))
      (node (ref "R517") (pin "2") (pinfunction "2_2") (pintype "passive"))
    )
    (net (code "524") (name "Net-(IC501B--IN)") (class "Default")
      (node (ref "IC501") (pin "6") (pinfunction "-IN_6") (pintype "input"))
      (node (ref "R513") (pin "1") (pinfunction "1_1") (pintype "passive"))
      (node (ref "R514") (pin "2") (pinfunction "2_2") (pintype "passive"))
    )
    (net (code "525") (name "Net-(IC501B-OUT)") (class "Default")
      (node (ref "IC501") (pin "7") (pinfunction "OUT_7") (pintype "output"))
      (node (ref "R516") (pin "1") (pinfunction "1_1") (pintype "passive"))
      (node (ref "R517") (pin "1") (pinfunction "1_1") (pintype "passive"))
    )
    (net (code "526") (name "Net-(IC505A-A)") (class "Default")
      (node (ref "IC505") (pin "10") (pinfunction "A_10") (pintype "input"))
      (node (ref "IC506") (pin "1") (pinfunction "D1_1") (pintype "passive"))
      (node (ref "R511") (pin "1") (pinfunction "1_1") (pintype "passive"))
      (node (ref "X501") (pin "4") (pinfunction "4_4") (pintype "passive"))
      (node (ref "X503") (pin "2") (pinfunction "S_2") (pintype "passive"))
    )
    (net (code "527") (name "Net-(IC505A-B)") (class "Default")
      (node (ref "IC505") (pin "13") (pinfunction "B_13") (pintype "input"))
      (node (ref "IC506") (pin "4") (pinfunction "D4_4") (pintype "passive"))
      (node (ref "R510") (pin "1") (pinfunction "1_1") (pintype "passive"))
      (node (ref "X501") (pin "3") (pinfunction "3_3") (pintype "passive"))
      (node (ref "X503") (pin "3") (pinfunction "S_3") (pintype "passive"))
    )
    (net (code "528") (name "Net-(IC505A-C)") (class "Default")
      (node (ref "IC505") (pin "12") (pinfunction "C_12") (pintype "input"))
      (node (ref "IC506") (pin "3") (pinfunction "D3_3") (pintype "passive"))
      (node (ref "R509") (pin "1") (pinfunction "1_1") (pintype "passive"))
      (node (ref "X501") (pin "2") (pinfunction "2_2") (pintype "passive"))
      (node (ref "X503") (pin "4") (pinfunction "S_4") (pintype "passive"))
    )
    (net (code "529") (name "Net-(IC505A-Q0)") (class "Default")
      (node (ref "IC505") (pin "3") (pinfunction "Q0_3") (pintype "output"))
      (node (ref "IC507") (pin "1") (pinfunction "I1_1") (pintype "input"))
      (node (ref "IC507") (pin "2") (pinfunction "I2_2") (pintype "input"))
      (node (ref "Q506") (pin "1") (pinfunction "G_1") (pintype "passive"))
    )
    (net (code "530") (name "Net-(IC505A-Q1)") (class "Default")
      (node (ref "IC505") (pin "14") (pinfunction "Q1_14") (pintype "output"))
      (node (ref "IC507") (pin "6") (pinfunction "I6_6") (pintype "input"))
    )
    (net (code "531") (name "Net-(IC505A-Q2)") (class "Default")
      (node (ref "IC505") (pin "2") (pinfunction "Q2_2") (pintype "output"))
      (node (ref "IC507") (pin "7") (pinfunction "I7_7") (pintype "input"))
    )
    (net (code "532") (name "Net-(IC505A-Q3)") (class "Default")
      (node (ref "IC505") (pin "15") (pinfunction "Q3_15") (pintype "output"))
      (node (ref "IC507") (pin "5") (pinfunction "I5_5") (pintype "input"))
    )
    (net (code "533") (name "Net-(IC505A-Q4)") (class "Default")
      (node (ref "IC505") (pin "1") (pinfunction "Q4_1") (pintype "output"))
      (node (ref "IC507") (pin "4") (pinfunction "I4_4") (pintype "input"))
    )
    (net (code "534") (name "Net-(IC505A-Q5)") (class "Default")
      (node (ref "IC505") (pin "6") (pinfunction "Q5_6") (pintype "output"))
      (node (ref "IC507") (pin "3") (pinfunction "I3_3") (pintype "input"))
    )
    (net (code "535") (name "Net-(IC507-O2)") (class "Default")
      (node (ref "IC507") (pin "15") (pinfunction "O2_15") (pintype "open_collector"))
      (node (ref "R528") (pin "1") (pinfunction "1_1") (pintype "passive"))
    )
    (net (code "536") (name "Net-(IC508A-+IN)") (class "Default")
      (node (ref "IC508") (pin "5") (pinfunction "+IN_5") (pintype "input"))
      (node (ref "R531") (pin "1") (pinfunction "1_1") (pintype "passive"))
      (node (ref "R532") (pin "2") (pinfunction "2_2") (pintype "passive"))
      (node (ref "R533") (pin "2") (pinfunction "2_2") (pintype "passive"))
    )
    (net (code "537") (name "Net-(IC508A--IN)") (class "Default")
      (node (ref "C508") (pin "1") (pinfunction "1_1") (pintype "passive"))
      (node (ref "IC508") (pin "4") (pinfunction "-IN_4") (pintype "input"))
      (node (ref "R530") (pin "1") (pinfunction "1_1") (pintype "passive"))
    )
    (net (code "538") (name "Net-(IC508B-+IN)") (class "Default")
      (node (ref "IC508") (pin "7") (pinfunction "+IN_7") (pintype "input"))
      (node (ref "R521") (pin "1") (pinfunction "1_1") (pintype "passive"))
      (node (ref "R522") (pin "1") (pinfunction "1_1") (pintype "passive"))
    )
    (net (code "539") (name "Net-(IC508B--IN)") (class "Default")
      (node (ref "IC508") (pin "6") (pinfunction "-IN_6") (pintype "input"))
      (node (ref "IC508") (pin "8") (pinfunction "-IN_8") (pintype "input"))
      (node (ref "R520") (pin "1") (pinfunction "1_1") (pintype "passive"))
    )
    (net (code "540") (name "Net-(IC508B-OUT)") (class "Default")
      (node (ref "IC508") (pin "1") (pinfunction "OUT_1") (pintype "open_collector"))
      (node (ref "R524") (pin "2") (pinfunction "2_2") (pintype "passive"))
      (node (ref "R525") (pin "2") (pinfunction "2_2") (pintype "passive"))
    )
    (net (code "541") (name "Net-(IC508C-+IN)") (class "Default")
      (node (ref "C505") (pin "1") (pinfunction "1_1") (pintype "passive"))
      (node (ref "IC508") (pin "9") (pinfunction "+IN_9") (pintype "input"))
      (node (ref "R522") (pin "2") (pinfunction "2_2") (pintype "passive"))
      (node (ref "R523") (pin "2") (pinfunction "2_2") (pintype "passive"))
    )
    (net (code "542") (name "Net-(IC508C-OUT)") (class "Default")
      (node (ref "C506") (pin "2") (pinfunction "2_2") (pintype "passive"))
      (node (ref "IC508") (pin "14") (pinfunction "OUT_14") (pintype "open_collector"))
      (node (ref "R526") (pin "2") (pinfunction "2_2") (pintype "passive"))
    )
    (net (code "543") (name "Net-(IC509-ADJ)") (class "Default")
      (node (ref "IC509") (pin "1") (pinfunction "ADJ_1") (pintype "input"))
      (node (ref "R520") (pin "2") (pinfunction "2_2") (pintype "passive"))
      (node (ref "R534") (pin "1") (pinfunction "1_1") (pintype "passive"))
      (node (ref "X501") (pin "7") (pinfunction "7_7") (pintype "passive"))
    )
    (net (code "544") (name "Net-(IC509-VI)") (class "Default")
      (node (ref "IC509") (pin "3") (pinfunction "VI_3") (pintype "input"))
      (node (ref "Q505") (pin "2") (pinfunction "C_2") (pintype "passive"))
    )
    (net (code "545") (name "Net-(IC509-VO)") (class "Default")
      (node (ref "IC509") (pin "2") (pinfunction "VO_2") (pintype "passive"))
      (node (ref "R534") (pin "2") (pinfunction "2_2") (pintype "passive"))
    )
    (net (code "546") (name "Net-(IC510-CV)") (class "Default")
      (node (ref "IC510") (pin "5") (pinfunction "CV_5") (pintype "input"))
      (node (ref "R544") (pin "2") (pinfunction "2_2") (pintype "passive"))
    )
    (net (code "547") (name "Net-(IC510-Q)") (class "Default")
      (node (ref "IC510") (pin "3") (pinfunction "Q_3") (pintype "output"))
      (node (ref "IC511") (pin "12") (pinfunction "A_12") (pintype "input"))
      (node (ref "R544") (pin "1") (pinfunction "1_1") (pintype "passive"))
    )
    (net (code "548") (name "Net-(IC511B-B)") (class "Default")
      (node (ref "IC511") (pin "11") (pinfunction "B_11") (pintype "input"))
      (node (ref "IC511") (pin "9") (pinfunction "~{Q}_9") (pintype "output"))
      (node (ref "R546") (pin "2") (pinfunction "2_2") (pintype "passive"))
    )
    (net (code "549") (name "Net-(IC511B-T2)") (class "Default")
      (node (ref "C510") (pin "1") (pinfunction "1_1") (pintype "passive"))
      (node (ref "IC511") (pin "14") (pinfunction "T2_14") (pintype "input"))
      (node (ref "R545") (pin "1") (pinfunction "1_1") (pintype "passive"))
    )
    (net (code "550") (name "Net-(IC601A-+IN)") (class "Default")
      (node (ref "C601") (pin "1") (pinfunction "1_1") (pintype "passive"))
      (node (ref "IC601") (pin "3") (pinfunction "+IN_3") (pintype "input"))
      (node (ref "R605") (pin "1") (pinfunction "1_1") (pintype "passive"))
    )
    (net (code "551") (name "Net-(IC601A--IN)") (class "Default")
      (node (ref "IC601") (pin "2") (pinfunction "-IN_2") (pintype "input"))
      (node (ref "R607") (pin "2") (pinfunction "2_2") (pintype "passive"))
    )
    (net (code "552") (name "Net-(IC601A-OUT)") (class "Default")
      (node (ref "IC601") (pin "1") (pinfunction "OUT_1") (pintype "output"))
      (node (ref "R608") (pin "2") (pinfunction "2_2") (pintype "passive"))
    )
    (net (code "553") (name "Net-(IC601B-+IN)") (class "Default")
      (node (ref "IC601") (pin "5") (pinfunction "+IN_5") (pintype "input"))
      (node (ref "R612") (pin "2") (pinfunction "2_2") (pintype "passive"))
      (node (ref "R617") (pin "2") (pinfunction "2_2") (pintype "passive"))
    )
    (net (code "554") (name "Net-(IC601B--IN)") (class "Default")
      (node (ref "IC601") (pin "6") (pinfunction "-IN_6") (pintype "input"))
      (node (ref "R613") (pin "1") (pinfunction "1_1") (pintype "passive"))
      (node (ref "R614") (pin "2") (pinfunction "2_2") (pintype "passive"))
    )
    (net (code "555") (name "Net-(IC601B-OUT)") (class "Default")
      (node (ref "IC601") (pin "7") (pinfunction "OUT_7") (pintype "output"))
      (node (ref "R616") (pin "1") (pinfunction "1_1") (pintype "passive"))
      (node (ref "R617") (pin "1") (pinfunction "1_1") (pintype "passive"))
    )
    (net (code "556") (name "Net-(IC605A-A)") (class "Default")
      (node (ref "IC605") (pin "10") (pinfunction "A_10") (pintype "input"))
      (node (ref "IC606") (pin "1") (pinfunction "D1_1") (pintype "passive"))
      (node (ref "R611") (pin "1") (pinfunction "1_1") (pintype "passive"))
      (node (ref "X601") (pin "4") (pinfunction "4_4") (pintype "passive"))
      (node (ref "X603") (pin "2") (pinfunction "S_2") (pintype "passive"))
    )
    (net (code "557") (name "Net-(IC605A-B)") (class "Default")
      (node (ref "IC605") (pin "13") (pinfunction "B_13") (pintype "input"))
      (node (ref "IC606") (pin "4") (pinfunction "D4_4") (pintype "passive"))
      (node (ref "R610") (pin "1") (pinfunction "1_1") (pintype "passive"))
      (node (ref "X601") (pin "3") (pinfunction "3_3") (pintype "passive"))
      (node (ref "X603") (pin "3") (pinfunction "S_3") (pintype "passive"))
    )
    (net (code "558") (name "Net-(IC605A-C)") (class "Default")
      (node (ref "IC605") (pin "12") (pinfunction "C_12") (pintype "input"))
      (node (ref "IC606") (pin "3") (pinfunction "D3_3") (pintype "passive"))
      (node (ref "R609") (pin "1") (pinfunction "1_1") (pintype "passive"))
      (node (ref "X601") (pin "2") (pinfunction "2_2") (pintype "passive"))
      (node (ref "X603") (pin "4") (pinfunction "S_4") (pintype "passive"))
    )
    (net (code "559") (name "Net-(IC605A-Q0)") (class "Default")
      (node (ref "IC605") (pin "3") (pinfunction "Q0_3") (pintype "output"))
      (node (ref "IC607") (pin "1") (pinfunction "I1_1") (pintype "input"))
      (node (ref "IC607") (pin "2") (pinfunction "I2_2") (pintype "input"))
      (node (ref "Q606") (pin "1") (pinfunction "G_1") (pintype "passive"))
    )
    (net (code "560") (name "Net-(IC605A-Q1)") (class "Default")
      (node (ref "IC605") (pin "14") (pinfunction "Q1_14") (pintype "output"))
      (node (ref "IC607") (pin "6") (pinfunction "I6_6") (pintype "input"))
    )
    (net (code "561") (name "Net-(IC605A-Q2)") (class "Default")
      (node (ref "IC605") (pin "2") (pinfunction "Q2_2") (pintype "output"))
      (node (ref "IC607") (pin "7") (pinfunction "I7_7") (pintype "input"))
    )
    (net (code "562") (name "Net-(IC605A-Q3)") (class "Default")
      (node (ref "IC605") (pin "15") (pinfunction "Q3_15") (pintype "output"))
      (node (ref "IC607") (pin "5") (pinfunction "I5_5") (pintype "input"))
    )
    (net (code "563") (name "Net-(IC605A-Q4)") (class "Default")
      (node (ref "IC605") (pin "1") (pinfunction "Q4_1") (pintype "output"))
      (node (ref "IC607") (pin "4") (pinfunction "I4_4") (pintype "input"))
    )
    (net (code "564") (name "Net-(IC605A-Q5)") (class "Default")
      (node (ref "IC605") (pin "6") (pinfunction "Q5_6") (pintype "output"))
      (node (ref "IC607") (pin "3") (pinfunction "I3_3") (pintype "input"))
    )
    (net (code "565") (name "Net-(IC607-O2)") (class "Default")
      (node (ref "IC607") (pin "15") (pinfunction "O2_15") (pintype "open_collector"))
      (node (ref "R628") (pin "1") (pinfunction "1_1") (pintype "passive"))
    )
    (net (code "566") (name "Net-(IC608A-+IN)") (class "Default")
      (node (ref "IC608") (pin "5") (pinfunction "+IN_5") (pintype "input"))
      (node (ref "R631") (pin "1") (pinfunction "1_1") (pintype "passive"))
      (node (ref "R632") (pin "2") (pinfunction "2_2") (pintype "passive"))
      (node (ref "R633") (pin "2") (pinfunction "2_2") (pintype "passive"))
    )
    (net (code "567") (name "Net-(IC608A--IN)") (class "Default")
      (node (ref "C608") (pin "1") (pinfunction "1_1") (pintype "passive"))
      (node (ref "IC608") (pin "4") (pinfunction "-IN_4") (pintype "input"))
      (node (ref "R630") (pin "1") (pinfunction "1_1") (pintype "passive"))
    )
    (net (code "568") (name "Net-(IC608B-+IN)") (class "Default")
      (node (ref "IC608") (pin "7") (pinfunction "+IN_7") (pintype "input"))
      (node (ref "R621") (pin "1") (pinfunction "1_1") (pintype "passive"))
      (node (ref "R622") (pin "1") (pinfunction "1_1") (pintype "passive"))
    )
    (net (code "569") (name "Net-(IC608B--IN)") (class "Default")
      (node (ref "IC608") (pin "6") (pinfunction "-IN_6") (pintype "input"))
      (node (ref "IC608") (pin "8") (pinfunction "-IN_8") (pintype "input"))
      (node (ref "R620") (pin "1") (pinfunction "1_1") (pintype "passive"))
    )
    (net (code "570") (name "Net-(IC608B-OUT)") (class "Default")
      (node (ref "IC608") (pin "1") (pinfunction "OUT_1") (pintype "open_collector"))
      (node (ref "R624") (pin "2") (pinfunction "2_2") (pintype "passive"))
      (node (ref "R625") (pin "2") (pinfunction "2_2") (pintype "passive"))
    )
    (net (code "571") (name "Net-(IC608C-+IN)") (class "Default")
      (node (ref "C605") (pin "1") (pinfunction "1_1") (pintype "passive"))
      (node (ref "IC608") (pin "9") (pinfunction "+IN_9") (pintype "input"))
      (node (ref "R622") (pin "2") (pinfunction "2_2") (pintype "passive"))
      (node (ref "R623") (pin "2") (pinfunction "2_2") (pintype "passive"))
    )
    (net (code "572") (name "Net-(IC608C-OUT)") (class "Default")
      (node (ref "C606") (pin "2") (pinfunction "2_2") (pintype "passive"))
      (node (ref "IC608") (pin "14") (pinfunction "OUT_14") (pintype "open_collector"))
      (node (ref "R626") (pin "2") (pinfunction "2_2") (pintype "passive"))
    )
    (net (code "573") (name "Net-(IC609-ADJ)") (class "Default")
      (node (ref "IC609") (pin "1") (pinfunction "ADJ_1") (pintype "input"))
      (node (ref "R620") (pin "2") (pinfunction "2_2") (pintype "passive"))
      (node (ref "R634") (pin "1") (pinfunction "1_1") (pintype "passive"))
      (node (ref "X601") (pin "7") (pinfunction "7_7") (pintype "passive"))
    )
    (net (code "574") (name "Net-(IC609-VI)") (class "Default")
      (node (ref "IC609") (pin "3") (pinfunction "VI_3") (pintype "input"))
      (node (ref "Q605") (pin "2") (pinfunction "C_2") (pintype "passive"))
    )
    (net (code "575") (name "Net-(IC609-VO)") (class "Default")
      (node (ref "IC609") (pin "2") (pinfunction "VO_2") (pintype "passive"))
      (node (ref "R634") (pin "2") (pinfunction "2_2") (pintype "passive"))
    )
    (net (code "576") (name "Net-(IC610-CV)") (class "Default")
      (node (ref "IC610") (pin "5") (pinfunction "CV_5") (pintype "input"))
      (node (ref "R644") (pin "2") (pinfunction "2_2") (pintype "passive"))
    )
    (net (code "577") (name "Net-(IC610-Q)") (class "Default")
      (node (ref "IC610") (pin "3") (pinfunction "Q_3") (pintype "output"))
      (node (ref "IC611") (pin "12") (pinfunction "A_12") (pintype "input"))
      (node (ref "R644") (pin "1") (pinfunction "1_1") (pintype "passive"))
    )
    (net (code "578") (name "Net-(IC611B-B)") (class "Default")
      (node (ref "IC611") (pin "11") (pinfunction "B_11") (pintype "input"))
      (node (ref "IC611") (pin "9") (pinfunction "~{Q}_9") (pintype "output"))
      (node (ref "R646") (pin "2") (pinfunction "2_2") (pintype "passive"))
    )
    (net (code "579") (name "Net-(IC611B-T2)") (class "Default")
      (node (ref "C610") (pin "1") (pinfunction "1_1") (pintype "passive"))
      (node (ref "IC611") (pin "14") (pinfunction "T2_14") (pintype "input"))
      (node (ref "R645") (pin "1") (pinfunction "1_1") (pintype "passive"))
    )
    (net (code "580") (name "Net-(IC701A-+IN)") (class "Default")
      (node (ref "C701") (pin "1") (pinfunction "1_1") (pintype "passive"))
      (node (ref "IC701") (pin "3") (pinfunction "+IN_3") (pintype "input"))
      (node (ref "R705") (pin "1") (pinfunction "1_1") (pintype "passive"))
    )
    (net (code "581") (name "Net-(IC701A--IN)") (class "Default")
      (node (ref "IC701") (pin "2") (pinfunction "-IN_2") (pintype "input"))
      (node (ref "R707") (pin "2") (pinfunction "2_2") (pintype "passive"))
    )
    (net (code "582") (name "Net-(IC701A-OUT)") (class "Default")
      (node (ref "IC701") (pin "1") (pinfunction "OUT_1") (pintype "output"))
      (node (ref "R708") (pin "2") (pinfunction "2_2") (pintype "passive"))
    )
    (net (code "583") (name "Net-(IC701B-+IN)") (class "Default")
      (node (ref "IC701") (pin "5") (pinfunction "+IN_5") (pintype "input"))
      (node (ref "R712") (pin "2") (pinfunction "2_2") (pintype "passive"))
      (node (ref "R717") (pin "2") (pinfunction "2_2") (pintype "passive"))
    )
    (net (code "584") (name "Net-(IC701B--IN)") (class "Default")
      (node (ref "IC701") (pin "6") (pinfunction "-IN_6") (pintype "input"))
      (node (ref "R713") (pin "1") (pinfunction "1_1") (pintype "passive"))
      (node (ref "R714") (pin "2") (pinfunction "2_2") (pintype "passive"))
    )
    (net (code "585") (name "Net-(IC701B-OUT)") (class "Default")
      (node (ref "IC701") (pin "7") (pinfunction "OUT_7") (pintype "output"))
      (node (ref "R716") (pin "1") (pinfunction "1_1") (pintype "passive"))
      (node (ref "R717") (pin "1") (pinfunction "1_1") (pintype "passive"))
    )
    (net (code "586") (name "Net-(IC705A-A)") (class "Default")
      (node (ref "IC705") (pin "10") (pinfunction "A_10") (pintype "input"))
      (node (ref "IC706") (pin "1") (pinfunction "D1_1") (pintype "passive"))
      (node (ref "R711") (pin "1") (pinfunction "1_1") (pintype "passive"))
      (node (ref "X701") (pin "4") (pinfunction "4_4") (pintype "passive"))
      (node (ref "X703") (pin "2") (pinfunction "S_2") (pintype "passive"))
    )
    (net (code "587") (name "Net-(IC705A-B)") (class "Default")
      (node (ref "IC705") (pin "13") (pinfunction "B_13") (pintype "input"))
      (node (ref "IC706") (pin "4") (pinfunction "D4_4") (pintype "passive"))
      (node (ref "R710") (pin "1") (pinfunction "1_1") (pintype "passive"))
      (node (ref "X701") (pin "3") (pinfunction "3_3") (pintype "passive"))
      (node (ref "X703") (pin "3") (pinfunction "S_3") (pintype "passive"))
    )
    (net (code "588") (name "Net-(IC705A-C)") (class "Default")
      (node (ref "IC705") (pin "12") (pinfunction "C_12") (pintype "input"))
      (node (ref "IC706") (pin "3") (pinfunction "D3_3") (pintype "passive"))
      (node (ref "R709") (pin "1") (pinfunction "1_1") (pintype "passive"))
      (node (ref "X701") (pin "2") (pinfunction "2_2") (pintype "passive"))
      (node (ref "X703") (pin "4") (pinfunction "S_4") (pintype "passive"))
    )
    (net (code "589") (name "Net-(IC705A-Q0)") (class "Default")
      (node (ref "IC705") (pin "3") (pinfunction "Q0_3") (pintype "output"))
      (node (ref "IC707") (pin "1") (pinfunction "I1_1") (pintype "input"))
      (node (ref "IC707") (pin "2") (pinfunction "I2_2") (pintype "input"))
      (node (ref "Q706") (pin "1") (pinfunction "G_1") (pintype "passive"))
    )
    (net (code "590") (name "Net-(IC705A-Q1)") (class "Default")
      (node (ref "IC705") (pin "14") (pinfunction "Q1_14") (pintype "output"))
      (node (ref "IC707") (pin "6") (pinfunction "I6_6") (pintype "input"))
    )
    (net (code "591") (name "Net-(IC705A-Q2)") (class "Default")
      (node (ref "IC705") (pin "2") (pinfunction "Q2_2") (pintype "output"))
      (node (ref "IC707") (pin "7") (pinfunction "I7_7") (pintype "input"))
    )
    (net (code "592") (name "Net-(IC705A-Q3)") (class "Default")
      (node (ref "IC705") (pin "15") (pinfunction "Q3_15") (pintype "output"))
      (node (ref "IC707") (pin "5") (pinfunction "I5_5") (pintype "input"))
    )
    (net (code "593") (name "Net-(IC705A-Q4)") (class "Default")
      (node (ref "IC705") (pin "1") (pinfunction "Q4_1") (pintype "output"))
      (node (ref "IC707") (pin "4") (pinfunction "I4_4") (pintype "input"))
    )
    (net (code "594") (name "Net-(IC705A-Q5)") (class "Default")
      (node (ref "IC705") (pin "6") (pinfunction "Q5_6") (pintype "output"))
      (node (ref "IC707") (pin "3") (pinfunction "I3_3") (pintype "input"))
    )
    (net (code "595") (name "Net-(IC707-O2)") (class "Default")
      (node (ref "IC707") (pin "15") (pinfunction "O2_15") (pintype "open_collector"))
      (node (ref "R728") (pin "1") (pinfunction "1_1") (pintype "passive"))
    )
    (net (code "596") (name "Net-(IC708A-+IN)") (class "Default")
      (node (ref "IC708") (pin "5") (pinfunction "+IN_5") (pintype "input"))
      (node (ref "R731") (pin "1") (pinfunction "1_1") (pintype "passive"))
      (node (ref "R732") (pin "2") (pinfunction "2_2") (pintype "passive"))
      (node (ref "R733") (pin "2") (pinfunction "2_2") (pintype "passive"))
    )
    (net (code "597") (name "Net-(IC708A--IN)") (class "Default")
      (node (ref "C708") (pin "1") (pinfunction "1_1") (pintype "passive"))
      (node (ref "IC708") (pin "4") (pinfunction "-IN_4") (pintype "input"))
      (node (ref "R730") (pin "1") (pinfunction "1_1") (pintype "passive"))
    )
    (net (code "598") (name "Net-(IC708B-+IN)") (class "Default")
      (node (ref "IC708") (pin "7") (pinfunction "+IN_7") (pintype "input"))
      (node (ref "R721") (pin "1") (pinfunction "1_1") (pintype "passive"))
      (node (ref "R722") (pin "1") (pinfunction "1_1") (pintype "passive"))
    )
    (net (code "599") (name "Net-(IC708B--IN)") (class "Default")
      (node (ref "IC708") (pin "6") (pinfunction "-IN_6") (pintype "input"))
      (node (ref "IC708") (pin "8") (pinfunction "-IN_8") (pintype "input"))
      (node (ref "R720") (pin "1") (pinfunction "1_1") (pintype "passive"))
    )
    (net (code "600") (name "Net-(IC708B-OUT)") (class "Default")
      (node (ref "IC708") (pin "1") (pinfunction "OUT_1") (pintype "open_collector"))
      (node (ref "R724") (pin "2") (pinfunction "2_2") (pintype "passive"))
      (node (ref "R725") (pin "2") (pinfunction "2_2") (pintype "passive"))
    )
    (net (code "601") (name "Net-(IC708C-+IN)") (class "Default")
      (node (ref "C705") (pin "1") (pinfunction "1_1") (pintype "passive"))
      (node (ref "IC708") (pin "9") (pinfunction "+IN_9") (pintype "input"))
      (node (ref "R722") (pin "2") (pinfunction "2_2") (pintype "passive"))
      (node (ref "R723") (pin "2") (pinfunction "2_2") (pintype "passive"))
    )
    (net (code "602") (name "Net-(IC708C-OUT)") (class "Default")
      (node (ref "C706") (pin "2") (pinfunction "2_2") (pintype "passive"))
      (node (ref "IC708") (pin "14") (pinfunction "OUT_14") (pintype "open_collector"))
      (node (ref "R726") (pin "2") (pinfunction "2_2") (pintype "passive"))
    )
    (net (code "603") (name "Net-(IC709-ADJ)") (class "Default")
      (node (ref "IC709") (pin "1") (pinfunction "ADJ_1") (pintype "input"))
      (node (ref "R720") (pin "2") (pinfunction "2_2") (pintype "passive"))
      (node (ref "R734") (pin "1") (pinfunction "1_1") (pintype "passive"))
      (node (ref "X701") (pin "7") (pinfunction "7_7") (pintype "passive"))
    )
    (net (code "604") (name "Net-(IC709-VI)") (class "Default")
      (node (ref "IC709") (pin "3") (pinfunction "VI_3") (pintype "input"))
      (node (ref "Q705") (pin "2") (pinfunction "C_2") (pintype "passive"))
    )
    (net (code "605") (name "Net-(IC709-VO)") (class "Default")
      (node (ref "IC709") (pin "2") (pinfunction "VO_2") (pintype "passive"))
      (node (ref "R734") (pin "2") (pinfunction "2_2") (pintype "passive"))
    )
    (net (code "606") (name "Net-(IC710-CV)") (class "Default")
      (node (ref "IC710") (pin "5") (pinfunction "CV_5") (pintype "input"))
      (node (ref "R744") (pin "2") (pinfunction "2_2") (pintype "passive"))
    )
    (net (code "607") (name "Net-(IC710-Q)") (class "Default")
      (node (ref "IC710") (pin "3") (pinfunction "Q_3") (pintype "output"))
      (node (ref "IC711") (pin "12") (pinfunction "A_12") (pintype "input"))
      (node (ref "R744") (pin "1") (pinfunction "1_1") (pintype "passive"))
    )
    (net (code "608") (name "Net-(IC711B-B)") (class "Default")
      (node (ref "IC711") (pin "11") (pinfunction "B_11") (pintype "input"))
      (node (ref "IC711") (pin "9") (pinfunction "~{Q}_9") (pintype "output"))
      (node (ref "R746") (pin "2") (pinfunction "2_2") (pintype "passive"))
    )
    (net (code "609") (name "Net-(IC711B-T2)") (class "Default")
      (node (ref "C710") (pin "1") (pinfunction "1_1") (pintype "passive"))
      (node (ref "IC711") (pin "14") (pinfunction "T2_14") (pintype "input"))
      (node (ref "R745") (pin "1") (pinfunction "1_1") (pintype "passive"))
    )
    (net (code "610") (name "Net-(IC801A-+IN)") (class "Default")
      (node (ref "C801") (pin "1") (pinfunction "1_1") (pintype "passive"))
      (node (ref "IC801") (pin "3") (pinfunction "+IN_3") (pintype "input"))
      (node (ref "R805") (pin "1") (pinfunction "1_1") (pintype "passive"))
    )
    (net (code "611") (name "Net-(IC801A--IN)") (class "Default")
      (node (ref "IC801") (pin "2") (pinfunction "-IN_2") (pintype "input"))
      (node (ref "R807") (pin "2") (pinfunction "2_2") (pintype "passive"))
    )
    (net (code "612") (name "Net-(IC801A-OUT)") (class "Default")
      (node (ref "IC801") (pin "1") (pinfunction "OUT_1") (pintype "output"))
      (node (ref "R808") (pin "2") (pinfunction "2_2") (pintype "passive"))
    )
    (net (code "613") (name "Net-(IC801B-+IN)") (class "Default")
      (node (ref "IC801") (pin "5") (pinfunction "+IN_5") (pintype "input"))
      (node (ref "R812") (pin "2") (pinfunction "2_2") (pintype "passive"))
      (node (ref "R817") (pin "2") (pinfunction "2_2") (pintype "passive"))
    )
    (net (code "614") (name "Net-(IC801B--IN)") (class "Default")
      (node (ref "IC801") (pin "6") (pinfunction "-IN_6") (pintype "input"))
      (node (ref "R813") (pin "1") (pinfunction "1_1") (pintype "passive"))
      (node (ref "R814") (pin "2") (pinfunction "2_2") (pintype "passive"))
    )
    (net (code "615") (name "Net-(IC801B-OUT)") (class "Default")
      (node (ref "IC801") (pin "7") (pinfunction "OUT_7") (pintype "output"))
      (node (ref "R816") (pin "1") (pinfunction "1_1") (pintype "passive"))
      (node (ref "R817") (pin "1") (pinfunction "1_1") (pintype "passive"))
    )
    (net (code "616") (name "Net-(IC805A-A)") (class "Default")
      (node (ref "IC805") (pin "10") (pinfunction "A_10") (pintype "input"))
      (node (ref "IC806") (pin "1") (pinfunction "D1_1") (pintype "passive"))
      (node (ref "R811") (pin "1") (pinfunction "1_1") (pintype "passive"))
      (node (ref "X801") (pin "4") (pinfunction "4_4") (pintype "passive"))
      (node (ref "X803") (pin "2") (pinfunction "S_2") (pintype "passive"))
    )
    (net (code "617") (name "Net-(IC805A-B)") (class "Default")
      (node (ref "IC805") (pin "13") (pinfunction "B_13") (pintype "input"))
      (node (ref "IC806") (pin "4") (pinfunction "D4_4") (pintype "passive"))
      (node (ref "R810") (pin "1") (pinfunction "1_1") (pintype "passive"))
      (node (ref "X801") (pin "3") (pinfunction "3_3") (pintype "passive"))
      (node (ref "X803") (pin "3") (pinfunction "S_3") (pintype "passive"))
    )
    (net (code "618") (name "Net-(IC805A-C)") (class "Default")
      (node (ref "IC805") (pin "12") (pinfunction "C_12") (pintype "input"))
      (node (ref "IC806") (pin "3") (pinfunction "D3_3") (pintype "passive"))
      (node (ref "R809") (pin "1") (pinfunction "1_1") (pintype "passive"))
      (node (ref "X801") (pin "2") (pinfunction "2_2") (pintype "passive"))
      (node (ref "X803") (pin "4") (pinfunction "S_4") (pintype "passive"))
    )
    (net (code "619") (name "Net-(IC805A-Q0)") (class "Default")
      (node (ref "IC805") (pin "3") (pinfunction "Q0_3") (pintype "output"))
      (node (ref "IC807") (pin "1") (pinfunction "I1_1") (pintype "input"))
      (node (ref "IC807") (pin "2") (pinfunction "I2_2") (pintype "input"))
      (node (ref "Q806") (pin "1") (pinfunction "G_1") (pintype "passive"))
    )
    (net (code "620") (name "Net-(IC805A-Q1)") (class "Default")
      (node (ref "IC805") (pin "14") (pinfunction "Q1_14") (pintype "output"))
      (node (ref "IC807") (pin "6") (pinfunction "I6_6") (pintype "input"))
    )
    (net (code "621") (name "Net-(IC805A-Q2)") (class "Default")
      (node (ref "IC805") (pin "2") (pinfunction "Q2_2") (pintype "output"))
      (node (ref "IC807") (pin "7") (pinfunction "I7_7") (pintype "input"))
    )
    (net (code "622") (name "Net-(IC805A-Q3)") (class "Default")
      (node (ref "IC805") (pin "15") (pinfunction "Q3_15") (pintype "output"))
      (node (ref "IC807") (pin "5") (pinfunction "I5_5") (pintype "input"))
    )
    (net (code "623") (name "Net-(IC805A-Q4)") (class "Default")
      (node (ref "IC805") (pin "1") (pinfunction "Q4_1") (pintype "output"))
      (node (ref "IC807") (pin "4") (pinfunction "I4_4") (pintype "input"))
    )
    (net (code "624") (name "Net-(IC805A-Q5)") (class "Default")
      (node (ref "IC805") (pin "6") (pinfunction "Q5_6") (pintype "output"))
      (node (ref "IC807") (pin "3") (pinfunction "I3_3") (pintype "input"))
    )
    (net (code "625") (name "Net-(IC807-O2)") (class "Default")
      (node (ref "IC807") (pin "15") (pinfunction "O2_15") (pintype "open_collector"))
      (node (ref "R828") (pin "1") (pinfunction "1_1") (pintype "passive"))
    )
    (net (code "626") (name "Net-(IC808A-+IN)") (class "Default")
      (node (ref "IC808") (pin "5") (pinfunction "+IN_5") (pintype "input"))
      (node (ref "R831") (pin "1") (pinfunction "1_1") (pintype "passive"))
      (node (ref "R832") (pin "2") (pinfunction "2_2") (pintype "passive"))
      (node (ref "R833") (pin "2") (pinfunction "2_2") (pintype "passive"))
    )
    (net (code "627") (name "Net-(IC808A--IN)") (class "Default")
      (node (ref "C808") (pin "1") (pinfunction "1_1") (pintype "passive"))
      (node (ref "IC808") (pin "4") (pinfunction "-IN_4") (pintype "input"))
      (node (ref "R830") (pin "1") (pinfunction "1_1") (pintype "passive"))
    )
    (net (code "628") (name "Net-(IC808B-+IN)") (class "Default")
      (node (ref "IC808") (pin "7") (pinfunction "+IN_7") (pintype "input"))
      (node (ref "R821") (pin "1") (pinfunction "1_1") (pintype "passive"))
      (node (ref "R822") (pin "1") (pinfunction "1_1") (pintype "passive"))
    )
    (net (code "629") (name "Net-(IC808B--IN)") (class "Default")
      (node (ref "IC808") (pin "6") (pinfunction "-IN_6") (pintype "input"))
      (node (ref "IC808") (pin "8") (pinfunction "-IN_8") (pintype "input"))
      (node (ref "R820") (pin "1") (pinfunction "1_1") (pintype "passive"))
    )
    (net (code "630") (name "Net-(IC808B-OUT)") (class "Default")
      (node (ref "IC808") (pin "1") (pinfunction "OUT_1") (pintype "open_collector"))
      (node (ref "R824") (pin "2") (pinfunction "2_2") (pintype "passive"))
      (node (ref "R825") (pin "2") (pinfunction "2_2") (pintype "passive"))
    )
    (net (code "631") (name "Net-(IC808C-+IN)") (class "Default")
      (node (ref "C805") (pin "1") (pinfunction "1_1") (pintype "passive"))
      (node (ref "IC808") (pin "9") (pinfunction "+IN_9") (pintype "input"))
      (node (ref "R822") (pin "2") (pinfunction "2_2") (pintype "passive"))
      (node (ref "R823") (pin "2") (pinfunction "2_2") (pintype "passive"))
    )
    (net (code "632") (name "Net-(IC808C-OUT)") (class "Default")
      (node (ref "C806") (pin "2") (pinfunction "2_2") (pintype "passive"))
      (node (ref "IC808") (pin "14") (pinfunction "OUT_14") (pintype "open_collector"))
      (node (ref "R826") (pin "2") (pinfunction "2_2") (pintype "passive"))
    )
    (net (code "633") (name "Net-(IC809-ADJ)") (class "Default")
      (node (ref "IC809") (pin "1") (pinfunction "ADJ_1") (pintype "input"))
      (node (ref "R820") (pin "2") (pinfunction "2_2") (pintype "passive"))
      (node (ref "R834") (pin "1") (pinfunction "1_1") (pintype "passive"))
      (node (ref "X801") (pin "7") (pinfunction "7_7") (pintype "passive"))
    )
    (net (code "634") (name "Net-(IC809-VI)") (class "Default")
      (node (ref "IC809") (pin "3") (pinfunction "VI_3") (pintype "input"))
      (node (ref "Q805") (pin "2") (pinfunction "C_2") (pintype "passive"))
    )
    (net (code "635") (name "Net-(IC809-VO)") (class "Default")
      (node (ref "IC809") (pin "2") (pinfunction "VO_2") (pintype "passive"))
      (node (ref "R834") (pin "2") (pinfunction "2_2") (pintype "passive"))
    )
    (net (code "636") (name "Net-(IC810-CV)") (class "Default")
      (node (ref "IC810") (pin "5") (pinfunction "CV_5") (pintype "input"))
      (node (ref "R844") (pin "2") (pinfunction "2_2") (pintype "passive"))
    )
    (net (code "637") (name "Net-(IC810-Q)") (class "Default")
      (node (ref "IC810") (pin "3") (pinfunction "Q_3") (pintype "output"))
      (node (ref "IC811") (pin "12") (pinfunction "A_12") (pintype "input"))
      (node (ref "R844") (pin "1") (pinfunction "1_1") (pintype "passive"))
    )
    (net (code "638") (name "Net-(IC811B-B)") (class "Default")
      (node (ref "IC811") (pin "11") (pinfunction "B_11") (pintype "input"))
      (node (ref "IC811") (pin "9") (pinfunction "~{Q}_9") (pintype "output"))
      (node (ref "R846") (pin "2") (pinfunction "2_2") (pintype "passive"))
    )
    (net (code "639") (name "Net-(IC811B-T2)") (class "Default")
      (node (ref "C810") (pin "1") (pinfunction "1_1") (pintype "passive"))
      (node (ref "IC811") (pin "14") (pinfunction "T2_14") (pintype "input"))
      (node (ref "R845") (pin "1") (pinfunction "1_1") (pintype "passive"))
    )
    (net (code "640") (name "Net-(IC901A-+IN)") (class "Default")
      (node (ref "C901") (pin "1") (pinfunction "1_1") (pintype "passive"))
      (node (ref "IC901") (pin "3") (pinfunction "+IN_3") (pintype "input"))
      (node (ref "R905") (pin "1") (pinfunction "1_1") (pintype "passive"))
    )
    (net (code "641") (name "Net-(IC901A--IN)") (class "Default")
      (node (ref "IC901") (pin "2") (pinfunction "-IN_2") (pintype "input"))
      (node (ref "R907") (pin "2") (pinfunction "2_2") (pintype "passive"))
    )
    (net (code "642") (name "Net-(IC901A-OUT)") (class "Default")
      (node (ref "IC901") (pin "1") (pinfunction "OUT_1") (pintype "output"))
      (node (ref "R908") (pin "2") (pinfunction "2_2") (pintype "passive"))
    )
    (net (code "643") (name "Net-(IC901B-+IN)") (class "Default")
      (node (ref "IC901") (pin "5") (pinfunction "+IN_5") (pintype "input"))
      (node (ref "R912") (pin "2") (pinfunction "2_2") (pintype "passive"))
      (node (ref "R917") (pin "2") (pinfunction "2_2") (pintype "passive"))
    )
    (net (code "644") (name "Net-(IC901B--IN)") (class "Default")
      (node (ref "IC901") (pin "6") (pinfunction "-IN_6") (pintype "input"))
      (node (ref "R913") (pin "1") (pinfunction "1_1") (pintype "passive"))
      (node (ref "R914") (pin "2") (pinfunction "2_2") (pintype "passive"))
    )
    (net (code "645") (name "Net-(IC901B-OUT)") (class "Default")
      (node (ref "IC901") (pin "7") (pinfunction "OUT_7") (pintype "output"))
      (node (ref "R916") (pin "1") (pinfunction "1_1") (pintype "passive"))
      (node (ref "R917") (pin "1") (pinfunction "1_1") (pintype "passive"))
    )
    (net (code "646") (name "Net-(IC905A-A)") (class "Default")
      (node (ref "IC905") (pin "10") (pinfunction "A_10") (pintype "input"))
      (node (ref "IC906") (pin "1") (pinfunction "D1_1") (pintype "passive"))
      (node (ref "R911") (pin "1") (pinfunction "1_1") (pintype "passive"))
      (node (ref "X901") (pin "4") (pinfunction "4_4") (pintype "passive"))
      (node (ref "X903") (pin "2") (pinfunction "S_2") (pintype "passive"))
    )
    (net (code "647") (name "Net-(IC905A-B)") (class "Default")
      (node (ref "IC905") (pin "13") (pinfunction "B_13") (pintype "input"))
      (node (ref "IC906") (pin "4") (pinfunction "D4_4") (pintype "passive"))
      (node (ref "R910") (pin "1") (pinfunction "1_1") (pintype "passive"))
      (node (ref "X901") (pin "3") (pinfunction "3_3") (pintype "passive"))
      (node (ref "X903") (pin "3") (pinfunction "S_3") (pintype "passive"))
    )
    (net (code "648") (name "Net-(IC905A-C)") (class "Default")
      (node (ref "IC905") (pin "12") (pinfunction "C_12") (pintype "input"))
      (node (ref "IC906") (pin "3") (pinfunction "D3_3") (pintype "passive"))
      (node (ref "R909") (pin "1") (pinfunction "1_1") (pintype "passive"))
      (node (ref "X901") (pin "2") (pinfunction "2_2") (pintype "passive"))
      (node (ref "X903") (pin "4") (pinfunction "S_4") (pintype "passive"))
    )
    (net (code "649") (name "Net-(IC905A-Q0)") (class "Default")
      (node (ref "IC905") (pin "3") (pinfunction "Q0_3") (pintype "output"))
      (node (ref "IC907") (pin "1") (pinfunction "I1_1") (pintype "input"))
      (node (ref "IC907") (pin "2") (pinfunction "I2_2") (pintype "input"))
      (node (ref "Q906") (pin "1") (pinfunction "G_1") (pintype "passive"))
    )
    (net (code "650") (name "Net-(IC905A-Q1)") (class "Default")
      (node (ref "IC905") (pin "14") (pinfunction "Q1_14") (pintype "output"))
      (node (ref "IC907") (pin "6") (pinfunction "I6_6") (pintype "input"))
    )
    (net (code "651") (name "Net-(IC905A-Q2)") (class "Default")
      (node (ref "IC905") (pin "2") (pinfunction "Q2_2") (pintype "output"))
      (node (ref "IC907") (pin "7") (pinfunction "I7_7") (pintype "input"))
    )
    (net (code "652") (name "Net-(IC905A-Q3)") (class "Default")
      (node (ref "IC905") (pin "15") (pinfunction "Q3_15") (pintype "output"))
      (node (ref "IC907") (pin "5") (pinfunction "I5_5") (pintype "input"))
    )
    (net (code "653") (name "Net-(IC905A-Q4)") (class "Default")
      (node (ref "IC905") (pin "1") (pinfunction "Q4_1") (pintype "output"))
      (node (ref "IC907") (pin "4") (pinfunction "I4_4") (pintype "input"))
    )
    (net (code "654") (name "Net-(IC905A-Q5)") (class "Default")
      (node (ref "IC905") (pin "6") (pinfunction "Q5_6") (pintype "output"))
      (node (ref "IC907") (pin "3") (pinfunction "I3_3") (pintype "input"))
    )
    (net (code "655") (name "Net-(IC907-O2)") (class "Default")
      (node (ref "IC907") (pin "15") (pinfunction "O2_15") (pintype "open_collector"))
      (node (ref "R928") (pin "1") (pinfunction "1_1") (pintype "passive"))
    )
    (net (code "656") (name "Net-(IC908A-+IN)") (class "Default")
      (node (ref "IC908") (pin "5") (pinfunction "+IN_5") (pintype "input"))
      (node (ref "R931") (pin "1") (pinfunction "1_1") (pintype "passive"))
      (node (ref "R932") (pin "2") (pinfunction "2_2") (pintype "passive"))
      (node (ref "R933") (pin "2") (pinfunction "2_2") (pintype "passive"))
    )
    (net (code "657") (name "Net-(IC908A--IN)") (class "Default")
      (node (ref "C908") (pin "1") (pinfunction "1_1") (pintype "passive"))
      (node (ref "IC908") (pin "4") (pinfunction "-IN_4") (pintype "input"))
      (node (ref "R930") (pin "1") (pinfunction "1_1") (pintype "passive"))
    )
    (net (code "658") (name "Net-(IC908B-+IN)") (class "Default")
      (node (ref "IC908") (pin "7") (pinfunction "+IN_7") (pintype "input"))
      (node (ref "R921") (pin "1") (pinfunction "1_1") (pintype "passive"))
      (node (ref "R922") (pin "1") (pinfunction "1_1") (pintype "passive"))
    )
    (net (code "659") (name "Net-(IC908B--IN)") (class "Default")
      (node (ref "IC908") (pin "6") (pinfunction "-IN_6") (pintype "input"))
      (node (ref "IC908") (pin "8") (pinfunction "-IN_8") (pintype "input"))
      (node (ref "R920") (pin "1") (pinfunction "1_1") (pintype "passive"))
    )
    (net (code "660") (name "Net-(IC908B-OUT)") (class "Default")
      (node (ref "IC908") (pin "1") (pinfunction "OUT_1") (pintype "open_collector"))
      (node (ref "R924") (pin "2") (pinfunction "2_2") (pintype "passive"))
      (node (ref "R925") (pin "2") (pinfunction "2_2") (pintype "passive"))
    )
    (net (code "661") (name "Net-(IC908C-+IN)") (class "Default")
      (node (ref "C905") (pin "1") (pinfunction "1_1") (pintype "passive"))
      (node (ref "IC908") (pin "9") (pinfunction "+IN_9") (pintype "input"))
      (node (ref "R922") (pin "2") (pinfunction "2_2") (pintype "passive"))
      (node (ref "R923") (pin "2") (pinfunction "2_2") (pintype "passive"))
    )
    (net (code "662") (name "Net-(IC908C-OUT)") (class "Default")
      (node (ref "C906") (pin "2") (pinfunction "2_2") (pintype "passive"))
      (node (ref "IC908") (pin "14") (pinfunction "OUT_14") (pintype "open_collector"))
      (node (ref "R926") (pin "2") (pinfunction "2_2") (pintype "passive"))
    )
    (net (code "663") (name "Net-(IC909-ADJ)") (class "Default")
      (node (ref "IC909") (pin "1") (pinfunction "ADJ_1") (pintype "input"))
      (node (ref "R920") (pin "2") (pinfunction "2_2") (pintype "passive"))
      (node (ref "R934") (pin "1") (pinfunction "1_1") (pintype "passive"))
      (node (ref "X901") (pin "7") (pinfunction "7_7") (pintype "passive"))
    )
    (net (code "664") (name "Net-(IC909-VI)") (class "Default")
      (node (ref "IC909") (pin "3") (pinfunction "VI_3") (pintype "input"))
      (node (ref "Q905") (pin "2") (pinfunction "C_2") (pintype "passive"))
    )
    (net (code "665") (name "Net-(IC909-VO)") (class "Default")
      (node (ref "IC909") (pin "2") (pinfunction "VO_2") (pintype "passive"))
      (node (ref "R934") (pin "2") (pinfunction "2_2") (pintype "passive"))
    )
    (net (code "666") (name "Net-(IC910-CV)") (class "Default")
      (node (ref "IC910") (pin "5") (pinfunction "CV_5") (pintype "input"))
      (node (ref "R944") (pin "2") (pinfunction "2_2") (pintype "passive"))
    )
    (net (code "667") (name "Net-(IC910-Q)") (class "Default")
      (node (ref "IC910") (pin "3") (pinfunction "Q_3") (pintype "output"))
      (node (ref "IC911") (pin "12") (pinfunction "A_12") (pintype "input"))
      (node (ref "R944") (pin "1") (pinfunction "1_1") (pintype "passive"))
    )
    (net (code "668") (name "Net-(IC911B-B)") (class "Default")
      (node (ref "IC911") (pin "11") (pinfunction "B_11") (pintype "input"))
      (node (ref "IC911") (pin "9") (pinfunction "~{Q}_9") (pintype "output"))
      (node (ref "R946") (pin "2") (pinfunction "2_2") (pintype "passive"))
    )
    (net (code "669") (name "Net-(IC911B-T2)") (class "Default")
      (node (ref "C910") (pin "1") (pinfunction "1_1") (pintype "passive"))
      (node (ref "IC911") (pin "14") (pinfunction "T2_14") (pintype "input"))
      (node (ref "R945") (pin "1") (pinfunction "1_1") (pintype "passive"))
    )
    (net (code "670") (name "Net-(IC1001A-+IN)") (class "Default")
      (node (ref "C1001") (pin "1") (pinfunction "1_1") (pintype "passive"))
      (node (ref "IC1001") (pin "3") (pinfunction "+IN_3") (pintype "input"))
      (node (ref "R1005") (pin "1") (pinfunction "1_1") (pintype "passive"))
    )
    (net (code "671") (name "Net-(IC1001A--IN)") (class "Default")
      (node (ref "IC1001") (pin "2") (pinfunction "-IN_2") (pintype "input"))
      (node (ref "R1007") (pin "2") (pinfunction "2_2") (pintype "passive"))
    )
    (net (code "672") (name "Net-(IC1001A-OUT)") (class "Default")
      (node (ref "IC1001") (pin "1") (pinfunction "OUT_1") (pintype "output"))
      (node (ref "R1008") (pin "2") (pinfunction "2_2") (pintype "passive"))
    )
    (net (code "673") (name "Net-(IC1001B-+IN)") (class "Default")
      (node (ref "IC1001") (pin "5") (pinfunction "+IN_5") (pintype "input"))
      (node (ref "R1012") (pin "2") (pinfunction "2_2") (pintype "passive"))
      (node (ref "R1017") (pin "2") (pinfunction "2_2") (pintype "passive"))
    )
    (net (code "674") (name "Net-(IC1001B--IN)") (class "Default")
      (node (ref "IC1001") (pin "6") (pinfunction "-IN_6") (pintype "input"))
      (node (ref "R1013") (pin "1") (pinfunction "1_1") (pintype "passive"))
      (node (ref "R1014") (pin "2") (pinfunction "2_2") (pintype "passive"))
    )
    (net (code "675") (name "Net-(IC1001B-OUT)") (class "Default")
      (node (ref "IC1001") (pin "7") (pinfunction "OUT_7") (pintype "output"))
      (node (ref "R1016") (pin "1") (pinfunction "1_1") (pintype "passive"))
      (node (ref "R1017") (pin "1") (pinfunction "1_1") (pintype "passive"))
    )
    (net (code "676") (name "Net-(IC1005A-A)") (class "Default")
      (node (ref "IC1005") (pin "10") (pinfunction "A_10") (pintype "input"))
      (node (ref "IC1006") (pin "1") (pinfunction "D1_1") (pintype "passive"))
      (node (ref "R1011") (pin "1") (pinfunction "1_1") (pintype "passive"))
      (node (ref "X1001") (pin "4") (pinfunction "4_4") (pintype "passive"))
      (node (ref "X1003") (pin "2") (pinfunction "S_2") (pintype "passive"))
    )
    (net (code "677") (name "Net-(IC1005A-B)") (class "Default")
      (node (ref "IC1005") (pin "13") (pinfunction "B_13") (pintype "input"))
      (node (ref "IC1006") (pin "4") (pinfunction "D4_4") (pintype "passive"))
      (node (ref "R1010") (pin "1") (pinfunction "1_1") (pintype "passive"))
      (node (ref "X1001") (pin "3") (pinfunction "3_3") (pintype "passive"))
      (node (ref "X1003") (pin "3") (pinfunction "S_3") (pintype "passive"))
    )
    (net (code "678") (name "Net-(IC1005A-C)") (class "Default")
      (node (ref "IC1005") (pin "12") (pinfunction "C_12") (pintype "input"))
      (node (ref "IC1006") (pin "3") (pinfunction "D3_3") (pintype "passive"))
      (node (ref "R1009") (pin "1") (pinfunction "1_1") (pintype "passive"))
      (node (ref "X1001") (pin "2") (pinfunction "2_2") (pintype "passive"))
      (node (ref "X1003") (pin "4") (pinfunction "S_4") (pintype "passive"))
    )
    (net (code "679") (name "Net-(IC1005A-Q0)") (class "Default")
      (node (ref "IC1005") (pin "3") (pinfunction "Q0_3") (pintype "output"))
      (node (ref "IC1007") (pin "1") (pinfunction "I1_1") (pintype "input"))
      (node (ref "IC1007") (pin "2") (pinfunction "I2_2") (pintype "input"))
      (node (ref "Q1006") (pin "1") (pinfunction "G_1") (pintype "passive"))
    )
    (net (code "680") (name "Net-(IC1005A-Q1)") (class "Default")
      (node (ref "IC1005") (pin "14") (pinfunction "Q1_14") (pintype "output"))
      (node (ref "IC1007") (pin "6") (pinfunction "I6_6") (pintype "input"))
    )
    (net (code "681") (name "Net-(IC1005A-Q2)") (class "Default")
      (node (ref "IC1005") (pin "2") (pinfunction "Q2_2") (pintype "output"))
      (node (ref "IC1007") (pin "7") (pinfunction "I7_7") (pintype "input"))
    )
    (net (code "682") (name "Net-(IC1005A-Q3)") (class "Default")
      (node (ref "IC1005") (pin "15") (pinfunction "Q3_15") (pintype "output"))
      (node (ref "IC1007") (pin "5") (pinfunction "I5_5") (pintype "input"))
    )
    (net (code "683") (name "Net-(IC1005A-Q4)") (class "Default")
      (node (ref "IC1005") (pin "1") (pinfunction "Q4_1") (pintype "output"))
      (node (ref "IC1007") (pin "4") (pinfunction "I4_4") (pintype "input"))
    )
    (net (code "684") (name "Net-(IC1005A-Q5)") (class "Default")
      (node (ref "IC1005") (pin "6") (pinfunction "Q5_6") (pintype "output"))
      (node (ref "IC1007") (pin "3") (pinfunction "I3_3") (pintype "input"))
    )
    (net (code "685") (name "Net-(IC1007-O2)") (class "Default")
      (node (ref "IC1007") (pin "15") (pinfunction "O2_15") (pintype "open_collector"))
      (node (ref "R1028") (pin "1") (pinfunction "1_1") (pintype "passive"))
    )
    (net (code "686") (name "Net-(IC1008A-+IN)") (class "Default")
      (node (ref "IC1008") (pin "5") (pinfunction "+IN_5") (pintype "input"))
      (node (ref "R1031") (pin "1") (pinfunction "1_1") (pintype "passive"))
      (node (ref "R1032") (pin "2") (pinfunction "2_2") (pintype "passive"))
      (node (ref "R1033") (pin "2") (pinfunction "2_2") (pintype "passive"))
    )
    (net (code "687") (name "Net-(IC1008A--IN)") (class "Default")
      (node (ref "C1008") (pin "1") (pinfunction "1_1") (pintype "passive"))
      (node (ref "IC1008") (pin "4") (pinfunction "-IN_4") (pintype "input"))
      (node (ref "R1030") (pin "1") (pinfunction "1_1") (pintype "passive"))
    )
    (net (code "688") (name "Net-(IC1008B-+IN)") (class "Default")
      (node (ref "IC1008") (pin "7") (pinfunction "+IN_7") (pintype "input"))
      (node (ref "R1021") (pin "1") (pinfunction "1_1") (pintype "passive"))
      (node (ref "R1022") (pin "1") (pinfunction "1_1") (pintype "passive"))
    )
    (net (code "689") (name "Net-(IC1008B--IN)") (class "Default")
      (node (ref "IC1008") (pin "6") (pinfunction "-IN_6") (pintype "input"))
      (node (ref "IC1008") (pin "8") (pinfunction "-IN_8") (pintype "input"))
      (node (ref "R1020") (pin "1") (pinfunction "1_1") (pintype "passive"))
    )
    (net (code "690") (name "Net-(IC1008B-OUT)") (class "Default")
      (node (ref "IC1008") (pin "1") (pinfunction "OUT_1") (pintype "open_collector"))
      (node (ref "R1024") (pin "2") (pinfunction "2_2") (pintype "passive"))
      (node (ref "R1025") (pin "2") (pinfunction "2_2") (pintype "passive"))
    )
    (net (code "691") (name "Net-(IC1008C-+IN)") (class "Default")
      (node (ref "C1005") (pin "1") (pinfunction "1_1") (pintype "passive"))
      (node (ref "IC1008") (pin "9") (pinfunction "+IN_9") (pintype "input"))
      (node (ref "R1022") (pin "2") (pinfunction "2_2") (pintype "passive"))
      (node (ref "R1023") (pin "2") (pinfunction "2_2") (pintype "passive"))
    )
    (net (code "692") (name "Net-(IC1008C-OUT)") (class "Default")
      (node (ref "C1006") (pin "2") (pinfunction "2_2") (pintype "passive"))
      (node (ref "IC1008") (pin "14") (pinfunction "OUT_14") (pintype "open_collector"))
      (node (ref "R1026") (pin "2") (pinfunction "2_2") (pintype "passive"))
    )
    (net (code "693") (name "Net-(IC1009-ADJ)") (class "Default")
      (node (ref "IC1009") (pin "1") (pinfunction "ADJ_1") (pintype "input"))
      (node (ref "R1020") (pin "2") (pinfunction "2_2") (pintype "passive"))
      (node (ref "R1034") (pin "1") (pinfunction "1_1") (pintype "passive"))
      (node (ref "X1001") (pin "7") (pinfunction "7_7") (pintype "passive"))
    )
    (net (code "694") (name "Net-(IC1009-VI)") (class "Default")
      (node (ref "IC1009") (pin "3") (pinfunction "VI_3") (pintype "input"))
      (node (ref "Q1005") (pin "2") (pinfunction "C_2") (pintype "passive"))
    )
    (net (code "695") (name "Net-(IC1009-VO)") (class "Default")
      (node (ref "IC1009") (pin "2") (pinfunction "VO_2") (pintype "passive"))
      (node (ref "R1034") (pin "2") (pinfunction "2_2") (pintype "passive"))
    )
    (net (code "696") (name "Net-(IC1010-CV)") (class "Default")
      (node (ref "IC1010") (pin "5") (pinfunction "CV_5") (pintype "input"))
      (node (ref "R1044") (pin "2") (pinfunction "2_2") (pintype "passive"))
    )
    (net (code "697") (name "Net-(IC1010-Q)") (class "Default")
      (node (ref "IC1010") (pin "3") (pinfunction "Q_3") (pintype "output"))
      (node (ref "IC1011") (pin "12") (pinfunction "A_12") (pintype "input"))
      (node (ref "R1044") (pin "1") (pinfunction "1_1") (pintype "passive"))
    )
    (net (code "698") (name "Net-(IC1011B-B)") (class "Default")
      (node (ref "IC1011") (pin "11") (pinfunction "B_11") (pintype "input"))
      (node (ref "IC1011") (pin "9") (pinfunction "~{Q}_9") (pintype "output"))
      (node (ref "R1046") (pin "2") (pinfunction "2_2") (pintype "passive"))
    )
    (net (code "699") (name "Net-(IC1011B-T2)") (class "Default")
      (node (ref "C1010") (pin "1") (pinfunction "1_1") (pintype "passive"))
      (node (ref "IC1011") (pin "14") (pinfunction "T2_14") (pintype "input"))
      (node (ref "R1045") (pin "1") (pinfunction "1_1") (pintype "passive"))
    )
    (net (code "700") (name "Net-(IC1101A-+IN)") (class "Default")
      (node (ref "C1101") (pin "1") (pinfunction "1_1") (pintype "passive"))
      (node (ref "IC1101") (pin "3") (pinfunction "+IN_3") (pintype "input"))
      (node (ref "R1105") (pin "1") (pinfunction "1_1") (pintype "passive"))
    )
    (net (code "701") (name "Net-(IC1101A--IN)") (class "Default")
      (node (ref "IC1101") (pin "2") (pinfunction "-IN_2") (pintype "input"))
      (node (ref "R1107") (pin "2") (pinfunction "2_2") (pintype "passive"))
    )
    (net (code "702") (name "Net-(IC1101A-OUT)") (class "Default")
      (node (ref "IC1101") (pin "1") (pinfunction "OUT_1") (pintype "output"))
      (node (ref "R1108") (pin "2") (pinfunction "2_2") (pintype "passive"))
    )
    (net (code "703") (name "Net-(IC1101B-+IN)") (class "Default")
      (node (ref "IC1101") (pin "5") (pinfunction "+IN_5") (pintype "input"))
      (node (ref "R1112") (pin "2") (pinfunction "2_2") (pintype "passive"))
      (node (ref "R1117") (pin "2") (pinfunction "2_2") (pintype "passive"))
    )
    (net (code "704") (name "Net-(IC1101B--IN)") (class "Default")
      (node (ref "IC1101") (pin "6") (pinfunction "-IN_6") (pintype "input"))
      (node (ref "R1113") (pin "1") (pinfunction "1_1") (pintype "passive"))
      (node (ref "R1114") (pin "2") (pinfunction "2_2") (pintype "passive"))
    )
    (net (code "705") (name "Net-(IC1101B-OUT)") (class "Default")
      (node (ref "IC1101") (pin "7") (pinfunction "OUT_7") (pintype "output"))
      (node (ref "R1116") (pin "1") (pinfunction "1_1") (pintype "passive"))
      (node (ref "R1117") (pin "1") (pinfunction "1_1") (pintype "passive"))
    )
    (net (code "706") (name "Net-(IC1105A-A)") (class "Default")
      (node (ref "IC1105") (pin "10") (pinfunction "A_10") (pintype "input"))
      (node (ref "IC1106") (pin "1") (pinfunction "D1_1") (pintype "passive"))
      (node (ref "R1111") (pin "1") (pinfunction "1_1") (pintype "passive"))
      (node (ref "X1101") (pin "4") (pinfunction "4_4") (pintype "passive"))
      (node (ref "X1103") (pin "2") (pinfunction "S_2") (pintype "passive"))
    )
    (net (code "707") (name "Net-(IC1105A-B)") (class "Default")
      (node (ref "IC1105") (pin "13") (pinfunction "B_13") (pintype "input"))
      (node (ref "IC1106") (pin "4") (pinfunction "D4_4") (pintype "passive"))
      (node (ref "R1110") (pin "1") (pinfunction "1_1") (pintype "passive"))
      (node (ref "X1101") (pin "3") (pinfunction "3_3") (pintype "passive"))
      (node (ref "X1103") (pin "3") (pinfunction "S_3") (pintype "passive"))
    )
    (net (code "708") (name "Net-(IC1105A-C)") (class "Default")
      (node (ref "IC1105") (pin "12") (pinfunction "C_12") (pintype "input"))
      (node (ref "IC1106") (pin "3") (pinfunction "D3_3") (pintype "passive"))
      (node (ref "R1109") (pin "1") (pinfunction "1_1") (pintype "passive"))
      (node (ref "X1101") (pin "2") (pinfunction "2_2") (pintype "passive"))
      (node (ref "X1103") (pin "4") (pinfunction "S_4") (pintype "passive"))
    )
    (net (code "709") (name "Net-(IC1105A-Q0)") (class "Default")
      (node (ref "IC1105") (pin "3") (pinfunction "Q0_3") (pintype "output"))
      (node (ref "IC1107") (pin "1") (pinfunction "I1_1") (pintype "input"))
      (node (ref "IC1107") (pin "2") (pinfunction "I2_2") (pintype "input"))
      (node (ref "Q1106") (pin "1") (pinfunction "G_1") (pintype "passive"))
    )
    (net (code "710") (name "Net-(IC1105A-Q1)") (class "Default")
      (node (ref "IC1105") (pin "14") (pinfunction "Q1_14") (pintype "output"))
      (node (ref "IC1107") (pin "6") (pinfunction "I6_6") (pintype "input"))
    )
    (net (code "711") (name "Net-(IC1105A-Q2)") (class "Default")
      (node (ref "IC1105") (pin "2") (pinfunction "Q2_2") (pintype "output"))
      (node (ref "IC1107") (pin "7") (pinfunction "I7_7") (pintype "input"))
    )
    (net (code "712") (name "Net-(IC1105A-Q3)") (class "Default")
      (node (ref "IC1105") (pin "15") (pinfunction "Q3_15") (pintype "output"))
      (node (ref "IC1107") (pin "5") (pinfunction "I5_5") (pintype "input"))
    )
    (net (code "713") (name "Net-(IC1105A-Q4)") (class "Default")
      (node (ref "IC1105") (pin "1") (pinfunction "Q4_1") (pintype "output"))
      (node (ref "IC1107") (pin "4") (pinfunction "I4_4") (pintype "input"))
    )
    (net (code "714") (name "Net-(IC1105A-Q5)") (class "Default")
      (node (ref "IC1105") (pin "6") (pinfunction "Q5_6") (pintype "output"))
      (node (ref "IC1107") (pin "3") (pinfunction "I3_3") (pintype "input"))
    )
    (net (code "715") (name "Net-(IC1107-O2)") (class "Default")
      (node (ref "IC1107") (pin "15") (pinfunction "O2_15") (pintype "open_collector"))
      (node (ref "R1128") (pin "1") (pinfunction "1_1") (pintype "passive"))
    )
    (net (code "716") (name "Net-(IC1108A-+IN)") (class "Default")
      (node (ref "IC1108") (pin "5") (pinfunction "+IN_5") (pintype "input"))
      (node (ref "R1131") (pin "1") (pinfunction "1_1") (pintype "passive"))
      (node (ref "R1132") (pin "2") (pinfunction "2_2") (pintype "passive"))
      (node (ref "R1133") (pin "2") (pinfunction "2_2") (pintype "passive"))
    )
    (net (code "717") (name "Net-(IC1108A--IN)") (class "Default")
      (node (ref "C1108") (pin "1") (pinfunction "1_1") (pintype "passive"))
      (node (ref "IC1108") (pin "4") (pinfunction "-IN_4") (pintype "input"))
      (node (ref "R1130") (pin "1") (pinfunction "1_1") (pintype "passive"))
    )
    (net (code "718") (name "Net-(IC1108B-+IN)") (class "Default")
      (node (ref "IC1108") (pin "7") (pinfunction "+IN_7") (pintype "input"))
      (node (ref "R1121") (pin "1") (pinfunction "1_1") (pintype "passive"))
      (node (ref "R1122") (pin "1") (pinfunction "1_1") (pintype "passive"))
    )
    (net (code "719") (name "Net-(IC1108B--IN)") (class "Default")
      (node (ref "IC1108") (pin "6") (pinfunction "-IN_6") (pintype "input"))
      (node (ref "IC1108") (pin "8") (pinfunction "-IN_8") (pintype "input"))
      (node (ref "R1120") (pin "1") (pinfunction "1_1") (pintype "passive"))
    )
    (net (code "720") (name "Net-(IC1108B-OUT)") (class "Default")
      (node (ref "IC1108") (pin "1") (pinfunction "OUT_1") (pintype "open_collector"))
      (node (ref "R1124") (pin "2") (pinfunction "2_2") (pintype "passive"))
      (node (ref "R1125") (pin "2") (pinfunction "2_2") (pintype "passive"))
    )
    (net (code "721") (name "Net-(IC1108C-+IN)") (class "Default")
      (node (ref "C1105") (pin "1") (pinfunction "1_1") (pintype "passive"))
      (node (ref "IC1108") (pin "9") (pinfunction "+IN_9") (pintype "input"))
      (node (ref "R1122") (pin "2") (pinfunction "2_2") (pintype "passive"))
      (node (ref "R1123") (pin "2") (pinfunction "2_2") (pintype "passive"))
    )
    (net (code "722") (name "Net-(IC1108C-OUT)") (class "Default")
      (node (ref "C1106") (pin "2") (pinfunction "2_2") (pintype "passive"))
      (node (ref "IC1108") (pin "14") (pinfunction "OUT_14") (pintype "open_collector"))
      (node (ref "R1126") (pin "2") (pinfunction "2_2") (pintype "passive"))
    )
    (net (code "723") (name "Net-(IC1109-ADJ)") (class "Default")
      (node (ref "IC1109") (pin "1") (pinfunction "ADJ_1") (pintype "input"))
      (node (ref "R1120") (pin "2") (pinfunction "2_2") (pintype "passive"))
      (node (ref "R1134") (pin "1") (pinfunction "1_1") (pintype "passive"))
      (node (ref "X1101") (pin "7") (pinfunction "7_7") (pintype "passive"))
    )
    (net (code "724") (name "Net-(IC1109-VI)") (class "Default")
      (node (ref "IC1109") (pin "3") (pinfunction "VI_3") (pintype "input"))
      (node (ref "Q1105") (pin "2") (pinfunction "C_2") (pintype "passive"))
    )
    (net (code "725") (name "Net-(IC1109-VO)") (class "Default")
      (node (ref "IC1109") (pin "2") (pinfunction "VO_2") (pintype "passive"))
      (node (ref "R1134") (pin "2") (pinfunction "2_2") (pintype "passive"))
    )
    (net (code "726") (name "Net-(IC1110-CV)") (class "Default")
      (node (ref "IC1110") (pin "5") (pinfunction "CV_5") (pintype "input"))
      (node (ref "R1144") (pin "2") (pinfunction "2_2") (pintype "passive"))
    )
    (net (code "727") (name "Net-(IC1110-Q)") (class "Default")
      (node (ref "IC1110") (pin "3") (pinfunction "Q_3") (pintype "output"))
      (node (ref "IC1111") (pin "12") (pinfunction "A_12") (pintype "input"))
      (node (ref "R1144") (pin "1") (pinfunction "1_1") (pintype "passive"))
    )
    (net (code "728") (name "Net-(IC1111B-B)") (class "Default")
      (node (ref "IC1111") (pin "11") (pinfunction "B_11") (pintype "input"))
      (node (ref "IC1111") (pin "9") (pinfunction "~{Q}_9") (pintype "output"))
      (node (ref "R1146") (pin "2") (pinfunction "2_2") (pintype "passive"))
    )
    (net (code "729") (name "Net-(IC1111B-T2)") (class "Default")
      (node (ref "C1110") (pin "1") (pinfunction "1_1") (pintype "passive"))
      (node (ref "IC1111") (pin "14") (pinfunction "T2_14") (pintype "input"))
      (node (ref "R1145") (pin "1") (pinfunction "1_1") (pintype "passive"))
    )
    (net (code "730") (name "Net-(IC1201A-+IN)") (class "Default")
      (node (ref "C1201") (pin "1") (pinfunction "1_1") (pintype "passive"))
      (node (ref "IC1201") (pin "3") (pinfunction "+IN_3") (pintype "input"))
      (node (ref "R1205") (pin "1") (pinfunction "1_1") (pintype "passive"))
    )
    (net (code "731") (name "Net-(IC1201A--IN)") (class "Default")
      (node (ref "IC1201") (pin "2") (pinfunction "-IN_2") (pintype "input"))
      (node (ref "R1207") (pin "2") (pinfunction "2_2") (pintype "passive"))
    )
    (net (code "732") (name "Net-(IC1201A-OUT)") (class "Default")
      (node (ref "IC1201") (pin "1") (pinfunction "OUT_1") (pintype "output"))
      (node (ref "R1208") (pin "2") (pinfunction "2_2") (pintype "passive"))
    )
    (net (code "733") (name "Net-(IC1201B-+IN)") (class "Default")
      (node (ref "IC1201") (pin "5") (pinfunction "+IN_5") (pintype "input"))
      (node (ref "R1212") (pin "2") (pinfunction "2_2") (pintype "passive"))
      (node (ref "R1217") (pin "2") (pinfunction "2_2") (pintype "passive"))
    )
    (net (code "734") (name "Net-(IC1201B--IN)") (class "Default")
      (node (ref "IC1201") (pin "6") (pinfunction "-IN_6") (pintype "input"))
      (node (ref "R1213") (pin "1") (pinfunction "1_1") (pintype "passive"))
      (node (ref "R1214") (pin "2") (pinfunction "2_2") (pintype "passive"))
    )
    (net (code "735") (name "Net-(IC1201B-OUT)") (class "Default")
      (node (ref "IC1201") (pin "7") (pinfunction "OUT_7") (pintype "output"))
      (node (ref "R1216") (pin "1") (pinfunction "1_1") (pintype "passive"))
      (node (ref "R1217") (pin "1") (pinfunction "1_1") (pintype "passive"))
    )
    (net (code "736") (name "Net-(IC1205A-A)") (class "Default")
      (node (ref "IC1205") (pin "10") (pinfunction "A_10") (pintype "input"))
      (node (ref "IC1206") (pin "1") (pinfunction "D1_1") (pintype "passive"))
      (node (ref "R1211") (pin "1") (pinfunction "1_1") (pintype "passive"))
      (node (ref "X1201") (pin "4") (pinfunction "4_4") (pintype "passive"))
      (node (ref "X1203") (pin "2") (pinfunction "S_2") (pintype "passive"))
    )
    (net (code "737") (name "Net-(IC1205A-B)") (class "Default")
      (node (ref "IC1205") (pin "13") (pinfunction "B_13") (pintype "input"))
      (node (ref "IC1206") (pin "4") (pinfunction "D4_4") (pintype "passive"))
      (node (ref "R1210") (pin "1") (pinfunction "1_1") (pintype "passive"))
      (node (ref "X1201") (pin "3") (pinfunction "3_3") (pintype "passive"))
      (node (ref "X1203") (pin "3") (pinfunction "S_3") (pintype "passive"))
    )
    (net (code "738") (name "Net-(IC1205A-C)") (class "Default")
      (node (ref "IC1205") (pin "12") (pinfunction "C_12") (pintype "input"))
      (node (ref "IC1206") (pin "3") (pinfunction "D3_3") (pintype "passive"))
      (node (ref "R1209") (pin "1") (pinfunction "1_1") (pintype "passive"))
      (node (ref "X1201") (pin "2") (pinfunction "2_2") (pintype "passive"))
      (node (ref "X1203") (pin "4") (pinfunction "S_4") (pintype "passive"))
    )
    (net (code "739") (name "Net-(IC1205A-Q0)") (class "Default")
      (node (ref "IC1205") (pin "3") (pinfunction "Q0_3") (pintype "output"))
      (node (ref "IC1207") (pin "1") (pinfunction "I1_1") (pintype "input"))
      (node (ref "IC1207") (pin "2") (pinfunction "I2_2") (pintype "input"))
      (node (ref "Q1206") (pin "1") (pinfunction "G_1") (pintype "passive"))
    )
    (net (code "740") (name "Net-(IC1205A-Q1)") (class "Default")
      (node (ref "IC1205") (pin "14") (pinfunction "Q1_14") (pintype "output"))
      (node (ref "IC1207") (pin "6") (pinfunction "I6_6") (pintype "input"))
    )
    (net (code "741") (name "Net-(IC1205A-Q2)") (class "Default")
      (node (ref "IC1205") (pin "2") (pinfunction "Q2_2") (pintype "output"))
      (node (ref "IC1207") (pin "7") (pinfunction "I7_7") (pintype "input"))
    )
    (net (code "742") (name "Net-(IC1205A-Q3)") (class "Default")
      (node (ref "IC1205") (pin "15") (pinfunction "Q3_15") (pintype "output"))
      (node (ref "IC1207") (pin "5") (pinfunction "I5_5") (pintype "input"))
    )
    (net (code "743") (name "Net-(IC1205A-Q4)") (class "Default")
      (node (ref "IC1205") (pin "1") (pinfunction "Q4_1") (pintype "output"))
      (node (ref "IC1207") (pin "4") (pinfunction "I4_4") (pintype "input"))
    )
    (net (code "744") (name "Net-(IC1205A-Q5)") (class "Default")
      (node (ref "IC1205") (pin "6") (pinfunction "Q5_6") (pintype "output"))
      (node (ref "IC1207") (pin "3") (pinfunction "I3_3") (pintype "input"))
    )
    (net (code "745") (name "Net-(IC1207-O2)") (class "Default")
      (node (ref "IC1207") (pin "15") (pinfunction "O2_15") (pintype "open_collector"))
      (node (ref "R1228") (pin "1") (pinfunction "1_1") (pintype "passive"))
    )
    (net (code "746") (name "Net-(IC1208A-+IN)") (class "Default")
      (node (ref "IC1208") (pin "5") (pinfunction "+IN_5") (pintype "input"))
      (node (ref "R1231") (pin "1") (pinfunction "1_1") (pintype "passive"))
      (node (ref "R1232") (pin "2") (pinfunction "2_2") (pintype "passive"))
      (node (ref "R1233") (pin "2") (pinfunction "2_2") (pintype "passive"))
    )
    (net (code "747") (name "Net-(IC1208A--IN)") (class "Default")
      (node (ref "C1208") (pin "1") (pinfunction "1_1") (pintype "passive"))
      (node (ref "IC1208") (pin "4") (pinfunction "-IN_4") (pintype "input"))
      (node (ref "R1230") (pin "1") (pinfunction "1_1") (pintype "passive"))
    )
    (net (code "748") (name "Net-(IC1208B-+IN)") (class "Default")
      (node (ref "IC1208") (pin "7") (pinfunction "+IN_7") (pintype "input"))
      (node (ref "R1221") (pin "1") (pinfunction "1_1") (pintype "passive"))
      (node (ref "R1222") (pin "1") (pinfunction "1_1") (pintype "passive"))
    )
    (net (code "749") (name "Net-(IC1208B--IN)") (class "Default")
      (node (ref "IC1208") (pin "6") (pinfunction "-IN_6") (pintype "input"))
      (node (ref "IC1208") (pin "8") (pinfunction "-IN_8") (pintype "input"))
      (node (ref "R1220") (pin "1") (pinfunction "1_1") (pintype "passive"))
    )
    (net (code "750") (name "Net-(IC1208B-OUT)") (class "Default")
      (node (ref "IC1208") (pin "1") (pinfunction "OUT_1") (pintype "open_collector"))
      (node (ref "R1224") (pin "2") (pinfunction "2_2") (pintype "passive"))
      (node (ref "R1225") (pin "2") (pinfunction "2_2") (pintype "passive"))
    )
    (net (code "751") (name "Net-(IC1208C-+IN)") (class "Default")
      (node (ref "C1205") (pin "1") (pinfunction "1_1") (pintype "passive"))
      (node (ref "IC1208") (pin "9") (pinfunction "+IN_9") (pintype "input"))
      (node (ref "R1222") (pin "2") (pinfunction "2_2") (pintype "passive"))
      (node (ref "R1223") (pin "2") (pinfunction "2_2") (pintype "passive"))
    )
    (net (code "752") (name "Net-(IC1208C-OUT)") (class "Default")
      (node (ref "C1206") (pin "2") (pinfunction "2_2") (pintype "passive"))
      (node (ref "IC1208") (pin "14") (pinfunction "OUT_14") (pintype "open_collector"))
      (node (ref "R1226") (pin "2") (pinfunction "2_2") (pintype "passive"))
    )
    (net (code "753") (name "Net-(IC1209-ADJ)") (class "Default")
      (node (ref "IC1209") (pin "1") (pinfunction "ADJ_1") (pintype "input"))
      (node (ref "R1220") (pin "2") (pinfunction "2_2") (pintype "passive"))
      (node (ref "R1234") (pin "1") (pinfunction "1_1") (pintype "passive"))
      (node (ref "X1201") (pin "7") (pinfunction "7_7") (pintype "passive"))
    )
    (net (code "754") (name "Net-(IC1209-VI)") (class "Default")
      (node (ref "IC1209") (pin "3") (pinfunction "VI_3") (pintype "input"))
      (node (ref "Q1205") (pin "2") (pinfunction "C_2") (pintype "passive"))
    )
    (net (code "755") (name "Net-(IC1209-VO)") (class "Default")
      (node (ref "IC1209") (pin "2") (pinfunction "VO_2") (pintype "passive"))
      (node (ref "R1234") (pin "2") (pinfunction "2_2") (pintype "passive"))
    )
    (net (code "756") (name "Net-(IC1210-CV)") (class "Default")
      (node (ref "IC1210") (pin "5") (pinfunction "CV_5") (pintype "input"))
      (node (ref "R1244") (pin "2") (pinfunction "2_2") (pintype "passive"))
    )
    (net (code "757") (name "Net-(IC1210-Q)") (class "Default")
      (node (ref "IC1210") (pin "3") (pinfunction "Q_3") (pintype "output"))
      (node (ref "IC1211") (pin "12") (pinfunction "A_12") (pintype "input"))
      (node (ref "R1244") (pin "1") (pinfunction "1_1") (pintype "passive"))
    )
    (net (code "758") (name "Net-(IC1211B-B)") (class "Default")
      (node (ref "IC1211") (pin "11") (pinfunction "B_11") (pintype "input"))
      (node (ref "IC1211") (pin "9") (pinfunction "~{Q}_9") (pintype "output"))
      (node (ref "R1246") (pin "2") (pinfunction "2_2") (pintype "passive"))
    )
    (net (code "759") (name "Net-(IC1211B-T2)") (class "Default")
      (node (ref "C1210") (pin "1") (pinfunction "1_1") (pintype "passive"))
      (node (ref "IC1211") (pin "14") (pinfunction "T2_14") (pintype "input"))
      (node (ref "R1245") (pin "1") (pinfunction "1_1") (pintype "passive"))
    )
    (net (code "760") (name "Net-(JP101-Pad1)") (class "Default")
      (node (ref "JP101") (pin "1") (pinfunction "1_1") (pintype "passive"))
      (node (ref "R119") (pin "2") (pinfunction "2_2") (pintype "passive"))
    )
    (net (code "761") (name "Net-(JP104-Pad2)") (class "Default")
      (node (ref "JP104") (pin "2") (pinfunction "2_2") (pintype "passive"))
      (node (ref "R136") (pin "2") (pinfunction "2_2") (pintype "passive"))
      (node (ref "R137") (pin "2") (pinfunction "2_2") (pintype "passive"))
      (node (ref "SJ101") (pin "2") (pinfunction "2_2") (pintype "passive"))
    )
    (net (code "762") (name "Net-(JP105-Pad3)") (class "Default")
      (node (ref "JP105") (pin "3") (pinfunction "3_3") (pintype "passive"))
      (node (ref "R138") (pin "1") (pinfunction "1_1") (pintype "passive"))
      (node (ref "R139") (pin "1") (pinfunction "1_1") (pintype "passive"))
    )
    (net (code "763") (name "Net-(JP201-Pad1)") (class "Default")
      (node (ref "JP201") (pin "1") (pinfunction "1_1") (pintype "passive"))
      (node (ref "R219") (pin "2") (pinfunction "2_2") (pintype "passive"))
    )
    (net (code "764") (name "Net-(JP204-Pad2)") (class "Default")
      (node (ref "JP204") (pin "2") (pinfunction "2_2") (pintype "passive"))
      (node (ref "R236") (pin "2") (pinfunction "2_2") (pintype "passive"))
      (node (ref "R237") (pin "2") (pinfunction "2_2") (pintype "passive"))
      (node (ref "SJ201") (pin "2") (pinfunction "2_2") (pintype "passive"))
    )
    (net (code "765") (name "Net-(JP205-Pad3)") (class "Default")
      (node (ref "JP205") (pin "3") (pinfunction "3_3") (pintype "passive"))
      (node (ref "R238") (pin "1") (pinfunction "1_1") (pintype "passive"))
      (node (ref "R239") (pin "1") (pinfunction "1_1") (pintype "passive"))
    )
    (net (code "766") (name "Net-(JP301-Pad1)") (class "Default")
      (node (ref "JP301") (pin "1") (pinfunction "1_1") (pintype "passive"))
      (node (ref "R319") (pin "2") (pinfunction "2_2") (pintype "passive"))
    )
    (net (code "767") (name "Net-(JP304-Pad2)") (class "Default")
      (node (ref "JP304") (pin "2") (pinfunction "2_2") (pintype "passive"))
      (node (ref "R336") (pin "2") (pinfunction "2_2") (pintype "passive"))
      (node (ref "R337") (pin "2") (pinfunction "2_2") (pintype "passive"))
      (node (ref "SJ301") (pin "2") (pinfunction "2_2") (pintype "passive"))
    )
    (net (code "768") (name "Net-(JP305-Pad3)") (class "Default")
      (node (ref "JP305") (pin "3") (pinfunction "3_3") (pintype "passive"))
      (node (ref "R338") (pin "1") (pinfunction "1_1") (pintype "passive"))
      (node (ref "R339") (pin "1") (pinfunction "1_1") (pintype "passive"))
    )
    (net (code "769") (name "Net-(JP401-Pad1)") (class "Default")
      (node (ref "JP401") (pin "1") (pinfunction "1_1") (pintype "passive"))
      (node (ref "R419") (pin "2") (pinfunction "2_2") (pintype "passive"))
    )
    (net (code "770") (name "Net-(JP404-Pad2)") (class "Default")
      (node (ref "JP404") (pin "2") (pinfunction "2_2") (pintype "passive"))
      (node (ref "R436") (pin "2") (pinfunction "2_2") (pintype "passive"))
      (node (ref "R437") (pin "2") (pinfunction "2_2") (pintype "passive"))
      (node (ref "SJ401") (pin "2") (pinfunction "2_2") (pintype "passive"))
    )
    (net (code "771") (name "Net-(JP405-Pad3)") (class "Default")
      (node (ref "JP405") (pin "3") (pinfunction "3_3") (pintype "passive"))
      (node (ref "R438") (pin "1") (pinfunction "1_1") (pintype "passive"))
      (node (ref "R439") (pin "1") (pinfunction "1_1") (pintype "passive"))
    )
    (net (code "772") (name "Net-(JP501-Pad1)") (class "Default")
      (node (ref "JP501") (pin "1") (pinfunction "1_1") (pintype "passive"))
      (node (ref "R519") (pin "2") (pinfunction "2_2") (pintype "passive"))
    )
    (net (code "773") (name "Net-(JP504-Pad2)") (class "Default")
      (node (ref "JP504") (pin "2") (pinfunction "2_2") (pintype "passive"))
      (node (ref "R536") (pin "2") (pinfunction "2_2") (pintype "passive"))
      (node (ref "R537") (pin "2") (pinfunction "2_2") (pintype "passive"))
      (node (ref "SJ501") (pin "2") (pinfunction "2_2") (pintype "passive"))
    )
    (net (code "774") (name "Net-(JP505-Pad3)") (class "Default")
      (node (ref "JP505") (pin "3") (pinfunction "3_3") (pintype "passive"))
      (node (ref "R538") (pin "1") (pinfunction "1_1") (pintype "passive"))
      (node (ref "R539") (pin "1") (pinfunction "1_1") (pintype "passive"))
    )
    (net (code "775") (name "Net-(JP601-Pad1)") (class "Default")
      (node (ref "JP601") (pin "1") (pinfunction "1_1") (pintype "passive"))
      (node (ref "R619") (pin "2") (pinfunction "2_2") (pintype "passive"))
    )
    (net (code "776") (name "Net-(JP604-Pad2)") (class "Default")
      (node (ref "JP604") (pin "2") (pinfunction "2_2") (pintype "passive"))
      (node (ref "R636") (pin "2") (pinfunction "2_2") (pintype "passive"))
      (node (ref "R637") (pin "2") (pinfunction "2_2") (pintype "passive"))
      (node (ref "SJ601") (pin "2") (pinfunction "2_2") (pintype "passive"))
    )
    (net (code "777") (name "Net-(JP605-Pad3)") (class "Default")
      (node (ref "JP605") (pin "3") (pinfunction "3_3") (pintype "passive"))
      (node (ref "R638") (pin "1") (pinfunction "1_1") (pintype "passive"))
      (node (ref "R639") (pin "1") (pinfunction "1_1") (pintype "passive"))
    )
    (net (code "778") (name "Net-(JP701-Pad1)") (class "Default")
      (node (ref "JP701") (pin "1") (pinfunction "1_1") (pintype "passive"))
      (node (ref "R719") (pin "2") (pinfunction "2_2") (pintype "passive"))
    )
    (net (code "779") (name "Net-(JP704-Pad2)") (class "Default")
      (node (ref "JP704") (pin "2") (pinfunction "2_2") (pintype "passive"))
      (node (ref "R736") (pin "2") (pinfunction "2_2") (pintype "passive"))
      (node (ref "R737") (pin "2") (pinfunction "2_2") (pintype "passive"))
      (node (ref "SJ701") (pin "2") (pinfunction "2_2") (pintype "passive"))
    )
    (net (code "780") (name "Net-(JP705-Pad3)") (class "Default")
      (node (ref "JP705") (pin "3") (pinfunction "3_3") (pintype "passive"))
      (node (ref "R738") (pin "1") (pinfunction "1_1") (pintype "passive"))
      (node (ref "R739") (pin "1") (pinfunction "1_1") (pintype "passive"))
    )
    (net (code "781") (name "Net-(JP801-Pad1)") (class "Default")
      (node (ref "JP801") (pin "1") (pinfunction "1_1") (pintype "passive"))
      (node (ref "R819") (pin "2") (pinfunction "2_2") (pintype "passive"))
    )
    (net (code "782") (name "Net-(JP804-Pad2)") (class "Default")
      (node (ref "JP804") (pin "2") (pinfunction "2_2") (pintype "passive"))
      (node (ref "R836") (pin "2") (pinfunction "2_2") (pintype "passive"))
      (node (ref "R837") (pin "2") (pinfunction "2_2") (pintype "passive"))
      (node (ref "SJ801") (pin "2") (pinfunction "2_2") (pintype "passive"))
    )
    (net (code "783") (name "Net-(JP805-Pad3)") (class "Default")
      (node (ref "JP805") (pin "3") (pinfunction "3_3") (pintype "passive"))
      (node (ref "R838") (pin "1") (pinfunction "1_1") (pintype "passive"))
      (node (ref "R839") (pin "1") (pinfunction "1_1") (pintype "passive"))
    )
    (net (code "784") (name "Net-(JP901-Pad1)") (class "Default")
      (node (ref "JP901") (pin "1") (pinfunction "1_1") (pintype "passive"))
      (node (ref "R919") (pin "2") (pinfunction "2_2") (pintype "passive"))
    )
    (net (code "785") (name "Net-(JP904-Pad2)") (class "Default")
      (node (ref "JP904") (pin "2") (pinfunction "2_2") (pintype "passive"))
      (node (ref "R936") (pin "2") (pinfunction "2_2") (pintype "passive"))
      (node (ref "R937") (pin "2") (pinfunction "2_2") (pintype "passive"))
      (node (ref "SJ901") (pin "2") (pinfunction "2_2") (pintype "passive"))
    )
    (net (code "786") (name "Net-(JP905-Pad3)") (class "Default")
      (node (ref "JP905") (pin "3") (pinfunction "3_3") (pintype "passive"))
      (node (ref "R938") (pin "1") (pinfunction "1_1") (pintype "passive"))
      (node (ref "R939") (pin "1") (pinfunction "1_1") (pintype "passive"))
    )
    (net (code "787") (name "Net-(JP1001-Pad1)") (class "Default")
      (node (ref "JP1001") (pin "1") (pinfunction "1_1") (pintype "passive"))
      (node (ref "R1019") (pin "2") (pinfunction "2_2") (pintype "passive"))
    )
    (net (code "788") (name "Net-(JP1004-Pad2)") (class "Default")
      (node (ref "JP1004") (pin "2") (pinfunction "2_2") (pintype "passive"))
      (node (ref "R1036") (pin "2") (pinfunction "2_2") (pintype "passive"))
      (node (ref "R1037") (pin "2") (pinfunction "2_2") (pintype "passive"))
      (node (ref "SJ1001") (pin "2") (pinfunction "2_2") (pintype "passive"))
    )
    (net (code "789") (name "Net-(JP1005-Pad3)") (class "Default")
      (node (ref "JP1005") (pin "3") (pinfunction "3_3") (pintype "passive"))
      (node (ref "R1038") (pin "1") (pinfunction "1_1") (pintype "passive"))
      (node (ref "R1039") (pin "1") (pinfunction "1_1") (pintype "passive"))
    )
    (net (code "790") (name "Net-(JP1101-Pad1)") (class "Default")
      (node (ref "JP1101") (pin "1") (pinfunction "1_1") (pintype "passive"))
      (node (ref "R1119") (pin "2") (pinfunction "2_2") (pintype "passive"))
    )
    (net (code "791") (name "Net-(JP1104-Pad2)") (class "Default")
      (node (ref "JP1104") (pin "2") (pinfunction "2_2") (pintype "passive"))
      (node (ref "R1136") (pin "2") (pinfunction "2_2") (pintype "passive"))
      (node (ref "R1137") (pin "2") (pinfunction "2_2") (pintype "passive"))
      (node (ref "SJ1101") (pin "2") (pinfunction "2_2") (pintype "passive"))
    )
    (net (code "792") (name "Net-(JP1105-Pad3)") (class "Default")
      (node (ref "JP1105") (pin "3") (pinfunction "3_3") (pintype "passive"))
      (node (ref "R1138") (pin "1") (pinfunction "1_1") (pintype "passive"))
      (node (ref "R1139") (pin "1") (pinfunction "1_1") (pintype "passive"))
    )
    (net (code "793") (name "Net-(JP1201-Pad1)") (class "Default")
      (node (ref "JP1201") (pin "1") (pinfunction "1_1") (pintype "passive"))
      (node (ref "R1219") (pin "2") (pinfunction "2_2") (pintype "passive"))
    )
    (net (code "794") (name "Net-(JP1204-Pad2)") (class "Default")
      (node (ref "JP1204") (pin "2") (pinfunction "2_2") (pintype "passive"))
      (node (ref "R1236") (pin "2") (pinfunction "2_2") (pintype "passive"))
      (node (ref "R1237") (pin "2") (pinfunction "2_2") (pintype "passive"))
      (node (ref "SJ1201") (pin "2") (pinfunction "2_2") (pintype "passive"))
    )
    (net (code "795") (name "Net-(JP1205-Pad3)") (class "Default")
      (node (ref "JP1205") (pin "3") (pinfunction "3_3") (pintype "passive"))
      (node (ref "R1238") (pin "1") (pinfunction "1_1") (pintype "passive"))
      (node (ref "R1239") (pin "1") (pinfunction "1_1") (pintype "passive"))
    )
    (net (code "796") (name "Net-(LED101-C)") (class "Default")
      (node (ref "LED101") (pin "K") (pinfunction "C_K") (pintype "passive"))
      (node (ref "R143") (pin "1") (pinfunction "1_1") (pintype "passive"))
    )
    (net (code "797") (name "Net-(LED102-PadA)") (class "Default")
      (node (ref "LED102") (pin "A") (pinfunction "A_A") (pintype "passive"))
      (node (ref "LED103") (pin "A") (pinfunction "A_A") (pintype "passive"))
      (node (ref "LED104") (pin "A") (pinfunction "A_A") (pintype "passive"))
      (node (ref "LED105") (pin "A") (pinfunction "A_A") (pintype "passive"))
      (node (ref "LED106") (pin "A") (pinfunction "A_A") (pintype "passive"))
      (node (ref "R142") (pin "1") (pinfunction "1_1") (pintype "passive"))
    )
    (net (code "798") (name "Net-(LED201-C)") (class "Default")
      (node (ref "LED201") (pin "K") (pinfunction "C_K") (pintype "passive"))
      (node (ref "R243") (pin "1") (pinfunction "1_1") (pintype "passive"))
    )
    (net (code "799") (name "Net-(LED202-PadA)") (class "Default")
      (node (ref "LED202") (pin "A") (pinfunction "A_A") (pintype "passive"))
      (node (ref "LED203") (pin "A") (pinfunction "A_A") (pintype "passive"))
      (node (ref "LED204") (pin "A") (pinfunction "A_A") (pintype "passive"))
      (node (ref "LED205") (pin "A") (pinfunction "A_A") (pintype "passive"))
      (node (ref "LED206") (pin "A") (pinfunction "A_A") (pintype "passive"))
      (node (ref "R242") (pin "1") (pinfunction "1_1") (pintype "passive"))
    )
    (net (code "800") (name "Net-(LED301-C)") (class "Default")
      (node (ref "LED301") (pin "K") (pinfunction "C_K") (pintype "passive"))
      (node (ref "R343") (pin "1") (pinfunction "1_1") (pintype "passive"))
    )
    (net (code "801") (name "Net-(LED302-PadA)") (class "Default")
      (node (ref "LED302") (pin "A") (pinfunction "A_A") (pintype "passive"))
      (node (ref "LED303") (pin "A") (pinfunction "A_A") (pintype "passive"))
      (node (ref "LED304") (pin "A") (pinfunction "A_A") (pintype "passive"))
      (node (ref "LED305") (pin "A") (pinfunction "A_A") (pintype "passive"))
      (node (ref "LED306") (pin "A") (pinfunction "A_A") (pintype "passive"))
      (node (ref "R342") (pin "1") (pinfunction "1_1") (pintype "passive"))
    )
    (net (code "802") (name "Net-(LED401-C)") (class "Default")
      (node (ref "LED401") (pin "K") (pinfunction "C_K") (pintype "passive"))
      (node (ref "R443") (pin "1") (pinfunction "1_1") (pintype "passive"))
    )
    (net (code "803") (name "Net-(LED402-PadA)") (class "Default")
      (node (ref "LED402") (pin "A") (pinfunction "A_A") (pintype "passive"))
      (node (ref "LED403") (pin "A") (pinfunction "A_A") (pintype "passive"))
      (node (ref "LED404") (pin "A") (pinfunction "A_A") (pintype "passive"))
      (node (ref "LED405") (pin "A") (pinfunction "A_A") (pintype "passive"))
      (node (ref "LED406") (pin "A") (pinfunction "A_A") (pintype "passive"))
      (node (ref "R442") (pin "1") (pinfunction "1_1") (pintype "passive"))
    )
    (net (code "804") (name "Net-(LED501-C)") (class "Default")
      (node (ref "LED501") (pin "K") (pinfunction "C_K") (pintype "passive"))
      (node (ref "R543") (pin "1") (pinfunction "1_1") (pintype "passive"))
    )
    (net (code "805") (name "Net-(LED502-PadA)") (class "Default")
      (node (ref "LED502") (pin "A") (pinfunction "A_A") (pintype "passive"))
      (node (ref "LED503") (pin "A") (pinfunction "A_A") (pintype "passive"))
      (node (ref "LED504") (pin "A") (pinfunction "A_A") (pintype "passive"))
      (node (ref "LED505") (pin "A") (pinfunction "A_A") (pintype "passive"))
      (node (ref "LED506") (pin "A") (pinfunction "A_A") (pintype "passive"))
      (node (ref "R542") (pin "1") (pinfunction "1_1") (pintype "passive"))
    )
    (net (code "806") (name "Net-(LED601-C)") (class "Default")
      (node (ref "LED601") (pin "K") (pinfunction "C_K") (pintype "passive"))
      (node (ref "R643") (pin "1") (pinfunction "1_1") (pintype "passive"))
    )
    (net (code "807") (name "Net-(LED602-PadA)") (class "Default")
      (node (ref "LED602") (pin "A") (pinfunction "A_A") (pintype "passive"))
      (node (ref "LED603") (pin "A") (pinfunction "A_A") (pintype "passive"))
      (node (ref "LED604") (pin "A") (pinfunction "A_A") (pintype "passive"))
      (node (ref "LED605") (pin "A") (pinfunction "A_A") (pintype "passive"))
      (node (ref "LED606") (pin "A") (pinfunction "A_A") (pintype "passive"))
      (node (ref "R642") (pin "1") (pinfunction "1_1") (pintype "passive"))
    )
    (net (code "808") (name "Net-(LED701-C)") (class "Default")
      (node (ref "LED701") (pin "K") (pinfunction "C_K") (pintype "passive"))
      (node (ref "R743") (pin "1") (pinfunction "1_1") (pintype "passive"))
    )
    (net (code "809") (name "Net-(LED702-PadA)") (class "Default")
      (node (ref "LED702") (pin "A") (pinfunction "A_A") (pintype "passive"))
      (node (ref "LED703") (pin "A") (pinfunction "A_A") (pintype "passive"))
      (node (ref "LED704") (pin "A") (pinfunction "A_A") (pintype "passive"))
      (node (ref "LED705") (pin "A") (pinfunction "A_A") (pintype "passive"))
      (node (ref "LED706") (pin "A") (pinfunction "A_A") (pintype "passive"))
      (node (ref "R742") (pin "1") (pinfunction "1_1") (pintype "passive"))
    )
    (net (code "810") (name "Net-(LED801-C)") (class "Default")
      (node (ref "LED801") (pin "K") (pinfunction "C_K") (pintype "passive"))
      (node (ref "R843") (pin "1") (pinfunction "1_1") (pintype "passive"))
    )
    (net (code "811") (name "Net-(LED802-PadA)") (class "Default")
      (node (ref "LED802") (pin "A") (pinfunction "A_A") (pintype "passive"))
      (node (ref "LED803") (pin "A") (pinfunction "A_A") (pintype "passive"))
      (node (ref "LED804") (pin "A") (pinfunction "A_A") (pintype "passive"))
      (node (ref "LED805") (pin "A") (pinfunction "A_A") (pintype "passive"))
      (node (ref "LED806") (pin "A") (pinfunction "A_A") (pintype "passive"))
      (node (ref "R842") (pin "1") (pinfunction "1_1") (pintype "passive"))
    )
    (net (code "812") (name "Net-(LED901-C)") (class "Default")
      (node (ref "LED901") (pin "K") (pinfunction "C_K") (pintype "passive"))
      (node (ref "R943") (pin "1") (pinfunction "1_1") (pintype "passive"))
    )
    (net (code "813") (name "Net-(LED902-PadA)") (class "Default")
      (node (ref "LED902") (pin "A") (pinfunction "A_A") (pintype "passive"))
      (node (ref "LED903") (pin "A") (pinfunction "A_A") (pintype "passive"))
      (node (ref "LED904") (pin "A") (pinfunction "A_A") (pintype "passive"))
      (node (ref "LED905") (pin "A") (pinfunction "A_A") (pintype "passive"))
      (node (ref "LED906") (pin "A") (pinfunction "A_A") (pintype "passive"))
      (node (ref "R942") (pin "1") (pinfunction "1_1") (pintype "passive"))
    )
    (net (code "814") (name "Net-(LED1001-C)") (class "Default")
      (node (ref "LED1001") (pin "K") (pinfunction "C_K") (pintype "passive"))
      (node (ref "R1043") (pin "1") (pinfunction "1_1") (pintype "passive"))
    )
    (net (code "815") (name "Net-(LED1002-PadA)") (class "Default")
      (node (ref "LED1002") (pin "A") (pinfunction "A_A") (pintype "passive"))
      (node (ref "LED1003") (pin "A") (pinfunction "A_A") (pintype "passive"))
      (node (ref "LED1004") (pin "A") (pinfunction "A_A") (pintype "passive"))
      (node (ref "LED1005") (pin "A") (pinfunction "A_A") (pintype "passive"))
      (node (ref "LED1006") (pin "A") (pinfunction "A_A") (pintype "passive"))
      (node (ref "R1042") (pin "1") (pinfunction "1_1") (pintype "passive"))
    )
    (net (code "816") (name "Net-(LED1101-C)") (class "Default")
      (node (ref "LED1101") (pin "K") (pinfunction "C_K") (pintype "passive"))
      (node (ref "R1143") (pin "1") (pinfunction "1_1") (pintype "passive"))
    )
    (net (code "817") (name "Net-(LED1102-PadA)") (class "Default")
      (node (ref "LED1102") (pin "A") (pinfunction "A_A") (pintype "passive"))
      (node (ref "LED1103") (pin "A") (pinfunction "A_A") (pintype "passive"))
      (node (ref "LED1104") (pin "A") (pinfunction "A_A") (pintype "passive"))
      (node (ref "LED1105") (pin "A") (pinfunction "A_A") (pintype "passive"))
      (node (ref "LED1106") (pin "A") (pinfunction "A_A") (pintype "passive"))
      (node (ref "R1142") (pin "1") (pinfunction "1_1") (pintype "passive"))
    )
    (net (code "818") (name "Net-(LED1201-C)") (class "Default")
      (node (ref "LED1201") (pin "K") (pinfunction "C_K") (pintype "passive"))
      (node (ref "R1243") (pin "1") (pinfunction "1_1") (pintype "passive"))
    )
    (net (code "819") (name "Net-(LED1202-PadA)") (class "Default")
      (node (ref "LED1202") (pin "A") (pinfunction "A_A") (pintype "passive"))
      (node (ref "LED1203") (pin "A") (pinfunction "A_A") (pintype "passive"))
      (node (ref "LED1204") (pin "A") (pinfunction "A_A") (pintype "passive"))
      (node (ref "LED1205") (pin "A") (pinfunction "A_A") (pintype "passive"))
      (node (ref "LED1206") (pin "A") (pinfunction "A_A") (pintype "passive"))
      (node (ref "R1242") (pin "1") (pinfunction "1_1") (pintype "passive"))
    )
    (net (code "820") (name "Net-(Q101-B)") (class "Default")
      (node (ref "Q101") (pin "1") (pinfunction "B_1") (pintype "passive"))
      (node (ref "Q102") (pin "1") (pinfunction "B_1") (pintype "passive"))
      (node (ref "Q102") (pin "2") (pinfunction "C_2") (pintype "passive"))
      (node (ref "R101") (pin "1") (pinfunction "1_1") (pintype "passive"))
      (node (ref "R103") (pin "1") (pinfunction "1_1") (pintype "passive"))
      (node (ref "R104") (pin "1") (pinfunction "1_1") (pintype "passive"))
      (node (ref "X102") (pin "2") (pinfunction "S_2") (pintype "passive"))
    )
    (net (code "821") (name "Net-(Q101-E)") (class "Default")
      (node (ref "Q101") (pin "3") (pinfunction "E_3") (pintype "passive"))
      (node (ref "R102") (pin "2") (pinfunction "2_2") (pintype "passive"))
    )
    (net (code "822") (name "Net-(Q102-E)") (class "Default")
      (node (ref "Q102") (pin "3") (pinfunction "E_3") (pintype "passive"))
      (node (ref "R106") (pin "2") (pinfunction "2_2") (pintype "passive"))
    )
    (net (code "823") (name "Net-(Q103-B)") (class "Default")
      (node (ref "Q103") (pin "1") (pinfunction "B_1") (pintype "passive"))
      (node (ref "R116") (pin "2") (pinfunction "2_2") (pintype "passive"))
    )
    (net (code "824") (name "Net-(Q103-C)") (class "Default")
      (node (ref "Q103") (pin "2") (pinfunction "C_2") (pintype "passive"))
      (node (ref "R115") (pin "2") (pinfunction "2_2") (pintype "passive"))
      (node (ref "R118") (pin "1") (pinfunction "1_1") (pintype "passive"))
    )
    (net (code "825") (name "Net-(Q104-B)") (class "Default")
      (node (ref "Q104") (pin "1") (pinfunction "B_1") (pintype "passive"))
      (node (ref "R128") (pin "2") (pinfunction "2_2") (pintype "passive"))
    )
    (net (code "826") (name "Net-(Q105-B)") (class "Default")
      (node (ref "Q105") (pin "1") (pinfunction "B_1") (pintype "passive"))
      (node (ref "R126") (pin "1") (pinfunction "1_1") (pintype "passive"))
    )
    (net (code "827") (name "Net-(Q107-D)") (class "Default")
      (node (ref "Q107") (pin "3") (pinfunction "D_3") (pintype "passive"))
      (node (ref "R138") (pin "2") (pinfunction "2_2") (pintype "passive"))
    )
    (net (code "828") (name "Net-(Q201-B)") (class "Default")
      (node (ref "Q201") (pin "1") (pinfunction "B_1") (pintype "passive"))
      (node (ref "Q202") (pin "1") (pinfunction "B_1") (pintype "passive"))
      (node (ref "Q202") (pin "2") (pinfunction "C_2") (pintype "passive"))
      (node (ref "R201") (pin "1") (pinfunction "1_1") (pintype "passive"))
      (node (ref "R203") (pin "1") (pinfunction "1_1") (pintype "passive"))
      (node (ref "R204") (pin "1") (pinfunction "1_1") (pintype "passive"))
      (node (ref "X202") (pin "2") (pinfunction "S_2") (pintype "passive"))
    )
    (net (code "829") (name "Net-(Q201-E)") (class "Default")
      (node (ref "Q201") (pin "3") (pinfunction "E_3") (pintype "passive"))
      (node (ref "R202") (pin "2") (pinfunction "2_2") (pintype "passive"))
    )
    (net (code "830") (name "Net-(Q202-E)") (class "Default")
      (node (ref "Q202") (pin "3") (pinfunction "E_3") (pintype "passive"))
      (node (ref "R206") (pin "2") (pinfunction "2_2") (pintype "passive"))
    )
    (net (code "831") (name "Net-(Q203-B)") (class "Default")
      (node (ref "Q203") (pin "1") (pinfunction "B_1") (pintype "passive"))
      (node (ref "R216") (pin "2") (pinfunction "2_2") (pintype "passive"))
    )
    (net (code "832") (name "Net-(Q203-C)") (class "Default")
      (node (ref "Q203") (pin "2") (pinfunction "C_2") (pintype "passive"))
      (node (ref "R215") (pin "2") (pinfunction "2_2") (pintype "passive"))
      (node (ref "R218") (pin "1") (pinfunction "1_1") (pintype "passive"))
    )
    (net (code "833") (name "Net-(Q204-B)") (class "Default")
      (node (ref "Q204") (pin "1") (pinfunction "B_1") (pintype "passive"))
      (node (ref "R228") (pin "2") (pinfunction "2_2") (pintype "passive"))
    )
    (net (code "834") (name "Net-(Q205-B)") (class "Default")
      (node (ref "Q205") (pin "1") (pinfunction "B_1") (pintype "passive"))
      (node (ref "R226") (pin "1") (pinfunction "1_1") (pintype "passive"))
    )
    (net (code "835") (name "Net-(Q207-D)") (class "Default")
      (node (ref "Q207") (pin "3") (pinfunction "D_3") (pintype "passive"))
      (node (ref "R238") (pin "2") (pinfunction "2_2") (pintype "passive"))
    )
    (net (code "836") (name "Net-(Q301-B)") (class "Default")
      (node (ref "Q301") (pin "1") (pinfunction "B_1") (pintype "passive"))
      (node (ref "Q302") (pin "1") (pinfunction "B_1") (pintype "passive"))
      (node (ref "Q302") (pin "2") (pinfunction "C_2") (pintype "passive"))
      (node (ref "R301") (pin "1") (pinfunction "1_1") (pintype "passive"))
      (node (ref "R303") (pin "1") (pinfunction "1_1") (pintype "passive"))
      (node (ref "R304") (pin "1") (pinfunction "1_1") (pintype "passive"))
      (node (ref "X302") (pin "2") (pinfunction "S_2") (pintype "passive"))
    )
    (net (code "837") (name "Net-(Q301-E)") (class "Default")
      (node (ref "Q301") (pin "3") (pinfunction "E_3") (pintype "passive"))
      (node (ref "R302") (pin "2") (pinfunction "2_2") (pintype "passive"))
    )
    (net (code "838") (name "Net-(Q302-E)") (class "Default")
      (node (ref "Q302") (pin "3") (pinfunction "E_3") (pintype "passive"))
      (node (ref "R306") (pin "2") (pinfunction "2_2") (pintype "passive"))
    )
    (net (code "839") (name "Net-(Q303-B)") (class "Default")
      (node (ref "Q303") (pin "1") (pinfunction "B_1") (pintype "passive"))
      (node (ref "R316") (pin "2") (pinfunction "2_2") (pintype "passive"))
    )
    (net (code "840") (name "Net-(Q303-C)") (class "Default")
      (node (ref "Q303") (pin "2") (pinfunction "C_2") (pintype "passive"))
      (node (ref "R315") (pin "2") (pinfunction "2_2") (pintype "passive"))
      (node (ref "R318") (pin "1") (pinfunction "1_1") (pintype "passive"))
    )
    (net (code "841") (name "Net-(Q304-B)") (class "Default")
      (node (ref "Q304") (pin "1") (pinfunction "B_1") (pintype "passive"))
      (node (ref "R328") (pin "2") (pinfunction "2_2") (pintype "passive"))
    )
    (net (code "842") (name "Net-(Q305-B)") (class "Default")
      (node (ref "Q305") (pin "1") (pinfunction "B_1") (pintype "passive"))
      (node (ref "R326") (pin "1") (pinfunction "1_1") (pintype "passive"))
    )
    (net (code "843") (name "Net-(Q307-D)") (class "Default")
      (node (ref "Q307") (pin "3") (pinfunction "D_3") (pintype "passive"))
      (node (ref "R338") (pin "2") (pinfunction "2_2") (pintype "passive"))
    )
    (net (code "844") (name "Net-(Q401-B)") (class "Default")
      (node (ref "Q401") (pin "1") (pinfunction "B_1") (pintype "passive"))
      (node (ref "Q402") (pin "1") (pinfunction "B_1") (pintype "passive"))
      (node (ref "Q402") (pin "2") (pinfunction "C_2") (pintype "passive"))
      (node (ref "R401") (pin "1") (pinfunction "1_1") (pintype "passive"))
      (node (ref "R403") (pin "1") (pinfunction "1_1") (pintype "passive"))
      (node (ref "R404") (pin "1") (pinfunction "1_1") (pintype "passive"))
      (node (ref "X402") (pin "2") (pinfunction "S_2") (pintype "passive"))
    )
    (net (code "845") (name "Net-(Q401-E)") (class "Default")
      (node (ref "Q401") (pin "3") (pinfunction "E_3") (pintype "passive"))
      (node (ref "R402") (pin "2") (pinfunction "2_2") (pintype "passive"))
    )
    (net (code "846") (name "Net-(Q402-E)") (class "Default")
      (node (ref "Q402") (pin "3") (pinfunction "E_3") (pintype "passive"))
      (node (ref "R406") (pin "2") (pinfunction "2_2") (pintype "passive"))
    )
    (net (code "847") (name "Net-(Q403-B)") (class "Default")
      (node (ref "Q403") (pin "1") (pinfunction "B_1") (pintype "passive"))
      (node (ref "R416") (pin "2") (pinfunction "2_2") (pintype "passive"))
    )
    (net (code "848") (name "Net-(Q403-C)") (class "Default")
      (node (ref "Q403") (pin "2") (pinfunction "C_2") (pintype "passive"))
      (node (ref "R415") (pin "2") (pinfunction "2_2") (pintype "passive"))
      (node (ref "R418") (pin "1") (pinfunction "1_1") (pintype "passive"))
    )
    (net (code "849") (name "Net-(Q404-B)") (class "Default")
      (node (ref "Q404") (pin "1") (pinfunction "B_1") (pintype "passive"))
      (node (ref "R428") (pin "2") (pinfunction "2_2") (pintype "passive"))
    )
    (net (code "850") (name "Net-(Q405-B)") (class "Default")
      (node (ref "Q405") (pin "1") (pinfunction "B_1") (pintype "passive"))
      (node (ref "R426") (pin "1") (pinfunction "1_1") (pintype "passive"))
    )
    (net (code "851") (name "Net-(Q407-D)") (class "Default")
      (node (ref "Q407") (pin "3") (pinfunction "D_3") (pintype "passive"))
      (node (ref "R438") (pin "2") (pinfunction "2_2") (pintype "passive"))
    )
    (net (code "852") (name "Net-(Q501-B)") (class "Default")
      (node (ref "Q501") (pin "1") (pinfunction "B_1") (pintype "passive"))
      (node (ref "Q502") (pin "1") (pinfunction "B_1") (pintype "passive"))
      (node (ref "Q502") (pin "2") (pinfunction "C_2") (pintype "passive"))
      (node (ref "R501") (pin "1") (pinfunction "1_1") (pintype "passive"))
      (node (ref "R503") (pin "1") (pinfunction "1_1") (pintype "passive"))
      (node (ref "R504") (pin "1") (pinfunction "1_1") (pintype "passive"))
      (node (ref "X502") (pin "2") (pinfunction "S_2") (pintype "passive"))
    )
    (net (code "853") (name "Net-(Q501-E)") (class "Default")
      (node (ref "Q501") (pin "3") (pinfunction "E_3") (pintype "passive"))
      (node (ref "R502") (pin "2") (pinfunction "2_2") (pintype "passive"))
    )
    (net (code "854") (name "Net-(Q502-E)") (class "Default")
      (node (ref "Q502") (pin "3") (pinfunction "E_3") (pintype "passive"))
      (node (ref "R506") (pin "2") (pinfunction "2_2") (pintype "passive"))
    )
    (net (code "855") (name "Net-(Q503-B)") (class "Default")
      (node (ref "Q503") (pin "1") (pinfunction "B_1") (pintype "passive"))
      (node (ref "R516") (pin "2") (pinfunction "2_2") (pintype "passive"))
    )
    (net (code "856") (name "Net-(Q503-C)") (class "Default")
      (node (ref "Q503") (pin "2") (pinfunction "C_2") (pintype "passive"))
      (node (ref "R515") (pin "2") (pinfunction "2_2") (pintype "passive"))
      (node (ref "R518") (pin "1") (pinfunction "1_1") (pintype "passive"))
    )
    (net (code "857") (name "Net-(Q504-B)") (class "Default")
      (node (ref "Q504") (pin "1") (pinfunction "B_1") (pintype "passive"))
      (node (ref "R528") (pin "2") (pinfunction "2_2") (pintype "passive"))
    )
    (net (code "858") (name "Net-(Q505-B)") (class "Default")
      (node (ref "Q505") (pin "1") (pinfunction "B_1") (pintype "passive"))
      (node (ref "R526") (pin "1") (pinfunction "1_1") (pintype "passive"))
    )
    (net (code "859") (name "Net-(Q507-D)") (class "Default")
      (node (ref "Q507") (pin "3") (pinfunction "D_3") (pintype "passive"))
      (node (ref "R538") (pin "2") (pinfunction "2_2") (pintype "passive"))
    )
    (net (code "860") (name "Net-(Q601-B)") (class "Default")
      (node (ref "Q601") (pin "1") (pinfunction "B_1") (pintype "passive"))
      (node (ref "Q602") (pin "1") (pinfunction "B_1") (pintype "passive"))
      (node (ref "Q602") (pin "2") (pinfunction "C_2") (pintype "passive"))
      (node (ref "R601") (pin "1") (pinfunction "1_1") (pintype "passive"))
      (node (ref "R603") (pin "1") (pinfunction "1_1") (pintype "passive"))
      (node (ref "R604") (pin "1") (pinfunction "1_1") (pintype "passive"))
      (node (ref "X602") (pin "2") (pinfunction "S_2") (pintype "passive"))
    )
    (net (code "861") (name "Net-(Q601-E)") (class "Default")
      (node (ref "Q601") (pin "3") (pinfunction "E_3") (pintype "passive"))
      (node (ref "R602") (pin "2") (pinfunction "2_2") (pintype "passive"))
    )
    (net (code "862") (name "Net-(Q602-E)") (class "Default")
      (node (ref "Q602") (pin "3") (pinfunction "E_3") (pintype "passive"))
      (node (ref "R606") (pin "2") (pinfunction "2_2") (pintype "passive"))
    )
    (net (code "863") (name "Net-(Q603-B)") (class "Default")
      (node (ref "Q603") (pin "1") (pinfunction "B_1") (pintype "passive"))
      (node (ref "R616") (pin "2") (pinfunction "2_2") (pintype "passive"))
    )
    (net (code "864") (name "Net-(Q603-C)") (class "Default")
      (node (ref "Q603") (pin "2") (pinfunction "C_2") (pintype "passive"))
      (node (ref "R615") (pin "2") (pinfunction "2_2") (pintype "passive"))
      (node (ref "R618") (pin "1") (pinfunction "1_1") (pintype "passive"))
    )
    (net (code "865") (name "Net-(Q604-B)") (class "Default")
      (node (ref "Q604") (pin "1") (pinfunction "B_1") (pintype "passive"))
      (node (ref "R628") (pin "2") (pinfunction "2_2") (pintype "passive"))
    )
    (net (code "866") (name "Net-(Q605-B)") (class "Default")
      (node (ref "Q605") (pin "1") (pinfunction "B_1") (pintype "passive"))
      (node (ref "R626") (pin "1") (pinfunction "1_1") (pintype "passive"))
    )
    (net (code "867") (name "Net-(Q607-D)") (class "Default")
      (node (ref "Q607") (pin "3") (pinfunction "D_3") (pintype "passive"))
      (node (ref "R638") (pin "2") (pinfunction "2_2") (pintype "passive"))
    )
    (net (code "868") (name "Net-(Q701-B)") (class "Default")
      (node (ref "Q701") (pin "1") (pinfunction "B_1") (pintype "passive"))
      (node (ref "Q702") (pin "1") (pinfunction "B_1") (pintype "passive"))
      (node (ref "Q702") (pin "2") (pinfunction "C_2") (pintype "passive"))
      (node (ref "R701") (pin "1") (pinfunction "1_1") (pintype "passive"))
      (node (ref "R703") (pin "1") (pinfunction "1_1") (pintype "passive"))
      (node (ref "R704") (pin "1") (pinfunction "1_1") (pintype "passive"))
      (node (ref "X702") (pin "2") (pinfunction "S_2") (pintype "passive"))
    )
    (net (code "869") (name "Net-(Q701-E)") (class "Default")
      (node (ref "Q701") (pin "3") (pinfunction "E_3") (pintype "passive"))
      (node (ref "R702") (pin "2") (pinfunction "2_2") (pintype "passive"))
    )
    (net (code "870") (name "Net-(Q702-E)") (class "Default")
      (node (ref "Q702") (pin "3") (pinfunction "E_3") (pintype "passive"))
      (node (ref "R706") (pin "2") (pinfunction "2_2") (pintype "passive"))
    )
    (net (code "871") (name "Net-(Q703-B)") (class "Default")
      (node (ref "Q703") (pin "1") (pinfunction "B_1") (pintype "passive"))
      (node (ref "R716") (pin "2") (pinfunction "2_2") (pintype "passive"))
    )
    (net (code "872") (name "Net-(Q703-C)") (class "Default")
      (node (ref "Q703") (pin "2") (pinfunction "C_2") (pintype "passive"))
      (node (ref "R715") (pin "2") (pinfunction "2_2") (pintype "passive"))
      (node (ref "R718") (pin "1") (pinfunction "1_1") (pintype "passive"))
    )
    (net (code "873") (name "Net-(Q704-B)") (class "Default")
      (node (ref "Q704") (pin "1") (pinfunction "B_1") (pintype "passive"))
      (node (ref "R728") (pin "2") (pinfunction "2_2") (pintype "passive"))
    )
    (net (code "874") (name "Net-(Q705-B)") (class "Default")
      (node (ref "Q705") (pin "1") (pinfunction "B_1") (pintype "passive"))
      (node (ref "R726") (pin "1") (pinfunction "1_1") (pintype "passive"))
    )
    (net (code "875") (name "Net-(Q707-D)") (class "Default")
      (node (ref "Q707") (pin "3") (pinfunction "D_3") (pintype "passive"))
      (node (ref "R738") (pin "2") (pinfunction "2_2") (pintype "passive"))
    )
    (net (code "876") (name "Net-(Q801-B)") (class "Default")
      (node (ref "Q801") (pin "1") (pinfunction "B_1") (pintype "passive"))
      (node (ref "Q802") (pin "1") (pinfunction "B_1") (pintype "passive"))
      (node (ref "Q802") (pin "2") (pinfunction "C_2") (pintype "passive"))
      (node (ref "R801") (pin "1") (pinfunction "1_1") (pintype "passive"))
      (node (ref "R803") (pin "1") (pinfunction "1_1") (pintype "passive"))
      (node (ref "R804") (pin "1") (pinfunction "1_1") (pintype "passive"))
      (node (ref "X802") (pin "2") (pinfunction "S_2") (pintype "passive"))
    )
    (net (code "877") (name "Net-(Q801-E)") (class "Default")
      (node (ref "Q801") (pin "3") (pinfunction "E_3") (pintype "passive"))
      (node (ref "R802") (pin "2") (pinfunction "2_2") (pintype "passive"))
    )
    (net (code "878") (name "Net-(Q802-E)") (class "Default")
      (node (ref "Q802") (pin "3") (pinfunction "E_3") (pintype "passive"))
      (node (ref "R806") (pin "2") (pinfunction "2_2") (pintype "passive"))
    )
    (net (code "879") (name "Net-(Q803-B)") (class "Default")
      (node (ref "Q803") (pin "1") (pinfunction "B_1") (pintype "passive"))
      (node (ref "R816") (pin "2") (pinfunction "2_2") (pintype "passive"))
    )
    (net (code "880") (name "Net-(Q803-C)") (class "Default")
      (node (ref "Q803") (pin "2") (pinfunction "C_2") (pintype "passive"))
      (node (ref "R815") (pin "2") (pinfunction "2_2") (pintype "passive"))
      (node (ref "R818") (pin "1") (pinfunction "1_1") (pintype "passive"))
    )
    (net (code "881") (name "Net-(Q804-B)") (class "Default")
      (node (ref "Q804") (pin "1") (pinfunction "B_1") (pintype "passive"))
      (node (ref "R828") (pin "2") (pinfunction "2_2") (pintype "passive"))
    )
    (net (code "882") (name "Net-(Q805-B)") (class "Default")
      (node (ref "Q805") (pin "1") (pinfunction "B_1") (pintype "passive"))
      (node (ref "R826") (pin "1") (pinfunction "1_1") (pintype "passive"))
    )
    (net (code "883") (name "Net-(Q807-D)") (class "Default")
      (node (ref "Q807") (pin "3") (pinfunction "D_3") (pintype "passive"))
      (node (ref "R838") (pin "2") (pinfunction "2_2") (pintype "passive"))
    )
    (net (code "884") (name "Net-(Q901-B)") (class "Default")
      (node (ref "Q901") (pin "1") (pinfunction "B_1") (pintype "passive"))
      (node (ref "Q902") (pin "1") (pinfunction "B_1") (pintype "passive"))
      (node (ref "Q902") (pin "2") (pinfunction "C_2") (pintype "passive"))
      (node (ref "R901") (pin "1") (pinfunction "1_1") (pintype "passive"))
      (node (ref "R903") (pin "1") (pinfunction "1_1") (pintype "passive"))
      (node (ref "R904") (pin "1") (pinfunction "1_1") (pintype "passive"))
      (node (ref "X902") (pin "2") (pinfunction "S_2") (pintype "passive"))
    )
    (net (code "885") (name "Net-(Q901-E)") (class "Default")
      (node (ref "Q901") (pin "3") (pinfunction "E_3") (pintype "passive"))
      (node (ref "R902") (pin "2") (pinfunction "2_2") (pintype "passive"))
    )
    (net (code "886") (name "Net-(Q902-E)") (class "Default")
      (node (ref "Q902") (pin "3") (pinfunction "E_3") (pintype "passive"))
      (node (ref "R906") (pin "2") (pinfunction "2_2") (pintype "passive"))
    )
    (net (code "887") (name "Net-(Q903-B)") (class "Default")
      (node (ref "Q903") (pin "1") (pinfunction "B_1") (pintype "passive"))
      (node (ref "R916") (pin "2") (pinfunction "2_2") (pintype "passive"))
    )
    (net (code "888") (name "Net-(Q903-C)") (class "Default")
      (node (ref "Q903") (pin "2") (pinfunction "C_2") (pintype "passive"))
      (node (ref "R915") (pin "2") (pinfunction "2_2") (pintype "passive"))
      (node (ref "R918") (pin "1") (pinfunction "1_1") (pintype "passive"))
    )
    (net (code "889") (name "Net-(Q904-B)") (class "Default")
      (node (ref "Q904") (pin "1") (pinfunction "B_1") (pintype "passive"))
      (node (ref "R928") (pin "2") (pinfunction "2_2") (pintype "passive"))
    )
    (net (code "890") (name "Net-(Q905-B)") (class "Default")
      (node (ref "Q905") (pin "1") (pinfunction "B_1") (pintype "passive"))
      (node (ref "R926") (pin "1") (pinfunction "1_1") (pintype "passive"))
    )
    (net (code "891") (name "Net-(Q907-D)") (class "Default")
      (node (ref "Q907") (pin "3") (pinfunction "D_3") (pintype "passive"))
      (node (ref "R938") (pin "2") (pinfunction "2_2") (pintype "passive"))
    )
    (net (code "892") (name "Net-(Q1001-B)") (class "Default")
      (node (ref "Q1001") (pin "1") (pinfunction "B_1") (pintype "passive"))
      (node (ref "Q1002") (pin "1") (pinfunction "B_1") (pintype "passive"))
      (node (ref "Q1002") (pin "2") (pinfunction "C_2") (pintype "passive"))
      (node (ref "R1001") (pin "1") (pinfunction "1_1") (pintype "passive"))
      (node (ref "R1003") (pin "1") (pinfunction "1_1") (pintype "passive"))
      (node (ref "R1004") (pin "1") (pinfunction "1_1") (pintype "passive"))
      (node (ref "X1002") (pin "2") (pinfunction "S_2") (pintype "passive"))
    )
    (net (code "893") (name "Net-(Q1001-E)") (class "Default")
      (node (ref "Q1001") (pin "3") (pinfunction "E_3") (pintype "passive"))
      (node (ref "R1002") (pin "2") (pinfunction "2_2") (pintype "passive"))
    )
    (net (code "894") (name "Net-(Q1002-E)") (class "Default")
      (node (ref "Q1002") (pin "3") (pinfunction "E_3") (pintype "passive"))
      (node (ref "R1006") (pin "2") (pinfunction "2_2") (pintype "passive"))
    )
    (net (code "895") (name "Net-(Q1003-B)") (class "Default")
      (node (ref "Q1003") (pin "1") (pinfunction "B_1") (pintype "passive"))
      (node (ref "R1016") (pin "2") (pinfunction "2_2") (pintype "passive"))
    )
    (net (code "896") (name "Net-(Q1003-C)") (class "Default")
      (node (ref "Q1003") (pin "2") (pinfunction "C_2") (pintype "passive"))
      (node (ref "R1015") (pin "2") (pinfunction "2_2") (pintype "passive"))
      (node (ref "R1018") (pin "1") (pinfunction "1_1") (pintype "passive"))
    )
    (net (code "897") (name "Net-(Q1004-B)") (class "Default")
      (node (ref "Q1004") (pin "1") (pinfunction "B_1") (pintype "passive"))
      (node (ref "R1028") (pin "2") (pinfunction "2_2") (pintype "passive"))
    )
    (net (code "898") (name "Net-(Q1005-B)") (class "Default")
      (node (ref "Q1005") (pin "1") (pinfunction "B_1") (pintype "passive"))
      (node (ref "R1026") (pin "1") (pinfunction "1_1") (pintype "passive"))
    )
    (net (code "899") (name "Net-(Q1007-D)") (class "Default")
      (node (ref "Q1007") (pin "3") (pinfunction "D_3") (pintype "passive"))
      (node (ref "R1038") (pin "2") (pinfunction "2_2") (pintype "passive"))
    )
    (net (code "900") (name "Net-(Q1101-B)") (class "Default")
      (node (ref "Q1101") (pin "1") (pinfunction "B_1") (pintype "passive"))
      (node (ref "Q1102") (pin "1") (pinfunction "B_1") (pintype "passive"))
      (node (ref "Q1102") (pin "2") (pinfunction "C_2") (pintype "passive"))
      (node (ref "R1101") (pin "1") (pinfunction "1_1") (pintype "passive"))
      (node (ref "R1103") (pin "1") (pinfunction "1_1") (pintype "passive"))
      (node (ref "R1104") (pin "1") (pinfunction "1_1") (pintype "passive"))
      (node (ref "X1102") (pin "2") (pinfunction "S_2") (pintype "passive"))
    )
    (net (code "901") (name "Net-(Q1101-E)") (class "Default")
      (node (ref "Q1101") (pin "3") (pinfunction "E_3") (pintype "passive"))
      (node (ref "R1102") (pin "2") (pinfunction "2_2") (pintype "passive"))
    )
    (net (code "902") (name "Net-(Q1102-E)") (class "Default")
      (node (ref "Q1102") (pin "3") (pinfunction "E_3") (pintype "passive"))
      (node (ref "R1106") (pin "2") (pinfunction "2_2") (pintype "passive"))
    )
    (net (code "903") (name "Net-(Q1103-B)") (class "Default")
      (node (ref "Q1103") (pin "1") (pinfunction "B_1") (pintype "passive"))
      (node (ref "R1116") (pin "2") (pinfunction "2_2") (pintype "passive"))
    )
    (net (code "904") (name "Net-(Q1103-C)") (class "Default")
      (node (ref "Q1103") (pin "2") (pinfunction "C_2") (pintype "passive"))
      (node (ref "R1115") (pin "2") (pinfunction "2_2") (pintype "passive"))
      (node (ref "R1118") (pin "1") (pinfunction "1_1") (pintype "passive"))
    )
    (net (code "905") (name "Net-(Q1104-B)") (class "Default")
      (node (ref "Q1104") (pin "1") (pinfunction "B_1") (pintype "passive"))
      (node (ref "R1128") (pin "2") (pinfunction "2_2") (pintype "passive"))
    )
    (net (code "906") (name "Net-(Q1105-B)") (class "Default")
      (node (ref "Q1105") (pin "1") (pinfunction "B_1") (pintype "passive"))
      (node (ref "R1126") (pin "1") (pinfunction "1_1") (pintype "passive"))
    )
    (net (code "907") (name "Net-(Q1107-D)") (class "Default")
      (node (ref "Q1107") (pin "3") (pinfunction "D_3") (pintype "passive"))
      (node (ref "R1138") (pin "2") (pinfunction "2_2") (pintype "passive"))
    )
    (net (code "908") (name "Net-(Q1201-B)") (class "Default")
      (node (ref "Q1201") (pin "1") (pinfunction "B_1") (pintype "passive"))
      (node (ref "Q1202") (pin "1") (pinfunction "B_1") (pintype "passive"))
      (node (ref "Q1202") (pin "2") (pinfunction "C_2") (pintype "passive"))
      (node (ref "R1201") (pin "1") (pinfunction "1_1") (pintype "passive"))
      (node (ref "R1203") (pin "1") (pinfunction "1_1") (pintype "passive"))
      (node (ref "R1204") (pin "1") (pinfunction "1_1") (pintype "passive"))
      (node (ref "X1202") (pin "2") (pinfunction "S_2") (pintype "passive"))
    )
    (net (code "909") (name "Net-(Q1201-E)") (class "Default")
      (node (ref "Q1201") (pin "3") (pinfunction "E_3") (pintype "passive"))
      (node (ref "R1202") (pin "2") (pinfunction "2_2") (pintype "passive"))
    )
    (net (code "910") (name "Net-(Q1202-E)") (class "Default")
      (node (ref "Q1202") (pin "3") (pinfunction "E_3") (pintype "passive"))
      (node (ref "R1206") (pin "2") (pinfunction "2_2") (pintype "passive"))
    )
    (net (code "911") (name "Net-(Q1203-B)") (class "Default")
      (node (ref "Q1203") (pin "1") (pinfunction "B_1") (pintype "passive"))
      (node (ref "R1216") (pin "2") (pinfunction "2_2") (pintype "passive"))
    )
    (net (code "912") (name "Net-(Q1203-C)") (class "Default")
      (node (ref "Q1203") (pin "2") (pinfunction "C_2") (pintype "passive"))
      (node (ref "R1215") (pin "2") (pinfunction "2_2") (pintype "passive"))
      (node (ref "R1218") (pin "1") (pinfunction "1_1") (pintype "passive"))
    )
    (net (code "913") (name "Net-(Q1204-B)") (class "Default")
      (node (ref "Q1204") (pin "1") (pinfunction "B_1") (pintype "passive"))
      (node (ref "R1228") (pin "2") (pinfunction "2_2") (pintype "passive"))
    )
    (net (code "914") (name "Net-(Q1205-B)") (class "Default")
      (node (ref "Q1205") (pin "1") (pinfunction "B_1") (pintype "passive"))
      (node (ref "R1226") (pin "1") (pinfunction "1_1") (pintype "passive"))
    )
    (net (code "915") (name "Net-(Q1207-D)") (class "Default")
      (node (ref "Q1207") (pin "3") (pinfunction "D_3") (pintype "passive"))
      (node (ref "R1238") (pin "2") (pinfunction "2_2") (pintype "passive"))
    )
    (net (code "916") (name "Net-(R115-Pad1)") (class "Default")
      (node (ref "R115") (pin "1") (pinfunction "1_1") (pintype "passive"))
      (node (ref "X101") (pin "21") (pinfunction "21_21") (pintype "passive"))
    )
    (net (code "917") (name "Net-(R127-Pad2)") (class "Default")
      (node (ref "R127") (pin "2") (pinfunction "2_2") (pintype "passive"))
      (node (ref "R129") (pin "1") (pinfunction "1_1") (pintype "passive"))
    )
    (net (code "918") (name "Net-(R140-Pad2)") (class "Default")
      (node (ref "R140") (pin "2") (pinfunction "2_2") (pintype "passive"))
      (node (ref "X101") (pin "16") (pinfunction "16_16") (pintype "passive"))
    )
    (net (code "919") (name "Net-(R215-Pad1)") (class "Default")
      (node (ref "R215") (pin "1") (pinfunction "1_1") (pintype "passive"))
      (node (ref "X201") (pin "21") (pinfunction "21_21") (pintype "passive"))
    )
    (net (code "920") (name "Net-(R227-Pad2)") (class "Default")
      (node (ref "R227") (pin "2") (pinfunction "2_2") (pintype "passive"))
      (node (ref "R229") (pin "1") (pinfunction "1_1") (pintype "passive"))
    )
    (net (code "921") (name "Net-(R240-Pad2)") (class "Default")
      (node (ref "R240") (pin "2") (pinfunction "2_2") (pintype "passive"))
      (node (ref "X201") (pin "16") (pinfunction "16_16") (pintype "passive"))
    )
    (net (code "922") (name "Net-(R315-Pad1)") (class "Default")
      (node (ref "R315") (pin "1") (pinfunction "1_1") (pintype "passive"))
      (node (ref "X301") (pin "21") (pinfunction "21_21") (pintype "passive"))
    )
    (net (code "923") (name "Net-(R327-Pad2)") (class "Default")
      (node (ref "R327") (pin "2") (pinfunction "2_2") (pintype "passive"))
      (node (ref "R329") (pin "1") (pinfunction "1_1") (pintype "passive"))
    )
    (net (code "924") (name "Net-(R340-Pad2)") (class "Default")
      (node (ref "R340") (pin "2") (pinfunction "2_2") (pintype "passive"))
      (node (ref "X301") (pin "16") (pinfunction "16_16") (pintype "passive"))
    )
    (net (code "925") (name "Net-(R415-Pad1)") (class "Default")
      (node (ref "R415") (pin "1") (pinfunction "1_1") (pintype "passive"))
      (node (ref "X401") (pin "21") (pinfunction "21_21") (pintype "passive"))
    )
    (net (code "926") (name "Net-(R427-Pad2)") (class "Default")
      (node (ref "R427") (pin "2") (pinfunction "2_2") (pintype "passive"))
      (node (ref "R429") (pin "1") (pinfunction "1_1") (pintype "passive"))
    )
    (net (code "927") (name "Net-(R440-Pad2)") (class "Default")
      (node (ref "R440") (pin "2") (pinfunction "2_2") (pintype "passive"))
      (node (ref "X401") (pin "16") (pinfunction "16_16") (pintype "passive"))
    )
    (net (code "928") (name "Net-(R515-Pad1)") (class "Default")
      (node (ref "R515") (pin "1") (pinfunction "1_1") (pintype "passive"))
      (node (ref "X501") (pin "21") (pinfunction "21_21") (pintype "passive"))
    )
    (net (code "929") (name "Net-(R527-Pad2)") (class "Default")
      (node (ref "R527") (pin "2") (pinfunction "2_2") (pintype "passive"))
      (node (ref "R529") (pin "1") (pinfunction "1_1") (pintype "passive"))
    )
    (net (code "930") (name "Net-(R540-Pad2)") (class "Default")
      (node (ref "R540") (pin "2") (pinfunction "2_2") (pintype "passive"))
      (node (ref "X501") (pin "16") (pinfunction "16_16") (pintype "passive"))
    )
    (net (code "931") (name "Net-(R615-Pad1)") (class "Default")
      (node (ref "R615") (pin "1") (pinfunction "1_1") (pintype "passive"))
      (node (ref "X601") (pin "21") (pinfunction "21_21") (pintype "passive"))
    )
    (net (code "932") (name "Net-(R627-Pad2)") (class "Default")
      (node (ref "R627") (pin "2") (pinfunction "2_2") (pintype "passive"))
      (node (ref "R629") (pin "1") (pinfunction "1_1") (pintype "passive"))
    )
    (net (code "933") (name "Net-(R640-Pad2)") (class "Default")
      (node (ref "R640") (pin "2") (pinfunction "2_2") (pintype "passive"))
      (node (ref "X601") (pin "16") (pinfunction "16_16") (pintype "passive"))
    )
    (net (code "934") (name "Net-(R715-Pad1)") (class "Default")
      (node (ref "R715") (pin "1") (pinfunction "1_1") (pintype "passive"))
      (node (ref "X701") (pin "21") (pinfunction "21_21") (pintype "passive"))
    )
    (net (code "935") (name "Net-(R727-Pad2)") (class "Default")
      (node (ref "R727") (pin "2") (pinfunction "2_2") (pintype "passive"))
      (node (ref "R729") (pin "1") (pinfunction "1_1") (pintype "passive"))
    )
    (net (code "936") (name "Net-(R740-Pad2)") (class "Default")
      (node (ref "R740") (pin "2") (pinfunction "2_2") (pintype "passive"))
      (node (ref "X701") (pin "16") (pinfunction "16_16") (pintype "passive"))
    )
    (net (code "937") (name "Net-(R815-Pad1)") (class "Default")
      (node (ref "R815") (pin "1") (pinfunction "1_1") (pintype "passive"))
      (node (ref "X801") (pin "21") (pinfunction "21_21") (pintype "passive"))
    )
    (net (code "938") (name "Net-(R827-Pad2)") (class "Default")
      (node (ref "R827") (pin "2") (pinfunction "2_2") (pintype "passive"))
      (node (ref "R829") (pin "1") (pinfunction "1_1") (pintype "passive"))
    )
    (net (code "939") (name "Net-(R840-Pad2)") (class "Default")
      (node (ref "R840") (pin "2") (pinfunction "2_2") (pintype "passive"))
      (node (ref "X801") (pin "16") (pinfunction "16_16") (pintype "passive"))
    )
    (net (code "940") (name "Net-(R915-Pad1)") (class "Default")
      (node (ref "R915") (pin "1") (pinfunction "1_1") (pintype "passive"))
      (node (ref "X901") (pin "21") (pinfunction "21_21") (pintype "passive"))
    )
    (net (code "941") (name "Net-(R927-Pad2)") (class "Default")
      (node (ref "R927") (pin "2") (pinfunction "2_2") (pintype "passive"))
      (node (ref "R929") (pin "1") (pinfunction "1_1") (pintype "passive"))
    )
    (net (code "942") (name "Net-(R940-Pad2)") (class "Default")
      (node (ref "R940") (pin "2") (pinfunction "2_2") (pintype "passive"))
      (node (ref "X901") (pin "16") (pinfunction "16_16") (pintype "passive"))
    )
    (net (code "943") (name "Net-(R1015-Pad1)") (class "Default")
      (node (ref "R1015") (pin "1") (pinfunction "1_1") (pintype "passive"))
      (node (ref "X1001") (pin "21") (pinfunction "21_21") (pintype "passive"))
    )
    (net (code "944") (name "Net-(R1027-Pad2)") (class "Default")
      (node (ref "R1027") (pin "2") (pinfunction "2_2") (pintype "passive"))
      (node (ref "R1029") (pin "1") (pinfunction "1_1") (pintype "passive"))
    )
    (net (code "945") (name "Net-(R1040-Pad2)") (class "Default")
      (node (ref "R1040") (pin "2") (pinfunction "2_2") (pintype "passive"))
      (node (ref "X1001") (pin "16") (pinfunction "16_16") (pintype "passive"))
    )
    (net (code "946") (name "Net-(R1115-Pad1)") (class "Default")
      (node (ref "R1115") (pin "1") (pinfunction "1_1") (pintype "passive"))
      (node (ref "X1101") (pin "21") (pinfunction "21_21") (pintype "passive"))
    )
    (net (code "947") (name "Net-(R1127-Pad2)") (class "Default")
      (node (ref "R1127") (pin "2") (pinfunction "2_2") (pintype "passive"))
      (node (ref "R1129") (pin "1") (pinfunction "1_1") (pintype "passive"))
    )
    (net (code "948") (name "Net-(R1140-Pad2)") (class "Default")
      (node (ref "R1140") (pin "2") (pinfunction "2_2") (pintype "passive"))
      (node (ref "X1101") (pin "16") (pinfunction "16_16") (pintype "passive"))
    )
    (net (code "949") (name "Net-(R1215-Pad1)") (class "Default")
      (node (ref "R1215") (pin "1") (pinfunction "1_1") (pintype "passive"))
      (node (ref "X1201") (pin "21") (pinfunction "21_21") (pintype "passive"))
    )
    (net (code "950") (name "Net-(R1227-Pad2)") (class "Default")
      (node (ref "R1227") (pin "2") (pinfunction "2_2") (pintype "passive"))
      (node (ref "R1229") (pin "1") (pinfunction "1_1") (pintype "passive"))
    )
    (net (code "951") (name "Net-(R1240-Pad2)") (class "Default")
      (node (ref "R1240") (pin "2") (pinfunction "2_2") (pintype "passive"))
      (node (ref "X1201") (pin "16") (pinfunction "16_16") (pintype "passive"))
    )
    (net (code "952") (name "VCC") (class "Default")
      (node (ref "6V") (pin "TP") (pinfunction "PP_TP") (pintype "input"))
      (node (ref "6V1001") (pin "TP") (pinfunction "PP_TP") (pintype "input"))
      (node (ref "6V1101") (pin "TP") (pinfunction "PP_TP") (pintype "input"))
      (node (ref "6V1201") (pin "TP") (pinfunction "PP_TP") (pintype "input"))
      (node (ref "6V201") (pin "TP") (pinfunction "PP_TP") (pintype "input"))
      (node (ref "6V301") (pin "TP") (pinfunction "PP_TP") (pintype "input"))
      (node (ref "6V401") (pin "TP") (pinfunction "PP_TP") (pintype "input"))
      (node (ref "6V501") (pin "TP") (pinfunction "PP_TP") (pintype "input"))
      (node (ref "6V601") (pin "TP") (pinfunction "PP_TP") (pintype "input"))
      (node (ref "6V701") (pin "TP") (pinfunction "PP_TP") (pintype "input"))
      (node (ref "6V801") (pin "TP") (pinfunction "PP_TP") (pintype "input"))
      (node (ref "6V901") (pin "TP") (pinfunction "PP_TP") (pintype "input"))
      (node (ref "C1004") (pin "1") (pinfunction "1_1") (pintype "passive"))
      (node (ref "C104") (pin "1") (pinfunction "1_1") (pintype "passive"))
      (node (ref "C1104") (pin "1") (pinfunction "1_1") (pintype "passive"))
      (node (ref "C1204") (pin "1") (pinfunction "1_1") (pintype "passive"))
      (node (ref "C204") (pin "1") (pinfunction "1_1") (pintype "passive"))
      (node (ref "C304") (pin "1") (pinfunction "1_1") (pintype "passive"))
      (node (ref "C404") (pin "1") (pinfunction "1_1") (pintype "passive"))
      (node (ref "C504") (pin "1") (pinfunction "1_1") (pintype "passive"))
      (node (ref "C604") (pin "1") (pinfunction "1_1") (pintype "passive"))
      (node (ref "C704") (pin "1") (pinfunction "1_1") (pintype "passive"))
      (node (ref "C804") (pin "1") (pinfunction "1_1") (pintype "passive"))
      (node (ref "C904") (pin "1") (pinfunction "1_1") (pintype "passive"))
      (node (ref "IC1001") (pin "8") (pinfunction "V+_8") (pintype "power_in"))
      (node (ref "IC1002") (pin "1") (pinfunction "OUT_1") (pintype "passive"))
      (node (ref "IC1003") (pin "OUT") (pinfunction "OUT_OUT") (pintype "passive"))
      (node (ref "IC1008") (pin "3") (pinfunction "V+_3") (pintype "power_in"))
      (node (ref "IC101") (pin "8") (pinfunction "V+_8") (pintype "power_in"))
      (node (ref "IC102") (pin "1") (pinfunction "OUT_1") (pintype "passive"))
      (node (ref "IC103") (pin "OUT") (pinfunction "OUT_OUT") (pintype "passive"))
      (node (ref "IC108") (pin "3") (pinfunction "V+_3") (pintype "power_in"))
      (node (ref "IC1101") (pin "8") (pinfunction "V+_8") (pintype "power_in"))
      (node (ref "IC1102") (pin "1") (pinfunction "OUT_1") (pintype "passive"))
      (node (ref "IC1103") (pin "OUT") (pinfunction "OUT_OUT") (pintype "passive"))
      (node (ref "IC1108") (pin "3") (pinfunction "V+_3") (pintype "power_in"))
      (node (ref "IC1201") (pin "8") (pinfunction "V+_8") (pintype "power_in"))
      (node (ref "IC1202") (pin "1") (pinfunction "OUT_1") (pintype "passive"))
      (node (ref "IC1203") (pin "OUT") (pinfunction "OUT_OUT") (pintype "passive"))
      (node (ref "IC1208") (pin "3") (pinfunction "V+_3") (pintype "power_in"))
      (node (ref "IC201") (pin "8") (pinfunction "V+_8") (pintype "power_in"))
      (node (ref "IC202") (pin "1") (pinfunction "OUT_1") (pintype "passive"))
      (node (ref "IC203") (pin "OUT") (pinfunction "OUT_OUT") (pintype "passive"))
      (node (ref "IC208") (pin "3") (pinfunction "V+_3") (pintype "power_in"))
      (node (ref "IC301") (pin "8") (pinfunction "V+_8") (pintype "power_in"))
      (node (ref "IC302") (pin "1") (pinfunction "OUT_1") (pintype "passive"))
      (node (ref "IC303") (pin "OUT") (pinfunction "OUT_OUT") (pintype "passive"))
      (node (ref "IC308") (pin "3") (pinfunction "V+_3") (pintype "power_in"))
      (node (ref "IC401") (pin "8") (pinfunction "V+_8") (pintype "power_in"))
      (node (ref "IC402") (pin "1") (pinfunction "OUT_1") (pintype "passive"))
      (node (ref "IC403") (pin "OUT") (pinfunction "OUT_OUT") (pintype "passive"))
      (node (ref "IC408") (pin "3") (pinfunction "V+_3") (pintype "power_in"))
      (node (ref "IC501") (pin "8") (pinfunction "V+_8") (pintype "power_in"))
      (node (ref "IC502") (pin "1") (pinfunction "OUT_1") (pintype "passive"))
      (node (ref "IC503") (pin "OUT") (pinfunction "OUT_OUT") (pintype "passive"))
      (node (ref "IC508") (pin "3") (pinfunction "V+_3") (pintype "power_in"))
      (node (ref "IC601") (pin "8") (pinfunction "V+_8") (pintype "power_in"))
      (node (ref "IC602") (pin "1") (pinfunction "OUT_1") (pintype "passive"))
      (node (ref "IC603") (pin "OUT") (pinfunction "OUT_OUT") (pintype "passive"))
      (node (ref "IC608") (pin "3") (pinfunction "V+_3") (pintype "power_in"))
      (node (ref "IC701") (pin "8") (pinfunction "V+_8") (pintype "power_in"))
      (node (ref "IC702") (pin "1") (pinfunction "OUT_1") (pintype "passive"))
      (node (ref "IC703") (pin "OUT") (pinfunction "OUT_OUT") (pintype "passive"))
      (node (ref "IC708") (pin "3") (pinfunction "V+_3") (pintype "power_in"))
      (node (ref "IC801") (pin "8") (pinfunction "V+_8") (pintype "power_in"))
      (node (ref "IC802") (pin "1") (pinfunction "OUT_1") (pintype "passive"))
      (node (ref "IC803") (pin "OUT") (pinfunction "OUT_OUT") (pintype "passive"))
      (node (ref "IC808") (pin "3") (pinfunction "V+_3") (pintype "power_in"))
      (node (ref "IC901") (pin "8") (pinfunction "V+_8") (pintype "power_in"))
      (node (ref "IC902") (pin "1") (pinfunction "OUT_1") (pintype "passive"))
      (node (ref "IC903") (pin "OUT") (pinfunction "OUT_OUT") (pintype "passive"))
      (node (ref "IC908") (pin "3") (pinfunction "V+_3") (pintype "power_in"))
      (node (ref "R1013") (pin "2") (pinfunction "2_2") (pintype "passive"))
      (node (ref "R1021") (pin "2") (pinfunction "2_2") (pintype "passive"))
      (node (ref "R1024") (pin "1") (pinfunction "1_1") (pintype "passive"))
      (node (ref "R1031") (pin "2") (pinfunction "2_2") (pintype "passive"))
      (node (ref "R1042") (pin "2") (pinfunction "2_2") (pintype "passive"))
      (node (ref "R1113") (pin "2") (pinfunction "2_2") (pintype "passive"))
      (node (ref "R1121") (pin "2") (pinfunction "2_2") (pintype "passive"))
      (node (ref "R1124") (pin "1") (pinfunction "1_1") (pintype "passive"))
      (node (ref "R113") (pin "2") (pinfunction "2_2") (pintype "passive"))
      (node (ref "R1131") (pin "2") (pinfunction "2_2") (pintype "passive"))
      (node (ref "R1142") (pin "2") (pinfunction "2_2") (pintype "passive"))
      (node (ref "R121") (pin "2") (pinfunction "2_2") (pintype "passive"))
      (node (ref "R1213") (pin "2") (pinfunction "2_2") (pintype "passive"))
      (node (ref "R1221") (pin "2") (pinfunction "2_2") (pintype "passive"))
      (node (ref "R1224") (pin "1") (pinfunction "1_1") (pintype "passive"))
      (node (ref "R1231") (pin "2") (pinfunction "2_2") (pintype "passive"))
      (node (ref "R124") (pin "1") (pinfunction "1_1") (pintype "passive"))
      (node (ref "R1242") (pin "2") (pinfunction "2_2") (pintype "passive"))
      (node (ref "R131") (pin "2") (pinfunction "2_2") (pintype "passive"))
      (node (ref "R142") (pin "2") (pinfunction "2_2") (pintype "passive"))
      (node (ref "R213") (pin "2") (pinfunction "2_2") (pintype "passive"))
      (node (ref "R221") (pin "2") (pinfunction "2_2") (pintype "passive"))
      (node (ref "R224") (pin "1") (pinfunction "1_1") (pintype "passive"))
      (node (ref "R231") (pin "2") (pinfunction "2_2") (pintype "passive"))
      (node (ref "R242") (pin "2") (pinfunction "2_2") (pintype "passive"))
      (node (ref "R313") (pin "2") (pinfunction "2_2") (pintype "passive"))
      (node (ref "R321") (pin "2") (pinfunction "2_2") (pintype "passive"))
      (node (ref "R324") (pin "1") (pinfunction "1_1") (pintype "passive"))
      (node (ref "R331") (pin "2") (pinfunction "2_2") (pintype "passive"))
      (node (ref "R342") (pin "2") (pinfunction "2_2") (pintype "passive"))
      (node (ref "R413") (pin "2") (pinfunction "2_2") (pintype "passive"))
      (node (ref "R421") (pin "2") (pinfunction "2_2") (pintype "passive"))
      (node (ref "R424") (pin "1") (pinfunction "1_1") (pintype "passive"))
      (node (ref "R431") (pin "2") (pinfunction "2_2") (pintype "passive"))
      (node (ref "R442") (pin "2") (pinfunction "2_2") (pintype "passive"))
      (node (ref "R513") (pin "2") (pinfunction "2_2") (pintype "passive"))
      (node (ref "R521") (pin "2") (pinfunction "2_2") (pintype "passive"))
      (node (ref "R524") (pin "1") (pinfunction "1_1") (pintype "passive"))
      (node (ref "R531") (pin "2") (pinfunction "2_2") (pintype "passive"))
      (node (ref "R542") (pin "2") (pinfunction "2_2") (pintype "passive"))
      (node (ref "R613") (pin "2") (pinfunction "2_2") (pintype "passive"))
      (node (ref "R621") (pin "2") (pinfunction "2_2") (pintype "passive"))
      (node (ref "R624") (pin "1") (pinfunction "1_1") (pintype "passive"))
      (node (ref "R631") (pin "2") (pinfunction "2_2") (pintype "passive"))
      (node (ref "R642") (pin "2") (pinfunction "2_2") (pintype "passive"))
      (node (ref "R713") (pin "2") (pinfunction "2_2") (pintype "passive"))
      (node (ref "R721") (pin "2") (pinfunction "2_2") (pintype "passive"))
      (node (ref "R724") (pin "1") (pinfunction "1_1") (pintype "passive"))
      (node (ref "R731") (pin "2") (pinfunction "2_2") (pintype "passive"))
      (node (ref "R742") (pin "2") (pinfunction "2_2") (pintype "passive"))
      (node (ref "R813") (pin "2") (pinfunction "2_2") (pintype "passive"))
      (node (ref "R821") (pin "2") (pinfunction "2_2") (pintype "passive"))
      (node (ref "R824") (pin "1") (pinfunction "1_1") (pintype "passive"))
      (node (ref "R831") (pin "2") (pinfunction "2_2") (pintype "passive"))
      (node (ref "R842") (pin "2") (pinfunction "2_2") (pintype "passive"))
      (node (ref "R913") (pin "2") (pinfunction "2_2") (pintype "passive"))
      (node (ref "R921") (pin "2") (pinfunction "2_2") (pintype "passive"))
      (node (ref "R924") (pin "1") (pinfunction "1_1") (pintype "passive"))
      (node (ref "R931") (pin "2") (pinfunction "2_2") (pintype "passive"))
      (node (ref "R942") (pin "2") (pinfunction "2_2") (pintype "passive"))
    )
    (net (code "953") (name "unconnected-(IC105A-Q6-Pad7)") (class "Default")
      (node (ref "IC105") (pin "7") (pinfunction "Q6_7") (pintype "output"))
    )
    (net (code "954") (name "unconnected-(IC105A-Q7-Pad4)") (class "Default")
      (node (ref "IC105") (pin "4") (pinfunction "Q7_4") (pintype "output"))
    )
    (net (code "955") (name "unconnected-(IC105A-Q8-Pad9)") (class "Default")
      (node (ref "IC105") (pin "9") (pinfunction "Q8_9") (pintype "output"))
    )
    (net (code "956") (name "unconnected-(IC105A-Q9-Pad5)") (class "Default")
      (node (ref "IC105") (pin "5") (pinfunction "Q9_5") (pintype "output"))
    )
    (net (code "957") (name "unconnected-(IC108D-OUT-Pad13)") (class "Default")
      (node (ref "IC108") (pin "13") (pinfunction "OUT_13") (pintype "open_collector"))
    )
    (net (code "958") (name "unconnected-(IC110-DIS-Pad7)") (class "Default")
      (node (ref "IC110") (pin "7") (pinfunction "DIS_7") (pintype "input"))
    )
    (net (code "959") (name "unconnected-(IC111A-Q-Pad6)") (class "Default")
      (node (ref "IC111") (pin "6") (pinfunction "Q_6") (pintype "output"))
    )
    (net (code "960") (name "unconnected-(IC111A-T2-Pad2)") (class "Default")
      (node (ref "IC111") (pin "2") (pinfunction "T2_2") (pintype "input"))
    )
    (net (code "961") (name "unconnected-(IC111A-~{Q}-Pad7)") (class "Default")
      (node (ref "IC111") (pin "7") (pinfunction "~{Q}_7") (pintype "output"))
    )
    (net (code "962") (name "unconnected-(IC111B-Q-Pad10)") (class "Default")
      (node (ref "IC111") (pin "10") (pinfunction "Q_10") (pintype "output"))
    )
    (net (code "963") (name "unconnected-(IC205A-Q6-Pad7)") (class "Default")
      (node (ref "IC205") (pin "7") (pinfunction "Q6_7") (pintype "output"))
    )
    (net (code "964") (name "unconnected-(IC205A-Q7-Pad4)") (class "Default")
      (node (ref "IC205") (pin "4") (pinfunction "Q7_4") (pintype "output"))
    )
    (net (code "965") (name "unconnected-(IC205A-Q8-Pad9)") (class "Default")
      (node (ref "IC205") (pin "9") (pinfunction "Q8_9") (pintype "output"))
    )
    (net (code "966") (name "unconnected-(IC205A-Q9-Pad5)") (class "Default")
      (node (ref "IC205") (pin "5") (pinfunction "Q9_5") (pintype "output"))
    )
    (net (code "967") (name "unconnected-(IC208D-OUT-Pad13)") (class "Default")
      (node (ref "IC208") (pin "13") (pinfunction "OUT_13") (pintype "open_collector"))
    )
    (net (code "968") (name "unconnected-(IC210-DIS-Pad7)") (class "Default")
      (node (ref "IC210") (pin "7") (pinfunction "DIS_7") (pintype "input"))
    )
    (net (code "969") (name "unconnected-(IC211A-Q-Pad6)") (class "Default")
      (node (ref "IC211") (pin "6") (pinfunction "Q_6") (pintype "output"))
    )
    (net (code "970") (name "unconnected-(IC211A-T2-Pad2)") (class "Default")
      (node (ref "IC211") (pin "2") (pinfunction "T2_2") (pintype "input"))
    )
    (net (code "971") (name "unconnected-(IC211A-~{Q}-Pad7)") (class "Default")
      (node (ref "IC211") (pin "7") (pinfunction "~{Q}_7") (pintype "output"))
    )
    (net (code "972") (name "unconnected-(IC211B-Q-Pad10)") (class "Default")
      (node (ref "IC211") (pin "10") (pinfunction "Q_10") (pintype "output"))
    )
    (net (code "973") (name "unconnected-(IC305A-Q6-Pad7)") (class "Default")
      (node (ref "IC305") (pin "7") (pinfunction "Q6_7") (pintype "output"))
    )
    (net (code "974") (name "unconnected-(IC305A-Q7-Pad4)") (class "Default")
      (node (ref "IC305") (pin "4") (pinfunction "Q7_4") (pintype "output"))
    )
    (net (code "975") (name "unconnected-(IC305A-Q8-Pad9)") (class "Default")
      (node (ref "IC305") (pin "9") (pinfunction "Q8_9") (pintype "output"))
    )
    (net (code "976") (name "unconnected-(IC305A-Q9-Pad5)") (class "Default")
      (node (ref "IC305") (pin "5") (pinfunction "Q9_5") (pintype "output"))
    )
    (net (code "977") (name "unconnected-(IC308D-OUT-Pad13)") (class "Default")
      (node (ref "IC308") (pin "13") (pinfunction "OUT_13") (pintype "open_collector"))
    )
    (net (code "978") (name "unconnected-(IC310-DIS-Pad7)") (class "Default")
      (node (ref "IC310") (pin "7") (pinfunction "DIS_7") (pintype "input"))
    )
    (net (code "979") (name "unconnected-(IC311A-Q-Pad6)") (class "Default")
      (node (ref "IC311") (pin "6") (pinfunction "Q_6") (pintype "output"))
    )
    (net (code "980") (name "unconnected-(IC311A-T2-Pad2)") (class "Default")
      (node (ref "IC311") (pin "2") (pinfunction "T2_2") (pintype "input"))
    )
    (net (code "981") (name "unconnected-(IC311A-~{Q}-Pad7)") (class "Default")
      (node (ref "IC311") (pin "7") (pinfunction "~{Q}_7") (pintype "output"))
    )
    (net (code "982") (name "unconnected-(IC311B-Q-Pad10)") (class "Default")
      (node (ref "IC311") (pin "10") (pinfunction "Q_10") (pintype "output"))
    )
    (net (code "983") (name "unconnected-(IC405A-Q6-Pad7)") (class "Default")
      (node (ref "IC405") (pin "7") (pinfunction "Q6_7") (pintype "output"))
    )
    (net (code "984") (name "unconnected-(IC405A-Q7-Pad4)") (class "Default")
      (node (ref "IC405") (pin "4") (pinfunction "Q7_4") (pintype "output"))
    )
    (net (code "985") (name "unconnected-(IC405A-Q8-Pad9)") (class "Default")
      (node (ref "IC405") (pin "9") (pinfunction "Q8_9") (pintype "output"))
    )
    (net (code "986") (name "unconnected-(IC405A-Q9-Pad5)") (class "Default")
      (node (ref "IC405") (pin "5") (pinfunction "Q9_5") (pintype "output"))
    )
    (net (code "987") (name "unconnected-(IC408D-OUT-Pad13)") (class "Default")
      (node (ref "IC408") (pin "13") (pinfunction "OUT_13") (pintype "open_collector"))
    )
    (net (code "988") (name "unconnected-(IC410-DIS-Pad7)") (class "Default")
      (node (ref "IC410") (pin "7") (pinfunction "DIS_7") (pintype "input"))
    )
    (net (code "989") (name "unconnected-(IC411A-Q-Pad6)") (class "Default")
      (node (ref "IC411") (pin "6") (pinfunction "Q_6") (pintype "output"))
    )
    (net (code "990") (name "unconnected-(IC411A-T2-Pad2)") (class "Default")
      (node (ref "IC411") (pin "2") (pinfunction "T2_2") (pintype "input"))
    )
    (net (code "991") (name "unconnected-(IC411A-~{Q}-Pad7)") (class "Default")
      (node (ref "IC411") (pin "7") (pinfunction "~{Q}_7") (pintype "output"))
    )
    (net (code "992") (name "unconnected-(IC411B-Q-Pad10)") (class "Default")
      (node (ref "IC411") (pin "10") (pinfunction "Q_10") (pintype "output"))
    )
    (net (code "993") (name "unconnected-(IC505A-Q6-Pad7)") (class "Default")
      (node (ref "IC505") (pin "7") (pinfunction "Q6_7") (pintype "output"))
    )
    (net (code "994") (name "unconnected-(IC505A-Q7-Pad4)") (class "Default")
      (node (ref "IC505") (pin "4") (pinfunction "Q7_4") (pintype "output"))
    )
    (net (code "995") (name "unconnected-(IC505A-Q8-Pad9)") (class "Default")
      (node (ref "IC505") (pin "9") (pinfunction "Q8_9") (pintype "output"))
    )
    (net (code "996") (name "unconnected-(IC505A-Q9-Pad5)") (class "Default")
      (node (ref "IC505") (pin "5") (pinfunction "Q9_5") (pintype "output"))
    )
    (net (code "997") (name "unconnected-(IC508D-OUT-Pad13)") (class "Default")
      (node (ref "IC508") (pin "13") (pinfunction "OUT_13") (pintype "open_collector"))
    )
    (net (code "998") (name "unconnected-(IC510-DIS-Pad7)") (class "Default")
      (node (ref "IC510") (pin "7") (pinfunction "DIS_7") (pintype "input"))
    )
    (net (code "999") (name "unconnected-(IC511A-Q-Pad6)") (class "Default")
      (node (ref "IC511") (pin "6") (pinfunction "Q_6") (pintype "output"))
    )
    (net (code "1000") (name "unconnected-(IC511A-T2-Pad2)") (class "Default")
      (node (ref "IC511") (pin "2") (pinfunction "T2_2") (pintype "input"))
    )
    (net (code "1001") (name "unconnected-(IC511A-~{Q}-Pad7)") (class "Default")
      (node (ref "IC511") (pin "7") (pinfunction "~{Q}_7") (pintype "output"))
    )
    (net (code "1002") (name "unconnected-(IC511B-Q-Pad10)") (class "Default")
      (node (ref "IC511") (pin "10") (pinfunction "Q_10") (pintype "output"))
    )
    (net (code "1003") (name "unconnected-(IC605A-Q6-Pad7)") (class "Default")
      (node (ref "IC605") (pin "7") (pinfunction "Q6_7") (pintype "output"))
    )
    (net (code "1004") (name "unconnected-(IC605A-Q7-Pad4)") (class "Default")
      (node (ref "IC605") (pin "4") (pinfunction "Q7_4") (pintype "output"))
    )
    (net (code "1005") (name "unconnected-(IC605A-Q8-Pad9)") (class "Default")
      (node (ref "IC605") (pin "9") (pinfunction "Q8_9") (pintype "output"))
    )
    (net (code "1006") (name "unconnected-(IC605A-Q9-Pad5)") (class "Default")
      (node (ref "IC605") (pin "5") (pinfunction "Q9_5") (pintype "output"))
    )
    (net (code "1007") (name "unconnected-(IC608D-OUT-Pad13)") (class "Default")
      (node (ref "IC608") (pin "13") (pinfunction "OUT_13") (pintype "open_collector"))
    )
    (net (code "1008") (name "unconnected-(IC610-DIS-Pad7)") (class "Default")
      (node (ref "IC610") (pin "7") (pinfunction "DIS_7") (pintype "input"))
    )
    (net (code "1009") (name "unconnected-(IC611A-Q-Pad6)") (class "Default")
      (node (ref "IC611") (pin "6") (pinfunction "Q_6") (pintype "output"))
    )
    (net (code "1010") (name "unconnected-(IC611A-T2-Pad2)") (class "Default")
      (node (ref "IC611") (pin "2") (pinfunction "T2_2") (pintype "input"))
    )
    (net (code "1011") (name "unconnected-(IC611A-~{Q}-Pad7)") (class "Default")
      (node (ref "IC611") (pin "7") (pinfunction "~{Q}_7") (pintype "output"))
    )
    (net (code "1012") (name "unconnected-(IC611B-Q-Pad10)") (class "Default")
      (node (ref "IC611") (pin "10") (pinfunction "Q_10") (pintype "output"))
    )
    (net (code "1013") (name "unconnected-(IC705A-Q6-Pad7)") (class "Default")
      (node (ref "IC705") (pin "7") (pinfunction "Q6_7") (pintype "output"))
    )
    (net (code "1014") (name "unconnected-(IC705A-Q7-Pad4)") (class "Default")
      (node (ref "IC705") (pin "4") (pinfunction "Q7_4") (pintype "output"))
    )
    (net (code "1015") (name "unconnected-(IC705A-Q8-Pad9)") (class "Default")
      (node (ref "IC705") (pin "9") (pinfunction "Q8_9") (pintype "output"))
    )
    (net (code "1016") (name "unconnected-(IC705A-Q9-Pad5)") (class "Default")
      (node (ref "IC705") (pin "5") (pinfunction "Q9_5") (pintype "output"))
    )
    (net (code "1017") (name "unconnected-(IC708D-OUT-Pad13)") (class "Default")
      (node (ref "IC708") (pin "13") (pinfunction "OUT_13") (pintype "open_collector"))
    )
    (net (code "1018") (name "unconnected-(IC710-DIS-Pad7)") (class "Default")
      (node (ref "IC710") (pin "7") (pinfunction "DIS_7") (pintype "input"))
    )
    (net (code "1019") (name "unconnected-(IC711A-Q-Pad6)") (class "Default")
      (node (ref "IC711") (pin "6") (pinfunction "Q_6") (pintype "output"))
    )
    (net (code "1020") (name "unconnected-(IC711A-T2-Pad2)") (class "Default")
      (node (ref "IC711") (pin "2") (pinfunction "T2_2") (pintype "input"))
    )
    (net (code "1021") (name "unconnected-(IC711A-~{Q}-Pad7)") (class "Default")
      (node (ref "IC711") (pin "7") (pinfunction "~{Q}_7") (pintype "output"))
    )
    (net (code "1022") (name "unconnected-(IC711B-Q-Pad10)") (class "Default")
      (node (ref "IC711") (pin "10") (pinfunction "Q_10") (pintype "output"))
    )
    (net (code "1023") (name "unconnected-(IC805A-Q6-Pad7)") (class "Default")
      (node (ref "IC805") (pin "7") (pinfunction "Q6_7") (pintype "output"))
    )
    (net (code "1024") (name "unconnected-(IC805A-Q7-Pad4)") (class "Default")
      (node (ref "IC805") (pin "4") (pinfunction "Q7_4") (pintype "output"))
    )
    (net (code "1025") (name "unconnected-(IC805A-Q8-Pad9)") (class "Default")
      (node (ref "IC805") (pin "9") (pinfunction "Q8_9") (pintype "output"))
    )
    (net (code "1026") (name "unconnected-(IC805A-Q9-Pad5)") (class "Default")
      (node (ref "IC805") (pin "5") (pinfunction "Q9_5") (pintype "output"))
    )
    (net (code "1027") (name "unconnected-(IC808D-OUT-Pad13)") (class "Default")
      (node (ref "IC808") (pin "13") (pinfunction "OUT_13") (pintype "open_collector"))
    )
    (net (code "1028") (name "unconnected-(IC810-DIS-Pad7)") (class "Default")
      (node (ref "IC810") (pin "7") (pinfunction "DIS_7") (pintype "input"))
    )
    (net (code "1029") (name "unconnected-(IC811A-Q-Pad6)") (class "Default")
      (node (ref "IC811") (pin "6") (pinfunction "Q_6") (pintype "output"))
    )
    (net (code "1030") (name "unconnected-(IC811A-T2-Pad2)") (class "Default")
      (node (ref "IC811") (pin "2") (pinfunction "T2_2") (pintype "input"))
    )
    (net (code "1031") (name "unconnected-(IC811A-~{Q}-Pad7)") (class "Default")
      (node (ref "IC811") (pin "7") (pinfunction "~{Q}_7") (pintype "output"))
    )
    (net (code "1032") (name "unconnected-(IC811B-Q-Pad10)") (class "Default")
      (node (ref "IC811") (pin "10") (pinfunction "Q_10") (pintype "output"))
    )
    (net (code "1033") (name "unconnected-(IC905A-Q6-Pad7)") (class "Default")
      (node (ref "IC905") (pin "7") (pinfunction "Q6_7") (pintype "output"))
    )
    (net (code "1034") (name "unconnected-(IC905A-Q7-Pad4)") (class "Default")
      (node (ref "IC905") (pin "4") (pinfunction "Q7_4") (pintype "output"))
    )
    (net (code "1035") (name "unconnected-(IC905A-Q8-Pad9)") (class "Default")
      (node (ref "IC905") (pin "9") (pinfunction "Q8_9") (pintype "output"))
    )
    (net (code "1036") (name "unconnected-(IC905A-Q9-Pad5)") (class "Default")
      (node (ref "IC905") (pin "5") (pinfunction "Q9_5") (pintype "output"))
    )
    (net (code "1037") (name "unconnected-(IC908D-OUT-Pad13)") (class "Default")
      (node (ref "IC908") (pin "13") (pinfunction "OUT_13") (pintype "open_collector"))
    )
    (net (code "1038") (name "unconnected-(IC910-DIS-Pad7)") (class "Default")
      (node (ref "IC910") (pin "7") (pinfunction "DIS_7") (pintype "input"))
    )
    (net (code "1039") (name "unconnected-(IC911A-Q-Pad6)") (class "Default")
      (node (ref "IC911") (pin "6") (pinfunction "Q_6") (pintype "output"))
    )
    (net (code "1040") (name "unconnected-(IC911A-T2-Pad2)") (class "Default")
      (node (ref "IC911") (pin "2") (pinfunction "T2_2") (pintype "input"))
    )
    (net (code "1041") (name "unconnected-(IC911A-~{Q}-Pad7)") (class "Default")
      (node (ref "IC911") (pin "7") (pinfunction "~{Q}_7") (pintype "output"))
    )
    (net (code "1042") (name "unconnected-(IC911B-Q-Pad10)") (class "Default")
      (node (ref "IC911") (pin "10") (pinfunction "Q_10") (pintype "output"))
    )
    (net (code "1043") (name "unconnected-(IC1005A-Q6-Pad7)") (class "Default")
      (node (ref "IC1005") (pin "7") (pinfunction "Q6_7") (pintype "output"))
    )
    (net (code "1044") (name "unconnected-(IC1005A-Q7-Pad4)") (class "Default")
      (node (ref "IC1005") (pin "4") (pinfunction "Q7_4") (pintype "output"))
    )
    (net (code "1045") (name "unconnected-(IC1005A-Q8-Pad9)") (class "Default")
      (node (ref "IC1005") (pin "9") (pinfunction "Q8_9") (pintype "output"))
    )
    (net (code "1046") (name "unconnected-(IC1005A-Q9-Pad5)") (class "Default")
      (node (ref "IC1005") (pin "5") (pinfunction "Q9_5") (pintype "output"))
    )
    (net (code "1047") (name "unconnected-(IC1008D-OUT-Pad13)") (class "Default")
      (node (ref "IC1008") (pin "13") (pinfunction "OUT_13") (pintype "open_collector"))
    )
    (net (code "1048") (name "unconnected-(IC1010-DIS-Pad7)") (class "Default")
      (node (ref "IC1010") (pin "7") (pinfunction "DIS_7") (pintype "input"))
    )
    (net (code "1049") (name "unconnected-(IC1011A-Q-Pad6)") (class "Default")
      (node (ref "IC1011") (pin "6") (pinfunction "Q_6") (pintype "output"))
    )
    (net (code "1050") (name "unconnected-(IC1011A-T2-Pad2)") (class "Default")
      (node (ref "IC1011") (pin "2") (pinfunction "T2_2") (pintype "input"))
    )
    (net (code "1051") (name "unconnected-(IC1011A-~{Q}-Pad7)") (class "Default")
      (node (ref "IC1011") (pin "7") (pinfunction "~{Q}_7") (pintype "output"))
    )
    (net (code "1052") (name "unconnected-(IC1011B-Q-Pad10)") (class "Default")
      (node (ref "IC1011") (pin "10") (pinfunction "Q_10") (pintype "output"))
    )
    (net (code "1053") (name "unconnected-(IC1105A-Q6-Pad7)") (class "Default")
      (node (ref "IC1105") (pin "7") (pinfunction "Q6_7") (pintype "output"))
    )
    (net (code "1054") (name "unconnected-(IC1105A-Q7-Pad4)") (class "Default")
      (node (ref "IC1105") (pin "4") (pinfunction "Q7_4") (pintype "output"))
    )
    (net (code "1055") (name "unconnected-(IC1105A-Q8-Pad9)") (class "Default")
      (node (ref "IC1105") (pin "9") (pinfunction "Q8_9") (pintype "output"))
    )
    (net (code "1056") (name "unconnected-(IC1105A-Q9-Pad5)") (class "Default")
      (node (ref "IC1105") (pin "5") (pinfunction "Q9_5") (pintype "output"))
    )
    (net (code "1057") (name "unconnected-(IC1108D-OUT-Pad13)") (class "Default")
      (node (ref "IC1108") (pin "13") (pinfunction "OUT_13") (pintype "open_collector"))
    )
    (net (code "1058") (name "unconnected-(IC1110-DIS-Pad7)") (class "Default")
      (node (ref "IC1110") (pin "7") (pinfunction "DIS_7") (pintype "input"))
    )
    (net (code "1059") (name "unconnected-(IC1111A-Q-Pad6)") (class "Default")
      (node (ref "IC1111") (pin "6") (pinfunction "Q_6") (pintype "output"))
    )
    (net (code "1060") (name "unconnected-(IC1111A-T2-Pad2)") (class "Default")
      (node (ref "IC1111") (pin "2") (pinfunction "T2_2") (pintype "input"))
    )
    (net (code "1061") (name "unconnected-(IC1111A-~{Q}-Pad7)") (class "Default")
      (node (ref "IC1111") (pin "7") (pinfunction "~{Q}_7") (pintype "output"))
    )
    (net (code "1062") (name "unconnected-(IC1111B-Q-Pad10)") (class "Default")
      (node (ref "IC1111") (pin "10") (pinfunction "Q_10") (pintype "output"))
    )
    (net (code "1063") (name "unconnected-(IC1205A-Q6-Pad7)") (class "Default")
      (node (ref "IC1205") (pin "7") (pinfunction "Q6_7") (pintype "output"))
    )
    (net (code "1064") (name "unconnected-(IC1205A-Q7-Pad4)") (class "Default")
      (node (ref "IC1205") (pin "4") (pinfunction "Q7_4") (pintype "output"))
    )
    (net (code "1065") (name "unconnected-(IC1205A-Q8-Pad9)") (class "Default")
      (node (ref "IC1205") (pin "9") (pinfunction "Q8_9") (pintype "output"))
    )
    (net (code "1066") (name "unconnected-(IC1205A-Q9-Pad5)") (class "Default")
      (node (ref "IC1205") (pin "5") (pinfunction "Q9_5") (pintype "output"))
    )
    (net (code "1067") (name "unconnected-(IC1208D-OUT-Pad13)") (class "Default")
      (node (ref "IC1208") (pin "13") (pinfunction "OUT_13") (pintype "open_collector"))
    )
    (net (code "1068") (name "unconnected-(IC1210-DIS-Pad7)") (class "Default")
      (node (ref "IC1210") (pin "7") (pinfunction "DIS_7") (pintype "input"))
    )
    (net (code "1069") (name "unconnected-(IC1211A-Q-Pad6)") (class "Default")
      (node (ref "IC1211") (pin "6") (pinfunction "Q_6") (pintype "output"))
    )
    (net (code "1070") (name "unconnected-(IC1211A-T2-Pad2)") (class "Default")
      (node (ref "IC1211") (pin "2") (pinfunction "T2_2") (pintype "input"))
    )
    (net (code "1071") (name "unconnected-(IC1211A-~{Q}-Pad7)") (class "Default")
      (node (ref "IC1211") (pin "7") (pinfunction "~{Q}_7") (pintype "output"))
    )
    (net (code "1072") (name "unconnected-(IC1211B-Q-Pad10)") (class "Default")
      (node (ref "IC1211") (pin "10") (pinfunction "Q_10") (pintype "output"))
    )
    (net (code "1073") (name "unconnected-(X101-Pad20)") (class "Default")
      (node (ref "X101") (pin "20") (pinfunction "20_20") (pintype "passive"))
    )
    (net (code "1074") (name "unconnected-(X101-Pad24)") (class "Default")
      (node (ref "X101") (pin "24") (pinfunction "24_24") (pintype "passive"))
    )
    (net (code "1075") (name "unconnected-(X201-Pad20)") (class "Default")
      (node (ref "X201") (pin "20") (pinfunction "20_20") (pintype "passive"))
    )
    (net (code "1076") (name "unconnected-(X201-Pad24)") (class "Default")
      (node (ref "X201") (pin "24") (pinfunction "24_24") (pintype "passive"))
    )
    (net (code "1077") (name "unconnected-(X301-Pad20)") (class "Default")
      (node (ref "X301") (pin "20") (pinfunction "20_20") (pintype "passive"))
    )
    (net (code "1078") (name "unconnected-(X301-Pad24)") (class "Default")
      (node (ref "X301") (pin "24") (pinfunction "24_24") (pintype "passive"))
    )
    (net (code "1079") (name "unconnected-(X401-Pad20)") (class "Default")
      (node (ref "X401") (pin "20") (pinfunction "20_20") (pintype "passive"))
    )
    (net (code "1080") (name "unconnected-(X401-Pad24)") (class "Default")
      (node (ref "X401") (pin "24") (pinfunction "24_24") (pintype "passive"))
    )
    (net (code "1081") (name "unconnected-(X501-Pad20)") (class "Default")
      (node (ref "X501") (pin "20") (pinfunction "20_20") (pintype "passive"))
    )
    (net (code "1082") (name "unconnected-(X501-Pad24)") (class "Default")
      (node (ref "X501") (pin "24") (pinfunction "24_24") (pintype "passive"))
    )
    (net (code "1083") (name "unconnected-(X601-Pad20)") (class "Default")
      (node (ref "X601") (pin "20") (pinfunction "20_20") (pintype "passive"))
    )
    (net (code "1084") (name "unconnected-(X601-Pad24)") (class "Default")
      (node (ref "X601") (pin "24") (pinfunction "24_24") (pintype "passive"))
    )
    (net (code "1085") (name "unconnected-(X701-Pad20)") (class "Default")
      (node (ref "X701") (pin "20") (pinfunction "20_20") (pintype "passive"))
    )
    (net (code "1086") (name "unconnected-(X701-Pad24)") (class "Default")
      (node (ref "X701") (pin "24") (pinfunction "24_24") (pintype "passive"))
    )
    (net (code "1087") (name "unconnected-(X801-Pad20)") (class "Default")
      (node (ref "X801") (pin "20") (pinfunction "20_20") (pintype "passive"))
    )
    (net (code "1088") (name "unconnected-(X801-Pad24)") (class "Default")
      (node (ref "X801") (pin "24") (pinfunction "24_24") (pintype "passive"))
    )
    (net (code "1089") (name "unconnected-(X901-Pad20)") (class "Default")
      (node (ref "X901") (pin "20") (pinfunction "20_20") (pintype "passive"))
    )
    (net (code "1090") (name "unconnected-(X901-Pad24)") (class "Default")
      (node (ref "X901") (pin "24") (pinfunction "24_24") (pintype "passive"))
    )
    (net (code "1091") (name "unconnected-(X1001-Pad20)") (class "Default")
      (node (ref "X1001") (pin "20") (pinfunction "20_20") (pintype "passive"))
    )
    (net (code "1092") (name "unconnected-(X1001-Pad24)") (class "Default")
      (node (ref "X1001") (pin "24") (pinfunction "24_24") (pintype "passive"))
    )
    (net (code "1093") (name "unconnected-(X1101-Pad20)") (class "Default")
      (node (ref "X1101") (pin "20") (pinfunction "20_20") (pintype "passive"))
    )
    (net (code "1094") (name "unconnected-(X1101-Pad24)") (class "Default")
      (node (ref "X1101") (pin "24") (pinfunction "24_24") (pintype "passive"))
    )
    (net (code "1095") (name "unconnected-(X1201-Pad20)") (class "Default")
      (node (ref "X1201") (pin "20") (pinfunction "20_20") (pintype "passive"))
    )
    (net (code "1096") (name "unconnected-(X1201-Pad24)") (class "Default")
      (node (ref "X1201") (pin "24") (pinfunction "24_24") (pintype "passive"))
    )
  )
)
